# BEP32_12nutzen_stencil.net
KiCad netlist of a schematic drawn in EAGLE
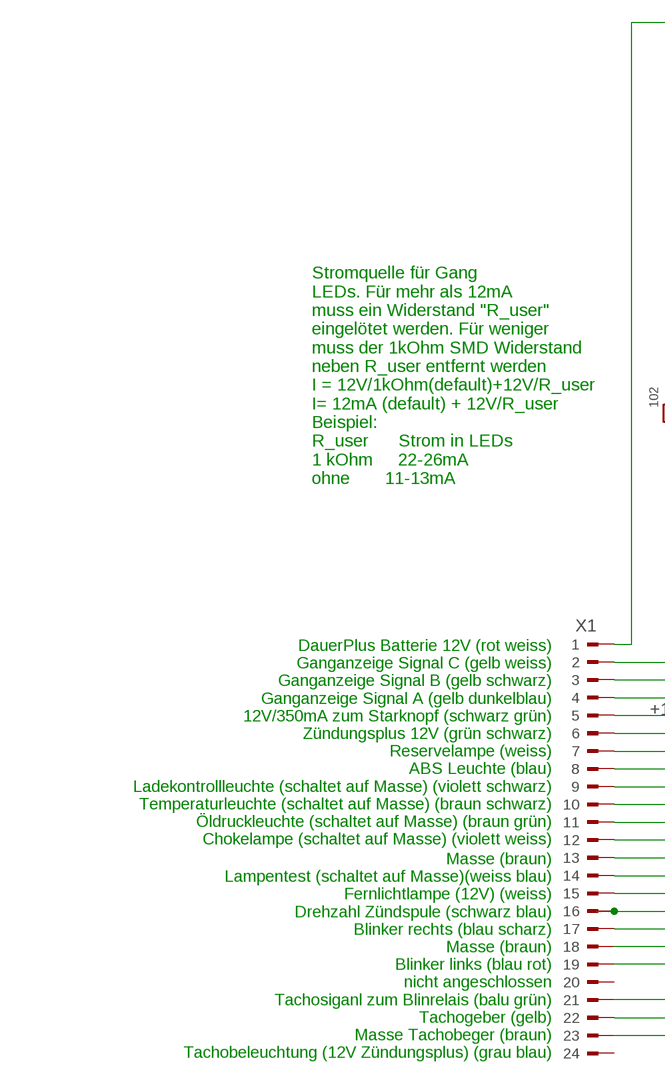
[diagram p0: schematic, sheet 1, part 1 of 2]
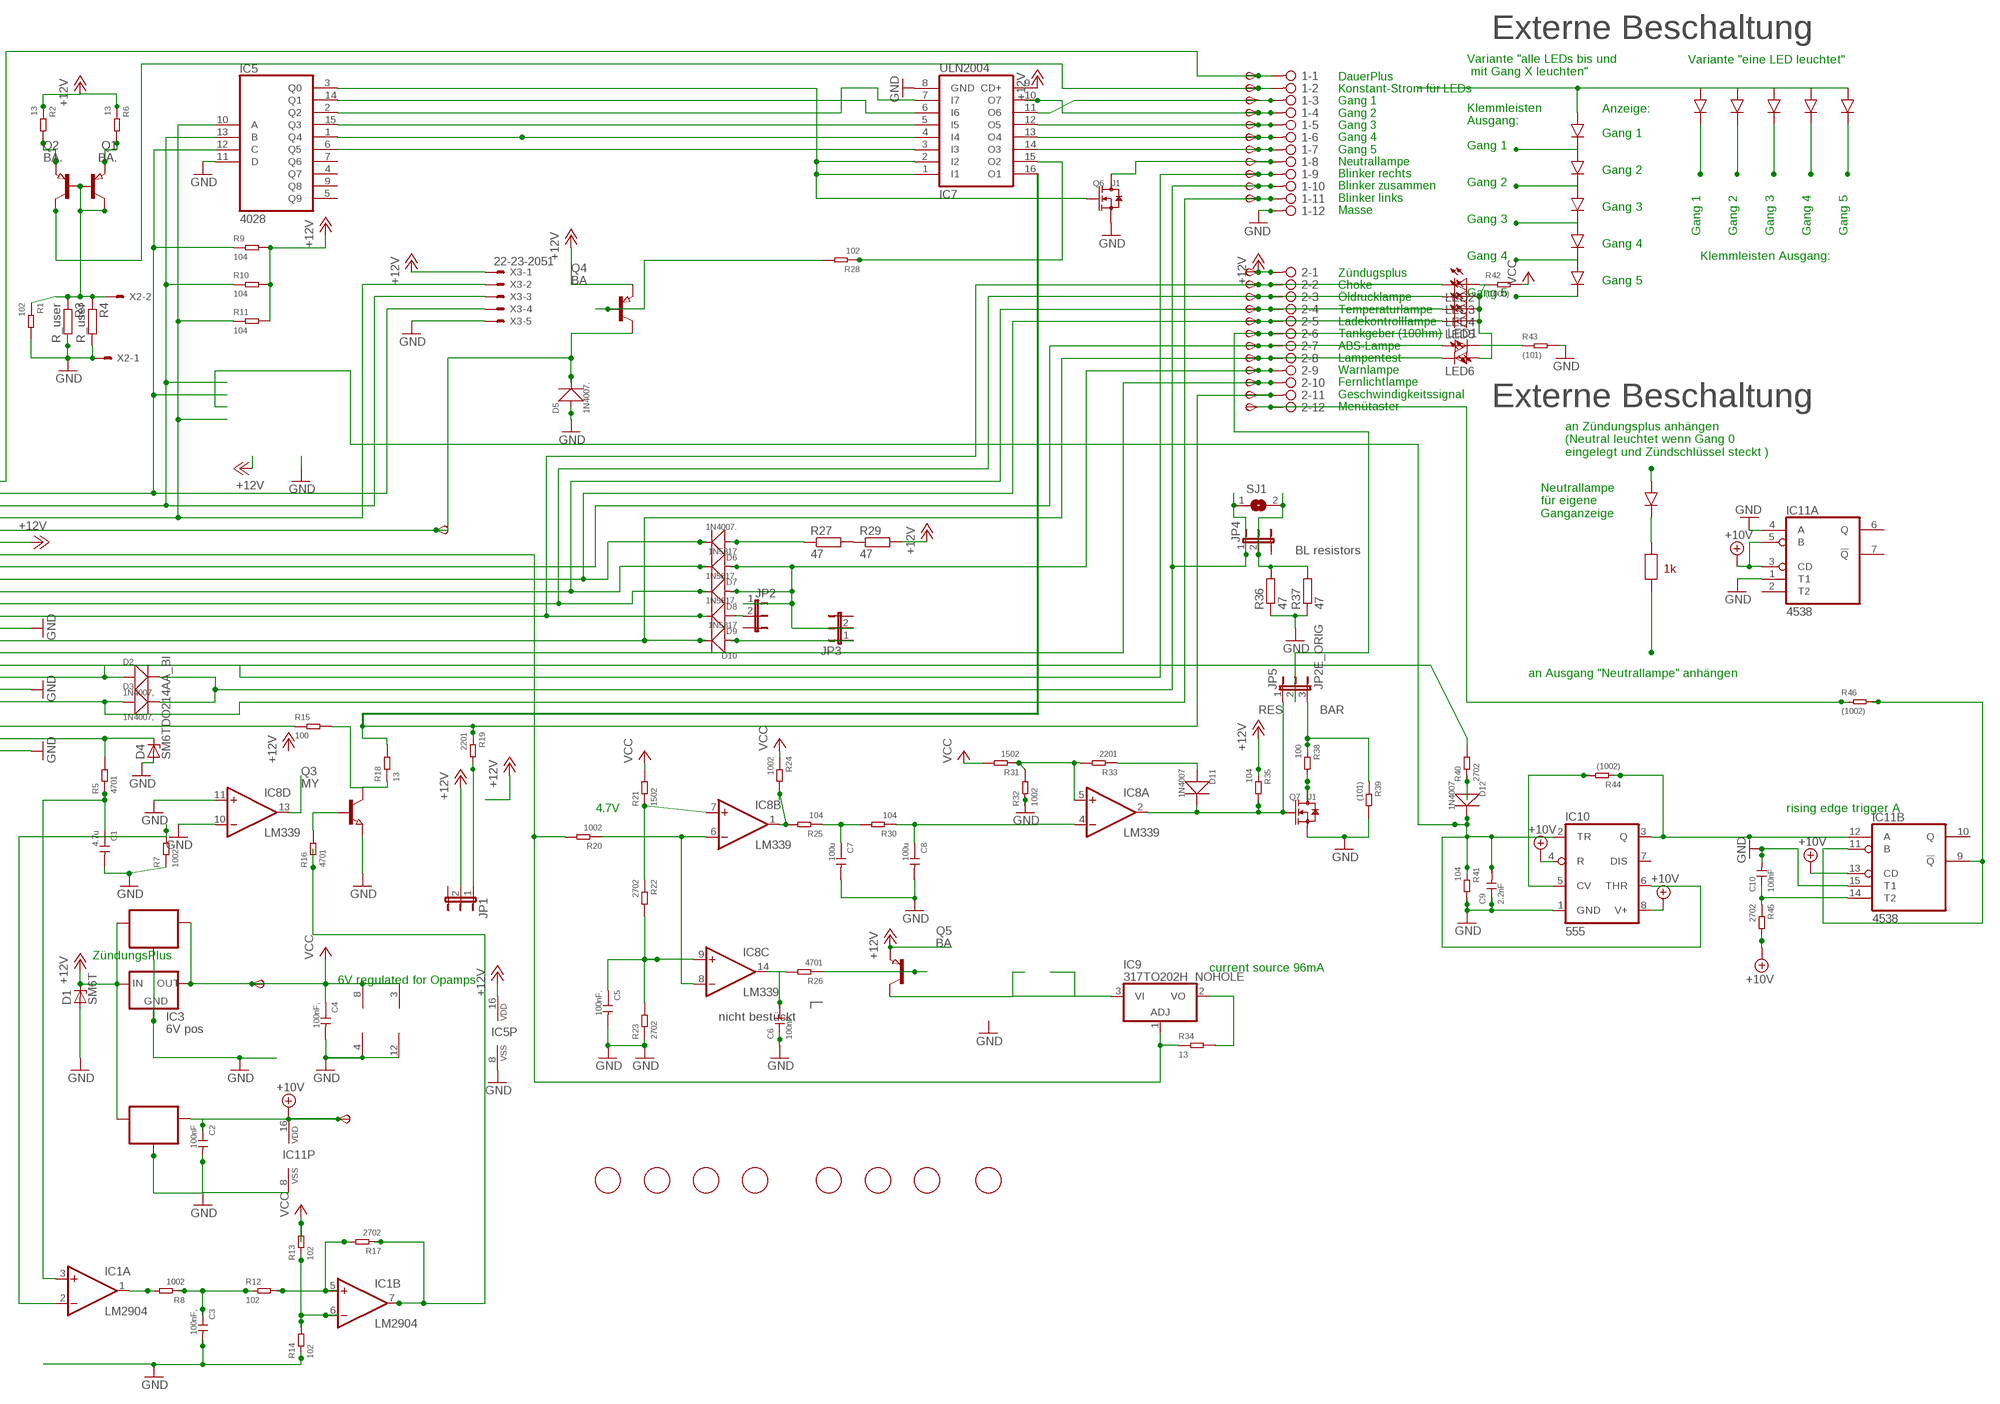
[diagram p1: schematic, sheet 1, part 2 of 2]
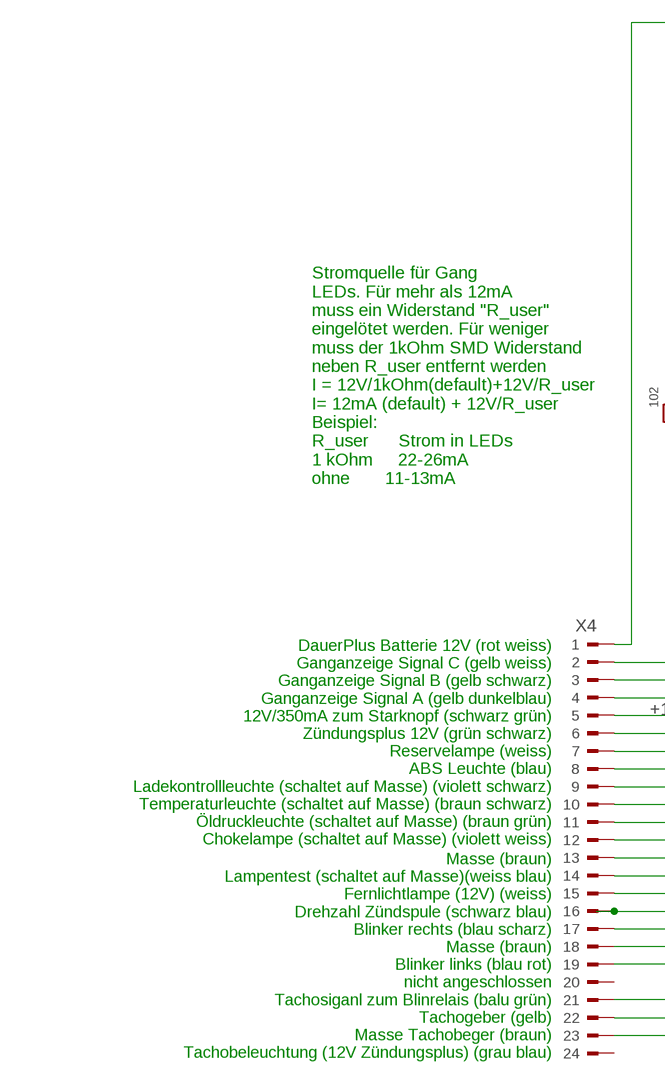
[diagram p2: schematic, sheet 2, part 1 of 2]
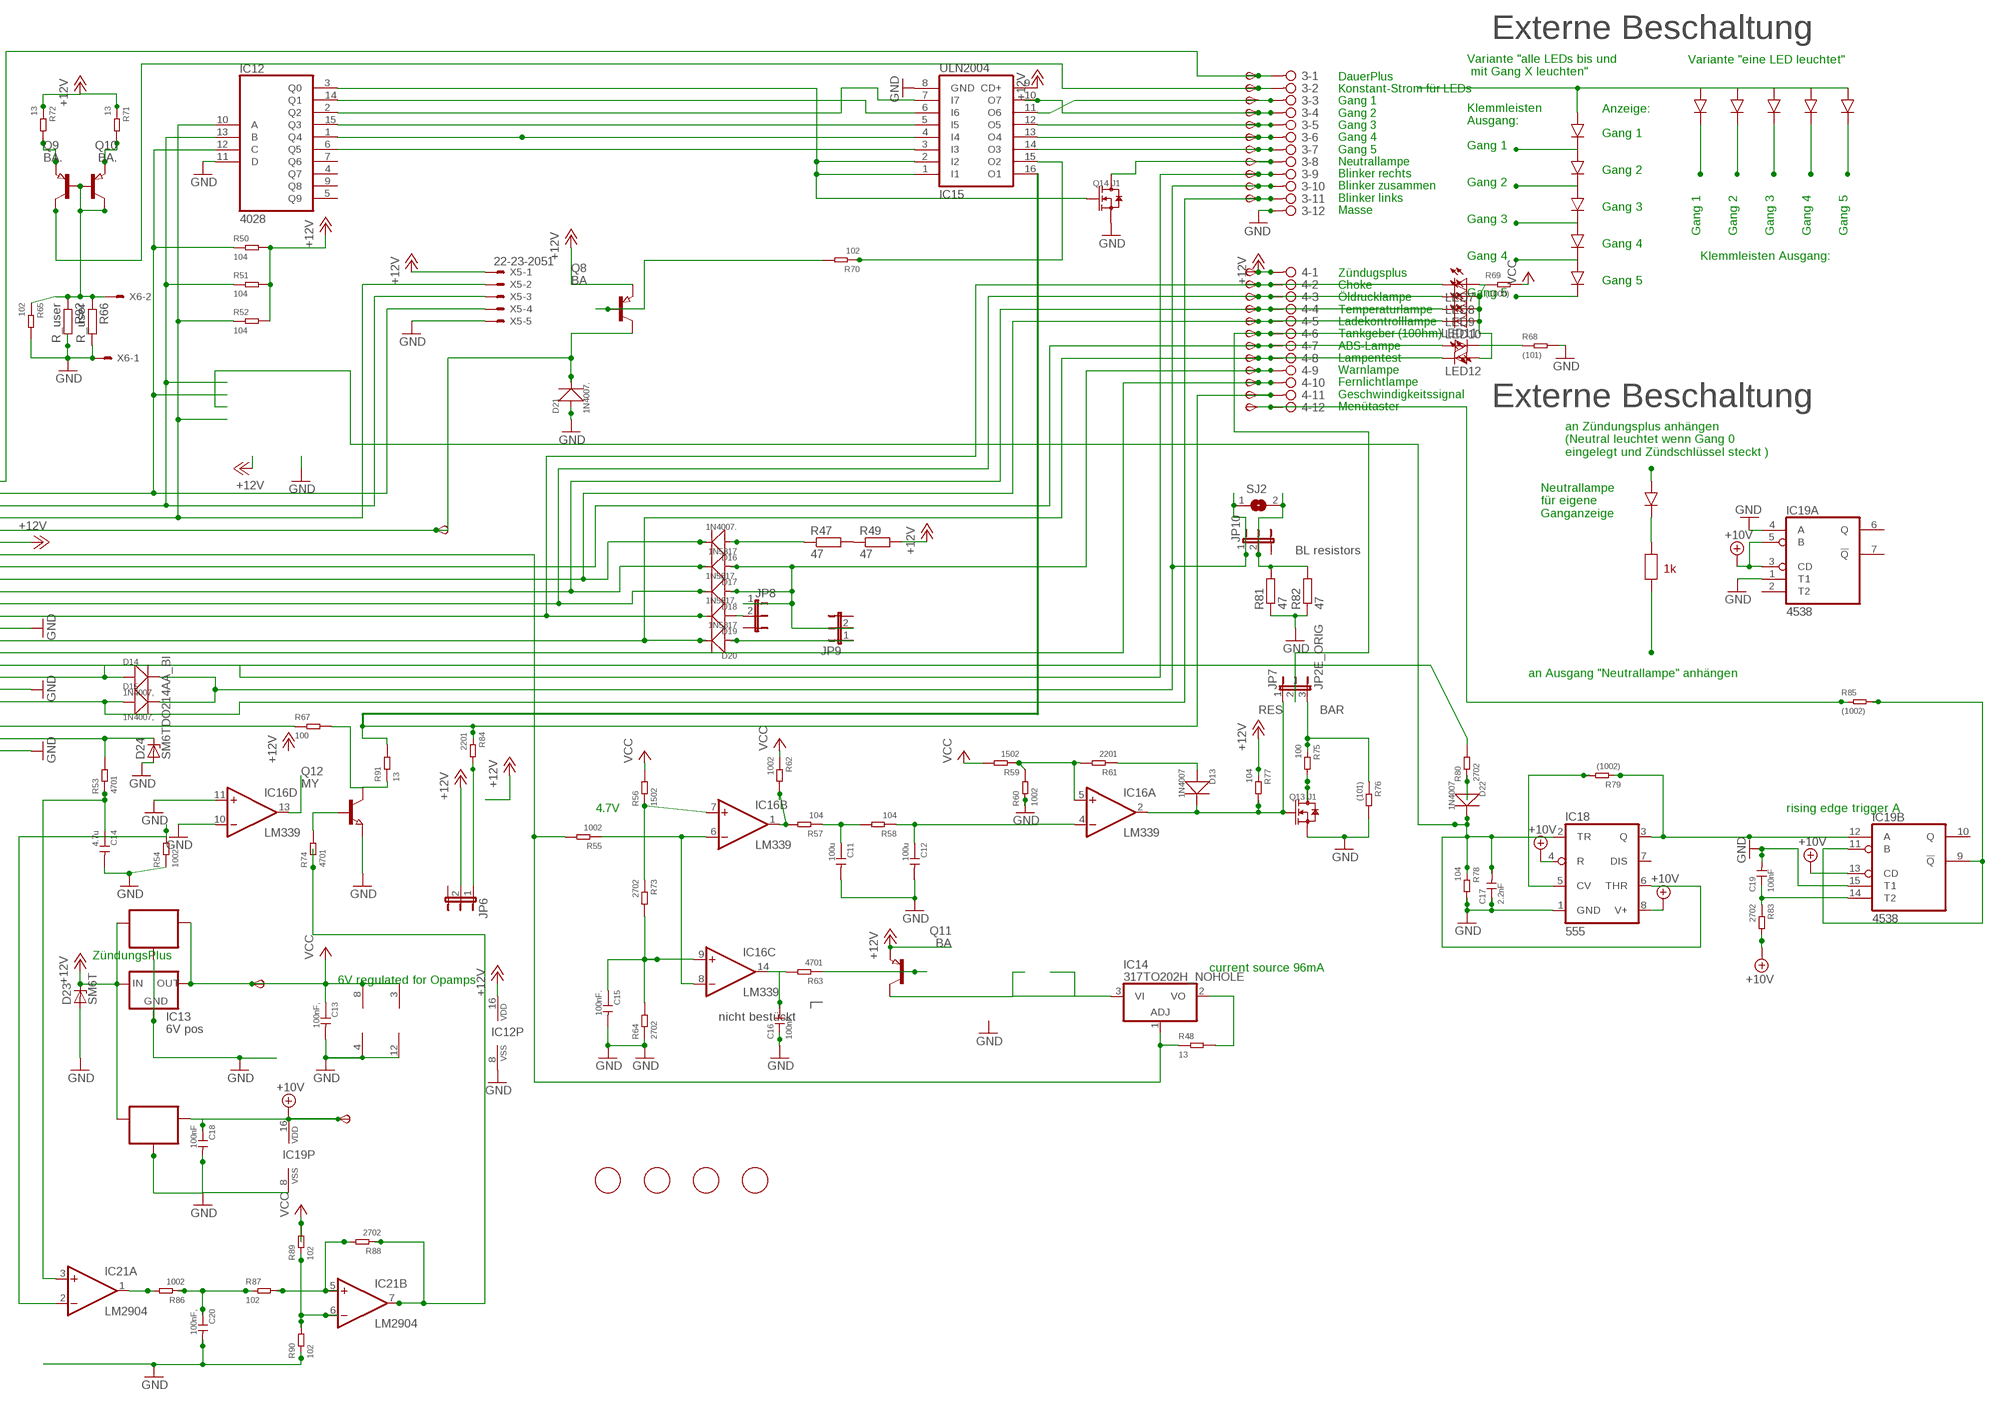
[diagram p3: schematic, sheet 2, part 2 of 2]
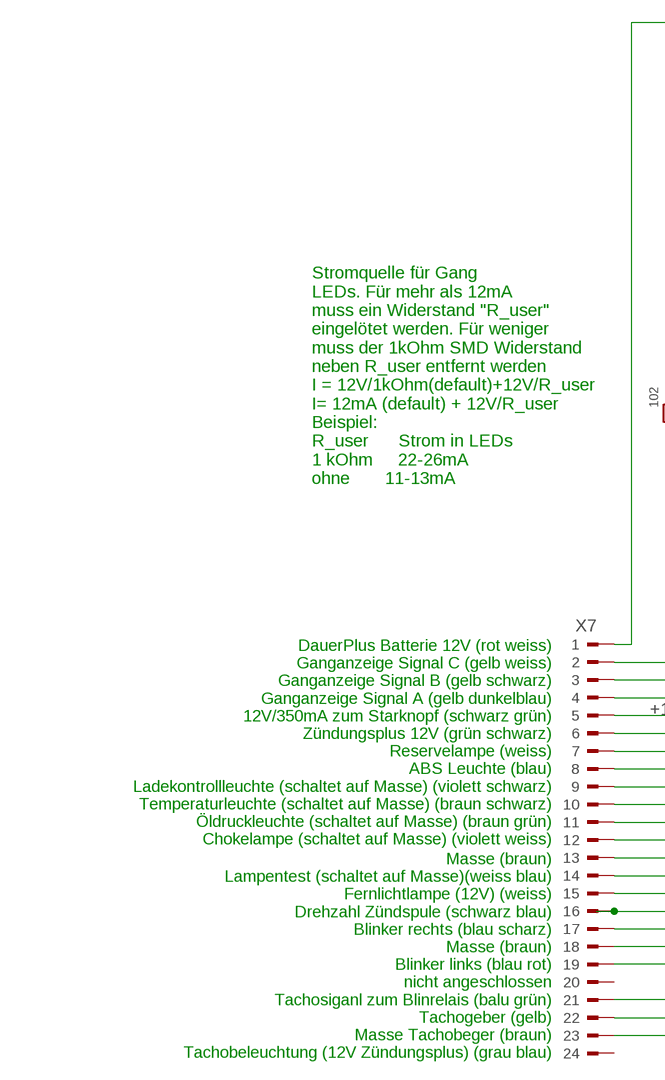
[diagram p4: schematic, sheet 3, part 1 of 2]
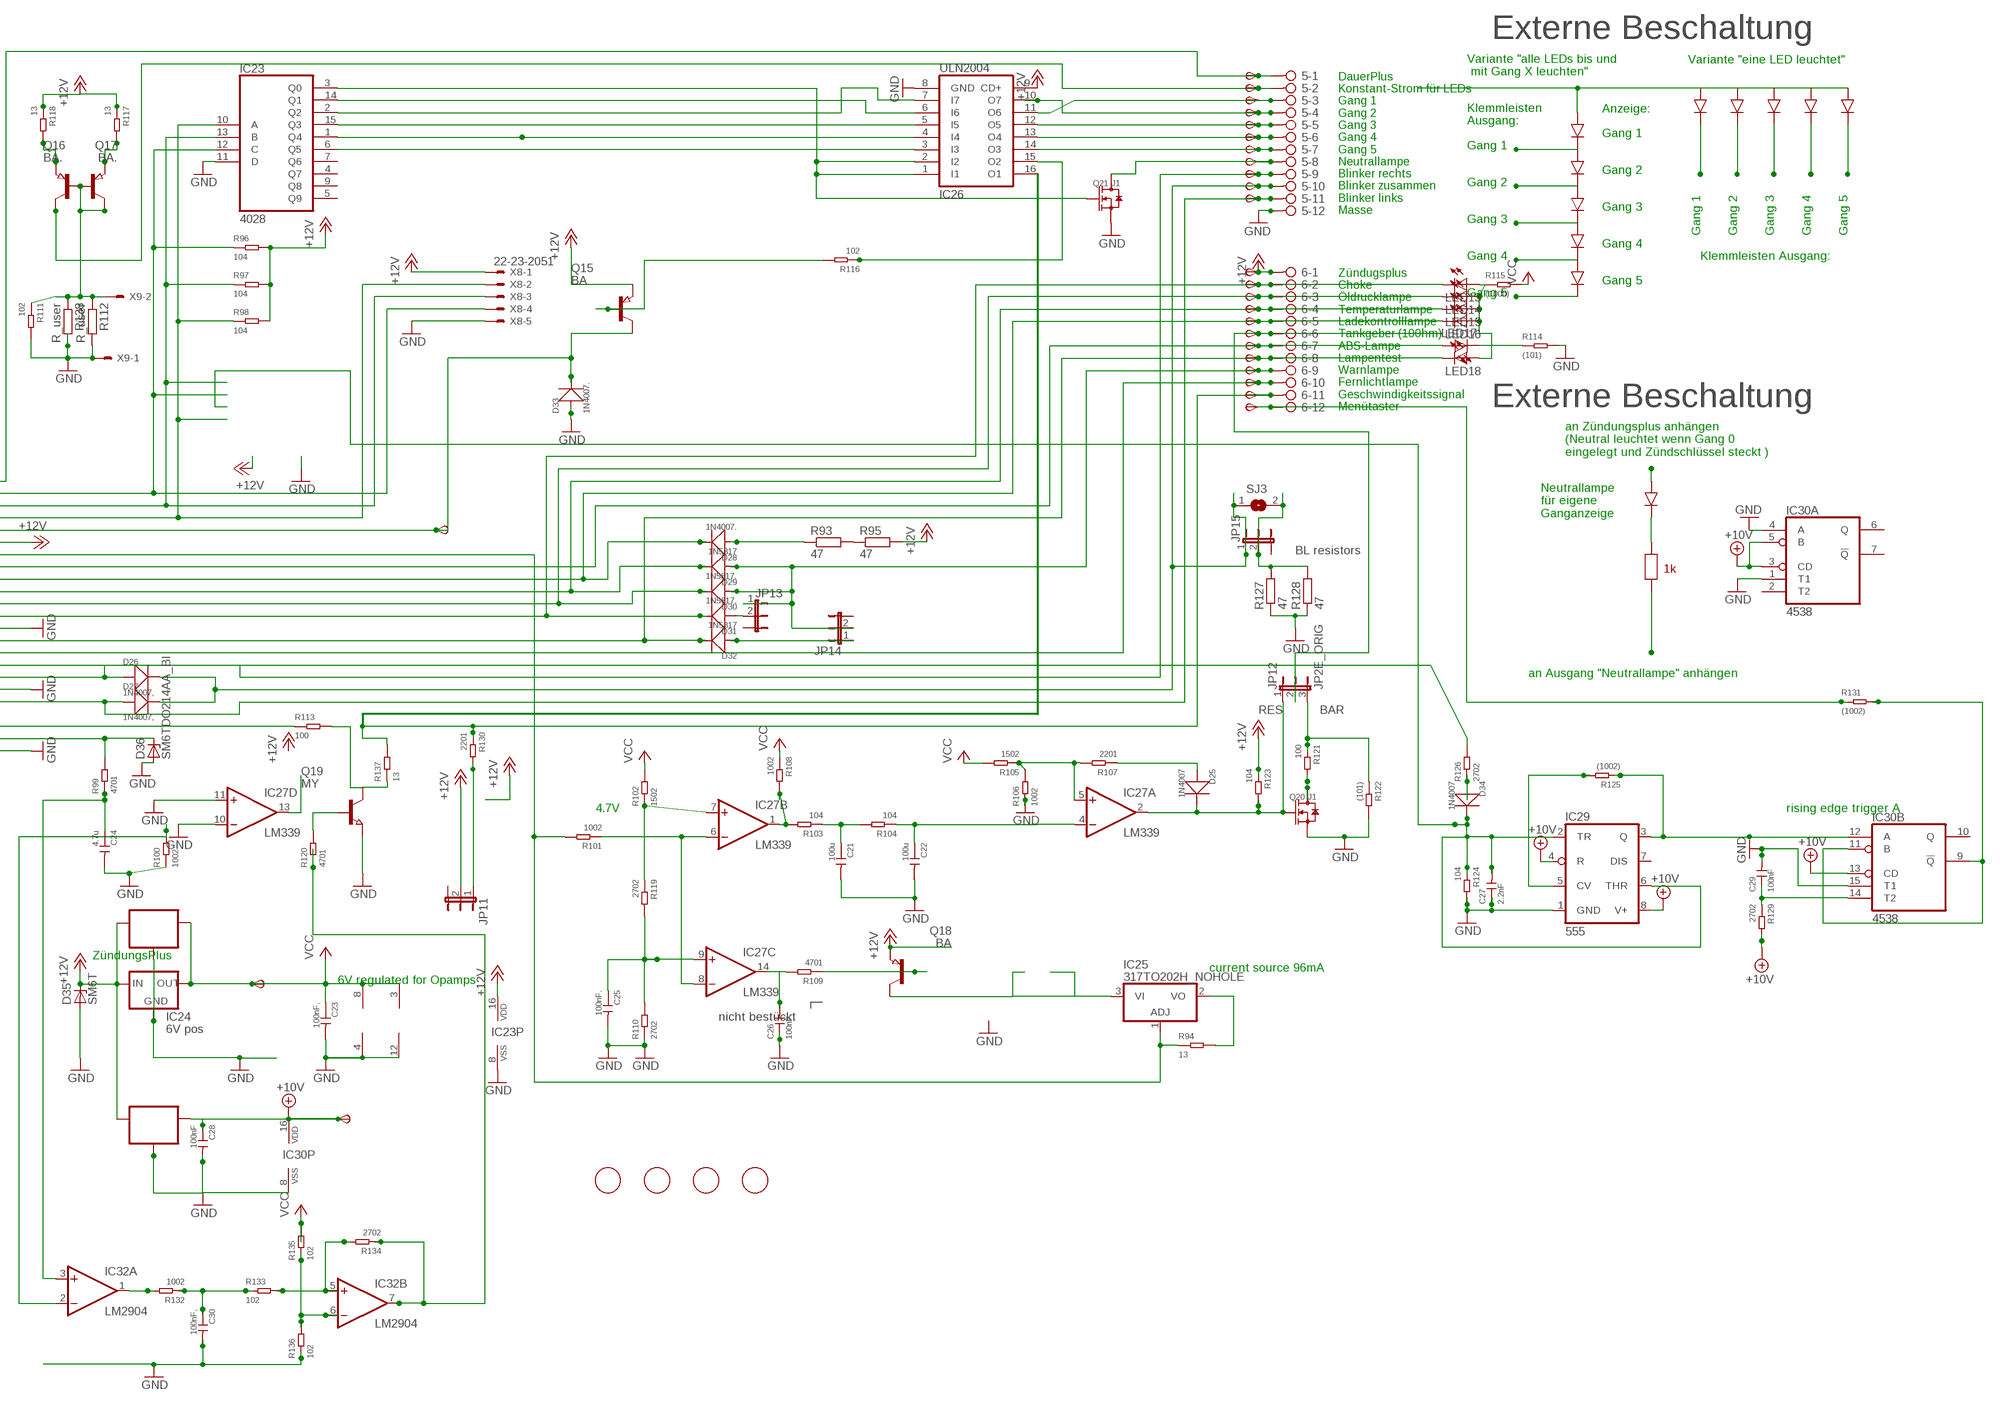
[diagram p5: schematic, sheet 3, part 2 of 2]
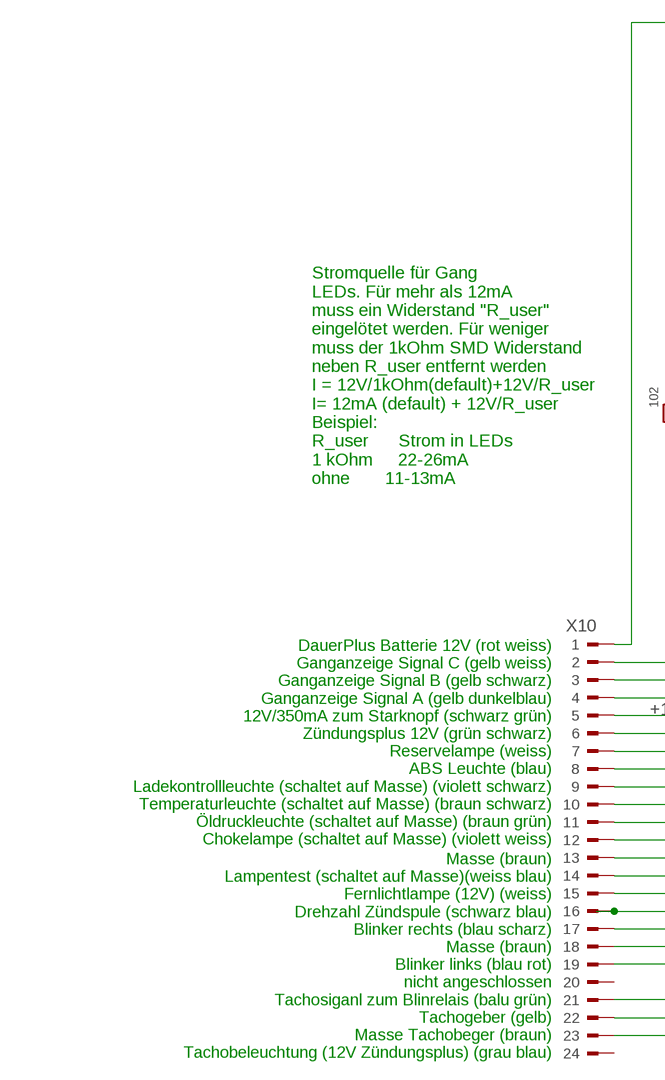
[diagram p6: schematic, sheet 4, part 1 of 2]
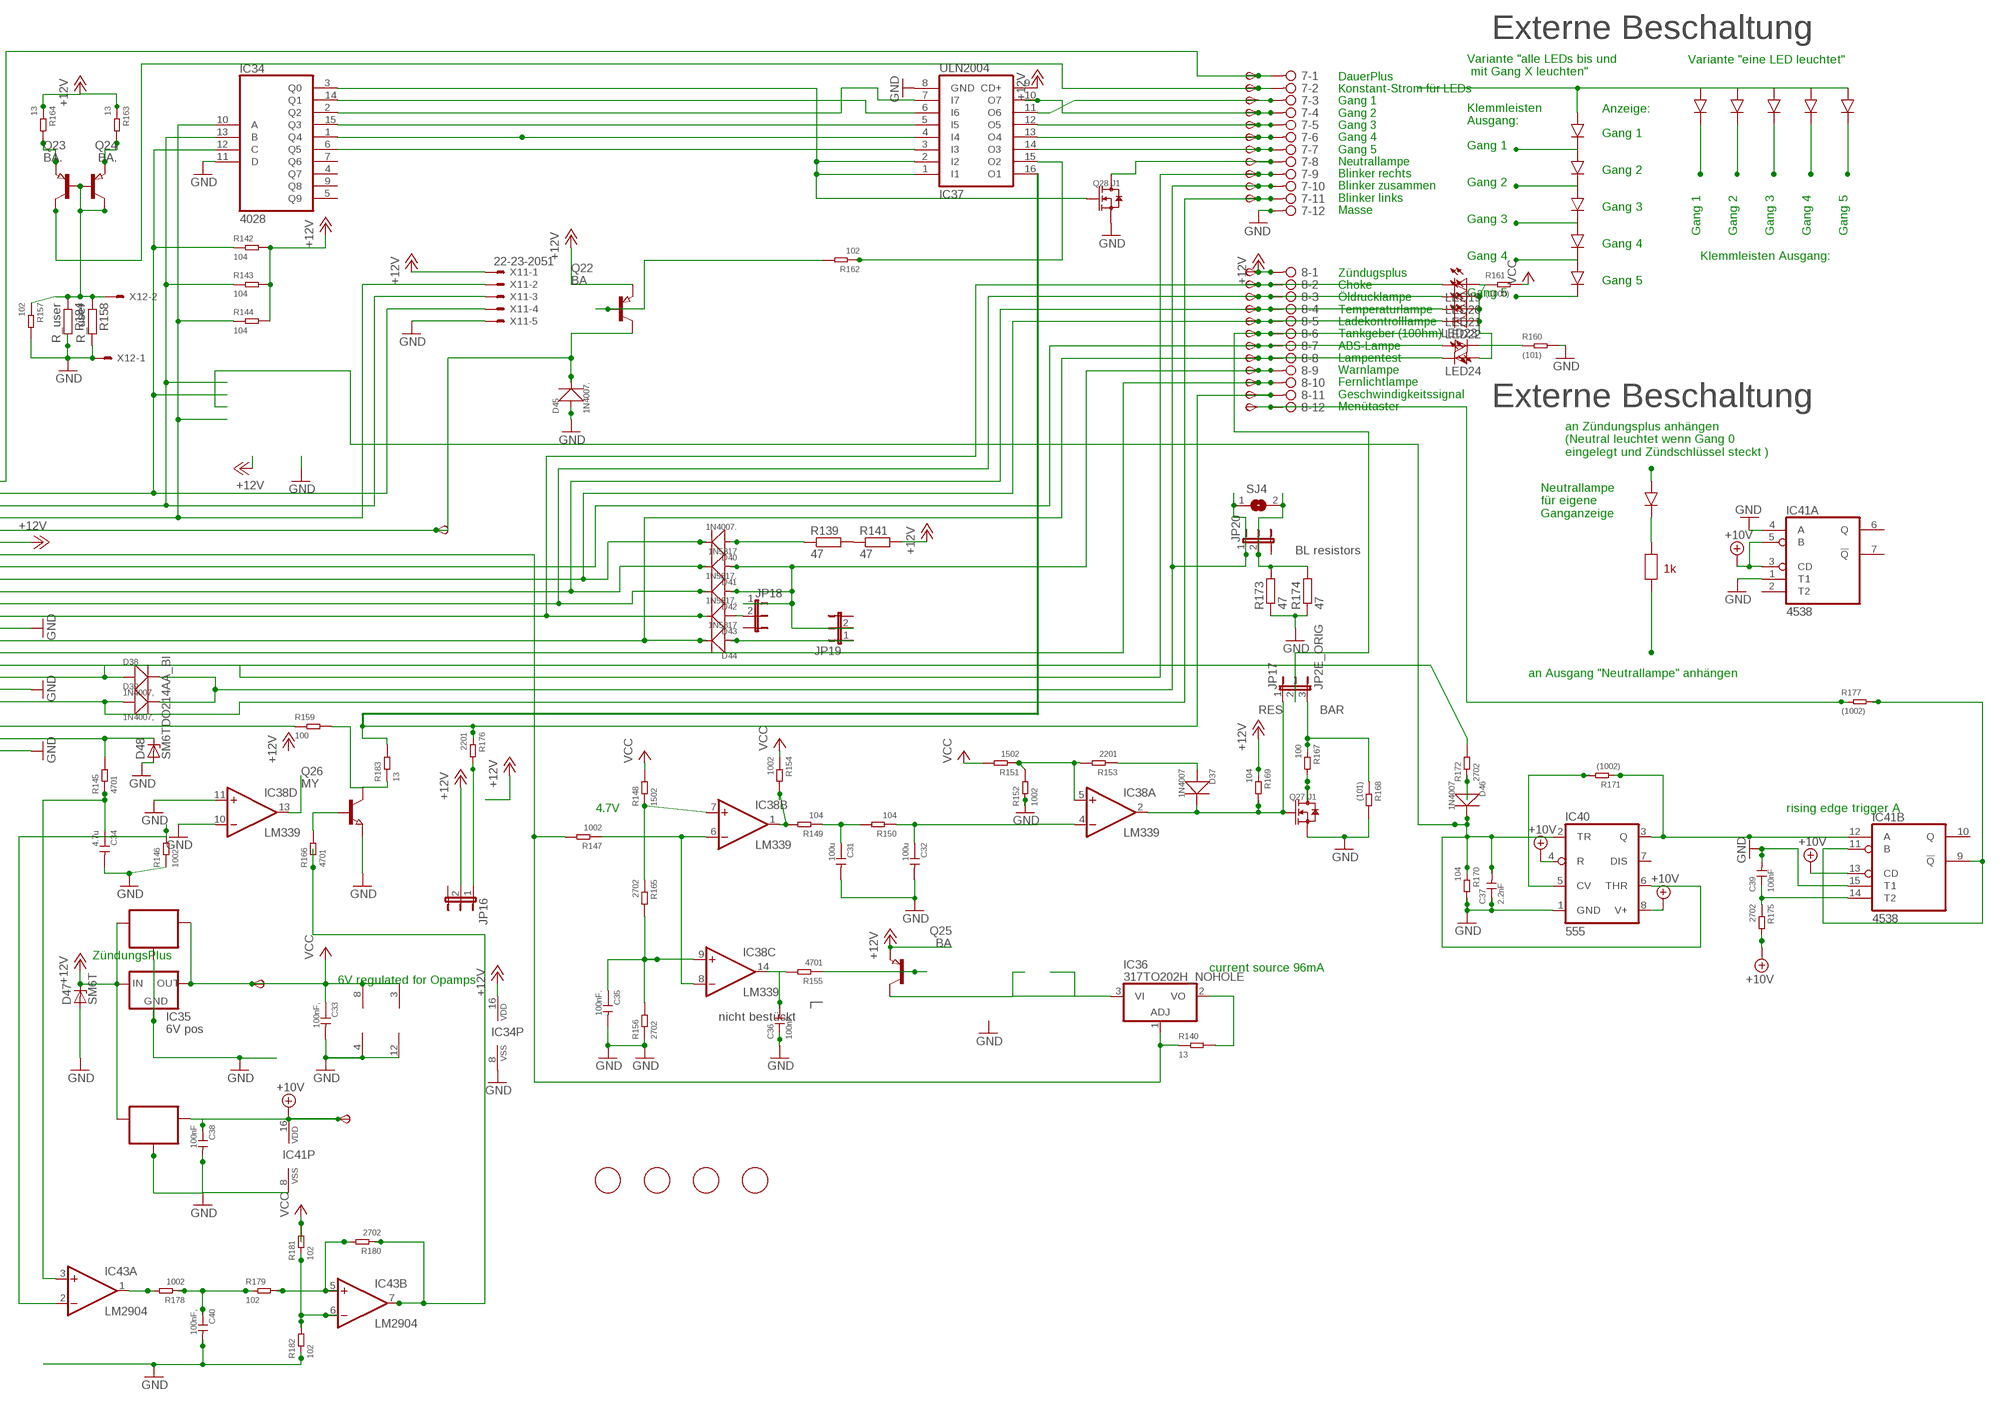
[diagram p7: schematic, sheet 4, part 2 of 2]
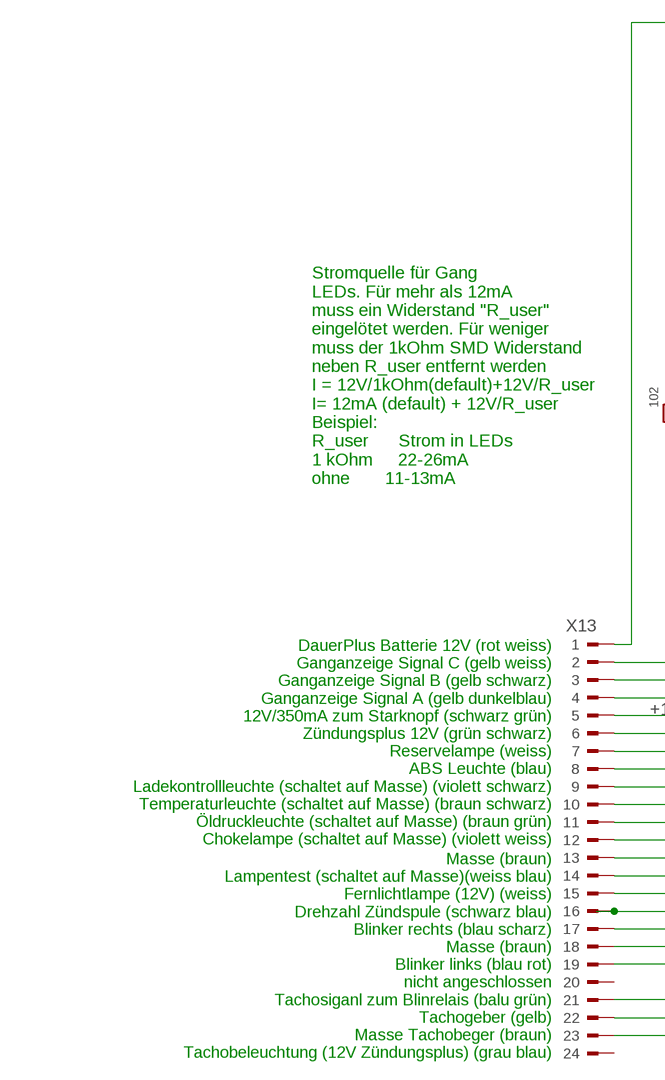
[diagram p8: schematic, sheet 5, part 1 of 2]
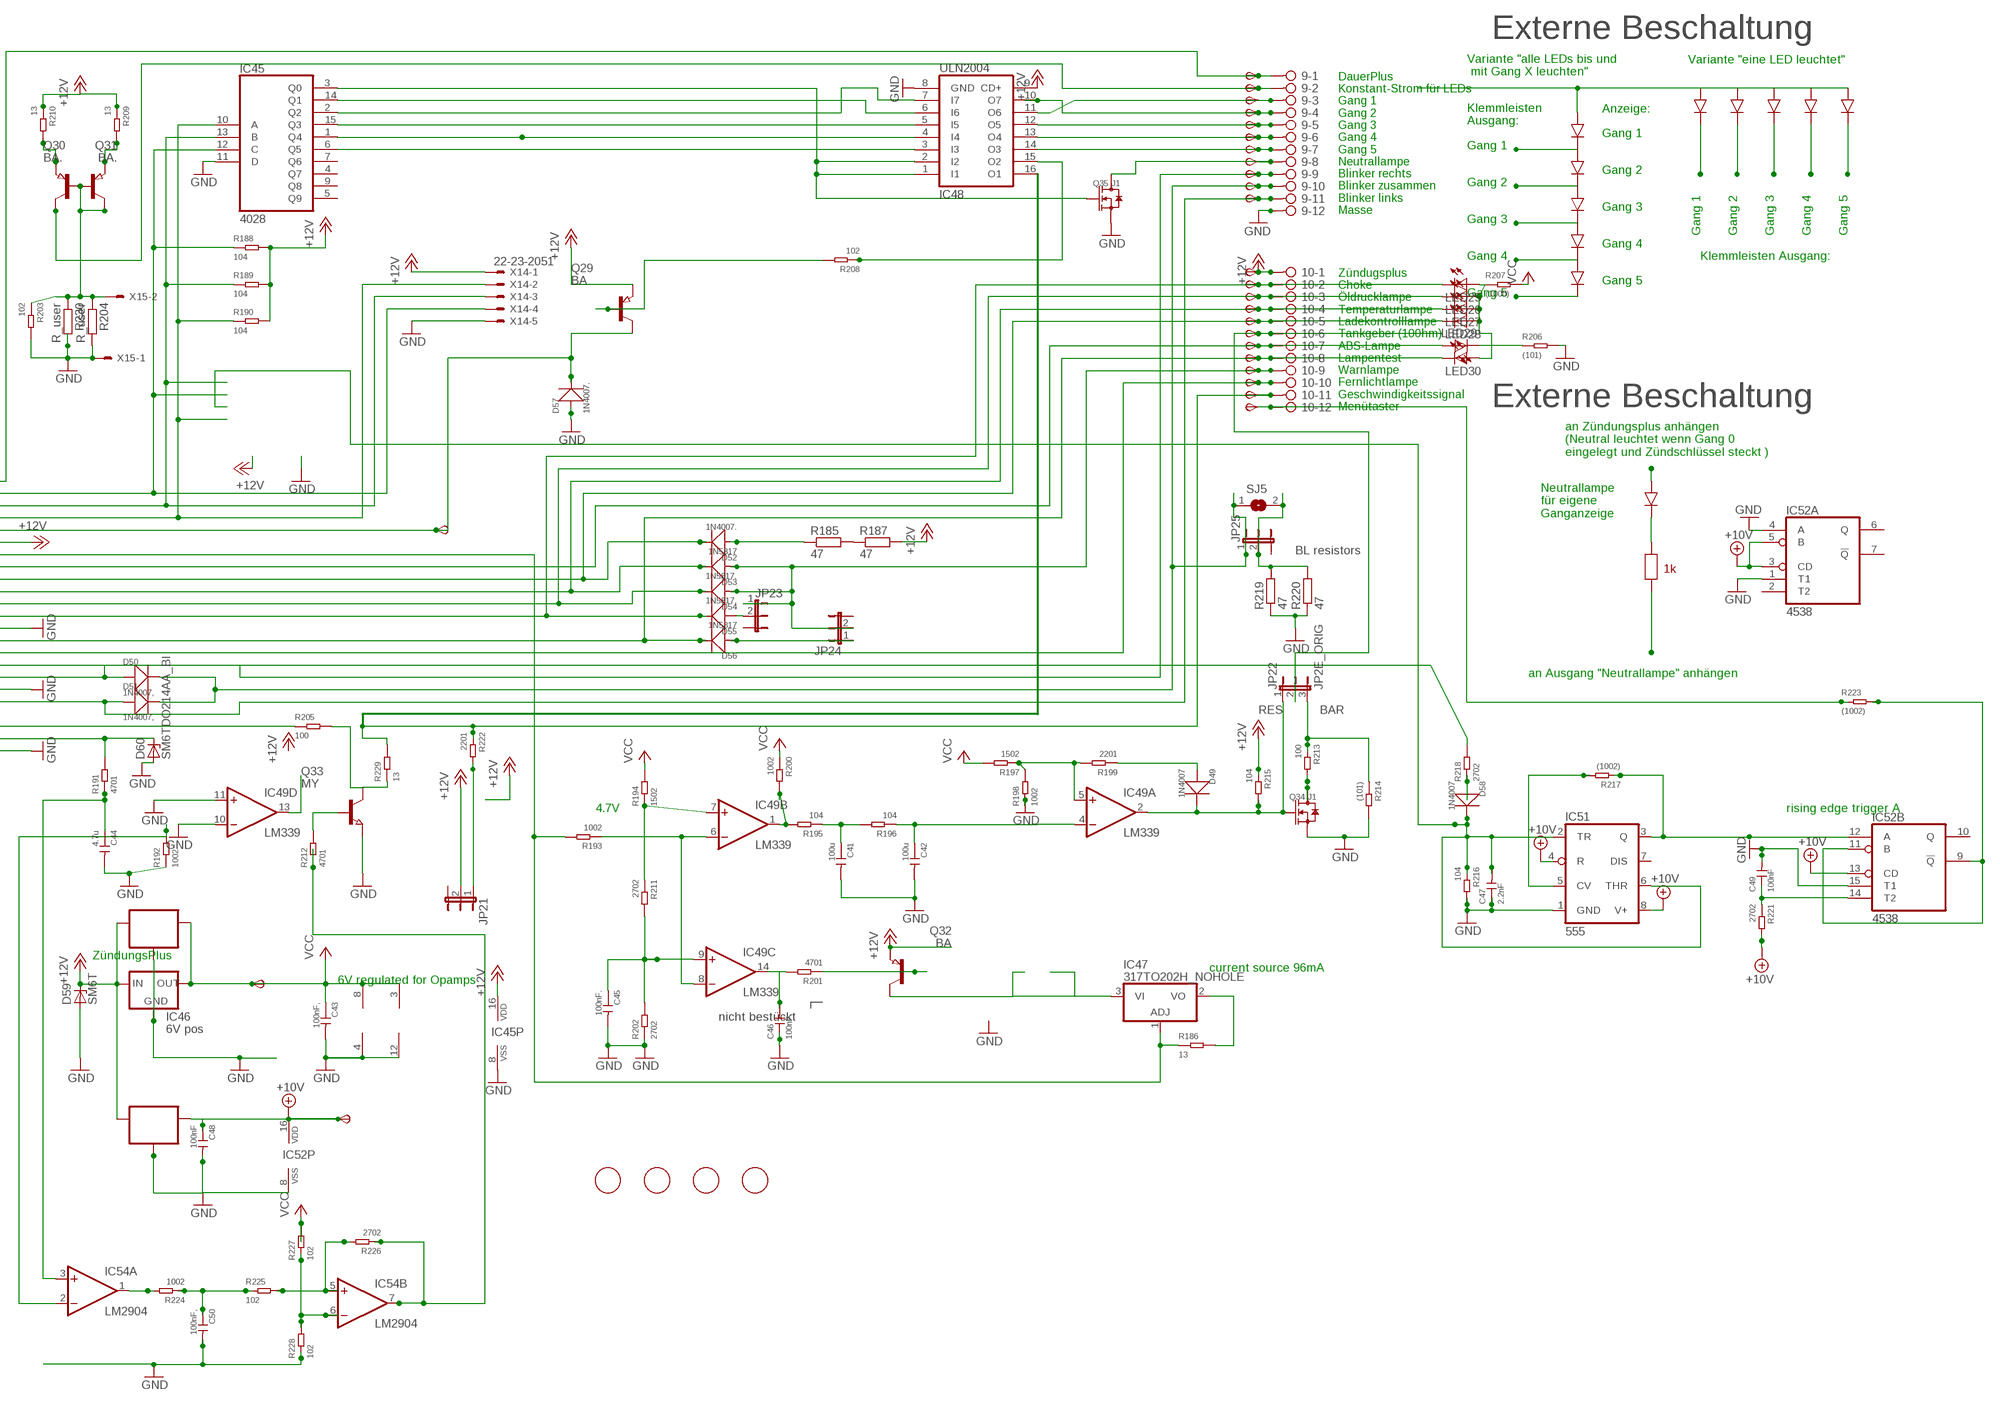
[diagram p9: schematic, sheet 5, part 2 of 2]
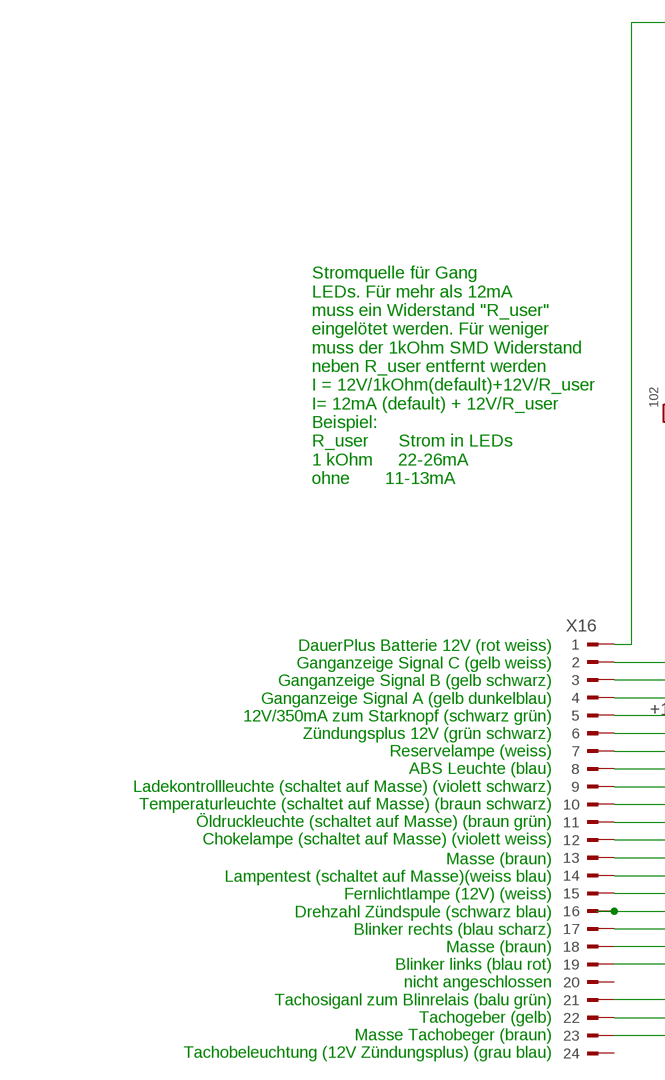
[diagram p10: schematic, sheet 6, part 1 of 2]
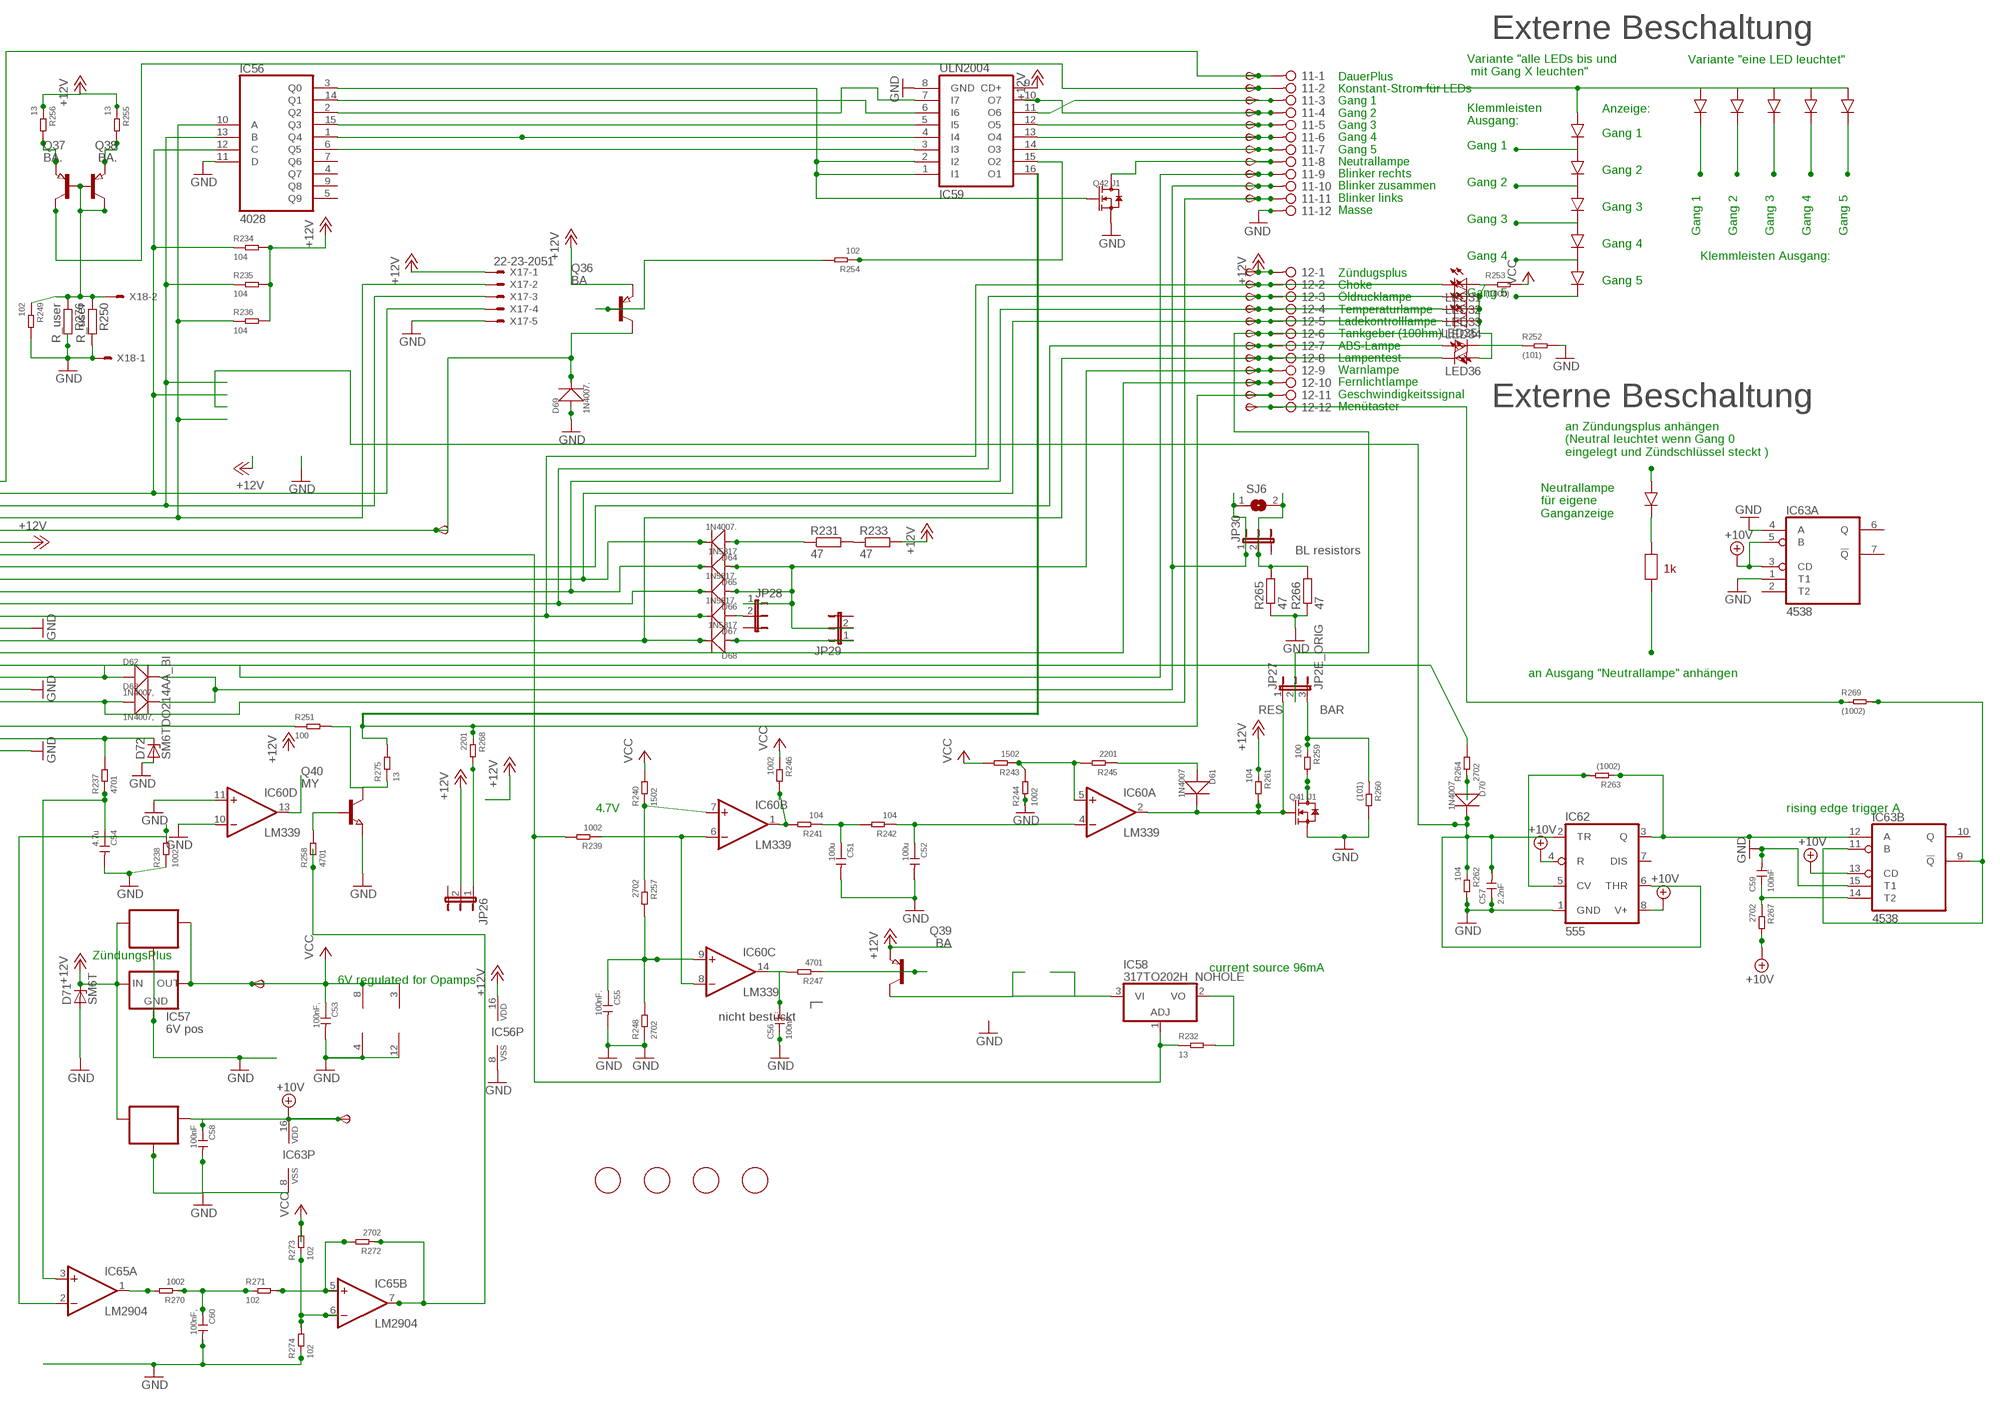
[diagram p11: schematic, sheet 6, part 2 of 2]
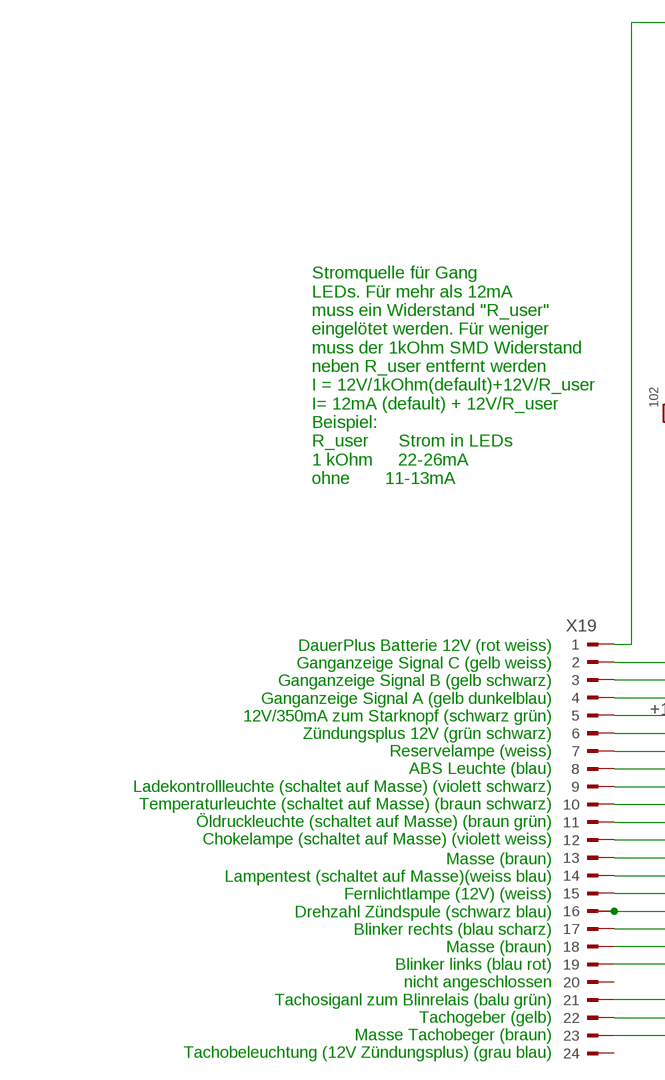
[diagram p12: schematic, sheet 7, part 1 of 2]
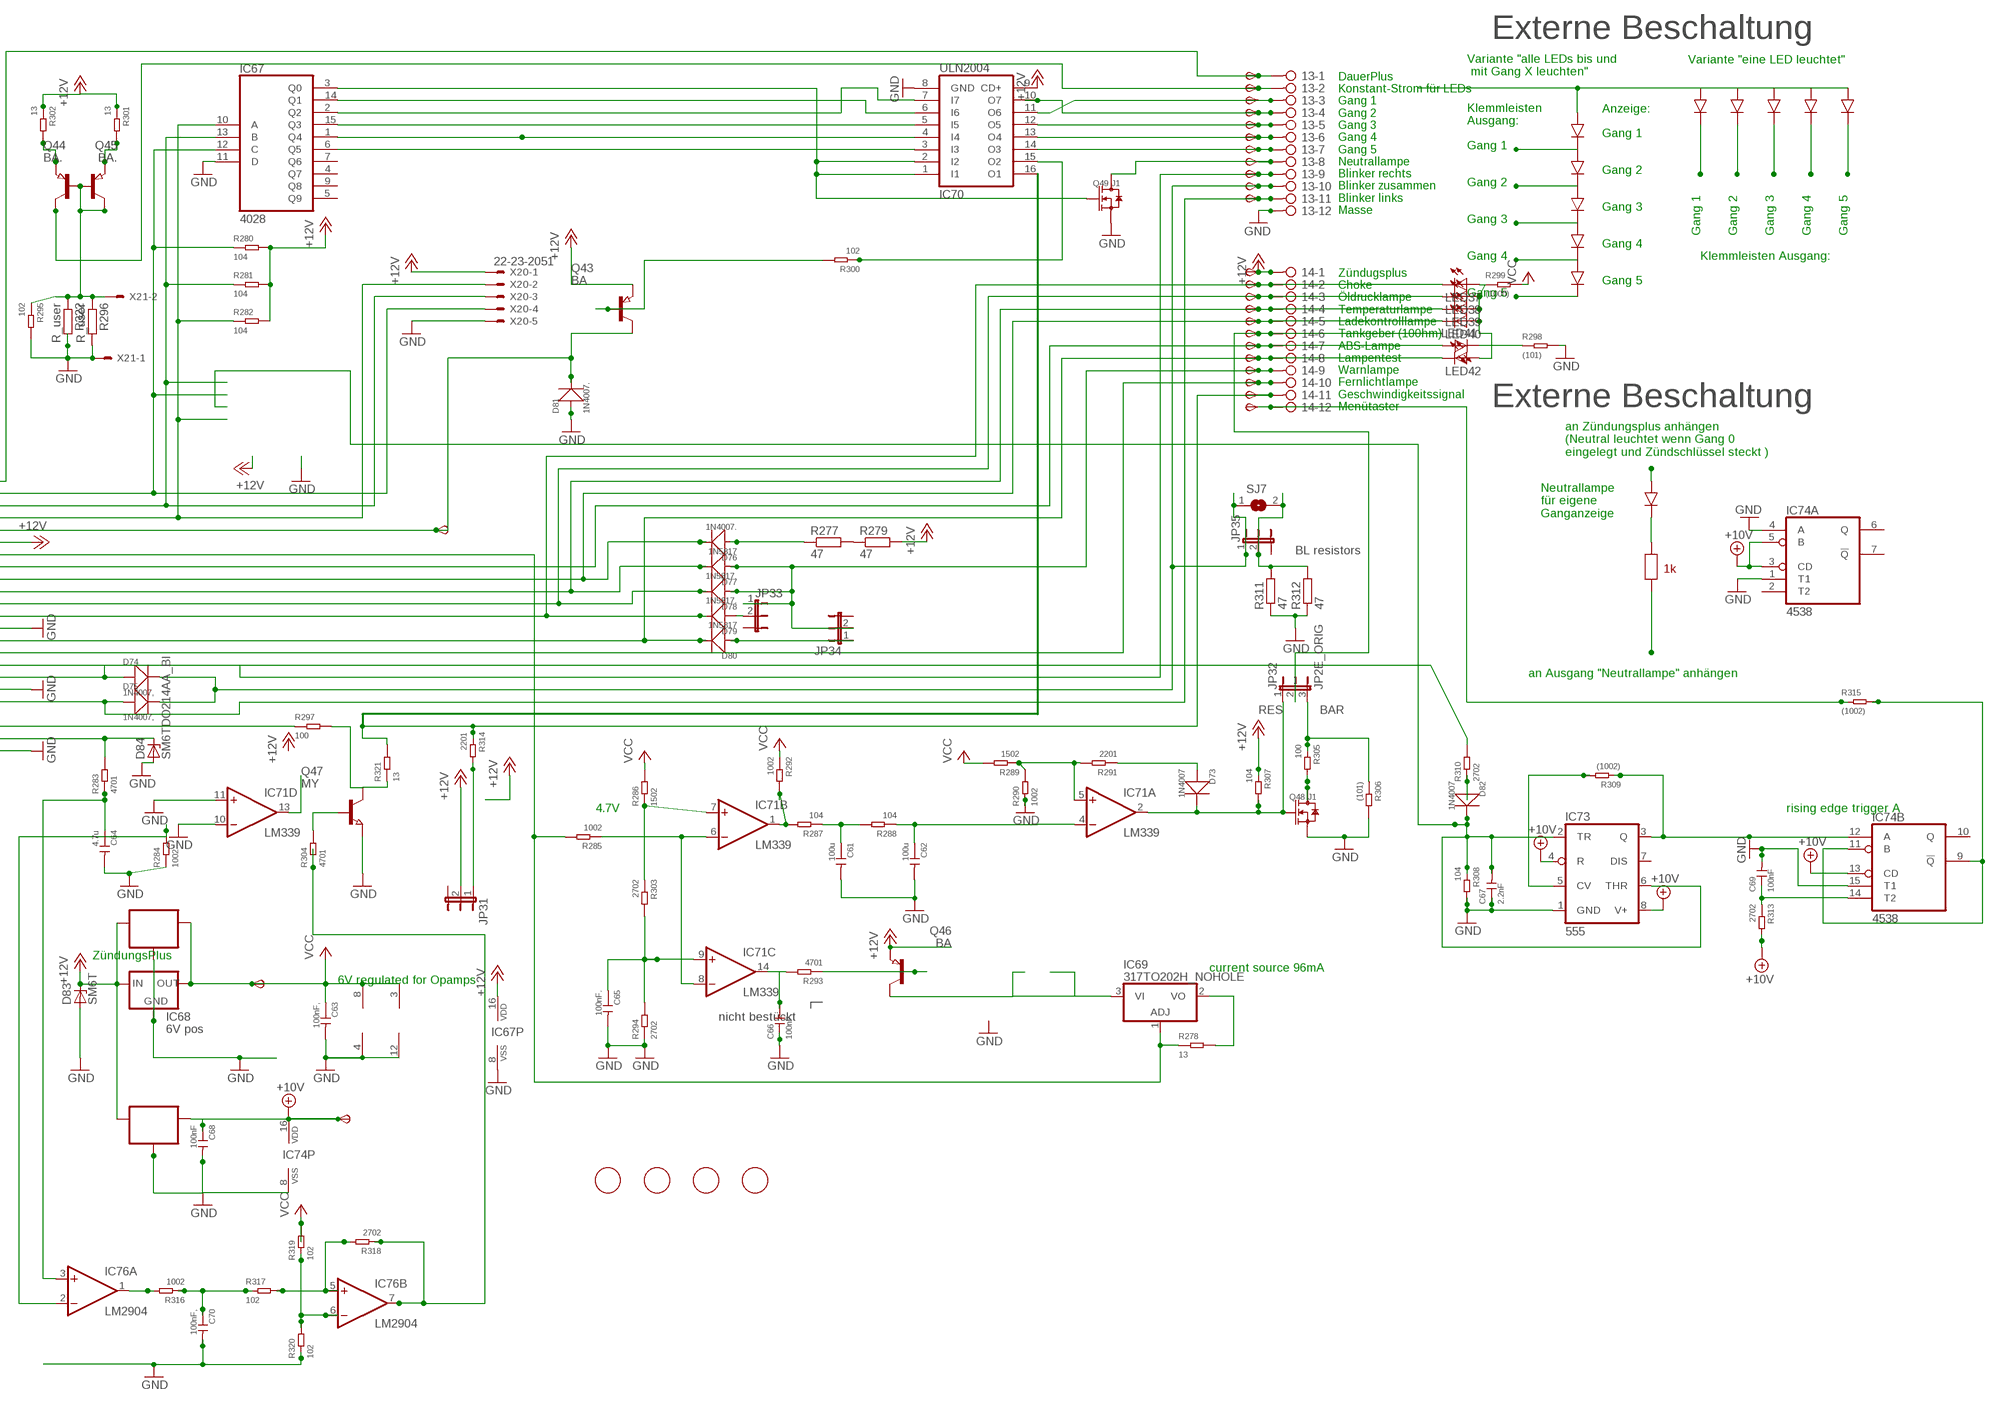
[diagram p13: schematic, sheet 7, part 2 of 2]
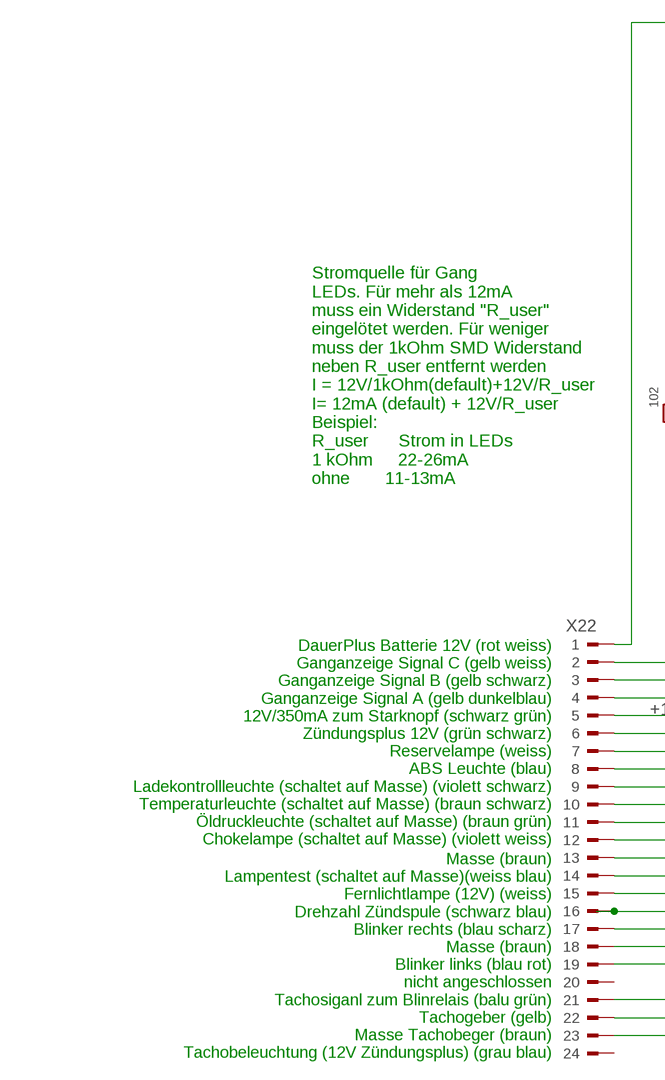
[diagram p14: schematic, sheet 8, part 1 of 2]
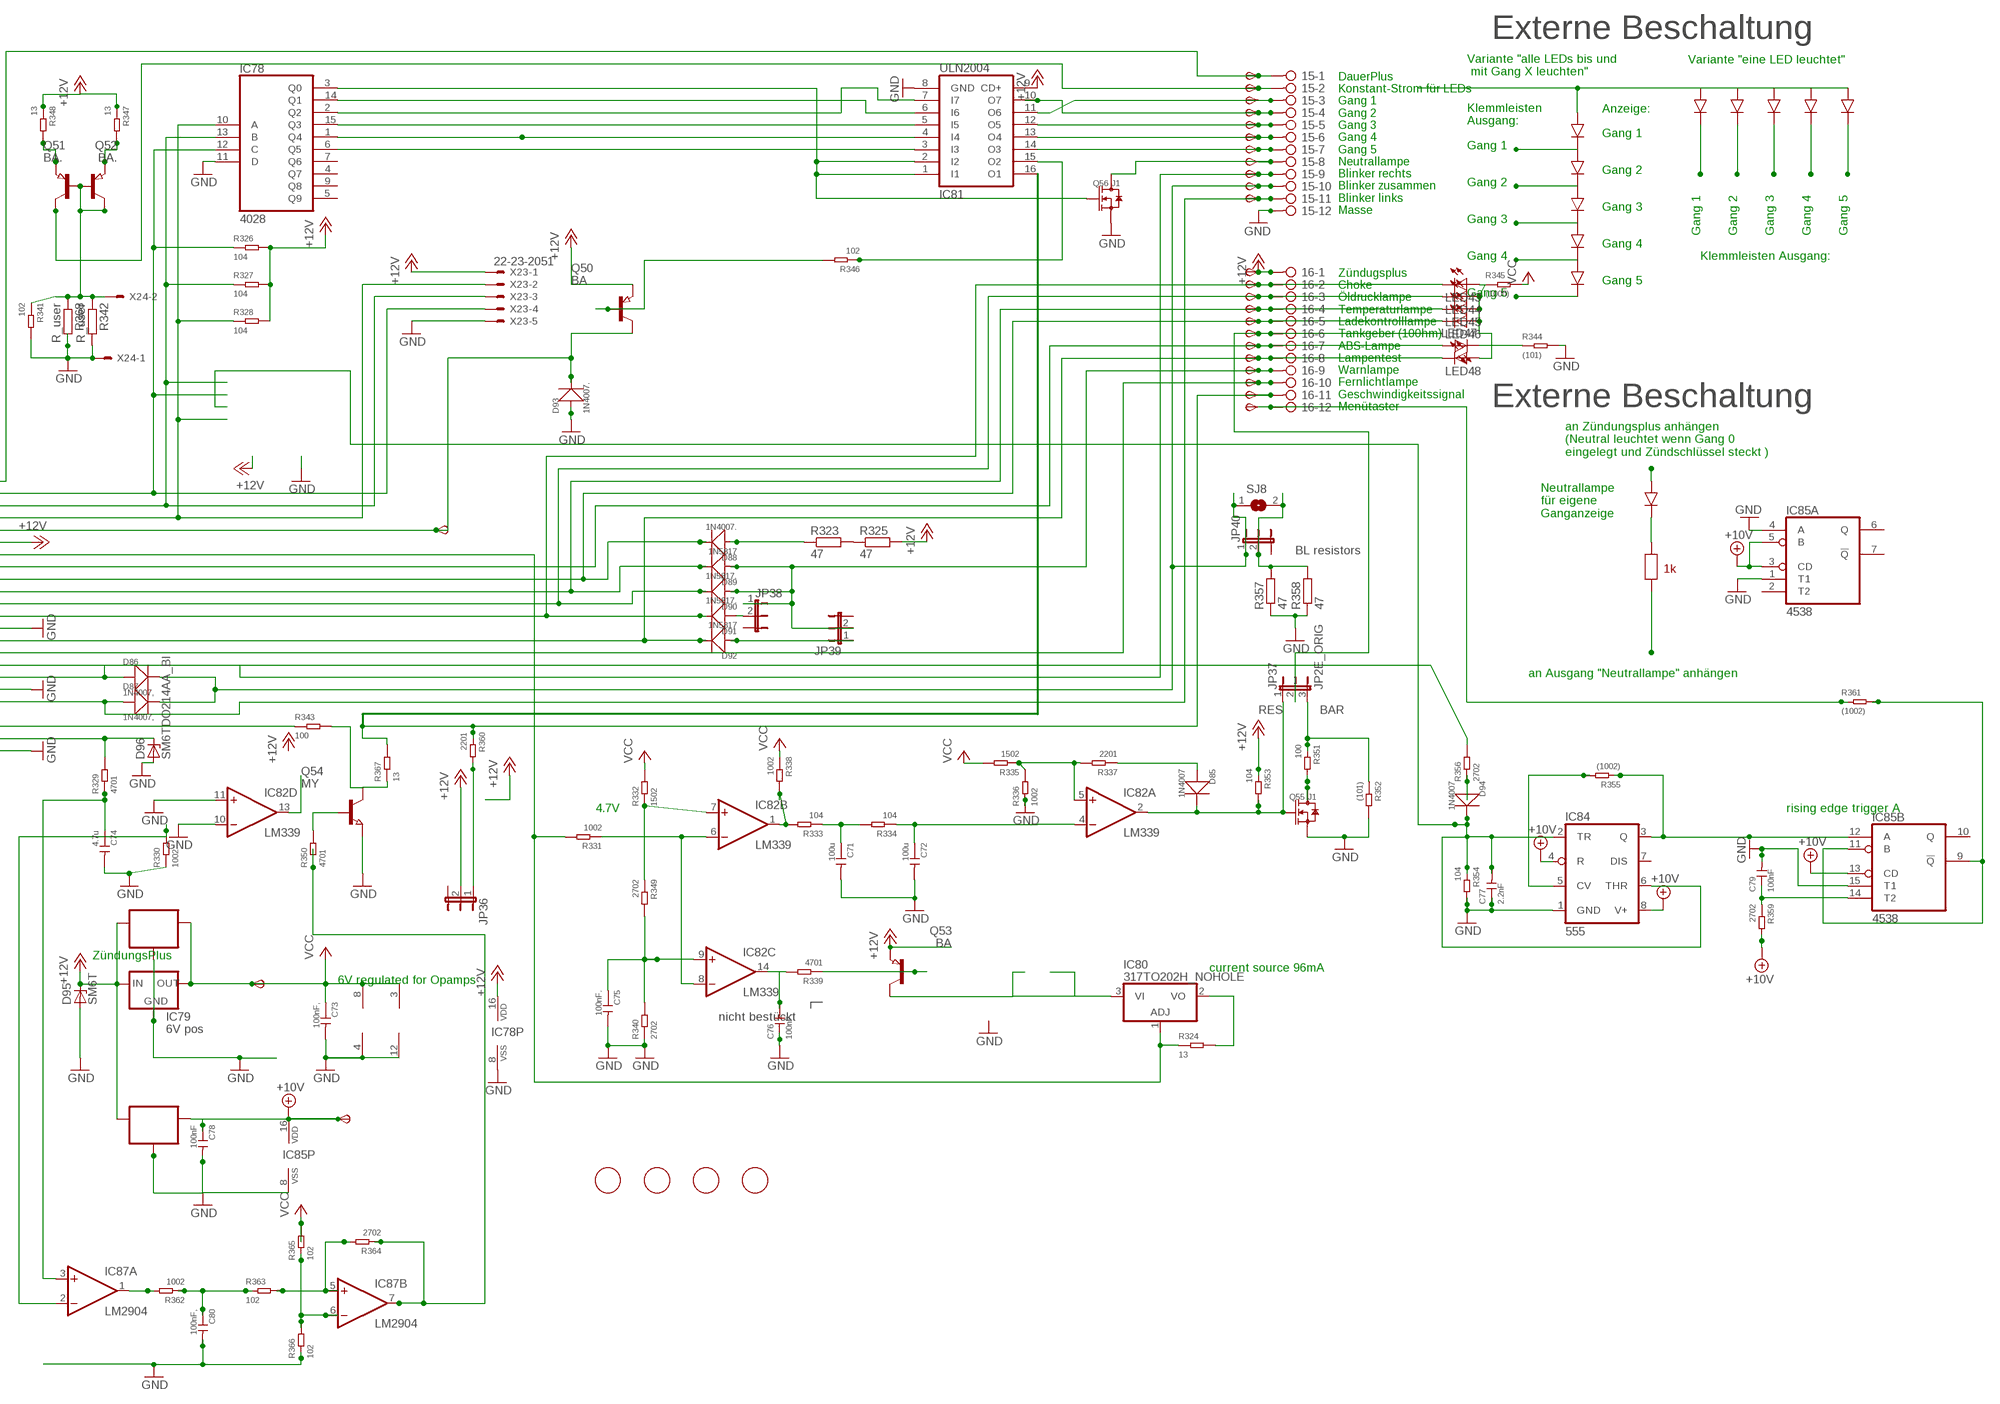
[diagram p15: schematic, sheet 8, part 2 of 2]
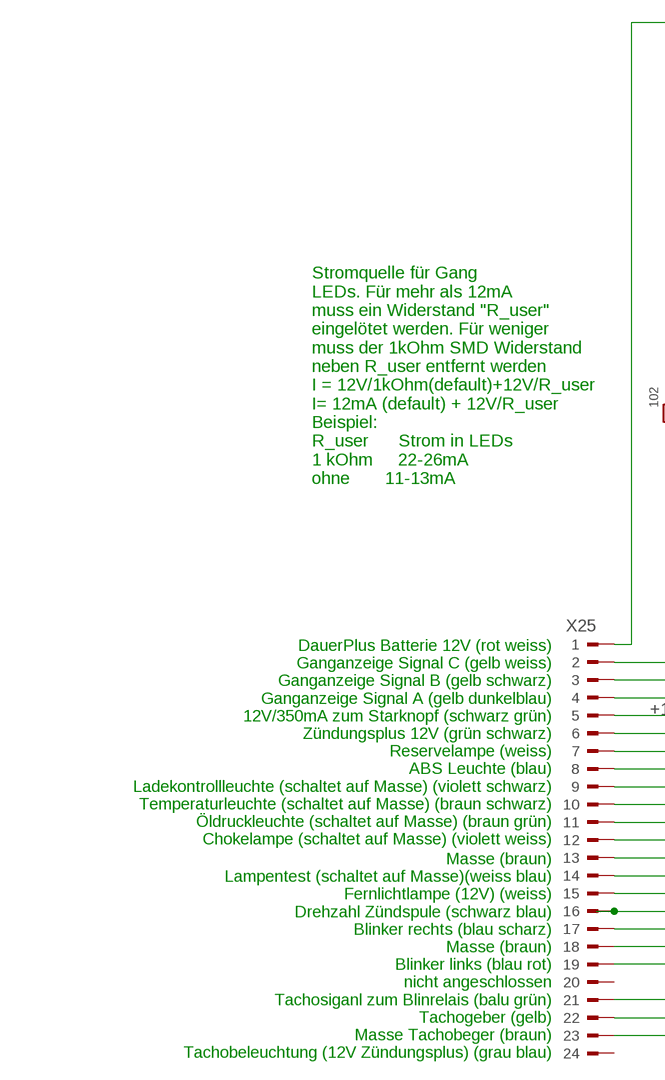
[diagram p16: schematic, sheet 9, part 1 of 2]
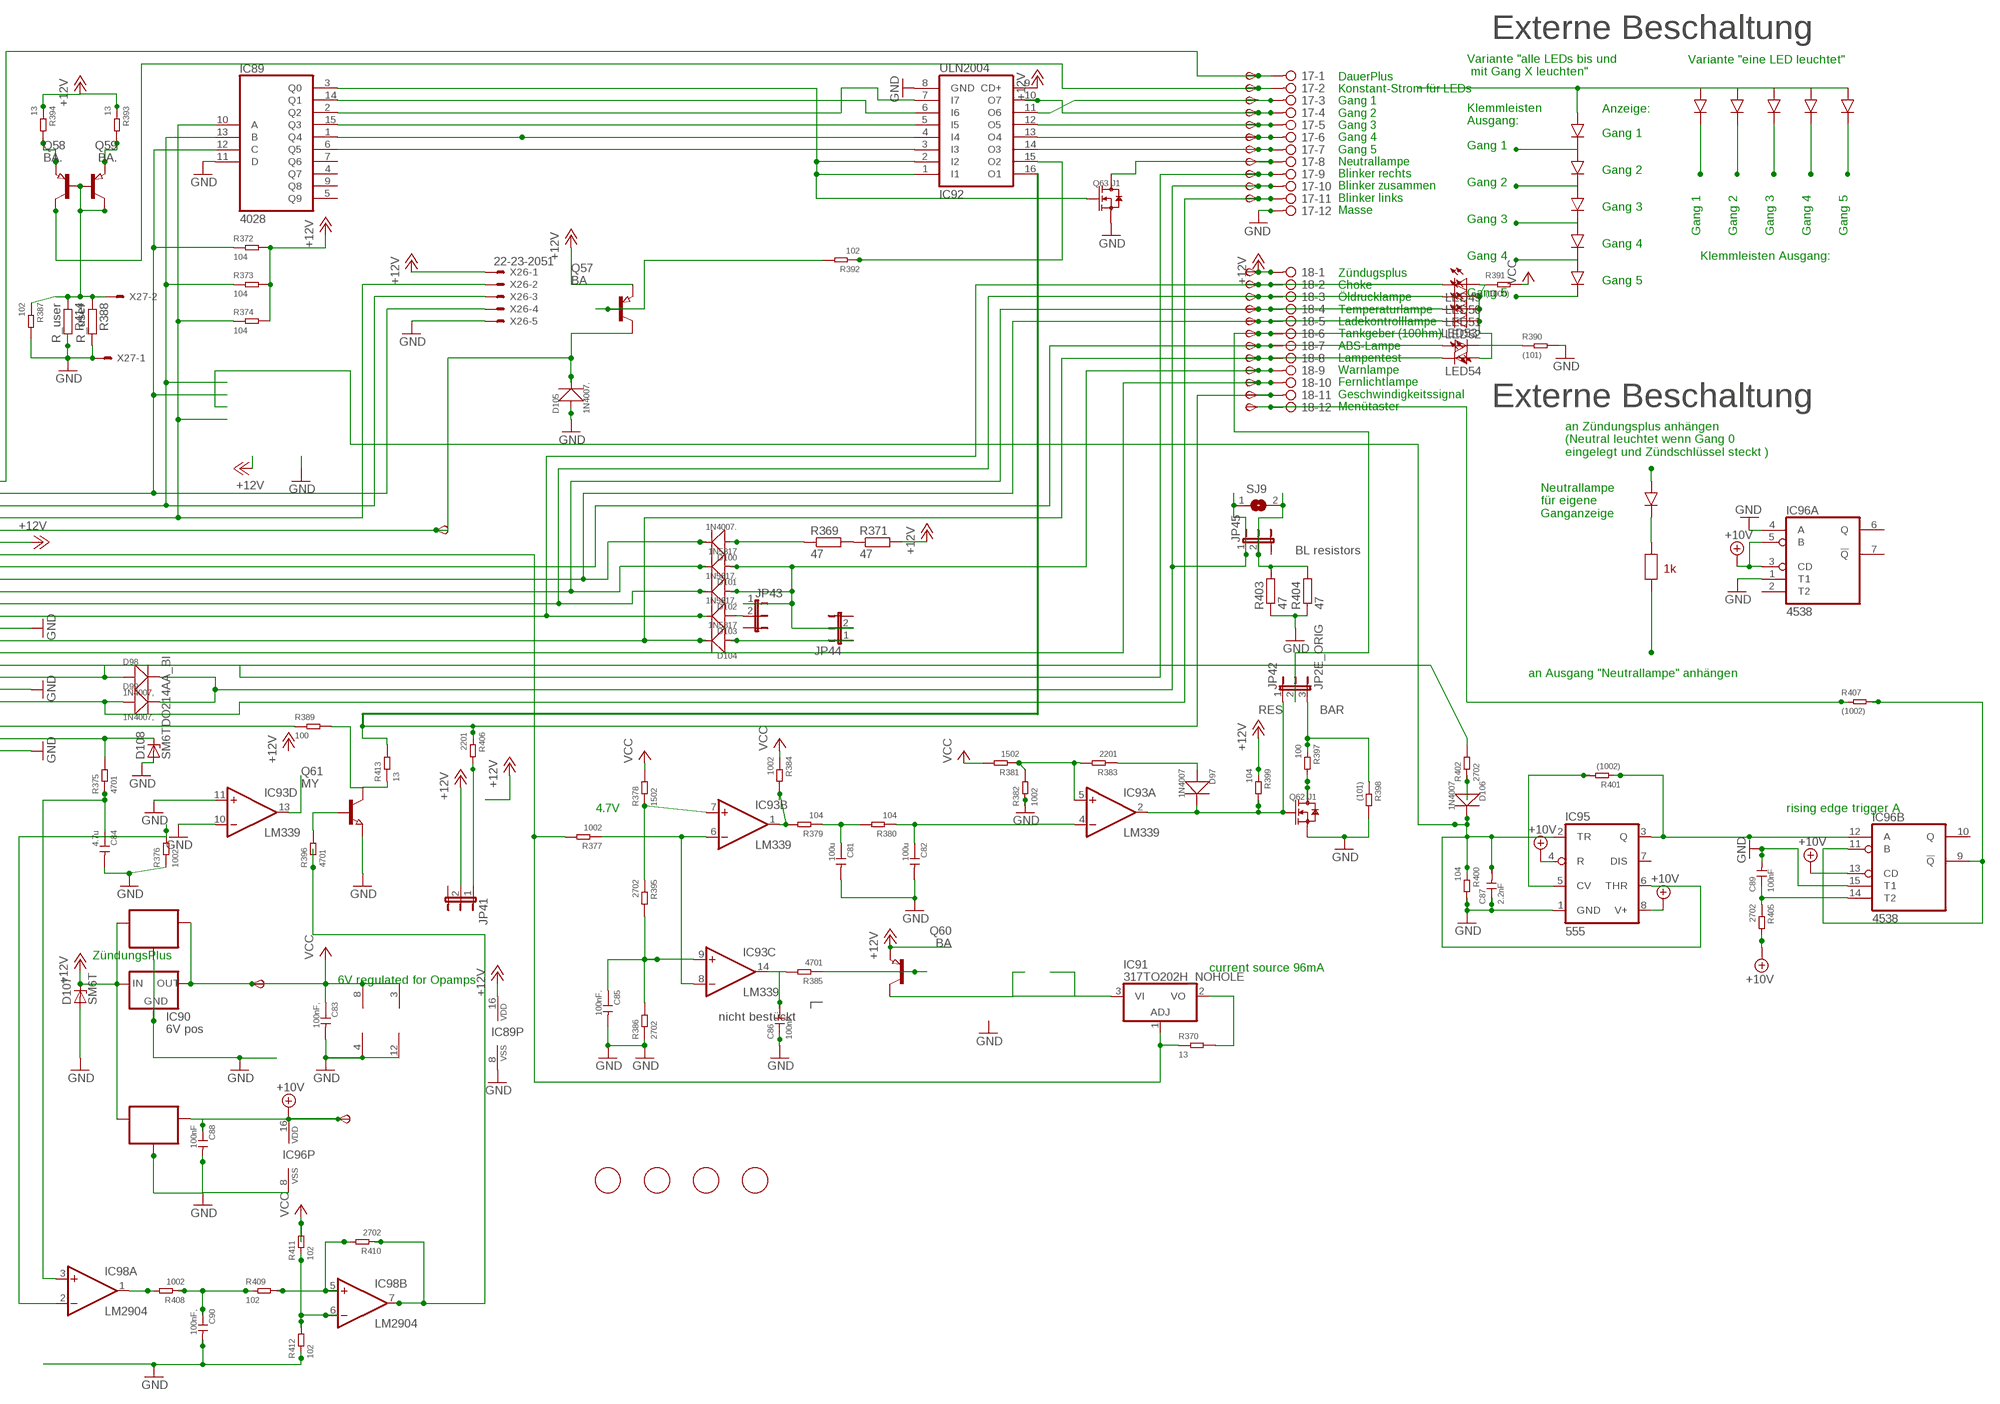
[diagram p17: schematic, sheet 9, part 2 of 2]
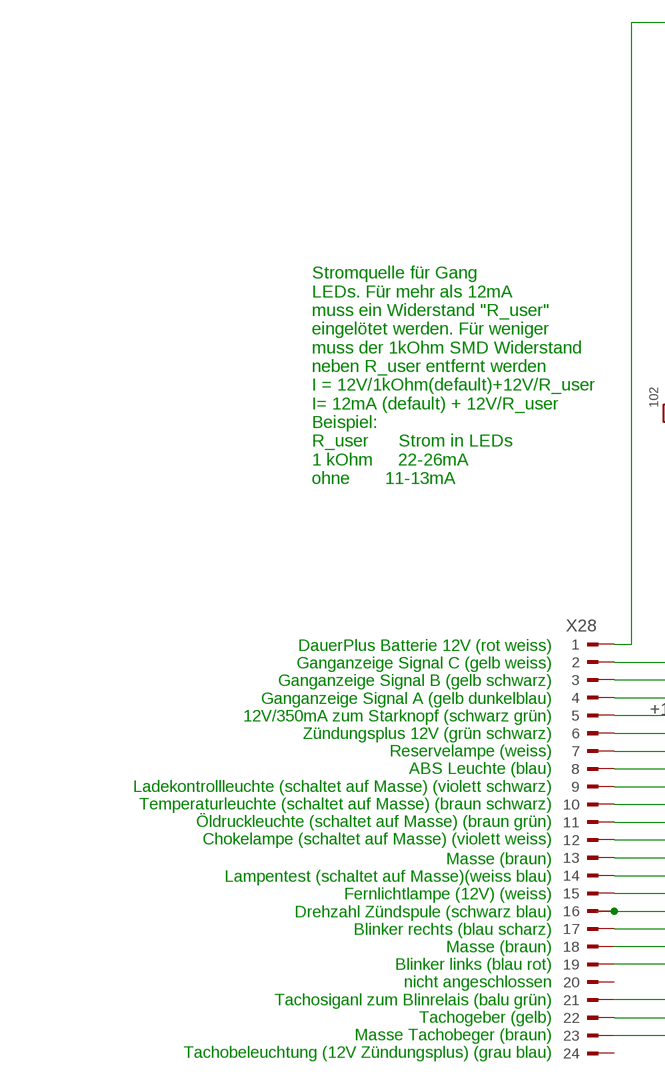
[diagram p18: schematic, sheet 10, part 1 of 2]
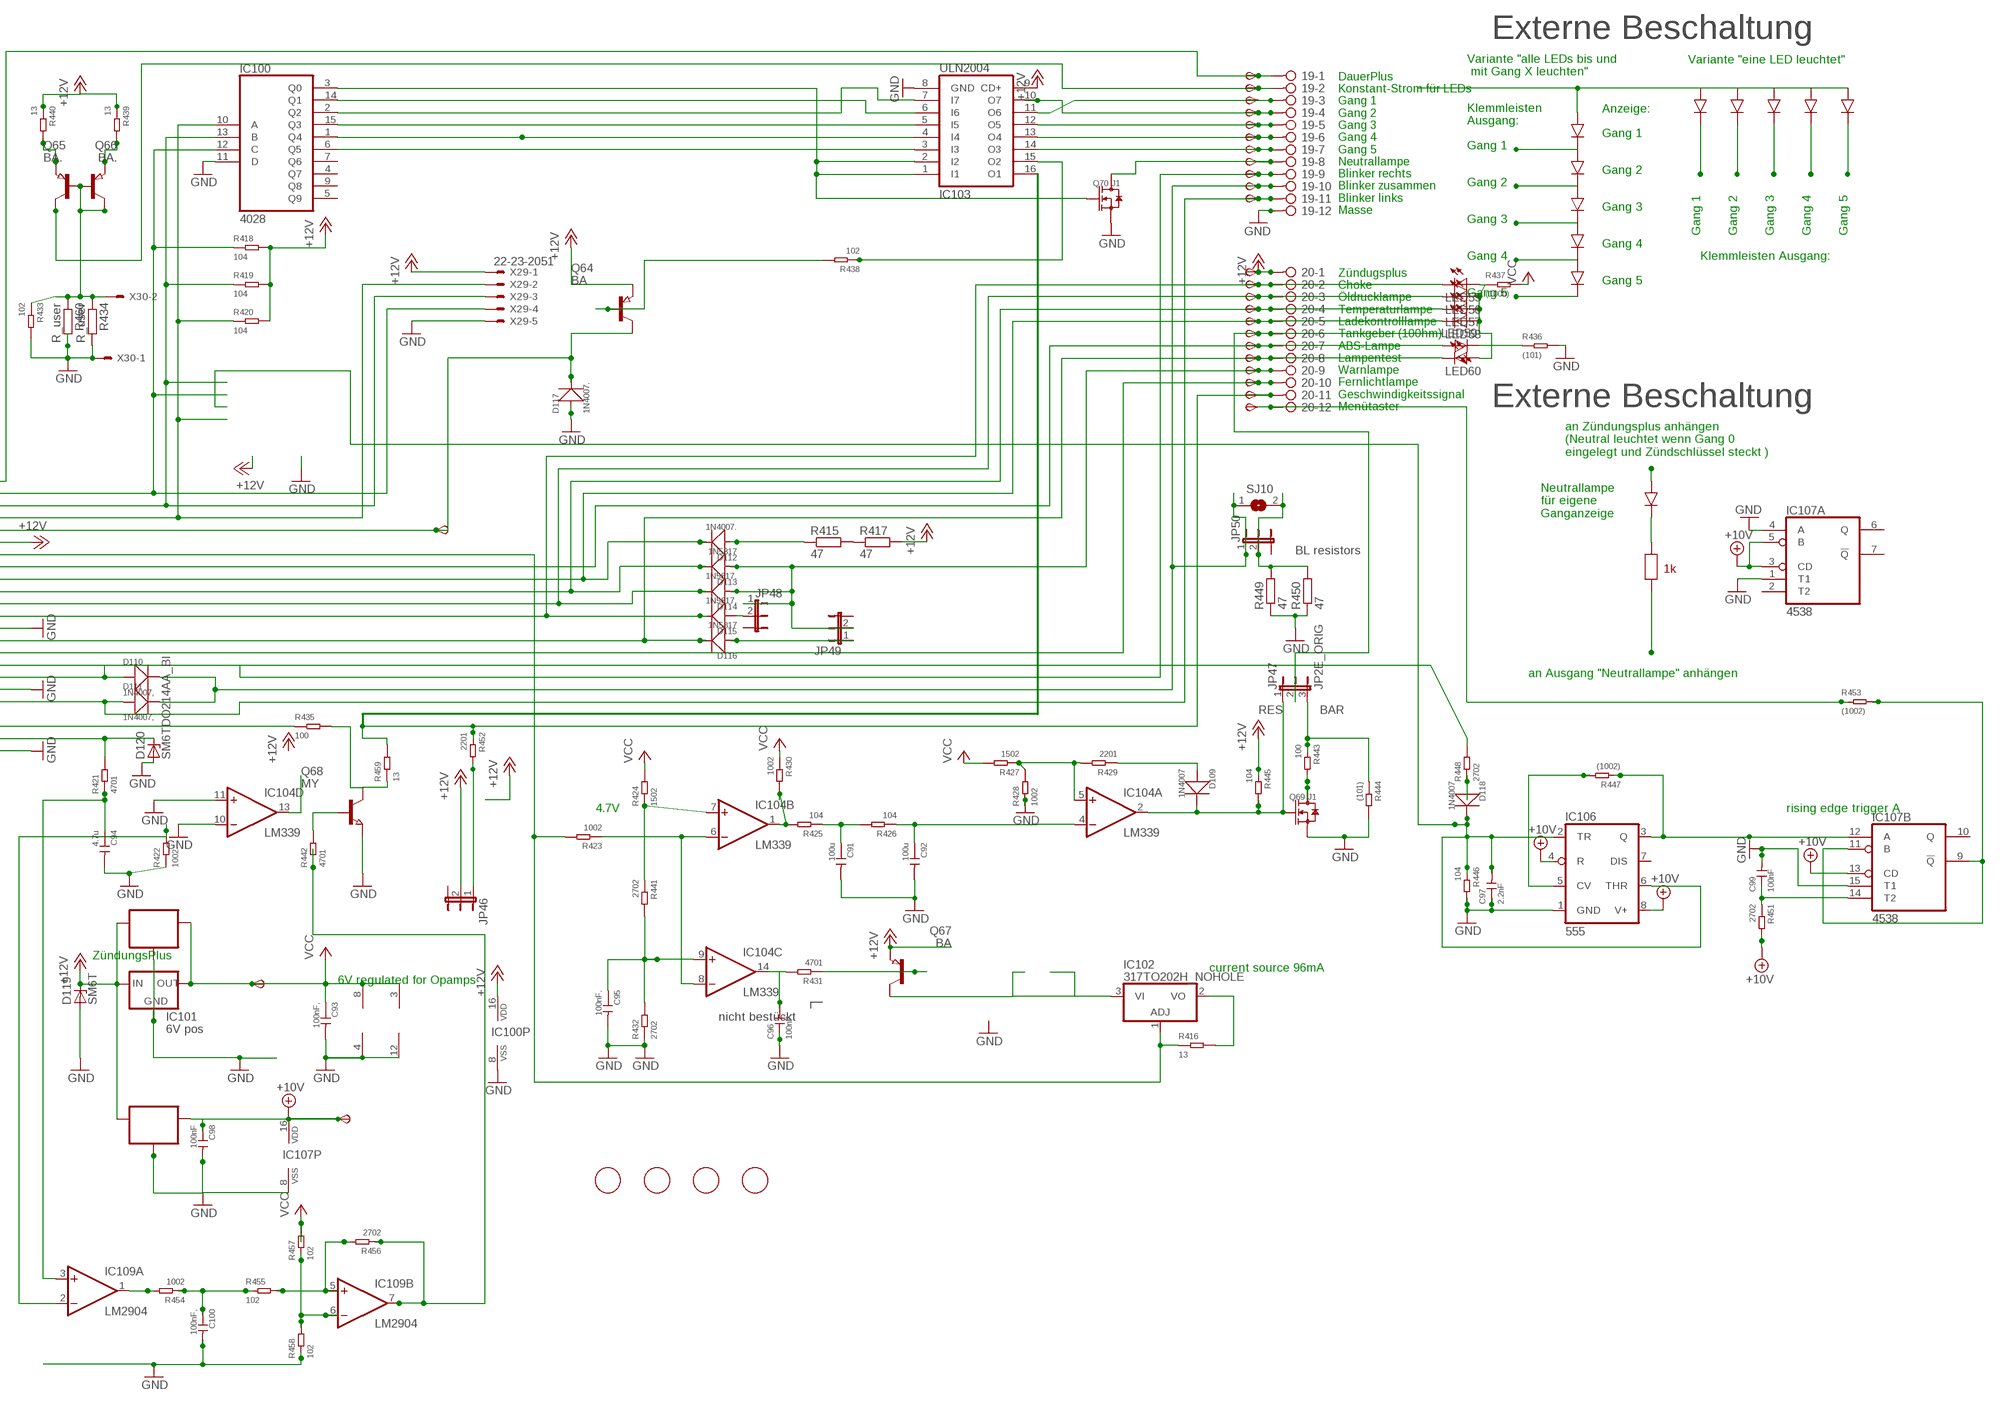
[diagram p19: schematic, sheet 10, part 2 of 2]
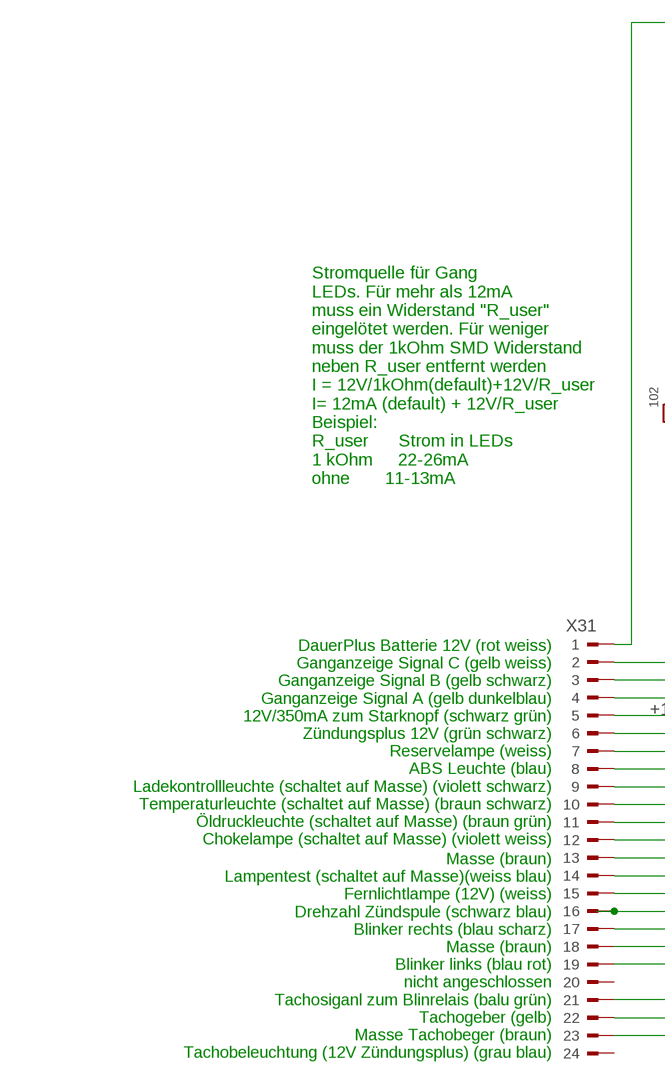
[diagram p20: schematic, sheet 11, part 1 of 2]
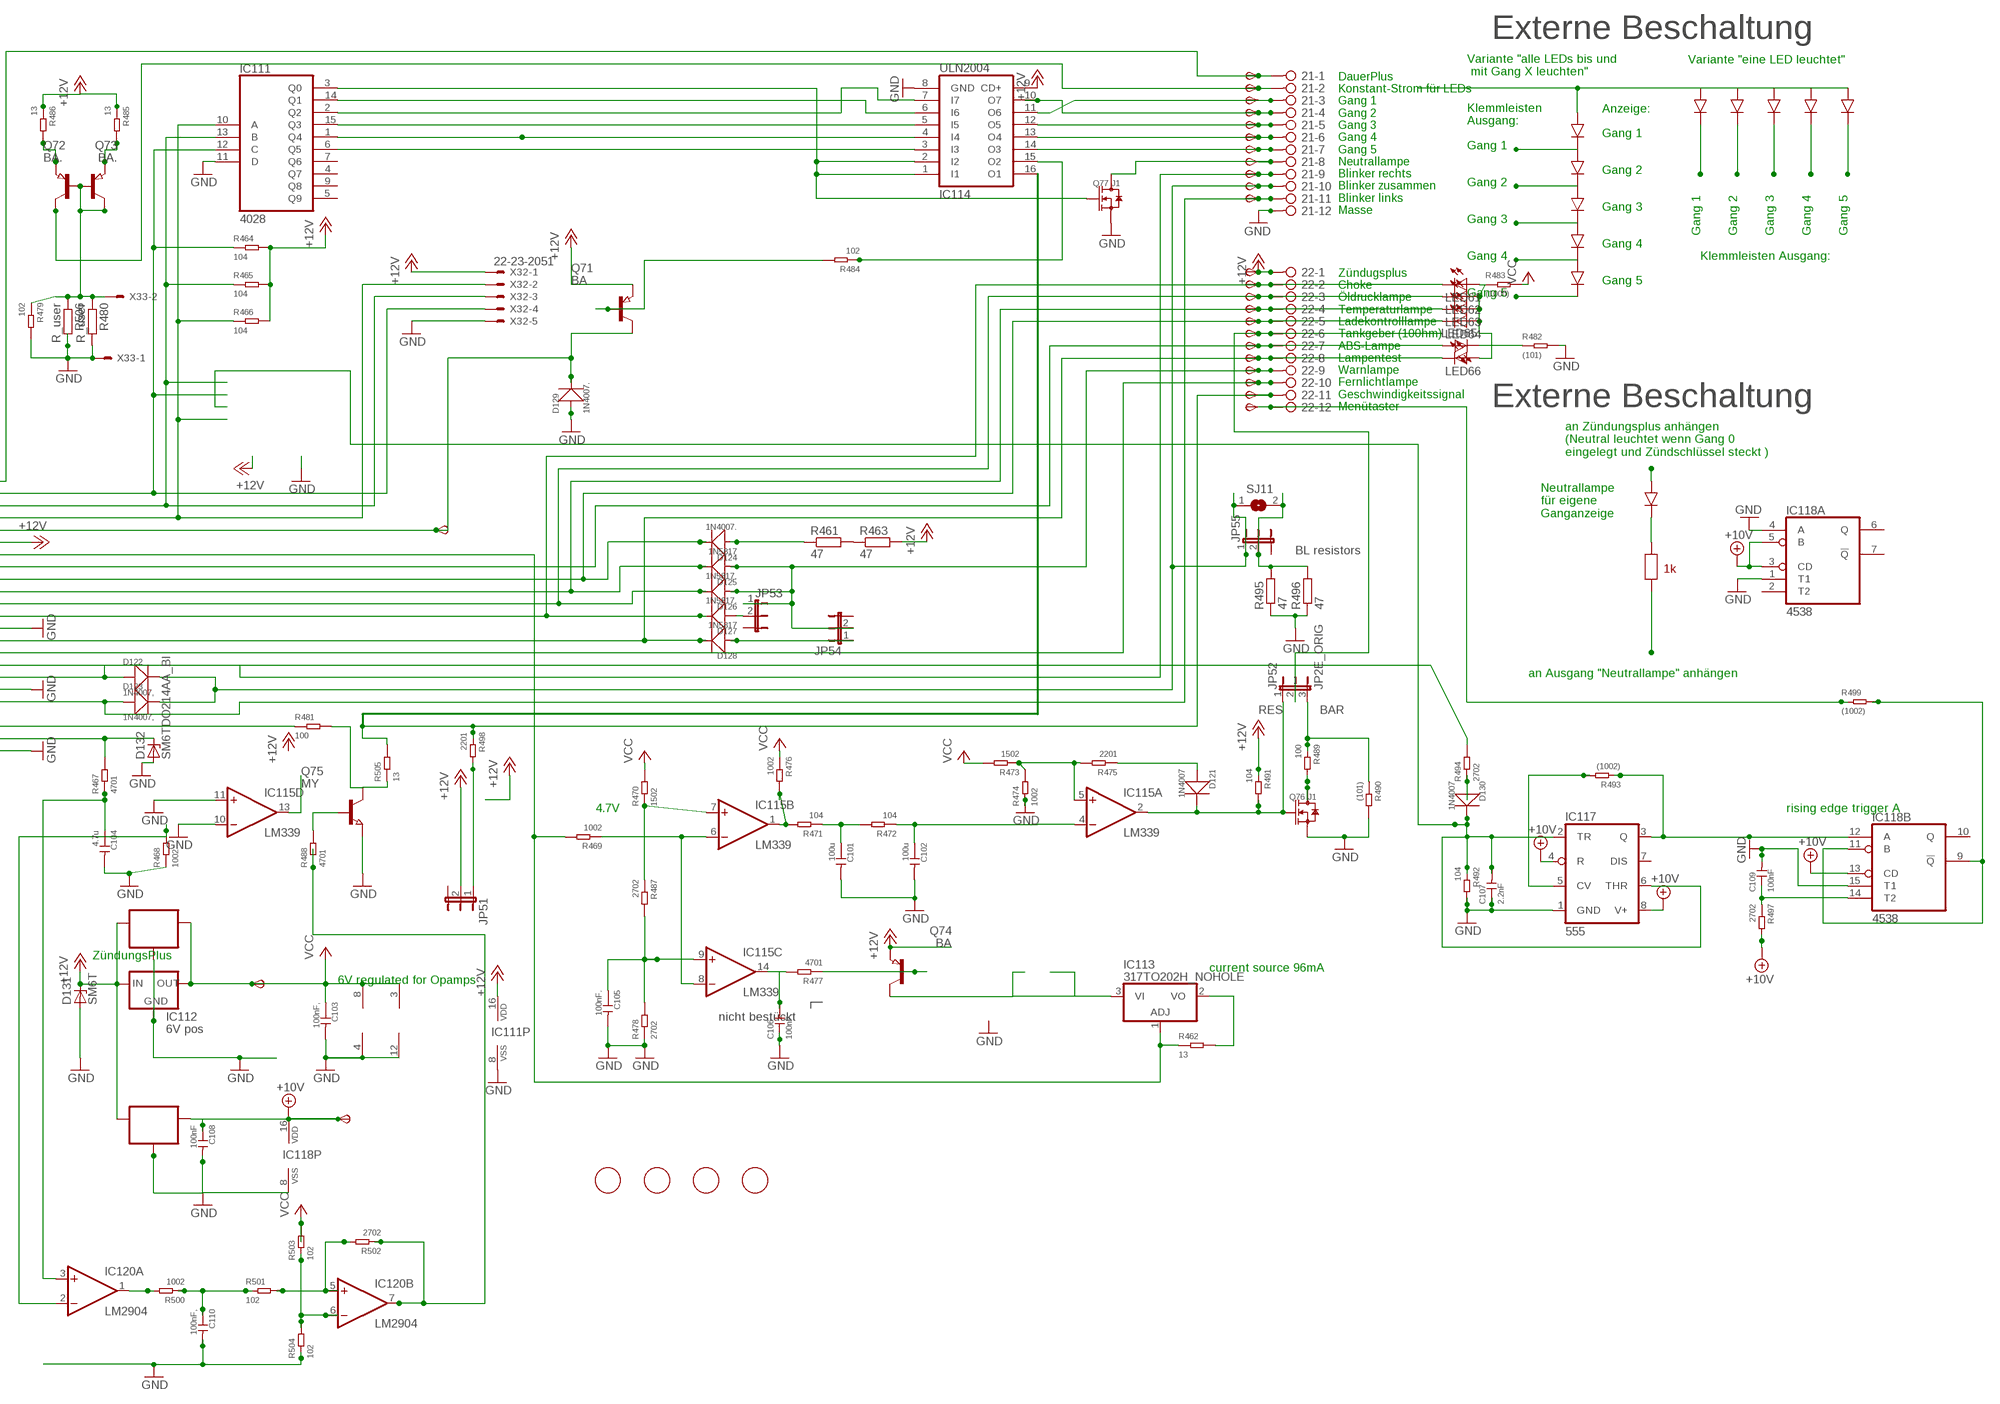
[diagram p21: schematic, sheet 11, part 2 of 2]
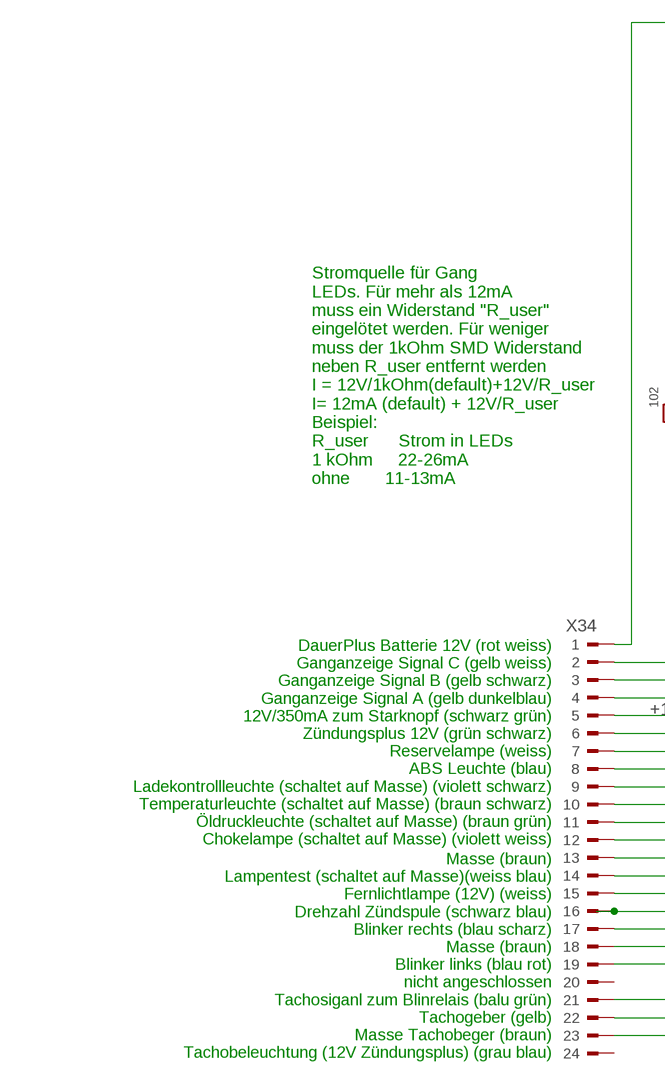
[diagram p22: schematic, sheet 12, part 1 of 2]
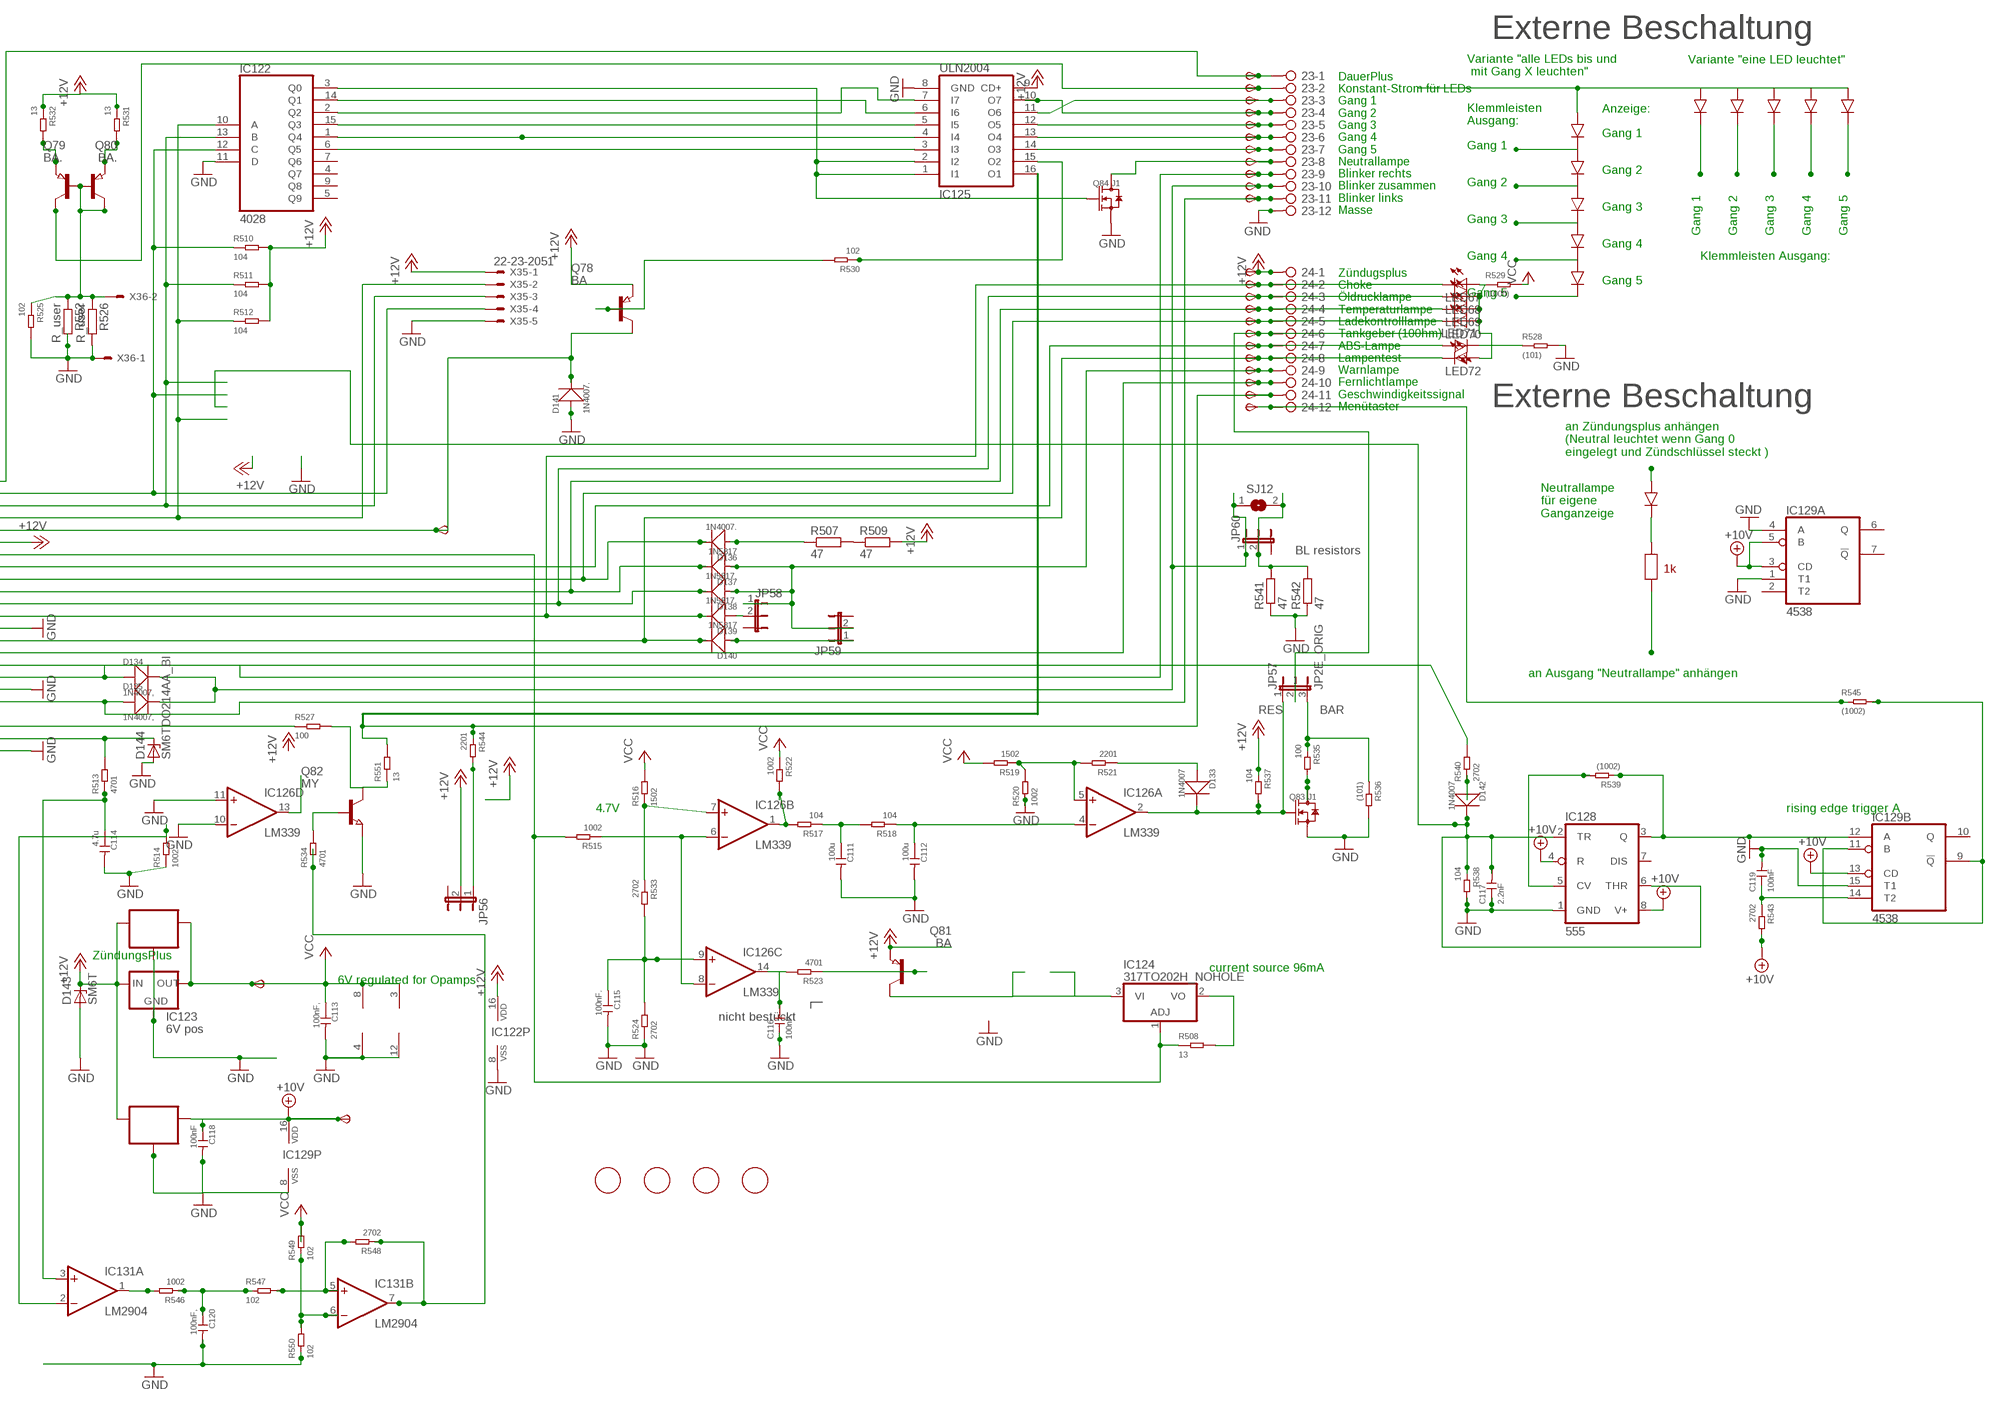
[diagram p23: schematic, sheet 12, part 2 of 2]

(export (version "E")
  (design (tool "Eeschema 10.0.6"))
  (components
    (comp (ref "3")
      (value "2081-1132")
      (footprint "eagle-import:12-PIN")
      (libsource (lib "eagle-import") (part "2081-1132"))
    )
    (comp (ref "4")
      (value "2081-1132")
      (footprint "eagle-import:12-PIN")
      (libsource (lib "eagle-import") (part "2081-1132"))
    )
    (comp (ref "6V1")
      (value "TPSB2.0")
      (footprint "eagle-import:B2.0")
      (libsource (lib "eagle-import") (part "TPSB2.0"))
    )
    (comp (ref "10V1")
      (value "TPSB2.0")
      (footprint "eagle-import:B2.0")
      (libsource (lib "eagle-import") (part "TPSB2.0"))
    )
    (comp (ref "C11")
      (value "100u")
      (footprint "eagle-import:C1206")
      (fields (field (name "MPN") "GRM31CR60J107ME39L"))
      (libsource (lib "eagle-import") (part "CERAMIC-100UF-6.3V-20%-X5R(1206)"))
    )
    (comp (ref "C12")
      (value "100u")
      (footprint "eagle-import:C1206")
      (fields (field (name "MPN") "GRM31CR60J107ME39L"))
      (libsource (lib "eagle-import") (part "CERAMIC-100UF-6.3V-20%-X5R(1206)"))
    )
    (comp (ref "C13")
      (value "100nF,")
      (footprint "eagle-import:C0805")
      (fields (field (name "MPN") "CC0805KRX7R9BB104"))
      (libsource (lib "eagle-import") (part "CERAMIC-100NF-50V-10%-X7R(0805)"))
    )
    (comp (ref "C14")
      (value "4.7u")
      (footprint "eagle-import:C0805")
      (fields (field (name "MPN") "CC0805KKX5R8BB475"))
      (libsource (lib "eagle-import") (part "CERAMIC-4.7UF-25V-10%-X5R(0805)"))
    )
    (comp (ref "C15")
      (value "100nF.")
      (footprint "eagle-import:C0805")
      (fields (field (name "MPN") "CC0805KRX7R9BB104"))
      (libsource (lib "eagle-import") (part "CERAMIC-100NF-50V-10%-X7R(0805)"))
    )
    (comp (ref "C16")
      (value "100nF.")
      (footprint "eagle-import:C0805")
      (fields (field (name "MPN") "CC0805KRX7R9BB104"))
      (libsource (lib "eagle-import") (part "CERAMIC-100NF-50V-10%-X7R(0805)"))
    )
    (comp (ref "C17")
      (value "2.2nF")
      (footprint "eagle-import:C0805")
      (fields (field (name "MPN") "CC0805KRX7R9BB104"))
      (libsource (lib "eagle-import") (part "CERAMIC-100NF-50V-10%-X7R(0805)"))
    )
    (comp (ref "C18")
      (value "100nF")
      (footprint "eagle-import:C0805")
      (fields (field (name "MPN") "CC0805KRX7R9BB104"))
      (libsource (lib "eagle-import") (part "CERAMIC-100NF-50V-10%-X7R(0805)"))
    )
    (comp (ref "C19")
      (value "100nF")
      (footprint "eagle-import:C0805")
      (fields (field (name "MPN") "CC0805KRX7R9BB104"))
      (libsource (lib "eagle-import") (part "CERAMIC-100NF-50V-10%-X7R(0805)"))
    )
    (comp (ref "C20")
      (value "100nF,")
      (footprint "eagle-import:C0805")
      (fields (field (name "MPN") "CC0805KRX7R9BB104"))
      (libsource (lib "eagle-import") (part "CERAMIC-100NF-50V-10%-X7R(0805)"))
    )
    (comp (ref "D13")
      (value "1N4007")
      (footprint "eagle-import:DO-214AC")
      (libsource (lib "eagle-import") (part "DIODE-GEN-PURPOSE-1KV-1A(DO-214AC)"))
    )
    (comp (ref "D14")
      (value "1N4007,")
      (footprint "eagle-import:DO-214AC")
      (fields (field (name "MPN") "1N4007"))
      (libsource (lib "eagle-import") (part "DIODE-GEN-PURPOSE-1KV-1A(DO-214AC)"))
    )
    (comp (ref "D15")
      (value "1N4007,")
      (footprint "eagle-import:DO-214AC")
      (fields (field (name "MPN") "1N4007"))
      (libsource (lib "eagle-import") (part "DIODE-GEN-PURPOSE-1KV-1A(DO-214AC)"))
    )
    (comp (ref "D16")
      (value "1N4007.")
      (footprint "eagle-import:DO-214AC")
      (fields (field (name "MPN") "1N4007"))
      (libsource (lib "eagle-import") (part "DIODE-GEN-PURPOSE-1KV-1A(DO-214AC)"))
    )
    (comp (ref "D17")
      (value "1N5817")
      (footprint "eagle-import:DO-214AC_SLIM")
      (libsource (lib "eagle-import") (part "DIODE-GEN-PURPOSE-1KV-1A(DO-214AC)DO-214AC/1206"))
    )
    (comp (ref "D18")
      (value "1N5817.")
      (footprint "eagle-import:DO-214AC_SLIM")
      (libsource (lib "eagle-import") (part "DIODE-GEN-PURPOSE-1KV-1A(DO-214AC)DO-214AC/1206"))
    )
    (comp (ref "D19")
      (value "1N5817.")
      (footprint "eagle-import:DO-214AC_SLIM")
      (libsource (lib "eagle-import") (part "DIODE-GEN-PURPOSE-1KV-1A(DO-214AC)DO-214AC/1206"))
    )
    (comp (ref "D20")
      (value "1N5817")
      (footprint "eagle-import:DO-214AC_SLIM")
      (libsource (lib "eagle-import") (part "DIODE-GEN-PURPOSE-1KV-1A(DO-214AC)DO-214AC/1206"))
    )
    (comp (ref "D21")
      (value "1N4007.")
      (footprint "eagle-import:DO-214AC")
      (fields (field (name "MPN") "1N4007"))
      (libsource (lib "eagle-import") (part "DIODE-GEN-PURPOSE-1KV-1A(DO-214AC)"))
    )
    (comp (ref "D22")
      (value "1N4007")
      (footprint "eagle-import:DO-214AC")
      (libsource (lib "eagle-import") (part "DIODE-GEN-PURPOSE-1KV-1A(DO-214AC)"))
    )
    (comp (ref "D23")
      (value "SM6T")
      (footprint "eagle-import:DO214AA")
      (libsource (lib "eagle-import") (part "SM6T"))
    )
    (comp (ref "D24")
      (value "SM6TDO214AA_BI")
      (footprint "eagle-import:DO214AA_BI")
      (libsource (lib "eagle-import") (part "SM6TDO214AA_BI"))
    )
    (comp (ref "FID5")
      (value "FIDUCIAL")
      (footprint "eagle-import:FIDUCIAL_1MM")
      (libsource (lib "eagle-import") (part "FIDUCIAL"))
    )
    (comp (ref "FID6")
      (value "FIDUCIAL")
      (footprint "eagle-import:FIDUCIAL_1MM")
      (libsource (lib "eagle-import") (part "FIDUCIAL"))
    )
    (comp (ref "FID7")
      (value "FIDUCIAL")
      (footprint "eagle-import:FIDUCIAL_1MM")
      (libsource (lib "eagle-import") (part "FIDUCIAL"))
    )
    (comp (ref "FID8")
      (value "FIDUCIAL")
      (footprint "eagle-import:FIDUCIAL_1MM")
      (libsource (lib "eagle-import") (part "FIDUCIAL"))
    )
    (comp (ref "IC12")
      (value "4028")
      (footprint "eagle-import:SO16")
      (libsource (lib "eagle-import") (part "4028D"))
    )
    (comp (ref "IC13")
      (value "6V pos")
      (footprint "eagle-import:78LXX")
      (libsource (lib "eagle-import") (part "v-reg_78LXX"))
    )
    (comp (ref "IC14")
      (value "317TO202H_NOHOLE")
      (footprint "eagle-import:TO220H_NOHOLE")
      (libsource (lib "eagle-import") (part "317TO202H_NOHOLE"))
    )
    (comp (ref "IC15")
      (value "ULN2004")
      (footprint "eagle-import:SO16")
      (libsource (lib "eagle-import") (part "ULN2004AD"))
    )
    (comp (ref "IC16")
      (value "LM339")
      (footprint "eagle-import:SO14")
      (libsource (lib "eagle-import") (part "LM339D"))
    )
    (comp (ref "IC17")
      (value "78L06")
      (footprint "eagle-import:SOT89_ROUND")
      (libsource (lib "eagle-import") (part "78LXXSOT89_ROUND"))
    )
    (comp (ref "IC18")
      (value "555")
      (footprint "eagle-import:SO08")
      (libsource (lib "eagle-import") (part "555DNE"))
    )
    (comp (ref "IC19")
      (value "4538")
      (footprint "eagle-import:SO16")
      (libsource (lib "eagle-import") (part "4538D"))
    )
    (comp (ref "IC20")
      (value "78L10")
      (footprint "eagle-import:SOT89_ROUND")
      (libsource (lib "eagle-import") (part "78LXXSOT89_ROUND"))
    )
    (comp (ref "IC21")
      (value "LM2904")
      (footprint "eagle-import:SO08")
      (libsource (lib "eagle-import") (part "LM358D"))
    )
    (comp (ref "JP6")
      (value "JP2EJP2_SMALLPADS")
      (footprint "eagle-import:JP2_SMALLPADS")
      (libsource (lib "eagle-import") (part "JP2EJP2_SMALLPADS"))
    )
    (comp (ref "JP7")
      (value "JP2E_ORIG")
      (footprint "eagle-import:JP2_ORIG_SMALLPADS")
      (libsource (lib "eagle-import") (part "JP2E_ORIG"))
    )
    (comp (ref "JP8")
      (value "JP2EJP2_SMALLPADS")
      (footprint "eagle-import:JP2_SMALLPADS")
      (libsource (lib "eagle-import") (part "JP2EJP2_SMALLPADS"))
    )
    (comp (ref "JP9")
      (value "JP2EJP2_SMALLPADS")
      (footprint "eagle-import:JP2_SMALLPADS")
      (libsource (lib "eagle-import") (part "JP2EJP2_SMALLPADS"))
    )
    (comp (ref "JP10")
      (value "JP2EJP2_SMALLPADS")
      (footprint "eagle-import:JP2_SMALLPADS")
      (libsource (lib "eagle-import") (part "JP2EJP2_SMALLPADS"))
    )
    (comp (ref "LED7")
      (value "LEDLD260")
      (footprint "eagle-import:LD260")
      (libsource (lib "eagle-import") (part "LEDLD260"))
    )
    (comp (ref "LED8")
      (value "LEDLD260")
      (footprint "eagle-import:LD260")
      (libsource (lib "eagle-import") (part "LEDLD260"))
    )
    (comp (ref "LED9")
      (value "LEDLD260")
      (footprint "eagle-import:LD260")
      (libsource (lib "eagle-import") (part "LEDLD260"))
    )
    (comp (ref "LED10")
      (value "LEDLD260")
      (footprint "eagle-import:LD260")
      (libsource (lib "eagle-import") (part "LEDLD260"))
    )
    (comp (ref "LED11")
      (value "LEDLD260")
      (footprint "eagle-import:LD260")
      (libsource (lib "eagle-import") (part "LEDLD260"))
    )
    (comp (ref "LED12")
      (value "LEDLD260")
      (footprint "eagle-import:LD260")
      (libsource (lib "eagle-import") (part "LEDLD260"))
    )
    (comp (ref "Q8")
      (value "BA")
      (footprint "eagle-import:SOT89")
      (libsource (lib "eagle-import") (part "PNP-TRANSISTOR_SOT89"))
    )
    (comp (ref "Q9")
      (value "BA.")
      (footprint "eagle-import:SOT89")
      (libsource (lib "eagle-import") (part "PNP-TRANSISTOR_SOT89"))
    )
    (comp (ref "Q10")
      (value "BA.")
      (footprint "eagle-import:SOT89")
      (libsource (lib "eagle-import") (part "PNP-TRANSISTOR_SOT89"))
    )
    (comp (ref "Q11")
      (value "BA")
      (footprint "eagle-import:SOT89")
      (libsource (lib "eagle-import") (part "PNP-TRANSISTOR_SOT89"))
    )
    (comp (ref "Q12")
      (value "MY")
      (footprint "eagle-import:SOT89")
      (libsource (lib "eagle-import") (part "NPN-TRANSISTOR_SOT89"))
    )
    (comp (ref "Q13")
      (value "J1")
      (footprint "eagle-import:SOT-23")
      (fields (field (name "MPN") "BSS138W-7-F"))
      (libsource (lib "eagle-import") (part "SMD-MOSFET-N-CH-50V-200MA-BSS138W-7-F(SOT-23)"))
    )
    (comp (ref "Q14")
      (value "J1")
      (footprint "eagle-import:SOT-23")
      (fields (field (name "MPN") "BSS138W-7-F"))
      (libsource (lib "eagle-import") (part "SMD-MOSFET-N-CH-50V-200MA-BSS138W-7-F(SOT-23)"))
    )
    (comp (ref "R47")
      (value "47")
      (footprint "eagle-import:V235_17_1MM")
      (libsource (lib "eagle-import") (part "R-EU_V235/17_1MM"))
    )
    (comp (ref "R48")
      (value "13")
      (footprint "eagle-import:R1206")
      (fields (field (name "MPN") "RC1206JR-0713RL"))
      (libsource (lib "eagle-import") (part "SMD-RES-13R-5%-1/4W(1206)"))
    )
    (comp (ref "R49")
      (value "47")
      (footprint "eagle-import:V235_17_1MM")
      (libsource (lib "eagle-import") (part "R-EU_V235/17_1MM"))
    )
    (comp (ref "R50")
      (value "104")
      (footprint "eagle-import:R0805")
      (fields (field (name "MPN") "RC0805FR-0710KL"))
      (libsource (lib "eagle-import") (part "SMD-RES-10K-1%-1/8W(0805)"))
    )
    (comp (ref "R51")
      (value "104")
      (footprint "eagle-import:R0805")
      (fields (field (name "MPN") "RC0805FR-0710KL"))
      (libsource (lib "eagle-import") (part "SMD-RES-10K-1%-1/8W(0805)"))
    )
    (comp (ref "R52")
      (value "104")
      (footprint "eagle-import:R0805")
      (fields (field (name "MPN") "RC0805FR-0710KL"))
      (libsource (lib "eagle-import") (part "SMD-RES-10K-1%-1/8W(0805)"))
    )
    (comp (ref "R53")
      (value "4701")
      (footprint "eagle-import:R0805")
      (fields (field (name "MPN") "RC0805JR-074K7L"))
      (libsource (lib "eagle-import") (part "SMD-RES-4.7K-5%-1/8W(0805)"))
    )
    (comp (ref "R54")
      (value "1002")
      (footprint "eagle-import:R0805")
      (fields (field (name "MPN") "RC0805FR-0710KL"))
      (libsource (lib "eagle-import") (part "SMD-RES-10K-1%-1/8W(0805)"))
    )
    (comp (ref "R55")
      (value "1002")
      (footprint "eagle-import:R0805")
      (fields (field (name "MPN") "RC0805FR-0710KL"))
      (libsource (lib "eagle-import") (part "SMD-RES-10K-1%-1/8W(0805)"))
    )
    (comp (ref "R56")
      (value "1502")
      (footprint "eagle-import:R0805")
      (fields (field (name "MPN") "RC0805FR-0710KL"))
      (libsource (lib "eagle-import") (part "SMD-RES-10K-1%-1/8W(0805)"))
    )
    (comp (ref "R57")
      (value "104")
      (footprint "eagle-import:R0805")
      (fields (field (name "MPN") "RC0805FR-0710KL"))
      (libsource (lib "eagle-import") (part "SMD-RES-10K-1%-1/8W(0805)"))
    )
    (comp (ref "R58")
      (value "104")
      (footprint "eagle-import:R0805")
      (fields (field (name "MPN") "RC0805FR-0710KL"))
      (libsource (lib "eagle-import") (part "SMD-RES-10K-1%-1/8W(0805)"))
    )
    (comp (ref "R59")
      (value "1502")
      (footprint "eagle-import:R0805")
      (fields (field (name "MPN") "RC0805FR-0710KL"))
      (libsource (lib "eagle-import") (part "SMD-RES-10K-1%-1/8W(0805)"))
    )
    (comp (ref "R60")
      (value "1002")
      (footprint "eagle-import:R0805")
      (fields (field (name "MPN") "RC0805FR-0710KL"))
      (libsource (lib "eagle-import") (part "SMD-RES-10K-1%-1/8W(0805)"))
    )
    (comp (ref "R61")
      (value "2201")
      (footprint "eagle-import:R0805")
      (fields (field (name "MPN") "RC0805JR-072K2L"))
      (libsource (lib "eagle-import") (part "SMD-RES-2.2K-5%-1/8W(0805)"))
    )
    (comp (ref "R62")
      (value "1002")
      (footprint "eagle-import:R0805")
      (fields (field (name "MPN") "RC0805FR-0710KL"))
      (libsource (lib "eagle-import") (part "SMD-RES-10K-1%-1/8W(0805)"))
    )
    (comp (ref "R63")
      (value "4701")
      (footprint "eagle-import:R0805")
      (fields (field (name "MPN") "RC0805JR-074K7L"))
      (libsource (lib "eagle-import") (part "SMD-RES-4.7K-5%-1/8W(0805)"))
    )
    (comp (ref "R64")
      (value "2702")
      (footprint "eagle-import:R0805")
      (fields (field (name "MPN") "RC0805JR-074K7L"))
      (libsource (lib "eagle-import") (part "SMD-RES-4.7K-5%-1/8W(0805)"))
    )
    (comp (ref "R65")
      (value "102")
      (footprint "eagle-import:R0805")
      (fields (field (name "MPN") "RC0805JR-071KL"))
      (libsource (lib "eagle-import") (part "SMD-RES-1K-5%-1/8W(0805)"))
    )
    (comp (ref "R66")
      (value "R_user")
      (footprint "eagle-import:R0805")
      (libsource (lib "eagle-import") (part "R-EU_R0805"))
    )
    (comp (ref "R67")
      (value "100")
      (footprint "eagle-import:R0805")
      (fields (field (name "MPN") "RC0805JR-07220RL"))
      (libsource (lib "eagle-import") (part "SMD-RES-220R-5%-1/8W(0805)"))
    )
    (comp (ref "R68")
      (value "(101)")
      (footprint "eagle-import:R0805")
      (fields (field (name "MPN") "RC0805JR-07100RL"))
      (libsource (lib "eagle-import") (part "SMD-RES-100R-5%-1/8W(0805)"))
    )
    (comp (ref "R69")
      (value "(1000)")
      (footprint "eagle-import:R0805")
      (fields (field (name "MPN") "RC0805JR-07100RL"))
      (libsource (lib "eagle-import") (part "SMD-RES-100R-5%-1/8W(0805)"))
    )
    (comp (ref "R70")
      (value "102")
      (footprint "eagle-import:R0805")
      (fields (field (name "MPN") "RC0805JR-071KL"))
      (libsource (lib "eagle-import") (part "SMD-RES-1K-5%-1/8W(0805)"))
    )
    (comp (ref "R71")
      (value "13")
      (footprint "eagle-import:R1206")
      (fields (field (name "MPN") "RC1206JR-0713RL"))
      (libsource (lib "eagle-import") (part "SMD-RES-13R-5%-1/4W(1206)"))
    )
    (comp (ref "R72")
      (value "13")
      (footprint "eagle-import:R1206")
      (fields (field (name "MPN") "RC1206JR-0713RL"))
      (libsource (lib "eagle-import") (part "SMD-RES-13R-5%-1/4W(1206)"))
    )
    (comp (ref "R73")
      (value "2702")
      (footprint "eagle-import:R0805")
      (fields (field (name "MPN") "RC0805JR-074K7L"))
      (libsource (lib "eagle-import") (part "SMD-RES-4.7K-5%-1/8W(0805)"))
    )
    (comp (ref "R74")
      (value "4701")
      (footprint "eagle-import:R0805")
      (fields (field (name "MPN") "RC0805JR-074K7L"))
      (libsource (lib "eagle-import") (part "SMD-RES-4.7K-5%-1/8W(0805)"))
    )
    (comp (ref "R75")
      (value "100")
      (footprint "eagle-import:R0805")
      (fields (field (name "MPN") "RC0805JR-072K2L"))
      (libsource (lib "eagle-import") (part "SMD-RES-2.2K-5%-1/8W(0805)"))
    )
    (comp (ref "R76")
      (value "(101)")
      (footprint "eagle-import:R0805")
      (fields (field (name "MPN") "RC0805JR-072K2L"))
      (libsource (lib "eagle-import") (part "SMD-RES-2.2K-5%-1/8W(0805)"))
    )
    (comp (ref "R77")
      (value "104")
      (footprint "eagle-import:R0805")
      (fields (field (name "MPN") "RC0805FR-0710KL"))
      (libsource (lib "eagle-import") (part "SMD-RES-10K-1%-1/8W(0805)"))
    )
    (comp (ref "R78")
      (value "104")
      (footprint "eagle-import:R0805")
      (fields (field (name "MPN") "RC0805FR-0710KL"))
      (libsource (lib "eagle-import") (part "SMD-RES-10K-1%-1/8W(0805)"))
    )
    (comp (ref "R79")
      (value "(1002)")
      (footprint "eagle-import:R0805")
      (fields (field (name "MPN") "RC0805FR-0710KL"))
      (libsource (lib "eagle-import") (part "SMD-RES-10K-1%-1/8W(0805)"))
    )
    (comp (ref "R80")
      (value "2702")
      (footprint "eagle-import:R0805")
      (fields (field (name "MPN") "RC0805FR-0710KL"))
      (libsource (lib "eagle-import") (part "SMD-RES-10K-1%-1/8W(0805)"))
    )
    (comp (ref "R81")
      (value "47")
      (footprint "eagle-import:V235_17_1MM")
      (libsource (lib "eagle-import") (part "R-EU_V235/17_1MM"))
    )
    (comp (ref "R82")
      (value "47")
      (footprint "eagle-import:V235_17_1MM")
      (libsource (lib "eagle-import") (part "R-EU_V235/17_1MM"))
    )
    (comp (ref "R83")
      (value "2702")
      (footprint "eagle-import:R0805")
      (fields (field (name "MPN") "RC0805JR-074K7L"))
      (libsource (lib "eagle-import") (part "SMD-RES-4.7K-5%-1/8W(0805)"))
    )
    (comp (ref "R84")
      (value "2201")
      (footprint "eagle-import:R0805")
      (fields (field (name "MPN") "RC0805JR-072K2L"))
      (libsource (lib "eagle-import") (part "SMD-RES-2.2K-5%-1/8W(0805)"))
    )
    (comp (ref "R85")
      (value "(1002)")
      (footprint "eagle-import:R0805")
      (fields (field (name "MPN") "RC0805JR-074K7L"))
      (libsource (lib "eagle-import") (part "SMD-RES-4.7K-5%-1/8W(0805)"))
    )
    (comp (ref "R86")
      (value "1002")
      (footprint "eagle-import:R0805")
      (fields (field (name "MPN") "RC0805FR-0710KL"))
      (libsource (lib "eagle-import") (part "SMD-RES-10K-1%-1/8W(0805)"))
    )
    (comp (ref "R87")
      (value "102")
      (footprint "eagle-import:R0805")
      (fields (field (name "MPN") "RC0805JR-071KL"))
      (libsource (lib "eagle-import") (part "SMD-RES-1K-5%-1/8W(0805)"))
    )
    (comp (ref "R88")
      (value "2702")
      (footprint "eagle-import:R0805")
      (fields (field (name "MPN") "RC0805JR-074K7L"))
      (libsource (lib "eagle-import") (part "SMD-RES-4.7K-5%-1/8W(0805)"))
    )
    (comp (ref "R89")
      (value "102")
      (footprint "eagle-import:R0805")
      (fields (field (name "MPN") "RC0805JR-071KL"))
      (libsource (lib "eagle-import") (part "SMD-RES-1K-5%-1/8W(0805)"))
    )
    (comp (ref "R90")
      (value "102")
      (footprint "eagle-import:R0805")
      (fields (field (name "MPN") "RC0805JR-071KL"))
      (libsource (lib "eagle-import") (part "SMD-RES-1K-5%-1/8W(0805)"))
    )
    (comp (ref "R91")
      (value "13")
      (footprint "eagle-import:R1206")
      (fields (field (name "MPN") "RC1206JR-0713RL"))
      (libsource (lib "eagle-import") (part "SMD-RES-13R-5%-1/4W(1206)"))
    )
    (comp (ref "R92")
      (value "R_user")
      (footprint "eagle-import:R0805")
      (libsource (lib "eagle-import") (part "R-EU_R0805"))
    )
    (comp (ref "SJ2") (value "SJ") (footprint "eagle-import:SJ") (libsource (lib "eagle-import") (part "SJ")))
    (comp (ref "START1")
      (value "TPSB2.0")
      (footprint "eagle-import:B2.0")
      (libsource (lib "eagle-import") (part "TPSB2.0"))
    )
    (comp (ref "TP14")
      (value "TPSB2.0")
      (footprint "eagle-import:B2.0")
      (libsource (lib "eagle-import") (part "TPSB2.0"))
    )
    (comp (ref "TP15")
      (value "TPSB2.0")
      (footprint "eagle-import:B2.0")
      (libsource (lib "eagle-import") (part "TPSB2.0"))
    )
    (comp (ref "TP20")
      (value "TPSB2.0")
      (footprint "eagle-import:B2.0")
      (libsource (lib "eagle-import") (part "TPSB2.0"))
    )
    (comp (ref "TP27")
      (value "TPSB2.0")
      (footprint "eagle-import:B2.0")
      (libsource (lib "eagle-import") (part "TPSB2.0"))
    )
    (comp (ref "TP28")
      (value "TPSB2.0")
      (footprint "eagle-import:B2.0")
      (libsource (lib "eagle-import") (part "TPSB2.0"))
    )
    (comp (ref "TP29")
      (value "TPSB2.0")
      (footprint "eagle-import:B2.0")
      (libsource (lib "eagle-import") (part "TPSB2.0"))
    )
    (comp (ref "TP30")
      (value "TPSB2.0")
      (footprint "eagle-import:B2.0")
      (libsource (lib "eagle-import") (part "TPSB2.0"))
    )
    (comp (ref "TP31")
      (value "TPSB2.0")
      (footprint "eagle-import:B2.0")
      (libsource (lib "eagle-import") (part "TPSB2.0"))
    )
    (comp (ref "TP32")
      (value "TPSB2.0")
      (footprint "eagle-import:B2.0")
      (libsource (lib "eagle-import") (part "TPSB2.0"))
    )
    (comp (ref "TP33")
      (value "TPSB2.0")
      (footprint "eagle-import:B2.0")
      (libsource (lib "eagle-import") (part "TPSB2.0"))
    )
    (comp (ref "TP34")
      (value "TPSB2.0")
      (footprint "eagle-import:B2.0")
      (libsource (lib "eagle-import") (part "TPSB2.0"))
    )
    (comp (ref "TP35")
      (value "TPSB2.0")
      (footprint "eagle-import:B2.0")
      (libsource (lib "eagle-import") (part "TPSB2.0"))
    )
    (comp (ref "TP36")
      (value "TPSB2.0")
      (footprint "eagle-import:B2.0")
      (libsource (lib "eagle-import") (part "TPSB2.0"))
    )
    (comp (ref "TP37")
      (value "TPSB2.0")
      (footprint "eagle-import:B2.0")
      (libsource (lib "eagle-import") (part "TPSB2.0"))
    )
    (comp (ref "TP38")
      (value "TPSB2.0")
      (footprint "eagle-import:B2.0")
      (libsource (lib "eagle-import") (part "TPSB2.0"))
    )
    (comp (ref "TP39")
      (value "TPSB2.0")
      (footprint "eagle-import:B2.0")
      (libsource (lib "eagle-import") (part "TPSB2.0"))
    )
    (comp (ref "TP40")
      (value "TPSB2.0")
      (footprint "eagle-import:B2.0")
      (libsource (lib "eagle-import") (part "TPSB2.0"))
    )
    (comp (ref "TP41")
      (value "TPSB2.0")
      (footprint "eagle-import:B2.0")
      (libsource (lib "eagle-import") (part "TPSB2.0"))
    )
    (comp (ref "TP42")
      (value "TPSB1,27")
      (footprint "eagle-import:B1,27")
      (libsource (lib "eagle-import") (part "TPSB1,27"))
    )
    (comp (ref "TP43")
      (value "TPSB2.0")
      (footprint "eagle-import:B2.0")
      (libsource (lib "eagle-import") (part "TPSB2.0"))
    )
    (comp (ref "TP44")
      (value "TPSB2.0")
      (footprint "eagle-import:B2.0")
      (libsource (lib "eagle-import") (part "TPSB2.0"))
    )
    (comp (ref "TP45")
      (value "TPSB2.0")
      (footprint "eagle-import:B2.0")
      (libsource (lib "eagle-import") (part "TPSB2.0"))
    )
    (comp (ref "TP46")
      (value "TPSB2.0")
      (footprint "eagle-import:B2.0")
      (libsource (lib "eagle-import") (part "TPSB2.0"))
    )
    (comp (ref "X4")
      (value "CON_BMWV2")
      (footprint "eagle-import:24-PIN_V2")
      (libsource (lib "eagle-import") (part "CON_BMWV2"))
    )
    (comp (ref "X5")
      (value "22-23-2051")
      (footprint "eagle-import:22-23-2051")
      (fields (field (name "MF") "MOLEX"))
      (libsource (lib "eagle-import") (part "22-23-2051"))
    )
    (comp (ref "X6")
      (value "22-23-2021")
      (footprint "eagle-import:22-23-2021")
      (fields (field (name "MF") "MOLEX"))
      (libsource (lib "eagle-import") (part "22-23-2021"))
    )
    (comp (ref "5")
      (value "2081-1132")
      (footprint "eagle-import:12-PIN")
      (libsource (lib "eagle-import") (part "2081-1132"))
    )
    (comp (ref "6")
      (value "2081-1132")
      (footprint "eagle-import:12-PIN")
      (libsource (lib "eagle-import") (part "2081-1132"))
    )
    (comp (ref "6V2")
      (value "TPSB2.0")
      (footprint "eagle-import:B2.0")
      (libsource (lib "eagle-import") (part "TPSB2.0"))
    )
    (comp (ref "10V2")
      (value "TPSB2.0")
      (footprint "eagle-import:B2.0")
      (libsource (lib "eagle-import") (part "TPSB2.0"))
    )
    (comp (ref "C21")
      (value "100u")
      (footprint "eagle-import:C1206")
      (fields (field (name "MPN") "GRM31CR60J107ME39L"))
      (libsource (lib "eagle-import") (part "CERAMIC-100UF-6.3V-20%-X5R(1206)"))
    )
    (comp (ref "C22")
      (value "100u")
      (footprint "eagle-import:C1206")
      (fields (field (name "MPN") "GRM31CR60J107ME39L"))
      (libsource (lib "eagle-import") (part "CERAMIC-100UF-6.3V-20%-X5R(1206)"))
    )
    (comp (ref "C23")
      (value "100nF,")
      (footprint "eagle-import:C0805")
      (fields (field (name "MPN") "CC0805KRX7R9BB104"))
      (libsource (lib "eagle-import") (part "CERAMIC-100NF-50V-10%-X7R(0805)"))
    )
    (comp (ref "C24")
      (value "4.7u")
      (footprint "eagle-import:C0805")
      (fields (field (name "MPN") "CC0805KKX5R8BB475"))
      (libsource (lib "eagle-import") (part "CERAMIC-4.7UF-25V-10%-X5R(0805)"))
    )
    (comp (ref "C25")
      (value "100nF.")
      (footprint "eagle-import:C0805")
      (fields (field (name "MPN") "CC0805KRX7R9BB104"))
      (libsource (lib "eagle-import") (part "CERAMIC-100NF-50V-10%-X7R(0805)"))
    )
    (comp (ref "C26")
      (value "100nF.")
      (footprint "eagle-import:C0805")
      (fields (field (name "MPN") "CC0805KRX7R9BB104"))
      (libsource (lib "eagle-import") (part "CERAMIC-100NF-50V-10%-X7R(0805)"))
    )
    (comp (ref "C27")
      (value "2.2nF")
      (footprint "eagle-import:C0805")
      (fields (field (name "MPN") "CC0805KRX7R9BB104"))
      (libsource (lib "eagle-import") (part "CERAMIC-100NF-50V-10%-X7R(0805)"))
    )
    (comp (ref "C28")
      (value "100nF")
      (footprint "eagle-import:C0805")
      (fields (field (name "MPN") "CC0805KRX7R9BB104"))
      (libsource (lib "eagle-import") (part "CERAMIC-100NF-50V-10%-X7R(0805)"))
    )
    (comp (ref "C29")
      (value "100nF")
      (footprint "eagle-import:C0805")
      (fields (field (name "MPN") "CC0805KRX7R9BB104"))
      (libsource (lib "eagle-import") (part "CERAMIC-100NF-50V-10%-X7R(0805)"))
    )
    (comp (ref "C30")
      (value "100nF,")
      (footprint "eagle-import:C0805")
      (fields (field (name "MPN") "CC0805KRX7R9BB104"))
      (libsource (lib "eagle-import") (part "CERAMIC-100NF-50V-10%-X7R(0805)"))
    )
    (comp (ref "D25")
      (value "1N4007")
      (footprint "eagle-import:DO-214AC")
      (libsource (lib "eagle-import") (part "DIODE-GEN-PURPOSE-1KV-1A(DO-214AC)"))
    )
    (comp (ref "D26")
      (value "1N4007,")
      (footprint "eagle-import:DO-214AC")
      (fields (field (name "MPN") "1N4007"))
      (libsource (lib "eagle-import") (part "DIODE-GEN-PURPOSE-1KV-1A(DO-214AC)"))
    )
    (comp (ref "D27")
      (value "1N4007,")
      (footprint "eagle-import:DO-214AC")
      (fields (field (name "MPN") "1N4007"))
      (libsource (lib "eagle-import") (part "DIODE-GEN-PURPOSE-1KV-1A(DO-214AC)"))
    )
    (comp (ref "D28")
      (value "1N4007.")
      (footprint "eagle-import:DO-214AC")
      (fields (field (name "MPN") "1N4007"))
      (libsource (lib "eagle-import") (part "DIODE-GEN-PURPOSE-1KV-1A(DO-214AC)"))
    )
    (comp (ref "D29")
      (value "1N5817")
      (footprint "eagle-import:DO-214AC_SLIM")
      (libsource (lib "eagle-import") (part "DIODE-GEN-PURPOSE-1KV-1A(DO-214AC)DO-214AC/1206"))
    )
    (comp (ref "D30")
      (value "1N5817.")
      (footprint "eagle-import:DO-214AC_SLIM")
      (libsource (lib "eagle-import") (part "DIODE-GEN-PURPOSE-1KV-1A(DO-214AC)DO-214AC/1206"))
    )
    (comp (ref "D31")
      (value "1N5817.")
      (footprint "eagle-import:DO-214AC_SLIM")
      (libsource (lib "eagle-import") (part "DIODE-GEN-PURPOSE-1KV-1A(DO-214AC)DO-214AC/1206"))
    )
    (comp (ref "D32")
      (value "1N5817")
      (footprint "eagle-import:DO-214AC_SLIM")
      (libsource (lib "eagle-import") (part "DIODE-GEN-PURPOSE-1KV-1A(DO-214AC)DO-214AC/1206"))
    )
    (comp (ref "D33")
      (value "1N4007.")
      (footprint "eagle-import:DO-214AC")
      (fields (field (name "MPN") "1N4007"))
      (libsource (lib "eagle-import") (part "DIODE-GEN-PURPOSE-1KV-1A(DO-214AC)"))
    )
    (comp (ref "D34")
      (value "1N4007")
      (footprint "eagle-import:DO-214AC")
      (libsource (lib "eagle-import") (part "DIODE-GEN-PURPOSE-1KV-1A(DO-214AC)"))
    )
    (comp (ref "D35")
      (value "SM6T")
      (footprint "eagle-import:DO214AA")
      (libsource (lib "eagle-import") (part "SM6T"))
    )
    (comp (ref "D36")
      (value "SM6TDO214AA_BI")
      (footprint "eagle-import:DO214AA_BI")
      (libsource (lib "eagle-import") (part "SM6TDO214AA_BI"))
    )
    (comp (ref "FID9")
      (value "FIDUCIAL")
      (footprint "eagle-import:FIDUCIAL_1MM")
      (libsource (lib "eagle-import") (part "FIDUCIAL"))
    )
    (comp (ref "FID10")
      (value "FIDUCIAL")
      (footprint "eagle-import:FIDUCIAL_1MM")
      (libsource (lib "eagle-import") (part "FIDUCIAL"))
    )
    (comp (ref "FID11")
      (value "FIDUCIAL")
      (footprint "eagle-import:FIDUCIAL_1MM")
      (libsource (lib "eagle-import") (part "FIDUCIAL"))
    )
    (comp (ref "FID12")
      (value "FIDUCIAL")
      (footprint "eagle-import:FIDUCIAL_1MM")
      (libsource (lib "eagle-import") (part "FIDUCIAL"))
    )
    (comp (ref "IC23")
      (value "4028")
      (footprint "eagle-import:SO16")
      (libsource (lib "eagle-import") (part "4028D"))
    )
    (comp (ref "IC24")
      (value "6V pos")
      (footprint "eagle-import:78LXX")
      (libsource (lib "eagle-import") (part "v-reg_78LXX"))
    )
    (comp (ref "IC25")
      (value "317TO202H_NOHOLE")
      (footprint "eagle-import:TO220H_NOHOLE")
      (libsource (lib "eagle-import") (part "317TO202H_NOHOLE"))
    )
    (comp (ref "IC26")
      (value "ULN2004")
      (footprint "eagle-import:SO16")
      (libsource (lib "eagle-import") (part "ULN2004AD"))
    )
    (comp (ref "IC27")
      (value "LM339")
      (footprint "eagle-import:SO14")
      (libsource (lib "eagle-import") (part "LM339D"))
    )
    (comp (ref "IC28")
      (value "78L06")
      (footprint "eagle-import:SOT89_ROUND")
      (libsource (lib "eagle-import") (part "78LXXSOT89_ROUND"))
    )
    (comp (ref "IC29")
      (value "555")
      (footprint "eagle-import:SO08")
      (libsource (lib "eagle-import") (part "555DNE"))
    )
    (comp (ref "IC30")
      (value "4538")
      (footprint "eagle-import:SO16")
      (libsource (lib "eagle-import") (part "4538D"))
    )
    (comp (ref "IC31")
      (value "78L10")
      (footprint "eagle-import:SOT89_ROUND")
      (libsource (lib "eagle-import") (part "78LXXSOT89_ROUND"))
    )
    (comp (ref "IC32")
      (value "LM2904")
      (footprint "eagle-import:SO08")
      (libsource (lib "eagle-import") (part "LM358D"))
    )
    (comp (ref "JP11")
      (value "JP2EJP2_SMALLPADS")
      (footprint "eagle-import:JP2_SMALLPADS")
      (libsource (lib "eagle-import") (part "JP2EJP2_SMALLPADS"))
    )
    (comp (ref "JP12")
      (value "JP2E_ORIG")
      (footprint "eagle-import:JP2_ORIG_SMALLPADS")
      (libsource (lib "eagle-import") (part "JP2E_ORIG"))
    )
    (comp (ref "JP13")
      (value "JP2EJP2_SMALLPADS")
      (footprint "eagle-import:JP2_SMALLPADS")
      (libsource (lib "eagle-import") (part "JP2EJP2_SMALLPADS"))
    )
    (comp (ref "JP14")
      (value "JP2EJP2_SMALLPADS")
      (footprint "eagle-import:JP2_SMALLPADS")
      (libsource (lib "eagle-import") (part "JP2EJP2_SMALLPADS"))
    )
    (comp (ref "JP15")
      (value "JP2EJP2_SMALLPADS")
      (footprint "eagle-import:JP2_SMALLPADS")
      (libsource (lib "eagle-import") (part "JP2EJP2_SMALLPADS"))
    )
    (comp (ref "LED13")
      (value "LEDLD260")
      (footprint "eagle-import:LD260")
      (libsource (lib "eagle-import") (part "LEDLD260"))
    )
    (comp (ref "LED14")
      (value "LEDLD260")
      (footprint "eagle-import:LD260")
      (libsource (lib "eagle-import") (part "LEDLD260"))
    )
    (comp (ref "LED15")
      (value "LEDLD260")
      (footprint "eagle-import:LD260")
      (libsource (lib "eagle-import") (part "LEDLD260"))
    )
    (comp (ref "LED16")
      (value "LEDLD260")
      (footprint "eagle-import:LD260")
      (libsource (lib "eagle-import") (part "LEDLD260"))
    )
    (comp (ref "LED17")
      (value "LEDLD260")
      (footprint "eagle-import:LD260")
      (libsource (lib "eagle-import") (part "LEDLD260"))
    )
    (comp (ref "LED18")
      (value "LEDLD260")
      (footprint "eagle-import:LD260")
      (libsource (lib "eagle-import") (part "LEDLD260"))
    )
    (comp (ref "Q15")
      (value "BA")
      (footprint "eagle-import:SOT89")
      (libsource (lib "eagle-import") (part "PNP-TRANSISTOR_SOT89"))
    )
    (comp (ref "Q16")
      (value "BA.")
      (footprint "eagle-import:SOT89")
      (libsource (lib "eagle-import") (part "PNP-TRANSISTOR_SOT89"))
    )
    (comp (ref "Q17")
      (value "BA.")
      (footprint "eagle-import:SOT89")
      (libsource (lib "eagle-import") (part "PNP-TRANSISTOR_SOT89"))
    )
    (comp (ref "Q18")
      (value "BA")
      (footprint "eagle-import:SOT89")
      (libsource (lib "eagle-import") (part "PNP-TRANSISTOR_SOT89"))
    )
    (comp (ref "Q19")
      (value "MY")
      (footprint "eagle-import:SOT89")
      (libsource (lib "eagle-import") (part "NPN-TRANSISTOR_SOT89"))
    )
    (comp (ref "Q20")
      (value "J1")
      (footprint "eagle-import:SOT-23")
      (fields (field (name "MPN") "BSS138W-7-F"))
      (libsource (lib "eagle-import") (part "SMD-MOSFET-N-CH-50V-200MA-BSS138W-7-F(SOT-23)"))
    )
    (comp (ref "Q21")
      (value "J1")
      (footprint "eagle-import:SOT-23")
      (fields (field (name "MPN") "BSS138W-7-F"))
      (libsource (lib "eagle-import") (part "SMD-MOSFET-N-CH-50V-200MA-BSS138W-7-F(SOT-23)"))
    )
    (comp (ref "R93")
      (value "47")
      (footprint "eagle-import:V235_17_1MM")
      (libsource (lib "eagle-import") (part "R-EU_V235/17_1MM"))
    )
    (comp (ref "R94")
      (value "13")
      (footprint "eagle-import:R1206")
      (fields (field (name "MPN") "RC1206JR-0713RL"))
      (libsource (lib "eagle-import") (part "SMD-RES-13R-5%-1/4W(1206)"))
    )
    (comp (ref "R95")
      (value "47")
      (footprint "eagle-import:V235_17_1MM")
      (libsource (lib "eagle-import") (part "R-EU_V235/17_1MM"))
    )
    (comp (ref "R96")
      (value "104")
      (footprint "eagle-import:R0805")
      (fields (field (name "MPN") "RC0805FR-0710KL"))
      (libsource (lib "eagle-import") (part "SMD-RES-10K-1%-1/8W(0805)"))
    )
    (comp (ref "R97")
      (value "104")
      (footprint "eagle-import:R0805")
      (fields (field (name "MPN") "RC0805FR-0710KL"))
      (libsource (lib "eagle-import") (part "SMD-RES-10K-1%-1/8W(0805)"))
    )
    (comp (ref "R98")
      (value "104")
      (footprint "eagle-import:R0805")
      (fields (field (name "MPN") "RC0805FR-0710KL"))
      (libsource (lib "eagle-import") (part "SMD-RES-10K-1%-1/8W(0805)"))
    )
    (comp (ref "R99")
      (value "4701")
      (footprint "eagle-import:R0805")
      (fields (field (name "MPN") "RC0805JR-074K7L"))
      (libsource (lib "eagle-import") (part "SMD-RES-4.7K-5%-1/8W(0805)"))
    )
    (comp (ref "R100")
      (value "1002")
      (footprint "eagle-import:R0805")
      (fields (field (name "MPN") "RC0805FR-0710KL"))
      (libsource (lib "eagle-import") (part "SMD-RES-10K-1%-1/8W(0805)"))
    )
    (comp (ref "R101")
      (value "1002")
      (footprint "eagle-import:R0805")
      (fields (field (name "MPN") "RC0805FR-0710KL"))
      (libsource (lib "eagle-import") (part "SMD-RES-10K-1%-1/8W(0805)"))
    )
    (comp (ref "R102")
      (value "1502")
      (footprint "eagle-import:R0805")
      (fields (field (name "MPN") "RC0805FR-0710KL"))
      (libsource (lib "eagle-import") (part "SMD-RES-10K-1%-1/8W(0805)"))
    )
    (comp (ref "R103")
      (value "104")
      (footprint "eagle-import:R0805")
      (fields (field (name "MPN") "RC0805FR-0710KL"))
      (libsource (lib "eagle-import") (part "SMD-RES-10K-1%-1/8W(0805)"))
    )
    (comp (ref "R104")
      (value "104")
      (footprint "eagle-import:R0805")
      (fields (field (name "MPN") "RC0805FR-0710KL"))
      (libsource (lib "eagle-import") (part "SMD-RES-10K-1%-1/8W(0805)"))
    )
    (comp (ref "R105")
      (value "1502")
      (footprint "eagle-import:R0805")
      (fields (field (name "MPN") "RC0805FR-0710KL"))
      (libsource (lib "eagle-import") (part "SMD-RES-10K-1%-1/8W(0805)"))
    )
    (comp (ref "R106")
      (value "1002")
      (footprint "eagle-import:R0805")
      (fields (field (name "MPN") "RC0805FR-0710KL"))
      (libsource (lib "eagle-import") (part "SMD-RES-10K-1%-1/8W(0805)"))
    )
    (comp (ref "R107")
      (value "2201")
      (footprint "eagle-import:R0805")
      (fields (field (name "MPN") "RC0805JR-072K2L"))
      (libsource (lib "eagle-import") (part "SMD-RES-2.2K-5%-1/8W(0805)"))
    )
    (comp (ref "R108")
      (value "1002")
      (footprint "eagle-import:R0805")
      (fields (field (name "MPN") "RC0805FR-0710KL"))
      (libsource (lib "eagle-import") (part "SMD-RES-10K-1%-1/8W(0805)"))
    )
    (comp (ref "R109")
      (value "4701")
      (footprint "eagle-import:R0805")
      (fields (field (name "MPN") "RC0805JR-074K7L"))
      (libsource (lib "eagle-import") (part "SMD-RES-4.7K-5%-1/8W(0805)"))
    )
    (comp (ref "R110")
      (value "2702")
      (footprint "eagle-import:R0805")
      (fields (field (name "MPN") "RC0805JR-074K7L"))
      (libsource (lib "eagle-import") (part "SMD-RES-4.7K-5%-1/8W(0805)"))
    )
    (comp (ref "R111")
      (value "102")
      (footprint "eagle-import:R0805")
      (fields (field (name "MPN") "RC0805JR-071KL"))
      (libsource (lib "eagle-import") (part "SMD-RES-1K-5%-1/8W(0805)"))
    )
    (comp (ref "R112")
      (value "R_user")
      (footprint "eagle-import:R0805")
      (libsource (lib "eagle-import") (part "R-EU_R0805"))
    )
    (comp (ref "R113")
      (value "100")
      (footprint "eagle-import:R0805")
      (fields (field (name "MPN") "RC0805JR-07220RL"))
      (libsource (lib "eagle-import") (part "SMD-RES-220R-5%-1/8W(0805)"))
    )
    (comp (ref "R114")
      (value "(101)")
      (footprint "eagle-import:R0805")
      (fields (field (name "MPN") "RC0805JR-07100RL"))
      (libsource (lib "eagle-import") (part "SMD-RES-100R-5%-1/8W(0805)"))
    )
    (comp (ref "R115")
      (value "(1000)")
      (footprint "eagle-import:R0805")
      (fields (field (name "MPN") "RC0805JR-07100RL"))
      (libsource (lib "eagle-import") (part "SMD-RES-100R-5%-1/8W(0805)"))
    )
    (comp (ref "R116")
      (value "102")
      (footprint "eagle-import:R0805")
      (fields (field (name "MPN") "RC0805JR-071KL"))
      (libsource (lib "eagle-import") (part "SMD-RES-1K-5%-1/8W(0805)"))
    )
    (comp (ref "R117")
      (value "13")
      (footprint "eagle-import:R1206")
      (fields (field (name "MPN") "RC1206JR-0713RL"))
      (libsource (lib "eagle-import") (part "SMD-RES-13R-5%-1/4W(1206)"))
    )
    (comp (ref "R118")
      (value "13")
      (footprint "eagle-import:R1206")
      (fields (field (name "MPN") "RC1206JR-0713RL"))
      (libsource (lib "eagle-import") (part "SMD-RES-13R-5%-1/4W(1206)"))
    )
    (comp (ref "R119")
      (value "2702")
      (footprint "eagle-import:R0805")
      (fields (field (name "MPN") "RC0805JR-074K7L"))
      (libsource (lib "eagle-import") (part "SMD-RES-4.7K-5%-1/8W(0805)"))
    )
    (comp (ref "R120")
      (value "4701")
      (footprint "eagle-import:R0805")
      (fields (field (name "MPN") "RC0805JR-074K7L"))
      (libsource (lib "eagle-import") (part "SMD-RES-4.7K-5%-1/8W(0805)"))
    )
    (comp (ref "R121")
      (value "100")
      (footprint "eagle-import:R0805")
      (fields (field (name "MPN") "RC0805JR-072K2L"))
      (libsource (lib "eagle-import") (part "SMD-RES-2.2K-5%-1/8W(0805)"))
    )
    (comp (ref "R122")
      (value "(101)")
      (footprint "eagle-import:R0805")
      (fields (field (name "MPN") "RC0805JR-072K2L"))
      (libsource (lib "eagle-import") (part "SMD-RES-2.2K-5%-1/8W(0805)"))
    )
    (comp (ref "R123")
      (value "104")
      (footprint "eagle-import:R0805")
      (fields (field (name "MPN") "RC0805FR-0710KL"))
      (libsource (lib "eagle-import") (part "SMD-RES-10K-1%-1/8W(0805)"))
    )
    (comp (ref "R124")
      (value "104")
      (footprint "eagle-import:R0805")
      (fields (field (name "MPN") "RC0805FR-0710KL"))
      (libsource (lib "eagle-import") (part "SMD-RES-10K-1%-1/8W(0805)"))
    )
    (comp (ref "R125")
      (value "(1002)")
      (footprint "eagle-import:R0805")
      (fields (field (name "MPN") "RC0805FR-0710KL"))
      (libsource (lib "eagle-import") (part "SMD-RES-10K-1%-1/8W(0805)"))
    )
    (comp (ref "R126")
      (value "2702")
      (footprint "eagle-import:R0805")
      (fields (field (name "MPN") "RC0805FR-0710KL"))
      (libsource (lib "eagle-import") (part "SMD-RES-10K-1%-1/8W(0805)"))
    )
    (comp (ref "R127")
      (value "47")
      (footprint "eagle-import:V235_17_1MM")
      (libsource (lib "eagle-import") (part "R-EU_V235/17_1MM"))
    )
    (comp (ref "R128")
      (value "47")
      (footprint "eagle-import:V235_17_1MM")
      (libsource (lib "eagle-import") (part "R-EU_V235/17_1MM"))
    )
    (comp (ref "R129")
      (value "2702")
      (footprint "eagle-import:R0805")
      (fields (field (name "MPN") "RC0805JR-074K7L"))
      (libsource (lib "eagle-import") (part "SMD-RES-4.7K-5%-1/8W(0805)"))
    )
    (comp (ref "R130")
      (value "2201")
      (footprint "eagle-import:R0805")
      (fields (field (name "MPN") "RC0805JR-072K2L"))
      (libsource (lib "eagle-import") (part "SMD-RES-2.2K-5%-1/8W(0805)"))
    )
    (comp (ref "R131")
      (value "(1002)")
      (footprint "eagle-import:R0805")
      (fields (field (name "MPN") "RC0805JR-074K7L"))
      (libsource (lib "eagle-import") (part "SMD-RES-4.7K-5%-1/8W(0805)"))
    )
    (comp (ref "R132")
      (value "1002")
      (footprint "eagle-import:R0805")
      (fields (field (name "MPN") "RC0805FR-0710KL"))
      (libsource (lib "eagle-import") (part "SMD-RES-10K-1%-1/8W(0805)"))
    )
    (comp (ref "R133")
      (value "102")
      (footprint "eagle-import:R0805")
      (fields (field (name "MPN") "RC0805JR-071KL"))
      (libsource (lib "eagle-import") (part "SMD-RES-1K-5%-1/8W(0805)"))
    )
    (comp (ref "R134")
      (value "2702")
      (footprint "eagle-import:R0805")
      (fields (field (name "MPN") "RC0805JR-074K7L"))
      (libsource (lib "eagle-import") (part "SMD-RES-4.7K-5%-1/8W(0805)"))
    )
    (comp (ref "R135")
      (value "102")
      (footprint "eagle-import:R0805")
      (fields (field (name "MPN") "RC0805JR-071KL"))
      (libsource (lib "eagle-import") (part "SMD-RES-1K-5%-1/8W(0805)"))
    )
    (comp (ref "R136")
      (value "102")
      (footprint "eagle-import:R0805")
      (fields (field (name "MPN") "RC0805JR-071KL"))
      (libsource (lib "eagle-import") (part "SMD-RES-1K-5%-1/8W(0805)"))
    )
    (comp (ref "R137")
      (value "13")
      (footprint "eagle-import:R1206")
      (fields (field (name "MPN") "RC1206JR-0713RL"))
      (libsource (lib "eagle-import") (part "SMD-RES-13R-5%-1/4W(1206)"))
    )
    (comp (ref "R138")
      (value "R_user")
      (footprint "eagle-import:R0805")
      (libsource (lib "eagle-import") (part "R-EU_R0805"))
    )
    (comp (ref "SJ3") (value "SJ") (footprint "eagle-import:SJ") (libsource (lib "eagle-import") (part "SJ")))
    (comp (ref "START2")
      (value "TPSB2.0")
      (footprint "eagle-import:B2.0")
      (libsource (lib "eagle-import") (part "TPSB2.0"))
    )
    (comp (ref "TP47")
      (value "TPSB2.0")
      (footprint "eagle-import:B2.0")
      (libsource (lib "eagle-import") (part "TPSB2.0"))
    )
    (comp (ref "TP48")
      (value "TPSB2.0")
      (footprint "eagle-import:B2.0")
      (libsource (lib "eagle-import") (part "TPSB2.0"))
    )
    (comp (ref "TP49")
      (value "TPSB2.0")
      (footprint "eagle-import:B2.0")
      (libsource (lib "eagle-import") (part "TPSB2.0"))
    )
    (comp (ref "TP50")
      (value "TPSB2.0")
      (footprint "eagle-import:B2.0")
      (libsource (lib "eagle-import") (part "TPSB2.0"))
    )
    (comp (ref "TP51")
      (value "TPSB2.0")
      (footprint "eagle-import:B2.0")
      (libsource (lib "eagle-import") (part "TPSB2.0"))
    )
    (comp (ref "TP52")
      (value "TPSB2.0")
      (footprint "eagle-import:B2.0")
      (libsource (lib "eagle-import") (part "TPSB2.0"))
    )
    (comp (ref "TP53")
      (value "TPSB2.0")
      (footprint "eagle-import:B2.0")
      (libsource (lib "eagle-import") (part "TPSB2.0"))
    )
    (comp (ref "TP54")
      (value "TPSB2.0")
      (footprint "eagle-import:B2.0")
      (libsource (lib "eagle-import") (part "TPSB2.0"))
    )
    (comp (ref "TP55")
      (value "TPSB2.0")
      (footprint "eagle-import:B2.0")
      (libsource (lib "eagle-import") (part "TPSB2.0"))
    )
    (comp (ref "TP56")
      (value "TPSB2.0")
      (footprint "eagle-import:B2.0")
      (libsource (lib "eagle-import") (part "TPSB2.0"))
    )
    (comp (ref "TP57")
      (value "TPSB2.0")
      (footprint "eagle-import:B2.0")
      (libsource (lib "eagle-import") (part "TPSB2.0"))
    )
    (comp (ref "TP58")
      (value "TPSB2.0")
      (footprint "eagle-import:B2.0")
      (libsource (lib "eagle-import") (part "TPSB2.0"))
    )
    (comp (ref "TP59")
      (value "TPSB2.0")
      (footprint "eagle-import:B2.0")
      (libsource (lib "eagle-import") (part "TPSB2.0"))
    )
    (comp (ref "TP60")
      (value "TPSB2.0")
      (footprint "eagle-import:B2.0")
      (libsource (lib "eagle-import") (part "TPSB2.0"))
    )
    (comp (ref "TP61")
      (value "TPSB2.0")
      (footprint "eagle-import:B2.0")
      (libsource (lib "eagle-import") (part "TPSB2.0"))
    )
    (comp (ref "TP62")
      (value "TPSB2.0")
      (footprint "eagle-import:B2.0")
      (libsource (lib "eagle-import") (part "TPSB2.0"))
    )
    (comp (ref "TP63")
      (value "TPSB2.0")
      (footprint "eagle-import:B2.0")
      (libsource (lib "eagle-import") (part "TPSB2.0"))
    )
    (comp (ref "TP64")
      (value "TPSB2.0")
      (footprint "eagle-import:B2.0")
      (libsource (lib "eagle-import") (part "TPSB2.0"))
    )
    (comp (ref "TP65")
      (value "TPSB1,27")
      (footprint "eagle-import:B1,27")
      (libsource (lib "eagle-import") (part "TPSB1,27"))
    )
    (comp (ref "TP66")
      (value "TPSB2.0")
      (footprint "eagle-import:B2.0")
      (libsource (lib "eagle-import") (part "TPSB2.0"))
    )
    (comp (ref "TP67")
      (value "TPSB2.0")
      (footprint "eagle-import:B2.0")
      (libsource (lib "eagle-import") (part "TPSB2.0"))
    )
    (comp (ref "TP68")
      (value "TPSB2.0")
      (footprint "eagle-import:B2.0")
      (libsource (lib "eagle-import") (part "TPSB2.0"))
    )
    (comp (ref "TP69")
      (value "TPSB2.0")
      (footprint "eagle-import:B2.0")
      (libsource (lib "eagle-import") (part "TPSB2.0"))
    )
    (comp (ref "X7")
      (value "CON_BMWV2")
      (footprint "eagle-import:24-PIN_V2")
      (libsource (lib "eagle-import") (part "CON_BMWV2"))
    )
    (comp (ref "X8")
      (value "22-23-2051")
      (footprint "eagle-import:22-23-2051")
      (fields (field (name "MF") "MOLEX"))
      (libsource (lib "eagle-import") (part "22-23-2051"))
    )
    (comp (ref "X9")
      (value "22-23-2021")
      (footprint "eagle-import:22-23-2021")
      (fields (field (name "MF") "MOLEX"))
      (libsource (lib "eagle-import") (part "22-23-2021"))
    )
    (comp (ref "6V11")
      (value "TPSB2.0")
      (footprint "eagle-import:B2.0")
      (libsource (lib "eagle-import") (part "TPSB2.0"))
    )
    (comp (ref "10V11")
      (value "TPSB2.0")
      (footprint "eagle-import:B2.0")
      (libsource (lib "eagle-import") (part "TPSB2.0"))
    )
    (comp (ref "23")
      (value "2081-1132")
      (footprint "eagle-import:12-PIN")
      (libsource (lib "eagle-import") (part "2081-1132"))
    )
    (comp (ref "24")
      (value "2081-1132")
      (footprint "eagle-import:12-PIN")
      (libsource (lib "eagle-import") (part "2081-1132"))
    )
    (comp (ref "C111")
      (value "100u")
      (footprint "eagle-import:C1206")
      (fields (field (name "MPN") "GRM31CR60J107ME39L"))
      (libsource (lib "eagle-import") (part "CERAMIC-100UF-6.3V-20%-X5R(1206)"))
    )
    (comp (ref "C112")
      (value "100u")
      (footprint "eagle-import:C1206")
      (fields (field (name "MPN") "GRM31CR60J107ME39L"))
      (libsource (lib "eagle-import") (part "CERAMIC-100UF-6.3V-20%-X5R(1206)"))
    )
    (comp (ref "C113")
      (value "100nF,")
      (footprint "eagle-import:C0805")
      (fields (field (name "MPN") "CC0805KRX7R9BB104"))
      (libsource (lib "eagle-import") (part "CERAMIC-100NF-50V-10%-X7R(0805)"))
    )
    (comp (ref "C114")
      (value "4.7u")
      (footprint "eagle-import:C0805")
      (fields (field (name "MPN") "CC0805KKX5R8BB475"))
      (libsource (lib "eagle-import") (part "CERAMIC-4.7UF-25V-10%-X5R(0805)"))
    )
    (comp (ref "C115")
      (value "100nF.")
      (footprint "eagle-import:C0805")
      (fields (field (name "MPN") "CC0805KRX7R9BB104"))
      (libsource (lib "eagle-import") (part "CERAMIC-100NF-50V-10%-X7R(0805)"))
    )
    (comp (ref "C116")
      (value "100nF.")
      (footprint "eagle-import:C0805")
      (fields (field (name "MPN") "CC0805KRX7R9BB104"))
      (libsource (lib "eagle-import") (part "CERAMIC-100NF-50V-10%-X7R(0805)"))
    )
    (comp (ref "C117")
      (value "2.2nF")
      (footprint "eagle-import:C0805")
      (fields (field (name "MPN") "CC0805KRX7R9BB104"))
      (libsource (lib "eagle-import") (part "CERAMIC-100NF-50V-10%-X7R(0805)"))
    )
    (comp (ref "C118")
      (value "100nF")
      (footprint "eagle-import:C0805")
      (fields (field (name "MPN") "CC0805KRX7R9BB104"))
      (libsource (lib "eagle-import") (part "CERAMIC-100NF-50V-10%-X7R(0805)"))
    )
    (comp (ref "C119")
      (value "100nF")
      (footprint "eagle-import:C0805")
      (fields (field (name "MPN") "CC0805KRX7R9BB104"))
      (libsource (lib "eagle-import") (part "CERAMIC-100NF-50V-10%-X7R(0805)"))
    )
    (comp (ref "C120")
      (value "100nF,")
      (footprint "eagle-import:C0805")
      (fields (field (name "MPN") "CC0805KRX7R9BB104"))
      (libsource (lib "eagle-import") (part "CERAMIC-100NF-50V-10%-X7R(0805)"))
    )
    (comp (ref "D133")
      (value "1N4007")
      (footprint "eagle-import:DO-214AC")
      (libsource (lib "eagle-import") (part "DIODE-GEN-PURPOSE-1KV-1A(DO-214AC)"))
    )
    (comp (ref "D134")
      (value "1N4007,")
      (footprint "eagle-import:DO-214AC")
      (fields (field (name "MPN") "1N4007"))
      (libsource (lib "eagle-import") (part "DIODE-GEN-PURPOSE-1KV-1A(DO-214AC)"))
    )
    (comp (ref "D135")
      (value "1N4007,")
      (footprint "eagle-import:DO-214AC")
      (fields (field (name "MPN") "1N4007"))
      (libsource (lib "eagle-import") (part "DIODE-GEN-PURPOSE-1KV-1A(DO-214AC)"))
    )
    (comp (ref "D136")
      (value "1N4007.")
      (footprint "eagle-import:DO-214AC")
      (fields (field (name "MPN") "1N4007"))
      (libsource (lib "eagle-import") (part "DIODE-GEN-PURPOSE-1KV-1A(DO-214AC)"))
    )
    (comp (ref "D137")
      (value "1N5817")
      (footprint "eagle-import:DO-214AC_SLIM")
      (libsource (lib "eagle-import") (part "DIODE-GEN-PURPOSE-1KV-1A(DO-214AC)DO-214AC/1206"))
    )
    (comp (ref "D138")
      (value "1N5817.")
      (footprint "eagle-import:DO-214AC_SLIM")
      (libsource (lib "eagle-import") (part "DIODE-GEN-PURPOSE-1KV-1A(DO-214AC)DO-214AC/1206"))
    )
    (comp (ref "D139")
      (value "1N5817.")
      (footprint "eagle-import:DO-214AC_SLIM")
      (libsource (lib "eagle-import") (part "DIODE-GEN-PURPOSE-1KV-1A(DO-214AC)DO-214AC/1206"))
    )
    (comp (ref "D140")
      (value "1N5817")
      (footprint "eagle-import:DO-214AC_SLIM")
      (libsource (lib "eagle-import") (part "DIODE-GEN-PURPOSE-1KV-1A(DO-214AC)DO-214AC/1206"))
    )
    (comp (ref "D141")
      (value "1N4007.")
      (footprint "eagle-import:DO-214AC")
      (fields (field (name "MPN") "1N4007"))
      (libsource (lib "eagle-import") (part "DIODE-GEN-PURPOSE-1KV-1A(DO-214AC)"))
    )
    (comp (ref "D142")
      (value "1N4007")
      (footprint "eagle-import:DO-214AC")
      (libsource (lib "eagle-import") (part "DIODE-GEN-PURPOSE-1KV-1A(DO-214AC)"))
    )
    (comp (ref "D143")
      (value "SM6T")
      (footprint "eagle-import:DO214AA")
      (libsource (lib "eagle-import") (part "SM6T"))
    )
    (comp (ref "D144")
      (value "SM6TDO214AA_BI")
      (footprint "eagle-import:DO214AA_BI")
      (libsource (lib "eagle-import") (part "SM6TDO214AA_BI"))
    )
    (comp (ref "FID45")
      (value "FIDUCIAL")
      (footprint "eagle-import:FIDUCIAL_1MM")
      (libsource (lib "eagle-import") (part "FIDUCIAL"))
    )
    (comp (ref "FID46")
      (value "FIDUCIAL")
      (footprint "eagle-import:FIDUCIAL_1MM")
      (libsource (lib "eagle-import") (part "FIDUCIAL"))
    )
    (comp (ref "FID47")
      (value "FIDUCIAL")
      (footprint "eagle-import:FIDUCIAL_1MM")
      (libsource (lib "eagle-import") (part "FIDUCIAL"))
    )
    (comp (ref "FID48")
      (value "FIDUCIAL")
      (footprint "eagle-import:FIDUCIAL_1MM")
      (libsource (lib "eagle-import") (part "FIDUCIAL"))
    )
    (comp (ref "IC122")
      (value "4028")
      (footprint "eagle-import:SO16")
      (libsource (lib "eagle-import") (part "4028D"))
    )
    (comp (ref "IC123")
      (value "6V pos")
      (footprint "eagle-import:78LXX")
      (libsource (lib "eagle-import") (part "v-reg_78LXX"))
    )
    (comp (ref "IC124")
      (value "317TO202H_NOHOLE")
      (footprint "eagle-import:TO220H_NOHOLE")
      (libsource (lib "eagle-import") (part "317TO202H_NOHOLE"))
    )
    (comp (ref "IC125")
      (value "ULN2004")
      (footprint "eagle-import:SO16")
      (libsource (lib "eagle-import") (part "ULN2004AD"))
    )
    (comp (ref "IC126")
      (value "LM339")
      (footprint "eagle-import:SO14")
      (libsource (lib "eagle-import") (part "LM339D"))
    )
    (comp (ref "IC127")
      (value "78L06")
      (footprint "eagle-import:SOT89_ROUND")
      (libsource (lib "eagle-import") (part "78LXXSOT89_ROUND"))
    )
    (comp (ref "IC128")
      (value "555")
      (footprint "eagle-import:SO08")
      (libsource (lib "eagle-import") (part "555DNE"))
    )
    (comp (ref "IC129")
      (value "4538")
      (footprint "eagle-import:SO16")
      (libsource (lib "eagle-import") (part "4538D"))
    )
    (comp (ref "IC130")
      (value "78L10")
      (footprint "eagle-import:SOT89_ROUND")
      (libsource (lib "eagle-import") (part "78LXXSOT89_ROUND"))
    )
    (comp (ref "IC131")
      (value "LM2904")
      (footprint "eagle-import:SO08")
      (libsource (lib "eagle-import") (part "LM358D"))
    )
    (comp (ref "JP56")
      (value "JP2EJP2_SMALLPADS")
      (footprint "eagle-import:JP2_SMALLPADS")
      (libsource (lib "eagle-import") (part "JP2EJP2_SMALLPADS"))
    )
    (comp (ref "JP57")
      (value "JP2E_ORIG")
      (footprint "eagle-import:JP2_ORIG_SMALLPADS")
      (libsource (lib "eagle-import") (part "JP2E_ORIG"))
    )
    (comp (ref "JP58")
      (value "JP2EJP2_SMALLPADS")
      (footprint "eagle-import:JP2_SMALLPADS")
      (libsource (lib "eagle-import") (part "JP2EJP2_SMALLPADS"))
    )
    (comp (ref "JP59")
      (value "JP2EJP2_SMALLPADS")
      (footprint "eagle-import:JP2_SMALLPADS")
      (libsource (lib "eagle-import") (part "JP2EJP2_SMALLPADS"))
    )
    (comp (ref "JP60")
      (value "JP2EJP2_SMALLPADS")
      (footprint "eagle-import:JP2_SMALLPADS")
      (libsource (lib "eagle-import") (part "JP2EJP2_SMALLPADS"))
    )
    (comp (ref "LED67")
      (value "LEDLD260")
      (footprint "eagle-import:LD260")
      (libsource (lib "eagle-import") (part "LEDLD260"))
    )
    (comp (ref "LED68")
      (value "LEDLD260")
      (footprint "eagle-import:LD260")
      (libsource (lib "eagle-import") (part "LEDLD260"))
    )
    (comp (ref "LED69")
      (value "LEDLD260")
      (footprint "eagle-import:LD260")
      (libsource (lib "eagle-import") (part "LEDLD260"))
    )
    (comp (ref "LED70")
      (value "LEDLD260")
      (footprint "eagle-import:LD260")
      (libsource (lib "eagle-import") (part "LEDLD260"))
    )
    (comp (ref "LED71")
      (value "LEDLD260")
      (footprint "eagle-import:LD260")
      (libsource (lib "eagle-import") (part "LEDLD260"))
    )
    (comp (ref "LED72")
      (value "LEDLD260")
      (footprint "eagle-import:LD260")
      (libsource (lib "eagle-import") (part "LEDLD260"))
    )
    (comp (ref "Q78")
      (value "BA")
      (footprint "eagle-import:SOT89")
      (libsource (lib "eagle-import") (part "PNP-TRANSISTOR_SOT89"))
    )
    (comp (ref "Q79")
      (value "BA.")
      (footprint "eagle-import:SOT89")
      (libsource (lib "eagle-import") (part "PNP-TRANSISTOR_SOT89"))
    )
    (comp (ref "Q80")
      (value "BA.")
      (footprint "eagle-import:SOT89")
      (libsource (lib "eagle-import") (part "PNP-TRANSISTOR_SOT89"))
    )
    (comp (ref "Q81")
      (value "BA")
      (footprint "eagle-import:SOT89")
      (libsource (lib "eagle-import") (part "PNP-TRANSISTOR_SOT89"))
    )
    (comp (ref "Q82")
      (value "MY")
      (footprint "eagle-import:SOT89")
      (libsource (lib "eagle-import") (part "NPN-TRANSISTOR_SOT89"))
    )
    (comp (ref "Q83")
      (value "J1")
      (footprint "eagle-import:SOT-23")
      (fields (field (name "MPN") "BSS138W-7-F"))
      (libsource (lib "eagle-import") (part "SMD-MOSFET-N-CH-50V-200MA-BSS138W-7-F(SOT-23)"))
    )
    (comp (ref "Q84")
      (value "J1")
      (footprint "eagle-import:SOT-23")
      (fields (field (name "MPN") "BSS138W-7-F"))
      (libsource (lib "eagle-import") (part "SMD-MOSFET-N-CH-50V-200MA-BSS138W-7-F(SOT-23)"))
    )
    (comp (ref "R507")
      (value "47")
      (footprint "eagle-import:V235_17_1MM")
      (libsource (lib "eagle-import") (part "R-EU_V235/17_1MM"))
    )
    (comp (ref "R508")
      (value "13")
      (footprint "eagle-import:R1206")
      (fields (field (name "MPN") "RC1206JR-0713RL"))
      (libsource (lib "eagle-import") (part "SMD-RES-13R-5%-1/4W(1206)"))
    )
    (comp (ref "R509")
      (value "47")
      (footprint "eagle-import:V235_17_1MM")
      (libsource (lib "eagle-import") (part "R-EU_V235/17_1MM"))
    )
    (comp (ref "R510")
      (value "104")
      (footprint "eagle-import:R0805")
      (fields (field (name "MPN") "RC0805FR-0710KL"))
      (libsource (lib "eagle-import") (part "SMD-RES-10K-1%-1/8W(0805)"))
    )
    (comp (ref "R511")
      (value "104")
      (footprint "eagle-import:R0805")
      (fields (field (name "MPN") "RC0805FR-0710KL"))
      (libsource (lib "eagle-import") (part "SMD-RES-10K-1%-1/8W(0805)"))
    )
    (comp (ref "R512")
      (value "104")
      (footprint "eagle-import:R0805")
      (fields (field (name "MPN") "RC0805FR-0710KL"))
      (libsource (lib "eagle-import") (part "SMD-RES-10K-1%-1/8W(0805)"))
    )
    (comp (ref "R513")
      (value "4701")
      (footprint "eagle-import:R0805")
      (fields (field (name "MPN") "RC0805JR-074K7L"))
      (libsource (lib "eagle-import") (part "SMD-RES-4.7K-5%-1/8W(0805)"))
    )
    (comp (ref "R514")
      (value "1002")
      (footprint "eagle-import:R0805")
      (fields (field (name "MPN") "RC0805FR-0710KL"))
      (libsource (lib "eagle-import") (part "SMD-RES-10K-1%-1/8W(0805)"))
    )
    (comp (ref "R515")
      (value "1002")
      (footprint "eagle-import:R0805")
      (fields (field (name "MPN") "RC0805FR-0710KL"))
      (libsource (lib "eagle-import") (part "SMD-RES-10K-1%-1/8W(0805)"))
    )
    (comp (ref "R516")
      (value "1502")
      (footprint "eagle-import:R0805")
      (fields (field (name "MPN") "RC0805FR-0710KL"))
      (libsource (lib "eagle-import") (part "SMD-RES-10K-1%-1/8W(0805)"))
    )
    (comp (ref "R517")
      (value "104")
      (footprint "eagle-import:R0805")
      (fields (field (name "MPN") "RC0805FR-0710KL"))
      (libsource (lib "eagle-import") (part "SMD-RES-10K-1%-1/8W(0805)"))
    )
    (comp (ref "R518")
      (value "104")
      (footprint "eagle-import:R0805")
      (fields (field (name "MPN") "RC0805FR-0710KL"))
      (libsource (lib "eagle-import") (part "SMD-RES-10K-1%-1/8W(0805)"))
    )
    (comp (ref "R519")
      (value "1502")
      (footprint "eagle-import:R0805")
      (fields (field (name "MPN") "RC0805FR-0710KL"))
      (libsource (lib "eagle-import") (part "SMD-RES-10K-1%-1/8W(0805)"))
    )
    (comp (ref "R520")
      (value "1002")
      (footprint "eagle-import:R0805")
      (fields (field (name "MPN") "RC0805FR-0710KL"))
      (libsource (lib "eagle-import") (part "SMD-RES-10K-1%-1/8W(0805)"))
    )
    (comp (ref "R521")
      (value "2201")
      (footprint "eagle-import:R0805")
      (fields (field (name "MPN") "RC0805JR-072K2L"))
      (libsource (lib "eagle-import") (part "SMD-RES-2.2K-5%-1/8W(0805)"))
    )
    (comp (ref "R522")
      (value "1002")
      (footprint "eagle-import:R0805")
      (fields (field (name "MPN") "RC0805FR-0710KL"))
      (libsource (lib "eagle-import") (part "SMD-RES-10K-1%-1/8W(0805)"))
    )
    (comp (ref "R523")
      (value "4701")
      (footprint "eagle-import:R0805")
      (fields (field (name "MPN") "RC0805JR-074K7L"))
      (libsource (lib "eagle-import") (part "SMD-RES-4.7K-5%-1/8W(0805)"))
    )
    (comp (ref "R524")
      (value "2702")
      (footprint "eagle-import:R0805")
      (fields (field (name "MPN") "RC0805JR-074K7L"))
      (libsource (lib "eagle-import") (part "SMD-RES-4.7K-5%-1/8W(0805)"))
    )
    (comp (ref "R525")
      (value "102")
      (footprint "eagle-import:R0805")
      (fields (field (name "MPN") "RC0805JR-071KL"))
      (libsource (lib "eagle-import") (part "SMD-RES-1K-5%-1/8W(0805)"))
    )
    (comp (ref "R526")
      (value "R_user")
      (footprint "eagle-import:R0805")
      (libsource (lib "eagle-import") (part "R-EU_R0805"))
    )
    (comp (ref "R527")
      (value "100")
      (footprint "eagle-import:R0805")
      (fields (field (name "MPN") "RC0805JR-07220RL"))
      (libsource (lib "eagle-import") (part "SMD-RES-220R-5%-1/8W(0805)"))
    )
    (comp (ref "R528")
      (value "(101)")
      (footprint "eagle-import:R0805")
      (fields (field (name "MPN") "RC0805JR-07100RL"))
      (libsource (lib "eagle-import") (part "SMD-RES-100R-5%-1/8W(0805)"))
    )
    (comp (ref "R529")
      (value "(1000)")
      (footprint "eagle-import:R0805")
      (fields (field (name "MPN") "RC0805JR-07100RL"))
      (libsource (lib "eagle-import") (part "SMD-RES-100R-5%-1/8W(0805)"))
    )
    (comp (ref "R530")
      (value "102")
      (footprint "eagle-import:R0805")
      (fields (field (name "MPN") "RC0805JR-071KL"))
      (libsource (lib "eagle-import") (part "SMD-RES-1K-5%-1/8W(0805)"))
    )
    (comp (ref "R531")
      (value "13")
      (footprint "eagle-import:R1206")
      (fields (field (name "MPN") "RC1206JR-0713RL"))
      (libsource (lib "eagle-import") (part "SMD-RES-13R-5%-1/4W(1206)"))
    )
    (comp (ref "R532")
      (value "13")
      (footprint "eagle-import:R1206")
      (fields (field (name "MPN") "RC1206JR-0713RL"))
      (libsource (lib "eagle-import") (part "SMD-RES-13R-5%-1/4W(1206)"))
    )
    (comp (ref "R533")
      (value "2702")
      (footprint "eagle-import:R0805")
      (fields (field (name "MPN") "RC0805JR-074K7L"))
      (libsource (lib "eagle-import") (part "SMD-RES-4.7K-5%-1/8W(0805)"))
    )
    (comp (ref "R534")
      (value "4701")
      (footprint "eagle-import:R0805")
      (fields (field (name "MPN") "RC0805JR-074K7L"))
      (libsource (lib "eagle-import") (part "SMD-RES-4.7K-5%-1/8W(0805)"))
    )
    (comp (ref "R535")
      (value "100")
      (footprint "eagle-import:R0805")
      (fields (field (name "MPN") "RC0805JR-072K2L"))
      (libsource (lib "eagle-import") (part "SMD-RES-2.2K-5%-1/8W(0805)"))
    )
    (comp (ref "R536")
      (value "(101)")
      (footprint "eagle-import:R0805")
      (fields (field (name "MPN") "RC0805JR-072K2L"))
      (libsource (lib "eagle-import") (part "SMD-RES-2.2K-5%-1/8W(0805)"))
    )
    (comp (ref "R537")
      (value "104")
      (footprint "eagle-import:R0805")
      (fields (field (name "MPN") "RC0805FR-0710KL"))
      (libsource (lib "eagle-import") (part "SMD-RES-10K-1%-1/8W(0805)"))
    )
    (comp (ref "R538")
      (value "104")
      (footprint "eagle-import:R0805")
      (fields (field (name "MPN") "RC0805FR-0710KL"))
      (libsource (lib "eagle-import") (part "SMD-RES-10K-1%-1/8W(0805)"))
    )
    (comp (ref "R539")
      (value "(1002)")
      (footprint "eagle-import:R0805")
      (fields (field (name "MPN") "RC0805FR-0710KL"))
      (libsource (lib "eagle-import") (part "SMD-RES-10K-1%-1/8W(0805)"))
    )
    (comp (ref "R540")
      (value "2702")
      (footprint "eagle-import:R0805")
      (fields (field (name "MPN") "RC0805FR-0710KL"))
      (libsource (lib "eagle-import") (part "SMD-RES-10K-1%-1/8W(0805)"))
    )
    (comp (ref "R541")
      (value "47")
      (footprint "eagle-import:V235_17_1MM")
      (libsource (lib "eagle-import") (part "R-EU_V235/17_1MM"))
    )
    (comp (ref "R542")
      (value "47")
      (footprint "eagle-import:V235_17_1MM")
      (libsource (lib "eagle-import") (part "R-EU_V235/17_1MM"))
    )
    (comp (ref "R543")
      (value "2702")
      (footprint "eagle-import:R0805")
      (fields (field (name "MPN") "RC0805JR-074K7L"))
      (libsource (lib "eagle-import") (part "SMD-RES-4.7K-5%-1/8W(0805)"))
    )
    (comp (ref "R544")
      (value "2201")
      (footprint "eagle-import:R0805")
      (fields (field (name "MPN") "RC0805JR-072K2L"))
      (libsource (lib "eagle-import") (part "SMD-RES-2.2K-5%-1/8W(0805)"))
    )
    (comp (ref "R545")
      (value "(1002)")
      (footprint "eagle-import:R0805")
      (fields (field (name "MPN") "RC0805JR-074K7L"))
      (libsource (lib "eagle-import") (part "SMD-RES-4.7K-5%-1/8W(0805)"))
    )
    (comp (ref "R546")
      (value "1002")
      (footprint "eagle-import:R0805")
      (fields (field (name "MPN") "RC0805FR-0710KL"))
      (libsource (lib "eagle-import") (part "SMD-RES-10K-1%-1/8W(0805)"))
    )
    (comp (ref "R547")
      (value "102")
      (footprint "eagle-import:R0805")
      (fields (field (name "MPN") "RC0805JR-071KL"))
      (libsource (lib "eagle-import") (part "SMD-RES-1K-5%-1/8W(0805)"))
    )
    (comp (ref "R548")
      (value "2702")
      (footprint "eagle-import:R0805")
      (fields (field (name "MPN") "RC0805JR-074K7L"))
      (libsource (lib "eagle-import") (part "SMD-RES-4.7K-5%-1/8W(0805)"))
    )
    (comp (ref "R549")
      (value "102")
      (footprint "eagle-import:R0805")
      (fields (field (name "MPN") "RC0805JR-071KL"))
      (libsource (lib "eagle-import") (part "SMD-RES-1K-5%-1/8W(0805)"))
    )
    (comp (ref "R550")
      (value "102")
      (footprint "eagle-import:R0805")
      (fields (field (name "MPN") "RC0805JR-071KL"))
      (libsource (lib "eagle-import") (part "SMD-RES-1K-5%-1/8W(0805)"))
    )
    (comp (ref "R551")
      (value "13")
      (footprint "eagle-import:R1206")
      (fields (field (name "MPN") "RC1206JR-0713RL"))
      (libsource (lib "eagle-import") (part "SMD-RES-13R-5%-1/4W(1206)"))
    )
    (comp (ref "R552")
      (value "R_user")
      (footprint "eagle-import:R0805")
      (libsource (lib "eagle-import") (part "R-EU_R0805"))
    )
    (comp (ref "SJ12")
      (value "SJ")
      (footprint "eagle-import:SJ")
      (libsource (lib "eagle-import") (part "SJ"))
    )
    (comp (ref "START11")
      (value "TPSB2.0")
      (footprint "eagle-import:B2.0")
      (libsource (lib "eagle-import") (part "TPSB2.0"))
    )
    (comp (ref "TP254")
      (value "TPSB2.0")
      (footprint "eagle-import:B2.0")
      (libsource (lib "eagle-import") (part "TPSB2.0"))
    )
    (comp (ref "TP255")
      (value "TPSB2.0")
      (footprint "eagle-import:B2.0")
      (libsource (lib "eagle-import") (part "TPSB2.0"))
    )
    (comp (ref "TP256")
      (value "TPSB2.0")
      (footprint "eagle-import:B2.0")
      (libsource (lib "eagle-import") (part "TPSB2.0"))
    )
    (comp (ref "TP257")
      (value "TPSB2.0")
      (footprint "eagle-import:B2.0")
      (libsource (lib "eagle-import") (part "TPSB2.0"))
    )
    (comp (ref "TP258")
      (value "TPSB2.0")
      (footprint "eagle-import:B2.0")
      (libsource (lib "eagle-import") (part "TPSB2.0"))
    )
    (comp (ref "TP259")
      (value "TPSB2.0")
      (footprint "eagle-import:B2.0")
      (libsource (lib "eagle-import") (part "TPSB2.0"))
    )
    (comp (ref "TP260")
      (value "TPSB2.0")
      (footprint "eagle-import:B2.0")
      (libsource (lib "eagle-import") (part "TPSB2.0"))
    )
    (comp (ref "TP261")
      (value "TPSB2.0")
      (footprint "eagle-import:B2.0")
      (libsource (lib "eagle-import") (part "TPSB2.0"))
    )
    (comp (ref "TP262")
      (value "TPSB2.0")
      (footprint "eagle-import:B2.0")
      (libsource (lib "eagle-import") (part "TPSB2.0"))
    )
    (comp (ref "TP263")
      (value "TPSB2.0")
      (footprint "eagle-import:B2.0")
      (libsource (lib "eagle-import") (part "TPSB2.0"))
    )
    (comp (ref "TP264")
      (value "TPSB2.0")
      (footprint "eagle-import:B2.0")
      (libsource (lib "eagle-import") (part "TPSB2.0"))
    )
    (comp (ref "TP265")
      (value "TPSB2.0")
      (footprint "eagle-import:B2.0")
      (libsource (lib "eagle-import") (part "TPSB2.0"))
    )
    (comp (ref "TP266")
      (value "TPSB2.0")
      (footprint "eagle-import:B2.0")
      (libsource (lib "eagle-import") (part "TPSB2.0"))
    )
    (comp (ref "TP267")
      (value "TPSB2.0")
      (footprint "eagle-import:B2.0")
      (libsource (lib "eagle-import") (part "TPSB2.0"))
    )
    (comp (ref "TP268")
      (value "TPSB2.0")
      (footprint "eagle-import:B2.0")
      (libsource (lib "eagle-import") (part "TPSB2.0"))
    )
    (comp (ref "TP269")
      (value "TPSB2.0")
      (footprint "eagle-import:B2.0")
      (libsource (lib "eagle-import") (part "TPSB2.0"))
    )
    (comp (ref "TP270")
      (value "TPSB2.0")
      (footprint "eagle-import:B2.0")
      (libsource (lib "eagle-import") (part "TPSB2.0"))
    )
    (comp (ref "TP271")
      (value "TPSB2.0")
      (footprint "eagle-import:B2.0")
      (libsource (lib "eagle-import") (part "TPSB2.0"))
    )
    (comp (ref "TP272")
      (value "TPSB1,27")
      (footprint "eagle-import:B1,27")
      (libsource (lib "eagle-import") (part "TPSB1,27"))
    )
    (comp (ref "TP273")
      (value "TPSB2.0")
      (footprint "eagle-import:B2.0")
      (libsource (lib "eagle-import") (part "TPSB2.0"))
    )
    (comp (ref "TP274")
      (value "TPSB2.0")
      (footprint "eagle-import:B2.0")
      (libsource (lib "eagle-import") (part "TPSB2.0"))
    )
    (comp (ref "TP275")
      (value "TPSB2.0")
      (footprint "eagle-import:B2.0")
      (libsource (lib "eagle-import") (part "TPSB2.0"))
    )
    (comp (ref "TP276")
      (value "TPSB2.0")
      (footprint "eagle-import:B2.0")
      (libsource (lib "eagle-import") (part "TPSB2.0"))
    )
    (comp (ref "X34")
      (value "CON_BMWV2")
      (footprint "eagle-import:24-PIN_V2")
      (libsource (lib "eagle-import") (part "CON_BMWV2"))
    )
    (comp (ref "X35")
      (value "22-23-2051")
      (footprint "eagle-import:22-23-2051")
      (fields (field (name "MF") "MOLEX"))
      (libsource (lib "eagle-import") (part "22-23-2051"))
    )
    (comp (ref "X36")
      (value "22-23-2021")
      (footprint "eagle-import:22-23-2021")
      (fields (field (name "MF") "MOLEX"))
      (libsource (lib "eagle-import") (part "22-23-2021"))
    )
    (comp (ref "6V7")
      (value "TPSB2.0")
      (footprint "eagle-import:B2.0")
      (libsource (lib "eagle-import") (part "TPSB2.0"))
    )
    (comp (ref "10V7")
      (value "TPSB2.0")
      (footprint "eagle-import:B2.0")
      (libsource (lib "eagle-import") (part "TPSB2.0"))
    )
    (comp (ref "15")
      (value "2081-1132")
      (footprint "eagle-import:12-PIN")
      (libsource (lib "eagle-import") (part "2081-1132"))
    )
    (comp (ref "16")
      (value "2081-1132")
      (footprint "eagle-import:12-PIN")
      (libsource (lib "eagle-import") (part "2081-1132"))
    )
    (comp (ref "C71")
      (value "100u")
      (footprint "eagle-import:C1206")
      (fields (field (name "MPN") "GRM31CR60J107ME39L"))
      (libsource (lib "eagle-import") (part "CERAMIC-100UF-6.3V-20%-X5R(1206)"))
    )
    (comp (ref "C72")
      (value "100u")
      (footprint "eagle-import:C1206")
      (fields (field (name "MPN") "GRM31CR60J107ME39L"))
      (libsource (lib "eagle-import") (part "CERAMIC-100UF-6.3V-20%-X5R(1206)"))
    )
    (comp (ref "C73")
      (value "100nF,")
      (footprint "eagle-import:C0805")
      (fields (field (name "MPN") "CC0805KRX7R9BB104"))
      (libsource (lib "eagle-import") (part "CERAMIC-100NF-50V-10%-X7R(0805)"))
    )
    (comp (ref "C74")
      (value "4.7u")
      (footprint "eagle-import:C0805")
      (fields (field (name "MPN") "CC0805KKX5R8BB475"))
      (libsource (lib "eagle-import") (part "CERAMIC-4.7UF-25V-10%-X5R(0805)"))
    )
    (comp (ref "C75")
      (value "100nF.")
      (footprint "eagle-import:C0805")
      (fields (field (name "MPN") "CC0805KRX7R9BB104"))
      (libsource (lib "eagle-import") (part "CERAMIC-100NF-50V-10%-X7R(0805)"))
    )
    (comp (ref "C76")
      (value "100nF.")
      (footprint "eagle-import:C0805")
      (fields (field (name "MPN") "CC0805KRX7R9BB104"))
      (libsource (lib "eagle-import") (part "CERAMIC-100NF-50V-10%-X7R(0805)"))
    )
    (comp (ref "C77")
      (value "2.2nF")
      (footprint "eagle-import:C0805")
      (fields (field (name "MPN") "CC0805KRX7R9BB104"))
      (libsource (lib "eagle-import") (part "CERAMIC-100NF-50V-10%-X7R(0805)"))
    )
    (comp (ref "C78")
      (value "100nF")
      (footprint "eagle-import:C0805")
      (fields (field (name "MPN") "CC0805KRX7R9BB104"))
      (libsource (lib "eagle-import") (part "CERAMIC-100NF-50V-10%-X7R(0805)"))
    )
    (comp (ref "C79")
      (value "100nF")
      (footprint "eagle-import:C0805")
      (fields (field (name "MPN") "CC0805KRX7R9BB104"))
      (libsource (lib "eagle-import") (part "CERAMIC-100NF-50V-10%-X7R(0805)"))
    )
    (comp (ref "C80")
      (value "100nF,")
      (footprint "eagle-import:C0805")
      (fields (field (name "MPN") "CC0805KRX7R9BB104"))
      (libsource (lib "eagle-import") (part "CERAMIC-100NF-50V-10%-X7R(0805)"))
    )
    (comp (ref "D85")
      (value "1N4007")
      (footprint "eagle-import:DO-214AC")
      (libsource (lib "eagle-import") (part "DIODE-GEN-PURPOSE-1KV-1A(DO-214AC)"))
    )
    (comp (ref "D86")
      (value "1N4007,")
      (footprint "eagle-import:DO-214AC")
      (fields (field (name "MPN") "1N4007"))
      (libsource (lib "eagle-import") (part "DIODE-GEN-PURPOSE-1KV-1A(DO-214AC)"))
    )
    (comp (ref "D87")
      (value "1N4007,")
      (footprint "eagle-import:DO-214AC")
      (fields (field (name "MPN") "1N4007"))
      (libsource (lib "eagle-import") (part "DIODE-GEN-PURPOSE-1KV-1A(DO-214AC)"))
    )
    (comp (ref "D88")
      (value "1N4007.")
      (footprint "eagle-import:DO-214AC")
      (fields (field (name "MPN") "1N4007"))
      (libsource (lib "eagle-import") (part "DIODE-GEN-PURPOSE-1KV-1A(DO-214AC)"))
    )
    (comp (ref "D89")
      (value "1N5817")
      (footprint "eagle-import:DO-214AC_SLIM")
      (libsource (lib "eagle-import") (part "DIODE-GEN-PURPOSE-1KV-1A(DO-214AC)DO-214AC/1206"))
    )
    (comp (ref "D90")
      (value "1N5817.")
      (footprint "eagle-import:DO-214AC_SLIM")
      (libsource (lib "eagle-import") (part "DIODE-GEN-PURPOSE-1KV-1A(DO-214AC)DO-214AC/1206"))
    )
    (comp (ref "D91")
      (value "1N5817.")
      (footprint "eagle-import:DO-214AC_SLIM")
      (libsource (lib "eagle-import") (part "DIODE-GEN-PURPOSE-1KV-1A(DO-214AC)DO-214AC/1206"))
    )
    (comp (ref "D92")
      (value "1N5817")
      (footprint "eagle-import:DO-214AC_SLIM")
      (libsource (lib "eagle-import") (part "DIODE-GEN-PURPOSE-1KV-1A(DO-214AC)DO-214AC/1206"))
    )
    (comp (ref "D93")
      (value "1N4007.")
      (footprint "eagle-import:DO-214AC")
      (fields (field (name "MPN") "1N4007"))
      (libsource (lib "eagle-import") (part "DIODE-GEN-PURPOSE-1KV-1A(DO-214AC)"))
    )
    (comp (ref "D94")
      (value "1N4007")
      (footprint "eagle-import:DO-214AC")
      (libsource (lib "eagle-import") (part "DIODE-GEN-PURPOSE-1KV-1A(DO-214AC)"))
    )
    (comp (ref "D95")
      (value "SM6T")
      (footprint "eagle-import:DO214AA")
      (libsource (lib "eagle-import") (part "SM6T"))
    )
    (comp (ref "D96")
      (value "SM6TDO214AA_BI")
      (footprint "eagle-import:DO214AA_BI")
      (libsource (lib "eagle-import") (part "SM6TDO214AA_BI"))
    )
    (comp (ref "FID29")
      (value "FIDUCIAL")
      (footprint "eagle-import:FIDUCIAL_1MM")
      (libsource (lib "eagle-import") (part "FIDUCIAL"))
    )
    (comp (ref "FID30")
      (value "FIDUCIAL")
      (footprint "eagle-import:FIDUCIAL_1MM")
      (libsource (lib "eagle-import") (part "FIDUCIAL"))
    )
    (comp (ref "FID31")
      (value "FIDUCIAL")
      (footprint "eagle-import:FIDUCIAL_1MM")
      (libsource (lib "eagle-import") (part "FIDUCIAL"))
    )
    (comp (ref "FID32")
      (value "FIDUCIAL")
      (footprint "eagle-import:FIDUCIAL_1MM")
      (libsource (lib "eagle-import") (part "FIDUCIAL"))
    )
    (comp (ref "IC78")
      (value "4028")
      (footprint "eagle-import:SO16")
      (libsource (lib "eagle-import") (part "4028D"))
    )
    (comp (ref "IC79")
      (value "6V pos")
      (footprint "eagle-import:78LXX")
      (libsource (lib "eagle-import") (part "v-reg_78LXX"))
    )
    (comp (ref "IC80")
      (value "317TO202H_NOHOLE")
      (footprint "eagle-import:TO220H_NOHOLE")
      (libsource (lib "eagle-import") (part "317TO202H_NOHOLE"))
    )
    (comp (ref "IC81")
      (value "ULN2004")
      (footprint "eagle-import:SO16")
      (libsource (lib "eagle-import") (part "ULN2004AD"))
    )
    (comp (ref "IC82")
      (value "LM339")
      (footprint "eagle-import:SO14")
      (libsource (lib "eagle-import") (part "LM339D"))
    )
    (comp (ref "IC83")
      (value "78L06")
      (footprint "eagle-import:SOT89_ROUND")
      (libsource (lib "eagle-import") (part "78LXXSOT89_ROUND"))
    )
    (comp (ref "IC84")
      (value "555")
      (footprint "eagle-import:SO08")
      (libsource (lib "eagle-import") (part "555DNE"))
    )
    (comp (ref "IC85")
      (value "4538")
      (footprint "eagle-import:SO16")
      (libsource (lib "eagle-import") (part "4538D"))
    )
    (comp (ref "IC86")
      (value "78L10")
      (footprint "eagle-import:SOT89_ROUND")
      (libsource (lib "eagle-import") (part "78LXXSOT89_ROUND"))
    )
    (comp (ref "IC87")
      (value "LM2904")
      (footprint "eagle-import:SO08")
      (libsource (lib "eagle-import") (part "LM358D"))
    )
    (comp (ref "JP36")
      (value "JP2EJP2_SMALLPADS")
      (footprint "eagle-import:JP2_SMALLPADS")
      (libsource (lib "eagle-import") (part "JP2EJP2_SMALLPADS"))
    )
    (comp (ref "JP37")
      (value "JP2E_ORIG")
      (footprint "eagle-import:JP2_ORIG_SMALLPADS")
      (libsource (lib "eagle-import") (part "JP2E_ORIG"))
    )
    (comp (ref "JP38")
      (value "JP2EJP2_SMALLPADS")
      (footprint "eagle-import:JP2_SMALLPADS")
      (libsource (lib "eagle-import") (part "JP2EJP2_SMALLPADS"))
    )
    (comp (ref "JP39")
      (value "JP2EJP2_SMALLPADS")
      (footprint "eagle-import:JP2_SMALLPADS")
      (libsource (lib "eagle-import") (part "JP2EJP2_SMALLPADS"))
    )
    (comp (ref "JP40")
      (value "JP2EJP2_SMALLPADS")
      (footprint "eagle-import:JP2_SMALLPADS")
      (libsource (lib "eagle-import") (part "JP2EJP2_SMALLPADS"))
    )
    (comp (ref "LED43")
      (value "LEDLD260")
      (footprint "eagle-import:LD260")
      (libsource (lib "eagle-import") (part "LEDLD260"))
    )
    (comp (ref "LED44")
      (value "LEDLD260")
      (footprint "eagle-import:LD260")
      (libsource (lib "eagle-import") (part "LEDLD260"))
    )
    (comp (ref "LED45")
      (value "LEDLD260")
      (footprint "eagle-import:LD260")
      (libsource (lib "eagle-import") (part "LEDLD260"))
    )
    (comp (ref "LED46")
      (value "LEDLD260")
      (footprint "eagle-import:LD260")
      (libsource (lib "eagle-import") (part "LEDLD260"))
    )
    (comp (ref "LED47")
      (value "LEDLD260")
      (footprint "eagle-import:LD260")
      (libsource (lib "eagle-import") (part "LEDLD260"))
    )
    (comp (ref "LED48")
      (value "LEDLD260")
      (footprint "eagle-import:LD260")
      (libsource (lib "eagle-import") (part "LEDLD260"))
    )
    (comp (ref "Q50")
      (value "BA")
      (footprint "eagle-import:SOT89")
      (libsource (lib "eagle-import") (part "PNP-TRANSISTOR_SOT89"))
    )
    (comp (ref "Q51")
      (value "BA.")
      (footprint "eagle-import:SOT89")
      (libsource (lib "eagle-import") (part "PNP-TRANSISTOR_SOT89"))
    )
    (comp (ref "Q52")
      (value "BA.")
      (footprint "eagle-import:SOT89")
      (libsource (lib "eagle-import") (part "PNP-TRANSISTOR_SOT89"))
    )
    (comp (ref "Q53")
      (value "BA")
      (footprint "eagle-import:SOT89")
      (libsource (lib "eagle-import") (part "PNP-TRANSISTOR_SOT89"))
    )
    (comp (ref "Q54")
      (value "MY")
      (footprint "eagle-import:SOT89")
      (libsource (lib "eagle-import") (part "NPN-TRANSISTOR_SOT89"))
    )
    (comp (ref "Q55")
      (value "J1")
      (footprint "eagle-import:SOT-23")
      (fields (field (name "MPN") "BSS138W-7-F"))
      (libsource (lib "eagle-import") (part "SMD-MOSFET-N-CH-50V-200MA-BSS138W-7-F(SOT-23)"))
    )
    (comp (ref "Q56")
      (value "J1")
      (footprint "eagle-import:SOT-23")
      (fields (field (name "MPN") "BSS138W-7-F"))
      (libsource (lib "eagle-import") (part "SMD-MOSFET-N-CH-50V-200MA-BSS138W-7-F(SOT-23)"))
    )
    (comp (ref "R323")
      (value "47")
      (footprint "eagle-import:V235_17_1MM")
      (libsource (lib "eagle-import") (part "R-EU_V235/17_1MM"))
    )
    (comp (ref "R324")
      (value "13")
      (footprint "eagle-import:R1206")
      (fields (field (name "MPN") "RC1206JR-0713RL"))
      (libsource (lib "eagle-import") (part "SMD-RES-13R-5%-1/4W(1206)"))
    )
    (comp (ref "R325")
      (value "47")
      (footprint "eagle-import:V235_17_1MM")
      (libsource (lib "eagle-import") (part "R-EU_V235/17_1MM"))
    )
    (comp (ref "R326")
      (value "104")
      (footprint "eagle-import:R0805")
      (fields (field (name "MPN") "RC0805FR-0710KL"))
      (libsource (lib "eagle-import") (part "SMD-RES-10K-1%-1/8W(0805)"))
    )
    (comp (ref "R327")
      (value "104")
      (footprint "eagle-import:R0805")
      (fields (field (name "MPN") "RC0805FR-0710KL"))
      (libsource (lib "eagle-import") (part "SMD-RES-10K-1%-1/8W(0805)"))
    )
    (comp (ref "R328")
      (value "104")
      (footprint "eagle-import:R0805")
      (fields (field (name "MPN") "RC0805FR-0710KL"))
      (libsource (lib "eagle-import") (part "SMD-RES-10K-1%-1/8W(0805)"))
    )
    (comp (ref "R329")
      (value "4701")
      (footprint "eagle-import:R0805")
      (fields (field (name "MPN") "RC0805JR-074K7L"))
      (libsource (lib "eagle-import") (part "SMD-RES-4.7K-5%-1/8W(0805)"))
    )
    (comp (ref "R330")
      (value "1002")
      (footprint "eagle-import:R0805")
      (fields (field (name "MPN") "RC0805FR-0710KL"))
      (libsource (lib "eagle-import") (part "SMD-RES-10K-1%-1/8W(0805)"))
    )
    (comp (ref "R331")
      (value "1002")
      (footprint "eagle-import:R0805")
      (fields (field (name "MPN") "RC0805FR-0710KL"))
      (libsource (lib "eagle-import") (part "SMD-RES-10K-1%-1/8W(0805)"))
    )
    (comp (ref "R332")
      (value "1502")
      (footprint "eagle-import:R0805")
      (fields (field (name "MPN") "RC0805FR-0710KL"))
      (libsource (lib "eagle-import") (part "SMD-RES-10K-1%-1/8W(0805)"))
    )
    (comp (ref "R333")
      (value "104")
      (footprint "eagle-import:R0805")
      (fields (field (name "MPN") "RC0805FR-0710KL"))
      (libsource (lib "eagle-import") (part "SMD-RES-10K-1%-1/8W(0805)"))
    )
    (comp (ref "R334")
      (value "104")
      (footprint "eagle-import:R0805")
      (fields (field (name "MPN") "RC0805FR-0710KL"))
      (libsource (lib "eagle-import") (part "SMD-RES-10K-1%-1/8W(0805)"))
    )
    (comp (ref "R335")
      (value "1502")
      (footprint "eagle-import:R0805")
      (fields (field (name "MPN") "RC0805FR-0710KL"))
      (libsource (lib "eagle-import") (part "SMD-RES-10K-1%-1/8W(0805)"))
    )
    (comp (ref "R336")
      (value "1002")
      (footprint "eagle-import:R0805")
      (fields (field (name "MPN") "RC0805FR-0710KL"))
      (libsource (lib "eagle-import") (part "SMD-RES-10K-1%-1/8W(0805)"))
    )
    (comp (ref "R337")
      (value "2201")
      (footprint "eagle-import:R0805")
      (fields (field (name "MPN") "RC0805JR-072K2L"))
      (libsource (lib "eagle-import") (part "SMD-RES-2.2K-5%-1/8W(0805)"))
    )
    (comp (ref "R338")
      (value "1002")
      (footprint "eagle-import:R0805")
      (fields (field (name "MPN") "RC0805FR-0710KL"))
      (libsource (lib "eagle-import") (part "SMD-RES-10K-1%-1/8W(0805)"))
    )
    (comp (ref "R339")
      (value "4701")
      (footprint "eagle-import:R0805")
      (fields (field (name "MPN") "RC0805JR-074K7L"))
      (libsource (lib "eagle-import") (part "SMD-RES-4.7K-5%-1/8W(0805)"))
    )
    (comp (ref "R340")
      (value "2702")
      (footprint "eagle-import:R0805")
      (fields (field (name "MPN") "RC0805JR-074K7L"))
      (libsource (lib "eagle-import") (part "SMD-RES-4.7K-5%-1/8W(0805)"))
    )
    (comp (ref "R341")
      (value "102")
      (footprint "eagle-import:R0805")
      (fields (field (name "MPN") "RC0805JR-071KL"))
      (libsource (lib "eagle-import") (part "SMD-RES-1K-5%-1/8W(0805)"))
    )
    (comp (ref "R342")
      (value "R_user")
      (footprint "eagle-import:R0805")
      (libsource (lib "eagle-import") (part "R-EU_R0805"))
    )
    (comp (ref "R343")
      (value "100")
      (footprint "eagle-import:R0805")
      (fields (field (name "MPN") "RC0805JR-07220RL"))
      (libsource (lib "eagle-import") (part "SMD-RES-220R-5%-1/8W(0805)"))
    )
    (comp (ref "R344")
      (value "(101)")
      (footprint "eagle-import:R0805")
      (fields (field (name "MPN") "RC0805JR-07100RL"))
      (libsource (lib "eagle-import") (part "SMD-RES-100R-5%-1/8W(0805)"))
    )
    (comp (ref "R345")
      (value "(1000)")
      (footprint "eagle-import:R0805")
      (fields (field (name "MPN") "RC0805JR-07100RL"))
      (libsource (lib "eagle-import") (part "SMD-RES-100R-5%-1/8W(0805)"))
    )
    (comp (ref "R346")
      (value "102")
      (footprint "eagle-import:R0805")
      (fields (field (name "MPN") "RC0805JR-071KL"))
      (libsource (lib "eagle-import") (part "SMD-RES-1K-5%-1/8W(0805)"))
    )
    (comp (ref "R347")
      (value "13")
      (footprint "eagle-import:R1206")
      (fields (field (name "MPN") "RC1206JR-0713RL"))
      (libsource (lib "eagle-import") (part "SMD-RES-13R-5%-1/4W(1206)"))
    )
    (comp (ref "R348")
      (value "13")
      (footprint "eagle-import:R1206")
      (fields (field (name "MPN") "RC1206JR-0713RL"))
      (libsource (lib "eagle-import") (part "SMD-RES-13R-5%-1/4W(1206)"))
    )
    (comp (ref "R349")
      (value "2702")
      (footprint "eagle-import:R0805")
      (fields (field (name "MPN") "RC0805JR-074K7L"))
      (libsource (lib "eagle-import") (part "SMD-RES-4.7K-5%-1/8W(0805)"))
    )
    (comp (ref "R350")
      (value "4701")
      (footprint "eagle-import:R0805")
      (fields (field (name "MPN") "RC0805JR-074K7L"))
      (libsource (lib "eagle-import") (part "SMD-RES-4.7K-5%-1/8W(0805)"))
    )
    (comp (ref "R351")
      (value "100")
      (footprint "eagle-import:R0805")
      (fields (field (name "MPN") "RC0805JR-072K2L"))
      (libsource (lib "eagle-import") (part "SMD-RES-2.2K-5%-1/8W(0805)"))
    )
    (comp (ref "R352")
      (value "(101)")
      (footprint "eagle-import:R0805")
      (fields (field (name "MPN") "RC0805JR-072K2L"))
      (libsource (lib "eagle-import") (part "SMD-RES-2.2K-5%-1/8W(0805)"))
    )
    (comp (ref "R353")
      (value "104")
      (footprint "eagle-import:R0805")
      (fields (field (name "MPN") "RC0805FR-0710KL"))
      (libsource (lib "eagle-import") (part "SMD-RES-10K-1%-1/8W(0805)"))
    )
    (comp (ref "R354")
      (value "104")
      (footprint "eagle-import:R0805")
      (fields (field (name "MPN") "RC0805FR-0710KL"))
      (libsource (lib "eagle-import") (part "SMD-RES-10K-1%-1/8W(0805)"))
    )
    (comp (ref "R355")
      (value "(1002)")
      (footprint "eagle-import:R0805")
      (fields (field (name "MPN") "RC0805FR-0710KL"))
      (libsource (lib "eagle-import") (part "SMD-RES-10K-1%-1/8W(0805)"))
    )
    (comp (ref "R356")
      (value "2702")
      (footprint "eagle-import:R0805")
      (fields (field (name "MPN") "RC0805FR-0710KL"))
      (libsource (lib "eagle-import") (part "SMD-RES-10K-1%-1/8W(0805)"))
    )
    (comp (ref "R357")
      (value "47")
      (footprint "eagle-import:V235_17_1MM")
      (libsource (lib "eagle-import") (part "R-EU_V235/17_1MM"))
    )
    (comp (ref "R358")
      (value "47")
      (footprint "eagle-import:V235_17_1MM")
      (libsource (lib "eagle-import") (part "R-EU_V235/17_1MM"))
    )
    (comp (ref "R359")
      (value "2702")
      (footprint "eagle-import:R0805")
      (fields (field (name "MPN") "RC0805JR-074K7L"))
      (libsource (lib "eagle-import") (part "SMD-RES-4.7K-5%-1/8W(0805)"))
    )
    (comp (ref "R360")
      (value "2201")
      (footprint "eagle-import:R0805")
      (fields (field (name "MPN") "RC0805JR-072K2L"))
      (libsource (lib "eagle-import") (part "SMD-RES-2.2K-5%-1/8W(0805)"))
    )
    (comp (ref "R361")
      (value "(1002)")
      (footprint "eagle-import:R0805")
      (fields (field (name "MPN") "RC0805JR-074K7L"))
      (libsource (lib "eagle-import") (part "SMD-RES-4.7K-5%-1/8W(0805)"))
    )
    (comp (ref "R362")
      (value "1002")
      (footprint "eagle-import:R0805")
      (fields (field (name "MPN") "RC0805FR-0710KL"))
      (libsource (lib "eagle-import") (part "SMD-RES-10K-1%-1/8W(0805)"))
    )
    (comp (ref "R363")
      (value "102")
      (footprint "eagle-import:R0805")
      (fields (field (name "MPN") "RC0805JR-071KL"))
      (libsource (lib "eagle-import") (part "SMD-RES-1K-5%-1/8W(0805)"))
    )
    (comp (ref "R364")
      (value "2702")
      (footprint "eagle-import:R0805")
      (fields (field (name "MPN") "RC0805JR-074K7L"))
      (libsource (lib "eagle-import") (part "SMD-RES-4.7K-5%-1/8W(0805)"))
    )
    (comp (ref "R365")
      (value "102")
      (footprint "eagle-import:R0805")
      (fields (field (name "MPN") "RC0805JR-071KL"))
      (libsource (lib "eagle-import") (part "SMD-RES-1K-5%-1/8W(0805)"))
    )
    (comp (ref "R366")
      (value "102")
      (footprint "eagle-import:R0805")
      (fields (field (name "MPN") "RC0805JR-071KL"))
      (libsource (lib "eagle-import") (part "SMD-RES-1K-5%-1/8W(0805)"))
    )
    (comp (ref "R367")
      (value "13")
      (footprint "eagle-import:R1206")
      (fields (field (name "MPN") "RC1206JR-0713RL"))
      (libsource (lib "eagle-import") (part "SMD-RES-13R-5%-1/4W(1206)"))
    )
    (comp (ref "R368")
      (value "R_user")
      (footprint "eagle-import:R0805")
      (libsource (lib "eagle-import") (part "R-EU_R0805"))
    )
    (comp (ref "SJ8") (value "SJ") (footprint "eagle-import:SJ") (libsource (lib "eagle-import") (part "SJ")))
    (comp (ref "START7")
      (value "TPSB2.0")
      (footprint "eagle-import:B2.0")
      (libsource (lib "eagle-import") (part "TPSB2.0"))
    )
    (comp (ref "TP162")
      (value "TPSB2.0")
      (footprint "eagle-import:B2.0")
      (libsource (lib "eagle-import") (part "TPSB2.0"))
    )
    (comp (ref "TP163")
      (value "TPSB2.0")
      (footprint "eagle-import:B2.0")
      (libsource (lib "eagle-import") (part "TPSB2.0"))
    )
    (comp (ref "TP164")
      (value "TPSB2.0")
      (footprint "eagle-import:B2.0")
      (libsource (lib "eagle-import") (part "TPSB2.0"))
    )
    (comp (ref "TP165")
      (value "TPSB2.0")
      (footprint "eagle-import:B2.0")
      (libsource (lib "eagle-import") (part "TPSB2.0"))
    )
    (comp (ref "TP166")
      (value "TPSB2.0")
      (footprint "eagle-import:B2.0")
      (libsource (lib "eagle-import") (part "TPSB2.0"))
    )
    (comp (ref "TP167")
      (value "TPSB2.0")
      (footprint "eagle-import:B2.0")
      (libsource (lib "eagle-import") (part "TPSB2.0"))
    )
    (comp (ref "TP168")
      (value "TPSB2.0")
      (footprint "eagle-import:B2.0")
      (libsource (lib "eagle-import") (part "TPSB2.0"))
    )
    (comp (ref "TP169")
      (value "TPSB2.0")
      (footprint "eagle-import:B2.0")
      (libsource (lib "eagle-import") (part "TPSB2.0"))
    )
    (comp (ref "TP170")
      (value "TPSB2.0")
      (footprint "eagle-import:B2.0")
      (libsource (lib "eagle-import") (part "TPSB2.0"))
    )
    (comp (ref "TP171")
      (value "TPSB2.0")
      (footprint "eagle-import:B2.0")
      (libsource (lib "eagle-import") (part "TPSB2.0"))
    )
    (comp (ref "TP172")
      (value "TPSB2.0")
      (footprint "eagle-import:B2.0")
      (libsource (lib "eagle-import") (part "TPSB2.0"))
    )
    (comp (ref "TP173")
      (value "TPSB2.0")
      (footprint "eagle-import:B2.0")
      (libsource (lib "eagle-import") (part "TPSB2.0"))
    )
    (comp (ref "TP174")
      (value "TPSB2.0")
      (footprint "eagle-import:B2.0")
      (libsource (lib "eagle-import") (part "TPSB2.0"))
    )
    (comp (ref "TP175")
      (value "TPSB2.0")
      (footprint "eagle-import:B2.0")
      (libsource (lib "eagle-import") (part "TPSB2.0"))
    )
    (comp (ref "TP176")
      (value "TPSB2.0")
      (footprint "eagle-import:B2.0")
      (libsource (lib "eagle-import") (part "TPSB2.0"))
    )
    (comp (ref "TP177")
      (value "TPSB2.0")
      (footprint "eagle-import:B2.0")
      (libsource (lib "eagle-import") (part "TPSB2.0"))
    )
    (comp (ref "TP178")
      (value "TPSB2.0")
      (footprint "eagle-import:B2.0")
      (libsource (lib "eagle-import") (part "TPSB2.0"))
    )
    (comp (ref "TP179")
      (value "TPSB2.0")
      (footprint "eagle-import:B2.0")
      (libsource (lib "eagle-import") (part "TPSB2.0"))
    )
    (comp (ref "TP180")
      (value "TPSB1,27")
      (footprint "eagle-import:B1,27")
      (libsource (lib "eagle-import") (part "TPSB1,27"))
    )
    (comp (ref "TP181")
      (value "TPSB2.0")
      (footprint "eagle-import:B2.0")
      (libsource (lib "eagle-import") (part "TPSB2.0"))
    )
    (comp (ref "TP182")
      (value "TPSB2.0")
      (footprint "eagle-import:B2.0")
      (libsource (lib "eagle-import") (part "TPSB2.0"))
    )
    (comp (ref "TP183")
      (value "TPSB2.0")
      (footprint "eagle-import:B2.0")
      (libsource (lib "eagle-import") (part "TPSB2.0"))
    )
    (comp (ref "TP184")
      (value "TPSB2.0")
      (footprint "eagle-import:B2.0")
      (libsource (lib "eagle-import") (part "TPSB2.0"))
    )
    (comp (ref "X22")
      (value "CON_BMWV2")
      (footprint "eagle-import:24-PIN_V2")
      (libsource (lib "eagle-import") (part "CON_BMWV2"))
    )
    (comp (ref "X23")
      (value "22-23-2051")
      (footprint "eagle-import:22-23-2051")
      (fields (field (name "MF") "MOLEX"))
      (libsource (lib "eagle-import") (part "22-23-2051"))
    )
    (comp (ref "X24")
      (value "22-23-2021")
      (footprint "eagle-import:22-23-2021")
      (fields (field (name "MF") "MOLEX"))
      (libsource (lib "eagle-import") (part "22-23-2021"))
    )
    (comp (ref "6V10")
      (value "TPSB2.0")
      (footprint "eagle-import:B2.0")
      (libsource (lib "eagle-import") (part "TPSB2.0"))
    )
    (comp (ref "10V10")
      (value "TPSB2.0")
      (footprint "eagle-import:B2.0")
      (libsource (lib "eagle-import") (part "TPSB2.0"))
    )
    (comp (ref "21")
      (value "2081-1132")
      (footprint "eagle-import:12-PIN")
      (libsource (lib "eagle-import") (part "2081-1132"))
    )
    (comp (ref "22")
      (value "2081-1132")
      (footprint "eagle-import:12-PIN")
      (libsource (lib "eagle-import") (part "2081-1132"))
    )
    (comp (ref "C101")
      (value "100u")
      (footprint "eagle-import:C1206")
      (fields (field (name "MPN") "GRM31CR60J107ME39L"))
      (libsource (lib "eagle-import") (part "CERAMIC-100UF-6.3V-20%-X5R(1206)"))
    )
    (comp (ref "C102")
      (value "100u")
      (footprint "eagle-import:C1206")
      (fields (field (name "MPN") "GRM31CR60J107ME39L"))
      (libsource (lib "eagle-import") (part "CERAMIC-100UF-6.3V-20%-X5R(1206)"))
    )
    (comp (ref "C103")
      (value "100nF,")
      (footprint "eagle-import:C0805")
      (fields (field (name "MPN") "CC0805KRX7R9BB104"))
      (libsource (lib "eagle-import") (part "CERAMIC-100NF-50V-10%-X7R(0805)"))
    )
    (comp (ref "C104")
      (value "4.7u")
      (footprint "eagle-import:C0805")
      (fields (field (name "MPN") "CC0805KKX5R8BB475"))
      (libsource (lib "eagle-import") (part "CERAMIC-4.7UF-25V-10%-X5R(0805)"))
    )
    (comp (ref "C105")
      (value "100nF.")
      (footprint "eagle-import:C0805")
      (fields (field (name "MPN") "CC0805KRX7R9BB104"))
      (libsource (lib "eagle-import") (part "CERAMIC-100NF-50V-10%-X7R(0805)"))
    )
    (comp (ref "C106")
      (value "100nF.")
      (footprint "eagle-import:C0805")
      (fields (field (name "MPN") "CC0805KRX7R9BB104"))
      (libsource (lib "eagle-import") (part "CERAMIC-100NF-50V-10%-X7R(0805)"))
    )
    (comp (ref "C107")
      (value "2.2nF")
      (footprint "eagle-import:C0805")
      (fields (field (name "MPN") "CC0805KRX7R9BB104"))
      (libsource (lib "eagle-import") (part "CERAMIC-100NF-50V-10%-X7R(0805)"))
    )
    (comp (ref "C108")
      (value "100nF")
      (footprint "eagle-import:C0805")
      (fields (field (name "MPN") "CC0805KRX7R9BB104"))
      (libsource (lib "eagle-import") (part "CERAMIC-100NF-50V-10%-X7R(0805)"))
    )
    (comp (ref "C109")
      (value "100nF")
      (footprint "eagle-import:C0805")
      (fields (field (name "MPN") "CC0805KRX7R9BB104"))
      (libsource (lib "eagle-import") (part "CERAMIC-100NF-50V-10%-X7R(0805)"))
    )
    (comp (ref "C110")
      (value "100nF,")
      (footprint "eagle-import:C0805")
      (fields (field (name "MPN") "CC0805KRX7R9BB104"))
      (libsource (lib "eagle-import") (part "CERAMIC-100NF-50V-10%-X7R(0805)"))
    )
    (comp (ref "D121")
      (value "1N4007")
      (footprint "eagle-import:DO-214AC")
      (libsource (lib "eagle-import") (part "DIODE-GEN-PURPOSE-1KV-1A(DO-214AC)"))
    )
    (comp (ref "D122")
      (value "1N4007,")
      (footprint "eagle-import:DO-214AC")
      (fields (field (name "MPN") "1N4007"))
      (libsource (lib "eagle-import") (part "DIODE-GEN-PURPOSE-1KV-1A(DO-214AC)"))
    )
    (comp (ref "D123")
      (value "1N4007,")
      (footprint "eagle-import:DO-214AC")
      (fields (field (name "MPN") "1N4007"))
      (libsource (lib "eagle-import") (part "DIODE-GEN-PURPOSE-1KV-1A(DO-214AC)"))
    )
    (comp (ref "D124")
      (value "1N4007.")
      (footprint "eagle-import:DO-214AC")
      (fields (field (name "MPN") "1N4007"))
      (libsource (lib "eagle-import") (part "DIODE-GEN-PURPOSE-1KV-1A(DO-214AC)"))
    )
    (comp (ref "D125")
      (value "1N5817")
      (footprint "eagle-import:DO-214AC_SLIM")
      (libsource (lib "eagle-import") (part "DIODE-GEN-PURPOSE-1KV-1A(DO-214AC)DO-214AC/1206"))
    )
    (comp (ref "D126")
      (value "1N5817.")
      (footprint "eagle-import:DO-214AC_SLIM")
      (libsource (lib "eagle-import") (part "DIODE-GEN-PURPOSE-1KV-1A(DO-214AC)DO-214AC/1206"))
    )
    (comp (ref "D127")
      (value "1N5817.")
      (footprint "eagle-import:DO-214AC_SLIM")
      (libsource (lib "eagle-import") (part "DIODE-GEN-PURPOSE-1KV-1A(DO-214AC)DO-214AC/1206"))
    )
    (comp (ref "D128")
      (value "1N5817")
      (footprint "eagle-import:DO-214AC_SLIM")
      (libsource (lib "eagle-import") (part "DIODE-GEN-PURPOSE-1KV-1A(DO-214AC)DO-214AC/1206"))
    )
    (comp (ref "D129")
      (value "1N4007.")
      (footprint "eagle-import:DO-214AC")
      (fields (field (name "MPN") "1N4007"))
      (libsource (lib "eagle-import") (part "DIODE-GEN-PURPOSE-1KV-1A(DO-214AC)"))
    )
    (comp (ref "D130")
      (value "1N4007")
      (footprint "eagle-import:DO-214AC")
      (libsource (lib "eagle-import") (part "DIODE-GEN-PURPOSE-1KV-1A(DO-214AC)"))
    )
    (comp (ref "D131")
      (value "SM6T")
      (footprint "eagle-import:DO214AA")
      (libsource (lib "eagle-import") (part "SM6T"))
    )
    (comp (ref "D132")
      (value "SM6TDO214AA_BI")
      (footprint "eagle-import:DO214AA_BI")
      (libsource (lib "eagle-import") (part "SM6TDO214AA_BI"))
    )
    (comp (ref "FID41")
      (value "FIDUCIAL")
      (footprint "eagle-import:FIDUCIAL_1MM")
      (libsource (lib "eagle-import") (part "FIDUCIAL"))
    )
    (comp (ref "FID42")
      (value "FIDUCIAL")
      (footprint "eagle-import:FIDUCIAL_1MM")
      (libsource (lib "eagle-import") (part "FIDUCIAL"))
    )
    (comp (ref "FID43")
      (value "FIDUCIAL")
      (footprint "eagle-import:FIDUCIAL_1MM")
      (libsource (lib "eagle-import") (part "FIDUCIAL"))
    )
    (comp (ref "FID44")
      (value "FIDUCIAL")
      (footprint "eagle-import:FIDUCIAL_1MM")
      (libsource (lib "eagle-import") (part "FIDUCIAL"))
    )
    (comp (ref "IC111")
      (value "4028")
      (footprint "eagle-import:SO16")
      (libsource (lib "eagle-import") (part "4028D"))
    )
    (comp (ref "IC112")
      (value "6V pos")
      (footprint "eagle-import:78LXX")
      (libsource (lib "eagle-import") (part "v-reg_78LXX"))
    )
    (comp (ref "IC113")
      (value "317TO202H_NOHOLE")
      (footprint "eagle-import:TO220H_NOHOLE")
      (libsource (lib "eagle-import") (part "317TO202H_NOHOLE"))
    )
    (comp (ref "IC114")
      (value "ULN2004")
      (footprint "eagle-import:SO16")
      (libsource (lib "eagle-import") (part "ULN2004AD"))
    )
    (comp (ref "IC115")
      (value "LM339")
      (footprint "eagle-import:SO14")
      (libsource (lib "eagle-import") (part "LM339D"))
    )
    (comp (ref "IC116")
      (value "78L06")
      (footprint "eagle-import:SOT89_ROUND")
      (libsource (lib "eagle-import") (part "78LXXSOT89_ROUND"))
    )
    (comp (ref "IC117")
      (value "555")
      (footprint "eagle-import:SO08")
      (libsource (lib "eagle-import") (part "555DNE"))
    )
    (comp (ref "IC118")
      (value "4538")
      (footprint "eagle-import:SO16")
      (libsource (lib "eagle-import") (part "4538D"))
    )
    (comp (ref "IC119")
      (value "78L10")
      (footprint "eagle-import:SOT89_ROUND")
      (libsource (lib "eagle-import") (part "78LXXSOT89_ROUND"))
    )
    (comp (ref "IC120")
      (value "LM2904")
      (footprint "eagle-import:SO08")
      (libsource (lib "eagle-import") (part "LM358D"))
    )
    (comp (ref "JP51")
      (value "JP2EJP2_SMALLPADS")
      (footprint "eagle-import:JP2_SMALLPADS")
      (libsource (lib "eagle-import") (part "JP2EJP2_SMALLPADS"))
    )
    (comp (ref "JP52")
      (value "JP2E_ORIG")
      (footprint "eagle-import:JP2_ORIG_SMALLPADS")
      (libsource (lib "eagle-import") (part "JP2E_ORIG"))
    )
    (comp (ref "JP53")
      (value "JP2EJP2_SMALLPADS")
      (footprint "eagle-import:JP2_SMALLPADS")
      (libsource (lib "eagle-import") (part "JP2EJP2_SMALLPADS"))
    )
    (comp (ref "JP54")
      (value "JP2EJP2_SMALLPADS")
      (footprint "eagle-import:JP2_SMALLPADS")
      (libsource (lib "eagle-import") (part "JP2EJP2_SMALLPADS"))
    )
    (comp (ref "JP55")
      (value "JP2EJP2_SMALLPADS")
      (footprint "eagle-import:JP2_SMALLPADS")
      (libsource (lib "eagle-import") (part "JP2EJP2_SMALLPADS"))
    )
    (comp (ref "LED61")
      (value "LEDLD260")
      (footprint "eagle-import:LD260")
      (libsource (lib "eagle-import") (part "LEDLD260"))
    )
    (comp (ref "LED62")
      (value "LEDLD260")
      (footprint "eagle-import:LD260")
      (libsource (lib "eagle-import") (part "LEDLD260"))
    )
    (comp (ref "LED63")
      (value "LEDLD260")
      (footprint "eagle-import:LD260")
      (libsource (lib "eagle-import") (part "LEDLD260"))
    )
    (comp (ref "LED64")
      (value "LEDLD260")
      (footprint "eagle-import:LD260")
      (libsource (lib "eagle-import") (part "LEDLD260"))
    )
    (comp (ref "LED65")
      (value "LEDLD260")
      (footprint "eagle-import:LD260")
      (libsource (lib "eagle-import") (part "LEDLD260"))
    )
    (comp (ref "LED66")
      (value "LEDLD260")
      (footprint "eagle-import:LD260")
      (libsource (lib "eagle-import") (part "LEDLD260"))
    )
    (comp (ref "Q71")
      (value "BA")
      (footprint "eagle-import:SOT89")
      (libsource (lib "eagle-import") (part "PNP-TRANSISTOR_SOT89"))
    )
    (comp (ref "Q72")
      (value "BA.")
      (footprint "eagle-import:SOT89")
      (libsource (lib "eagle-import") (part "PNP-TRANSISTOR_SOT89"))
    )
    (comp (ref "Q73")
      (value "BA.")
      (footprint "eagle-import:SOT89")
      (libsource (lib "eagle-import") (part "PNP-TRANSISTOR_SOT89"))
    )
    (comp (ref "Q74")
      (value "BA")
      (footprint "eagle-import:SOT89")
      (libsource (lib "eagle-import") (part "PNP-TRANSISTOR_SOT89"))
    )
    (comp (ref "Q75")
      (value "MY")
      (footprint "eagle-import:SOT89")
      (libsource (lib "eagle-import") (part "NPN-TRANSISTOR_SOT89"))
    )
    (comp (ref "Q76")
      (value "J1")
      (footprint "eagle-import:SOT-23")
      (fields (field (name "MPN") "BSS138W-7-F"))
      (libsource (lib "eagle-import") (part "SMD-MOSFET-N-CH-50V-200MA-BSS138W-7-F(SOT-23)"))
    )
    (comp (ref "Q77")
      (value "J1")
      (footprint "eagle-import:SOT-23")
      (fields (field (name "MPN") "BSS138W-7-F"))
      (libsource (lib "eagle-import") (part "SMD-MOSFET-N-CH-50V-200MA-BSS138W-7-F(SOT-23)"))
    )
    (comp (ref "R461")
      (value "47")
      (footprint "eagle-import:V235_17_1MM")
      (libsource (lib "eagle-import") (part "R-EU_V235/17_1MM"))
    )
    (comp (ref "R462")
      (value "13")
      (footprint "eagle-import:R1206")
      (fields (field (name "MPN") "RC1206JR-0713RL"))
      (libsource (lib "eagle-import") (part "SMD-RES-13R-5%-1/4W(1206)"))
    )
    (comp (ref "R463")
      (value "47")
      (footprint "eagle-import:V235_17_1MM")
      (libsource (lib "eagle-import") (part "R-EU_V235/17_1MM"))
    )
    (comp (ref "R464")
      (value "104")
      (footprint "eagle-import:R0805")
      (fields (field (name "MPN") "RC0805FR-0710KL"))
      (libsource (lib "eagle-import") (part "SMD-RES-10K-1%-1/8W(0805)"))
    )
    (comp (ref "R465")
      (value "104")
      (footprint "eagle-import:R0805")
      (fields (field (name "MPN") "RC0805FR-0710KL"))
      (libsource (lib "eagle-import") (part "SMD-RES-10K-1%-1/8W(0805)"))
    )
    (comp (ref "R466")
      (value "104")
      (footprint "eagle-import:R0805")
      (fields (field (name "MPN") "RC0805FR-0710KL"))
      (libsource (lib "eagle-import") (part "SMD-RES-10K-1%-1/8W(0805)"))
    )
    (comp (ref "R467")
      (value "4701")
      (footprint "eagle-import:R0805")
      (fields (field (name "MPN") "RC0805JR-074K7L"))
      (libsource (lib "eagle-import") (part "SMD-RES-4.7K-5%-1/8W(0805)"))
    )
    (comp (ref "R468")
      (value "1002")
      (footprint "eagle-import:R0805")
      (fields (field (name "MPN") "RC0805FR-0710KL"))
      (libsource (lib "eagle-import") (part "SMD-RES-10K-1%-1/8W(0805)"))
    )
    (comp (ref "R469")
      (value "1002")
      (footprint "eagle-import:R0805")
      (fields (field (name "MPN") "RC0805FR-0710KL"))
      (libsource (lib "eagle-import") (part "SMD-RES-10K-1%-1/8W(0805)"))
    )
    (comp (ref "R470")
      (value "1502")
      (footprint "eagle-import:R0805")
      (fields (field (name "MPN") "RC0805FR-0710KL"))
      (libsource (lib "eagle-import") (part "SMD-RES-10K-1%-1/8W(0805)"))
    )
    (comp (ref "R471")
      (value "104")
      (footprint "eagle-import:R0805")
      (fields (field (name "MPN") "RC0805FR-0710KL"))
      (libsource (lib "eagle-import") (part "SMD-RES-10K-1%-1/8W(0805)"))
    )
    (comp (ref "R472")
      (value "104")
      (footprint "eagle-import:R0805")
      (fields (field (name "MPN") "RC0805FR-0710KL"))
      (libsource (lib "eagle-import") (part "SMD-RES-10K-1%-1/8W(0805)"))
    )
    (comp (ref "R473")
      (value "1502")
      (footprint "eagle-import:R0805")
      (fields (field (name "MPN") "RC0805FR-0710KL"))
      (libsource (lib "eagle-import") (part "SMD-RES-10K-1%-1/8W(0805)"))
    )
    (comp (ref "R474")
      (value "1002")
      (footprint "eagle-import:R0805")
      (fields (field (name "MPN") "RC0805FR-0710KL"))
      (libsource (lib "eagle-import") (part "SMD-RES-10K-1%-1/8W(0805)"))
    )
    (comp (ref "R475")
      (value "2201")
      (footprint "eagle-import:R0805")
      (fields (field (name "MPN") "RC0805JR-072K2L"))
      (libsource (lib "eagle-import") (part "SMD-RES-2.2K-5%-1/8W(0805)"))
    )
    (comp (ref "R476")
      (value "1002")
      (footprint "eagle-import:R0805")
      (fields (field (name "MPN") "RC0805FR-0710KL"))
      (libsource (lib "eagle-import") (part "SMD-RES-10K-1%-1/8W(0805)"))
    )
    (comp (ref "R477")
      (value "4701")
      (footprint "eagle-import:R0805")
      (fields (field (name "MPN") "RC0805JR-074K7L"))
      (libsource (lib "eagle-import") (part "SMD-RES-4.7K-5%-1/8W(0805)"))
    )
    (comp (ref "R478")
      (value "2702")
      (footprint "eagle-import:R0805")
      (fields (field (name "MPN") "RC0805JR-074K7L"))
      (libsource (lib "eagle-import") (part "SMD-RES-4.7K-5%-1/8W(0805)"))
    )
    (comp (ref "R479")
      (value "102")
      (footprint "eagle-import:R0805")
      (fields (field (name "MPN") "RC0805JR-071KL"))
      (libsource (lib "eagle-import") (part "SMD-RES-1K-5%-1/8W(0805)"))
    )
    (comp (ref "R480")
      (value "R_user")
      (footprint "eagle-import:R0805")
      (libsource (lib "eagle-import") (part "R-EU_R0805"))
    )
    (comp (ref "R481")
      (value "100")
      (footprint "eagle-import:R0805")
      (fields (field (name "MPN") "RC0805JR-07220RL"))
      (libsource (lib "eagle-import") (part "SMD-RES-220R-5%-1/8W(0805)"))
    )
    (comp (ref "R482")
      (value "(101)")
      (footprint "eagle-import:R0805")
      (fields (field (name "MPN") "RC0805JR-07100RL"))
      (libsource (lib "eagle-import") (part "SMD-RES-100R-5%-1/8W(0805)"))
    )
    (comp (ref "R483")
      (value "(1000)")
      (footprint "eagle-import:R0805")
      (fields (field (name "MPN") "RC0805JR-07100RL"))
      (libsource (lib "eagle-import") (part "SMD-RES-100R-5%-1/8W(0805)"))
    )
    (comp (ref "R484")
      (value "102")
      (footprint "eagle-import:R0805")
      (fields (field (name "MPN") "RC0805JR-071KL"))
      (libsource (lib "eagle-import") (part "SMD-RES-1K-5%-1/8W(0805)"))
    )
    (comp (ref "R485")
      (value "13")
      (footprint "eagle-import:R1206")
      (fields (field (name "MPN") "RC1206JR-0713RL"))
      (libsource (lib "eagle-import") (part "SMD-RES-13R-5%-1/4W(1206)"))
    )
    (comp (ref "R486")
      (value "13")
      (footprint "eagle-import:R1206")
      (fields (field (name "MPN") "RC1206JR-0713RL"))
      (libsource (lib "eagle-import") (part "SMD-RES-13R-5%-1/4W(1206)"))
    )
    (comp (ref "R487")
      (value "2702")
      (footprint "eagle-import:R0805")
      (fields (field (name "MPN") "RC0805JR-074K7L"))
      (libsource (lib "eagle-import") (part "SMD-RES-4.7K-5%-1/8W(0805)"))
    )
    (comp (ref "R488")
      (value "4701")
      (footprint "eagle-import:R0805")
      (fields (field (name "MPN") "RC0805JR-074K7L"))
      (libsource (lib "eagle-import") (part "SMD-RES-4.7K-5%-1/8W(0805)"))
    )
    (comp (ref "R489")
      (value "100")
      (footprint "eagle-import:R0805")
      (fields (field (name "MPN") "RC0805JR-072K2L"))
      (libsource (lib "eagle-import") (part "SMD-RES-2.2K-5%-1/8W(0805)"))
    )
    (comp (ref "R490")
      (value "(101)")
      (footprint "eagle-import:R0805")
      (fields (field (name "MPN") "RC0805JR-072K2L"))
      (libsource (lib "eagle-import") (part "SMD-RES-2.2K-5%-1/8W(0805)"))
    )
    (comp (ref "R491")
      (value "104")
      (footprint "eagle-import:R0805")
      (fields (field (name "MPN") "RC0805FR-0710KL"))
      (libsource (lib "eagle-import") (part "SMD-RES-10K-1%-1/8W(0805)"))
    )
    (comp (ref "R492")
      (value "104")
      (footprint "eagle-import:R0805")
      (fields (field (name "MPN") "RC0805FR-0710KL"))
      (libsource (lib "eagle-import") (part "SMD-RES-10K-1%-1/8W(0805)"))
    )
    (comp (ref "R493")
      (value "(1002)")
      (footprint "eagle-import:R0805")
      (fields (field (name "MPN") "RC0805FR-0710KL"))
      (libsource (lib "eagle-import") (part "SMD-RES-10K-1%-1/8W(0805)"))
    )
    (comp (ref "R494")
      (value "2702")
      (footprint "eagle-import:R0805")
      (fields (field (name "MPN") "RC0805FR-0710KL"))
      (libsource (lib "eagle-import") (part "SMD-RES-10K-1%-1/8W(0805)"))
    )
    (comp (ref "R495")
      (value "47")
      (footprint "eagle-import:V235_17_1MM")
      (libsource (lib "eagle-import") (part "R-EU_V235/17_1MM"))
    )
    (comp (ref "R496")
      (value "47")
      (footprint "eagle-import:V235_17_1MM")
      (libsource (lib "eagle-import") (part "R-EU_V235/17_1MM"))
    )
    (comp (ref "R497")
      (value "2702")
      (footprint "eagle-import:R0805")
      (fields (field (name "MPN") "RC0805JR-074K7L"))
      (libsource (lib "eagle-import") (part "SMD-RES-4.7K-5%-1/8W(0805)"))
    )
    (comp (ref "R498")
      (value "2201")
      (footprint "eagle-import:R0805")
      (fields (field (name "MPN") "RC0805JR-072K2L"))
      (libsource (lib "eagle-import") (part "SMD-RES-2.2K-5%-1/8W(0805)"))
    )
    (comp (ref "R499")
      (value "(1002)")
      (footprint "eagle-import:R0805")
      (fields (field (name "MPN") "RC0805JR-074K7L"))
      (libsource (lib "eagle-import") (part "SMD-RES-4.7K-5%-1/8W(0805)"))
    )
    (comp (ref "R500")
      (value "1002")
      (footprint "eagle-import:R0805")
      (fields (field (name "MPN") "RC0805FR-0710KL"))
      (libsource (lib "eagle-import") (part "SMD-RES-10K-1%-1/8W(0805)"))
    )
    (comp (ref "R501")
      (value "102")
      (footprint "eagle-import:R0805")
      (fields (field (name "MPN") "RC0805JR-071KL"))
      (libsource (lib "eagle-import") (part "SMD-RES-1K-5%-1/8W(0805)"))
    )
    (comp (ref "R502")
      (value "2702")
      (footprint "eagle-import:R0805")
      (fields (field (name "MPN") "RC0805JR-074K7L"))
      (libsource (lib "eagle-import") (part "SMD-RES-4.7K-5%-1/8W(0805)"))
    )
    (comp (ref "R503")
      (value "102")
      (footprint "eagle-import:R0805")
      (fields (field (name "MPN") "RC0805JR-071KL"))
      (libsource (lib "eagle-import") (part "SMD-RES-1K-5%-1/8W(0805)"))
    )
    (comp (ref "R504")
      (value "102")
      (footprint "eagle-import:R0805")
      (fields (field (name "MPN") "RC0805JR-071KL"))
      (libsource (lib "eagle-import") (part "SMD-RES-1K-5%-1/8W(0805)"))
    )
    (comp (ref "R505")
      (value "13")
      (footprint "eagle-import:R1206")
      (fields (field (name "MPN") "RC1206JR-0713RL"))
      (libsource (lib "eagle-import") (part "SMD-RES-13R-5%-1/4W(1206)"))
    )
    (comp (ref "R506")
      (value "R_user")
      (footprint "eagle-import:R0805")
      (libsource (lib "eagle-import") (part "R-EU_R0805"))
    )
    (comp (ref "SJ11")
      (value "SJ")
      (footprint "eagle-import:SJ")
      (libsource (lib "eagle-import") (part "SJ"))
    )
    (comp (ref "START10")
      (value "TPSB2.0")
      (footprint "eagle-import:B2.0")
      (libsource (lib "eagle-import") (part "TPSB2.0"))
    )
    (comp (ref "TP231")
      (value "TPSB2.0")
      (footprint "eagle-import:B2.0")
      (libsource (lib "eagle-import") (part "TPSB2.0"))
    )
    (comp (ref "TP232")
      (value "TPSB2.0")
      (footprint "eagle-import:B2.0")
      (libsource (lib "eagle-import") (part "TPSB2.0"))
    )
    (comp (ref "TP233")
      (value "TPSB2.0")
      (footprint "eagle-import:B2.0")
      (libsource (lib "eagle-import") (part "TPSB2.0"))
    )
    (comp (ref "TP234")
      (value "TPSB2.0")
      (footprint "eagle-import:B2.0")
      (libsource (lib "eagle-import") (part "TPSB2.0"))
    )
    (comp (ref "TP235")
      (value "TPSB2.0")
      (footprint "eagle-import:B2.0")
      (libsource (lib "eagle-import") (part "TPSB2.0"))
    )
    (comp (ref "TP236")
      (value "TPSB2.0")
      (footprint "eagle-import:B2.0")
      (libsource (lib "eagle-import") (part "TPSB2.0"))
    )
    (comp (ref "TP237")
      (value "TPSB2.0")
      (footprint "eagle-import:B2.0")
      (libsource (lib "eagle-import") (part "TPSB2.0"))
    )
    (comp (ref "TP238")
      (value "TPSB2.0")
      (footprint "eagle-import:B2.0")
      (libsource (lib "eagle-import") (part "TPSB2.0"))
    )
    (comp (ref "TP239")
      (value "TPSB2.0")
      (footprint "eagle-import:B2.0")
      (libsource (lib "eagle-import") (part "TPSB2.0"))
    )
    (comp (ref "TP240")
      (value "TPSB2.0")
      (footprint "eagle-import:B2.0")
      (libsource (lib "eagle-import") (part "TPSB2.0"))
    )
    (comp (ref "TP241")
      (value "TPSB2.0")
      (footprint "eagle-import:B2.0")
      (libsource (lib "eagle-import") (part "TPSB2.0"))
    )
    (comp (ref "TP242")
      (value "TPSB2.0")
      (footprint "eagle-import:B2.0")
      (libsource (lib "eagle-import") (part "TPSB2.0"))
    )
    (comp (ref "TP243")
      (value "TPSB2.0")
      (footprint "eagle-import:B2.0")
      (libsource (lib "eagle-import") (part "TPSB2.0"))
    )
    (comp (ref "TP244")
      (value "TPSB2.0")
      (footprint "eagle-import:B2.0")
      (libsource (lib "eagle-import") (part "TPSB2.0"))
    )
    (comp (ref "TP245")
      (value "TPSB2.0")
      (footprint "eagle-import:B2.0")
      (libsource (lib "eagle-import") (part "TPSB2.0"))
    )
    (comp (ref "TP246")
      (value "TPSB2.0")
      (footprint "eagle-import:B2.0")
      (libsource (lib "eagle-import") (part "TPSB2.0"))
    )
    (comp (ref "TP247")
      (value "TPSB2.0")
      (footprint "eagle-import:B2.0")
      (libsource (lib "eagle-import") (part "TPSB2.0"))
    )
    (comp (ref "TP248")
      (value "TPSB2.0")
      (footprint "eagle-import:B2.0")
      (libsource (lib "eagle-import") (part "TPSB2.0"))
    )
    (comp (ref "TP249")
      (value "TPSB1,27")
      (footprint "eagle-import:B1,27")
      (libsource (lib "eagle-import") (part "TPSB1,27"))
    )
    (comp (ref "TP250")
      (value "TPSB2.0")
      (footprint "eagle-import:B2.0")
      (libsource (lib "eagle-import") (part "TPSB2.0"))
    )
    (comp (ref "TP251")
      (value "TPSB2.0")
      (footprint "eagle-import:B2.0")
      (libsource (lib "eagle-import") (part "TPSB2.0"))
    )
    (comp (ref "TP252")
      (value "TPSB2.0")
      (footprint "eagle-import:B2.0")
      (libsource (lib "eagle-import") (part "TPSB2.0"))
    )
    (comp (ref "TP253")
      (value "TPSB2.0")
      (footprint "eagle-import:B2.0")
      (libsource (lib "eagle-import") (part "TPSB2.0"))
    )
    (comp (ref "X31")
      (value "CON_BMWV2")
      (footprint "eagle-import:24-PIN_V2")
      (libsource (lib "eagle-import") (part "CON_BMWV2"))
    )
    (comp (ref "X32")
      (value "22-23-2051")
      (footprint "eagle-import:22-23-2051")
      (fields (field (name "MF") "MOLEX"))
      (libsource (lib "eagle-import") (part "22-23-2051"))
    )
    (comp (ref "X33")
      (value "22-23-2021")
      (footprint "eagle-import:22-23-2021")
      (fields (field (name "MF") "MOLEX"))
      (libsource (lib "eagle-import") (part "22-23-2021"))
    )
    (comp (ref "6V9")
      (value "TPSB2.0")
      (footprint "eagle-import:B2.0")
      (libsource (lib "eagle-import") (part "TPSB2.0"))
    )
    (comp (ref "10V9")
      (value "TPSB2.0")
      (footprint "eagle-import:B2.0")
      (libsource (lib "eagle-import") (part "TPSB2.0"))
    )
    (comp (ref "19")
      (value "2081-1132")
      (footprint "eagle-import:12-PIN")
      (libsource (lib "eagle-import") (part "2081-1132"))
    )
    (comp (ref "20")
      (value "2081-1132")
      (footprint "eagle-import:12-PIN")
      (libsource (lib "eagle-import") (part "2081-1132"))
    )
    (comp (ref "C91")
      (value "100u")
      (footprint "eagle-import:C1206")
      (fields (field (name "MPN") "GRM31CR60J107ME39L"))
      (libsource (lib "eagle-import") (part "CERAMIC-100UF-6.3V-20%-X5R(1206)"))
    )
    (comp (ref "C92")
      (value "100u")
      (footprint "eagle-import:C1206")
      (fields (field (name "MPN") "GRM31CR60J107ME39L"))
      (libsource (lib "eagle-import") (part "CERAMIC-100UF-6.3V-20%-X5R(1206)"))
    )
    (comp (ref "C93")
      (value "100nF,")
      (footprint "eagle-import:C0805")
      (fields (field (name "MPN") "CC0805KRX7R9BB104"))
      (libsource (lib "eagle-import") (part "CERAMIC-100NF-50V-10%-X7R(0805)"))
    )
    (comp (ref "C94")
      (value "4.7u")
      (footprint "eagle-import:C0805")
      (fields (field (name "MPN") "CC0805KKX5R8BB475"))
      (libsource (lib "eagle-import") (part "CERAMIC-4.7UF-25V-10%-X5R(0805)"))
    )
    (comp (ref "C95")
      (value "100nF.")
      (footprint "eagle-import:C0805")
      (fields (field (name "MPN") "CC0805KRX7R9BB104"))
      (libsource (lib "eagle-import") (part "CERAMIC-100NF-50V-10%-X7R(0805)"))
    )
    (comp (ref "C96")
      (value "100nF.")
      (footprint "eagle-import:C0805")
      (fields (field (name "MPN") "CC0805KRX7R9BB104"))
      (libsource (lib "eagle-import") (part "CERAMIC-100NF-50V-10%-X7R(0805)"))
    )
    (comp (ref "C97")
      (value "2.2nF")
      (footprint "eagle-import:C0805")
      (fields (field (name "MPN") "CC0805KRX7R9BB104"))
      (libsource (lib "eagle-import") (part "CERAMIC-100NF-50V-10%-X7R(0805)"))
    )
    (comp (ref "C98")
      (value "100nF")
      (footprint "eagle-import:C0805")
      (fields (field (name "MPN") "CC0805KRX7R9BB104"))
      (libsource (lib "eagle-import") (part "CERAMIC-100NF-50V-10%-X7R(0805)"))
    )
    (comp (ref "C99")
      (value "100nF")
      (footprint "eagle-import:C0805")
      (fields (field (name "MPN") "CC0805KRX7R9BB104"))
      (libsource (lib "eagle-import") (part "CERAMIC-100NF-50V-10%-X7R(0805)"))
    )
    (comp (ref "C100")
      (value "100nF,")
      (footprint "eagle-import:C0805")
      (fields (field (name "MPN") "CC0805KRX7R9BB104"))
      (libsource (lib "eagle-import") (part "CERAMIC-100NF-50V-10%-X7R(0805)"))
    )
    (comp (ref "D109")
      (value "1N4007")
      (footprint "eagle-import:DO-214AC")
      (libsource (lib "eagle-import") (part "DIODE-GEN-PURPOSE-1KV-1A(DO-214AC)"))
    )
    (comp (ref "D110")
      (value "1N4007,")
      (footprint "eagle-import:DO-214AC")
      (fields (field (name "MPN") "1N4007"))
      (libsource (lib "eagle-import") (part "DIODE-GEN-PURPOSE-1KV-1A(DO-214AC)"))
    )
    (comp (ref "D111")
      (value "1N4007,")
      (footprint "eagle-import:DO-214AC")
      (fields (field (name "MPN") "1N4007"))
      (libsource (lib "eagle-import") (part "DIODE-GEN-PURPOSE-1KV-1A(DO-214AC)"))
    )
    (comp (ref "D112")
      (value "1N4007.")
      (footprint "eagle-import:DO-214AC")
      (fields (field (name "MPN") "1N4007"))
      (libsource (lib "eagle-import") (part "DIODE-GEN-PURPOSE-1KV-1A(DO-214AC)"))
    )
    (comp (ref "D113")
      (value "1N5817")
      (footprint "eagle-import:DO-214AC_SLIM")
      (libsource (lib "eagle-import") (part "DIODE-GEN-PURPOSE-1KV-1A(DO-214AC)DO-214AC/1206"))
    )
    (comp (ref "D114")
      (value "1N5817.")
      (footprint "eagle-import:DO-214AC_SLIM")
      (libsource (lib "eagle-import") (part "DIODE-GEN-PURPOSE-1KV-1A(DO-214AC)DO-214AC/1206"))
    )
    (comp (ref "D115")
      (value "1N5817.")
      (footprint "eagle-import:DO-214AC_SLIM")
      (libsource (lib "eagle-import") (part "DIODE-GEN-PURPOSE-1KV-1A(DO-214AC)DO-214AC/1206"))
    )
    (comp (ref "D116")
      (value "1N5817")
      (footprint "eagle-import:DO-214AC_SLIM")
      (libsource (lib "eagle-import") (part "DIODE-GEN-PURPOSE-1KV-1A(DO-214AC)DO-214AC/1206"))
    )
    (comp (ref "D117")
      (value "1N4007.")
      (footprint "eagle-import:DO-214AC")
      (fields (field (name "MPN") "1N4007"))
      (libsource (lib "eagle-import") (part "DIODE-GEN-PURPOSE-1KV-1A(DO-214AC)"))
    )
    (comp (ref "D118")
      (value "1N4007")
      (footprint "eagle-import:DO-214AC")
      (libsource (lib "eagle-import") (part "DIODE-GEN-PURPOSE-1KV-1A(DO-214AC)"))
    )
    (comp (ref "D119")
      (value "SM6T")
      (footprint "eagle-import:DO214AA")
      (libsource (lib "eagle-import") (part "SM6T"))
    )
    (comp (ref "D120")
      (value "SM6TDO214AA_BI")
      (footprint "eagle-import:DO214AA_BI")
      (libsource (lib "eagle-import") (part "SM6TDO214AA_BI"))
    )
    (comp (ref "FID37")
      (value "FIDUCIAL")
      (footprint "eagle-import:FIDUCIAL_1MM")
      (libsource (lib "eagle-import") (part "FIDUCIAL"))
    )
    (comp (ref "FID38")
      (value "FIDUCIAL")
      (footprint "eagle-import:FIDUCIAL_1MM")
      (libsource (lib "eagle-import") (part "FIDUCIAL"))
    )
    (comp (ref "FID39")
      (value "FIDUCIAL")
      (footprint "eagle-import:FIDUCIAL_1MM")
      (libsource (lib "eagle-import") (part "FIDUCIAL"))
    )
    (comp (ref "FID40")
      (value "FIDUCIAL")
      (footprint "eagle-import:FIDUCIAL_1MM")
      (libsource (lib "eagle-import") (part "FIDUCIAL"))
    )
    (comp (ref "IC100")
      (value "4028")
      (footprint "eagle-import:SO16")
      (libsource (lib "eagle-import") (part "4028D"))
    )
    (comp (ref "IC101")
      (value "6V pos")
      (footprint "eagle-import:78LXX")
      (libsource (lib "eagle-import") (part "v-reg_78LXX"))
    )
    (comp (ref "IC102")
      (value "317TO202H_NOHOLE")
      (footprint "eagle-import:TO220H_NOHOLE")
      (libsource (lib "eagle-import") (part "317TO202H_NOHOLE"))
    )
    (comp (ref "IC103")
      (value "ULN2004")
      (footprint "eagle-import:SO16")
      (libsource (lib "eagle-import") (part "ULN2004AD"))
    )
    (comp (ref "IC104")
      (value "LM339")
      (footprint "eagle-import:SO14")
      (libsource (lib "eagle-import") (part "LM339D"))
    )
    (comp (ref "IC105")
      (value "78L06")
      (footprint "eagle-import:SOT89_ROUND")
      (libsource (lib "eagle-import") (part "78LXXSOT89_ROUND"))
    )
    (comp (ref "IC106")
      (value "555")
      (footprint "eagle-import:SO08")
      (libsource (lib "eagle-import") (part "555DNE"))
    )
    (comp (ref "IC107")
      (value "4538")
      (footprint "eagle-import:SO16")
      (libsource (lib "eagle-import") (part "4538D"))
    )
    (comp (ref "IC108")
      (value "78L10")
      (footprint "eagle-import:SOT89_ROUND")
      (libsource (lib "eagle-import") (part "78LXXSOT89_ROUND"))
    )
    (comp (ref "IC109")
      (value "LM2904")
      (footprint "eagle-import:SO08")
      (libsource (lib "eagle-import") (part "LM358D"))
    )
    (comp (ref "JP46")
      (value "JP2EJP2_SMALLPADS")
      (footprint "eagle-import:JP2_SMALLPADS")
      (libsource (lib "eagle-import") (part "JP2EJP2_SMALLPADS"))
    )
    (comp (ref "JP47")
      (value "JP2E_ORIG")
      (footprint "eagle-import:JP2_ORIG_SMALLPADS")
      (libsource (lib "eagle-import") (part "JP2E_ORIG"))
    )
    (comp (ref "JP48")
      (value "JP2EJP2_SMALLPADS")
      (footprint "eagle-import:JP2_SMALLPADS")
      (libsource (lib "eagle-import") (part "JP2EJP2_SMALLPADS"))
    )
    (comp (ref "JP49")
      (value "JP2EJP2_SMALLPADS")
      (footprint "eagle-import:JP2_SMALLPADS")
      (libsource (lib "eagle-import") (part "JP2EJP2_SMALLPADS"))
    )
    (comp (ref "JP50")
      (value "JP2EJP2_SMALLPADS")
      (footprint "eagle-import:JP2_SMALLPADS")
      (libsource (lib "eagle-import") (part "JP2EJP2_SMALLPADS"))
    )
    (comp (ref "LED55")
      (value "LEDLD260")
      (footprint "eagle-import:LD260")
      (libsource (lib "eagle-import") (part "LEDLD260"))
    )
    (comp (ref "LED56")
      (value "LEDLD260")
      (footprint "eagle-import:LD260")
      (libsource (lib "eagle-import") (part "LEDLD260"))
    )
    (comp (ref "LED57")
      (value "LEDLD260")
      (footprint "eagle-import:LD260")
      (libsource (lib "eagle-import") (part "LEDLD260"))
    )
    (comp (ref "LED58")
      (value "LEDLD260")
      (footprint "eagle-import:LD260")
      (libsource (lib "eagle-import") (part "LEDLD260"))
    )
    (comp (ref "LED59")
      (value "LEDLD260")
      (footprint "eagle-import:LD260")
      (libsource (lib "eagle-import") (part "LEDLD260"))
    )
    (comp (ref "LED60")
      (value "LEDLD260")
      (footprint "eagle-import:LD260")
      (libsource (lib "eagle-import") (part "LEDLD260"))
    )
    (comp (ref "Q64")
      (value "BA")
      (footprint "eagle-import:SOT89")
      (libsource (lib "eagle-import") (part "PNP-TRANSISTOR_SOT89"))
    )
    (comp (ref "Q65")
      (value "BA.")
      (footprint "eagle-import:SOT89")
      (libsource (lib "eagle-import") (part "PNP-TRANSISTOR_SOT89"))
    )
    (comp (ref "Q66")
      (value "BA.")
      (footprint "eagle-import:SOT89")
      (libsource (lib "eagle-import") (part "PNP-TRANSISTOR_SOT89"))
    )
    (comp (ref "Q67")
      (value "BA")
      (footprint "eagle-import:SOT89")
      (libsource (lib "eagle-import") (part "PNP-TRANSISTOR_SOT89"))
    )
    (comp (ref "Q68")
      (value "MY")
      (footprint "eagle-import:SOT89")
      (libsource (lib "eagle-import") (part "NPN-TRANSISTOR_SOT89"))
    )
    (comp (ref "Q69")
      (value "J1")
      (footprint "eagle-import:SOT-23")
      (fields (field (name "MPN") "BSS138W-7-F"))
      (libsource (lib "eagle-import") (part "SMD-MOSFET-N-CH-50V-200MA-BSS138W-7-F(SOT-23)"))
    )
    (comp (ref "Q70")
      (value "J1")
      (footprint "eagle-import:SOT-23")
      (fields (field (name "MPN") "BSS138W-7-F"))
      (libsource (lib "eagle-import") (part "SMD-MOSFET-N-CH-50V-200MA-BSS138W-7-F(SOT-23)"))
    )
    (comp (ref "R415")
      (value "47")
      (footprint "eagle-import:V235_17_1MM")
      (libsource (lib "eagle-import") (part "R-EU_V235/17_1MM"))
    )
    (comp (ref "R416")
      (value "13")
      (footprint "eagle-import:R1206")
      (fields (field (name "MPN") "RC1206JR-0713RL"))
      (libsource (lib "eagle-import") (part "SMD-RES-13R-5%-1/4W(1206)"))
    )
    (comp (ref "R417")
      (value "47")
      (footprint "eagle-import:V235_17_1MM")
      (libsource (lib "eagle-import") (part "R-EU_V235/17_1MM"))
    )
    (comp (ref "R418")
      (value "104")
      (footprint "eagle-import:R0805")
      (fields (field (name "MPN") "RC0805FR-0710KL"))
      (libsource (lib "eagle-import") (part "SMD-RES-10K-1%-1/8W(0805)"))
    )
    (comp (ref "R419")
      (value "104")
      (footprint "eagle-import:R0805")
      (fields (field (name "MPN") "RC0805FR-0710KL"))
      (libsource (lib "eagle-import") (part "SMD-RES-10K-1%-1/8W(0805)"))
    )
    (comp (ref "R420")
      (value "104")
      (footprint "eagle-import:R0805")
      (fields (field (name "MPN") "RC0805FR-0710KL"))
      (libsource (lib "eagle-import") (part "SMD-RES-10K-1%-1/8W(0805)"))
    )
    (comp (ref "R421")
      (value "4701")
      (footprint "eagle-import:R0805")
      (fields (field (name "MPN") "RC0805JR-074K7L"))
      (libsource (lib "eagle-import") (part "SMD-RES-4.7K-5%-1/8W(0805)"))
    )
    (comp (ref "R422")
      (value "1002")
      (footprint "eagle-import:R0805")
      (fields (field (name "MPN") "RC0805FR-0710KL"))
      (libsource (lib "eagle-import") (part "SMD-RES-10K-1%-1/8W(0805)"))
    )
    (comp (ref "R423")
      (value "1002")
      (footprint "eagle-import:R0805")
      (fields (field (name "MPN") "RC0805FR-0710KL"))
      (libsource (lib "eagle-import") (part "SMD-RES-10K-1%-1/8W(0805)"))
    )
    (comp (ref "R424")
      (value "1502")
      (footprint "eagle-import:R0805")
      (fields (field (name "MPN") "RC0805FR-0710KL"))
      (libsource (lib "eagle-import") (part "SMD-RES-10K-1%-1/8W(0805)"))
    )
    (comp (ref "R425")
      (value "104")
      (footprint "eagle-import:R0805")
      (fields (field (name "MPN") "RC0805FR-0710KL"))
      (libsource (lib "eagle-import") (part "SMD-RES-10K-1%-1/8W(0805)"))
    )
    (comp (ref "R426")
      (value "104")
      (footprint "eagle-import:R0805")
      (fields (field (name "MPN") "RC0805FR-0710KL"))
      (libsource (lib "eagle-import") (part "SMD-RES-10K-1%-1/8W(0805)"))
    )
    (comp (ref "R427")
      (value "1502")
      (footprint "eagle-import:R0805")
      (fields (field (name "MPN") "RC0805FR-0710KL"))
      (libsource (lib "eagle-import") (part "SMD-RES-10K-1%-1/8W(0805)"))
    )
    (comp (ref "R428")
      (value "1002")
      (footprint "eagle-import:R0805")
      (fields (field (name "MPN") "RC0805FR-0710KL"))
      (libsource (lib "eagle-import") (part "SMD-RES-10K-1%-1/8W(0805)"))
    )
    (comp (ref "R429")
      (value "2201")
      (footprint "eagle-import:R0805")
      (fields (field (name "MPN") "RC0805JR-072K2L"))
      (libsource (lib "eagle-import") (part "SMD-RES-2.2K-5%-1/8W(0805)"))
    )
    (comp (ref "R430")
      (value "1002")
      (footprint "eagle-import:R0805")
      (fields (field (name "MPN") "RC0805FR-0710KL"))
      (libsource (lib "eagle-import") (part "SMD-RES-10K-1%-1/8W(0805)"))
    )
    (comp (ref "R431")
      (value "4701")
      (footprint "eagle-import:R0805")
      (fields (field (name "MPN") "RC0805JR-074K7L"))
      (libsource (lib "eagle-import") (part "SMD-RES-4.7K-5%-1/8W(0805)"))
    )
    (comp (ref "R432")
      (value "2702")
      (footprint "eagle-import:R0805")
      (fields (field (name "MPN") "RC0805JR-074K7L"))
      (libsource (lib "eagle-import") (part "SMD-RES-4.7K-5%-1/8W(0805)"))
    )
    (comp (ref "R433")
      (value "102")
      (footprint "eagle-import:R0805")
      (fields (field (name "MPN") "RC0805JR-071KL"))
      (libsource (lib "eagle-import") (part "SMD-RES-1K-5%-1/8W(0805)"))
    )
    (comp (ref "R434")
      (value "R_user")
      (footprint "eagle-import:R0805")
      (libsource (lib "eagle-import") (part "R-EU_R0805"))
    )
    (comp (ref "R435")
      (value "100")
      (footprint "eagle-import:R0805")
      (fields (field (name "MPN") "RC0805JR-07220RL"))
      (libsource (lib "eagle-import") (part "SMD-RES-220R-5%-1/8W(0805)"))
    )
    (comp (ref "R436")
      (value "(101)")
      (footprint "eagle-import:R0805")
      (fields (field (name "MPN") "RC0805JR-07100RL"))
      (libsource (lib "eagle-import") (part "SMD-RES-100R-5%-1/8W(0805)"))
    )
    (comp (ref "R437")
      (value "(1000)")
      (footprint "eagle-import:R0805")
      (fields (field (name "MPN") "RC0805JR-07100RL"))
      (libsource (lib "eagle-import") (part "SMD-RES-100R-5%-1/8W(0805)"))
    )
    (comp (ref "R438")
      (value "102")
      (footprint "eagle-import:R0805")
      (fields (field (name "MPN") "RC0805JR-071KL"))
      (libsource (lib "eagle-import") (part "SMD-RES-1K-5%-1/8W(0805)"))
    )
    (comp (ref "R439")
      (value "13")
      (footprint "eagle-import:R1206")
      (fields (field (name "MPN") "RC1206JR-0713RL"))
      (libsource (lib "eagle-import") (part "SMD-RES-13R-5%-1/4W(1206)"))
    )
    (comp (ref "R440")
      (value "13")
      (footprint "eagle-import:R1206")
      (fields (field (name "MPN") "RC1206JR-0713RL"))
      (libsource (lib "eagle-import") (part "SMD-RES-13R-5%-1/4W(1206)"))
    )
    (comp (ref "R441")
      (value "2702")
      (footprint "eagle-import:R0805")
      (fields (field (name "MPN") "RC0805JR-074K7L"))
      (libsource (lib "eagle-import") (part "SMD-RES-4.7K-5%-1/8W(0805)"))
    )
    (comp (ref "R442")
      (value "4701")
      (footprint "eagle-import:R0805")
      (fields (field (name "MPN") "RC0805JR-074K7L"))
      (libsource (lib "eagle-import") (part "SMD-RES-4.7K-5%-1/8W(0805)"))
    )
    (comp (ref "R443")
      (value "100")
      (footprint "eagle-import:R0805")
      (fields (field (name "MPN") "RC0805JR-072K2L"))
      (libsource (lib "eagle-import") (part "SMD-RES-2.2K-5%-1/8W(0805)"))
    )
    (comp (ref "R444")
      (value "(101)")
      (footprint "eagle-import:R0805")
      (fields (field (name "MPN") "RC0805JR-072K2L"))
      (libsource (lib "eagle-import") (part "SMD-RES-2.2K-5%-1/8W(0805)"))
    )
    (comp (ref "R445")
      (value "104")
      (footprint "eagle-import:R0805")
      (fields (field (name "MPN") "RC0805FR-0710KL"))
      (libsource (lib "eagle-import") (part "SMD-RES-10K-1%-1/8W(0805)"))
    )
    (comp (ref "R446")
      (value "104")
      (footprint "eagle-import:R0805")
      (fields (field (name "MPN") "RC0805FR-0710KL"))
      (libsource (lib "eagle-import") (part "SMD-RES-10K-1%-1/8W(0805)"))
    )
    (comp (ref "R447")
      (value "(1002)")
      (footprint "eagle-import:R0805")
      (fields (field (name "MPN") "RC0805FR-0710KL"))
      (libsource (lib "eagle-import") (part "SMD-RES-10K-1%-1/8W(0805)"))
    )
    (comp (ref "R448")
      (value "2702")
      (footprint "eagle-import:R0805")
      (fields (field (name "MPN") "RC0805FR-0710KL"))
      (libsource (lib "eagle-import") (part "SMD-RES-10K-1%-1/8W(0805)"))
    )
    (comp (ref "R449")
      (value "47")
      (footprint "eagle-import:V235_17_1MM")
      (libsource (lib "eagle-import") (part "R-EU_V235/17_1MM"))
    )
    (comp (ref "R450")
      (value "47")
      (footprint "eagle-import:V235_17_1MM")
      (libsource (lib "eagle-import") (part "R-EU_V235/17_1MM"))
    )
    (comp (ref "R451")
      (value "2702")
      (footprint "eagle-import:R0805")
      (fields (field (name "MPN") "RC0805JR-074K7L"))
      (libsource (lib "eagle-import") (part "SMD-RES-4.7K-5%-1/8W(0805)"))
    )
    (comp (ref "R452")
      (value "2201")
      (footprint "eagle-import:R0805")
      (fields (field (name "MPN") "RC0805JR-072K2L"))
      (libsource (lib "eagle-import") (part "SMD-RES-2.2K-5%-1/8W(0805)"))
    )
    (comp (ref "R453")
      (value "(1002)")
      (footprint "eagle-import:R0805")
      (fields (field (name "MPN") "RC0805JR-074K7L"))
      (libsource (lib "eagle-import") (part "SMD-RES-4.7K-5%-1/8W(0805)"))
    )
    (comp (ref "R454")
      (value "1002")
      (footprint "eagle-import:R0805")
      (fields (field (name "MPN") "RC0805FR-0710KL"))
      (libsource (lib "eagle-import") (part "SMD-RES-10K-1%-1/8W(0805)"))
    )
    (comp (ref "R455")
      (value "102")
      (footprint "eagle-import:R0805")
      (fields (field (name "MPN") "RC0805JR-071KL"))
      (libsource (lib "eagle-import") (part "SMD-RES-1K-5%-1/8W(0805)"))
    )
    (comp (ref "R456")
      (value "2702")
      (footprint "eagle-import:R0805")
      (fields (field (name "MPN") "RC0805JR-074K7L"))
      (libsource (lib "eagle-import") (part "SMD-RES-4.7K-5%-1/8W(0805)"))
    )
    (comp (ref "R457")
      (value "102")
      (footprint "eagle-import:R0805")
      (fields (field (name "MPN") "RC0805JR-071KL"))
      (libsource (lib "eagle-import") (part "SMD-RES-1K-5%-1/8W(0805)"))
    )
    (comp (ref "R458")
      (value "102")
      (footprint "eagle-import:R0805")
      (fields (field (name "MPN") "RC0805JR-071KL"))
      (libsource (lib "eagle-import") (part "SMD-RES-1K-5%-1/8W(0805)"))
    )
    (comp (ref "R459")
      (value "13")
      (footprint "eagle-import:R1206")
      (fields (field (name "MPN") "RC1206JR-0713RL"))
      (libsource (lib "eagle-import") (part "SMD-RES-13R-5%-1/4W(1206)"))
    )
    (comp (ref "R460")
      (value "R_user")
      (footprint "eagle-import:R0805")
      (libsource (lib "eagle-import") (part "R-EU_R0805"))
    )
    (comp (ref "SJ10")
      (value "SJ")
      (footprint "eagle-import:SJ")
      (libsource (lib "eagle-import") (part "SJ"))
    )
    (comp (ref "START9")
      (value "TPSB2.0")
      (footprint "eagle-import:B2.0")
      (libsource (lib "eagle-import") (part "TPSB2.0"))
    )
    (comp (ref "TP208")
      (value "TPSB2.0")
      (footprint "eagle-import:B2.0")
      (libsource (lib "eagle-import") (part "TPSB2.0"))
    )
    (comp (ref "TP209")
      (value "TPSB2.0")
      (footprint "eagle-import:B2.0")
      (libsource (lib "eagle-import") (part "TPSB2.0"))
    )
    (comp (ref "TP210")
      (value "TPSB2.0")
      (footprint "eagle-import:B2.0")
      (libsource (lib "eagle-import") (part "TPSB2.0"))
    )
    (comp (ref "TP211")
      (value "TPSB2.0")
      (footprint "eagle-import:B2.0")
      (libsource (lib "eagle-import") (part "TPSB2.0"))
    )
    (comp (ref "TP212")
      (value "TPSB2.0")
      (footprint "eagle-import:B2.0")
      (libsource (lib "eagle-import") (part "TPSB2.0"))
    )
    (comp (ref "TP213")
      (value "TPSB2.0")
      (footprint "eagle-import:B2.0")
      (libsource (lib "eagle-import") (part "TPSB2.0"))
    )
    (comp (ref "TP214")
      (value "TPSB2.0")
      (footprint "eagle-import:B2.0")
      (libsource (lib "eagle-import") (part "TPSB2.0"))
    )
    (comp (ref "TP215")
      (value "TPSB2.0")
      (footprint "eagle-import:B2.0")
      (libsource (lib "eagle-import") (part "TPSB2.0"))
    )
    (comp (ref "TP216")
      (value "TPSB2.0")
      (footprint "eagle-import:B2.0")
      (libsource (lib "eagle-import") (part "TPSB2.0"))
    )
    (comp (ref "TP217")
      (value "TPSB2.0")
      (footprint "eagle-import:B2.0")
      (libsource (lib "eagle-import") (part "TPSB2.0"))
    )
    (comp (ref "TP218")
      (value "TPSB2.0")
      (footprint "eagle-import:B2.0")
      (libsource (lib "eagle-import") (part "TPSB2.0"))
    )
    (comp (ref "TP219")
      (value "TPSB2.0")
      (footprint "eagle-import:B2.0")
      (libsource (lib "eagle-import") (part "TPSB2.0"))
    )
    (comp (ref "TP220")
      (value "TPSB2.0")
      (footprint "eagle-import:B2.0")
      (libsource (lib "eagle-import") (part "TPSB2.0"))
    )
    (comp (ref "TP221")
      (value "TPSB2.0")
      (footprint "eagle-import:B2.0")
      (libsource (lib "eagle-import") (part "TPSB2.0"))
    )
    (comp (ref "TP222")
      (value "TPSB2.0")
      (footprint "eagle-import:B2.0")
      (libsource (lib "eagle-import") (part "TPSB2.0"))
    )
    (comp (ref "TP223")
      (value "TPSB2.0")
      (footprint "eagle-import:B2.0")
      (libsource (lib "eagle-import") (part "TPSB2.0"))
    )
    (comp (ref "TP224")
      (value "TPSB2.0")
      (footprint "eagle-import:B2.0")
      (libsource (lib "eagle-import") (part "TPSB2.0"))
    )
    (comp (ref "TP225")
      (value "TPSB2.0")
      (footprint "eagle-import:B2.0")
      (libsource (lib "eagle-import") (part "TPSB2.0"))
    )
    (comp (ref "TP226")
      (value "TPSB1,27")
      (footprint "eagle-import:B1,27")
      (libsource (lib "eagle-import") (part "TPSB1,27"))
    )
    (comp (ref "TP227")
      (value "TPSB2.0")
      (footprint "eagle-import:B2.0")
      (libsource (lib "eagle-import") (part "TPSB2.0"))
    )
    (comp (ref "TP228")
      (value "TPSB2.0")
      (footprint "eagle-import:B2.0")
      (libsource (lib "eagle-import") (part "TPSB2.0"))
    )
    (comp (ref "TP229")
      (value "TPSB2.0")
      (footprint "eagle-import:B2.0")
      (libsource (lib "eagle-import") (part "TPSB2.0"))
    )
    (comp (ref "TP230")
      (value "TPSB2.0")
      (footprint "eagle-import:B2.0")
      (libsource (lib "eagle-import") (part "TPSB2.0"))
    )
    (comp (ref "X28")
      (value "CON_BMWV2")
      (footprint "eagle-import:24-PIN_V2")
      (libsource (lib "eagle-import") (part "CON_BMWV2"))
    )
    (comp (ref "X29")
      (value "22-23-2051")
      (footprint "eagle-import:22-23-2051")
      (fields (field (name "MF") "MOLEX"))
      (libsource (lib "eagle-import") (part "22-23-2051"))
    )
    (comp (ref "X30")
      (value "22-23-2021")
      (footprint "eagle-import:22-23-2021")
      (fields (field (name "MF") "MOLEX"))
      (libsource (lib "eagle-import") (part "22-23-2021"))
    )
    (comp (ref "6V5")
      (value "TPSB2.0")
      (footprint "eagle-import:B2.0")
      (libsource (lib "eagle-import") (part "TPSB2.0"))
    )
    (comp (ref "10V5")
      (value "TPSB2.0")
      (footprint "eagle-import:B2.0")
      (libsource (lib "eagle-import") (part "TPSB2.0"))
    )
    (comp (ref "11")
      (value "2081-1132")
      (footprint "eagle-import:12-PIN")
      (libsource (lib "eagle-import") (part "2081-1132"))
    )
    (comp (ref "12")
      (value "2081-1132")
      (footprint "eagle-import:12-PIN")
      (libsource (lib "eagle-import") (part "2081-1132"))
    )
    (comp (ref "C51")
      (value "100u")
      (footprint "eagle-import:C1206")
      (fields (field (name "MPN") "GRM31CR60J107ME39L"))
      (libsource (lib "eagle-import") (part "CERAMIC-100UF-6.3V-20%-X5R(1206)"))
    )
    (comp (ref "C52")
      (value "100u")
      (footprint "eagle-import:C1206")
      (fields (field (name "MPN") "GRM31CR60J107ME39L"))
      (libsource (lib "eagle-import") (part "CERAMIC-100UF-6.3V-20%-X5R(1206)"))
    )
    (comp (ref "C53")
      (value "100nF,")
      (footprint "eagle-import:C0805")
      (fields (field (name "MPN") "CC0805KRX7R9BB104"))
      (libsource (lib "eagle-import") (part "CERAMIC-100NF-50V-10%-X7R(0805)"))
    )
    (comp (ref "C54")
      (value "4.7u")
      (footprint "eagle-import:C0805")
      (fields (field (name "MPN") "CC0805KKX5R8BB475"))
      (libsource (lib "eagle-import") (part "CERAMIC-4.7UF-25V-10%-X5R(0805)"))
    )
    (comp (ref "C55")
      (value "100nF.")
      (footprint "eagle-import:C0805")
      (fields (field (name "MPN") "CC0805KRX7R9BB104"))
      (libsource (lib "eagle-import") (part "CERAMIC-100NF-50V-10%-X7R(0805)"))
    )
    (comp (ref "C56")
      (value "100nF.")
      (footprint "eagle-import:C0805")
      (fields (field (name "MPN") "CC0805KRX7R9BB104"))
      (libsource (lib "eagle-import") (part "CERAMIC-100NF-50V-10%-X7R(0805)"))
    )
    (comp (ref "C57")
      (value "2.2nF")
      (footprint "eagle-import:C0805")
      (fields (field (name "MPN") "CC0805KRX7R9BB104"))
      (libsource (lib "eagle-import") (part "CERAMIC-100NF-50V-10%-X7R(0805)"))
    )
    (comp (ref "C58")
      (value "100nF")
      (footprint "eagle-import:C0805")
      (fields (field (name "MPN") "CC0805KRX7R9BB104"))
      (libsource (lib "eagle-import") (part "CERAMIC-100NF-50V-10%-X7R(0805)"))
    )
    (comp (ref "C59")
      (value "100nF")
      (footprint "eagle-import:C0805")
      (fields (field (name "MPN") "CC0805KRX7R9BB104"))
      (libsource (lib "eagle-import") (part "CERAMIC-100NF-50V-10%-X7R(0805)"))
    )
    (comp (ref "C60")
      (value "100nF,")
      (footprint "eagle-import:C0805")
      (fields (field (name "MPN") "CC0805KRX7R9BB104"))
      (libsource (lib "eagle-import") (part "CERAMIC-100NF-50V-10%-X7R(0805)"))
    )
    (comp (ref "D61")
      (value "1N4007")
      (footprint "eagle-import:DO-214AC")
      (libsource (lib "eagle-import") (part "DIODE-GEN-PURPOSE-1KV-1A(DO-214AC)"))
    )
    (comp (ref "D62")
      (value "1N4007,")
      (footprint "eagle-import:DO-214AC")
      (fields (field (name "MPN") "1N4007"))
      (libsource (lib "eagle-import") (part "DIODE-GEN-PURPOSE-1KV-1A(DO-214AC)"))
    )
    (comp (ref "D63")
      (value "1N4007,")
      (footprint "eagle-import:DO-214AC")
      (fields (field (name "MPN") "1N4007"))
      (libsource (lib "eagle-import") (part "DIODE-GEN-PURPOSE-1KV-1A(DO-214AC)"))
    )
    (comp (ref "D64")
      (value "1N4007.")
      (footprint "eagle-import:DO-214AC")
      (fields (field (name "MPN") "1N4007"))
      (libsource (lib "eagle-import") (part "DIODE-GEN-PURPOSE-1KV-1A(DO-214AC)"))
    )
    (comp (ref "D65")
      (value "1N5817")
      (footprint "eagle-import:DO-214AC_SLIM")
      (libsource (lib "eagle-import") (part "DIODE-GEN-PURPOSE-1KV-1A(DO-214AC)DO-214AC/1206"))
    )
    (comp (ref "D66")
      (value "1N5817.")
      (footprint "eagle-import:DO-214AC_SLIM")
      (libsource (lib "eagle-import") (part "DIODE-GEN-PURPOSE-1KV-1A(DO-214AC)DO-214AC/1206"))
    )
    (comp (ref "D67")
      (value "1N5817.")
      (footprint "eagle-import:DO-214AC_SLIM")
      (libsource (lib "eagle-import") (part "DIODE-GEN-PURPOSE-1KV-1A(DO-214AC)DO-214AC/1206"))
    )
    (comp (ref "D68")
      (value "1N5817")
      (footprint "eagle-import:DO-214AC_SLIM")
      (libsource (lib "eagle-import") (part "DIODE-GEN-PURPOSE-1KV-1A(DO-214AC)DO-214AC/1206"))
    )
    (comp (ref "D69")
      (value "1N4007.")
      (footprint "eagle-import:DO-214AC")
      (fields (field (name "MPN") "1N4007"))
      (libsource (lib "eagle-import") (part "DIODE-GEN-PURPOSE-1KV-1A(DO-214AC)"))
    )
    (comp (ref "D70")
      (value "1N4007")
      (footprint "eagle-import:DO-214AC")
      (libsource (lib "eagle-import") (part "DIODE-GEN-PURPOSE-1KV-1A(DO-214AC)"))
    )
    (comp (ref "D71")
      (value "SM6T")
      (footprint "eagle-import:DO214AA")
      (libsource (lib "eagle-import") (part "SM6T"))
    )
    (comp (ref "D72")
      (value "SM6TDO214AA_BI")
      (footprint "eagle-import:DO214AA_BI")
      (libsource (lib "eagle-import") (part "SM6TDO214AA_BI"))
    )
    (comp (ref "FID21")
      (value "FIDUCIAL")
      (footprint "eagle-import:FIDUCIAL_1MM")
      (libsource (lib "eagle-import") (part "FIDUCIAL"))
    )
    (comp (ref "FID22")
      (value "FIDUCIAL")
      (footprint "eagle-import:FIDUCIAL_1MM")
      (libsource (lib "eagle-import") (part "FIDUCIAL"))
    )
    (comp (ref "FID23")
      (value "FIDUCIAL")
      (footprint "eagle-import:FIDUCIAL_1MM")
      (libsource (lib "eagle-import") (part "FIDUCIAL"))
    )
    (comp (ref "FID24")
      (value "FIDUCIAL")
      (footprint "eagle-import:FIDUCIAL_1MM")
      (libsource (lib "eagle-import") (part "FIDUCIAL"))
    )
    (comp (ref "IC56")
      (value "4028")
      (footprint "eagle-import:SO16")
      (libsource (lib "eagle-import") (part "4028D"))
    )
    (comp (ref "IC57")
      (value "6V pos")
      (footprint "eagle-import:78LXX")
      (libsource (lib "eagle-import") (part "v-reg_78LXX"))
    )
    (comp (ref "IC58")
      (value "317TO202H_NOHOLE")
      (footprint "eagle-import:TO220H_NOHOLE")
      (libsource (lib "eagle-import") (part "317TO202H_NOHOLE"))
    )
    (comp (ref "IC59")
      (value "ULN2004")
      (footprint "eagle-import:SO16")
      (libsource (lib "eagle-import") (part "ULN2004AD"))
    )
    (comp (ref "IC60")
      (value "LM339")
      (footprint "eagle-import:SO14")
      (libsource (lib "eagle-import") (part "LM339D"))
    )
    (comp (ref "IC61")
      (value "78L06")
      (footprint "eagle-import:SOT89_ROUND")
      (libsource (lib "eagle-import") (part "78LXXSOT89_ROUND"))
    )
    (comp (ref "IC62")
      (value "555")
      (footprint "eagle-import:SO08")
      (libsource (lib "eagle-import") (part "555DNE"))
    )
    (comp (ref "IC63")
      (value "4538")
      (footprint "eagle-import:SO16")
      (libsource (lib "eagle-import") (part "4538D"))
    )
    (comp (ref "IC64")
      (value "78L10")
      (footprint "eagle-import:SOT89_ROUND")
      (libsource (lib "eagle-import") (part "78LXXSOT89_ROUND"))
    )
    (comp (ref "IC65")
      (value "LM2904")
      (footprint "eagle-import:SO08")
      (libsource (lib "eagle-import") (part "LM358D"))
    )
    (comp (ref "JP26")
      (value "JP2EJP2_SMALLPADS")
      (footprint "eagle-import:JP2_SMALLPADS")
      (libsource (lib "eagle-import") (part "JP2EJP2_SMALLPADS"))
    )
    (comp (ref "JP27")
      (value "JP2E_ORIG")
      (footprint "eagle-import:JP2_ORIG_SMALLPADS")
      (libsource (lib "eagle-import") (part "JP2E_ORIG"))
    )
    (comp (ref "JP28")
      (value "JP2EJP2_SMALLPADS")
      (footprint "eagle-import:JP2_SMALLPADS")
      (libsource (lib "eagle-import") (part "JP2EJP2_SMALLPADS"))
    )
    (comp (ref "JP29")
      (value "JP2EJP2_SMALLPADS")
      (footprint "eagle-import:JP2_SMALLPADS")
      (libsource (lib "eagle-import") (part "JP2EJP2_SMALLPADS"))
    )
    (comp (ref "JP30")
      (value "JP2EJP2_SMALLPADS")
      (footprint "eagle-import:JP2_SMALLPADS")
      (libsource (lib "eagle-import") (part "JP2EJP2_SMALLPADS"))
    )
    (comp (ref "LED31")
      (value "LEDLD260")
      (footprint "eagle-import:LD260")
      (libsource (lib "eagle-import") (part "LEDLD260"))
    )
    (comp (ref "LED32")
      (value "LEDLD260")
      (footprint "eagle-import:LD260")
      (libsource (lib "eagle-import") (part "LEDLD260"))
    )
    (comp (ref "LED33")
      (value "LEDLD260")
      (footprint "eagle-import:LD260")
      (libsource (lib "eagle-import") (part "LEDLD260"))
    )
    (comp (ref "LED34")
      (value "LEDLD260")
      (footprint "eagle-import:LD260")
      (libsource (lib "eagle-import") (part "LEDLD260"))
    )
    (comp (ref "LED35")
      (value "LEDLD260")
      (footprint "eagle-import:LD260")
      (libsource (lib "eagle-import") (part "LEDLD260"))
    )
    (comp (ref "LED36")
      (value "LEDLD260")
      (footprint "eagle-import:LD260")
      (libsource (lib "eagle-import") (part "LEDLD260"))
    )
    (comp (ref "Q36")
      (value "BA")
      (footprint "eagle-import:SOT89")
      (libsource (lib "eagle-import") (part "PNP-TRANSISTOR_SOT89"))
    )
    (comp (ref "Q37")
      (value "BA.")
      (footprint "eagle-import:SOT89")
      (libsource (lib "eagle-import") (part "PNP-TRANSISTOR_SOT89"))
    )
    (comp (ref "Q38")
      (value "BA.")
      (footprint "eagle-import:SOT89")
      (libsource (lib "eagle-import") (part "PNP-TRANSISTOR_SOT89"))
    )
    (comp (ref "Q39")
      (value "BA")
      (footprint "eagle-import:SOT89")
      (libsource (lib "eagle-import") (part "PNP-TRANSISTOR_SOT89"))
    )
    (comp (ref "Q40")
      (value "MY")
      (footprint "eagle-import:SOT89")
      (libsource (lib "eagle-import") (part "NPN-TRANSISTOR_SOT89"))
    )
    (comp (ref "Q41")
      (value "J1")
      (footprint "eagle-import:SOT-23")
      (fields (field (name "MPN") "BSS138W-7-F"))
      (libsource (lib "eagle-import") (part "SMD-MOSFET-N-CH-50V-200MA-BSS138W-7-F(SOT-23)"))
    )
    (comp (ref "Q42")
      (value "J1")
      (footprint "eagle-import:SOT-23")
      (fields (field (name "MPN") "BSS138W-7-F"))
      (libsource (lib "eagle-import") (part "SMD-MOSFET-N-CH-50V-200MA-BSS138W-7-F(SOT-23)"))
    )
    (comp (ref "R231")
      (value "47")
      (footprint "eagle-import:V235_17_1MM")
      (libsource (lib "eagle-import") (part "R-EU_V235/17_1MM"))
    )
    (comp (ref "R232")
      (value "13")
      (footprint "eagle-import:R1206")
      (fields (field (name "MPN") "RC1206JR-0713RL"))
      (libsource (lib "eagle-import") (part "SMD-RES-13R-5%-1/4W(1206)"))
    )
    (comp (ref "R233")
      (value "47")
      (footprint "eagle-import:V235_17_1MM")
      (libsource (lib "eagle-import") (part "R-EU_V235/17_1MM"))
    )
    (comp (ref "R234")
      (value "104")
      (footprint "eagle-import:R0805")
      (fields (field (name "MPN") "RC0805FR-0710KL"))
      (libsource (lib "eagle-import") (part "SMD-RES-10K-1%-1/8W(0805)"))
    )
    (comp (ref "R235")
      (value "104")
      (footprint "eagle-import:R0805")
      (fields (field (name "MPN") "RC0805FR-0710KL"))
      (libsource (lib "eagle-import") (part "SMD-RES-10K-1%-1/8W(0805)"))
    )
    (comp (ref "R236")
      (value "104")
      (footprint "eagle-import:R0805")
      (fields (field (name "MPN") "RC0805FR-0710KL"))
      (libsource (lib "eagle-import") (part "SMD-RES-10K-1%-1/8W(0805)"))
    )
    (comp (ref "R237")
      (value "4701")
      (footprint "eagle-import:R0805")
      (fields (field (name "MPN") "RC0805JR-074K7L"))
      (libsource (lib "eagle-import") (part "SMD-RES-4.7K-5%-1/8W(0805)"))
    )
    (comp (ref "R238")
      (value "1002")
      (footprint "eagle-import:R0805")
      (fields (field (name "MPN") "RC0805FR-0710KL"))
      (libsource (lib "eagle-import") (part "SMD-RES-10K-1%-1/8W(0805)"))
    )
    (comp (ref "R239")
      (value "1002")
      (footprint "eagle-import:R0805")
      (fields (field (name "MPN") "RC0805FR-0710KL"))
      (libsource (lib "eagle-import") (part "SMD-RES-10K-1%-1/8W(0805)"))
    )
    (comp (ref "R240")
      (value "1502")
      (footprint "eagle-import:R0805")
      (fields (field (name "MPN") "RC0805FR-0710KL"))
      (libsource (lib "eagle-import") (part "SMD-RES-10K-1%-1/8W(0805)"))
    )
    (comp (ref "R241")
      (value "104")
      (footprint "eagle-import:R0805")
      (fields (field (name "MPN") "RC0805FR-0710KL"))
      (libsource (lib "eagle-import") (part "SMD-RES-10K-1%-1/8W(0805)"))
    )
    (comp (ref "R242")
      (value "104")
      (footprint "eagle-import:R0805")
      (fields (field (name "MPN") "RC0805FR-0710KL"))
      (libsource (lib "eagle-import") (part "SMD-RES-10K-1%-1/8W(0805)"))
    )
    (comp (ref "R243")
      (value "1502")
      (footprint "eagle-import:R0805")
      (fields (field (name "MPN") "RC0805FR-0710KL"))
      (libsource (lib "eagle-import") (part "SMD-RES-10K-1%-1/8W(0805)"))
    )
    (comp (ref "R244")
      (value "1002")
      (footprint "eagle-import:R0805")
      (fields (field (name "MPN") "RC0805FR-0710KL"))
      (libsource (lib "eagle-import") (part "SMD-RES-10K-1%-1/8W(0805)"))
    )
    (comp (ref "R245")
      (value "2201")
      (footprint "eagle-import:R0805")
      (fields (field (name "MPN") "RC0805JR-072K2L"))
      (libsource (lib "eagle-import") (part "SMD-RES-2.2K-5%-1/8W(0805)"))
    )
    (comp (ref "R246")
      (value "1002")
      (footprint "eagle-import:R0805")
      (fields (field (name "MPN") "RC0805FR-0710KL"))
      (libsource (lib "eagle-import") (part "SMD-RES-10K-1%-1/8W(0805)"))
    )
    (comp (ref "R247")
      (value "4701")
      (footprint "eagle-import:R0805")
      (fields (field (name "MPN") "RC0805JR-074K7L"))
      (libsource (lib "eagle-import") (part "SMD-RES-4.7K-5%-1/8W(0805)"))
    )
    (comp (ref "R248")
      (value "2702")
      (footprint "eagle-import:R0805")
      (fields (field (name "MPN") "RC0805JR-074K7L"))
      (libsource (lib "eagle-import") (part "SMD-RES-4.7K-5%-1/8W(0805)"))
    )
    (comp (ref "R249")
      (value "102")
      (footprint "eagle-import:R0805")
      (fields (field (name "MPN") "RC0805JR-071KL"))
      (libsource (lib "eagle-import") (part "SMD-RES-1K-5%-1/8W(0805)"))
    )
    (comp (ref "R250")
      (value "R_user")
      (footprint "eagle-import:R0805")
      (libsource (lib "eagle-import") (part "R-EU_R0805"))
    )
    (comp (ref "R251")
      (value "100")
      (footprint "eagle-import:R0805")
      (fields (field (name "MPN") "RC0805JR-07220RL"))
      (libsource (lib "eagle-import") (part "SMD-RES-220R-5%-1/8W(0805)"))
    )
    (comp (ref "R252")
      (value "(101)")
      (footprint "eagle-import:R0805")
      (fields (field (name "MPN") "RC0805JR-07100RL"))
      (libsource (lib "eagle-import") (part "SMD-RES-100R-5%-1/8W(0805)"))
    )
    (comp (ref "R253")
      (value "(1000)")
      (footprint "eagle-import:R0805")
      (fields (field (name "MPN") "RC0805JR-07100RL"))
      (libsource (lib "eagle-import") (part "SMD-RES-100R-5%-1/8W(0805)"))
    )
    (comp (ref "R254")
      (value "102")
      (footprint "eagle-import:R0805")
      (fields (field (name "MPN") "RC0805JR-071KL"))
      (libsource (lib "eagle-import") (part "SMD-RES-1K-5%-1/8W(0805)"))
    )
    (comp (ref "R255")
      (value "13")
      (footprint "eagle-import:R1206")
      (fields (field (name "MPN") "RC1206JR-0713RL"))
      (libsource (lib "eagle-import") (part "SMD-RES-13R-5%-1/4W(1206)"))
    )
    (comp (ref "R256")
      (value "13")
      (footprint "eagle-import:R1206")
      (fields (field (name "MPN") "RC1206JR-0713RL"))
      (libsource (lib "eagle-import") (part "SMD-RES-13R-5%-1/4W(1206)"))
    )
    (comp (ref "R257")
      (value "2702")
      (footprint "eagle-import:R0805")
      (fields (field (name "MPN") "RC0805JR-074K7L"))
      (libsource (lib "eagle-import") (part "SMD-RES-4.7K-5%-1/8W(0805)"))
    )
    (comp (ref "R258")
      (value "4701")
      (footprint "eagle-import:R0805")
      (fields (field (name "MPN") "RC0805JR-074K7L"))
      (libsource (lib "eagle-import") (part "SMD-RES-4.7K-5%-1/8W(0805)"))
    )
    (comp (ref "R259")
      (value "100")
      (footprint "eagle-import:R0805")
      (fields (field (name "MPN") "RC0805JR-072K2L"))
      (libsource (lib "eagle-import") (part "SMD-RES-2.2K-5%-1/8W(0805)"))
    )
    (comp (ref "R260")
      (value "(101)")
      (footprint "eagle-import:R0805")
      (fields (field (name "MPN") "RC0805JR-072K2L"))
      (libsource (lib "eagle-import") (part "SMD-RES-2.2K-5%-1/8W(0805)"))
    )
    (comp (ref "R261")
      (value "104")
      (footprint "eagle-import:R0805")
      (fields (field (name "MPN") "RC0805FR-0710KL"))
      (libsource (lib "eagle-import") (part "SMD-RES-10K-1%-1/8W(0805)"))
    )
    (comp (ref "R262")
      (value "104")
      (footprint "eagle-import:R0805")
      (fields (field (name "MPN") "RC0805FR-0710KL"))
      (libsource (lib "eagle-import") (part "SMD-RES-10K-1%-1/8W(0805)"))
    )
    (comp (ref "R263")
      (value "(1002)")
      (footprint "eagle-import:R0805")
      (fields (field (name "MPN") "RC0805FR-0710KL"))
      (libsource (lib "eagle-import") (part "SMD-RES-10K-1%-1/8W(0805)"))
    )
    (comp (ref "R264")
      (value "2702")
      (footprint "eagle-import:R0805")
      (fields (field (name "MPN") "RC0805FR-0710KL"))
      (libsource (lib "eagle-import") (part "SMD-RES-10K-1%-1/8W(0805)"))
    )
    (comp (ref "R265")
      (value "47")
      (footprint "eagle-import:V235_17_1MM")
      (libsource (lib "eagle-import") (part "R-EU_V235/17_1MM"))
    )
    (comp (ref "R266")
      (value "47")
      (footprint "eagle-import:V235_17_1MM")
      (libsource (lib "eagle-import") (part "R-EU_V235/17_1MM"))
    )
    (comp (ref "R267")
      (value "2702")
      (footprint "eagle-import:R0805")
      (fields (field (name "MPN") "RC0805JR-074K7L"))
      (libsource (lib "eagle-import") (part "SMD-RES-4.7K-5%-1/8W(0805)"))
    )
    (comp (ref "R268")
      (value "2201")
      (footprint "eagle-import:R0805")
      (fields (field (name "MPN") "RC0805JR-072K2L"))
      (libsource (lib "eagle-import") (part "SMD-RES-2.2K-5%-1/8W(0805)"))
    )
    (comp (ref "R269")
      (value "(1002)")
      (footprint "eagle-import:R0805")
      (fields (field (name "MPN") "RC0805JR-074K7L"))
      (libsource (lib "eagle-import") (part "SMD-RES-4.7K-5%-1/8W(0805)"))
    )
    (comp (ref "R270")
      (value "1002")
      (footprint "eagle-import:R0805")
      (fields (field (name "MPN") "RC0805FR-0710KL"))
      (libsource (lib "eagle-import") (part "SMD-RES-10K-1%-1/8W(0805)"))
    )
    (comp (ref "R271")
      (value "102")
      (footprint "eagle-import:R0805")
      (fields (field (name "MPN") "RC0805JR-071KL"))
      (libsource (lib "eagle-import") (part "SMD-RES-1K-5%-1/8W(0805)"))
    )
    (comp (ref "R272")
      (value "2702")
      (footprint "eagle-import:R0805")
      (fields (field (name "MPN") "RC0805JR-074K7L"))
      (libsource (lib "eagle-import") (part "SMD-RES-4.7K-5%-1/8W(0805)"))
    )
    (comp (ref "R273")
      (value "102")
      (footprint "eagle-import:R0805")
      (fields (field (name "MPN") "RC0805JR-071KL"))
      (libsource (lib "eagle-import") (part "SMD-RES-1K-5%-1/8W(0805)"))
    )
    (comp (ref "R274")
      (value "102")
      (footprint "eagle-import:R0805")
      (fields (field (name "MPN") "RC0805JR-071KL"))
      (libsource (lib "eagle-import") (part "SMD-RES-1K-5%-1/8W(0805)"))
    )
    (comp (ref "R275")
      (value "13")
      (footprint "eagle-import:R1206")
      (fields (field (name "MPN") "RC1206JR-0713RL"))
      (libsource (lib "eagle-import") (part "SMD-RES-13R-5%-1/4W(1206)"))
    )
    (comp (ref "R276")
      (value "R_user")
      (footprint "eagle-import:R0805")
      (libsource (lib "eagle-import") (part "R-EU_R0805"))
    )
    (comp (ref "SJ6") (value "SJ") (footprint "eagle-import:SJ") (libsource (lib "eagle-import") (part "SJ")))
    (comp (ref "START5")
      (value "TPSB2.0")
      (footprint "eagle-import:B2.0")
      (libsource (lib "eagle-import") (part "TPSB2.0"))
    )
    (comp (ref "TP116")
      (value "TPSB2.0")
      (footprint "eagle-import:B2.0")
      (libsource (lib "eagle-import") (part "TPSB2.0"))
    )
    (comp (ref "TP117")
      (value "TPSB2.0")
      (footprint "eagle-import:B2.0")
      (libsource (lib "eagle-import") (part "TPSB2.0"))
    )
    (comp (ref "TP118")
      (value "TPSB2.0")
      (footprint "eagle-import:B2.0")
      (libsource (lib "eagle-import") (part "TPSB2.0"))
    )
    (comp (ref "TP119")
      (value "TPSB2.0")
      (footprint "eagle-import:B2.0")
      (libsource (lib "eagle-import") (part "TPSB2.0"))
    )
    (comp (ref "TP120")
      (value "TPSB2.0")
      (footprint "eagle-import:B2.0")
      (libsource (lib "eagle-import") (part "TPSB2.0"))
    )
    (comp (ref "TP121")
      (value "TPSB2.0")
      (footprint "eagle-import:B2.0")
      (libsource (lib "eagle-import") (part "TPSB2.0"))
    )
    (comp (ref "TP122")
      (value "TPSB2.0")
      (footprint "eagle-import:B2.0")
      (libsource (lib "eagle-import") (part "TPSB2.0"))
    )
    (comp (ref "TP123")
      (value "TPSB2.0")
      (footprint "eagle-import:B2.0")
      (libsource (lib "eagle-import") (part "TPSB2.0"))
    )
    (comp (ref "TP124")
      (value "TPSB2.0")
      (footprint "eagle-import:B2.0")
      (libsource (lib "eagle-import") (part "TPSB2.0"))
    )
    (comp (ref "TP125")
      (value "TPSB2.0")
      (footprint "eagle-import:B2.0")
      (libsource (lib "eagle-import") (part "TPSB2.0"))
    )
    (comp (ref "TP126")
      (value "TPSB2.0")
      (footprint "eagle-import:B2.0")
      (libsource (lib "eagle-import") (part "TPSB2.0"))
    )
    (comp (ref "TP127")
      (value "TPSB2.0")
      (footprint "eagle-import:B2.0")
      (libsource (lib "eagle-import") (part "TPSB2.0"))
    )
    (comp (ref "TP128")
      (value "TPSB2.0")
      (footprint "eagle-import:B2.0")
      (libsource (lib "eagle-import") (part "TPSB2.0"))
    )
    (comp (ref "TP129")
      (value "TPSB2.0")
      (footprint "eagle-import:B2.0")
      (libsource (lib "eagle-import") (part "TPSB2.0"))
    )
    (comp (ref "TP130")
      (value "TPSB2.0")
      (footprint "eagle-import:B2.0")
      (libsource (lib "eagle-import") (part "TPSB2.0"))
    )
    (comp (ref "TP131")
      (value "TPSB2.0")
      (footprint "eagle-import:B2.0")
      (libsource (lib "eagle-import") (part "TPSB2.0"))
    )
    (comp (ref "TP132")
      (value "TPSB2.0")
      (footprint "eagle-import:B2.0")
      (libsource (lib "eagle-import") (part "TPSB2.0"))
    )
    (comp (ref "TP133")
      (value "TPSB2.0")
      (footprint "eagle-import:B2.0")
      (libsource (lib "eagle-import") (part "TPSB2.0"))
    )
    (comp (ref "TP134")
      (value "TPSB1,27")
      (footprint "eagle-import:B1,27")
      (libsource (lib "eagle-import") (part "TPSB1,27"))
    )
    (comp (ref "TP135")
      (value "TPSB2.0")
      (footprint "eagle-import:B2.0")
      (libsource (lib "eagle-import") (part "TPSB2.0"))
    )
    (comp (ref "TP136")
      (value "TPSB2.0")
      (footprint "eagle-import:B2.0")
      (libsource (lib "eagle-import") (part "TPSB2.0"))
    )
    (comp (ref "TP137")
      (value "TPSB2.0")
      (footprint "eagle-import:B2.0")
      (libsource (lib "eagle-import") (part "TPSB2.0"))
    )
    (comp (ref "TP138")
      (value "TPSB2.0")
      (footprint "eagle-import:B2.0")
      (libsource (lib "eagle-import") (part "TPSB2.0"))
    )
    (comp (ref "X16")
      (value "CON_BMWV2")
      (footprint "eagle-import:24-PIN_V2")
      (libsource (lib "eagle-import") (part "CON_BMWV2"))
    )
    (comp (ref "X17")
      (value "22-23-2051")
      (footprint "eagle-import:22-23-2051")
      (fields (field (name "MF") "MOLEX"))
      (libsource (lib "eagle-import") (part "22-23-2051"))
    )
    (comp (ref "X18")
      (value "22-23-2021")
      (footprint "eagle-import:22-23-2021")
      (fields (field (name "MF") "MOLEX"))
      (libsource (lib "eagle-import") (part "22-23-2021"))
    )
    (comp (ref "6V8")
      (value "TPSB2.0")
      (footprint "eagle-import:B2.0")
      (libsource (lib "eagle-import") (part "TPSB2.0"))
    )
    (comp (ref "10V8")
      (value "TPSB2.0")
      (footprint "eagle-import:B2.0")
      (libsource (lib "eagle-import") (part "TPSB2.0"))
    )
    (comp (ref "17")
      (value "2081-1132")
      (footprint "eagle-import:12-PIN")
      (libsource (lib "eagle-import") (part "2081-1132"))
    )
    (comp (ref "18")
      (value "2081-1132")
      (footprint "eagle-import:12-PIN")
      (libsource (lib "eagle-import") (part "2081-1132"))
    )
    (comp (ref "C81")
      (value "100u")
      (footprint "eagle-import:C1206")
      (fields (field (name "MPN") "GRM31CR60J107ME39L"))
      (libsource (lib "eagle-import") (part "CERAMIC-100UF-6.3V-20%-X5R(1206)"))
    )
    (comp (ref "C82")
      (value "100u")
      (footprint "eagle-import:C1206")
      (fields (field (name "MPN") "GRM31CR60J107ME39L"))
      (libsource (lib "eagle-import") (part "CERAMIC-100UF-6.3V-20%-X5R(1206)"))
    )
    (comp (ref "C83")
      (value "100nF,")
      (footprint "eagle-import:C0805")
      (fields (field (name "MPN") "CC0805KRX7R9BB104"))
      (libsource (lib "eagle-import") (part "CERAMIC-100NF-50V-10%-X7R(0805)"))
    )
    (comp (ref "C84")
      (value "4.7u")
      (footprint "eagle-import:C0805")
      (fields (field (name "MPN") "CC0805KKX5R8BB475"))
      (libsource (lib "eagle-import") (part "CERAMIC-4.7UF-25V-10%-X5R(0805)"))
    )
    (comp (ref "C85")
      (value "100nF.")
      (footprint "eagle-import:C0805")
      (fields (field (name "MPN") "CC0805KRX7R9BB104"))
      (libsource (lib "eagle-import") (part "CERAMIC-100NF-50V-10%-X7R(0805)"))
    )
    (comp (ref "C86")
      (value "100nF.")
      (footprint "eagle-import:C0805")
      (fields (field (name "MPN") "CC0805KRX7R9BB104"))
      (libsource (lib "eagle-import") (part "CERAMIC-100NF-50V-10%-X7R(0805)"))
    )
    (comp (ref "C87")
      (value "2.2nF")
      (footprint "eagle-import:C0805")
      (fields (field (name "MPN") "CC0805KRX7R9BB104"))
      (libsource (lib "eagle-import") (part "CERAMIC-100NF-50V-10%-X7R(0805)"))
    )
    (comp (ref "C88")
      (value "100nF")
      (footprint "eagle-import:C0805")
      (fields (field (name "MPN") "CC0805KRX7R9BB104"))
      (libsource (lib "eagle-import") (part "CERAMIC-100NF-50V-10%-X7R(0805)"))
    )
    (comp (ref "C89")
      (value "100nF")
      (footprint "eagle-import:C0805")
      (fields (field (name "MPN") "CC0805KRX7R9BB104"))
      (libsource (lib "eagle-import") (part "CERAMIC-100NF-50V-10%-X7R(0805)"))
    )
    (comp (ref "C90")
      (value "100nF,")
      (footprint "eagle-import:C0805")
      (fields (field (name "MPN") "CC0805KRX7R9BB104"))
      (libsource (lib "eagle-import") (part "CERAMIC-100NF-50V-10%-X7R(0805)"))
    )
    (comp (ref "D97")
      (value "1N4007")
      (footprint "eagle-import:DO-214AC")
      (libsource (lib "eagle-import") (part "DIODE-GEN-PURPOSE-1KV-1A(DO-214AC)"))
    )
    (comp (ref "D98")
      (value "1N4007,")
      (footprint "eagle-import:DO-214AC")
      (fields (field (name "MPN") "1N4007"))
      (libsource (lib "eagle-import") (part "DIODE-GEN-PURPOSE-1KV-1A(DO-214AC)"))
    )
    (comp (ref "D99")
      (value "1N4007,")
      (footprint "eagle-import:DO-214AC")
      (fields (field (name "MPN") "1N4007"))
      (libsource (lib "eagle-import") (part "DIODE-GEN-PURPOSE-1KV-1A(DO-214AC)"))
    )
    (comp (ref "D100")
      (value "1N4007.")
      (footprint "eagle-import:DO-214AC")
      (fields (field (name "MPN") "1N4007"))
      (libsource (lib "eagle-import") (part "DIODE-GEN-PURPOSE-1KV-1A(DO-214AC)"))
    )
    (comp (ref "D101")
      (value "1N5817")
      (footprint "eagle-import:DO-214AC_SLIM")
      (libsource (lib "eagle-import") (part "DIODE-GEN-PURPOSE-1KV-1A(DO-214AC)DO-214AC/1206"))
    )
    (comp (ref "D102")
      (value "1N5817.")
      (footprint "eagle-import:DO-214AC_SLIM")
      (libsource (lib "eagle-import") (part "DIODE-GEN-PURPOSE-1KV-1A(DO-214AC)DO-214AC/1206"))
    )
    (comp (ref "D103")
      (value "1N5817.")
      (footprint "eagle-import:DO-214AC_SLIM")
      (libsource (lib "eagle-import") (part "DIODE-GEN-PURPOSE-1KV-1A(DO-214AC)DO-214AC/1206"))
    )
    (comp (ref "D104")
      (value "1N5817")
      (footprint "eagle-import:DO-214AC_SLIM")
      (libsource (lib "eagle-import") (part "DIODE-GEN-PURPOSE-1KV-1A(DO-214AC)DO-214AC/1206"))
    )
    (comp (ref "D105")
      (value "1N4007.")
      (footprint "eagle-import:DO-214AC")
      (fields (field (name "MPN") "1N4007"))
      (libsource (lib "eagle-import") (part "DIODE-GEN-PURPOSE-1KV-1A(DO-214AC)"))
    )
    (comp (ref "D106")
      (value "1N4007")
      (footprint "eagle-import:DO-214AC")
      (libsource (lib "eagle-import") (part "DIODE-GEN-PURPOSE-1KV-1A(DO-214AC)"))
    )
    (comp (ref "D107")
      (value "SM6T")
      (footprint "eagle-import:DO214AA")
      (libsource (lib "eagle-import") (part "SM6T"))
    )
    (comp (ref "D108")
      (value "SM6TDO214AA_BI")
      (footprint "eagle-import:DO214AA_BI")
      (libsource (lib "eagle-import") (part "SM6TDO214AA_BI"))
    )
    (comp (ref "FID33")
      (value "FIDUCIAL")
      (footprint "eagle-import:FIDUCIAL_1MM")
      (libsource (lib "eagle-import") (part "FIDUCIAL"))
    )
    (comp (ref "FID34")
      (value "FIDUCIAL")
      (footprint "eagle-import:FIDUCIAL_1MM")
      (libsource (lib "eagle-import") (part "FIDUCIAL"))
    )
    (comp (ref "FID35")
      (value "FIDUCIAL")
      (footprint "eagle-import:FIDUCIAL_1MM")
      (libsource (lib "eagle-import") (part "FIDUCIAL"))
    )
    (comp (ref "FID36")
      (value "FIDUCIAL")
      (footprint "eagle-import:FIDUCIAL_1MM")
      (libsource (lib "eagle-import") (part "FIDUCIAL"))
    )
    (comp (ref "IC89")
      (value "4028")
      (footprint "eagle-import:SO16")
      (libsource (lib "eagle-import") (part "4028D"))
    )
    (comp (ref "IC90")
      (value "6V pos")
      (footprint "eagle-import:78LXX")
      (libsource (lib "eagle-import") (part "v-reg_78LXX"))
    )
    (comp (ref "IC91")
      (value "317TO202H_NOHOLE")
      (footprint "eagle-import:TO220H_NOHOLE")
      (libsource (lib "eagle-import") (part "317TO202H_NOHOLE"))
    )
    (comp (ref "IC92")
      (value "ULN2004")
      (footprint "eagle-import:SO16")
      (libsource (lib "eagle-import") (part "ULN2004AD"))
    )
    (comp (ref "IC93")
      (value "LM339")
      (footprint "eagle-import:SO14")
      (libsource (lib "eagle-import") (part "LM339D"))
    )
    (comp (ref "IC94")
      (value "78L06")
      (footprint "eagle-import:SOT89_ROUND")
      (libsource (lib "eagle-import") (part "78LXXSOT89_ROUND"))
    )
    (comp (ref "IC95")
      (value "555")
      (footprint "eagle-import:SO08")
      (libsource (lib "eagle-import") (part "555DNE"))
    )
    (comp (ref "IC96")
      (value "4538")
      (footprint "eagle-import:SO16")
      (libsource (lib "eagle-import") (part "4538D"))
    )
    (comp (ref "IC97")
      (value "78L10")
      (footprint "eagle-import:SOT89_ROUND")
      (libsource (lib "eagle-import") (part "78LXXSOT89_ROUND"))
    )
    (comp (ref "IC98")
      (value "LM2904")
      (footprint "eagle-import:SO08")
      (libsource (lib "eagle-import") (part "LM358D"))
    )
    (comp (ref "JP41")
      (value "JP2EJP2_SMALLPADS")
      (footprint "eagle-import:JP2_SMALLPADS")
      (libsource (lib "eagle-import") (part "JP2EJP2_SMALLPADS"))
    )
    (comp (ref "JP42")
      (value "JP2E_ORIG")
      (footprint "eagle-import:JP2_ORIG_SMALLPADS")
      (libsource (lib "eagle-import") (part "JP2E_ORIG"))
    )
    (comp (ref "JP43")
      (value "JP2EJP2_SMALLPADS")
      (footprint "eagle-import:JP2_SMALLPADS")
      (libsource (lib "eagle-import") (part "JP2EJP2_SMALLPADS"))
    )
    (comp (ref "JP44")
      (value "JP2EJP2_SMALLPADS")
      (footprint "eagle-import:JP2_SMALLPADS")
      (libsource (lib "eagle-import") (part "JP2EJP2_SMALLPADS"))
    )
    (comp (ref "JP45")
      (value "JP2EJP2_SMALLPADS")
      (footprint "eagle-import:JP2_SMALLPADS")
      (libsource (lib "eagle-import") (part "JP2EJP2_SMALLPADS"))
    )
    (comp (ref "LED49")
      (value "LEDLD260")
      (footprint "eagle-import:LD260")
      (libsource (lib "eagle-import") (part "LEDLD260"))
    )
    (comp (ref "LED50")
      (value "LEDLD260")
      (footprint "eagle-import:LD260")
      (libsource (lib "eagle-import") (part "LEDLD260"))
    )
    (comp (ref "LED51")
      (value "LEDLD260")
      (footprint "eagle-import:LD260")
      (libsource (lib "eagle-import") (part "LEDLD260"))
    )
    (comp (ref "LED52")
      (value "LEDLD260")
      (footprint "eagle-import:LD260")
      (libsource (lib "eagle-import") (part "LEDLD260"))
    )
    (comp (ref "LED53")
      (value "LEDLD260")
      (footprint "eagle-import:LD260")
      (libsource (lib "eagle-import") (part "LEDLD260"))
    )
    (comp (ref "LED54")
      (value "LEDLD260")
      (footprint "eagle-import:LD260")
      (libsource (lib "eagle-import") (part "LEDLD260"))
    )
    (comp (ref "Q57")
      (value "BA")
      (footprint "eagle-import:SOT89")
      (libsource (lib "eagle-import") (part "PNP-TRANSISTOR_SOT89"))
    )
    (comp (ref "Q58")
      (value "BA.")
      (footprint "eagle-import:SOT89")
      (libsource (lib "eagle-import") (part "PNP-TRANSISTOR_SOT89"))
    )
    (comp (ref "Q59")
      (value "BA.")
      (footprint "eagle-import:SOT89")
      (libsource (lib "eagle-import") (part "PNP-TRANSISTOR_SOT89"))
    )
    (comp (ref "Q60")
      (value "BA")
      (footprint "eagle-import:SOT89")
      (libsource (lib "eagle-import") (part "PNP-TRANSISTOR_SOT89"))
    )
    (comp (ref "Q61")
      (value "MY")
      (footprint "eagle-import:SOT89")
      (libsource (lib "eagle-import") (part "NPN-TRANSISTOR_SOT89"))
    )
    (comp (ref "Q62")
      (value "J1")
      (footprint "eagle-import:SOT-23")
      (fields (field (name "MPN") "BSS138W-7-F"))
      (libsource (lib "eagle-import") (part "SMD-MOSFET-N-CH-50V-200MA-BSS138W-7-F(SOT-23)"))
    )
    (comp (ref "Q63")
      (value "J1")
      (footprint "eagle-import:SOT-23")
      (fields (field (name "MPN") "BSS138W-7-F"))
      (libsource (lib "eagle-import") (part "SMD-MOSFET-N-CH-50V-200MA-BSS138W-7-F(SOT-23)"))
    )
    (comp (ref "R369")
      (value "47")
      (footprint "eagle-import:V235_17_1MM")
      (libsource (lib "eagle-import") (part "R-EU_V235/17_1MM"))
    )
    (comp (ref "R370")
      (value "13")
      (footprint "eagle-import:R1206")
      (fields (field (name "MPN") "RC1206JR-0713RL"))
      (libsource (lib "eagle-import") (part "SMD-RES-13R-5%-1/4W(1206)"))
    )
    (comp (ref "R371")
      (value "47")
      (footprint "eagle-import:V235_17_1MM")
      (libsource (lib "eagle-import") (part "R-EU_V235/17_1MM"))
    )
    (comp (ref "R372")
      (value "104")
      (footprint "eagle-import:R0805")
      (fields (field (name "MPN") "RC0805FR-0710KL"))
      (libsource (lib "eagle-import") (part "SMD-RES-10K-1%-1/8W(0805)"))
    )
    (comp (ref "R373")
      (value "104")
      (footprint "eagle-import:R0805")
      (fields (field (name "MPN") "RC0805FR-0710KL"))
      (libsource (lib "eagle-import") (part "SMD-RES-10K-1%-1/8W(0805)"))
    )
    (comp (ref "R374")
      (value "104")
      (footprint "eagle-import:R0805")
      (fields (field (name "MPN") "RC0805FR-0710KL"))
      (libsource (lib "eagle-import") (part "SMD-RES-10K-1%-1/8W(0805)"))
    )
    (comp (ref "R375")
      (value "4701")
      (footprint "eagle-import:R0805")
      (fields (field (name "MPN") "RC0805JR-074K7L"))
      (libsource (lib "eagle-import") (part "SMD-RES-4.7K-5%-1/8W(0805)"))
    )
    (comp (ref "R376")
      (value "1002")
      (footprint "eagle-import:R0805")
      (fields (field (name "MPN") "RC0805FR-0710KL"))
      (libsource (lib "eagle-import") (part "SMD-RES-10K-1%-1/8W(0805)"))
    )
    (comp (ref "R377")
      (value "1002")
      (footprint "eagle-import:R0805")
      (fields (field (name "MPN") "RC0805FR-0710KL"))
      (libsource (lib "eagle-import") (part "SMD-RES-10K-1%-1/8W(0805)"))
    )
    (comp (ref "R378")
      (value "1502")
      (footprint "eagle-import:R0805")
      (fields (field (name "MPN") "RC0805FR-0710KL"))
      (libsource (lib "eagle-import") (part "SMD-RES-10K-1%-1/8W(0805)"))
    )
    (comp (ref "R379")
      (value "104")
      (footprint "eagle-import:R0805")
      (fields (field (name "MPN") "RC0805FR-0710KL"))
      (libsource (lib "eagle-import") (part "SMD-RES-10K-1%-1/8W(0805)"))
    )
    (comp (ref "R380")
      (value "104")
      (footprint "eagle-import:R0805")
      (fields (field (name "MPN") "RC0805FR-0710KL"))
      (libsource (lib "eagle-import") (part "SMD-RES-10K-1%-1/8W(0805)"))
    )
    (comp (ref "R381")
      (value "1502")
      (footprint "eagle-import:R0805")
      (fields (field (name "MPN") "RC0805FR-0710KL"))
      (libsource (lib "eagle-import") (part "SMD-RES-10K-1%-1/8W(0805)"))
    )
    (comp (ref "R382")
      (value "1002")
      (footprint "eagle-import:R0805")
      (fields (field (name "MPN") "RC0805FR-0710KL"))
      (libsource (lib "eagle-import") (part "SMD-RES-10K-1%-1/8W(0805)"))
    )
    (comp (ref "R383")
      (value "2201")
      (footprint "eagle-import:R0805")
      (fields (field (name "MPN") "RC0805JR-072K2L"))
      (libsource (lib "eagle-import") (part "SMD-RES-2.2K-5%-1/8W(0805)"))
    )
    (comp (ref "R384")
      (value "1002")
      (footprint "eagle-import:R0805")
      (fields (field (name "MPN") "RC0805FR-0710KL"))
      (libsource (lib "eagle-import") (part "SMD-RES-10K-1%-1/8W(0805)"))
    )
    (comp (ref "R385")
      (value "4701")
      (footprint "eagle-import:R0805")
      (fields (field (name "MPN") "RC0805JR-074K7L"))
      (libsource (lib "eagle-import") (part "SMD-RES-4.7K-5%-1/8W(0805)"))
    )
    (comp (ref "R386")
      (value "2702")
      (footprint "eagle-import:R0805")
      (fields (field (name "MPN") "RC0805JR-074K7L"))
      (libsource (lib "eagle-import") (part "SMD-RES-4.7K-5%-1/8W(0805)"))
    )
    (comp (ref "R387")
      (value "102")
      (footprint "eagle-import:R0805")
      (fields (field (name "MPN") "RC0805JR-071KL"))
      (libsource (lib "eagle-import") (part "SMD-RES-1K-5%-1/8W(0805)"))
    )
    (comp (ref "R388")
      (value "R_user")
      (footprint "eagle-import:R0805")
      (libsource (lib "eagle-import") (part "R-EU_R0805"))
    )
    (comp (ref "R389")
      (value "100")
      (footprint "eagle-import:R0805")
      (fields (field (name "MPN") "RC0805JR-07220RL"))
      (libsource (lib "eagle-import") (part "SMD-RES-220R-5%-1/8W(0805)"))
    )
    (comp (ref "R390")
      (value "(101)")
      (footprint "eagle-import:R0805")
      (fields (field (name "MPN") "RC0805JR-07100RL"))
      (libsource (lib "eagle-import") (part "SMD-RES-100R-5%-1/8W(0805)"))
    )
    (comp (ref "R391")
      (value "(1000)")
      (footprint "eagle-import:R0805")
      (fields (field (name "MPN") "RC0805JR-07100RL"))
      (libsource (lib "eagle-import") (part "SMD-RES-100R-5%-1/8W(0805)"))
    )
    (comp (ref "R392")
      (value "102")
      (footprint "eagle-import:R0805")
      (fields (field (name "MPN") "RC0805JR-071KL"))
      (libsource (lib "eagle-import") (part "SMD-RES-1K-5%-1/8W(0805)"))
    )
    (comp (ref "R393")
      (value "13")
      (footprint "eagle-import:R1206")
      (fields (field (name "MPN") "RC1206JR-0713RL"))
      (libsource (lib "eagle-import") (part "SMD-RES-13R-5%-1/4W(1206)"))
    )
    (comp (ref "R394")
      (value "13")
      (footprint "eagle-import:R1206")
      (fields (field (name "MPN") "RC1206JR-0713RL"))
      (libsource (lib "eagle-import") (part "SMD-RES-13R-5%-1/4W(1206)"))
    )
    (comp (ref "R395")
      (value "2702")
      (footprint "eagle-import:R0805")
      (fields (field (name "MPN") "RC0805JR-074K7L"))
      (libsource (lib "eagle-import") (part "SMD-RES-4.7K-5%-1/8W(0805)"))
    )
    (comp (ref "R396")
      (value "4701")
      (footprint "eagle-import:R0805")
      (fields (field (name "MPN") "RC0805JR-074K7L"))
      (libsource (lib "eagle-import") (part "SMD-RES-4.7K-5%-1/8W(0805)"))
    )
    (comp (ref "R397")
      (value "100")
      (footprint "eagle-import:R0805")
      (fields (field (name "MPN") "RC0805JR-072K2L"))
      (libsource (lib "eagle-import") (part "SMD-RES-2.2K-5%-1/8W(0805)"))
    )
    (comp (ref "R398")
      (value "(101)")
      (footprint "eagle-import:R0805")
      (fields (field (name "MPN") "RC0805JR-072K2L"))
      (libsource (lib "eagle-import") (part "SMD-RES-2.2K-5%-1/8W(0805)"))
    )
    (comp (ref "R399")
      (value "104")
      (footprint "eagle-import:R0805")
      (fields (field (name "MPN") "RC0805FR-0710KL"))
      (libsource (lib "eagle-import") (part "SMD-RES-10K-1%-1/8W(0805)"))
    )
    (comp (ref "R400")
      (value "104")
      (footprint "eagle-import:R0805")
      (fields (field (name "MPN") "RC0805FR-0710KL"))
      (libsource (lib "eagle-import") (part "SMD-RES-10K-1%-1/8W(0805)"))
    )
    (comp (ref "R401")
      (value "(1002)")
      (footprint "eagle-import:R0805")
      (fields (field (name "MPN") "RC0805FR-0710KL"))
      (libsource (lib "eagle-import") (part "SMD-RES-10K-1%-1/8W(0805)"))
    )
    (comp (ref "R402")
      (value "2702")
      (footprint "eagle-import:R0805")
      (fields (field (name "MPN") "RC0805FR-0710KL"))
      (libsource (lib "eagle-import") (part "SMD-RES-10K-1%-1/8W(0805)"))
    )
    (comp (ref "R403")
      (value "47")
      (footprint "eagle-import:V235_17_1MM")
      (libsource (lib "eagle-import") (part "R-EU_V235/17_1MM"))
    )
    (comp (ref "R404")
      (value "47")
      (footprint "eagle-import:V235_17_1MM")
      (libsource (lib "eagle-import") (part "R-EU_V235/17_1MM"))
    )
    (comp (ref "R405")
      (value "2702")
      (footprint "eagle-import:R0805")
      (fields (field (name "MPN") "RC0805JR-074K7L"))
      (libsource (lib "eagle-import") (part "SMD-RES-4.7K-5%-1/8W(0805)"))
    )
    (comp (ref "R406")
      (value "2201")
      (footprint "eagle-import:R0805")
      (fields (field (name "MPN") "RC0805JR-072K2L"))
      (libsource (lib "eagle-import") (part "SMD-RES-2.2K-5%-1/8W(0805)"))
    )
    (comp (ref "R407")
      (value "(1002)")
      (footprint "eagle-import:R0805")
      (fields (field (name "MPN") "RC0805JR-074K7L"))
      (libsource (lib "eagle-import") (part "SMD-RES-4.7K-5%-1/8W(0805)"))
    )
    (comp (ref "R408")
      (value "1002")
      (footprint "eagle-import:R0805")
      (fields (field (name "MPN") "RC0805FR-0710KL"))
      (libsource (lib "eagle-import") (part "SMD-RES-10K-1%-1/8W(0805)"))
    )
    (comp (ref "R409")
      (value "102")
      (footprint "eagle-import:R0805")
      (fields (field (name "MPN") "RC0805JR-071KL"))
      (libsource (lib "eagle-import") (part "SMD-RES-1K-5%-1/8W(0805)"))
    )
    (comp (ref "R410")
      (value "2702")
      (footprint "eagle-import:R0805")
      (fields (field (name "MPN") "RC0805JR-074K7L"))
      (libsource (lib "eagle-import") (part "SMD-RES-4.7K-5%-1/8W(0805)"))
    )
    (comp (ref "R411")
      (value "102")
      (footprint "eagle-import:R0805")
      (fields (field (name "MPN") "RC0805JR-071KL"))
      (libsource (lib "eagle-import") (part "SMD-RES-1K-5%-1/8W(0805)"))
    )
    (comp (ref "R412")
      (value "102")
      (footprint "eagle-import:R0805")
      (fields (field (name "MPN") "RC0805JR-071KL"))
      (libsource (lib "eagle-import") (part "SMD-RES-1K-5%-1/8W(0805)"))
    )
    (comp (ref "R413")
      (value "13")
      (footprint "eagle-import:R1206")
      (fields (field (name "MPN") "RC1206JR-0713RL"))
      (libsource (lib "eagle-import") (part "SMD-RES-13R-5%-1/4W(1206)"))
    )
    (comp (ref "R414")
      (value "R_user")
      (footprint "eagle-import:R0805")
      (libsource (lib "eagle-import") (part "R-EU_R0805"))
    )
    (comp (ref "SJ9") (value "SJ") (footprint "eagle-import:SJ") (libsource (lib "eagle-import") (part "SJ")))
    (comp (ref "START8")
      (value "TPSB2.0")
      (footprint "eagle-import:B2.0")
      (libsource (lib "eagle-import") (part "TPSB2.0"))
    )
    (comp (ref "TP185")
      (value "TPSB2.0")
      (footprint "eagle-import:B2.0")
      (libsource (lib "eagle-import") (part "TPSB2.0"))
    )
    (comp (ref "TP186")
      (value "TPSB2.0")
      (footprint "eagle-import:B2.0")
      (libsource (lib "eagle-import") (part "TPSB2.0"))
    )
    (comp (ref "TP187")
      (value "TPSB2.0")
      (footprint "eagle-import:B2.0")
      (libsource (lib "eagle-import") (part "TPSB2.0"))
    )
    (comp (ref "TP188")
      (value "TPSB2.0")
      (footprint "eagle-import:B2.0")
      (libsource (lib "eagle-import") (part "TPSB2.0"))
    )
    (comp (ref "TP189")
      (value "TPSB2.0")
      (footprint "eagle-import:B2.0")
      (libsource (lib "eagle-import") (part "TPSB2.0"))
    )
    (comp (ref "TP190")
      (value "TPSB2.0")
      (footprint "eagle-import:B2.0")
      (libsource (lib "eagle-import") (part "TPSB2.0"))
    )
    (comp (ref "TP191")
      (value "TPSB2.0")
      (footprint "eagle-import:B2.0")
      (libsource (lib "eagle-import") (part "TPSB2.0"))
    )
    (comp (ref "TP192")
      (value "TPSB2.0")
      (footprint "eagle-import:B2.0")
      (libsource (lib "eagle-import") (part "TPSB2.0"))
    )
    (comp (ref "TP193")
      (value "TPSB2.0")
      (footprint "eagle-import:B2.0")
      (libsource (lib "eagle-import") (part "TPSB2.0"))
    )
    (comp (ref "TP194")
      (value "TPSB2.0")
      (footprint "eagle-import:B2.0")
      (libsource (lib "eagle-import") (part "TPSB2.0"))
    )
    (comp (ref "TP195")
      (value "TPSB2.0")
      (footprint "eagle-import:B2.0")
      (libsource (lib "eagle-import") (part "TPSB2.0"))
    )
    (comp (ref "TP196")
      (value "TPSB2.0")
      (footprint "eagle-import:B2.0")
      (libsource (lib "eagle-import") (part "TPSB2.0"))
    )
    (comp (ref "TP197")
      (value "TPSB2.0")
      (footprint "eagle-import:B2.0")
      (libsource (lib "eagle-import") (part "TPSB2.0"))
    )
    (comp (ref "TP198")
      (value "TPSB2.0")
      (footprint "eagle-import:B2.0")
      (libsource (lib "eagle-import") (part "TPSB2.0"))
    )
    (comp (ref "TP199")
      (value "TPSB2.0")
      (footprint "eagle-import:B2.0")
      (libsource (lib "eagle-import") (part "TPSB2.0"))
    )
    (comp (ref "TP200")
      (value "TPSB2.0")
      (footprint "eagle-import:B2.0")
      (libsource (lib "eagle-import") (part "TPSB2.0"))
    )
    (comp (ref "TP201")
      (value "TPSB2.0")
      (footprint "eagle-import:B2.0")
      (libsource (lib "eagle-import") (part "TPSB2.0"))
    )
    (comp (ref "TP202")
      (value "TPSB2.0")
      (footprint "eagle-import:B2.0")
      (libsource (lib "eagle-import") (part "TPSB2.0"))
    )
    (comp (ref "TP203")
      (value "TPSB1,27")
      (footprint "eagle-import:B1,27")
      (libsource (lib "eagle-import") (part "TPSB1,27"))
    )
    (comp (ref "TP204")
      (value "TPSB2.0")
      (footprint "eagle-import:B2.0")
      (libsource (lib "eagle-import") (part "TPSB2.0"))
    )
    (comp (ref "TP205")
      (value "TPSB2.0")
      (footprint "eagle-import:B2.0")
      (libsource (lib "eagle-import") (part "TPSB2.0"))
    )
    (comp (ref "TP206")
      (value "TPSB2.0")
      (footprint "eagle-import:B2.0")
      (libsource (lib "eagle-import") (part "TPSB2.0"))
    )
    (comp (ref "TP207")
      (value "TPSB2.0")
      (footprint "eagle-import:B2.0")
      (libsource (lib "eagle-import") (part "TPSB2.0"))
    )
    (comp (ref "X25")
      (value "CON_BMWV2")
      (footprint "eagle-import:24-PIN_V2")
      (libsource (lib "eagle-import") (part "CON_BMWV2"))
    )
    (comp (ref "X26")
      (value "22-23-2051")
      (footprint "eagle-import:22-23-2051")
      (fields (field (name "MF") "MOLEX"))
      (libsource (lib "eagle-import") (part "22-23-2051"))
    )
    (comp (ref "X27")
      (value "22-23-2021")
      (footprint "eagle-import:22-23-2021")
      (fields (field (name "MF") "MOLEX"))
      (libsource (lib "eagle-import") (part "22-23-2021"))
    )
    (comp (ref "6V6")
      (value "TPSB2.0")
      (footprint "eagle-import:B2.0")
      (libsource (lib "eagle-import") (part "TPSB2.0"))
    )
    (comp (ref "10V6")
      (value "TPSB2.0")
      (footprint "eagle-import:B2.0")
      (libsource (lib "eagle-import") (part "TPSB2.0"))
    )
    (comp (ref "13")
      (value "2081-1132")
      (footprint "eagle-import:12-PIN")
      (libsource (lib "eagle-import") (part "2081-1132"))
    )
    (comp (ref "14")
      (value "2081-1132")
      (footprint "eagle-import:12-PIN")
      (libsource (lib "eagle-import") (part "2081-1132"))
    )
    (comp (ref "C61")
      (value "100u")
      (footprint "eagle-import:C1206")
      (fields (field (name "MPN") "GRM31CR60J107ME39L"))
      (libsource (lib "eagle-import") (part "CERAMIC-100UF-6.3V-20%-X5R(1206)"))
    )
    (comp (ref "C62")
      (value "100u")
      (footprint "eagle-import:C1206")
      (fields (field (name "MPN") "GRM31CR60J107ME39L"))
      (libsource (lib "eagle-import") (part "CERAMIC-100UF-6.3V-20%-X5R(1206)"))
    )
    (comp (ref "C63")
      (value "100nF,")
      (footprint "eagle-import:C0805")
      (fields (field (name "MPN") "CC0805KRX7R9BB104"))
      (libsource (lib "eagle-import") (part "CERAMIC-100NF-50V-10%-X7R(0805)"))
    )
    (comp (ref "C64")
      (value "4.7u")
      (footprint "eagle-import:C0805")
      (fields (field (name "MPN") "CC0805KKX5R8BB475"))
      (libsource (lib "eagle-import") (part "CERAMIC-4.7UF-25V-10%-X5R(0805)"))
    )
    (comp (ref "C65")
      (value "100nF.")
      (footprint "eagle-import:C0805")
      (fields (field (name "MPN") "CC0805KRX7R9BB104"))
      (libsource (lib "eagle-import") (part "CERAMIC-100NF-50V-10%-X7R(0805)"))
    )
    (comp (ref "C66")
      (value "100nF.")
      (footprint "eagle-import:C0805")
      (fields (field (name "MPN") "CC0805KRX7R9BB104"))
      (libsource (lib "eagle-import") (part "CERAMIC-100NF-50V-10%-X7R(0805)"))
    )
    (comp (ref "C67")
      (value "2.2nF")
      (footprint "eagle-import:C0805")
      (fields (field (name "MPN") "CC0805KRX7R9BB104"))
      (libsource (lib "eagle-import") (part "CERAMIC-100NF-50V-10%-X7R(0805)"))
    )
    (comp (ref "C68")
      (value "100nF")
      (footprint "eagle-import:C0805")
      (fields (field (name "MPN") "CC0805KRX7R9BB104"))
      (libsource (lib "eagle-import") (part "CERAMIC-100NF-50V-10%-X7R(0805)"))
    )
    (comp (ref "C69")
      (value "100nF")
      (footprint "eagle-import:C0805")
      (fields (field (name "MPN") "CC0805KRX7R9BB104"))
      (libsource (lib "eagle-import") (part "CERAMIC-100NF-50V-10%-X7R(0805)"))
    )
    (comp (ref "C70")
      (value "100nF,")
      (footprint "eagle-import:C0805")
      (fields (field (name "MPN") "CC0805KRX7R9BB104"))
      (libsource (lib "eagle-import") (part "CERAMIC-100NF-50V-10%-X7R(0805)"))
    )
    (comp (ref "D73")
      (value "1N4007")
      (footprint "eagle-import:DO-214AC")
      (libsource (lib "eagle-import") (part "DIODE-GEN-PURPOSE-1KV-1A(DO-214AC)"))
    )
    (comp (ref "D74")
      (value "1N4007,")
      (footprint "eagle-import:DO-214AC")
      (fields (field (name "MPN") "1N4007"))
      (libsource (lib "eagle-import") (part "DIODE-GEN-PURPOSE-1KV-1A(DO-214AC)"))
    )
    (comp (ref "D75")
      (value "1N4007,")
      (footprint "eagle-import:DO-214AC")
      (fields (field (name "MPN") "1N4007"))
      (libsource (lib "eagle-import") (part "DIODE-GEN-PURPOSE-1KV-1A(DO-214AC)"))
    )
    (comp (ref "D76")
      (value "1N4007.")
      (footprint "eagle-import:DO-214AC")
      (fields (field (name "MPN") "1N4007"))
      (libsource (lib "eagle-import") (part "DIODE-GEN-PURPOSE-1KV-1A(DO-214AC)"))
    )
    (comp (ref "D77")
      (value "1N5817")
      (footprint "eagle-import:DO-214AC_SLIM")
      (libsource (lib "eagle-import") (part "DIODE-GEN-PURPOSE-1KV-1A(DO-214AC)DO-214AC/1206"))
    )
    (comp (ref "D78")
      (value "1N5817.")
      (footprint "eagle-import:DO-214AC_SLIM")
      (libsource (lib "eagle-import") (part "DIODE-GEN-PURPOSE-1KV-1A(DO-214AC)DO-214AC/1206"))
    )
    (comp (ref "D79")
      (value "1N5817.")
      (footprint "eagle-import:DO-214AC_SLIM")
      (libsource (lib "eagle-import") (part "DIODE-GEN-PURPOSE-1KV-1A(DO-214AC)DO-214AC/1206"))
    )
    (comp (ref "D80")
      (value "1N5817")
      (footprint "eagle-import:DO-214AC_SLIM")
      (libsource (lib "eagle-import") (part "DIODE-GEN-PURPOSE-1KV-1A(DO-214AC)DO-214AC/1206"))
    )
    (comp (ref "D81")
      (value "1N4007.")
      (footprint "eagle-import:DO-214AC")
      (fields (field (name "MPN") "1N4007"))
      (libsource (lib "eagle-import") (part "DIODE-GEN-PURPOSE-1KV-1A(DO-214AC)"))
    )
    (comp (ref "D82")
      (value "1N4007")
      (footprint "eagle-import:DO-214AC")
      (libsource (lib "eagle-import") (part "DIODE-GEN-PURPOSE-1KV-1A(DO-214AC)"))
    )
    (comp (ref "D83")
      (value "SM6T")
      (footprint "eagle-import:DO214AA")
      (libsource (lib "eagle-import") (part "SM6T"))
    )
    (comp (ref "D84")
      (value "SM6TDO214AA_BI")
      (footprint "eagle-import:DO214AA_BI")
      (libsource (lib "eagle-import") (part "SM6TDO214AA_BI"))
    )
    (comp (ref "FID25")
      (value "FIDUCIAL")
      (footprint "eagle-import:FIDUCIAL_1MM")
      (libsource (lib "eagle-import") (part "FIDUCIAL"))
    )
    (comp (ref "FID26")
      (value "FIDUCIAL")
      (footprint "eagle-import:FIDUCIAL_1MM")
      (libsource (lib "eagle-import") (part "FIDUCIAL"))
    )
    (comp (ref "FID27")
      (value "FIDUCIAL")
      (footprint "eagle-import:FIDUCIAL_1MM")
      (libsource (lib "eagle-import") (part "FIDUCIAL"))
    )
    (comp (ref "FID28")
      (value "FIDUCIAL")
      (footprint "eagle-import:FIDUCIAL_1MM")
      (libsource (lib "eagle-import") (part "FIDUCIAL"))
    )
    (comp (ref "IC67")
      (value "4028")
      (footprint "eagle-import:SO16")
      (libsource (lib "eagle-import") (part "4028D"))
    )
    (comp (ref "IC68")
      (value "6V pos")
      (footprint "eagle-import:78LXX")
      (libsource (lib "eagle-import") (part "v-reg_78LXX"))
    )
    (comp (ref "IC69")
      (value "317TO202H_NOHOLE")
      (footprint "eagle-import:TO220H_NOHOLE")
      (libsource (lib "eagle-import") (part "317TO202H_NOHOLE"))
    )
    (comp (ref "IC70")
      (value "ULN2004")
      (footprint "eagle-import:SO16")
      (libsource (lib "eagle-import") (part "ULN2004AD"))
    )
    (comp (ref "IC71")
      (value "LM339")
      (footprint "eagle-import:SO14")
      (libsource (lib "eagle-import") (part "LM339D"))
    )
    (comp (ref "IC72")
      (value "78L06")
      (footprint "eagle-import:SOT89_ROUND")
      (libsource (lib "eagle-import") (part "78LXXSOT89_ROUND"))
    )
    (comp (ref "IC73")
      (value "555")
      (footprint "eagle-import:SO08")
      (libsource (lib "eagle-import") (part "555DNE"))
    )
    (comp (ref "IC74")
      (value "4538")
      (footprint "eagle-import:SO16")
      (libsource (lib "eagle-import") (part "4538D"))
    )
    (comp (ref "IC75")
      (value "78L10")
      (footprint "eagle-import:SOT89_ROUND")
      (libsource (lib "eagle-import") (part "78LXXSOT89_ROUND"))
    )
    (comp (ref "IC76")
      (value "LM2904")
      (footprint "eagle-import:SO08")
      (libsource (lib "eagle-import") (part "LM358D"))
    )
    (comp (ref "JP31")
      (value "JP2EJP2_SMALLPADS")
      (footprint "eagle-import:JP2_SMALLPADS")
      (libsource (lib "eagle-import") (part "JP2EJP2_SMALLPADS"))
    )
    (comp (ref "JP32")
      (value "JP2E_ORIG")
      (footprint "eagle-import:JP2_ORIG_SMALLPADS")
      (libsource (lib "eagle-import") (part "JP2E_ORIG"))
    )
    (comp (ref "JP33")
      (value "JP2EJP2_SMALLPADS")
      (footprint "eagle-import:JP2_SMALLPADS")
      (libsource (lib "eagle-import") (part "JP2EJP2_SMALLPADS"))
    )
    (comp (ref "JP34")
      (value "JP2EJP2_SMALLPADS")
      (footprint "eagle-import:JP2_SMALLPADS")
      (libsource (lib "eagle-import") (part "JP2EJP2_SMALLPADS"))
    )
    (comp (ref "JP35")
      (value "JP2EJP2_SMALLPADS")
      (footprint "eagle-import:JP2_SMALLPADS")
      (libsource (lib "eagle-import") (part "JP2EJP2_SMALLPADS"))
    )
    (comp (ref "LED37")
      (value "LEDLD260")
      (footprint "eagle-import:LD260")
      (libsource (lib "eagle-import") (part "LEDLD260"))
    )
    (comp (ref "LED38")
      (value "LEDLD260")
      (footprint "eagle-import:LD260")
      (libsource (lib "eagle-import") (part "LEDLD260"))
    )
    (comp (ref "LED39")
      (value "LEDLD260")
      (footprint "eagle-import:LD260")
      (libsource (lib "eagle-import") (part "LEDLD260"))
    )
    (comp (ref "LED40")
      (value "LEDLD260")
      (footprint "eagle-import:LD260")
      (libsource (lib "eagle-import") (part "LEDLD260"))
    )
    (comp (ref "LED41")
      (value "LEDLD260")
      (footprint "eagle-import:LD260")
      (libsource (lib "eagle-import") (part "LEDLD260"))
    )
    (comp (ref "LED42")
      (value "LEDLD260")
      (footprint "eagle-import:LD260")
      (libsource (lib "eagle-import") (part "LEDLD260"))
    )
    (comp (ref "Q43")
      (value "BA")
      (footprint "eagle-import:SOT89")
      (libsource (lib "eagle-import") (part "PNP-TRANSISTOR_SOT89"))
    )
    (comp (ref "Q44")
      (value "BA.")
      (footprint "eagle-import:SOT89")
      (libsource (lib "eagle-import") (part "PNP-TRANSISTOR_SOT89"))
    )
    (comp (ref "Q45")
      (value "BA.")
      (footprint "eagle-import:SOT89")
      (libsource (lib "eagle-import") (part "PNP-TRANSISTOR_SOT89"))
    )
    (comp (ref "Q46")
      (value "BA")
      (footprint "eagle-import:SOT89")
      (libsource (lib "eagle-import") (part "PNP-TRANSISTOR_SOT89"))
    )
    (comp (ref "Q47")
      (value "MY")
      (footprint "eagle-import:SOT89")
      (libsource (lib "eagle-import") (part "NPN-TRANSISTOR_SOT89"))
    )
    (comp (ref "Q48")
      (value "J1")
      (footprint "eagle-import:SOT-23")
      (fields (field (name "MPN") "BSS138W-7-F"))
      (libsource (lib "eagle-import") (part "SMD-MOSFET-N-CH-50V-200MA-BSS138W-7-F(SOT-23)"))
    )
    (comp (ref "Q49")
      (value "J1")
      (footprint "eagle-import:SOT-23")
      (fields (field (name "MPN") "BSS138W-7-F"))
      (libsource (lib "eagle-import") (part "SMD-MOSFET-N-CH-50V-200MA-BSS138W-7-F(SOT-23)"))
    )
    (comp (ref "R277")
      (value "47")
      (footprint "eagle-import:V235_17_1MM")
      (libsource (lib "eagle-import") (part "R-EU_V235/17_1MM"))
    )
    (comp (ref "R278")
      (value "13")
      (footprint "eagle-import:R1206")
      (fields (field (name "MPN") "RC1206JR-0713RL"))
      (libsource (lib "eagle-import") (part "SMD-RES-13R-5%-1/4W(1206)"))
    )
    (comp (ref "R279")
      (value "47")
      (footprint "eagle-import:V235_17_1MM")
      (libsource (lib "eagle-import") (part "R-EU_V235/17_1MM"))
    )
    (comp (ref "R280")
      (value "104")
      (footprint "eagle-import:R0805")
      (fields (field (name "MPN") "RC0805FR-0710KL"))
      (libsource (lib "eagle-import") (part "SMD-RES-10K-1%-1/8W(0805)"))
    )
    (comp (ref "R281")
      (value "104")
      (footprint "eagle-import:R0805")
      (fields (field (name "MPN") "RC0805FR-0710KL"))
      (libsource (lib "eagle-import") (part "SMD-RES-10K-1%-1/8W(0805)"))
    )
    (comp (ref "R282")
      (value "104")
      (footprint "eagle-import:R0805")
      (fields (field (name "MPN") "RC0805FR-0710KL"))
      (libsource (lib "eagle-import") (part "SMD-RES-10K-1%-1/8W(0805)"))
    )
    (comp (ref "R283")
      (value "4701")
      (footprint "eagle-import:R0805")
      (fields (field (name "MPN") "RC0805JR-074K7L"))
      (libsource (lib "eagle-import") (part "SMD-RES-4.7K-5%-1/8W(0805)"))
    )
    (comp (ref "R284")
      (value "1002")
      (footprint "eagle-import:R0805")
      (fields (field (name "MPN") "RC0805FR-0710KL"))
      (libsource (lib "eagle-import") (part "SMD-RES-10K-1%-1/8W(0805)"))
    )
    (comp (ref "R285")
      (value "1002")
      (footprint "eagle-import:R0805")
      (fields (field (name "MPN") "RC0805FR-0710KL"))
      (libsource (lib "eagle-import") (part "SMD-RES-10K-1%-1/8W(0805)"))
    )
    (comp (ref "R286")
      (value "1502")
      (footprint "eagle-import:R0805")
      (fields (field (name "MPN") "RC0805FR-0710KL"))
      (libsource (lib "eagle-import") (part "SMD-RES-10K-1%-1/8W(0805)"))
    )
    (comp (ref "R287")
      (value "104")
      (footprint "eagle-import:R0805")
      (fields (field (name "MPN") "RC0805FR-0710KL"))
      (libsource (lib "eagle-import") (part "SMD-RES-10K-1%-1/8W(0805)"))
    )
    (comp (ref "R288")
      (value "104")
      (footprint "eagle-import:R0805")
      (fields (field (name "MPN") "RC0805FR-0710KL"))
      (libsource (lib "eagle-import") (part "SMD-RES-10K-1%-1/8W(0805)"))
    )
    (comp (ref "R289")
      (value "1502")
      (footprint "eagle-import:R0805")
      (fields (field (name "MPN") "RC0805FR-0710KL"))
      (libsource (lib "eagle-import") (part "SMD-RES-10K-1%-1/8W(0805)"))
    )
    (comp (ref "R290")
      (value "1002")
      (footprint "eagle-import:R0805")
      (fields (field (name "MPN") "RC0805FR-0710KL"))
      (libsource (lib "eagle-import") (part "SMD-RES-10K-1%-1/8W(0805)"))
    )
    (comp (ref "R291")
      (value "2201")
      (footprint "eagle-import:R0805")
      (fields (field (name "MPN") "RC0805JR-072K2L"))
      (libsource (lib "eagle-import") (part "SMD-RES-2.2K-5%-1/8W(0805)"))
    )
    (comp (ref "R292")
      (value "1002")
      (footprint "eagle-import:R0805")
      (fields (field (name "MPN") "RC0805FR-0710KL"))
      (libsource (lib "eagle-import") (part "SMD-RES-10K-1%-1/8W(0805)"))
    )
    (comp (ref "R293")
      (value "4701")
      (footprint "eagle-import:R0805")
      (fields (field (name "MPN") "RC0805JR-074K7L"))
      (libsource (lib "eagle-import") (part "SMD-RES-4.7K-5%-1/8W(0805)"))
    )
    (comp (ref "R294")
      (value "2702")
      (footprint "eagle-import:R0805")
      (fields (field (name "MPN") "RC0805JR-074K7L"))
      (libsource (lib "eagle-import") (part "SMD-RES-4.7K-5%-1/8W(0805)"))
    )
    (comp (ref "R295")
      (value "102")
      (footprint "eagle-import:R0805")
      (fields (field (name "MPN") "RC0805JR-071KL"))
      (libsource (lib "eagle-import") (part "SMD-RES-1K-5%-1/8W(0805)"))
    )
    (comp (ref "R296")
      (value "R_user")
      (footprint "eagle-import:R0805")
      (libsource (lib "eagle-import") (part "R-EU_R0805"))
    )
    (comp (ref "R297")
      (value "100")
      (footprint "eagle-import:R0805")
      (fields (field (name "MPN") "RC0805JR-07220RL"))
      (libsource (lib "eagle-import") (part "SMD-RES-220R-5%-1/8W(0805)"))
    )
    (comp (ref "R298")
      (value "(101)")
      (footprint "eagle-import:R0805")
      (fields (field (name "MPN") "RC0805JR-07100RL"))
      (libsource (lib "eagle-import") (part "SMD-RES-100R-5%-1/8W(0805)"))
    )
    (comp (ref "R299")
      (value "(1000)")
      (footprint "eagle-import:R0805")
      (fields (field (name "MPN") "RC0805JR-07100RL"))
      (libsource (lib "eagle-import") (part "SMD-RES-100R-5%-1/8W(0805)"))
    )
    (comp (ref "R300")
      (value "102")
      (footprint "eagle-import:R0805")
      (fields (field (name "MPN") "RC0805JR-071KL"))
      (libsource (lib "eagle-import") (part "SMD-RES-1K-5%-1/8W(0805)"))
    )
    (comp (ref "R301")
      (value "13")
      (footprint "eagle-import:R1206")
      (fields (field (name "MPN") "RC1206JR-0713RL"))
      (libsource (lib "eagle-import") (part "SMD-RES-13R-5%-1/4W(1206)"))
    )
    (comp (ref "R302")
      (value "13")
      (footprint "eagle-import:R1206")
      (fields (field (name "MPN") "RC1206JR-0713RL"))
      (libsource (lib "eagle-import") (part "SMD-RES-13R-5%-1/4W(1206)"))
    )
    (comp (ref "R303")
      (value "2702")
      (footprint "eagle-import:R0805")
      (fields (field (name "MPN") "RC0805JR-074K7L"))
      (libsource (lib "eagle-import") (part "SMD-RES-4.7K-5%-1/8W(0805)"))
    )
    (comp (ref "R304")
      (value "4701")
      (footprint "eagle-import:R0805")
      (fields (field (name "MPN") "RC0805JR-074K7L"))
      (libsource (lib "eagle-import") (part "SMD-RES-4.7K-5%-1/8W(0805)"))
    )
    (comp (ref "R305")
      (value "100")
      (footprint "eagle-import:R0805")
      (fields (field (name "MPN") "RC0805JR-072K2L"))
      (libsource (lib "eagle-import") (part "SMD-RES-2.2K-5%-1/8W(0805)"))
    )
    (comp (ref "R306")
      (value "(101)")
      (footprint "eagle-import:R0805")
      (fields (field (name "MPN") "RC0805JR-072K2L"))
      (libsource (lib "eagle-import") (part "SMD-RES-2.2K-5%-1/8W(0805)"))
    )
    (comp (ref "R307")
      (value "104")
      (footprint "eagle-import:R0805")
      (fields (field (name "MPN") "RC0805FR-0710KL"))
      (libsource (lib "eagle-import") (part "SMD-RES-10K-1%-1/8W(0805)"))
    )
    (comp (ref "R308")
      (value "104")
      (footprint "eagle-import:R0805")
      (fields (field (name "MPN") "RC0805FR-0710KL"))
      (libsource (lib "eagle-import") (part "SMD-RES-10K-1%-1/8W(0805)"))
    )
    (comp (ref "R309")
      (value "(1002)")
      (footprint "eagle-import:R0805")
      (fields (field (name "MPN") "RC0805FR-0710KL"))
      (libsource (lib "eagle-import") (part "SMD-RES-10K-1%-1/8W(0805)"))
    )
    (comp (ref "R310")
      (value "2702")
      (footprint "eagle-import:R0805")
      (fields (field (name "MPN") "RC0805FR-0710KL"))
      (libsource (lib "eagle-import") (part "SMD-RES-10K-1%-1/8W(0805)"))
    )
    (comp (ref "R311")
      (value "47")
      (footprint "eagle-import:V235_17_1MM")
      (libsource (lib "eagle-import") (part "R-EU_V235/17_1MM"))
    )
    (comp (ref "R312")
      (value "47")
      (footprint "eagle-import:V235_17_1MM")
      (libsource (lib "eagle-import") (part "R-EU_V235/17_1MM"))
    )
    (comp (ref "R313")
      (value "2702")
      (footprint "eagle-import:R0805")
      (fields (field (name "MPN") "RC0805JR-074K7L"))
      (libsource (lib "eagle-import") (part "SMD-RES-4.7K-5%-1/8W(0805)"))
    )
    (comp (ref "R314")
      (value "2201")
      (footprint "eagle-import:R0805")
      (fields (field (name "MPN") "RC0805JR-072K2L"))
      (libsource (lib "eagle-import") (part "SMD-RES-2.2K-5%-1/8W(0805)"))
    )
    (comp (ref "R315")
      (value "(1002)")
      (footprint "eagle-import:R0805")
      (fields (field (name "MPN") "RC0805JR-074K7L"))
      (libsource (lib "eagle-import") (part "SMD-RES-4.7K-5%-1/8W(0805)"))
    )
    (comp (ref "R316")
      (value "1002")
      (footprint "eagle-import:R0805")
      (fields (field (name "MPN") "RC0805FR-0710KL"))
      (libsource (lib "eagle-import") (part "SMD-RES-10K-1%-1/8W(0805)"))
    )
    (comp (ref "R317")
      (value "102")
      (footprint "eagle-import:R0805")
      (fields (field (name "MPN") "RC0805JR-071KL"))
      (libsource (lib "eagle-import") (part "SMD-RES-1K-5%-1/8W(0805)"))
    )
    (comp (ref "R318")
      (value "2702")
      (footprint "eagle-import:R0805")
      (fields (field (name "MPN") "RC0805JR-074K7L"))
      (libsource (lib "eagle-import") (part "SMD-RES-4.7K-5%-1/8W(0805)"))
    )
    (comp (ref "R319")
      (value "102")
      (footprint "eagle-import:R0805")
      (fields (field (name "MPN") "RC0805JR-071KL"))
      (libsource (lib "eagle-import") (part "SMD-RES-1K-5%-1/8W(0805)"))
    )
    (comp (ref "R320")
      (value "102")
      (footprint "eagle-import:R0805")
      (fields (field (name "MPN") "RC0805JR-071KL"))
      (libsource (lib "eagle-import") (part "SMD-RES-1K-5%-1/8W(0805)"))
    )
    (comp (ref "R321")
      (value "13")
      (footprint "eagle-import:R1206")
      (fields (field (name "MPN") "RC1206JR-0713RL"))
      (libsource (lib "eagle-import") (part "SMD-RES-13R-5%-1/4W(1206)"))
    )
    (comp (ref "R322")
      (value "R_user")
      (footprint "eagle-import:R0805")
      (libsource (lib "eagle-import") (part "R-EU_R0805"))
    )
    (comp (ref "SJ7") (value "SJ") (footprint "eagle-import:SJ") (libsource (lib "eagle-import") (part "SJ")))
    (comp (ref "START6")
      (value "TPSB2.0")
      (footprint "eagle-import:B2.0")
      (libsource (lib "eagle-import") (part "TPSB2.0"))
    )
    (comp (ref "TP139")
      (value "TPSB2.0")
      (footprint "eagle-import:B2.0")
      (libsource (lib "eagle-import") (part "TPSB2.0"))
    )
    (comp (ref "TP140")
      (value "TPSB2.0")
      (footprint "eagle-import:B2.0")
      (libsource (lib "eagle-import") (part "TPSB2.0"))
    )
    (comp (ref "TP141")
      (value "TPSB2.0")
      (footprint "eagle-import:B2.0")
      (libsource (lib "eagle-import") (part "TPSB2.0"))
    )
    (comp (ref "TP142")
      (value "TPSB2.0")
      (footprint "eagle-import:B2.0")
      (libsource (lib "eagle-import") (part "TPSB2.0"))
    )
    (comp (ref "TP143")
      (value "TPSB2.0")
      (footprint "eagle-import:B2.0")
      (libsource (lib "eagle-import") (part "TPSB2.0"))
    )
    (comp (ref "TP144")
      (value "TPSB2.0")
      (footprint "eagle-import:B2.0")
      (libsource (lib "eagle-import") (part "TPSB2.0"))
    )
    (comp (ref "TP145")
      (value "TPSB2.0")
      (footprint "eagle-import:B2.0")
      (libsource (lib "eagle-import") (part "TPSB2.0"))
    )
    (comp (ref "TP146")
      (value "TPSB2.0")
      (footprint "eagle-import:B2.0")
      (libsource (lib "eagle-import") (part "TPSB2.0"))
    )
    (comp (ref "TP147")
      (value "TPSB2.0")
      (footprint "eagle-import:B2.0")
      (libsource (lib "eagle-import") (part "TPSB2.0"))
    )
    (comp (ref "TP148")
      (value "TPSB2.0")
      (footprint "eagle-import:B2.0")
      (libsource (lib "eagle-import") (part "TPSB2.0"))
    )
    (comp (ref "TP149")
      (value "TPSB2.0")
      (footprint "eagle-import:B2.0")
      (libsource (lib "eagle-import") (part "TPSB2.0"))
    )
    (comp (ref "TP150")
      (value "TPSB2.0")
      (footprint "eagle-import:B2.0")
      (libsource (lib "eagle-import") (part "TPSB2.0"))
    )
    (comp (ref "TP151")
      (value "TPSB2.0")
      (footprint "eagle-import:B2.0")
      (libsource (lib "eagle-import") (part "TPSB2.0"))
    )
    (comp (ref "TP152")
      (value "TPSB2.0")
      (footprint "eagle-import:B2.0")
      (libsource (lib "eagle-import") (part "TPSB2.0"))
    )
    (comp (ref "TP153")
      (value "TPSB2.0")
      (footprint "eagle-import:B2.0")
      (libsource (lib "eagle-import") (part "TPSB2.0"))
    )
    (comp (ref "TP154")
      (value "TPSB2.0")
      (footprint "eagle-import:B2.0")
      (libsource (lib "eagle-import") (part "TPSB2.0"))
    )
    (comp (ref "TP155")
      (value "TPSB2.0")
      (footprint "eagle-import:B2.0")
      (libsource (lib "eagle-import") (part "TPSB2.0"))
    )
    (comp (ref "TP156")
      (value "TPSB2.0")
      (footprint "eagle-import:B2.0")
      (libsource (lib "eagle-import") (part "TPSB2.0"))
    )
    (comp (ref "TP157")
      (value "TPSB1,27")
      (footprint "eagle-import:B1,27")
      (libsource (lib "eagle-import") (part "TPSB1,27"))
    )
    (comp (ref "TP158")
      (value "TPSB2.0")
      (footprint "eagle-import:B2.0")
      (libsource (lib "eagle-import") (part "TPSB2.0"))
    )
    (comp (ref "TP159")
      (value "TPSB2.0")
      (footprint "eagle-import:B2.0")
      (libsource (lib "eagle-import") (part "TPSB2.0"))
    )
    (comp (ref "TP160")
      (value "TPSB2.0")
      (footprint "eagle-import:B2.0")
      (libsource (lib "eagle-import") (part "TPSB2.0"))
    )
    (comp (ref "TP161")
      (value "TPSB2.0")
      (footprint "eagle-import:B2.0")
      (libsource (lib "eagle-import") (part "TPSB2.0"))
    )
    (comp (ref "X19")
      (value "CON_BMWV2")
      (footprint "eagle-import:24-PIN_V2")
      (libsource (lib "eagle-import") (part "CON_BMWV2"))
    )
    (comp (ref "X20")
      (value "22-23-2051")
      (footprint "eagle-import:22-23-2051")
      (fields (field (name "MF") "MOLEX"))
      (libsource (lib "eagle-import") (part "22-23-2051"))
    )
    (comp (ref "X21")
      (value "22-23-2021")
      (footprint "eagle-import:22-23-2021")
      (fields (field (name "MF") "MOLEX"))
      (libsource (lib "eagle-import") (part "22-23-2021"))
    )
    (comp (ref "1")
      (value "2081-1132")
      (footprint "eagle-import:12-PIN")
      (libsource (lib "eagle-import") (part "2081-1132"))
    )
    (comp (ref "2")
      (value "2081-1132")
      (footprint "eagle-import:12-PIN")
      (libsource (lib "eagle-import") (part "2081-1132"))
    )
    (comp (ref "6V")
      (value "TPSB2.0")
      (footprint "eagle-import:B2.0")
      (libsource (lib "eagle-import") (part "TPSB2.0"))
    )
    (comp (ref "10V")
      (value "TPSB2.0")
      (footprint "eagle-import:B2.0")
      (libsource (lib "eagle-import") (part "TPSB2.0"))
    )
    (comp (ref "C1")
      (value "4.7u")
      (footprint "eagle-import:C0805")
      (fields (field (name "MPN") "CC0805KKX5R8BB475"))
      (libsource (lib "eagle-import") (part "CERAMIC-4.7UF-25V-10%-X5R(0805)"))
    )
    (comp (ref "C2")
      (value "100nF")
      (footprint "eagle-import:C0805")
      (fields (field (name "MPN") "CC0805KRX7R9BB104"))
      (libsource (lib "eagle-import") (part "CERAMIC-100NF-50V-10%-X7R(0805)"))
    )
    (comp (ref "C3")
      (value "100nF,")
      (footprint "eagle-import:C0805")
      (fields (field (name "MPN") "CC0805KRX7R9BB104"))
      (libsource (lib "eagle-import") (part "CERAMIC-100NF-50V-10%-X7R(0805)"))
    )
    (comp (ref "C4")
      (value "100nF,")
      (footprint "eagle-import:C0805")
      (fields (field (name "MPN") "CC0805KRX7R9BB104"))
      (libsource (lib "eagle-import") (part "CERAMIC-100NF-50V-10%-X7R(0805)"))
    )
    (comp (ref "C5")
      (value "100nF.")
      (footprint "eagle-import:C0805")
      (fields (field (name "MPN") "CC0805KRX7R9BB104"))
      (libsource (lib "eagle-import") (part "CERAMIC-100NF-50V-10%-X7R(0805)"))
    )
    (comp (ref "C6")
      (value "100nF.")
      (footprint "eagle-import:C0805")
      (fields (field (name "MPN") "CC0805KRX7R9BB104"))
      (libsource (lib "eagle-import") (part "CERAMIC-100NF-50V-10%-X7R(0805)"))
    )
    (comp (ref "C7")
      (value "100u")
      (footprint "eagle-import:C1206")
      (fields (field (name "MPN") "GRM31CR60J107ME39L"))
      (libsource (lib "eagle-import") (part "CERAMIC-100UF-6.3V-20%-X5R(1206)"))
    )
    (comp (ref "C8")
      (value "100u")
      (footprint "eagle-import:C1206")
      (fields (field (name "MPN") "GRM31CR60J107ME39L"))
      (libsource (lib "eagle-import") (part "CERAMIC-100UF-6.3V-20%-X5R(1206)"))
    )
    (comp (ref "C9")
      (value "2.2nF")
      (footprint "eagle-import:C0805")
      (fields (field (name "MPN") "CC0805KRX7R9BB104"))
      (libsource (lib "eagle-import") (part "CERAMIC-100NF-50V-10%-X7R(0805)"))
    )
    (comp (ref "C10")
      (value "100nF")
      (footprint "eagle-import:C0805")
      (fields (field (name "MPN") "CC0805KRX7R9BB104"))
      (libsource (lib "eagle-import") (part "CERAMIC-100NF-50V-10%-X7R(0805)"))
    )
    (comp (ref "D1")
      (value "SM6T")
      (footprint "eagle-import:DO214AA")
      (libsource (lib "eagle-import") (part "SM6T"))
    )
    (comp (ref "D2")
      (value "1N4007,")
      (footprint "eagle-import:DO-214AC")
      (fields (field (name "MPN") "1N4007"))
      (libsource (lib "eagle-import") (part "DIODE-GEN-PURPOSE-1KV-1A(DO-214AC)"))
    )
    (comp (ref "D3")
      (value "1N4007,")
      (footprint "eagle-import:DO-214AC")
      (fields (field (name "MPN") "1N4007"))
      (libsource (lib "eagle-import") (part "DIODE-GEN-PURPOSE-1KV-1A(DO-214AC)"))
    )
    (comp (ref "D4")
      (value "SM6TDO214AA_BI")
      (footprint "eagle-import:DO214AA_BI")
      (libsource (lib "eagle-import") (part "SM6TDO214AA_BI"))
    )
    (comp (ref "D5")
      (value "1N4007.")
      (footprint "eagle-import:DO-214AC")
      (fields (field (name "MPN") "1N4007"))
      (libsource (lib "eagle-import") (part "DIODE-GEN-PURPOSE-1KV-1A(DO-214AC)"))
    )
    (comp (ref "D6")
      (value "1N4007.")
      (footprint "eagle-import:DO-214AC")
      (fields (field (name "MPN") "1N4007"))
      (libsource (lib "eagle-import") (part "DIODE-GEN-PURPOSE-1KV-1A(DO-214AC)"))
    )
    (comp (ref "D7")
      (value "1N5817")
      (footprint "eagle-import:DO-214AC_SLIM")
      (libsource (lib "eagle-import") (part "DIODE-GEN-PURPOSE-1KV-1A(DO-214AC)DO-214AC/1206"))
    )
    (comp (ref "D8")
      (value "1N5817.")
      (footprint "eagle-import:DO-214AC_SLIM")
      (libsource (lib "eagle-import") (part "DIODE-GEN-PURPOSE-1KV-1A(DO-214AC)DO-214AC/1206"))
    )
    (comp (ref "D9")
      (value "1N5817.")
      (footprint "eagle-import:DO-214AC_SLIM")
      (libsource (lib "eagle-import") (part "DIODE-GEN-PURPOSE-1KV-1A(DO-214AC)DO-214AC/1206"))
    )
    (comp (ref "D10")
      (value "1N5817")
      (footprint "eagle-import:DO-214AC_SLIM")
      (libsource (lib "eagle-import") (part "DIODE-GEN-PURPOSE-1KV-1A(DO-214AC)DO-214AC/1206"))
    )
    (comp (ref "D11")
      (value "1N4007")
      (footprint "eagle-import:DO-214AC")
      (libsource (lib "eagle-import") (part "DIODE-GEN-PURPOSE-1KV-1A(DO-214AC)"))
    )
    (comp (ref "D12")
      (value "1N4007")
      (footprint "eagle-import:DO-214AC")
      (libsource (lib "eagle-import") (part "DIODE-GEN-PURPOSE-1KV-1A(DO-214AC)"))
    )
    (comp (ref "FID1")
      (value "FIDUCIAL")
      (footprint "eagle-import:FIDUCIAL_1MM")
      (libsource (lib "eagle-import") (part "FIDUCIAL"))
    )
    (comp (ref "FID2")
      (value "FIDUCIAL")
      (footprint "eagle-import:FIDUCIAL_1MM")
      (libsource (lib "eagle-import") (part "FIDUCIAL"))
    )
    (comp (ref "FID3")
      (value "FIDUCIAL")
      (footprint "eagle-import:FIDUCIAL_1MM")
      (libsource (lib "eagle-import") (part "FIDUCIAL"))
    )
    (comp (ref "FID4")
      (value "FIDUCIAL")
      (footprint "eagle-import:FIDUCIAL_1MM")
      (libsource (lib "eagle-import") (part "FIDUCIAL"))
    )
    (comp (ref "FID49")
      (value "FIDUCIAL")
      (footprint "eagle-import:FIDUCIAL_1MM")
      (libsource (lib "eagle-import") (part "FIDUCIAL"))
    )
    (comp (ref "FID50")
      (value "FIDUCIAL")
      (footprint "eagle-import:FIDUCIAL_1MM")
      (libsource (lib "eagle-import") (part "FIDUCIAL"))
    )
    (comp (ref "FID51")
      (value "FIDUCIAL")
      (footprint "eagle-import:FIDUCIAL_1MM")
      (libsource (lib "eagle-import") (part "FIDUCIAL"))
    )
    (comp (ref "FID52")
      (value "FIDUCIAL")
      (footprint "eagle-import:FIDUCIAL_1MM")
      (libsource (lib "eagle-import") (part "FIDUCIAL"))
    )
    (comp (ref "IC1")
      (value "LM2904")
      (footprint "eagle-import:SO08")
      (libsource (lib "eagle-import") (part "LM358D"))
    )
    (comp (ref "IC2")
      (value "78L06")
      (footprint "eagle-import:SOT89_ROUND")
      (libsource (lib "eagle-import") (part "78LXXSOT89_ROUND"))
    )
    (comp (ref "IC3")
      (value "6V pos")
      (footprint "eagle-import:78LXX")
      (libsource (lib "eagle-import") (part "v-reg_78LXX"))
    )
    (comp (ref "IC4")
      (value "78L10")
      (footprint "eagle-import:SOT89_ROUND")
      (libsource (lib "eagle-import") (part "78LXXSOT89_ROUND"))
    )
    (comp (ref "IC5")
      (value "4028")
      (footprint "eagle-import:SO16")
      (libsource (lib "eagle-import") (part "4028D"))
    )
    (comp (ref "IC7")
      (value "ULN2004")
      (footprint "eagle-import:SO16")
      (libsource (lib "eagle-import") (part "ULN2004AD"))
    )
    (comp (ref "IC8")
      (value "LM339")
      (footprint "eagle-import:SO14")
      (libsource (lib "eagle-import") (part "LM339D"))
    )
    (comp (ref "IC9")
      (value "317TO202H_NOHOLE")
      (footprint "eagle-import:TO220H_NOHOLE")
      (libsource (lib "eagle-import") (part "317TO202H_NOHOLE"))
    )
    (comp (ref "IC10")
      (value "555")
      (footprint "eagle-import:SO08")
      (libsource (lib "eagle-import") (part "555DNE"))
    )
    (comp (ref "IC11")
      (value "4538")
      (footprint "eagle-import:SO16")
      (libsource (lib "eagle-import") (part "4538D"))
    )
    (comp (ref "JP1")
      (value "JP2EJP2_SMALLPADS")
      (footprint "eagle-import:JP2_SMALLPADS")
      (libsource (lib "eagle-import") (part "JP2EJP2_SMALLPADS"))
    )
    (comp (ref "JP2")
      (value "JP2EJP2_SMALLPADS")
      (footprint "eagle-import:JP2_SMALLPADS")
      (libsource (lib "eagle-import") (part "JP2EJP2_SMALLPADS"))
    )
    (comp (ref "JP3")
      (value "JP2EJP2_SMALLPADS")
      (footprint "eagle-import:JP2_SMALLPADS")
      (libsource (lib "eagle-import") (part "JP2EJP2_SMALLPADS"))
    )
    (comp (ref "JP4")
      (value "JP2EJP2_SMALLPADS")
      (footprint "eagle-import:JP2_SMALLPADS")
      (libsource (lib "eagle-import") (part "JP2EJP2_SMALLPADS"))
    )
    (comp (ref "JP5")
      (value "JP2E_ORIG")
      (footprint "eagle-import:JP2_ORIG_SMALLPADS")
      (libsource (lib "eagle-import") (part "JP2E_ORIG"))
    )
    (comp (ref "LED1")
      (value "LEDLD260")
      (footprint "eagle-import:LD260")
      (libsource (lib "eagle-import") (part "LEDLD260"))
    )
    (comp (ref "LED2")
      (value "LEDLD260")
      (footprint "eagle-import:LD260")
      (libsource (lib "eagle-import") (part "LEDLD260"))
    )
    (comp (ref "LED3")
      (value "LEDLD260")
      (footprint "eagle-import:LD260")
      (libsource (lib "eagle-import") (part "LEDLD260"))
    )
    (comp (ref "LED4")
      (value "LEDLD260")
      (footprint "eagle-import:LD260")
      (libsource (lib "eagle-import") (part "LEDLD260"))
    )
    (comp (ref "LED5")
      (value "LEDLD260")
      (footprint "eagle-import:LD260")
      (libsource (lib "eagle-import") (part "LEDLD260"))
    )
    (comp (ref "LED6")
      (value "LEDLD260")
      (footprint "eagle-import:LD260")
      (libsource (lib "eagle-import") (part "LEDLD260"))
    )
    (comp (ref "Q1")
      (value "BA.")
      (footprint "eagle-import:SOT89")
      (libsource (lib "eagle-import") (part "PNP-TRANSISTOR_SOT89"))
    )
    (comp (ref "Q2")
      (value "BA.")
      (footprint "eagle-import:SOT89")
      (libsource (lib "eagle-import") (part "PNP-TRANSISTOR_SOT89"))
    )
    (comp (ref "Q3")
      (value "MY")
      (footprint "eagle-import:SOT89")
      (libsource (lib "eagle-import") (part "NPN-TRANSISTOR_SOT89"))
    )
    (comp (ref "Q4")
      (value "BA")
      (footprint "eagle-import:SOT89")
      (libsource (lib "eagle-import") (part "PNP-TRANSISTOR_SOT89"))
    )
    (comp (ref "Q5")
      (value "BA")
      (footprint "eagle-import:SOT89")
      (libsource (lib "eagle-import") (part "PNP-TRANSISTOR_SOT89"))
    )
    (comp (ref "Q6")
      (value "J1")
      (footprint "eagle-import:SOT-23")
      (fields (field (name "MPN") "BSS138W-7-F"))
      (libsource (lib "eagle-import") (part "SMD-MOSFET-N-CH-50V-200MA-BSS138W-7-F(SOT-23)"))
    )
    (comp (ref "Q7")
      (value "J1")
      (footprint "eagle-import:SOT-23")
      (fields (field (name "MPN") "BSS138W-7-F"))
      (libsource (lib "eagle-import") (part "SMD-MOSFET-N-CH-50V-200MA-BSS138W-7-F(SOT-23)"))
    )
    (comp (ref "R1")
      (value "102")
      (footprint "eagle-import:R0805")
      (fields (field (name "MPN") "RC0805JR-071KL"))
      (libsource (lib "eagle-import") (part "SMD-RES-1K-5%-1/8W(0805)"))
    )
    (comp (ref "R2")
      (value "13")
      (footprint "eagle-import:R1206")
      (fields (field (name "MPN") "RC1206JR-0713RL"))
      (libsource (lib "eagle-import") (part "SMD-RES-13R-5%-1/4W(1206)"))
    )
    (comp (ref "R3")
      (value "R_user")
      (footprint "eagle-import:R0805")
      (libsource (lib "eagle-import") (part "R-EU_R0805"))
    )
    (comp (ref "R4")
      (value "R_user")
      (footprint "eagle-import:R0805")
      (libsource (lib "eagle-import") (part "R-EU_R0805"))
    )
    (comp (ref "R5")
      (value "4701")
      (footprint "eagle-import:R0805")
      (fields (field (name "MPN") "RC0805JR-074K7L"))
      (libsource (lib "eagle-import") (part "SMD-RES-4.7K-5%-1/8W(0805)"))
    )
    (comp (ref "R6")
      (value "13")
      (footprint "eagle-import:R1206")
      (fields (field (name "MPN") "RC1206JR-0713RL"))
      (libsource (lib "eagle-import") (part "SMD-RES-13R-5%-1/4W(1206)"))
    )
    (comp (ref "R7")
      (value "1002")
      (footprint "eagle-import:R0805")
      (fields (field (name "MPN") "RC0805FR-0710KL"))
      (libsource (lib "eagle-import") (part "SMD-RES-10K-1%-1/8W(0805)"))
    )
    (comp (ref "R8")
      (value "1002")
      (footprint "eagle-import:R0805")
      (fields (field (name "MPN") "RC0805FR-0710KL"))
      (libsource (lib "eagle-import") (part "SMD-RES-10K-1%-1/8W(0805)"))
    )
    (comp (ref "R9")
      (value "104")
      (footprint "eagle-import:R0805")
      (fields (field (name "MPN") "RC0805FR-0710KL"))
      (libsource (lib "eagle-import") (part "SMD-RES-10K-1%-1/8W(0805)"))
    )
    (comp (ref "R10")
      (value "104")
      (footprint "eagle-import:R0805")
      (fields (field (name "MPN") "RC0805FR-0710KL"))
      (libsource (lib "eagle-import") (part "SMD-RES-10K-1%-1/8W(0805)"))
    )
    (comp (ref "R11")
      (value "104")
      (footprint "eagle-import:R0805")
      (fields (field (name "MPN") "RC0805FR-0710KL"))
      (libsource (lib "eagle-import") (part "SMD-RES-10K-1%-1/8W(0805)"))
    )
    (comp (ref "R12")
      (value "102")
      (footprint "eagle-import:R0805")
      (fields (field (name "MPN") "RC0805JR-071KL"))
      (libsource (lib "eagle-import") (part "SMD-RES-1K-5%-1/8W(0805)"))
    )
    (comp (ref "R13")
      (value "102")
      (footprint "eagle-import:R0805")
      (fields (field (name "MPN") "RC0805JR-071KL"))
      (libsource (lib "eagle-import") (part "SMD-RES-1K-5%-1/8W(0805)"))
    )
    (comp (ref "R14")
      (value "102")
      (footprint "eagle-import:R0805")
      (fields (field (name "MPN") "RC0805JR-071KL"))
      (libsource (lib "eagle-import") (part "SMD-RES-1K-5%-1/8W(0805)"))
    )
    (comp (ref "R15")
      (value "100")
      (footprint "eagle-import:R0805")
      (fields (field (name "MPN") "RC0805JR-07220RL"))
      (libsource (lib "eagle-import") (part "SMD-RES-220R-5%-1/8W(0805)"))
    )
    (comp (ref "R16")
      (value "4701")
      (footprint "eagle-import:R0805")
      (fields (field (name "MPN") "RC0805JR-074K7L"))
      (libsource (lib "eagle-import") (part "SMD-RES-4.7K-5%-1/8W(0805)"))
    )
    (comp (ref "R17")
      (value "2702")
      (footprint "eagle-import:R0805")
      (fields (field (name "MPN") "RC0805JR-074K7L"))
      (libsource (lib "eagle-import") (part "SMD-RES-4.7K-5%-1/8W(0805)"))
    )
    (comp (ref "R18")
      (value "13")
      (footprint "eagle-import:R1206")
      (fields (field (name "MPN") "RC1206JR-0713RL"))
      (libsource (lib "eagle-import") (part "SMD-RES-13R-5%-1/4W(1206)"))
    )
    (comp (ref "R19")
      (value "2201")
      (footprint "eagle-import:R0805")
      (fields (field (name "MPN") "RC0805JR-072K2L"))
      (libsource (lib "eagle-import") (part "SMD-RES-2.2K-5%-1/8W(0805)"))
    )
    (comp (ref "R20")
      (value "1002")
      (footprint "eagle-import:R0805")
      (fields (field (name "MPN") "RC0805FR-0710KL"))
      (libsource (lib "eagle-import") (part "SMD-RES-10K-1%-1/8W(0805)"))
    )
    (comp (ref "R21")
      (value "1502")
      (footprint "eagle-import:R0805")
      (fields (field (name "MPN") "RC0805FR-0710KL"))
      (libsource (lib "eagle-import") (part "SMD-RES-10K-1%-1/8W(0805)"))
    )
    (comp (ref "R22")
      (value "2702")
      (footprint "eagle-import:R0805")
      (fields (field (name "MPN") "RC0805JR-074K7L"))
      (libsource (lib "eagle-import") (part "SMD-RES-4.7K-5%-1/8W(0805)"))
    )
    (comp (ref "R23")
      (value "2702")
      (footprint "eagle-import:R0805")
      (fields (field (name "MPN") "RC0805JR-074K7L"))
      (libsource (lib "eagle-import") (part "SMD-RES-4.7K-5%-1/8W(0805)"))
    )
    (comp (ref "R24")
      (value "1002")
      (footprint "eagle-import:R0805")
      (fields (field (name "MPN") "RC0805FR-0710KL"))
      (libsource (lib "eagle-import") (part "SMD-RES-10K-1%-1/8W(0805)"))
    )
    (comp (ref "R25")
      (value "104")
      (footprint "eagle-import:R0805")
      (fields (field (name "MPN") "RC0805FR-0710KL"))
      (libsource (lib "eagle-import") (part "SMD-RES-10K-1%-1/8W(0805)"))
    )
    (comp (ref "R26")
      (value "4701")
      (footprint "eagle-import:R0805")
      (fields (field (name "MPN") "RC0805JR-074K7L"))
      (libsource (lib "eagle-import") (part "SMD-RES-4.7K-5%-1/8W(0805)"))
    )
    (comp (ref "R27")
      (value "47")
      (footprint "eagle-import:V235_17_1MM")
      (libsource (lib "eagle-import") (part "R-EU_V235/17_1MM"))
    )
    (comp (ref "R28")
      (value "102")
      (footprint "eagle-import:R0805")
      (fields (field (name "MPN") "RC0805JR-071KL"))
      (libsource (lib "eagle-import") (part "SMD-RES-1K-5%-1/8W(0805)"))
    )
    (comp (ref "R29")
      (value "47")
      (footprint "eagle-import:V235_17_1MM")
      (libsource (lib "eagle-import") (part "R-EU_V235/17_1MM"))
    )
    (comp (ref "R30")
      (value "104")
      (footprint "eagle-import:R0805")
      (fields (field (name "MPN") "RC0805FR-0710KL"))
      (libsource (lib "eagle-import") (part "SMD-RES-10K-1%-1/8W(0805)"))
    )
    (comp (ref "R31")
      (value "1502")
      (footprint "eagle-import:R0805")
      (fields (field (name "MPN") "RC0805FR-0710KL"))
      (libsource (lib "eagle-import") (part "SMD-RES-10K-1%-1/8W(0805)"))
    )
    (comp (ref "R32")
      (value "1002")
      (footprint "eagle-import:R0805")
      (fields (field (name "MPN") "RC0805FR-0710KL"))
      (libsource (lib "eagle-import") (part "SMD-RES-10K-1%-1/8W(0805)"))
    )
    (comp (ref "R33")
      (value "2201")
      (footprint "eagle-import:R0805")
      (fields (field (name "MPN") "RC0805JR-072K2L"))
      (libsource (lib "eagle-import") (part "SMD-RES-2.2K-5%-1/8W(0805)"))
    )
    (comp (ref "R34")
      (value "13")
      (footprint "eagle-import:R1206")
      (fields (field (name "MPN") "RC1206JR-0713RL"))
      (libsource (lib "eagle-import") (part "SMD-RES-13R-5%-1/4W(1206)"))
    )
    (comp (ref "R35")
      (value "104")
      (footprint "eagle-import:R0805")
      (fields (field (name "MPN") "RC0805FR-0710KL"))
      (libsource (lib "eagle-import") (part "SMD-RES-10K-1%-1/8W(0805)"))
    )
    (comp (ref "R36")
      (value "47")
      (footprint "eagle-import:V235_17_1MM")
      (libsource (lib "eagle-import") (part "R-EU_V235/17_1MM"))
    )
    (comp (ref "R37")
      (value "47")
      (footprint "eagle-import:V235_17_1MM")
      (libsource (lib "eagle-import") (part "R-EU_V235/17_1MM"))
    )
    (comp (ref "R38")
      (value "100")
      (footprint "eagle-import:R0805")
      (fields (field (name "MPN") "RC0805JR-072K2L"))
      (libsource (lib "eagle-import") (part "SMD-RES-2.2K-5%-1/8W(0805)"))
    )
    (comp (ref "R39")
      (value "(101)")
      (footprint "eagle-import:R0805")
      (fields (field (name "MPN") "RC0805JR-072K2L"))
      (libsource (lib "eagle-import") (part "SMD-RES-2.2K-5%-1/8W(0805)"))
    )
    (comp (ref "R40")
      (value "2702")
      (footprint "eagle-import:R0805")
      (fields (field (name "MPN") "RC0805FR-0710KL"))
      (libsource (lib "eagle-import") (part "SMD-RES-10K-1%-1/8W(0805)"))
    )
    (comp (ref "R41")
      (value "104")
      (footprint "eagle-import:R0805")
      (fields (field (name "MPN") "RC0805FR-0710KL"))
      (libsource (lib "eagle-import") (part "SMD-RES-10K-1%-1/8W(0805)"))
    )
    (comp (ref "R42")
      (value "(1000)")
      (footprint "eagle-import:R0805")
      (fields (field (name "MPN") "RC0805JR-07100RL"))
      (libsource (lib "eagle-import") (part "SMD-RES-100R-5%-1/8W(0805)"))
    )
    (comp (ref "R43")
      (value "(101)")
      (footprint "eagle-import:R0805")
      (fields (field (name "MPN") "RC0805JR-07100RL"))
      (libsource (lib "eagle-import") (part "SMD-RES-100R-5%-1/8W(0805)"))
    )
    (comp (ref "R44")
      (value "(1002)")
      (footprint "eagle-import:R0805")
      (fields (field (name "MPN") "RC0805FR-0710KL"))
      (libsource (lib "eagle-import") (part "SMD-RES-10K-1%-1/8W(0805)"))
    )
    (comp (ref "R45")
      (value "2702")
      (footprint "eagle-import:R0805")
      (fields (field (name "MPN") "RC0805JR-074K7L"))
      (libsource (lib "eagle-import") (part "SMD-RES-4.7K-5%-1/8W(0805)"))
    )
    (comp (ref "R46")
      (value "(1002)")
      (footprint "eagle-import:R0805")
      (fields (field (name "MPN") "RC0805JR-074K7L"))
      (libsource (lib "eagle-import") (part "SMD-RES-4.7K-5%-1/8W(0805)"))
    )
    (comp (ref "SJ1") (value "SJ") (footprint "eagle-import:SJ") (libsource (lib "eagle-import") (part "SJ")))
    (comp (ref "START")
      (value "TPSB2.0")
      (footprint "eagle-import:B2.0")
      (libsource (lib "eagle-import") (part "TPSB2.0"))
    )
    (comp (ref "TP1")
      (value "TPSB2.0")
      (footprint "eagle-import:B2.0")
      (libsource (lib "eagle-import") (part "TPSB2.0"))
    )
    (comp (ref "TP2")
      (value "TPSB2.0")
      (footprint "eagle-import:B2.0")
      (libsource (lib "eagle-import") (part "TPSB2.0"))
    )
    (comp (ref "TP3")
      (value "TPSB2.0")
      (footprint "eagle-import:B2.0")
      (libsource (lib "eagle-import") (part "TPSB2.0"))
    )
    (comp (ref "TP4")
      (value "TPSB2.0")
      (footprint "eagle-import:B2.0")
      (libsource (lib "eagle-import") (part "TPSB2.0"))
    )
    (comp (ref "TP5")
      (value "TPSB2.0")
      (footprint "eagle-import:B2.0")
      (libsource (lib "eagle-import") (part "TPSB2.0"))
    )
    (comp (ref "TP6")
      (value "TPSB2.0")
      (footprint "eagle-import:B2.0")
      (libsource (lib "eagle-import") (part "TPSB2.0"))
    )
    (comp (ref "TP7")
      (value "TPSB2.0")
      (footprint "eagle-import:B2.0")
      (libsource (lib "eagle-import") (part "TPSB2.0"))
    )
    (comp (ref "TP8")
      (value "TPSB2.0")
      (footprint "eagle-import:B2.0")
      (libsource (lib "eagle-import") (part "TPSB2.0"))
    )
    (comp (ref "TP9")
      (value "TPSB2.0")
      (footprint "eagle-import:B2.0")
      (libsource (lib "eagle-import") (part "TPSB2.0"))
    )
    (comp (ref "TP10")
      (value "TPSB2.0")
      (footprint "eagle-import:B2.0")
      (libsource (lib "eagle-import") (part "TPSB2.0"))
    )
    (comp (ref "TP11")
      (value "TPSB2.0")
      (footprint "eagle-import:B2.0")
      (libsource (lib "eagle-import") (part "TPSB2.0"))
    )
    (comp (ref "TP12")
      (value "TPSB2.0")
      (footprint "eagle-import:B2.0")
      (libsource (lib "eagle-import") (part "TPSB2.0"))
    )
    (comp (ref "TP13")
      (value "TPSB2.0")
      (footprint "eagle-import:B2.0")
      (libsource (lib "eagle-import") (part "TPSB2.0"))
    )
    (comp (ref "TP16")
      (value "TPSB2.0")
      (footprint "eagle-import:B2.0")
      (libsource (lib "eagle-import") (part "TPSB2.0"))
    )
    (comp (ref "TP17")
      (value "TPSB2.0")
      (footprint "eagle-import:B2.0")
      (libsource (lib "eagle-import") (part "TPSB2.0"))
    )
    (comp (ref "TP18")
      (value "TPSB2.0")
      (footprint "eagle-import:B2.0")
      (libsource (lib "eagle-import") (part "TPSB2.0"))
    )
    (comp (ref "TP19")
      (value "TPSB2.0")
      (footprint "eagle-import:B2.0")
      (libsource (lib "eagle-import") (part "TPSB2.0"))
    )
    (comp (ref "TP21")
      (value "TPSB2.0")
      (footprint "eagle-import:B2.0")
      (libsource (lib "eagle-import") (part "TPSB2.0"))
    )
    (comp (ref "TP22")
      (value "TPSB2.0")
      (footprint "eagle-import:B2.0")
      (libsource (lib "eagle-import") (part "TPSB2.0"))
    )
    (comp (ref "TP23")
      (value "TPSB2.0")
      (footprint "eagle-import:B2.0")
      (libsource (lib "eagle-import") (part "TPSB2.0"))
    )
    (comp (ref "TP24")
      (value "TPSB1,27")
      (footprint "eagle-import:B1,27")
      (libsource (lib "eagle-import") (part "TPSB1,27"))
    )
    (comp (ref "TP25")
      (value "TPSB2.0")
      (footprint "eagle-import:B2.0")
      (libsource (lib "eagle-import") (part "TPSB2.0"))
    )
    (comp (ref "TP26")
      (value "TPSB2.0")
      (footprint "eagle-import:B2.0")
      (libsource (lib "eagle-import") (part "TPSB2.0"))
    )
    (comp (ref "X1")
      (value "CON_BMWV2")
      (footprint "eagle-import:24-PIN_V2")
      (libsource (lib "eagle-import") (part "CON_BMWV2"))
    )
    (comp (ref "X2")
      (value "22-23-2021")
      (footprint "eagle-import:22-23-2021")
      (fields (field (name "MF") "MOLEX"))
      (libsource (lib "eagle-import") (part "22-23-2021"))
    )
    (comp (ref "X3")
      (value "22-23-2051")
      (footprint "eagle-import:22-23-2051")
      (fields (field (name "MF") "MOLEX"))
      (libsource (lib "eagle-import") (part "22-23-2051"))
    )
    (comp (ref "6V3")
      (value "TPSB2.0")
      (footprint "eagle-import:B2.0")
      (libsource (lib "eagle-import") (part "TPSB2.0"))
    )
    (comp (ref "7")
      (value "2081-1132")
      (footprint "eagle-import:12-PIN")
      (libsource (lib "eagle-import") (part "2081-1132"))
    )
    (comp (ref "8")
      (value "2081-1132")
      (footprint "eagle-import:12-PIN")
      (libsource (lib "eagle-import") (part "2081-1132"))
    )
    (comp (ref "10V3")
      (value "TPSB2.0")
      (footprint "eagle-import:B2.0")
      (libsource (lib "eagle-import") (part "TPSB2.0"))
    )
    (comp (ref "C31")
      (value "100u")
      (footprint "eagle-import:C1206")
      (fields (field (name "MPN") "GRM31CR60J107ME39L"))
      (libsource (lib "eagle-import") (part "CERAMIC-100UF-6.3V-20%-X5R(1206)"))
    )
    (comp (ref "C32")
      (value "100u")
      (footprint "eagle-import:C1206")
      (fields (field (name "MPN") "GRM31CR60J107ME39L"))
      (libsource (lib "eagle-import") (part "CERAMIC-100UF-6.3V-20%-X5R(1206)"))
    )
    (comp (ref "C33")
      (value "100nF,")
      (footprint "eagle-import:C0805")
      (fields (field (name "MPN") "CC0805KRX7R9BB104"))
      (libsource (lib "eagle-import") (part "CERAMIC-100NF-50V-10%-X7R(0805)"))
    )
    (comp (ref "C34")
      (value "4.7u")
      (footprint "eagle-import:C0805")
      (fields (field (name "MPN") "CC0805KKX5R8BB475"))
      (libsource (lib "eagle-import") (part "CERAMIC-4.7UF-25V-10%-X5R(0805)"))
    )
    (comp (ref "C35")
      (value "100nF.")
      (footprint "eagle-import:C0805")
      (fields (field (name "MPN") "CC0805KRX7R9BB104"))
      (libsource (lib "eagle-import") (part "CERAMIC-100NF-50V-10%-X7R(0805)"))
    )
    (comp (ref "C36")
      (value "100nF.")
      (footprint "eagle-import:C0805")
      (fields (field (name "MPN") "CC0805KRX7R9BB104"))
      (libsource (lib "eagle-import") (part "CERAMIC-100NF-50V-10%-X7R(0805)"))
    )
    (comp (ref "C37")
      (value "2.2nF")
      (footprint "eagle-import:C0805")
      (fields (field (name "MPN") "CC0805KRX7R9BB104"))
      (libsource (lib "eagle-import") (part "CERAMIC-100NF-50V-10%-X7R(0805)"))
    )
    (comp (ref "C38")
      (value "100nF")
      (footprint "eagle-import:C0805")
      (fields (field (name "MPN") "CC0805KRX7R9BB104"))
      (libsource (lib "eagle-import") (part "CERAMIC-100NF-50V-10%-X7R(0805)"))
    )
    (comp (ref "C39")
      (value "100nF")
      (footprint "eagle-import:C0805")
      (fields (field (name "MPN") "CC0805KRX7R9BB104"))
      (libsource (lib "eagle-import") (part "CERAMIC-100NF-50V-10%-X7R(0805)"))
    )
    (comp (ref "C40")
      (value "100nF,")
      (footprint "eagle-import:C0805")
      (fields (field (name "MPN") "CC0805KRX7R9BB104"))
      (libsource (lib "eagle-import") (part "CERAMIC-100NF-50V-10%-X7R(0805)"))
    )
    (comp (ref "D37")
      (value "1N4007")
      (footprint "eagle-import:DO-214AC")
      (libsource (lib "eagle-import") (part "DIODE-GEN-PURPOSE-1KV-1A(DO-214AC)"))
    )
    (comp (ref "D38")
      (value "1N4007,")
      (footprint "eagle-import:DO-214AC")
      (fields (field (name "MPN") "1N4007"))
      (libsource (lib "eagle-import") (part "DIODE-GEN-PURPOSE-1KV-1A(DO-214AC)"))
    )
    (comp (ref "D39")
      (value "1N4007,")
      (footprint "eagle-import:DO-214AC")
      (fields (field (name "MPN") "1N4007"))
      (libsource (lib "eagle-import") (part "DIODE-GEN-PURPOSE-1KV-1A(DO-214AC)"))
    )
    (comp (ref "D40")
      (value "1N4007.")
      (footprint "eagle-import:DO-214AC")
      (fields (field (name "MPN") "1N4007"))
      (libsource (lib "eagle-import") (part "DIODE-GEN-PURPOSE-1KV-1A(DO-214AC)"))
    )
    (comp (ref "D41")
      (value "1N5817")
      (footprint "eagle-import:DO-214AC_SLIM")
      (libsource (lib "eagle-import") (part "DIODE-GEN-PURPOSE-1KV-1A(DO-214AC)DO-214AC/1206"))
    )
    (comp (ref "D42")
      (value "1N5817.")
      (footprint "eagle-import:DO-214AC_SLIM")
      (libsource (lib "eagle-import") (part "DIODE-GEN-PURPOSE-1KV-1A(DO-214AC)DO-214AC/1206"))
    )
    (comp (ref "D43")
      (value "1N5817.")
      (footprint "eagle-import:DO-214AC_SLIM")
      (libsource (lib "eagle-import") (part "DIODE-GEN-PURPOSE-1KV-1A(DO-214AC)DO-214AC/1206"))
    )
    (comp (ref "D44")
      (value "1N5817")
      (footprint "eagle-import:DO-214AC_SLIM")
      (libsource (lib "eagle-import") (part "DIODE-GEN-PURPOSE-1KV-1A(DO-214AC)DO-214AC/1206"))
    )
    (comp (ref "D45")
      (value "1N4007.")
      (footprint "eagle-import:DO-214AC")
      (fields (field (name "MPN") "1N4007"))
      (libsource (lib "eagle-import") (part "DIODE-GEN-PURPOSE-1KV-1A(DO-214AC)"))
    )
    (comp (ref "D46")
      (value "1N4007")
      (footprint "eagle-import:DO-214AC")
      (libsource (lib "eagle-import") (part "DIODE-GEN-PURPOSE-1KV-1A(DO-214AC)"))
    )
    (comp (ref "D47")
      (value "SM6T")
      (footprint "eagle-import:DO214AA")
      (libsource (lib "eagle-import") (part "SM6T"))
    )
    (comp (ref "D48")
      (value "SM6TDO214AA_BI")
      (footprint "eagle-import:DO214AA_BI")
      (libsource (lib "eagle-import") (part "SM6TDO214AA_BI"))
    )
    (comp (ref "FID13")
      (value "FIDUCIAL")
      (footprint "eagle-import:FIDUCIAL_1MM")
      (libsource (lib "eagle-import") (part "FIDUCIAL"))
    )
    (comp (ref "FID14")
      (value "FIDUCIAL")
      (footprint "eagle-import:FIDUCIAL_1MM")
      (libsource (lib "eagle-import") (part "FIDUCIAL"))
    )
    (comp (ref "FID15")
      (value "FIDUCIAL")
      (footprint "eagle-import:FIDUCIAL_1MM")
      (libsource (lib "eagle-import") (part "FIDUCIAL"))
    )
    (comp (ref "FID16")
      (value "FIDUCIAL")
      (footprint "eagle-import:FIDUCIAL_1MM")
      (libsource (lib "eagle-import") (part "FIDUCIAL"))
    )
    (comp (ref "IC34")
      (value "4028")
      (footprint "eagle-import:SO16")
      (libsource (lib "eagle-import") (part "4028D"))
    )
    (comp (ref "IC35")
      (value "6V pos")
      (footprint "eagle-import:78LXX")
      (libsource (lib "eagle-import") (part "v-reg_78LXX"))
    )
    (comp (ref "IC36")
      (value "317TO202H_NOHOLE")
      (footprint "eagle-import:TO220H_NOHOLE")
      (libsource (lib "eagle-import") (part "317TO202H_NOHOLE"))
    )
    (comp (ref "IC37")
      (value "ULN2004")
      (footprint "eagle-import:SO16")
      (libsource (lib "eagle-import") (part "ULN2004AD"))
    )
    (comp (ref "IC38")
      (value "LM339")
      (footprint "eagle-import:SO14")
      (libsource (lib "eagle-import") (part "LM339D"))
    )
    (comp (ref "IC39")
      (value "78L06")
      (footprint "eagle-import:SOT89_ROUND")
      (libsource (lib "eagle-import") (part "78LXXSOT89_ROUND"))
    )
    (comp (ref "IC40")
      (value "555")
      (footprint "eagle-import:SO08")
      (libsource (lib "eagle-import") (part "555DNE"))
    )
    (comp (ref "IC41")
      (value "4538")
      (footprint "eagle-import:SO16")
      (libsource (lib "eagle-import") (part "4538D"))
    )
    (comp (ref "IC42")
      (value "78L10")
      (footprint "eagle-import:SOT89_ROUND")
      (libsource (lib "eagle-import") (part "78LXXSOT89_ROUND"))
    )
    (comp (ref "IC43")
      (value "LM2904")
      (footprint "eagle-import:SO08")
      (libsource (lib "eagle-import") (part "LM358D"))
    )
    (comp (ref "JP16")
      (value "JP2EJP2_SMALLPADS")
      (footprint "eagle-import:JP2_SMALLPADS")
      (libsource (lib "eagle-import") (part "JP2EJP2_SMALLPADS"))
    )
    (comp (ref "JP17")
      (value "JP2E_ORIG")
      (footprint "eagle-import:JP2_ORIG_SMALLPADS")
      (libsource (lib "eagle-import") (part "JP2E_ORIG"))
    )
    (comp (ref "JP18")
      (value "JP2EJP2_SMALLPADS")
      (footprint "eagle-import:JP2_SMALLPADS")
      (libsource (lib "eagle-import") (part "JP2EJP2_SMALLPADS"))
    )
    (comp (ref "JP19")
      (value "JP2EJP2_SMALLPADS")
      (footprint "eagle-import:JP2_SMALLPADS")
      (libsource (lib "eagle-import") (part "JP2EJP2_SMALLPADS"))
    )
    (comp (ref "JP20")
      (value "JP2EJP2_SMALLPADS")
      (footprint "eagle-import:JP2_SMALLPADS")
      (libsource (lib "eagle-import") (part "JP2EJP2_SMALLPADS"))
    )
    (comp (ref "LED19")
      (value "LEDLD260")
      (footprint "eagle-import:LD260")
      (libsource (lib "eagle-import") (part "LEDLD260"))
    )
    (comp (ref "LED20")
      (value "LEDLD260")
      (footprint "eagle-import:LD260")
      (libsource (lib "eagle-import") (part "LEDLD260"))
    )
    (comp (ref "LED21")
      (value "LEDLD260")
      (footprint "eagle-import:LD260")
      (libsource (lib "eagle-import") (part "LEDLD260"))
    )
    (comp (ref "LED22")
      (value "LEDLD260")
      (footprint "eagle-import:LD260")
      (libsource (lib "eagle-import") (part "LEDLD260"))
    )
    (comp (ref "LED23")
      (value "LEDLD260")
      (footprint "eagle-import:LD260")
      (libsource (lib "eagle-import") (part "LEDLD260"))
    )
    (comp (ref "LED24")
      (value "LEDLD260")
      (footprint "eagle-import:LD260")
      (libsource (lib "eagle-import") (part "LEDLD260"))
    )
    (comp (ref "Q22")
      (value "BA")
      (footprint "eagle-import:SOT89")
      (libsource (lib "eagle-import") (part "PNP-TRANSISTOR_SOT89"))
    )
    (comp (ref "Q23")
      (value "BA.")
      (footprint "eagle-import:SOT89")
      (libsource (lib "eagle-import") (part "PNP-TRANSISTOR_SOT89"))
    )
    (comp (ref "Q24")
      (value "BA.")
      (footprint "eagle-import:SOT89")
      (libsource (lib "eagle-import") (part "PNP-TRANSISTOR_SOT89"))
    )
    (comp (ref "Q25")
      (value "BA")
      (footprint "eagle-import:SOT89")
      (libsource (lib "eagle-import") (part "PNP-TRANSISTOR_SOT89"))
    )
    (comp (ref "Q26")
      (value "MY")
      (footprint "eagle-import:SOT89")
      (libsource (lib "eagle-import") (part "NPN-TRANSISTOR_SOT89"))
    )
    (comp (ref "Q27")
      (value "J1")
      (footprint "eagle-import:SOT-23")
      (fields (field (name "MPN") "BSS138W-7-F"))
      (libsource (lib "eagle-import") (part "SMD-MOSFET-N-CH-50V-200MA-BSS138W-7-F(SOT-23)"))
    )
    (comp (ref "Q28")
      (value "J1")
      (footprint "eagle-import:SOT-23")
      (fields (field (name "MPN") "BSS138W-7-F"))
      (libsource (lib "eagle-import") (part "SMD-MOSFET-N-CH-50V-200MA-BSS138W-7-F(SOT-23)"))
    )
    (comp (ref "R139")
      (value "47")
      (footprint "eagle-import:V235_17_1MM")
      (libsource (lib "eagle-import") (part "R-EU_V235/17_1MM"))
    )
    (comp (ref "R140")
      (value "13")
      (footprint "eagle-import:R1206")
      (fields (field (name "MPN") "RC1206JR-0713RL"))
      (libsource (lib "eagle-import") (part "SMD-RES-13R-5%-1/4W(1206)"))
    )
    (comp (ref "R141")
      (value "47")
      (footprint "eagle-import:V235_17_1MM")
      (libsource (lib "eagle-import") (part "R-EU_V235/17_1MM"))
    )
    (comp (ref "R142")
      (value "104")
      (footprint "eagle-import:R0805")
      (fields (field (name "MPN") "RC0805FR-0710KL"))
      (libsource (lib "eagle-import") (part "SMD-RES-10K-1%-1/8W(0805)"))
    )
    (comp (ref "R143")
      (value "104")
      (footprint "eagle-import:R0805")
      (fields (field (name "MPN") "RC0805FR-0710KL"))
      (libsource (lib "eagle-import") (part "SMD-RES-10K-1%-1/8W(0805)"))
    )
    (comp (ref "R144")
      (value "104")
      (footprint "eagle-import:R0805")
      (fields (field (name "MPN") "RC0805FR-0710KL"))
      (libsource (lib "eagle-import") (part "SMD-RES-10K-1%-1/8W(0805)"))
    )
    (comp (ref "R145")
      (value "4701")
      (footprint "eagle-import:R0805")
      (fields (field (name "MPN") "RC0805JR-074K7L"))
      (libsource (lib "eagle-import") (part "SMD-RES-4.7K-5%-1/8W(0805)"))
    )
    (comp (ref "R146")
      (value "1002")
      (footprint "eagle-import:R0805")
      (fields (field (name "MPN") "RC0805FR-0710KL"))
      (libsource (lib "eagle-import") (part "SMD-RES-10K-1%-1/8W(0805)"))
    )
    (comp (ref "R147")
      (value "1002")
      (footprint "eagle-import:R0805")
      (fields (field (name "MPN") "RC0805FR-0710KL"))
      (libsource (lib "eagle-import") (part "SMD-RES-10K-1%-1/8W(0805)"))
    )
    (comp (ref "R148")
      (value "1502")
      (footprint "eagle-import:R0805")
      (fields (field (name "MPN") "RC0805FR-0710KL"))
      (libsource (lib "eagle-import") (part "SMD-RES-10K-1%-1/8W(0805)"))
    )
    (comp (ref "R149")
      (value "104")
      (footprint "eagle-import:R0805")
      (fields (field (name "MPN") "RC0805FR-0710KL"))
      (libsource (lib "eagle-import") (part "SMD-RES-10K-1%-1/8W(0805)"))
    )
    (comp (ref "R150")
      (value "104")
      (footprint "eagle-import:R0805")
      (fields (field (name "MPN") "RC0805FR-0710KL"))
      (libsource (lib "eagle-import") (part "SMD-RES-10K-1%-1/8W(0805)"))
    )
    (comp (ref "R151")
      (value "1502")
      (footprint "eagle-import:R0805")
      (fields (field (name "MPN") "RC0805FR-0710KL"))
      (libsource (lib "eagle-import") (part "SMD-RES-10K-1%-1/8W(0805)"))
    )
    (comp (ref "R152")
      (value "1002")
      (footprint "eagle-import:R0805")
      (fields (field (name "MPN") "RC0805FR-0710KL"))
      (libsource (lib "eagle-import") (part "SMD-RES-10K-1%-1/8W(0805)"))
    )
    (comp (ref "R153")
      (value "2201")
      (footprint "eagle-import:R0805")
      (fields (field (name "MPN") "RC0805JR-072K2L"))
      (libsource (lib "eagle-import") (part "SMD-RES-2.2K-5%-1/8W(0805)"))
    )
    (comp (ref "R154")
      (value "1002")
      (footprint "eagle-import:R0805")
      (fields (field (name "MPN") "RC0805FR-0710KL"))
      (libsource (lib "eagle-import") (part "SMD-RES-10K-1%-1/8W(0805)"))
    )
    (comp (ref "R155")
      (value "4701")
      (footprint "eagle-import:R0805")
      (fields (field (name "MPN") "RC0805JR-074K7L"))
      (libsource (lib "eagle-import") (part "SMD-RES-4.7K-5%-1/8W(0805)"))
    )
    (comp (ref "R156")
      (value "2702")
      (footprint "eagle-import:R0805")
      (fields (field (name "MPN") "RC0805JR-074K7L"))
      (libsource (lib "eagle-import") (part "SMD-RES-4.7K-5%-1/8W(0805)"))
    )
    (comp (ref "R157")
      (value "102")
      (footprint "eagle-import:R0805")
      (fields (field (name "MPN") "RC0805JR-071KL"))
      (libsource (lib "eagle-import") (part "SMD-RES-1K-5%-1/8W(0805)"))
    )
    (comp (ref "R158")
      (value "R_user")
      (footprint "eagle-import:R0805")
      (libsource (lib "eagle-import") (part "R-EU_R0805"))
    )
    (comp (ref "R159")
      (value "100")
      (footprint "eagle-import:R0805")
      (fields (field (name "MPN") "RC0805JR-07220RL"))
      (libsource (lib "eagle-import") (part "SMD-RES-220R-5%-1/8W(0805)"))
    )
    (comp (ref "R160")
      (value "(101)")
      (footprint "eagle-import:R0805")
      (fields (field (name "MPN") "RC0805JR-07100RL"))
      (libsource (lib "eagle-import") (part "SMD-RES-100R-5%-1/8W(0805)"))
    )
    (comp (ref "R161")
      (value "(1000)")
      (footprint "eagle-import:R0805")
      (fields (field (name "MPN") "RC0805JR-07100RL"))
      (libsource (lib "eagle-import") (part "SMD-RES-100R-5%-1/8W(0805)"))
    )
    (comp (ref "R162")
      (value "102")
      (footprint "eagle-import:R0805")
      (fields (field (name "MPN") "RC0805JR-071KL"))
      (libsource (lib "eagle-import") (part "SMD-RES-1K-5%-1/8W(0805)"))
    )
    (comp (ref "R163")
      (value "13")
      (footprint "eagle-import:R1206")
      (fields (field (name "MPN") "RC1206JR-0713RL"))
      (libsource (lib "eagle-import") (part "SMD-RES-13R-5%-1/4W(1206)"))
    )
    (comp (ref "R164")
      (value "13")
      (footprint "eagle-import:R1206")
      (fields (field (name "MPN") "RC1206JR-0713RL"))
      (libsource (lib "eagle-import") (part "SMD-RES-13R-5%-1/4W(1206)"))
    )
    (comp (ref "R165")
      (value "2702")
      (footprint "eagle-import:R0805")
      (fields (field (name "MPN") "RC0805JR-074K7L"))
      (libsource (lib "eagle-import") (part "SMD-RES-4.7K-5%-1/8W(0805)"))
    )
    (comp (ref "R166")
      (value "4701")
      (footprint "eagle-import:R0805")
      (fields (field (name "MPN") "RC0805JR-074K7L"))
      (libsource (lib "eagle-import") (part "SMD-RES-4.7K-5%-1/8W(0805)"))
    )
    (comp (ref "R167")
      (value "100")
      (footprint "eagle-import:R0805")
      (fields (field (name "MPN") "RC0805JR-072K2L"))
      (libsource (lib "eagle-import") (part "SMD-RES-2.2K-5%-1/8W(0805)"))
    )
    (comp (ref "R168")
      (value "(101)")
      (footprint "eagle-import:R0805")
      (fields (field (name "MPN") "RC0805JR-072K2L"))
      (libsource (lib "eagle-import") (part "SMD-RES-2.2K-5%-1/8W(0805)"))
    )
    (comp (ref "R169")
      (value "104")
      (footprint "eagle-import:R0805")
      (fields (field (name "MPN") "RC0805FR-0710KL"))
      (libsource (lib "eagle-import") (part "SMD-RES-10K-1%-1/8W(0805)"))
    )
    (comp (ref "R170")
      (value "104")
      (footprint "eagle-import:R0805")
      (fields (field (name "MPN") "RC0805FR-0710KL"))
      (libsource (lib "eagle-import") (part "SMD-RES-10K-1%-1/8W(0805)"))
    )
    (comp (ref "R171")
      (value "(1002)")
      (footprint "eagle-import:R0805")
      (fields (field (name "MPN") "RC0805FR-0710KL"))
      (libsource (lib "eagle-import") (part "SMD-RES-10K-1%-1/8W(0805)"))
    )
    (comp (ref "R172")
      (value "2702")
      (footprint "eagle-import:R0805")
      (fields (field (name "MPN") "RC0805FR-0710KL"))
      (libsource (lib "eagle-import") (part "SMD-RES-10K-1%-1/8W(0805)"))
    )
    (comp (ref "R173")
      (value "47")
      (footprint "eagle-import:V235_17_1MM")
      (libsource (lib "eagle-import") (part "R-EU_V235/17_1MM"))
    )
    (comp (ref "R174")
      (value "47")
      (footprint "eagle-import:V235_17_1MM")
      (libsource (lib "eagle-import") (part "R-EU_V235/17_1MM"))
    )
    (comp (ref "R175")
      (value "2702")
      (footprint "eagle-import:R0805")
      (fields (field (name "MPN") "RC0805JR-074K7L"))
      (libsource (lib "eagle-import") (part "SMD-RES-4.7K-5%-1/8W(0805)"))
    )
    (comp (ref "R176")
      (value "2201")
      (footprint "eagle-import:R0805")
      (fields (field (name "MPN") "RC0805JR-072K2L"))
      (libsource (lib "eagle-import") (part "SMD-RES-2.2K-5%-1/8W(0805)"))
    )
    (comp (ref "R177")
      (value "(1002)")
      (footprint "eagle-import:R0805")
      (fields (field (name "MPN") "RC0805JR-074K7L"))
      (libsource (lib "eagle-import") (part "SMD-RES-4.7K-5%-1/8W(0805)"))
    )
    (comp (ref "R178")
      (value "1002")
      (footprint "eagle-import:R0805")
      (fields (field (name "MPN") "RC0805FR-0710KL"))
      (libsource (lib "eagle-import") (part "SMD-RES-10K-1%-1/8W(0805)"))
    )
    (comp (ref "R179")
      (value "102")
      (footprint "eagle-import:R0805")
      (fields (field (name "MPN") "RC0805JR-071KL"))
      (libsource (lib "eagle-import") (part "SMD-RES-1K-5%-1/8W(0805)"))
    )
    (comp (ref "R180")
      (value "2702")
      (footprint "eagle-import:R0805")
      (fields (field (name "MPN") "RC0805JR-074K7L"))
      (libsource (lib "eagle-import") (part "SMD-RES-4.7K-5%-1/8W(0805)"))
    )
    (comp (ref "R181")
      (value "102")
      (footprint "eagle-import:R0805")
      (fields (field (name "MPN") "RC0805JR-071KL"))
      (libsource (lib "eagle-import") (part "SMD-RES-1K-5%-1/8W(0805)"))
    )
    (comp (ref "R182")
      (value "102")
      (footprint "eagle-import:R0805")
      (fields (field (name "MPN") "RC0805JR-071KL"))
      (libsource (lib "eagle-import") (part "SMD-RES-1K-5%-1/8W(0805)"))
    )
    (comp (ref "R183")
      (value "13")
      (footprint "eagle-import:R1206")
      (fields (field (name "MPN") "RC1206JR-0713RL"))
      (libsource (lib "eagle-import") (part "SMD-RES-13R-5%-1/4W(1206)"))
    )
    (comp (ref "R184")
      (value "R_user")
      (footprint "eagle-import:R0805")
      (libsource (lib "eagle-import") (part "R-EU_R0805"))
    )
    (comp (ref "SJ4") (value "SJ") (footprint "eagle-import:SJ") (libsource (lib "eagle-import") (part "SJ")))
    (comp (ref "START3")
      (value "TPSB2.0")
      (footprint "eagle-import:B2.0")
      (libsource (lib "eagle-import") (part "TPSB2.0"))
    )
    (comp (ref "TP70")
      (value "TPSB2.0")
      (footprint "eagle-import:B2.0")
      (libsource (lib "eagle-import") (part "TPSB2.0"))
    )
    (comp (ref "TP71")
      (value "TPSB2.0")
      (footprint "eagle-import:B2.0")
      (libsource (lib "eagle-import") (part "TPSB2.0"))
    )
    (comp (ref "TP72")
      (value "TPSB2.0")
      (footprint "eagle-import:B2.0")
      (libsource (lib "eagle-import") (part "TPSB2.0"))
    )
    (comp (ref "TP73")
      (value "TPSB2.0")
      (footprint "eagle-import:B2.0")
      (libsource (lib "eagle-import") (part "TPSB2.0"))
    )
    (comp (ref "TP74")
      (value "TPSB2.0")
      (footprint "eagle-import:B2.0")
      (libsource (lib "eagle-import") (part "TPSB2.0"))
    )
    (comp (ref "TP75")
      (value "TPSB2.0")
      (footprint "eagle-import:B2.0")
      (libsource (lib "eagle-import") (part "TPSB2.0"))
    )
    (comp (ref "TP76")
      (value "TPSB2.0")
      (footprint "eagle-import:B2.0")
      (libsource (lib "eagle-import") (part "TPSB2.0"))
    )
    (comp (ref "TP77")
      (value "TPSB2.0")
      (footprint "eagle-import:B2.0")
      (libsource (lib "eagle-import") (part "TPSB2.0"))
    )
    (comp (ref "TP78")
      (value "TPSB2.0")
      (footprint "eagle-import:B2.0")
      (libsource (lib "eagle-import") (part "TPSB2.0"))
    )
    (comp (ref "TP79")
      (value "TPSB2.0")
      (footprint "eagle-import:B2.0")
      (libsource (lib "eagle-import") (part "TPSB2.0"))
    )
    (comp (ref "TP80")
      (value "TPSB2.0")
      (footprint "eagle-import:B2.0")
      (libsource (lib "eagle-import") (part "TPSB2.0"))
    )
    (comp (ref "TP81")
      (value "TPSB2.0")
      (footprint "eagle-import:B2.0")
      (libsource (lib "eagle-import") (part "TPSB2.0"))
    )
    (comp (ref "TP82")
      (value "TPSB2.0")
      (footprint "eagle-import:B2.0")
      (libsource (lib "eagle-import") (part "TPSB2.0"))
    )
    (comp (ref "TP83")
      (value "TPSB2.0")
      (footprint "eagle-import:B2.0")
      (libsource (lib "eagle-import") (part "TPSB2.0"))
    )
    (comp (ref "TP84")
      (value "TPSB2.0")
      (footprint "eagle-import:B2.0")
      (libsource (lib "eagle-import") (part "TPSB2.0"))
    )
    (comp (ref "TP85")
      (value "TPSB2.0")
      (footprint "eagle-import:B2.0")
      (libsource (lib "eagle-import") (part "TPSB2.0"))
    )
    (comp (ref "TP86")
      (value "TPSB2.0")
      (footprint "eagle-import:B2.0")
      (libsource (lib "eagle-import") (part "TPSB2.0"))
    )
    (comp (ref "TP87")
      (value "TPSB2.0")
      (footprint "eagle-import:B2.0")
      (libsource (lib "eagle-import") (part "TPSB2.0"))
    )
    (comp (ref "TP88")
      (value "TPSB1,27")
      (footprint "eagle-import:B1,27")
      (libsource (lib "eagle-import") (part "TPSB1,27"))
    )
    (comp (ref "TP89")
      (value "TPSB2.0")
      (footprint "eagle-import:B2.0")
      (libsource (lib "eagle-import") (part "TPSB2.0"))
    )
    (comp (ref "TP90")
      (value "TPSB2.0")
      (footprint "eagle-import:B2.0")
      (libsource (lib "eagle-import") (part "TPSB2.0"))
    )
    (comp (ref "TP91")
      (value "TPSB2.0")
      (footprint "eagle-import:B2.0")
      (libsource (lib "eagle-import") (part "TPSB2.0"))
    )
    (comp (ref "TP92")
      (value "TPSB2.0")
      (footprint "eagle-import:B2.0")
      (libsource (lib "eagle-import") (part "TPSB2.0"))
    )
    (comp (ref "X10")
      (value "CON_BMWV2")
      (footprint "eagle-import:24-PIN_V2")
      (libsource (lib "eagle-import") (part "CON_BMWV2"))
    )
    (comp (ref "X11")
      (value "22-23-2051")
      (footprint "eagle-import:22-23-2051")
      (fields (field (name "MF") "MOLEX"))
      (libsource (lib "eagle-import") (part "22-23-2051"))
    )
    (comp (ref "X12")
      (value "22-23-2021")
      (footprint "eagle-import:22-23-2021")
      (fields (field (name "MF") "MOLEX"))
      (libsource (lib "eagle-import") (part "22-23-2021"))
    )
    (comp (ref "6V4")
      (value "TPSB2.0")
      (footprint "eagle-import:B2.0")
      (libsource (lib "eagle-import") (part "TPSB2.0"))
    )
    (comp (ref "9")
      (value "2081-1132")
      (footprint "eagle-import:12-PIN")
      (libsource (lib "eagle-import") (part "2081-1132"))
    )
    (comp (ref "10")
      (value "2081-1132")
      (footprint "eagle-import:12-PIN")
      (libsource (lib "eagle-import") (part "2081-1132"))
    )
    (comp (ref "10V4")
      (value "TPSB2.0")
      (footprint "eagle-import:B2.0")
      (libsource (lib "eagle-import") (part "TPSB2.0"))
    )
    (comp (ref "C41")
      (value "100u")
      (footprint "eagle-import:C1206")
      (fields (field (name "MPN") "GRM31CR60J107ME39L"))
      (libsource (lib "eagle-import") (part "CERAMIC-100UF-6.3V-20%-X5R(1206)"))
    )
    (comp (ref "C42")
      (value "100u")
      (footprint "eagle-import:C1206")
      (fields (field (name "MPN") "GRM31CR60J107ME39L"))
      (libsource (lib "eagle-import") (part "CERAMIC-100UF-6.3V-20%-X5R(1206)"))
    )
    (comp (ref "C43")
      (value "100nF,")
      (footprint "eagle-import:C0805")
      (fields (field (name "MPN") "CC0805KRX7R9BB104"))
      (libsource (lib "eagle-import") (part "CERAMIC-100NF-50V-10%-X7R(0805)"))
    )
    (comp (ref "C44")
      (value "4.7u")
      (footprint "eagle-import:C0805")
      (fields (field (name "MPN") "CC0805KKX5R8BB475"))
      (libsource (lib "eagle-import") (part "CERAMIC-4.7UF-25V-10%-X5R(0805)"))
    )
    (comp (ref "C45")
      (value "100nF.")
      (footprint "eagle-import:C0805")
      (fields (field (name "MPN") "CC0805KRX7R9BB104"))
      (libsource (lib "eagle-import") (part "CERAMIC-100NF-50V-10%-X7R(0805)"))
    )
    (comp (ref "C46")
      (value "100nF.")
      (footprint "eagle-import:C0805")
      (fields (field (name "MPN") "CC0805KRX7R9BB104"))
      (libsource (lib "eagle-import") (part "CERAMIC-100NF-50V-10%-X7R(0805)"))
    )
    (comp (ref "C47")
      (value "2.2nF")
      (footprint "eagle-import:C0805")
      (fields (field (name "MPN") "CC0805KRX7R9BB104"))
      (libsource (lib "eagle-import") (part "CERAMIC-100NF-50V-10%-X7R(0805)"))
    )
    (comp (ref "C48")
      (value "100nF")
      (footprint "eagle-import:C0805")
      (fields (field (name "MPN") "CC0805KRX7R9BB104"))
      (libsource (lib "eagle-import") (part "CERAMIC-100NF-50V-10%-X7R(0805)"))
    )
    (comp (ref "C49")
      (value "100nF")
      (footprint "eagle-import:C0805")
      (fields (field (name "MPN") "CC0805KRX7R9BB104"))
      (libsource (lib "eagle-import") (part "CERAMIC-100NF-50V-10%-X7R(0805)"))
    )
    (comp (ref "C50")
      (value "100nF,")
      (footprint "eagle-import:C0805")
      (fields (field (name "MPN") "CC0805KRX7R9BB104"))
      (libsource (lib "eagle-import") (part "CERAMIC-100NF-50V-10%-X7R(0805)"))
    )
    (comp (ref "D49")
      (value "1N4007")
      (footprint "eagle-import:DO-214AC")
      (libsource (lib "eagle-import") (part "DIODE-GEN-PURPOSE-1KV-1A(DO-214AC)"))
    )
    (comp (ref "D50")
      (value "1N4007,")
      (footprint "eagle-import:DO-214AC")
      (fields (field (name "MPN") "1N4007"))
      (libsource (lib "eagle-import") (part "DIODE-GEN-PURPOSE-1KV-1A(DO-214AC)"))
    )
    (comp (ref "D51")
      (value "1N4007,")
      (footprint "eagle-import:DO-214AC")
      (fields (field (name "MPN") "1N4007"))
      (libsource (lib "eagle-import") (part "DIODE-GEN-PURPOSE-1KV-1A(DO-214AC)"))
    )
    (comp (ref "D52")
      (value "1N4007.")
      (footprint "eagle-import:DO-214AC")
      (fields (field (name "MPN") "1N4007"))
      (libsource (lib "eagle-import") (part "DIODE-GEN-PURPOSE-1KV-1A(DO-214AC)"))
    )
    (comp (ref "D53")
      (value "1N5817")
      (footprint "eagle-import:DO-214AC_SLIM")
      (libsource (lib "eagle-import") (part "DIODE-GEN-PURPOSE-1KV-1A(DO-214AC)DO-214AC/1206"))
    )
    (comp (ref "D54")
      (value "1N5817.")
      (footprint "eagle-import:DO-214AC_SLIM")
      (libsource (lib "eagle-import") (part "DIODE-GEN-PURPOSE-1KV-1A(DO-214AC)DO-214AC/1206"))
    )
    (comp (ref "D55")
      (value "1N5817.")
      (footprint "eagle-import:DO-214AC_SLIM")
      (libsource (lib "eagle-import") (part "DIODE-GEN-PURPOSE-1KV-1A(DO-214AC)DO-214AC/1206"))
    )
    (comp (ref "D56")
      (value "1N5817")
      (footprint "eagle-import:DO-214AC_SLIM")
      (libsource (lib "eagle-import") (part "DIODE-GEN-PURPOSE-1KV-1A(DO-214AC)DO-214AC/1206"))
    )
    (comp (ref "D57")
      (value "1N4007.")
      (footprint "eagle-import:DO-214AC")
      (fields (field (name "MPN") "1N4007"))
      (libsource (lib "eagle-import") (part "DIODE-GEN-PURPOSE-1KV-1A(DO-214AC)"))
    )
    (comp (ref "D58")
      (value "1N4007")
      (footprint "eagle-import:DO-214AC")
      (libsource (lib "eagle-import") (part "DIODE-GEN-PURPOSE-1KV-1A(DO-214AC)"))
    )
    (comp (ref "D59")
      (value "SM6T")
      (footprint "eagle-import:DO214AA")
      (libsource (lib "eagle-import") (part "SM6T"))
    )
    (comp (ref "D60")
      (value "SM6TDO214AA_BI")
      (footprint "eagle-import:DO214AA_BI")
      (libsource (lib "eagle-import") (part "SM6TDO214AA_BI"))
    )
    (comp (ref "FID17")
      (value "FIDUCIAL")
      (footprint "eagle-import:FIDUCIAL_1MM")
      (libsource (lib "eagle-import") (part "FIDUCIAL"))
    )
    (comp (ref "FID18")
      (value "FIDUCIAL")
      (footprint "eagle-import:FIDUCIAL_1MM")
      (libsource (lib "eagle-import") (part "FIDUCIAL"))
    )
    (comp (ref "FID19")
      (value "FIDUCIAL")
      (footprint "eagle-import:FIDUCIAL_1MM")
      (libsource (lib "eagle-import") (part "FIDUCIAL"))
    )
    (comp (ref "FID20")
      (value "FIDUCIAL")
      (footprint "eagle-import:FIDUCIAL_1MM")
      (libsource (lib "eagle-import") (part "FIDUCIAL"))
    )
    (comp (ref "IC45")
      (value "4028")
      (footprint "eagle-import:SO16")
      (libsource (lib "eagle-import") (part "4028D"))
    )
    (comp (ref "IC46")
      (value "6V pos")
      (footprint "eagle-import:78LXX")
      (libsource (lib "eagle-import") (part "v-reg_78LXX"))
    )
    (comp (ref "IC47")
      (value "317TO202H_NOHOLE")
      (footprint "eagle-import:TO220H_NOHOLE")
      (libsource (lib "eagle-import") (part "317TO202H_NOHOLE"))
    )
    (comp (ref "IC48")
      (value "ULN2004")
      (footprint "eagle-import:SO16")
      (libsource (lib "eagle-import") (part "ULN2004AD"))
    )
    (comp (ref "IC49")
      (value "LM339")
      (footprint "eagle-import:SO14")
      (libsource (lib "eagle-import") (part "LM339D"))
    )
    (comp (ref "IC50")
      (value "78L06")
      (footprint "eagle-import:SOT89_ROUND")
      (libsource (lib "eagle-import") (part "78LXXSOT89_ROUND"))
    )
    (comp (ref "IC51")
      (value "555")
      (footprint "eagle-import:SO08")
      (libsource (lib "eagle-import") (part "555DNE"))
    )
    (comp (ref "IC52")
      (value "4538")
      (footprint "eagle-import:SO16")
      (libsource (lib "eagle-import") (part "4538D"))
    )
    (comp (ref "IC53")
      (value "78L10")
      (footprint "eagle-import:SOT89_ROUND")
      (libsource (lib "eagle-import") (part "78LXXSOT89_ROUND"))
    )
    (comp (ref "IC54")
      (value "LM2904")
      (footprint "eagle-import:SO08")
      (libsource (lib "eagle-import") (part "LM358D"))
    )
    (comp (ref "JP21")
      (value "JP2EJP2_SMALLPADS")
      (footprint "eagle-import:JP2_SMALLPADS")
      (libsource (lib "eagle-import") (part "JP2EJP2_SMALLPADS"))
    )
    (comp (ref "JP22")
      (value "JP2E_ORIG")
      (footprint "eagle-import:JP2_ORIG_SMALLPADS")
      (libsource (lib "eagle-import") (part "JP2E_ORIG"))
    )
    (comp (ref "JP23")
      (value "JP2EJP2_SMALLPADS")
      (footprint "eagle-import:JP2_SMALLPADS")
      (libsource (lib "eagle-import") (part "JP2EJP2_SMALLPADS"))
    )
    (comp (ref "JP24")
      (value "JP2EJP2_SMALLPADS")
      (footprint "eagle-import:JP2_SMALLPADS")
      (libsource (lib "eagle-import") (part "JP2EJP2_SMALLPADS"))
    )
    (comp (ref "JP25")
      (value "JP2EJP2_SMALLPADS")
      (footprint "eagle-import:JP2_SMALLPADS")
      (libsource (lib "eagle-import") (part "JP2EJP2_SMALLPADS"))
    )
    (comp (ref "LED25")
      (value "LEDLD260")
      (footprint "eagle-import:LD260")
      (libsource (lib "eagle-import") (part "LEDLD260"))
    )
    (comp (ref "LED26")
      (value "LEDLD260")
      (footprint "eagle-import:LD260")
      (libsource (lib "eagle-import") (part "LEDLD260"))
    )
    (comp (ref "LED27")
      (value "LEDLD260")
      (footprint "eagle-import:LD260")
      (libsource (lib "eagle-import") (part "LEDLD260"))
    )
    (comp (ref "LED28")
      (value "LEDLD260")
      (footprint "eagle-import:LD260")
      (libsource (lib "eagle-import") (part "LEDLD260"))
    )
    (comp (ref "LED29")
      (value "LEDLD260")
      (footprint "eagle-import:LD260")
      (libsource (lib "eagle-import") (part "LEDLD260"))
    )
    (comp (ref "LED30")
      (value "LEDLD260")
      (footprint "eagle-import:LD260")
      (libsource (lib "eagle-import") (part "LEDLD260"))
    )
    (comp (ref "Q29")
      (value "BA")
      (footprint "eagle-import:SOT89")
      (libsource (lib "eagle-import") (part "PNP-TRANSISTOR_SOT89"))
    )
    (comp (ref "Q30")
      (value "BA.")
      (footprint "eagle-import:SOT89")
      (libsource (lib "eagle-import") (part "PNP-TRANSISTOR_SOT89"))
    )
    (comp (ref "Q31")
      (value "BA.")
      (footprint "eagle-import:SOT89")
      (libsource (lib "eagle-import") (part "PNP-TRANSISTOR_SOT89"))
    )
    (comp (ref "Q32")
      (value "BA")
      (footprint "eagle-import:SOT89")
      (libsource (lib "eagle-import") (part "PNP-TRANSISTOR_SOT89"))
    )
    (comp (ref "Q33")
      (value "MY")
      (footprint "eagle-import:SOT89")
      (libsource (lib "eagle-import") (part "NPN-TRANSISTOR_SOT89"))
    )
    (comp (ref "Q34")
      (value "J1")
      (footprint "eagle-import:SOT-23")
      (fields (field (name "MPN") "BSS138W-7-F"))
      (libsource (lib "eagle-import") (part "SMD-MOSFET-N-CH-50V-200MA-BSS138W-7-F(SOT-23)"))
    )
    (comp (ref "Q35")
      (value "J1")
      (footprint "eagle-import:SOT-23")
      (fields (field (name "MPN") "BSS138W-7-F"))
      (libsource (lib "eagle-import") (part "SMD-MOSFET-N-CH-50V-200MA-BSS138W-7-F(SOT-23)"))
    )
    (comp (ref "R185")
      (value "47")
      (footprint "eagle-import:V235_17_1MM")
      (libsource (lib "eagle-import") (part "R-EU_V235/17_1MM"))
    )
    (comp (ref "R186")
      (value "13")
      (footprint "eagle-import:R1206")
      (fields (field (name "MPN") "RC1206JR-0713RL"))
      (libsource (lib "eagle-import") (part "SMD-RES-13R-5%-1/4W(1206)"))
    )
    (comp (ref "R187")
      (value "47")
      (footprint "eagle-import:V235_17_1MM")
      (libsource (lib "eagle-import") (part "R-EU_V235/17_1MM"))
    )
    (comp (ref "R188")
      (value "104")
      (footprint "eagle-import:R0805")
      (fields (field (name "MPN") "RC0805FR-0710KL"))
      (libsource (lib "eagle-import") (part "SMD-RES-10K-1%-1/8W(0805)"))
    )
    (comp (ref "R189")
      (value "104")
      (footprint "eagle-import:R0805")
      (fields (field (name "MPN") "RC0805FR-0710KL"))
      (libsource (lib "eagle-import") (part "SMD-RES-10K-1%-1/8W(0805)"))
    )
    (comp (ref "R190")
      (value "104")
      (footprint "eagle-import:R0805")
      (fields (field (name "MPN") "RC0805FR-0710KL"))
      (libsource (lib "eagle-import") (part "SMD-RES-10K-1%-1/8W(0805)"))
    )
    (comp (ref "R191")
      (value "4701")
      (footprint "eagle-import:R0805")
      (fields (field (name "MPN") "RC0805JR-074K7L"))
      (libsource (lib "eagle-import") (part "SMD-RES-4.7K-5%-1/8W(0805)"))
    )
    (comp (ref "R192")
      (value "1002")
      (footprint "eagle-import:R0805")
      (fields (field (name "MPN") "RC0805FR-0710KL"))
      (libsource (lib "eagle-import") (part "SMD-RES-10K-1%-1/8W(0805)"))
    )
    (comp (ref "R193")
      (value "1002")
      (footprint "eagle-import:R0805")
      (fields (field (name "MPN") "RC0805FR-0710KL"))
      (libsource (lib "eagle-import") (part "SMD-RES-10K-1%-1/8W(0805)"))
    )
    (comp (ref "R194")
      (value "1502")
      (footprint "eagle-import:R0805")
      (fields (field (name "MPN") "RC0805FR-0710KL"))
      (libsource (lib "eagle-import") (part "SMD-RES-10K-1%-1/8W(0805)"))
    )
    (comp (ref "R195")
      (value "104")
      (footprint "eagle-import:R0805")
      (fields (field (name "MPN") "RC0805FR-0710KL"))
      (libsource (lib "eagle-import") (part "SMD-RES-10K-1%-1/8W(0805)"))
    )
    (comp (ref "R196")
      (value "104")
      (footprint "eagle-import:R0805")
      (fields (field (name "MPN") "RC0805FR-0710KL"))
      (libsource (lib "eagle-import") (part "SMD-RES-10K-1%-1/8W(0805)"))
    )
    (comp (ref "R197")
      (value "1502")
      (footprint "eagle-import:R0805")
      (fields (field (name "MPN") "RC0805FR-0710KL"))
      (libsource (lib "eagle-import") (part "SMD-RES-10K-1%-1/8W(0805)"))
    )
    (comp (ref "R198")
      (value "1002")
      (footprint "eagle-import:R0805")
      (fields (field (name "MPN") "RC0805FR-0710KL"))
      (libsource (lib "eagle-import") (part "SMD-RES-10K-1%-1/8W(0805)"))
    )
    (comp (ref "R199")
      (value "2201")
      (footprint "eagle-import:R0805")
      (fields (field (name "MPN") "RC0805JR-072K2L"))
      (libsource (lib "eagle-import") (part "SMD-RES-2.2K-5%-1/8W(0805)"))
    )
    (comp (ref "R200")
      (value "1002")
      (footprint "eagle-import:R0805")
      (fields (field (name "MPN") "RC0805FR-0710KL"))
      (libsource (lib "eagle-import") (part "SMD-RES-10K-1%-1/8W(0805)"))
    )
    (comp (ref "R201")
      (value "4701")
      (footprint "eagle-import:R0805")
      (fields (field (name "MPN") "RC0805JR-074K7L"))
      (libsource (lib "eagle-import") (part "SMD-RES-4.7K-5%-1/8W(0805)"))
    )
    (comp (ref "R202")
      (value "2702")
      (footprint "eagle-import:R0805")
      (fields (field (name "MPN") "RC0805JR-074K7L"))
      (libsource (lib "eagle-import") (part "SMD-RES-4.7K-5%-1/8W(0805)"))
    )
    (comp (ref "R203")
      (value "102")
      (footprint "eagle-import:R0805")
      (fields (field (name "MPN") "RC0805JR-071KL"))
      (libsource (lib "eagle-import") (part "SMD-RES-1K-5%-1/8W(0805)"))
    )
    (comp (ref "R204")
      (value "R_user")
      (footprint "eagle-import:R0805")
      (libsource (lib "eagle-import") (part "R-EU_R0805"))
    )
    (comp (ref "R205")
      (value "100")
      (footprint "eagle-import:R0805")
      (fields (field (name "MPN") "RC0805JR-07220RL"))
      (libsource (lib "eagle-import") (part "SMD-RES-220R-5%-1/8W(0805)"))
    )
    (comp (ref "R206")
      (value "(101)")
      (footprint "eagle-import:R0805")
      (fields (field (name "MPN") "RC0805JR-07100RL"))
      (libsource (lib "eagle-import") (part "SMD-RES-100R-5%-1/8W(0805)"))
    )
    (comp (ref "R207")
      (value "(1000)")
      (footprint "eagle-import:R0805")
      (fields (field (name "MPN") "RC0805JR-07100RL"))
      (libsource (lib "eagle-import") (part "SMD-RES-100R-5%-1/8W(0805)"))
    )
    (comp (ref "R208")
      (value "102")
      (footprint "eagle-import:R0805")
      (fields (field (name "MPN") "RC0805JR-071KL"))
      (libsource (lib "eagle-import") (part "SMD-RES-1K-5%-1/8W(0805)"))
    )
    (comp (ref "R209")
      (value "13")
      (footprint "eagle-import:R1206")
      (fields (field (name "MPN") "RC1206JR-0713RL"))
      (libsource (lib "eagle-import") (part "SMD-RES-13R-5%-1/4W(1206)"))
    )
    (comp (ref "R210")
      (value "13")
      (footprint "eagle-import:R1206")
      (fields (field (name "MPN") "RC1206JR-0713RL"))
      (libsource (lib "eagle-import") (part "SMD-RES-13R-5%-1/4W(1206)"))
    )
    (comp (ref "R211")
      (value "2702")
      (footprint "eagle-import:R0805")
      (fields (field (name "MPN") "RC0805JR-074K7L"))
      (libsource (lib "eagle-import") (part "SMD-RES-4.7K-5%-1/8W(0805)"))
    )
    (comp (ref "R212")
      (value "4701")
      (footprint "eagle-import:R0805")
      (fields (field (name "MPN") "RC0805JR-074K7L"))
      (libsource (lib "eagle-import") (part "SMD-RES-4.7K-5%-1/8W(0805)"))
    )
    (comp (ref "R213")
      (value "100")
      (footprint "eagle-import:R0805")
      (fields (field (name "MPN") "RC0805JR-072K2L"))
      (libsource (lib "eagle-import") (part "SMD-RES-2.2K-5%-1/8W(0805)"))
    )
    (comp (ref "R214")
      (value "(101)")
      (footprint "eagle-import:R0805")
      (fields (field (name "MPN") "RC0805JR-072K2L"))
      (libsource (lib "eagle-import") (part "SMD-RES-2.2K-5%-1/8W(0805)"))
    )
    (comp (ref "R215")
      (value "104")
      (footprint "eagle-import:R0805")
      (fields (field (name "MPN") "RC0805FR-0710KL"))
      (libsource (lib "eagle-import") (part "SMD-RES-10K-1%-1/8W(0805)"))
    )
    (comp (ref "R216")
      (value "104")
      (footprint "eagle-import:R0805")
      (fields (field (name "MPN") "RC0805FR-0710KL"))
      (libsource (lib "eagle-import") (part "SMD-RES-10K-1%-1/8W(0805)"))
    )
    (comp (ref "R217")
      (value "(1002)")
      (footprint "eagle-import:R0805")
      (fields (field (name "MPN") "RC0805FR-0710KL"))
      (libsource (lib "eagle-import") (part "SMD-RES-10K-1%-1/8W(0805)"))
    )
    (comp (ref "R218")
      (value "2702")
      (footprint "eagle-import:R0805")
      (fields (field (name "MPN") "RC0805FR-0710KL"))
      (libsource (lib "eagle-import") (part "SMD-RES-10K-1%-1/8W(0805)"))
    )
    (comp (ref "R219")
      (value "47")
      (footprint "eagle-import:V235_17_1MM")
      (libsource (lib "eagle-import") (part "R-EU_V235/17_1MM"))
    )
    (comp (ref "R220")
      (value "47")
      (footprint "eagle-import:V235_17_1MM")
      (libsource (lib "eagle-import") (part "R-EU_V235/17_1MM"))
    )
    (comp (ref "R221")
      (value "2702")
      (footprint "eagle-import:R0805")
      (fields (field (name "MPN") "RC0805JR-074K7L"))
      (libsource (lib "eagle-import") (part "SMD-RES-4.7K-5%-1/8W(0805)"))
    )
    (comp (ref "R222")
      (value "2201")
      (footprint "eagle-import:R0805")
      (fields (field (name "MPN") "RC0805JR-072K2L"))
      (libsource (lib "eagle-import") (part "SMD-RES-2.2K-5%-1/8W(0805)"))
    )
    (comp (ref "R223")
      (value "(1002)")
      (footprint "eagle-import:R0805")
      (fields (field (name "MPN") "RC0805JR-074K7L"))
      (libsource (lib "eagle-import") (part "SMD-RES-4.7K-5%-1/8W(0805)"))
    )
    (comp (ref "R224")
      (value "1002")
      (footprint "eagle-import:R0805")
      (fields (field (name "MPN") "RC0805FR-0710KL"))
      (libsource (lib "eagle-import") (part "SMD-RES-10K-1%-1/8W(0805)"))
    )
    (comp (ref "R225")
      (value "102")
      (footprint "eagle-import:R0805")
      (fields (field (name "MPN") "RC0805JR-071KL"))
      (libsource (lib "eagle-import") (part "SMD-RES-1K-5%-1/8W(0805)"))
    )
    (comp (ref "R226")
      (value "2702")
      (footprint "eagle-import:R0805")
      (fields (field (name "MPN") "RC0805JR-074K7L"))
      (libsource (lib "eagle-import") (part "SMD-RES-4.7K-5%-1/8W(0805)"))
    )
    (comp (ref "R227")
      (value "102")
      (footprint "eagle-import:R0805")
      (fields (field (name "MPN") "RC0805JR-071KL"))
      (libsource (lib "eagle-import") (part "SMD-RES-1K-5%-1/8W(0805)"))
    )
    (comp (ref "R228")
      (value "102")
      (footprint "eagle-import:R0805")
      (fields (field (name "MPN") "RC0805JR-071KL"))
      (libsource (lib "eagle-import") (part "SMD-RES-1K-5%-1/8W(0805)"))
    )
    (comp (ref "R229")
      (value "13")
      (footprint "eagle-import:R1206")
      (fields (field (name "MPN") "RC1206JR-0713RL"))
      (libsource (lib "eagle-import") (part "SMD-RES-13R-5%-1/4W(1206)"))
    )
    (comp (ref "R230")
      (value "R_user")
      (footprint "eagle-import:R0805")
      (libsource (lib "eagle-import") (part "R-EU_R0805"))
    )
    (comp (ref "SJ5") (value "SJ") (footprint "eagle-import:SJ") (libsource (lib "eagle-import") (part "SJ")))
    (comp (ref "START4")
      (value "TPSB2.0")
      (footprint "eagle-import:B2.0")
      (libsource (lib "eagle-import") (part "TPSB2.0"))
    )
    (comp (ref "TP93")
      (value "TPSB2.0")
      (footprint "eagle-import:B2.0")
      (libsource (lib "eagle-import") (part "TPSB2.0"))
    )
    (comp (ref "TP94")
      (value "TPSB2.0")
      (footprint "eagle-import:B2.0")
      (libsource (lib "eagle-import") (part "TPSB2.0"))
    )
    (comp (ref "TP95")
      (value "TPSB2.0")
      (footprint "eagle-import:B2.0")
      (libsource (lib "eagle-import") (part "TPSB2.0"))
    )
    (comp (ref "TP96")
      (value "TPSB2.0")
      (footprint "eagle-import:B2.0")
      (libsource (lib "eagle-import") (part "TPSB2.0"))
    )
    (comp (ref "TP97")
      (value "TPSB2.0")
      (footprint "eagle-import:B2.0")
      (libsource (lib "eagle-import") (part "TPSB2.0"))
    )
    (comp (ref "TP98")
      (value "TPSB2.0")
      (footprint "eagle-import:B2.0")
      (libsource (lib "eagle-import") (part "TPSB2.0"))
    )
    (comp (ref "TP99")
      (value "TPSB2.0")
      (footprint "eagle-import:B2.0")
      (libsource (lib "eagle-import") (part "TPSB2.0"))
    )
    (comp (ref "TP100")
      (value "TPSB2.0")
      (footprint "eagle-import:B2.0")
      (libsource (lib "eagle-import") (part "TPSB2.0"))
    )
    (comp (ref "TP101")
      (value "TPSB2.0")
      (footprint "eagle-import:B2.0")
      (libsource (lib "eagle-import") (part "TPSB2.0"))
    )
    (comp (ref "TP102")
      (value "TPSB2.0")
      (footprint "eagle-import:B2.0")
      (libsource (lib "eagle-import") (part "TPSB2.0"))
    )
    (comp (ref "TP103")
      (value "TPSB2.0")
      (footprint "eagle-import:B2.0")
      (libsource (lib "eagle-import") (part "TPSB2.0"))
    )
    (comp (ref "TP104")
      (value "TPSB2.0")
      (footprint "eagle-import:B2.0")
      (libsource (lib "eagle-import") (part "TPSB2.0"))
    )
    (comp (ref "TP105")
      (value "TPSB2.0")
      (footprint "eagle-import:B2.0")
      (libsource (lib "eagle-import") (part "TPSB2.0"))
    )
    (comp (ref "TP106")
      (value "TPSB2.0")
      (footprint "eagle-import:B2.0")
      (libsource (lib "eagle-import") (part "TPSB2.0"))
    )
    (comp (ref "TP107")
      (value "TPSB2.0")
      (footprint "eagle-import:B2.0")
      (libsource (lib "eagle-import") (part "TPSB2.0"))
    )
    (comp (ref "TP108")
      (value "TPSB2.0")
      (footprint "eagle-import:B2.0")
      (libsource (lib "eagle-import") (part "TPSB2.0"))
    )
    (comp (ref "TP109")
      (value "TPSB2.0")
      (footprint "eagle-import:B2.0")
      (libsource (lib "eagle-import") (part "TPSB2.0"))
    )
    (comp (ref "TP110")
      (value "TPSB2.0")
      (footprint "eagle-import:B2.0")
      (libsource (lib "eagle-import") (part "TPSB2.0"))
    )
    (comp (ref "TP111")
      (value "TPSB1,27")
      (footprint "eagle-import:B1,27")
      (libsource (lib "eagle-import") (part "TPSB1,27"))
    )
    (comp (ref "TP112")
      (value "TPSB2.0")
      (footprint "eagle-import:B2.0")
      (libsource (lib "eagle-import") (part "TPSB2.0"))
    )
    (comp (ref "TP113")
      (value "TPSB2.0")
      (footprint "eagle-import:B2.0")
      (libsource (lib "eagle-import") (part "TPSB2.0"))
    )
    (comp (ref "TP114")
      (value "TPSB2.0")
      (footprint "eagle-import:B2.0")
      (libsource (lib "eagle-import") (part "TPSB2.0"))
    )
    (comp (ref "TP115")
      (value "TPSB2.0")
      (footprint "eagle-import:B2.0")
      (libsource (lib "eagle-import") (part "TPSB2.0"))
    )
    (comp (ref "X13")
      (value "CON_BMWV2")
      (footprint "eagle-import:24-PIN_V2")
      (libsource (lib "eagle-import") (part "CON_BMWV2"))
    )
    (comp (ref "X14")
      (value "22-23-2051")
      (footprint "eagle-import:22-23-2051")
      (fields (field (name "MF") "MOLEX"))
      (libsource (lib "eagle-import") (part "22-23-2051"))
    )
    (comp (ref "X15")
      (value "22-23-2021")
      (footprint "eagle-import:22-23-2021")
      (fields (field (name "MF") "MOLEX"))
      (libsource (lib "eagle-import") (part "22-23-2021"))
    )
  )
  (nets
    (net (code "1") (name "+10V") (class "Default")
      (node (ref "10V") (pin "TP") (pinfunction "PP_TP") (pintype "input"))
      (node (ref "10V1") (pin "TP") (pinfunction "PP_TP") (pintype "input"))
      (node (ref "10V10") (pin "TP") (pinfunction "PP_TP") (pintype "input"))
      (node (ref "10V11") (pin "TP") (pinfunction "PP_TP") (pintype "input"))
      (node (ref "10V2") (pin "TP") (pinfunction "PP_TP") (pintype "input"))
      (node (ref "10V3") (pin "TP") (pinfunction "PP_TP") (pintype "input"))
      (node (ref "10V4") (pin "TP") (pinfunction "PP_TP") (pintype "input"))
      (node (ref "10V5") (pin "TP") (pinfunction "PP_TP") (pintype "input"))
      (node (ref "10V6") (pin "TP") (pinfunction "PP_TP") (pintype "input"))
      (node (ref "10V7") (pin "TP") (pinfunction "PP_TP") (pintype "input"))
      (node (ref "10V8") (pin "TP") (pinfunction "PP_TP") (pintype "input"))
      (node (ref "10V9") (pin "TP") (pinfunction "PP_TP") (pintype "input"))
      (node (ref "C108") (pin "1") (pinfunction "1_1") (pintype "passive"))
      (node (ref "C118") (pin "1") (pinfunction "1_1") (pintype "passive"))
      (node (ref "C18") (pin "1") (pinfunction "1_1") (pintype "passive"))
      (node (ref "C2") (pin "1") (pinfunction "1_1") (pintype "passive"))
      (node (ref "C28") (pin "1") (pinfunction "1_1") (pintype "passive"))
      (node (ref "C38") (pin "1") (pinfunction "1_1") (pintype "passive"))
      (node (ref "C48") (pin "1") (pinfunction "1_1") (pintype "passive"))
      (node (ref "C58") (pin "1") (pinfunction "1_1") (pintype "passive"))
      (node (ref "C68") (pin "1") (pinfunction "1_1") (pintype "passive"))
      (node (ref "C78") (pin "1") (pinfunction "1_1") (pintype "passive"))
      (node (ref "C88") (pin "1") (pinfunction "1_1") (pintype "passive"))
      (node (ref "C98") (pin "1") (pinfunction "1_1") (pintype "passive"))
      (node (ref "IC10") (pin "4") (pinfunction "R_4") (pintype "input"))
      (node (ref "IC10") (pin "8") (pinfunction "V+_8") (pintype "power_in"))
      (node (ref "IC106") (pin "4") (pinfunction "R_4") (pintype "input"))
      (node (ref "IC106") (pin "8") (pinfunction "V+_8") (pintype "power_in"))
      (node (ref "IC107") (pin "13") (pinfunction "CD_13") (pintype "input"))
      (node (ref "IC107") (pin "16") (pinfunction "VDD_16") (pintype "power_in"))
      (node (ref "IC107") (pin "3") (pinfunction "CD_3") (pintype "input"))
      (node (ref "IC107") (pin "5") (pinfunction "B_5") (pintype "input"))
      (node (ref "IC108") (pin "1") (pinfunction "OUT_1") (pintype "passive"))
      (node (ref "IC11") (pin "13") (pinfunction "CD_13") (pintype "input"))
      (node (ref "IC11") (pin "16") (pinfunction "VDD_16") (pintype "power_in"))
      (node (ref "IC11") (pin "3") (pinfunction "CD_3") (pintype "input"))
      (node (ref "IC11") (pin "5") (pinfunction "B_5") (pintype "input"))
      (node (ref "IC117") (pin "4") (pinfunction "R_4") (pintype "input"))
      (node (ref "IC117") (pin "8") (pinfunction "V+_8") (pintype "power_in"))
      (node (ref "IC118") (pin "13") (pinfunction "CD_13") (pintype "input"))
      (node (ref "IC118") (pin "16") (pinfunction "VDD_16") (pintype "power_in"))
      (node (ref "IC118") (pin "3") (pinfunction "CD_3") (pintype "input"))
      (node (ref "IC118") (pin "5") (pinfunction "B_5") (pintype "input"))
      (node (ref "IC119") (pin "1") (pinfunction "OUT_1") (pintype "passive"))
      (node (ref "IC128") (pin "4") (pinfunction "R_4") (pintype "input"))
      (node (ref "IC128") (pin "8") (pinfunction "V+_8") (pintype "power_in"))
      (node (ref "IC129") (pin "13") (pinfunction "CD_13") (pintype "input"))
      (node (ref "IC129") (pin "16") (pinfunction "VDD_16") (pintype "power_in"))
      (node (ref "IC129") (pin "3") (pinfunction "CD_3") (pintype "input"))
      (node (ref "IC129") (pin "5") (pinfunction "B_5") (pintype "input"))
      (node (ref "IC130") (pin "1") (pinfunction "OUT_1") (pintype "passive"))
      (node (ref "IC18") (pin "4") (pinfunction "R_4") (pintype "input"))
      (node (ref "IC18") (pin "8") (pinfunction "V+_8") (pintype "power_in"))
      (node (ref "IC19") (pin "13") (pinfunction "CD_13") (pintype "input"))
      (node (ref "IC19") (pin "16") (pinfunction "VDD_16") (pintype "power_in"))
      (node (ref "IC19") (pin "3") (pinfunction "CD_3") (pintype "input"))
      (node (ref "IC19") (pin "5") (pinfunction "B_5") (pintype "input"))
      (node (ref "IC20") (pin "1") (pinfunction "OUT_1") (pintype "passive"))
      (node (ref "IC29") (pin "4") (pinfunction "R_4") (pintype "input"))
      (node (ref "IC29") (pin "8") (pinfunction "V+_8") (pintype "power_in"))
      (node (ref "IC30") (pin "13") (pinfunction "CD_13") (pintype "input"))
      (node (ref "IC30") (pin "16") (pinfunction "VDD_16") (pintype "power_in"))
      (node (ref "IC30") (pin "3") (pinfunction "CD_3") (pintype "input"))
      (node (ref "IC30") (pin "5") (pinfunction "B_5") (pintype "input"))
      (node (ref "IC31") (pin "1") (pinfunction "OUT_1") (pintype "passive"))
      (node (ref "IC4") (pin "1") (pinfunction "OUT_1") (pintype "passive"))
      (node (ref "IC40") (pin "4") (pinfunction "R_4") (pintype "input"))
      (node (ref "IC40") (pin "8") (pinfunction "V+_8") (pintype "power_in"))
      (node (ref "IC41") (pin "13") (pinfunction "CD_13") (pintype "input"))
      (node (ref "IC41") (pin "16") (pinfunction "VDD_16") (pintype "power_in"))
      (node (ref "IC41") (pin "3") (pinfunction "CD_3") (pintype "input"))
      (node (ref "IC41") (pin "5") (pinfunction "B_5") (pintype "input"))
      (node (ref "IC42") (pin "1") (pinfunction "OUT_1") (pintype "passive"))
      (node (ref "IC51") (pin "4") (pinfunction "R_4") (pintype "input"))
      (node (ref "IC51") (pin "8") (pinfunction "V+_8") (pintype "power_in"))
      (node (ref "IC52") (pin "13") (pinfunction "CD_13") (pintype "input"))
      (node (ref "IC52") (pin "16") (pinfunction "VDD_16") (pintype "power_in"))
      (node (ref "IC52") (pin "3") (pinfunction "CD_3") (pintype "input"))
      (node (ref "IC52") (pin "5") (pinfunction "B_5") (pintype "input"))
      (node (ref "IC53") (pin "1") (pinfunction "OUT_1") (pintype "passive"))
      (node (ref "IC62") (pin "4") (pinfunction "R_4") (pintype "input"))
      (node (ref "IC62") (pin "8") (pinfunction "V+_8") (pintype "power_in"))
      (node (ref "IC63") (pin "13") (pinfunction "CD_13") (pintype "input"))
      (node (ref "IC63") (pin "16") (pinfunction "VDD_16") (pintype "power_in"))
      (node (ref "IC63") (pin "3") (pinfunction "CD_3") (pintype "input"))
      (node (ref "IC63") (pin "5") (pinfunction "B_5") (pintype "input"))
      (node (ref "IC64") (pin "1") (pinfunction "OUT_1") (pintype "passive"))
      (node (ref "IC73") (pin "4") (pinfunction "R_4") (pintype "input"))
      (node (ref "IC73") (pin "8") (pinfunction "V+_8") (pintype "power_in"))
      (node (ref "IC74") (pin "13") (pinfunction "CD_13") (pintype "input"))
      (node (ref "IC74") (pin "16") (pinfunction "VDD_16") (pintype "power_in"))
      (node (ref "IC74") (pin "3") (pinfunction "CD_3") (pintype "input"))
      (node (ref "IC74") (pin "5") (pinfunction "B_5") (pintype "input"))
      (node (ref "IC75") (pin "1") (pinfunction "OUT_1") (pintype "passive"))
      (node (ref "IC84") (pin "4") (pinfunction "R_4") (pintype "input"))
      (node (ref "IC84") (pin "8") (pinfunction "V+_8") (pintype "power_in"))
      (node (ref "IC85") (pin "13") (pinfunction "CD_13") (pintype "input"))
      (node (ref "IC85") (pin "16") (pinfunction "VDD_16") (pintype "power_in"))
      (node (ref "IC85") (pin "3") (pinfunction "CD_3") (pintype "input"))
      (node (ref "IC85") (pin "5") (pinfunction "B_5") (pintype "input"))
      (node (ref "IC86") (pin "1") (pinfunction "OUT_1") (pintype "passive"))
      (node (ref "IC95") (pin "4") (pinfunction "R_4") (pintype "input"))
      (node (ref "IC95") (pin "8") (pinfunction "V+_8") (pintype "power_in"))
      (node (ref "IC96") (pin "13") (pinfunction "CD_13") (pintype "input"))
      (node (ref "IC96") (pin "16") (pinfunction "VDD_16") (pintype "power_in"))
      (node (ref "IC96") (pin "3") (pinfunction "CD_3") (pintype "input"))
      (node (ref "IC96") (pin "5") (pinfunction "B_5") (pintype "input"))
      (node (ref "IC97") (pin "1") (pinfunction "OUT_1") (pintype "passive"))
      (node (ref "R129") (pin "2") (pinfunction "2_2") (pintype "passive"))
      (node (ref "R175") (pin "2") (pinfunction "2_2") (pintype "passive"))
      (node (ref "R221") (pin "2") (pinfunction "2_2") (pintype "passive"))
      (node (ref "R267") (pin "2") (pinfunction "2_2") (pintype "passive"))
      (node (ref "R313") (pin "2") (pinfunction "2_2") (pintype "passive"))
      (node (ref "R359") (pin "2") (pinfunction "2_2") (pintype "passive"))
      (node (ref "R405") (pin "2") (pinfunction "2_2") (pintype "passive"))
      (node (ref "R45") (pin "2") (pinfunction "2_2") (pintype "passive"))
      (node (ref "R451") (pin "2") (pinfunction "2_2") (pintype "passive"))
      (node (ref "R497") (pin "2") (pinfunction "2_2") (pintype "passive"))
      (node (ref "R543") (pin "2") (pinfunction "2_2") (pintype "passive"))
      (node (ref "R83") (pin "2") (pinfunction "2_2") (pintype "passive"))
    )
    (net (code "2") (name "+12V") (class "Default")
      (node (ref "10") (pin "1") (pinfunction "KL_1") (pintype "passive"))
      (node (ref "12") (pin "1") (pinfunction "KL_1") (pintype "passive"))
      (node (ref "14") (pin "1") (pinfunction "KL_1") (pintype "passive"))
      (node (ref "16") (pin "1") (pinfunction "KL_1") (pintype "passive"))
      (node (ref "18") (pin "1") (pinfunction "KL_1") (pintype "passive"))
      (node (ref "2") (pin "1") (pinfunction "KL_1") (pintype "passive"))
      (node (ref "20") (pin "1") (pinfunction "KL_1") (pintype "passive"))
      (node (ref "22") (pin "1") (pinfunction "KL_1") (pintype "passive"))
      (node (ref "24") (pin "1") (pinfunction "KL_1") (pintype "passive"))
      (node (ref "4") (pin "1") (pinfunction "KL_1") (pintype "passive"))
      (node (ref "6") (pin "1") (pinfunction "KL_1") (pintype "passive"))
      (node (ref "8") (pin "1") (pinfunction "KL_1") (pintype "passive"))
      (node (ref "D1") (pin "C") (pinfunction "C_C") (pintype "passive"))
      (node (ref "D107") (pin "C") (pinfunction "C_C") (pintype "passive"))
      (node (ref "D119") (pin "C") (pinfunction "C_C") (pintype "passive"))
      (node (ref "D131") (pin "C") (pinfunction "C_C") (pintype "passive"))
      (node (ref "D143") (pin "C") (pinfunction "C_C") (pintype "passive"))
      (node (ref "D23") (pin "C") (pinfunction "C_C") (pintype "passive"))
      (node (ref "D35") (pin "C") (pinfunction "C_C") (pintype "passive"))
      (node (ref "D47") (pin "C") (pinfunction "C_C") (pintype "passive"))
      (node (ref "D59") (pin "C") (pinfunction "C_C") (pintype "passive"))
      (node (ref "D71") (pin "C") (pinfunction "C_C") (pintype "passive"))
      (node (ref "D83") (pin "C") (pinfunction "C_C") (pintype "passive"))
      (node (ref "D95") (pin "C") (pinfunction "C_C") (pintype "passive"))
      (node (ref "IC100") (pin "16") (pinfunction "VDD_16") (pintype "power_in"))
      (node (ref "IC101") (pin "IN") (pinfunction "IN_IN") (pintype "input"))
      (node (ref "IC103") (pin "9") (pinfunction "CD+_9") (pintype "passive"))
      (node (ref "IC105") (pin "3") (pinfunction "IN_3") (pintype "input"))
      (node (ref "IC108") (pin "3") (pinfunction "IN_3") (pintype "input"))
      (node (ref "IC111") (pin "16") (pinfunction "VDD_16") (pintype "power_in"))
      (node (ref "IC112") (pin "IN") (pinfunction "IN_IN") (pintype "input"))
      (node (ref "IC114") (pin "9") (pinfunction "CD+_9") (pintype "passive"))
      (node (ref "IC116") (pin "3") (pinfunction "IN_3") (pintype "input"))
      (node (ref "IC119") (pin "3") (pinfunction "IN_3") (pintype "input"))
      (node (ref "IC12") (pin "16") (pinfunction "VDD_16") (pintype "power_in"))
      (node (ref "IC122") (pin "16") (pinfunction "VDD_16") (pintype "power_in"))
      (node (ref "IC123") (pin "IN") (pinfunction "IN_IN") (pintype "input"))
      (node (ref "IC125") (pin "9") (pinfunction "CD+_9") (pintype "passive"))
      (node (ref "IC127") (pin "3") (pinfunction "IN_3") (pintype "input"))
      (node (ref "IC13") (pin "IN") (pinfunction "IN_IN") (pintype "input"))
      (node (ref "IC130") (pin "3") (pinfunction "IN_3") (pintype "input"))
      (node (ref "IC15") (pin "9") (pinfunction "CD+_9") (pintype "passive"))
      (node (ref "IC17") (pin "3") (pinfunction "IN_3") (pintype "input"))
      (node (ref "IC2") (pin "3") (pinfunction "IN_3") (pintype "input"))
      (node (ref "IC20") (pin "3") (pinfunction "IN_3") (pintype "input"))
      (node (ref "IC23") (pin "16") (pinfunction "VDD_16") (pintype "power_in"))
      (node (ref "IC24") (pin "IN") (pinfunction "IN_IN") (pintype "input"))
      (node (ref "IC26") (pin "9") (pinfunction "CD+_9") (pintype "passive"))
      (node (ref "IC28") (pin "3") (pinfunction "IN_3") (pintype "input"))
      (node (ref "IC3") (pin "IN") (pinfunction "IN_IN") (pintype "input"))
      (node (ref "IC31") (pin "3") (pinfunction "IN_3") (pintype "input"))
      (node (ref "IC34") (pin "16") (pinfunction "VDD_16") (pintype "power_in"))
      (node (ref "IC35") (pin "IN") (pinfunction "IN_IN") (pintype "input"))
      (node (ref "IC37") (pin "9") (pinfunction "CD+_9") (pintype "passive"))
      (node (ref "IC39") (pin "3") (pinfunction "IN_3") (pintype "input"))
      (node (ref "IC4") (pin "3") (pinfunction "IN_3") (pintype "input"))
      (node (ref "IC42") (pin "3") (pinfunction "IN_3") (pintype "input"))
      (node (ref "IC45") (pin "16") (pinfunction "VDD_16") (pintype "power_in"))
      (node (ref "IC46") (pin "IN") (pinfunction "IN_IN") (pintype "input"))
      (node (ref "IC48") (pin "9") (pinfunction "CD+_9") (pintype "passive"))
      (node (ref "IC5") (pin "16") (pinfunction "VDD_16") (pintype "power_in"))
      (node (ref "IC50") (pin "3") (pinfunction "IN_3") (pintype "input"))
      (node (ref "IC53") (pin "3") (pinfunction "IN_3") (pintype "input"))
      (node (ref "IC56") (pin "16") (pinfunction "VDD_16") (pintype "power_in"))
      (node (ref "IC57") (pin "IN") (pinfunction "IN_IN") (pintype "input"))
      (node (ref "IC59") (pin "9") (pinfunction "CD+_9") (pintype "passive"))
      (node (ref "IC61") (pin "3") (pinfunction "IN_3") (pintype "input"))
      (node (ref "IC64") (pin "3") (pinfunction "IN_3") (pintype "input"))
      (node (ref "IC67") (pin "16") (pinfunction "VDD_16") (pintype "power_in"))
      (node (ref "IC68") (pin "IN") (pinfunction "IN_IN") (pintype "input"))
      (node (ref "IC7") (pin "9") (pinfunction "CD+_9") (pintype "passive"))
      (node (ref "IC70") (pin "9") (pinfunction "CD+_9") (pintype "passive"))
      (node (ref "IC72") (pin "3") (pinfunction "IN_3") (pintype "input"))
      (node (ref "IC75") (pin "3") (pinfunction "IN_3") (pintype "input"))
      (node (ref "IC78") (pin "16") (pinfunction "VDD_16") (pintype "power_in"))
      (node (ref "IC79") (pin "IN") (pinfunction "IN_IN") (pintype "input"))
      (node (ref "IC81") (pin "9") (pinfunction "CD+_9") (pintype "passive"))
      (node (ref "IC83") (pin "3") (pinfunction "IN_3") (pintype "input"))
      (node (ref "IC86") (pin "3") (pinfunction "IN_3") (pintype "input"))
      (node (ref "IC89") (pin "16") (pinfunction "VDD_16") (pintype "power_in"))
      (node (ref "IC90") (pin "IN") (pinfunction "IN_IN") (pintype "input"))
      (node (ref "IC92") (pin "9") (pinfunction "CD+_9") (pintype "passive"))
      (node (ref "IC94") (pin "3") (pinfunction "IN_3") (pintype "input"))
      (node (ref "IC97") (pin "3") (pinfunction "IN_3") (pintype "input"))
      (node (ref "JP1") (pin "2") (pinfunction "2_2") (pintype "passive"))
      (node (ref "JP11") (pin "2") (pinfunction "2_2") (pintype "passive"))
      (node (ref "JP16") (pin "2") (pinfunction "2_2") (pintype "passive"))
      (node (ref "JP21") (pin "2") (pinfunction "2_2") (pintype "passive"))
      (node (ref "JP26") (pin "2") (pinfunction "2_2") (pintype "passive"))
      (node (ref "JP31") (pin "2") (pinfunction "2_2") (pintype "passive"))
      (node (ref "JP36") (pin "2") (pinfunction "2_2") (pintype "passive"))
      (node (ref "JP41") (pin "2") (pinfunction "2_2") (pintype "passive"))
      (node (ref "JP46") (pin "2") (pinfunction "2_2") (pintype "passive"))
      (node (ref "JP51") (pin "2") (pinfunction "2_2") (pintype "passive"))
      (node (ref "JP56") (pin "2") (pinfunction "2_2") (pintype "passive"))
      (node (ref "JP6") (pin "2") (pinfunction "2_2") (pintype "passive"))
      (node (ref "Q11") (pin "3") (pinfunction "E_3") (pintype "passive"))
      (node (ref "Q15") (pin "3") (pinfunction "E_3") (pintype "passive"))
      (node (ref "Q18") (pin "3") (pinfunction "E_3") (pintype "passive"))
      (node (ref "Q22") (pin "3") (pinfunction "E_3") (pintype "passive"))
      (node (ref "Q25") (pin "3") (pinfunction "E_3") (pintype "passive"))
      (node (ref "Q29") (pin "3") (pinfunction "E_3") (pintype "passive"))
      (node (ref "Q32") (pin "3") (pinfunction "E_3") (pintype "passive"))
      (node (ref "Q36") (pin "3") (pinfunction "E_3") (pintype "passive"))
      (node (ref "Q39") (pin "3") (pinfunction "E_3") (pintype "passive"))
      (node (ref "Q4") (pin "3") (pinfunction "E_3") (pintype "passive"))
      (node (ref "Q43") (pin "3") (pinfunction "E_3") (pintype "passive"))
      (node (ref "Q46") (pin "3") (pinfunction "E_3") (pintype "passive"))
      (node (ref "Q5") (pin "3") (pinfunction "E_3") (pintype "passive"))
      (node (ref "Q50") (pin "3") (pinfunction "E_3") (pintype "passive"))
      (node (ref "Q53") (pin "3") (pinfunction "E_3") (pintype "passive"))
      (node (ref "Q57") (pin "3") (pinfunction "E_3") (pintype "passive"))
      (node (ref "Q60") (pin "3") (pinfunction "E_3") (pintype "passive"))
      (node (ref "Q64") (pin "3") (pinfunction "E_3") (pintype "passive"))
      (node (ref "Q67") (pin "3") (pinfunction "E_3") (pintype "passive"))
      (node (ref "Q71") (pin "3") (pinfunction "E_3") (pintype "passive"))
      (node (ref "Q74") (pin "3") (pinfunction "E_3") (pintype "passive"))
      (node (ref "Q78") (pin "3") (pinfunction "E_3") (pintype "passive"))
      (node (ref "Q8") (pin "3") (pinfunction "E_3") (pintype "passive"))
      (node (ref "Q81") (pin "3") (pinfunction "E_3") (pintype "passive"))
      (node (ref "R10") (pin "2") (pinfunction "2_2") (pintype "passive"))
      (node (ref "R11") (pin "2") (pinfunction "2_2") (pintype "passive"))
      (node (ref "R117") (pin "1") (pinfunction "1_1") (pintype "passive"))
      (node (ref "R118") (pin "1") (pinfunction "1_1") (pintype "passive"))
      (node (ref "R123") (pin "1") (pinfunction "1_1") (pintype "passive"))
      (node (ref "R141") (pin "2") (pinfunction "2_2") (pintype "passive"))
      (node (ref "R142") (pin "2") (pinfunction "2_2") (pintype "passive"))
      (node (ref "R143") (pin "2") (pinfunction "2_2") (pintype "passive"))
      (node (ref "R144") (pin "2") (pinfunction "2_2") (pintype "passive"))
      (node (ref "R163") (pin "1") (pinfunction "1_1") (pintype "passive"))
      (node (ref "R164") (pin "1") (pinfunction "1_1") (pintype "passive"))
      (node (ref "R169") (pin "1") (pinfunction "1_1") (pintype "passive"))
      (node (ref "R187") (pin "2") (pinfunction "2_2") (pintype "passive"))
      (node (ref "R188") (pin "2") (pinfunction "2_2") (pintype "passive"))
      (node (ref "R189") (pin "2") (pinfunction "2_2") (pintype "passive"))
      (node (ref "R190") (pin "2") (pinfunction "2_2") (pintype "passive"))
      (node (ref "R2") (pin "1") (pinfunction "1_1") (pintype "passive"))
      (node (ref "R209") (pin "1") (pinfunction "1_1") (pintype "passive"))
      (node (ref "R210") (pin "1") (pinfunction "1_1") (pintype "passive"))
      (node (ref "R215") (pin "1") (pinfunction "1_1") (pintype "passive"))
      (node (ref "R233") (pin "2") (pinfunction "2_2") (pintype "passive"))
      (node (ref "R234") (pin "2") (pinfunction "2_2") (pintype "passive"))
      (node (ref "R235") (pin "2") (pinfunction "2_2") (pintype "passive"))
      (node (ref "R236") (pin "2") (pinfunction "2_2") (pintype "passive"))
      (node (ref "R255") (pin "1") (pinfunction "1_1") (pintype "passive"))
      (node (ref "R256") (pin "1") (pinfunction "1_1") (pintype "passive"))
      (node (ref "R261") (pin "1") (pinfunction "1_1") (pintype "passive"))
      (node (ref "R279") (pin "2") (pinfunction "2_2") (pintype "passive"))
      (node (ref "R280") (pin "2") (pinfunction "2_2") (pintype "passive"))
      (node (ref "R281") (pin "2") (pinfunction "2_2") (pintype "passive"))
      (node (ref "R282") (pin "2") (pinfunction "2_2") (pintype "passive"))
      (node (ref "R29") (pin "2") (pinfunction "2_2") (pintype "passive"))
      (node (ref "R301") (pin "1") (pinfunction "1_1") (pintype "passive"))
      (node (ref "R302") (pin "1") (pinfunction "1_1") (pintype "passive"))
      (node (ref "R307") (pin "1") (pinfunction "1_1") (pintype "passive"))
      (node (ref "R325") (pin "2") (pinfunction "2_2") (pintype "passive"))
      (node (ref "R326") (pin "2") (pinfunction "2_2") (pintype "passive"))
      (node (ref "R327") (pin "2") (pinfunction "2_2") (pintype "passive"))
      (node (ref "R328") (pin "2") (pinfunction "2_2") (pintype "passive"))
      (node (ref "R347") (pin "1") (pinfunction "1_1") (pintype "passive"))
      (node (ref "R348") (pin "1") (pinfunction "1_1") (pintype "passive"))
      (node (ref "R35") (pin "1") (pinfunction "1_1") (pintype "passive"))
      (node (ref "R353") (pin "1") (pinfunction "1_1") (pintype "passive"))
      (node (ref "R371") (pin "2") (pinfunction "2_2") (pintype "passive"))
      (node (ref "R372") (pin "2") (pinfunction "2_2") (pintype "passive"))
      (node (ref "R373") (pin "2") (pinfunction "2_2") (pintype "passive"))
      (node (ref "R374") (pin "2") (pinfunction "2_2") (pintype "passive"))
      (node (ref "R393") (pin "1") (pinfunction "1_1") (pintype "passive"))
      (node (ref "R394") (pin "1") (pinfunction "1_1") (pintype "passive"))
      (node (ref "R399") (pin "1") (pinfunction "1_1") (pintype "passive"))
      (node (ref "R417") (pin "2") (pinfunction "2_2") (pintype "passive"))
      (node (ref "R418") (pin "2") (pinfunction "2_2") (pintype "passive"))
      (node (ref "R419") (pin "2") (pinfunction "2_2") (pintype "passive"))
      (node (ref "R420") (pin "2") (pinfunction "2_2") (pintype "passive"))
      (node (ref "R439") (pin "1") (pinfunction "1_1") (pintype "passive"))
      (node (ref "R440") (pin "1") (pinfunction "1_1") (pintype "passive"))
      (node (ref "R445") (pin "1") (pinfunction "1_1") (pintype "passive"))
      (node (ref "R463") (pin "2") (pinfunction "2_2") (pintype "passive"))
      (node (ref "R464") (pin "2") (pinfunction "2_2") (pintype "passive"))
      (node (ref "R465") (pin "2") (pinfunction "2_2") (pintype "passive"))
      (node (ref "R466") (pin "2") (pinfunction "2_2") (pintype "passive"))
      (node (ref "R485") (pin "1") (pinfunction "1_1") (pintype "passive"))
      (node (ref "R486") (pin "1") (pinfunction "1_1") (pintype "passive"))
      (node (ref "R49") (pin "2") (pinfunction "2_2") (pintype "passive"))
      (node (ref "R491") (pin "1") (pinfunction "1_1") (pintype "passive"))
      (node (ref "R50") (pin "2") (pinfunction "2_2") (pintype "passive"))
      (node (ref "R509") (pin "2") (pinfunction "2_2") (pintype "passive"))
      (node (ref "R51") (pin "2") (pinfunction "2_2") (pintype "passive"))
      (node (ref "R510") (pin "2") (pinfunction "2_2") (pintype "passive"))
      (node (ref "R511") (pin "2") (pinfunction "2_2") (pintype "passive"))
      (node (ref "R512") (pin "2") (pinfunction "2_2") (pintype "passive"))
      (node (ref "R52") (pin "2") (pinfunction "2_2") (pintype "passive"))
      (node (ref "R531") (pin "1") (pinfunction "1_1") (pintype "passive"))
      (node (ref "R532") (pin "1") (pinfunction "1_1") (pintype "passive"))
      (node (ref "R537") (pin "1") (pinfunction "1_1") (pintype "passive"))
      (node (ref "R6") (pin "1") (pinfunction "1_1") (pintype "passive"))
      (node (ref "R71") (pin "1") (pinfunction "1_1") (pintype "passive"))
      (node (ref "R72") (pin "1") (pinfunction "1_1") (pintype "passive"))
      (node (ref "R77") (pin "1") (pinfunction "1_1") (pintype "passive"))
      (node (ref "R9") (pin "2") (pinfunction "2_2") (pintype "passive"))
      (node (ref "R95") (pin "2") (pinfunction "2_2") (pintype "passive"))
      (node (ref "R96") (pin "2") (pinfunction "2_2") (pintype "passive"))
      (node (ref "R97") (pin "2") (pinfunction "2_2") (pintype "passive"))
      (node (ref "R98") (pin "2") (pinfunction "2_2") (pintype "passive"))
      (node (ref "TP114") (pin "TP") (pinfunction "PP_TP") (pintype "input"))
      (node (ref "TP12") (pin "TP") (pinfunction "PP_TP") (pintype "input"))
      (node (ref "TP137") (pin "TP") (pinfunction "PP_TP") (pintype "input"))
      (node (ref "TP160") (pin "TP") (pinfunction "PP_TP") (pintype "input"))
      (node (ref "TP183") (pin "TP") (pinfunction "PP_TP") (pintype "input"))
      (node (ref "TP206") (pin "TP") (pinfunction "PP_TP") (pintype "input"))
      (node (ref "TP229") (pin "TP") (pinfunction "PP_TP") (pintype "input"))
      (node (ref "TP252") (pin "TP") (pinfunction "PP_TP") (pintype "input"))
      (node (ref "TP275") (pin "TP") (pinfunction "PP_TP") (pintype "input"))
      (node (ref "TP45") (pin "TP") (pinfunction "PP_TP") (pintype "input"))
      (node (ref "TP68") (pin "TP") (pinfunction "PP_TP") (pintype "input"))
      (node (ref "TP91") (pin "TP") (pinfunction "PP_TP") (pintype "input"))
      (node (ref "X1") (pin "6") (pinfunction "6_6") (pintype "passive"))
      (node (ref "X10") (pin "6") (pinfunction "6_6") (pintype "passive"))
      (node (ref "X11") (pin "1") (pinfunction "S_1") (pintype "passive"))
      (node (ref "X13") (pin "6") (pinfunction "6_6") (pintype "passive"))
      (node (ref "X14") (pin "1") (pinfunction "S_1") (pintype "passive"))
      (node (ref "X16") (pin "6") (pinfunction "6_6") (pintype "passive"))
      (node (ref "X17") (pin "1") (pinfunction "S_1") (pintype "passive"))
      (node (ref "X19") (pin "6") (pinfunction "6_6") (pintype "passive"))
      (node (ref "X20") (pin "1") (pinfunction "S_1") (pintype "passive"))
      (node (ref "X22") (pin "6") (pinfunction "6_6") (pintype "passive"))
      (node (ref "X23") (pin "1") (pinfunction "S_1") (pintype "passive"))
      (node (ref "X25") (pin "6") (pinfunction "6_6") (pintype "passive"))
      (node (ref "X26") (pin "1") (pinfunction "S_1") (pintype "passive"))
      (node (ref "X28") (pin "6") (pinfunction "6_6") (pintype "passive"))
      (node (ref "X29") (pin "1") (pinfunction "S_1") (pintype "passive"))
      (node (ref "X3") (pin "1") (pinfunction "S_1") (pintype "passive"))
      (node (ref "X31") (pin "6") (pinfunction "6_6") (pintype "passive"))
      (node (ref "X32") (pin "1") (pinfunction "S_1") (pintype "passive"))
      (node (ref "X34") (pin "6") (pinfunction "6_6") (pintype "passive"))
      (node (ref "X35") (pin "1") (pinfunction "S_1") (pintype "passive"))
      (node (ref "X4") (pin "6") (pinfunction "6_6") (pintype "passive"))
      (node (ref "X5") (pin "1") (pinfunction "S_1") (pintype "passive"))
      (node (ref "X7") (pin "6") (pinfunction "6_6") (pintype "passive"))
      (node (ref "X8") (pin "1") (pinfunction "S_1") (pintype "passive"))
    )
    (net (code "3") (name "GND") (class "Default")
      (node (ref "1") (pin "12") (pinfunction "KL_12") (pintype "passive"))
      (node (ref "11") (pin "12") (pinfunction "KL_12") (pintype "passive"))
      (node (ref "13") (pin "12") (pinfunction "KL_12") (pintype "passive"))
      (node (ref "15") (pin "12") (pinfunction "KL_12") (pintype "passive"))
      (node (ref "17") (pin "12") (pinfunction "KL_12") (pintype "passive"))
      (node (ref "19") (pin "12") (pinfunction "KL_12") (pintype "passive"))
      (node (ref "21") (pin "12") (pinfunction "KL_12") (pintype "passive"))
      (node (ref "23") (pin "12") (pinfunction "KL_12") (pintype "passive"))
      (node (ref "3") (pin "12") (pinfunction "KL_12") (pintype "passive"))
      (node (ref "5") (pin "12") (pinfunction "KL_12") (pintype "passive"))
      (node (ref "7") (pin "12") (pinfunction "KL_12") (pintype "passive"))
      (node (ref "9") (pin "12") (pinfunction "KL_12") (pintype "passive"))
      (node (ref "C1") (pin "2") (pinfunction "2_2") (pintype "passive"))
      (node (ref "C10") (pin "2") (pinfunction "2_2") (pintype "passive"))
      (node (ref "C100") (pin "2") (pinfunction "2_2") (pintype "passive"))
      (node (ref "C101") (pin "2") (pinfunction "2_2") (pintype "passive"))
      (node (ref "C102") (pin "2") (pinfunction "2_2") (pintype "passive"))
      (node (ref "C103") (pin "2") (pinfunction "2_2") (pintype "passive"))
      (node (ref "C104") (pin "2") (pinfunction "2_2") (pintype "passive"))
      (node (ref "C105") (pin "2") (pinfunction "2_2") (pintype "passive"))
      (node (ref "C106") (pin "1") (pinfunction "1_1") (pintype "passive"))
      (node (ref "C107") (pin "1") (pinfunction "1_1") (pintype "passive"))
      (node (ref "C108") (pin "2") (pinfunction "2_2") (pintype "passive"))
      (node (ref "C109") (pin "2") (pinfunction "2_2") (pintype "passive"))
      (node (ref "C11") (pin "2") (pinfunction "2_2") (pintype "passive"))
      (node (ref "C110") (pin "2") (pinfunction "2_2") (pintype "passive"))
      (node (ref "C111") (pin "2") (pinfunction "2_2") (pintype "passive"))
      (node (ref "C112") (pin "2") (pinfunction "2_2") (pintype "passive"))
      (node (ref "C113") (pin "2") (pinfunction "2_2") (pintype "passive"))
      (node (ref "C114") (pin "2") (pinfunction "2_2") (pintype "passive"))
      (node (ref "C115") (pin "2") (pinfunction "2_2") (pintype "passive"))
      (node (ref "C116") (pin "1") (pinfunction "1_1") (pintype "passive"))
      (node (ref "C117") (pin "1") (pinfunction "1_1") (pintype "passive"))
      (node (ref "C118") (pin "2") (pinfunction "2_2") (pintype "passive"))
      (node (ref "C119") (pin "2") (pinfunction "2_2") (pintype "passive"))
      (node (ref "C12") (pin "2") (pinfunction "2_2") (pintype "passive"))
      (node (ref "C120") (pin "2") (pinfunction "2_2") (pintype "passive"))
      (node (ref "C13") (pin "2") (pinfunction "2_2") (pintype "passive"))
      (node (ref "C14") (pin "2") (pinfunction "2_2") (pintype "passive"))
      (node (ref "C15") (pin "2") (pinfunction "2_2") (pintype "passive"))
      (node (ref "C16") (pin "1") (pinfunction "1_1") (pintype "passive"))
      (node (ref "C17") (pin "1") (pinfunction "1_1") (pintype "passive"))
      (node (ref "C18") (pin "2") (pinfunction "2_2") (pintype "passive"))
      (node (ref "C19") (pin "2") (pinfunction "2_2") (pintype "passive"))
      (node (ref "C2") (pin "2") (pinfunction "2_2") (pintype "passive"))
      (node (ref "C20") (pin "2") (pinfunction "2_2") (pintype "passive"))
      (node (ref "C21") (pin "2") (pinfunction "2_2") (pintype "passive"))
      (node (ref "C22") (pin "2") (pinfunction "2_2") (pintype "passive"))
      (node (ref "C23") (pin "2") (pinfunction "2_2") (pintype "passive"))
      (node (ref "C24") (pin "2") (pinfunction "2_2") (pintype "passive"))
      (node (ref "C25") (pin "2") (pinfunction "2_2") (pintype "passive"))
      (node (ref "C26") (pin "1") (pinfunction "1_1") (pintype "passive"))
      (node (ref "C27") (pin "1") (pinfunction "1_1") (pintype "passive"))
      (node (ref "C28") (pin "2") (pinfunction "2_2") (pintype "passive"))
      (node (ref "C29") (pin "2") (pinfunction "2_2") (pintype "passive"))
      (node (ref "C3") (pin "2") (pinfunction "2_2") (pintype "passive"))
      (node (ref "C30") (pin "2") (pinfunction "2_2") (pintype "passive"))
      (node (ref "C31") (pin "2") (pinfunction "2_2") (pintype "passive"))
      (node (ref "C32") (pin "2") (pinfunction "2_2") (pintype "passive"))
      (node (ref "C33") (pin "2") (pinfunction "2_2") (pintype "passive"))
      (node (ref "C34") (pin "2") (pinfunction "2_2") (pintype "passive"))
      (node (ref "C35") (pin "2") (pinfunction "2_2") (pintype "passive"))
      (node (ref "C36") (pin "1") (pinfunction "1_1") (pintype "passive"))
      (node (ref "C37") (pin "1") (pinfunction "1_1") (pintype "passive"))
      (node (ref "C38") (pin "2") (pinfunction "2_2") (pintype "passive"))
      (node (ref "C39") (pin "2") (pinfunction "2_2") (pintype "passive"))
      (node (ref "C4") (pin "2") (pinfunction "2_2") (pintype "passive"))
      (node (ref "C40") (pin "2") (pinfunction "2_2") (pintype "passive"))
      (node (ref "C41") (pin "2") (pinfunction "2_2") (pintype "passive"))
      (node (ref "C42") (pin "2") (pinfunction "2_2") (pintype "passive"))
      (node (ref "C43") (pin "2") (pinfunction "2_2") (pintype "passive"))
      (node (ref "C44") (pin "2") (pinfunction "2_2") (pintype "passive"))
      (node (ref "C45") (pin "2") (pinfunction "2_2") (pintype "passive"))
      (node (ref "C46") (pin "1") (pinfunction "1_1") (pintype "passive"))
      (node (ref "C47") (pin "1") (pinfunction "1_1") (pintype "passive"))
      (node (ref "C48") (pin "2") (pinfunction "2_2") (pintype "passive"))
      (node (ref "C49") (pin "2") (pinfunction "2_2") (pintype "passive"))
      (node (ref "C5") (pin "2") (pinfunction "2_2") (pintype "passive"))
      (node (ref "C50") (pin "2") (pinfunction "2_2") (pintype "passive"))
      (node (ref "C51") (pin "2") (pinfunction "2_2") (pintype "passive"))
      (node (ref "C52") (pin "2") (pinfunction "2_2") (pintype "passive"))
      (node (ref "C53") (pin "2") (pinfunction "2_2") (pintype "passive"))
      (node (ref "C54") (pin "2") (pinfunction "2_2") (pintype "passive"))
      (node (ref "C55") (pin "2") (pinfunction "2_2") (pintype "passive"))
      (node (ref "C56") (pin "1") (pinfunction "1_1") (pintype "passive"))
      (node (ref "C57") (pin "1") (pinfunction "1_1") (pintype "passive"))
      (node (ref "C58") (pin "2") (pinfunction "2_2") (pintype "passive"))
      (node (ref "C59") (pin "2") (pinfunction "2_2") (pintype "passive"))
      (node (ref "C6") (pin "1") (pinfunction "1_1") (pintype "passive"))
      (node (ref "C60") (pin "2") (pinfunction "2_2") (pintype "passive"))
      (node (ref "C61") (pin "2") (pinfunction "2_2") (pintype "passive"))
      (node (ref "C62") (pin "2") (pinfunction "2_2") (pintype "passive"))
      (node (ref "C63") (pin "2") (pinfunction "2_2") (pintype "passive"))
      (node (ref "C64") (pin "2") (pinfunction "2_2") (pintype "passive"))
      (node (ref "C65") (pin "2") (pinfunction "2_2") (pintype "passive"))
      (node (ref "C66") (pin "1") (pinfunction "1_1") (pintype "passive"))
      (node (ref "C67") (pin "1") (pinfunction "1_1") (pintype "passive"))
      (node (ref "C68") (pin "2") (pinfunction "2_2") (pintype "passive"))
      (node (ref "C69") (pin "2") (pinfunction "2_2") (pintype "passive"))
      (node (ref "C7") (pin "2") (pinfunction "2_2") (pintype "passive"))
      (node (ref "C70") (pin "2") (pinfunction "2_2") (pintype "passive"))
      (node (ref "C71") (pin "2") (pinfunction "2_2") (pintype "passive"))
      (node (ref "C72") (pin "2") (pinfunction "2_2") (pintype "passive"))
      (node (ref "C73") (pin "2") (pinfunction "2_2") (pintype "passive"))
      (node (ref "C74") (pin "2") (pinfunction "2_2") (pintype "passive"))
      (node (ref "C75") (pin "2") (pinfunction "2_2") (pintype "passive"))
      (node (ref "C76") (pin "1") (pinfunction "1_1") (pintype "passive"))
      (node (ref "C77") (pin "1") (pinfunction "1_1") (pintype "passive"))
      (node (ref "C78") (pin "2") (pinfunction "2_2") (pintype "passive"))
      (node (ref "C79") (pin "2") (pinfunction "2_2") (pintype "passive"))
      (node (ref "C8") (pin "2") (pinfunction "2_2") (pintype "passive"))
      (node (ref "C80") (pin "2") (pinfunction "2_2") (pintype "passive"))
      (node (ref "C81") (pin "2") (pinfunction "2_2") (pintype "passive"))
      (node (ref "C82") (pin "2") (pinfunction "2_2") (pintype "passive"))
      (node (ref "C83") (pin "2") (pinfunction "2_2") (pintype "passive"))
      (node (ref "C84") (pin "2") (pinfunction "2_2") (pintype "passive"))
      (node (ref "C85") (pin "2") (pinfunction "2_2") (pintype "passive"))
      (node (ref "C86") (pin "1") (pinfunction "1_1") (pintype "passive"))
      (node (ref "C87") (pin "1") (pinfunction "1_1") (pintype "passive"))
      (node (ref "C88") (pin "2") (pinfunction "2_2") (pintype "passive"))
      (node (ref "C89") (pin "2") (pinfunction "2_2") (pintype "passive"))
      (node (ref "C9") (pin "1") (pinfunction "1_1") (pintype "passive"))
      (node (ref "C90") (pin "2") (pinfunction "2_2") (pintype "passive"))
      (node (ref "C91") (pin "2") (pinfunction "2_2") (pintype "passive"))
      (node (ref "C92") (pin "2") (pinfunction "2_2") (pintype "passive"))
      (node (ref "C93") (pin "2") (pinfunction "2_2") (pintype "passive"))
      (node (ref "C94") (pin "2") (pinfunction "2_2") (pintype "passive"))
      (node (ref "C95") (pin "2") (pinfunction "2_2") (pintype "passive"))
      (node (ref "C96") (pin "1") (pinfunction "1_1") (pintype "passive"))
      (node (ref "C97") (pin "1") (pinfunction "1_1") (pintype "passive"))
      (node (ref "C98") (pin "2") (pinfunction "2_2") (pintype "passive"))
      (node (ref "C99") (pin "2") (pinfunction "2_2") (pintype "passive"))
      (node (ref "D1") (pin "A") (pinfunction "A_A") (pintype "passive"))
      (node (ref "D105") (pin "1") (pinfunction "+_1") (pintype "passive"))
      (node (ref "D107") (pin "A") (pinfunction "A_A") (pintype "passive"))
      (node (ref "D108") (pin "A") (pinfunction "A_A") (pintype "passive"))
      (node (ref "D117") (pin "1") (pinfunction "+_1") (pintype "passive"))
      (node (ref "D119") (pin "A") (pinfunction "A_A") (pintype "passive"))
      (node (ref "D120") (pin "A") (pinfunction "A_A") (pintype "passive"))
      (node (ref "D129") (pin "1") (pinfunction "+_1") (pintype "passive"))
      (node (ref "D131") (pin "A") (pinfunction "A_A") (pintype "passive"))
      (node (ref "D132") (pin "A") (pinfunction "A_A") (pintype "passive"))
      (node (ref "D141") (pin "1") (pinfunction "+_1") (pintype "passive"))
      (node (ref "D143") (pin "A") (pinfunction "A_A") (pintype "passive"))
      (node (ref "D144") (pin "A") (pinfunction "A_A") (pintype "passive"))
      (node (ref "D21") (pin "1") (pinfunction "+_1") (pintype "passive"))
      (node (ref "D23") (pin "A") (pinfunction "A_A") (pintype "passive"))
      (node (ref "D24") (pin "A") (pinfunction "A_A") (pintype "passive"))
      (node (ref "D33") (pin "1") (pinfunction "+_1") (pintype "passive"))
      (node (ref "D35") (pin "A") (pinfunction "A_A") (pintype "passive"))
      (node (ref "D36") (pin "A") (pinfunction "A_A") (pintype "passive"))
      (node (ref "D4") (pin "A") (pinfunction "A_A") (pintype "passive"))
      (node (ref "D45") (pin "1") (pinfunction "+_1") (pintype "passive"))
      (node (ref "D47") (pin "A") (pinfunction "A_A") (pintype "passive"))
      (node (ref "D48") (pin "A") (pinfunction "A_A") (pintype "passive"))
      (node (ref "D5") (pin "1") (pinfunction "+_1") (pintype "passive"))
      (node (ref "D57") (pin "1") (pinfunction "+_1") (pintype "passive"))
      (node (ref "D59") (pin "A") (pinfunction "A_A") (pintype "passive"))
      (node (ref "D60") (pin "A") (pinfunction "A_A") (pintype "passive"))
      (node (ref "D69") (pin "1") (pinfunction "+_1") (pintype "passive"))
      (node (ref "D71") (pin "A") (pinfunction "A_A") (pintype "passive"))
      (node (ref "D72") (pin "A") (pinfunction "A_A") (pintype "passive"))
      (node (ref "D81") (pin "1") (pinfunction "+_1") (pintype "passive"))
      (node (ref "D83") (pin "A") (pinfunction "A_A") (pintype "passive"))
      (node (ref "D84") (pin "A") (pinfunction "A_A") (pintype "passive"))
      (node (ref "D93") (pin "1") (pinfunction "+_1") (pintype "passive"))
      (node (ref "D95") (pin "A") (pinfunction "A_A") (pintype "passive"))
      (node (ref "D96") (pin "A") (pinfunction "A_A") (pintype "passive"))
      (node (ref "IC1") (pin "4") (pinfunction "V-_4") (pintype "power_in"))
      (node (ref "IC10") (pin "1") (pinfunction "GND_1") (pintype "power_in"))
      (node (ref "IC100") (pin "11") (pinfunction "D_11") (pintype "input"))
      (node (ref "IC100") (pin "8") (pinfunction "VSS_8") (pintype "power_in"))
      (node (ref "IC101") (pin "GND") (pinfunction "GND_GND") (pintype "input"))
      (node (ref "IC103") (pin "8") (pinfunction "GND_8") (pintype "power_in"))
      (node (ref "IC104") (pin "10") (pinfunction "-IN_10") (pintype "input"))
      (node (ref "IC104") (pin "11") (pinfunction "+IN_11") (pintype "input"))
      (node (ref "IC104") (pin "12") (pinfunction "GND_12") (pintype "power_in"))
      (node (ref "IC105") (pin "2") (pinfunction "GND_2") (pintype "input"))
      (node (ref "IC105") (pin "2@1") (pinfunction "GND_2@1") (pintype "input"))
      (node (ref "IC106") (pin "1") (pinfunction "GND_1") (pintype "power_in"))
      (node (ref "IC107") (pin "1") (pinfunction "T1_1") (pintype "input"))
      (node (ref "IC107") (pin "15") (pinfunction "T1_15") (pintype "input"))
      (node (ref "IC107") (pin "4") (pinfunction "A_4") (pintype "input"))
      (node (ref "IC107") (pin "8") (pinfunction "VSS_8") (pintype "power_in"))
      (node (ref "IC108") (pin "2") (pinfunction "GND_2") (pintype "input"))
      (node (ref "IC108") (pin "2@1") (pinfunction "GND_2@1") (pintype "input"))
      (node (ref "IC109") (pin "4") (pinfunction "V-_4") (pintype "power_in"))
      (node (ref "IC11") (pin "1") (pinfunction "T1_1") (pintype "input"))
      (node (ref "IC11") (pin "15") (pinfunction "T1_15") (pintype "input"))
      (node (ref "IC11") (pin "4") (pinfunction "A_4") (pintype "input"))
      (node (ref "IC11") (pin "8") (pinfunction "VSS_8") (pintype "power_in"))
      (node (ref "IC111") (pin "11") (pinfunction "D_11") (pintype "input"))
      (node (ref "IC111") (pin "8") (pinfunction "VSS_8") (pintype "power_in"))
      (node (ref "IC112") (pin "GND") (pinfunction "GND_GND") (pintype "input"))
      (node (ref "IC114") (pin "8") (pinfunction "GND_8") (pintype "power_in"))
      (node (ref "IC115") (pin "10") (pinfunction "-IN_10") (pintype "input"))
      (node (ref "IC115") (pin "11") (pinfunction "+IN_11") (pintype "input"))
      (node (ref "IC115") (pin "12") (pinfunction "GND_12") (pintype "power_in"))
      (node (ref "IC116") (pin "2") (pinfunction "GND_2") (pintype "input"))
      (node (ref "IC116") (pin "2@1") (pinfunction "GND_2@1") (pintype "input"))
      (node (ref "IC117") (pin "1") (pinfunction "GND_1") (pintype "power_in"))
      (node (ref "IC118") (pin "1") (pinfunction "T1_1") (pintype "input"))
      (node (ref "IC118") (pin "15") (pinfunction "T1_15") (pintype "input"))
      (node (ref "IC118") (pin "4") (pinfunction "A_4") (pintype "input"))
      (node (ref "IC118") (pin "8") (pinfunction "VSS_8") (pintype "power_in"))
      (node (ref "IC119") (pin "2") (pinfunction "GND_2") (pintype "input"))
      (node (ref "IC119") (pin "2@1") (pinfunction "GND_2@1") (pintype "input"))
      (node (ref "IC12") (pin "11") (pinfunction "D_11") (pintype "input"))
      (node (ref "IC12") (pin "8") (pinfunction "VSS_8") (pintype "power_in"))
      (node (ref "IC120") (pin "4") (pinfunction "V-_4") (pintype "power_in"))
      (node (ref "IC122") (pin "11") (pinfunction "D_11") (pintype "input"))
      (node (ref "IC122") (pin "8") (pinfunction "VSS_8") (pintype "power_in"))
      (node (ref "IC123") (pin "GND") (pinfunction "GND_GND") (pintype "input"))
      (node (ref "IC125") (pin "8") (pinfunction "GND_8") (pintype "power_in"))
      (node (ref "IC126") (pin "10") (pinfunction "-IN_10") (pintype "input"))
      (node (ref "IC126") (pin "11") (pinfunction "+IN_11") (pintype "input"))
      (node (ref "IC126") (pin "12") (pinfunction "GND_12") (pintype "power_in"))
      (node (ref "IC127") (pin "2") (pinfunction "GND_2") (pintype "input"))
      (node (ref "IC127") (pin "2@1") (pinfunction "GND_2@1") (pintype "input"))
      (node (ref "IC128") (pin "1") (pinfunction "GND_1") (pintype "power_in"))
      (node (ref "IC129") (pin "1") (pinfunction "T1_1") (pintype "input"))
      (node (ref "IC129") (pin "15") (pinfunction "T1_15") (pintype "input"))
      (node (ref "IC129") (pin "4") (pinfunction "A_4") (pintype "input"))
      (node (ref "IC129") (pin "8") (pinfunction "VSS_8") (pintype "power_in"))
      (node (ref "IC13") (pin "GND") (pinfunction "GND_GND") (pintype "input"))
      (node (ref "IC130") (pin "2") (pinfunction "GND_2") (pintype "input"))
      (node (ref "IC130") (pin "2@1") (pinfunction "GND_2@1") (pintype "input"))
      (node (ref "IC131") (pin "4") (pinfunction "V-_4") (pintype "power_in"))
      (node (ref "IC15") (pin "8") (pinfunction "GND_8") (pintype "power_in"))
      (node (ref "IC16") (pin "10") (pinfunction "-IN_10") (pintype "input"))
      (node (ref "IC16") (pin "11") (pinfunction "+IN_11") (pintype "input"))
      (node (ref "IC16") (pin "12") (pinfunction "GND_12") (pintype "power_in"))
      (node (ref "IC17") (pin "2") (pinfunction "GND_2") (pintype "input"))
      (node (ref "IC17") (pin "2@1") (pinfunction "GND_2@1") (pintype "input"))
      (node (ref "IC18") (pin "1") (pinfunction "GND_1") (pintype "power_in"))
      (node (ref "IC19") (pin "1") (pinfunction "T1_1") (pintype "input"))
      (node (ref "IC19") (pin "15") (pinfunction "T1_15") (pintype "input"))
      (node (ref "IC19") (pin "4") (pinfunction "A_4") (pintype "input"))
      (node (ref "IC19") (pin "8") (pinfunction "VSS_8") (pintype "power_in"))
      (node (ref "IC2") (pin "2") (pinfunction "GND_2") (pintype "input"))
      (node (ref "IC2") (pin "2@1") (pinfunction "GND_2@1") (pintype "input"))
      (node (ref "IC20") (pin "2") (pinfunction "GND_2") (pintype "input"))
      (node (ref "IC20") (pin "2@1") (pinfunction "GND_2@1") (pintype "input"))
      (node (ref "IC21") (pin "4") (pinfunction "V-_4") (pintype "power_in"))
      (node (ref "IC23") (pin "11") (pinfunction "D_11") (pintype "input"))
      (node (ref "IC23") (pin "8") (pinfunction "VSS_8") (pintype "power_in"))
      (node (ref "IC24") (pin "GND") (pinfunction "GND_GND") (pintype "input"))
      (node (ref "IC26") (pin "8") (pinfunction "GND_8") (pintype "power_in"))
      (node (ref "IC27") (pin "10") (pinfunction "-IN_10") (pintype "input"))
      (node (ref "IC27") (pin "11") (pinfunction "+IN_11") (pintype "input"))
      (node (ref "IC27") (pin "12") (pinfunction "GND_12") (pintype "power_in"))
      (node (ref "IC28") (pin "2") (pinfunction "GND_2") (pintype "input"))
      (node (ref "IC28") (pin "2@1") (pinfunction "GND_2@1") (pintype "input"))
      (node (ref "IC29") (pin "1") (pinfunction "GND_1") (pintype "power_in"))
      (node (ref "IC3") (pin "GND") (pinfunction "GND_GND") (pintype "input"))
      (node (ref "IC30") (pin "1") (pinfunction "T1_1") (pintype "input"))
      (node (ref "IC30") (pin "15") (pinfunction "T1_15") (pintype "input"))
      (node (ref "IC30") (pin "4") (pinfunction "A_4") (pintype "input"))
      (node (ref "IC30") (pin "8") (pinfunction "VSS_8") (pintype "power_in"))
      (node (ref "IC31") (pin "2") (pinfunction "GND_2") (pintype "input"))
      (node (ref "IC31") (pin "2@1") (pinfunction "GND_2@1") (pintype "input"))
      (node (ref "IC32") (pin "4") (pinfunction "V-_4") (pintype "power_in"))
      (node (ref "IC34") (pin "11") (pinfunction "D_11") (pintype "input"))
      (node (ref "IC34") (pin "8") (pinfunction "VSS_8") (pintype "power_in"))
      (node (ref "IC35") (pin "GND") (pinfunction "GND_GND") (pintype "input"))
      (node (ref "IC37") (pin "8") (pinfunction "GND_8") (pintype "power_in"))
      (node (ref "IC38") (pin "10") (pinfunction "-IN_10") (pintype "input"))
      (node (ref "IC38") (pin "11") (pinfunction "+IN_11") (pintype "input"))
      (node (ref "IC38") (pin "12") (pinfunction "GND_12") (pintype "power_in"))
      (node (ref "IC39") (pin "2") (pinfunction "GND_2") (pintype "input"))
      (node (ref "IC39") (pin "2@1") (pinfunction "GND_2@1") (pintype "input"))
      (node (ref "IC4") (pin "2") (pinfunction "GND_2") (pintype "input"))
      (node (ref "IC4") (pin "2@1") (pinfunction "GND_2@1") (pintype "input"))
      (node (ref "IC40") (pin "1") (pinfunction "GND_1") (pintype "power_in"))
      (node (ref "IC41") (pin "1") (pinfunction "T1_1") (pintype "input"))
      (node (ref "IC41") (pin "15") (pinfunction "T1_15") (pintype "input"))
      (node (ref "IC41") (pin "4") (pinfunction "A_4") (pintype "input"))
      (node (ref "IC41") (pin "8") (pinfunction "VSS_8") (pintype "power_in"))
      (node (ref "IC42") (pin "2") (pinfunction "GND_2") (pintype "input"))
      (node (ref "IC42") (pin "2@1") (pinfunction "GND_2@1") (pintype "input"))
      (node (ref "IC43") (pin "4") (pinfunction "V-_4") (pintype "power_in"))
      (node (ref "IC45") (pin "11") (pinfunction "D_11") (pintype "input"))
      (node (ref "IC45") (pin "8") (pinfunction "VSS_8") (pintype "power_in"))
      (node (ref "IC46") (pin "GND") (pinfunction "GND_GND") (pintype "input"))
      (node (ref "IC48") (pin "8") (pinfunction "GND_8") (pintype "power_in"))
      (node (ref "IC49") (pin "10") (pinfunction "-IN_10") (pintype "input"))
      (node (ref "IC49") (pin "11") (pinfunction "+IN_11") (pintype "input"))
      (node (ref "IC49") (pin "12") (pinfunction "GND_12") (pintype "power_in"))
      (node (ref "IC5") (pin "11") (pinfunction "D_11") (pintype "input"))
      (node (ref "IC5") (pin "8") (pinfunction "VSS_8") (pintype "power_in"))
      (node (ref "IC50") (pin "2") (pinfunction "GND_2") (pintype "input"))
      (node (ref "IC50") (pin "2@1") (pinfunction "GND_2@1") (pintype "input"))
      (node (ref "IC51") (pin "1") (pinfunction "GND_1") (pintype "power_in"))
      (node (ref "IC52") (pin "1") (pinfunction "T1_1") (pintype "input"))
      (node (ref "IC52") (pin "15") (pinfunction "T1_15") (pintype "input"))
      (node (ref "IC52") (pin "4") (pinfunction "A_4") (pintype "input"))
      (node (ref "IC52") (pin "8") (pinfunction "VSS_8") (pintype "power_in"))
      (node (ref "IC53") (pin "2") (pinfunction "GND_2") (pintype "input"))
      (node (ref "IC53") (pin "2@1") (pinfunction "GND_2@1") (pintype "input"))
      (node (ref "IC54") (pin "4") (pinfunction "V-_4") (pintype "power_in"))
      (node (ref "IC56") (pin "11") (pinfunction "D_11") (pintype "input"))
      (node (ref "IC56") (pin "8") (pinfunction "VSS_8") (pintype "power_in"))
      (node (ref "IC57") (pin "GND") (pinfunction "GND_GND") (pintype "input"))
      (node (ref "IC59") (pin "8") (pinfunction "GND_8") (pintype "power_in"))
      (node (ref "IC60") (pin "10") (pinfunction "-IN_10") (pintype "input"))
      (node (ref "IC60") (pin "11") (pinfunction "+IN_11") (pintype "input"))
      (node (ref "IC60") (pin "12") (pinfunction "GND_12") (pintype "power_in"))
      (node (ref "IC61") (pin "2") (pinfunction "GND_2") (pintype "input"))
      (node (ref "IC61") (pin "2@1") (pinfunction "GND_2@1") (pintype "input"))
      (node (ref "IC62") (pin "1") (pinfunction "GND_1") (pintype "power_in"))
      (node (ref "IC63") (pin "1") (pinfunction "T1_1") (pintype "input"))
      (node (ref "IC63") (pin "15") (pinfunction "T1_15") (pintype "input"))
      (node (ref "IC63") (pin "4") (pinfunction "A_4") (pintype "input"))
      (node (ref "IC63") (pin "8") (pinfunction "VSS_8") (pintype "power_in"))
      (node (ref "IC64") (pin "2") (pinfunction "GND_2") (pintype "input"))
      (node (ref "IC64") (pin "2@1") (pinfunction "GND_2@1") (pintype "input"))
      (node (ref "IC65") (pin "4") (pinfunction "V-_4") (pintype "power_in"))
      (node (ref "IC67") (pin "11") (pinfunction "D_11") (pintype "input"))
      (node (ref "IC67") (pin "8") (pinfunction "VSS_8") (pintype "power_in"))
      (node (ref "IC68") (pin "GND") (pinfunction "GND_GND") (pintype "input"))
      (node (ref "IC7") (pin "8") (pinfunction "GND_8") (pintype "power_in"))
      (node (ref "IC70") (pin "8") (pinfunction "GND_8") (pintype "power_in"))
      (node (ref "IC71") (pin "10") (pinfunction "-IN_10") (pintype "input"))
      (node (ref "IC71") (pin "11") (pinfunction "+IN_11") (pintype "input"))
      (node (ref "IC71") (pin "12") (pinfunction "GND_12") (pintype "power_in"))
      (node (ref "IC72") (pin "2") (pinfunction "GND_2") (pintype "input"))
      (node (ref "IC72") (pin "2@1") (pinfunction "GND_2@1") (pintype "input"))
      (node (ref "IC73") (pin "1") (pinfunction "GND_1") (pintype "power_in"))
      (node (ref "IC74") (pin "1") (pinfunction "T1_1") (pintype "input"))
      (node (ref "IC74") (pin "15") (pinfunction "T1_15") (pintype "input"))
      (node (ref "IC74") (pin "4") (pinfunction "A_4") (pintype "input"))
      (node (ref "IC74") (pin "8") (pinfunction "VSS_8") (pintype "power_in"))
      (node (ref "IC75") (pin "2") (pinfunction "GND_2") (pintype "input"))
      (node (ref "IC75") (pin "2@1") (pinfunction "GND_2@1") (pintype "input"))
      (node (ref "IC76") (pin "4") (pinfunction "V-_4") (pintype "power_in"))
      (node (ref "IC78") (pin "11") (pinfunction "D_11") (pintype "input"))
      (node (ref "IC78") (pin "8") (pinfunction "VSS_8") (pintype "power_in"))
      (node (ref "IC79") (pin "GND") (pinfunction "GND_GND") (pintype "input"))
      (node (ref "IC8") (pin "10") (pinfunction "-IN_10") (pintype "input"))
      (node (ref "IC8") (pin "11") (pinfunction "+IN_11") (pintype "input"))
      (node (ref "IC8") (pin "12") (pinfunction "GND_12") (pintype "power_in"))
      (node (ref "IC81") (pin "8") (pinfunction "GND_8") (pintype "power_in"))
      (node (ref "IC82") (pin "10") (pinfunction "-IN_10") (pintype "input"))
      (node (ref "IC82") (pin "11") (pinfunction "+IN_11") (pintype "input"))
      (node (ref "IC82") (pin "12") (pinfunction "GND_12") (pintype "power_in"))
      (node (ref "IC83") (pin "2") (pinfunction "GND_2") (pintype "input"))
      (node (ref "IC83") (pin "2@1") (pinfunction "GND_2@1") (pintype "input"))
      (node (ref "IC84") (pin "1") (pinfunction "GND_1") (pintype "power_in"))
      (node (ref "IC85") (pin "1") (pinfunction "T1_1") (pintype "input"))
      (node (ref "IC85") (pin "15") (pinfunction "T1_15") (pintype "input"))
      (node (ref "IC85") (pin "4") (pinfunction "A_4") (pintype "input"))
      (node (ref "IC85") (pin "8") (pinfunction "VSS_8") (pintype "power_in"))
      (node (ref "IC86") (pin "2") (pinfunction "GND_2") (pintype "input"))
      (node (ref "IC86") (pin "2@1") (pinfunction "GND_2@1") (pintype "input"))
      (node (ref "IC87") (pin "4") (pinfunction "V-_4") (pintype "power_in"))
      (node (ref "IC89") (pin "11") (pinfunction "D_11") (pintype "input"))
      (node (ref "IC89") (pin "8") (pinfunction "VSS_8") (pintype "power_in"))
      (node (ref "IC90") (pin "GND") (pinfunction "GND_GND") (pintype "input"))
      (node (ref "IC92") (pin "8") (pinfunction "GND_8") (pintype "power_in"))
      (node (ref "IC93") (pin "10") (pinfunction "-IN_10") (pintype "input"))
      (node (ref "IC93") (pin "11") (pinfunction "+IN_11") (pintype "input"))
      (node (ref "IC93") (pin "12") (pinfunction "GND_12") (pintype "power_in"))
      (node (ref "IC94") (pin "2") (pinfunction "GND_2") (pintype "input"))
      (node (ref "IC94") (pin "2@1") (pinfunction "GND_2@1") (pintype "input"))
      (node (ref "IC95") (pin "1") (pinfunction "GND_1") (pintype "power_in"))
      (node (ref "IC96") (pin "1") (pinfunction "T1_1") (pintype "input"))
      (node (ref "IC96") (pin "15") (pinfunction "T1_15") (pintype "input"))
      (node (ref "IC96") (pin "4") (pinfunction "A_4") (pintype "input"))
      (node (ref "IC96") (pin "8") (pinfunction "VSS_8") (pintype "power_in"))
      (node (ref "IC97") (pin "2") (pinfunction "GND_2") (pintype "input"))
      (node (ref "IC97") (pin "2@1") (pinfunction "GND_2@1") (pintype "input"))
      (node (ref "IC98") (pin "4") (pinfunction "V-_4") (pintype "power_in"))
      (node (ref "Q12") (pin "3") (pinfunction "E_3") (pintype "passive"))
      (node (ref "Q13") (pin "2") (pinfunction "S_2") (pintype "passive"))
      (node (ref "Q14") (pin "2") (pinfunction "S_2") (pintype "passive"))
      (node (ref "Q19") (pin "3") (pinfunction "E_3") (pintype "passive"))
      (node (ref "Q20") (pin "2") (pinfunction "S_2") (pintype "passive"))
      (node (ref "Q21") (pin "2") (pinfunction "S_2") (pintype "passive"))
      (node (ref "Q26") (pin "3") (pinfunction "E_3") (pintype "passive"))
      (node (ref "Q27") (pin "2") (pinfunction "S_2") (pintype "passive"))
      (node (ref "Q28") (pin "2") (pinfunction "S_2") (pintype "passive"))
      (node (ref "Q3") (pin "3") (pinfunction "E_3") (pintype "passive"))
      (node (ref "Q33") (pin "3") (pinfunction "E_3") (pintype "passive"))
      (node (ref "Q34") (pin "2") (pinfunction "S_2") (pintype "passive"))
      (node (ref "Q35") (pin "2") (pinfunction "S_2") (pintype "passive"))
      (node (ref "Q40") (pin "3") (pinfunction "E_3") (pintype "passive"))
      (node (ref "Q41") (pin "2") (pinfunction "S_2") (pintype "passive"))
      (node (ref "Q42") (pin "2") (pinfunction "S_2") (pintype "passive"))
      (node (ref "Q47") (pin "3") (pinfunction "E_3") (pintype "passive"))
      (node (ref "Q48") (pin "2") (pinfunction "S_2") (pintype "passive"))
      (node (ref "Q49") (pin "2") (pinfunction "S_2") (pintype "passive"))
      (node (ref "Q54") (pin "3") (pinfunction "E_3") (pintype "passive"))
      (node (ref "Q55") (pin "2") (pinfunction "S_2") (pintype "passive"))
      (node (ref "Q56") (pin "2") (pinfunction "S_2") (pintype "passive"))
      (node (ref "Q6") (pin "2") (pinfunction "S_2") (pintype "passive"))
      (node (ref "Q61") (pin "3") (pinfunction "E_3") (pintype "passive"))
      (node (ref "Q62") (pin "2") (pinfunction "S_2") (pintype "passive"))
      (node (ref "Q63") (pin "2") (pinfunction "S_2") (pintype "passive"))
      (node (ref "Q68") (pin "3") (pinfunction "E_3") (pintype "passive"))
      (node (ref "Q69") (pin "2") (pinfunction "S_2") (pintype "passive"))
      (node (ref "Q7") (pin "2") (pinfunction "S_2") (pintype "passive"))
      (node (ref "Q70") (pin "2") (pinfunction "S_2") (pintype "passive"))
      (node (ref "Q75") (pin "3") (pinfunction "E_3") (pintype "passive"))
      (node (ref "Q76") (pin "2") (pinfunction "S_2") (pintype "passive"))
      (node (ref "Q77") (pin "2") (pinfunction "S_2") (pintype "passive"))
      (node (ref "Q82") (pin "3") (pinfunction "E_3") (pintype "passive"))
      (node (ref "Q83") (pin "2") (pinfunction "S_2") (pintype "passive"))
      (node (ref "Q84") (pin "2") (pinfunction "S_2") (pintype "passive"))
      (node (ref "R1") (pin "2") (pinfunction "2_2") (pintype "passive"))
      (node (ref "R100") (pin "1") (pinfunction "1_1") (pintype "passive"))
      (node (ref "R106") (pin "1") (pinfunction "1_1") (pintype "passive"))
      (node (ref "R110") (pin "1") (pinfunction "1_1") (pintype "passive"))
      (node (ref "R111") (pin "2") (pinfunction "2_2") (pintype "passive"))
      (node (ref "R112") (pin "2") (pinfunction "2_2") (pintype "passive"))
      (node (ref "R114") (pin "2") (pinfunction "2_2") (pintype "passive"))
      (node (ref "R122") (pin "2") (pinfunction "2_2") (pintype "passive"))
      (node (ref "R124") (pin "2") (pinfunction "2_2") (pintype "passive"))
      (node (ref "R127") (pin "1") (pinfunction "1_1") (pintype "passive"))
      (node (ref "R128") (pin "1") (pinfunction "1_1") (pintype "passive"))
      (node (ref "R136") (pin "1") (pinfunction "1_1") (pintype "passive"))
      (node (ref "R138") (pin "2") (pinfunction "2_2") (pintype "passive"))
      (node (ref "R14") (pin "1") (pinfunction "1_1") (pintype "passive"))
      (node (ref "R146") (pin "1") (pinfunction "1_1") (pintype "passive"))
      (node (ref "R152") (pin "1") (pinfunction "1_1") (pintype "passive"))
      (node (ref "R156") (pin "1") (pinfunction "1_1") (pintype "passive"))
      (node (ref "R157") (pin "2") (pinfunction "2_2") (pintype "passive"))
      (node (ref "R158") (pin "2") (pinfunction "2_2") (pintype "passive"))
      (node (ref "R160") (pin "2") (pinfunction "2_2") (pintype "passive"))
      (node (ref "R168") (pin "2") (pinfunction "2_2") (pintype "passive"))
      (node (ref "R170") (pin "2") (pinfunction "2_2") (pintype "passive"))
      (node (ref "R173") (pin "1") (pinfunction "1_1") (pintype "passive"))
      (node (ref "R174") (pin "1") (pinfunction "1_1") (pintype "passive"))
      (node (ref "R182") (pin "1") (pinfunction "1_1") (pintype "passive"))
      (node (ref "R184") (pin "2") (pinfunction "2_2") (pintype "passive"))
      (node (ref "R192") (pin "1") (pinfunction "1_1") (pintype "passive"))
      (node (ref "R198") (pin "1") (pinfunction "1_1") (pintype "passive"))
      (node (ref "R202") (pin "1") (pinfunction "1_1") (pintype "passive"))
      (node (ref "R203") (pin "2") (pinfunction "2_2") (pintype "passive"))
      (node (ref "R204") (pin "2") (pinfunction "2_2") (pintype "passive"))
      (node (ref "R206") (pin "2") (pinfunction "2_2") (pintype "passive"))
      (node (ref "R214") (pin "2") (pinfunction "2_2") (pintype "passive"))
      (node (ref "R216") (pin "2") (pinfunction "2_2") (pintype "passive"))
      (node (ref "R219") (pin "1") (pinfunction "1_1") (pintype "passive"))
      (node (ref "R220") (pin "1") (pinfunction "1_1") (pintype "passive"))
      (node (ref "R228") (pin "1") (pinfunction "1_1") (pintype "passive"))
      (node (ref "R23") (pin "1") (pinfunction "1_1") (pintype "passive"))
      (node (ref "R230") (pin "2") (pinfunction "2_2") (pintype "passive"))
      (node (ref "R238") (pin "1") (pinfunction "1_1") (pintype "passive"))
      (node (ref "R244") (pin "1") (pinfunction "1_1") (pintype "passive"))
      (node (ref "R248") (pin "1") (pinfunction "1_1") (pintype "passive"))
      (node (ref "R249") (pin "2") (pinfunction "2_2") (pintype "passive"))
      (node (ref "R250") (pin "2") (pinfunction "2_2") (pintype "passive"))
      (node (ref "R252") (pin "2") (pinfunction "2_2") (pintype "passive"))
      (node (ref "R260") (pin "2") (pinfunction "2_2") (pintype "passive"))
      (node (ref "R262") (pin "2") (pinfunction "2_2") (pintype "passive"))
      (node (ref "R265") (pin "1") (pinfunction "1_1") (pintype "passive"))
      (node (ref "R266") (pin "1") (pinfunction "1_1") (pintype "passive"))
      (node (ref "R274") (pin "1") (pinfunction "1_1") (pintype "passive"))
      (node (ref "R276") (pin "2") (pinfunction "2_2") (pintype "passive"))
      (node (ref "R284") (pin "1") (pinfunction "1_1") (pintype "passive"))
      (node (ref "R290") (pin "1") (pinfunction "1_1") (pintype "passive"))
      (node (ref "R294") (pin "1") (pinfunction "1_1") (pintype "passive"))
      (node (ref "R295") (pin "2") (pinfunction "2_2") (pintype "passive"))
      (node (ref "R296") (pin "2") (pinfunction "2_2") (pintype "passive"))
      (node (ref "R298") (pin "2") (pinfunction "2_2") (pintype "passive"))
      (node (ref "R3") (pin "2") (pinfunction "2_2") (pintype "passive"))
      (node (ref "R306") (pin "2") (pinfunction "2_2") (pintype "passive"))
      (node (ref "R308") (pin "2") (pinfunction "2_2") (pintype "passive"))
      (node (ref "R311") (pin "1") (pinfunction "1_1") (pintype "passive"))
      (node (ref "R312") (pin "1") (pinfunction "1_1") (pintype "passive"))
      (node (ref "R32") (pin "1") (pinfunction "1_1") (pintype "passive"))
      (node (ref "R320") (pin "1") (pinfunction "1_1") (pintype "passive"))
      (node (ref "R322") (pin "2") (pinfunction "2_2") (pintype "passive"))
      (node (ref "R330") (pin "1") (pinfunction "1_1") (pintype "passive"))
      (node (ref "R336") (pin "1") (pinfunction "1_1") (pintype "passive"))
      (node (ref "R340") (pin "1") (pinfunction "1_1") (pintype "passive"))
      (node (ref "R341") (pin "2") (pinfunction "2_2") (pintype "passive"))
      (node (ref "R342") (pin "2") (pinfunction "2_2") (pintype "passive"))
      (node (ref "R344") (pin "2") (pinfunction "2_2") (pintype "passive"))
      (node (ref "R352") (pin "2") (pinfunction "2_2") (pintype "passive"))
      (node (ref "R354") (pin "2") (pinfunction "2_2") (pintype "passive"))
      (node (ref "R357") (pin "1") (pinfunction "1_1") (pintype "passive"))
      (node (ref "R358") (pin "1") (pinfunction "1_1") (pintype "passive"))
      (node (ref "R36") (pin "1") (pinfunction "1_1") (pintype "passive"))
      (node (ref "R366") (pin "1") (pinfunction "1_1") (pintype "passive"))
      (node (ref "R368") (pin "2") (pinfunction "2_2") (pintype "passive"))
      (node (ref "R37") (pin "1") (pinfunction "1_1") (pintype "passive"))
      (node (ref "R376") (pin "1") (pinfunction "1_1") (pintype "passive"))
      (node (ref "R382") (pin "1") (pinfunction "1_1") (pintype "passive"))
      (node (ref "R386") (pin "1") (pinfunction "1_1") (pintype "passive"))
      (node (ref "R387") (pin "2") (pinfunction "2_2") (pintype "passive"))
      (node (ref "R388") (pin "2") (pinfunction "2_2") (pintype "passive"))
      (node (ref "R39") (pin "2") (pinfunction "2_2") (pintype "passive"))
      (node (ref "R390") (pin "2") (pinfunction "2_2") (pintype "passive"))
      (node (ref "R398") (pin "2") (pinfunction "2_2") (pintype "passive"))
      (node (ref "R4") (pin "2") (pinfunction "2_2") (pintype "passive"))
      (node (ref "R400") (pin "2") (pinfunction "2_2") (pintype "passive"))
      (node (ref "R403") (pin "1") (pinfunction "1_1") (pintype "passive"))
      (node (ref "R404") (pin "1") (pinfunction "1_1") (pintype "passive"))
      (node (ref "R41") (pin "2") (pinfunction "2_2") (pintype "passive"))
      (node (ref "R412") (pin "1") (pinfunction "1_1") (pintype "passive"))
      (node (ref "R414") (pin "2") (pinfunction "2_2") (pintype "passive"))
      (node (ref "R422") (pin "1") (pinfunction "1_1") (pintype "passive"))
      (node (ref "R428") (pin "1") (pinfunction "1_1") (pintype "passive"))
      (node (ref "R43") (pin "2") (pinfunction "2_2") (pintype "passive"))
      (node (ref "R432") (pin "1") (pinfunction "1_1") (pintype "passive"))
      (node (ref "R433") (pin "2") (pinfunction "2_2") (pintype "passive"))
      (node (ref "R434") (pin "2") (pinfunction "2_2") (pintype "passive"))
      (node (ref "R436") (pin "2") (pinfunction "2_2") (pintype "passive"))
      (node (ref "R444") (pin "2") (pinfunction "2_2") (pintype "passive"))
      (node (ref "R446") (pin "2") (pinfunction "2_2") (pintype "passive"))
      (node (ref "R449") (pin "1") (pinfunction "1_1") (pintype "passive"))
      (node (ref "R450") (pin "1") (pinfunction "1_1") (pintype "passive"))
      (node (ref "R458") (pin "1") (pinfunction "1_1") (pintype "passive"))
      (node (ref "R460") (pin "2") (pinfunction "2_2") (pintype "passive"))
      (node (ref "R468") (pin "1") (pinfunction "1_1") (pintype "passive"))
      (node (ref "R474") (pin "1") (pinfunction "1_1") (pintype "passive"))
      (node (ref "R478") (pin "1") (pinfunction "1_1") (pintype "passive"))
      (node (ref "R479") (pin "2") (pinfunction "2_2") (pintype "passive"))
      (node (ref "R480") (pin "2") (pinfunction "2_2") (pintype "passive"))
      (node (ref "R482") (pin "2") (pinfunction "2_2") (pintype "passive"))
      (node (ref "R490") (pin "2") (pinfunction "2_2") (pintype "passive"))
      (node (ref "R492") (pin "2") (pinfunction "2_2") (pintype "passive"))
      (node (ref "R495") (pin "1") (pinfunction "1_1") (pintype "passive"))
      (node (ref "R496") (pin "1") (pinfunction "1_1") (pintype "passive"))
      (node (ref "R504") (pin "1") (pinfunction "1_1") (pintype "passive"))
      (node (ref "R506") (pin "2") (pinfunction "2_2") (pintype "passive"))
      (node (ref "R514") (pin "1") (pinfunction "1_1") (pintype "passive"))
      (node (ref "R520") (pin "1") (pinfunction "1_1") (pintype "passive"))
      (node (ref "R524") (pin "1") (pinfunction "1_1") (pintype "passive"))
      (node (ref "R525") (pin "2") (pinfunction "2_2") (pintype "passive"))
      (node (ref "R526") (pin "2") (pinfunction "2_2") (pintype "passive"))
      (node (ref "R528") (pin "2") (pinfunction "2_2") (pintype "passive"))
      (node (ref "R536") (pin "2") (pinfunction "2_2") (pintype "passive"))
      (node (ref "R538") (pin "2") (pinfunction "2_2") (pintype "passive"))
      (node (ref "R54") (pin "1") (pinfunction "1_1") (pintype "passive"))
      (node (ref "R541") (pin "1") (pinfunction "1_1") (pintype "passive"))
      (node (ref "R542") (pin "1") (pinfunction "1_1") (pintype "passive"))
      (node (ref "R550") (pin "1") (pinfunction "1_1") (pintype "passive"))
      (node (ref "R552") (pin "2") (pinfunction "2_2") (pintype "passive"))
      (node (ref "R60") (pin "1") (pinfunction "1_1") (pintype "passive"))
      (node (ref "R64") (pin "1") (pinfunction "1_1") (pintype "passive"))
      (node (ref "R65") (pin "2") (pinfunction "2_2") (pintype "passive"))
      (node (ref "R66") (pin "2") (pinfunction "2_2") (pintype "passive"))
      (node (ref "R68") (pin "2") (pinfunction "2_2") (pintype "passive"))
      (node (ref "R7") (pin "1") (pinfunction "1_1") (pintype "passive"))
      (node (ref "R76") (pin "2") (pinfunction "2_2") (pintype "passive"))
      (node (ref "R78") (pin "2") (pinfunction "2_2") (pintype "passive"))
      (node (ref "R81") (pin "1") (pinfunction "1_1") (pintype "passive"))
      (node (ref "R82") (pin "1") (pinfunction "1_1") (pintype "passive"))
      (node (ref "R90") (pin "1") (pinfunction "1_1") (pintype "passive"))
      (node (ref "R92") (pin "2") (pinfunction "2_2") (pintype "passive"))
      (node (ref "X1") (pin "13") (pinfunction "13_13") (pintype "passive"))
      (node (ref "X1") (pin "18") (pinfunction "18_18") (pintype "passive"))
      (node (ref "X1") (pin "23") (pinfunction "23_23") (pintype "passive"))
      (node (ref "X10") (pin "13") (pinfunction "13_13") (pintype "passive"))
      (node (ref "X10") (pin "18") (pinfunction "18_18") (pintype "passive"))
      (node (ref "X10") (pin "23") (pinfunction "23_23") (pintype "passive"))
      (node (ref "X11") (pin "5") (pinfunction "S_5") (pintype "passive"))
      (node (ref "X12") (pin "1") (pinfunction "S_1") (pintype "passive"))
      (node (ref "X13") (pin "13") (pinfunction "13_13") (pintype "passive"))
      (node (ref "X13") (pin "18") (pinfunction "18_18") (pintype "passive"))
      (node (ref "X13") (pin "23") (pinfunction "23_23") (pintype "passive"))
      (node (ref "X14") (pin "5") (pinfunction "S_5") (pintype "passive"))
      (node (ref "X15") (pin "1") (pinfunction "S_1") (pintype "passive"))
      (node (ref "X16") (pin "13") (pinfunction "13_13") (pintype "passive"))
      (node (ref "X16") (pin "18") (pinfunction "18_18") (pintype "passive"))
      (node (ref "X16") (pin "23") (pinfunction "23_23") (pintype "passive"))
      (node (ref "X17") (pin "5") (pinfunction "S_5") (pintype "passive"))
      (node (ref "X18") (pin "1") (pinfunction "S_1") (pintype "passive"))
      (node (ref "X19") (pin "13") (pinfunction "13_13") (pintype "passive"))
      (node (ref "X19") (pin "18") (pinfunction "18_18") (pintype "passive"))
      (node (ref "X19") (pin "23") (pinfunction "23_23") (pintype "passive"))
      (node (ref "X2") (pin "1") (pinfunction "S_1") (pintype "passive"))
      (node (ref "X20") (pin "5") (pinfunction "S_5") (pintype "passive"))
      (node (ref "X21") (pin "1") (pinfunction "S_1") (pintype "passive"))
      (node (ref "X22") (pin "13") (pinfunction "13_13") (pintype "passive"))
      (node (ref "X22") (pin "18") (pinfunction "18_18") (pintype "passive"))
      (node (ref "X22") (pin "23") (pinfunction "23_23") (pintype "passive"))
      (node (ref "X23") (pin "5") (pinfunction "S_5") (pintype "passive"))
      (node (ref "X24") (pin "1") (pinfunction "S_1") (pintype "passive"))
      (node (ref "X25") (pin "13") (pinfunction "13_13") (pintype "passive"))
      (node (ref "X25") (pin "18") (pinfunction "18_18") (pintype "passive"))
      (node (ref "X25") (pin "23") (pinfunction "23_23") (pintype "passive"))
      (node (ref "X26") (pin "5") (pinfunction "S_5") (pintype "passive"))
      (node (ref "X27") (pin "1") (pinfunction "S_1") (pintype "passive"))
      (node (ref "X28") (pin "13") (pinfunction "13_13") (pintype "passive"))
      (node (ref "X28") (pin "18") (pinfunction "18_18") (pintype "passive"))
      (node (ref "X28") (pin "23") (pinfunction "23_23") (pintype "passive"))
      (node (ref "X29") (pin "5") (pinfunction "S_5") (pintype "passive"))
      (node (ref "X3") (pin "5") (pinfunction "S_5") (pintype "passive"))
      (node (ref "X30") (pin "1") (pinfunction "S_1") (pintype "passive"))
      (node (ref "X31") (pin "13") (pinfunction "13_13") (pintype "passive"))
      (node (ref "X31") (pin "18") (pinfunction "18_18") (pintype "passive"))
      (node (ref "X31") (pin "23") (pinfunction "23_23") (pintype "passive"))
      (node (ref "X32") (pin "5") (pinfunction "S_5") (pintype "passive"))
      (node (ref "X33") (pin "1") (pinfunction "S_1") (pintype "passive"))
      (node (ref "X34") (pin "13") (pinfunction "13_13") (pintype "passive"))
      (node (ref "X34") (pin "18") (pinfunction "18_18") (pintype "passive"))
      (node (ref "X34") (pin "23") (pinfunction "23_23") (pintype "passive"))
      (node (ref "X35") (pin "5") (pinfunction "S_5") (pintype "passive"))
      (node (ref "X36") (pin "1") (pinfunction "S_1") (pintype "passive"))
      (node (ref "X4") (pin "13") (pinfunction "13_13") (pintype "passive"))
      (node (ref "X4") (pin "18") (pinfunction "18_18") (pintype "passive"))
      (node (ref "X4") (pin "23") (pinfunction "23_23") (pintype "passive"))
      (node (ref "X5") (pin "5") (pinfunction "S_5") (pintype "passive"))
      (node (ref "X6") (pin "1") (pinfunction "S_1") (pintype "passive"))
      (node (ref "X7") (pin "13") (pinfunction "13_13") (pintype "passive"))
      (node (ref "X7") (pin "18") (pinfunction "18_18") (pintype "passive"))
      (node (ref "X7") (pin "23") (pinfunction "23_23") (pintype "passive"))
      (node (ref "X8") (pin "5") (pinfunction "S_5") (pintype "passive"))
      (node (ref "X9") (pin "1") (pinfunction "S_1") (pintype "passive"))
    )
    (net (code "4") (name "Net-(1A-KL)") (class "Default")
      (node (ref "1") (pin "1") (pinfunction "KL_1") (pintype "passive"))
      (node (ref "TP1") (pin "TP") (pinfunction "PP_TP") (pintype "input"))
      (node (ref "X1") (pin "1") (pinfunction "1_1") (pintype "passive"))
    )
    (net (code "5") (name "Net-(1B-KL)") (class "Default")
      (node (ref "1") (pin "10") (pinfunction "KL_10") (pintype "passive"))
      (node (ref "D2") (pin "2") (pinfunction "-_2") (pintype "passive"))
      (node (ref "D3") (pin "2") (pinfunction "-_2") (pintype "passive"))
      (node (ref "JP4") (pin "1") (pinfunction "1_1") (pintype "passive"))
      (node (ref "SJ1") (pin "1") (pinfunction "1_1") (pintype "passive"))
      (node (ref "TP10") (pin "TP") (pinfunction "PP_TP") (pintype "input"))
    )
    (net (code "6") (name "Net-(1C-KL)") (class "Default")
      (node (ref "1") (pin "11") (pinfunction "KL_11") (pintype "passive"))
      (node (ref "D3") (pin "1") (pinfunction "+_1") (pintype "passive"))
      (node (ref "TP11") (pin "TP") (pinfunction "PP_TP") (pintype "input"))
      (node (ref "X1") (pin "19") (pinfunction "19_19") (pintype "passive"))
    )
    (net (code "7") (name "Net-(1E-KL)") (class "Default")
      (node (ref "1") (pin "2") (pinfunction "KL_2") (pintype "passive"))
      (node (ref "Q1") (pin "2") (pinfunction "C_2") (pintype "passive"))
      (node (ref "TP2") (pin "TP") (pinfunction "PP_TP") (pintype "input"))
    )
    (net (code "8") (name "Net-(1F-KL)") (class "Default")
      (node (ref "1") (pin "3") (pinfunction "KL_3") (pintype "passive"))
      (node (ref "IC7") (pin "11") (pinfunction "O6_11") (pintype "open_collector"))
      (node (ref "TP3") (pin "TP") (pinfunction "PP_TP") (pintype "input"))
    )
    (net (code "9") (name "Net-(1G-KL)") (class "Default")
      (node (ref "1") (pin "4") (pinfunction "KL_4") (pintype "passive"))
      (node (ref "IC7") (pin "10") (pinfunction "O7_10") (pintype "open_collector"))
      (node (ref "TP4") (pin "TP") (pinfunction "PP_TP") (pintype "input"))
    )
    (net (code "10") (name "Net-(1H-KL)") (class "Default")
      (node (ref "1") (pin "5") (pinfunction "KL_5") (pintype "passive"))
      (node (ref "IC7") (pin "12") (pinfunction "O5_12") (pintype "open_collector"))
      (node (ref "TP5") (pin "TP") (pinfunction "PP_TP") (pintype "input"))
    )
    (net (code "11") (name "Net-(1I-KL)") (class "Default")
      (node (ref "1") (pin "6") (pinfunction "KL_6") (pintype "passive"))
      (node (ref "IC7") (pin "13") (pinfunction "O4_13") (pintype "open_collector"))
      (node (ref "TP6") (pin "TP") (pinfunction "PP_TP") (pintype "input"))
    )
    (net (code "12") (name "Net-(1J-KL)") (class "Default")
      (node (ref "1") (pin "7") (pinfunction "KL_7") (pintype "passive"))
      (node (ref "IC7") (pin "14") (pinfunction "O3_14") (pintype "open_collector"))
      (node (ref "TP7") (pin "TP") (pinfunction "PP_TP") (pintype "input"))
    )
    (net (code "13") (name "Net-(1K-KL)") (class "Default")
      (node (ref "1") (pin "8") (pinfunction "KL_8") (pintype "passive"))
      (node (ref "Q6") (pin "3") (pinfunction "D_3") (pintype "passive"))
      (node (ref "TP8") (pin "TP") (pinfunction "PP_TP") (pintype "input"))
    )
    (net (code "14") (name "Net-(1L-KL)") (class "Default")
      (node (ref "1") (pin "9") (pinfunction "KL_9") (pintype "passive"))
      (node (ref "D2") (pin "1") (pinfunction "+_1") (pintype "passive"))
      (node (ref "TP9") (pin "TP") (pinfunction "PP_TP") (pintype "input"))
      (node (ref "X1") (pin "17") (pinfunction "17_17") (pintype "passive"))
    )
    (net (code "15") (name "Net-(2B-KL)") (class "Default")
      (node (ref "2") (pin "10") (pinfunction "KL_10") (pintype "passive"))
      (node (ref "TP25") (pin "TP") (pinfunction "PP_TP") (pintype "input"))
      (node (ref "X1") (pin "15") (pinfunction "15_15") (pintype "passive"))
    )
    (net (code "16") (name "Net-(2C-KL)") (class "Default")
      (node (ref "2") (pin "11") (pinfunction "KL_11") (pintype "passive"))
      (node (ref "IC7") (pin "16") (pinfunction "O1_16") (pintype "open_collector"))
      (node (ref "R18") (pin "2") (pinfunction "2_2") (pintype "passive"))
      (node (ref "R19") (pin "1") (pinfunction "1_1") (pintype "passive"))
      (node (ref "TP26") (pin "TP") (pinfunction "PP_TP") (pintype "input"))
    )
    (net (code "17") (name "Net-(2D-KL)") (class "Default")
      (node (ref "2") (pin "12") (pinfunction "KL_12") (pintype "passive"))
      (node (ref "R46") (pin "1") (pinfunction "1_1") (pintype "passive"))
      (node (ref "TP13") (pin "TP") (pinfunction "PP_TP") (pintype "input"))
    )
    (net (code "18") (name "Net-(2E-KL)") (class "Default")
      (node (ref "2") (pin "2") (pinfunction "KL_2") (pintype "passive"))
      (node (ref "D9") (pin "2") (pinfunction "-_2") (pintype "passive"))
      (node (ref "LED2") (pin "K") (pinfunction "C_K") (pintype "passive"))
      (node (ref "TP16") (pin "TP") (pinfunction "PP_TP") (pintype "input"))
      (node (ref "X1") (pin "12") (pinfunction "12_12") (pintype "passive"))
    )
    (net (code "19") (name "Net-(2F-KL)") (class "Default")
      (node (ref "2") (pin "3") (pinfunction "KL_3") (pintype "passive"))
      (node (ref "D8") (pin "2") (pinfunction "-_2") (pintype "passive"))
      (node (ref "LED3") (pin "K") (pinfunction "C_K") (pintype "passive"))
      (node (ref "TP17") (pin "TP") (pinfunction "PP_TP") (pintype "input"))
      (node (ref "X1") (pin "11") (pinfunction "11_11") (pintype "passive"))
    )
    (net (code "20") (name "Net-(2G-KL)") (class "Default")
      (node (ref "2") (pin "4") (pinfunction "KL_4") (pintype "passive"))
      (node (ref "D7") (pin "2") (pinfunction "-_2") (pintype "passive"))
      (node (ref "LED4") (pin "K") (pinfunction "C_K") (pintype "passive"))
      (node (ref "TP18") (pin "TP") (pinfunction "PP_TP") (pintype "input"))
      (node (ref "X1") (pin "10") (pinfunction "10_10") (pintype "passive"))
    )
    (net (code "21") (name "Net-(2H-KL)") (class "Default")
      (node (ref "2") (pin "5") (pinfunction "KL_5") (pintype "passive"))
      (node (ref "D6") (pin "2") (pinfunction "-_2") (pintype "passive"))
      (node (ref "LED5") (pin "K") (pinfunction "C_K") (pintype "passive"))
      (node (ref "TP19") (pin "TP") (pinfunction "PP_TP") (pintype "input"))
      (node (ref "X1") (pin "9") (pinfunction "9_9") (pintype "passive"))
    )
    (net (code "22") (name "Net-(2I-KL)") (class "Default")
      (node (ref "2") (pin "6") (pinfunction "KL_6") (pintype "passive"))
      (node (ref "JP5") (pin "2") (pinfunction "2_2") (pintype "passive"))
      (node (ref "TP21") (pin "TP") (pinfunction "PP_TP") (pintype "input"))
    )
    (net (code "23") (name "Net-(2J-KL)") (class "Default")
      (node (ref "2") (pin "7") (pinfunction "KL_7") (pintype "passive"))
      (node (ref "LED1") (pin "A") (pinfunction "A_A") (pintype "passive"))
      (node (ref "TP22") (pin "TP") (pinfunction "PP_TP") (pintype "input"))
      (node (ref "X1") (pin "8") (pinfunction "8_8") (pintype "passive"))
    )
    (net (code "24") (name "Net-(2K-KL)") (class "Default")
      (node (ref "2") (pin "8") (pinfunction "KL_8") (pintype "passive"))
      (node (ref "D10") (pin "2") (pinfunction "-_2") (pintype "passive"))
      (node (ref "LED6") (pin "K") (pinfunction "C_K") (pintype "passive"))
      (node (ref "TP23") (pin "TP") (pinfunction "PP_TP") (pintype "input"))
      (node (ref "X1") (pin "14") (pinfunction "14_14") (pintype "passive"))
    )
    (net (code "25") (name "Net-(2L-KL)") (class "Default")
      (node (ref "2") (pin "9") (pinfunction "KL_9") (pintype "passive"))
      (node (ref "D7") (pin "1") (pinfunction "+_1") (pintype "passive"))
      (node (ref "D8") (pin "1") (pinfunction "+_1") (pintype "passive"))
      (node (ref "JP2") (pin "1") (pinfunction "1_1") (pintype "passive"))
      (node (ref "JP3") (pin "2") (pinfunction "2_2") (pintype "passive"))
      (node (ref "TP24") (pin "TP") (pinfunction "PP_TP") (pintype "input"))
    )
    (net (code "26") (name "Net-(3A-KL)") (class "Default")
      (node (ref "3") (pin "1") (pinfunction "KL_1") (pintype "passive"))
      (node (ref "TP14") (pin "TP") (pinfunction "PP_TP") (pintype "input"))
      (node (ref "X4") (pin "1") (pinfunction "1_1") (pintype "passive"))
    )
    (net (code "27") (name "Net-(3B-KL)") (class "Default")
      (node (ref "3") (pin "10") (pinfunction "KL_10") (pintype "passive"))
      (node (ref "D14") (pin "2") (pinfunction "-_2") (pintype "passive"))
      (node (ref "D15") (pin "2") (pinfunction "-_2") (pintype "passive"))
      (node (ref "JP10") (pin "1") (pinfunction "1_1") (pintype "passive"))
      (node (ref "SJ2") (pin "1") (pinfunction "1_1") (pintype "passive"))
      (node (ref "TP33") (pin "TP") (pinfunction "PP_TP") (pintype "input"))
    )
    (net (code "28") (name "Net-(3C-KL)") (class "Default")
      (node (ref "3") (pin "11") (pinfunction "KL_11") (pintype "passive"))
      (node (ref "D15") (pin "1") (pinfunction "+_1") (pintype "passive"))
      (node (ref "TP34") (pin "TP") (pinfunction "PP_TP") (pintype "input"))
      (node (ref "X4") (pin "19") (pinfunction "19_19") (pintype "passive"))
    )
    (net (code "29") (name "Net-(3E-KL)") (class "Default")
      (node (ref "3") (pin "2") (pinfunction "KL_2") (pintype "passive"))
      (node (ref "Q10") (pin "2") (pinfunction "C_2") (pintype "passive"))
      (node (ref "TP15") (pin "TP") (pinfunction "PP_TP") (pintype "input"))
    )
    (net (code "30") (name "Net-(3F-KL)") (class "Default")
      (node (ref "3") (pin "3") (pinfunction "KL_3") (pintype "passive"))
      (node (ref "IC15") (pin "11") (pinfunction "O6_11") (pintype "open_collector"))
      (node (ref "TP20") (pin "TP") (pinfunction "PP_TP") (pintype "input"))
    )
    (net (code "31") (name "Net-(3G-KL)") (class "Default")
      (node (ref "3") (pin "4") (pinfunction "KL_4") (pintype "passive"))
      (node (ref "IC15") (pin "10") (pinfunction "O7_10") (pintype "open_collector"))
      (node (ref "TP27") (pin "TP") (pinfunction "PP_TP") (pintype "input"))
    )
    (net (code "32") (name "Net-(3H-KL)") (class "Default")
      (node (ref "3") (pin "5") (pinfunction "KL_5") (pintype "passive"))
      (node (ref "IC15") (pin "12") (pinfunction "O5_12") (pintype "open_collector"))
      (node (ref "TP28") (pin "TP") (pinfunction "PP_TP") (pintype "input"))
    )
    (net (code "33") (name "Net-(3I-KL)") (class "Default")
      (node (ref "3") (pin "6") (pinfunction "KL_6") (pintype "passive"))
      (node (ref "IC15") (pin "13") (pinfunction "O4_13") (pintype "open_collector"))
      (node (ref "TP29") (pin "TP") (pinfunction "PP_TP") (pintype "input"))
    )
    (net (code "34") (name "Net-(3J-KL)") (class "Default")
      (node (ref "3") (pin "7") (pinfunction "KL_7") (pintype "passive"))
      (node (ref "IC15") (pin "14") (pinfunction "O3_14") (pintype "open_collector"))
      (node (ref "TP30") (pin "TP") (pinfunction "PP_TP") (pintype "input"))
    )
    (net (code "35") (name "Net-(3K-KL)") (class "Default")
      (node (ref "3") (pin "8") (pinfunction "KL_8") (pintype "passive"))
      (node (ref "Q14") (pin "3") (pinfunction "D_3") (pintype "passive"))
      (node (ref "TP31") (pin "TP") (pinfunction "PP_TP") (pintype "input"))
    )
    (net (code "36") (name "Net-(3L-KL)") (class "Default")
      (node (ref "3") (pin "9") (pinfunction "KL_9") (pintype "passive"))
      (node (ref "D14") (pin "1") (pinfunction "+_1") (pintype "passive"))
      (node (ref "TP32") (pin "TP") (pinfunction "PP_TP") (pintype "input"))
      (node (ref "X4") (pin "17") (pinfunction "17_17") (pintype "passive"))
    )
    (net (code "37") (name "Net-(4B-KL)") (class "Default")
      (node (ref "4") (pin "10") (pinfunction "KL_10") (pintype "passive"))
      (node (ref "TP43") (pin "TP") (pinfunction "PP_TP") (pintype "input"))
      (node (ref "X4") (pin "15") (pinfunction "15_15") (pintype "passive"))
    )
    (net (code "38") (name "Net-(4C-KL)") (class "Default")
      (node (ref "4") (pin "11") (pinfunction "KL_11") (pintype "passive"))
      (node (ref "IC15") (pin "16") (pinfunction "O1_16") (pintype "open_collector"))
      (node (ref "R84") (pin "1") (pinfunction "1_1") (pintype "passive"))
      (node (ref "R91") (pin "2") (pinfunction "2_2") (pintype "passive"))
      (node (ref "TP44") (pin "TP") (pinfunction "PP_TP") (pintype "input"))
    )
    (net (code "39") (name "Net-(4D-KL)") (class "Default")
      (node (ref "4") (pin "12") (pinfunction "KL_12") (pintype "passive"))
      (node (ref "R85") (pin "1") (pinfunction "1_1") (pintype "passive"))
      (node (ref "TP46") (pin "TP") (pinfunction "PP_TP") (pintype "input"))
    )
    (net (code "40") (name "Net-(4E-KL)") (class "Default")
      (node (ref "4") (pin "2") (pinfunction "KL_2") (pintype "passive"))
      (node (ref "D19") (pin "2") (pinfunction "-_2") (pintype "passive"))
      (node (ref "LED7") (pin "K") (pinfunction "C_K") (pintype "passive"))
      (node (ref "TP35") (pin "TP") (pinfunction "PP_TP") (pintype "input"))
      (node (ref "X4") (pin "12") (pinfunction "12_12") (pintype "passive"))
    )
    (net (code "41") (name "Net-(4F-KL)") (class "Default")
      (node (ref "4") (pin "3") (pinfunction "KL_3") (pintype "passive"))
      (node (ref "D18") (pin "2") (pinfunction "-_2") (pintype "passive"))
      (node (ref "LED8") (pin "K") (pinfunction "C_K") (pintype "passive"))
      (node (ref "TP36") (pin "TP") (pinfunction "PP_TP") (pintype "input"))
      (node (ref "X4") (pin "11") (pinfunction "11_11") (pintype "passive"))
    )
    (net (code "42") (name "Net-(4G-KL)") (class "Default")
      (node (ref "4") (pin "4") (pinfunction "KL_4") (pintype "passive"))
      (node (ref "D17") (pin "2") (pinfunction "-_2") (pintype "passive"))
      (node (ref "LED9") (pin "K") (pinfunction "C_K") (pintype "passive"))
      (node (ref "TP37") (pin "TP") (pinfunction "PP_TP") (pintype "input"))
      (node (ref "X4") (pin "10") (pinfunction "10_10") (pintype "passive"))
    )
    (net (code "43") (name "Net-(4H-KL)") (class "Default")
      (node (ref "4") (pin "5") (pinfunction "KL_5") (pintype "passive"))
      (node (ref "D16") (pin "2") (pinfunction "-_2") (pintype "passive"))
      (node (ref "LED10") (pin "K") (pinfunction "C_K") (pintype "passive"))
      (node (ref "TP38") (pin "TP") (pinfunction "PP_TP") (pintype "input"))
      (node (ref "X4") (pin "9") (pinfunction "9_9") (pintype "passive"))
    )
    (net (code "44") (name "Net-(4I-KL)") (class "Default")
      (node (ref "4") (pin "6") (pinfunction "KL_6") (pintype "passive"))
      (node (ref "JP7") (pin "2") (pinfunction "2_2") (pintype "passive"))
      (node (ref "TP39") (pin "TP") (pinfunction "PP_TP") (pintype "input"))
    )
    (net (code "45") (name "Net-(4J-KL)") (class "Default")
      (node (ref "4") (pin "7") (pinfunction "KL_7") (pintype "passive"))
      (node (ref "LED11") (pin "A") (pinfunction "A_A") (pintype "passive"))
      (node (ref "TP40") (pin "TP") (pinfunction "PP_TP") (pintype "input"))
      (node (ref "X4") (pin "8") (pinfunction "8_8") (pintype "passive"))
    )
    (net (code "46") (name "Net-(4K-KL)") (class "Default")
      (node (ref "4") (pin "8") (pinfunction "KL_8") (pintype "passive"))
      (node (ref "D20") (pin "2") (pinfunction "-_2") (pintype "passive"))
      (node (ref "LED12") (pin "K") (pinfunction "C_K") (pintype "passive"))
      (node (ref "TP41") (pin "TP") (pinfunction "PP_TP") (pintype "input"))
      (node (ref "X4") (pin "14") (pinfunction "14_14") (pintype "passive"))
    )
    (net (code "47") (name "Net-(4L-KL)") (class "Default")
      (node (ref "4") (pin "9") (pinfunction "KL_9") (pintype "passive"))
      (node (ref "D17") (pin "1") (pinfunction "+_1") (pintype "passive"))
      (node (ref "D18") (pin "1") (pinfunction "+_1") (pintype "passive"))
      (node (ref "JP8") (pin "1") (pinfunction "1_1") (pintype "passive"))
      (node (ref "JP9") (pin "2") (pinfunction "2_2") (pintype "passive"))
      (node (ref "TP42") (pin "TP") (pinfunction "PP_TP") (pintype "input"))
    )
    (net (code "48") (name "Net-(5A-KL)") (class "Default")
      (node (ref "5") (pin "1") (pinfunction "KL_1") (pintype "passive"))
      (node (ref "TP47") (pin "TP") (pinfunction "PP_TP") (pintype "input"))
      (node (ref "X7") (pin "1") (pinfunction "1_1") (pintype "passive"))
    )
    (net (code "49") (name "Net-(5B-KL)") (class "Default")
      (node (ref "5") (pin "10") (pinfunction "KL_10") (pintype "passive"))
      (node (ref "D26") (pin "2") (pinfunction "-_2") (pintype "passive"))
      (node (ref "D27") (pin "2") (pinfunction "-_2") (pintype "passive"))
      (node (ref "JP15") (pin "1") (pinfunction "1_1") (pintype "passive"))
      (node (ref "SJ3") (pin "1") (pinfunction "1_1") (pintype "passive"))
      (node (ref "TP56") (pin "TP") (pinfunction "PP_TP") (pintype "input"))
    )
    (net (code "50") (name "Net-(5C-KL)") (class "Default")
      (node (ref "5") (pin "11") (pinfunction "KL_11") (pintype "passive"))
      (node (ref "D27") (pin "1") (pinfunction "+_1") (pintype "passive"))
      (node (ref "TP57") (pin "TP") (pinfunction "PP_TP") (pintype "input"))
      (node (ref "X7") (pin "19") (pinfunction "19_19") (pintype "passive"))
    )
    (net (code "51") (name "Net-(5E-KL)") (class "Default")
      (node (ref "5") (pin "2") (pinfunction "KL_2") (pintype "passive"))
      (node (ref "Q17") (pin "2") (pinfunction "C_2") (pintype "passive"))
      (node (ref "TP48") (pin "TP") (pinfunction "PP_TP") (pintype "input"))
    )
    (net (code "52") (name "Net-(5F-KL)") (class "Default")
      (node (ref "5") (pin "3") (pinfunction "KL_3") (pintype "passive"))
      (node (ref "IC26") (pin "11") (pinfunction "O6_11") (pintype "open_collector"))
      (node (ref "TP49") (pin "TP") (pinfunction "PP_TP") (pintype "input"))
    )
    (net (code "53") (name "Net-(5G-KL)") (class "Default")
      (node (ref "5") (pin "4") (pinfunction "KL_4") (pintype "passive"))
      (node (ref "IC26") (pin "10") (pinfunction "O7_10") (pintype "open_collector"))
      (node (ref "TP50") (pin "TP") (pinfunction "PP_TP") (pintype "input"))
    )
    (net (code "54") (name "Net-(5H-KL)") (class "Default")
      (node (ref "5") (pin "5") (pinfunction "KL_5") (pintype "passive"))
      (node (ref "IC26") (pin "12") (pinfunction "O5_12") (pintype "open_collector"))
      (node (ref "TP51") (pin "TP") (pinfunction "PP_TP") (pintype "input"))
    )
    (net (code "55") (name "Net-(5I-KL)") (class "Default")
      (node (ref "5") (pin "6") (pinfunction "KL_6") (pintype "passive"))
      (node (ref "IC26") (pin "13") (pinfunction "O4_13") (pintype "open_collector"))
      (node (ref "TP52") (pin "TP") (pinfunction "PP_TP") (pintype "input"))
    )
    (net (code "56") (name "Net-(5J-KL)") (class "Default")
      (node (ref "5") (pin "7") (pinfunction "KL_7") (pintype "passive"))
      (node (ref "IC26") (pin "14") (pinfunction "O3_14") (pintype "open_collector"))
      (node (ref "TP53") (pin "TP") (pinfunction "PP_TP") (pintype "input"))
    )
    (net (code "57") (name "Net-(5K-KL)") (class "Default")
      (node (ref "5") (pin "8") (pinfunction "KL_8") (pintype "passive"))
      (node (ref "Q21") (pin "3") (pinfunction "D_3") (pintype "passive"))
      (node (ref "TP54") (pin "TP") (pinfunction "PP_TP") (pintype "input"))
    )
    (net (code "58") (name "Net-(5L-KL)") (class "Default")
      (node (ref "5") (pin "9") (pinfunction "KL_9") (pintype "passive"))
      (node (ref "D26") (pin "1") (pinfunction "+_1") (pintype "passive"))
      (node (ref "TP55") (pin "TP") (pinfunction "PP_TP") (pintype "input"))
      (node (ref "X7") (pin "17") (pinfunction "17_17") (pintype "passive"))
    )
    (net (code "59") (name "Net-(6B-KL)") (class "Default")
      (node (ref "6") (pin "10") (pinfunction "KL_10") (pintype "passive"))
      (node (ref "TP66") (pin "TP") (pinfunction "PP_TP") (pintype "input"))
      (node (ref "X7") (pin "15") (pinfunction "15_15") (pintype "passive"))
    )
    (net (code "60") (name "Net-(6C-KL)") (class "Default")
      (node (ref "6") (pin "11") (pinfunction "KL_11") (pintype "passive"))
      (node (ref "IC26") (pin "16") (pinfunction "O1_16") (pintype "open_collector"))
      (node (ref "R130") (pin "1") (pinfunction "1_1") (pintype "passive"))
      (node (ref "R137") (pin "2") (pinfunction "2_2") (pintype "passive"))
      (node (ref "TP67") (pin "TP") (pinfunction "PP_TP") (pintype "input"))
    )
    (net (code "61") (name "Net-(6D-KL)") (class "Default")
      (node (ref "6") (pin "12") (pinfunction "KL_12") (pintype "passive"))
      (node (ref "R131") (pin "1") (pinfunction "1_1") (pintype "passive"))
      (node (ref "TP69") (pin "TP") (pinfunction "PP_TP") (pintype "input"))
    )
    (net (code "62") (name "Net-(6E-KL)") (class "Default")
      (node (ref "6") (pin "2") (pinfunction "KL_2") (pintype "passive"))
      (node (ref "D31") (pin "2") (pinfunction "-_2") (pintype "passive"))
      (node (ref "LED13") (pin "K") (pinfunction "C_K") (pintype "passive"))
      (node (ref "TP58") (pin "TP") (pinfunction "PP_TP") (pintype "input"))
      (node (ref "X7") (pin "12") (pinfunction "12_12") (pintype "passive"))
    )
    (net (code "63") (name "Net-(6F-KL)") (class "Default")
      (node (ref "6") (pin "3") (pinfunction "KL_3") (pintype "passive"))
      (node (ref "D30") (pin "2") (pinfunction "-_2") (pintype "passive"))
      (node (ref "LED14") (pin "K") (pinfunction "C_K") (pintype "passive"))
      (node (ref "TP59") (pin "TP") (pinfunction "PP_TP") (pintype "input"))
      (node (ref "X7") (pin "11") (pinfunction "11_11") (pintype "passive"))
    )
    (net (code "64") (name "Net-(6G-KL)") (class "Default")
      (node (ref "6") (pin "4") (pinfunction "KL_4") (pintype "passive"))
      (node (ref "D29") (pin "2") (pinfunction "-_2") (pintype "passive"))
      (node (ref "LED15") (pin "K") (pinfunction "C_K") (pintype "passive"))
      (node (ref "TP60") (pin "TP") (pinfunction "PP_TP") (pintype "input"))
      (node (ref "X7") (pin "10") (pinfunction "10_10") (pintype "passive"))
    )
    (net (code "65") (name "Net-(6H-KL)") (class "Default")
      (node (ref "6") (pin "5") (pinfunction "KL_5") (pintype "passive"))
      (node (ref "D28") (pin "2") (pinfunction "-_2") (pintype "passive"))
      (node (ref "LED16") (pin "K") (pinfunction "C_K") (pintype "passive"))
      (node (ref "TP61") (pin "TP") (pinfunction "PP_TP") (pintype "input"))
      (node (ref "X7") (pin "9") (pinfunction "9_9") (pintype "passive"))
    )
    (net (code "66") (name "Net-(6I-KL)") (class "Default")
      (node (ref "6") (pin "6") (pinfunction "KL_6") (pintype "passive"))
      (node (ref "JP12") (pin "2") (pinfunction "2_2") (pintype "passive"))
      (node (ref "TP62") (pin "TP") (pinfunction "PP_TP") (pintype "input"))
    )
    (net (code "67") (name "Net-(6J-KL)") (class "Default")
      (node (ref "6") (pin "7") (pinfunction "KL_7") (pintype "passive"))
      (node (ref "LED17") (pin "A") (pinfunction "A_A") (pintype "passive"))
      (node (ref "TP63") (pin "TP") (pinfunction "PP_TP") (pintype "input"))
      (node (ref "X7") (pin "8") (pinfunction "8_8") (pintype "passive"))
    )
    (net (code "68") (name "Net-(6K-KL)") (class "Default")
      (node (ref "6") (pin "8") (pinfunction "KL_8") (pintype "passive"))
      (node (ref "D32") (pin "2") (pinfunction "-_2") (pintype "passive"))
      (node (ref "LED18") (pin "K") (pinfunction "C_K") (pintype "passive"))
      (node (ref "TP64") (pin "TP") (pinfunction "PP_TP") (pintype "input"))
      (node (ref "X7") (pin "14") (pinfunction "14_14") (pintype "passive"))
    )
    (net (code "69") (name "Net-(6L-KL)") (class "Default")
      (node (ref "6") (pin "9") (pinfunction "KL_9") (pintype "passive"))
      (node (ref "D29") (pin "1") (pinfunction "+_1") (pintype "passive"))
      (node (ref "D30") (pin "1") (pinfunction "+_1") (pintype "passive"))
      (node (ref "JP13") (pin "1") (pinfunction "1_1") (pintype "passive"))
      (node (ref "JP14") (pin "2") (pinfunction "2_2") (pintype "passive"))
      (node (ref "TP65") (pin "TP") (pinfunction "PP_TP") (pintype "input"))
    )
    (net (code "70") (name "Net-(7A-KL)") (class "Default")
      (node (ref "7") (pin "1") (pinfunction "KL_1") (pintype "passive"))
      (node (ref "TP70") (pin "TP") (pinfunction "PP_TP") (pintype "input"))
      (node (ref "X10") (pin "1") (pinfunction "1_1") (pintype "passive"))
    )
    (net (code "71") (name "Net-(7B-KL)") (class "Default")
      (node (ref "7") (pin "10") (pinfunction "KL_10") (pintype "passive"))
      (node (ref "D38") (pin "2") (pinfunction "-_2") (pintype "passive"))
      (node (ref "D39") (pin "2") (pinfunction "-_2") (pintype "passive"))
      (node (ref "JP20") (pin "1") (pinfunction "1_1") (pintype "passive"))
      (node (ref "SJ4") (pin "1") (pinfunction "1_1") (pintype "passive"))
      (node (ref "TP79") (pin "TP") (pinfunction "PP_TP") (pintype "input"))
    )
    (net (code "72") (name "Net-(7C-KL)") (class "Default")
      (node (ref "7") (pin "11") (pinfunction "KL_11") (pintype "passive"))
      (node (ref "D39") (pin "1") (pinfunction "+_1") (pintype "passive"))
      (node (ref "TP80") (pin "TP") (pinfunction "PP_TP") (pintype "input"))
      (node (ref "X10") (pin "19") (pinfunction "19_19") (pintype "passive"))
    )
    (net (code "73") (name "Net-(7E-KL)") (class "Default")
      (node (ref "7") (pin "2") (pinfunction "KL_2") (pintype "passive"))
      (node (ref "Q24") (pin "2") (pinfunction "C_2") (pintype "passive"))
      (node (ref "TP71") (pin "TP") (pinfunction "PP_TP") (pintype "input"))
    )
    (net (code "74") (name "Net-(7F-KL)") (class "Default")
      (node (ref "7") (pin "3") (pinfunction "KL_3") (pintype "passive"))
      (node (ref "IC37") (pin "11") (pinfunction "O6_11") (pintype "open_collector"))
      (node (ref "TP72") (pin "TP") (pinfunction "PP_TP") (pintype "input"))
    )
    (net (code "75") (name "Net-(7G-KL)") (class "Default")
      (node (ref "7") (pin "4") (pinfunction "KL_4") (pintype "passive"))
      (node (ref "IC37") (pin "10") (pinfunction "O7_10") (pintype "open_collector"))
      (node (ref "TP73") (pin "TP") (pinfunction "PP_TP") (pintype "input"))
    )
    (net (code "76") (name "Net-(7H-KL)") (class "Default")
      (node (ref "7") (pin "5") (pinfunction "KL_5") (pintype "passive"))
      (node (ref "IC37") (pin "12") (pinfunction "O5_12") (pintype "open_collector"))
      (node (ref "TP74") (pin "TP") (pinfunction "PP_TP") (pintype "input"))
    )
    (net (code "77") (name "Net-(7I-KL)") (class "Default")
      (node (ref "7") (pin "6") (pinfunction "KL_6") (pintype "passive"))
      (node (ref "IC37") (pin "13") (pinfunction "O4_13") (pintype "open_collector"))
      (node (ref "TP75") (pin "TP") (pinfunction "PP_TP") (pintype "input"))
    )
    (net (code "78") (name "Net-(7J-KL)") (class "Default")
      (node (ref "7") (pin "7") (pinfunction "KL_7") (pintype "passive"))
      (node (ref "IC37") (pin "14") (pinfunction "O3_14") (pintype "open_collector"))
      (node (ref "TP76") (pin "TP") (pinfunction "PP_TP") (pintype "input"))
    )
    (net (code "79") (name "Net-(7K-KL)") (class "Default")
      (node (ref "7") (pin "8") (pinfunction "KL_8") (pintype "passive"))
      (node (ref "Q28") (pin "3") (pinfunction "D_3") (pintype "passive"))
      (node (ref "TP77") (pin "TP") (pinfunction "PP_TP") (pintype "input"))
    )
    (net (code "80") (name "Net-(7L-KL)") (class "Default")
      (node (ref "7") (pin "9") (pinfunction "KL_9") (pintype "passive"))
      (node (ref "D38") (pin "1") (pinfunction "+_1") (pintype "passive"))
      (node (ref "TP78") (pin "TP") (pinfunction "PP_TP") (pintype "input"))
      (node (ref "X10") (pin "17") (pinfunction "17_17") (pintype "passive"))
    )
    (net (code "81") (name "Net-(8B-KL)") (class "Default")
      (node (ref "8") (pin "10") (pinfunction "KL_10") (pintype "passive"))
      (node (ref "TP89") (pin "TP") (pinfunction "PP_TP") (pintype "input"))
      (node (ref "X10") (pin "15") (pinfunction "15_15") (pintype "passive"))
    )
    (net (code "82") (name "Net-(8C-KL)") (class "Default")
      (node (ref "8") (pin "11") (pinfunction "KL_11") (pintype "passive"))
      (node (ref "IC37") (pin "16") (pinfunction "O1_16") (pintype "open_collector"))
      (node (ref "R176") (pin "1") (pinfunction "1_1") (pintype "passive"))
      (node (ref "R183") (pin "2") (pinfunction "2_2") (pintype "passive"))
      (node (ref "TP90") (pin "TP") (pinfunction "PP_TP") (pintype "input"))
    )
    (net (code "83") (name "Net-(8D-KL)") (class "Default")
      (node (ref "8") (pin "12") (pinfunction "KL_12") (pintype "passive"))
      (node (ref "R177") (pin "1") (pinfunction "1_1") (pintype "passive"))
      (node (ref "TP92") (pin "TP") (pinfunction "PP_TP") (pintype "input"))
    )
    (net (code "84") (name "Net-(8E-KL)") (class "Default")
      (node (ref "8") (pin "2") (pinfunction "KL_2") (pintype "passive"))
      (node (ref "D43") (pin "2") (pinfunction "-_2") (pintype "passive"))
      (node (ref "LED19") (pin "K") (pinfunction "C_K") (pintype "passive"))
      (node (ref "TP81") (pin "TP") (pinfunction "PP_TP") (pintype "input"))
      (node (ref "X10") (pin "12") (pinfunction "12_12") (pintype "passive"))
    )
    (net (code "85") (name "Net-(8F-KL)") (class "Default")
      (node (ref "8") (pin "3") (pinfunction "KL_3") (pintype "passive"))
      (node (ref "D42") (pin "2") (pinfunction "-_2") (pintype "passive"))
      (node (ref "LED20") (pin "K") (pinfunction "C_K") (pintype "passive"))
      (node (ref "TP82") (pin "TP") (pinfunction "PP_TP") (pintype "input"))
      (node (ref "X10") (pin "11") (pinfunction "11_11") (pintype "passive"))
    )
    (net (code "86") (name "Net-(8G-KL)") (class "Default")
      (node (ref "8") (pin "4") (pinfunction "KL_4") (pintype "passive"))
      (node (ref "D41") (pin "2") (pinfunction "-_2") (pintype "passive"))
      (node (ref "LED21") (pin "K") (pinfunction "C_K") (pintype "passive"))
      (node (ref "TP83") (pin "TP") (pinfunction "PP_TP") (pintype "input"))
      (node (ref "X10") (pin "10") (pinfunction "10_10") (pintype "passive"))
    )
    (net (code "87") (name "Net-(8H-KL)") (class "Default")
      (node (ref "8") (pin "5") (pinfunction "KL_5") (pintype "passive"))
      (node (ref "D40") (pin "2") (pinfunction "-_2") (pintype "passive"))
      (node (ref "LED22") (pin "K") (pinfunction "C_K") (pintype "passive"))
      (node (ref "TP84") (pin "TP") (pinfunction "PP_TP") (pintype "input"))
      (node (ref "X10") (pin "9") (pinfunction "9_9") (pintype "passive"))
    )
    (net (code "88") (name "Net-(8I-KL)") (class "Default")
      (node (ref "8") (pin "6") (pinfunction "KL_6") (pintype "passive"))
      (node (ref "JP17") (pin "2") (pinfunction "2_2") (pintype "passive"))
      (node (ref "TP85") (pin "TP") (pinfunction "PP_TP") (pintype "input"))
    )
    (net (code "89") (name "Net-(8J-KL)") (class "Default")
      (node (ref "8") (pin "7") (pinfunction "KL_7") (pintype "passive"))
      (node (ref "LED23") (pin "A") (pinfunction "A_A") (pintype "passive"))
      (node (ref "TP86") (pin "TP") (pinfunction "PP_TP") (pintype "input"))
      (node (ref "X10") (pin "8") (pinfunction "8_8") (pintype "passive"))
    )
    (net (code "90") (name "Net-(8K-KL)") (class "Default")
      (node (ref "8") (pin "8") (pinfunction "KL_8") (pintype "passive"))
      (node (ref "D44") (pin "2") (pinfunction "-_2") (pintype "passive"))
      (node (ref "LED24") (pin "K") (pinfunction "C_K") (pintype "passive"))
      (node (ref "TP87") (pin "TP") (pinfunction "PP_TP") (pintype "input"))
      (node (ref "X10") (pin "14") (pinfunction "14_14") (pintype "passive"))
    )
    (net (code "91") (name "Net-(8L-KL)") (class "Default")
      (node (ref "8") (pin "9") (pinfunction "KL_9") (pintype "passive"))
      (node (ref "D41") (pin "1") (pinfunction "+_1") (pintype "passive"))
      (node (ref "D42") (pin "1") (pinfunction "+_1") (pintype "passive"))
      (node (ref "JP18") (pin "1") (pinfunction "1_1") (pintype "passive"))
      (node (ref "JP19") (pin "2") (pinfunction "2_2") (pintype "passive"))
      (node (ref "TP88") (pin "TP") (pinfunction "PP_TP") (pintype "input"))
    )
    (net (code "92") (name "Net-(9A-KL)") (class "Default")
      (node (ref "9") (pin "1") (pinfunction "KL_1") (pintype "passive"))
      (node (ref "TP93") (pin "TP") (pinfunction "PP_TP") (pintype "input"))
      (node (ref "X13") (pin "1") (pinfunction "1_1") (pintype "passive"))
    )
    (net (code "93") (name "Net-(9B-KL)") (class "Default")
      (node (ref "9") (pin "10") (pinfunction "KL_10") (pintype "passive"))
      (node (ref "D50") (pin "2") (pinfunction "-_2") (pintype "passive"))
      (node (ref "D51") (pin "2") (pinfunction "-_2") (pintype "passive"))
      (node (ref "JP25") (pin "1") (pinfunction "1_1") (pintype "passive"))
      (node (ref "SJ5") (pin "1") (pinfunction "1_1") (pintype "passive"))
      (node (ref "TP102") (pin "TP") (pinfunction "PP_TP") (pintype "input"))
    )
    (net (code "94") (name "Net-(9C-KL)") (class "Default")
      (node (ref "9") (pin "11") (pinfunction "KL_11") (pintype "passive"))
      (node (ref "D51") (pin "1") (pinfunction "+_1") (pintype "passive"))
      (node (ref "TP103") (pin "TP") (pinfunction "PP_TP") (pintype "input"))
      (node (ref "X13") (pin "19") (pinfunction "19_19") (pintype "passive"))
    )
    (net (code "95") (name "Net-(9E-KL)") (class "Default")
      (node (ref "9") (pin "2") (pinfunction "KL_2") (pintype "passive"))
      (node (ref "Q31") (pin "2") (pinfunction "C_2") (pintype "passive"))
      (node (ref "TP94") (pin "TP") (pinfunction "PP_TP") (pintype "input"))
    )
    (net (code "96") (name "Net-(9F-KL)") (class "Default")
      (node (ref "9") (pin "3") (pinfunction "KL_3") (pintype "passive"))
      (node (ref "IC48") (pin "11") (pinfunction "O6_11") (pintype "open_collector"))
      (node (ref "TP95") (pin "TP") (pinfunction "PP_TP") (pintype "input"))
    )
    (net (code "97") (name "Net-(9G-KL)") (class "Default")
      (node (ref "9") (pin "4") (pinfunction "KL_4") (pintype "passive"))
      (node (ref "IC48") (pin "10") (pinfunction "O7_10") (pintype "open_collector"))
      (node (ref "TP96") (pin "TP") (pinfunction "PP_TP") (pintype "input"))
    )
    (net (code "98") (name "Net-(9H-KL)") (class "Default")
      (node (ref "9") (pin "5") (pinfunction "KL_5") (pintype "passive"))
      (node (ref "IC48") (pin "12") (pinfunction "O5_12") (pintype "open_collector"))
      (node (ref "TP97") (pin "TP") (pinfunction "PP_TP") (pintype "input"))
    )
    (net (code "99") (name "Net-(9I-KL)") (class "Default")
      (node (ref "9") (pin "6") (pinfunction "KL_6") (pintype "passive"))
      (node (ref "IC48") (pin "13") (pinfunction "O4_13") (pintype "open_collector"))
      (node (ref "TP98") (pin "TP") (pinfunction "PP_TP") (pintype "input"))
    )
    (net (code "100") (name "Net-(9J-KL)") (class "Default")
      (node (ref "9") (pin "7") (pinfunction "KL_7") (pintype "passive"))
      (node (ref "IC48") (pin "14") (pinfunction "O3_14") (pintype "open_collector"))
      (node (ref "TP99") (pin "TP") (pinfunction "PP_TP") (pintype "input"))
    )
    (net (code "101") (name "Net-(9K-KL)") (class "Default")
      (node (ref "9") (pin "8") (pinfunction "KL_8") (pintype "passive"))
      (node (ref "Q35") (pin "3") (pinfunction "D_3") (pintype "passive"))
      (node (ref "TP100") (pin "TP") (pinfunction "PP_TP") (pintype "input"))
    )
    (net (code "102") (name "Net-(9L-KL)") (class "Default")
      (node (ref "9") (pin "9") (pinfunction "KL_9") (pintype "passive"))
      (node (ref "D50") (pin "1") (pinfunction "+_1") (pintype "passive"))
      (node (ref "TP101") (pin "TP") (pinfunction "PP_TP") (pintype "input"))
      (node (ref "X13") (pin "17") (pinfunction "17_17") (pintype "passive"))
    )
    (net (code "103") (name "Net-(10B-KL)") (class "Default")
      (node (ref "10") (pin "10") (pinfunction "KL_10") (pintype "passive"))
      (node (ref "TP112") (pin "TP") (pinfunction "PP_TP") (pintype "input"))
      (node (ref "X13") (pin "15") (pinfunction "15_15") (pintype "passive"))
    )
    (net (code "104") (name "Net-(10C-KL)") (class "Default")
      (node (ref "10") (pin "11") (pinfunction "KL_11") (pintype "passive"))
      (node (ref "IC48") (pin "16") (pinfunction "O1_16") (pintype "open_collector"))
      (node (ref "R222") (pin "1") (pinfunction "1_1") (pintype "passive"))
      (node (ref "R229") (pin "2") (pinfunction "2_2") (pintype "passive"))
      (node (ref "TP113") (pin "TP") (pinfunction "PP_TP") (pintype "input"))
    )
    (net (code "105") (name "Net-(10D-KL)") (class "Default")
      (node (ref "10") (pin "12") (pinfunction "KL_12") (pintype "passive"))
      (node (ref "R223") (pin "1") (pinfunction "1_1") (pintype "passive"))
      (node (ref "TP115") (pin "TP") (pinfunction "PP_TP") (pintype "input"))
    )
    (net (code "106") (name "Net-(10E-KL)") (class "Default")
      (node (ref "10") (pin "2") (pinfunction "KL_2") (pintype "passive"))
      (node (ref "D55") (pin "2") (pinfunction "-_2") (pintype "passive"))
      (node (ref "LED25") (pin "K") (pinfunction "C_K") (pintype "passive"))
      (node (ref "TP104") (pin "TP") (pinfunction "PP_TP") (pintype "input"))
      (node (ref "X13") (pin "12") (pinfunction "12_12") (pintype "passive"))
    )
    (net (code "107") (name "Net-(10F-KL)") (class "Default")
      (node (ref "10") (pin "3") (pinfunction "KL_3") (pintype "passive"))
      (node (ref "D54") (pin "2") (pinfunction "-_2") (pintype "passive"))
      (node (ref "LED26") (pin "K") (pinfunction "C_K") (pintype "passive"))
      (node (ref "TP105") (pin "TP") (pinfunction "PP_TP") (pintype "input"))
      (node (ref "X13") (pin "11") (pinfunction "11_11") (pintype "passive"))
    )
    (net (code "108") (name "Net-(10G-KL)") (class "Default")
      (node (ref "10") (pin "4") (pinfunction "KL_4") (pintype "passive"))
      (node (ref "D53") (pin "2") (pinfunction "-_2") (pintype "passive"))
      (node (ref "LED27") (pin "K") (pinfunction "C_K") (pintype "passive"))
      (node (ref "TP106") (pin "TP") (pinfunction "PP_TP") (pintype "input"))
      (node (ref "X13") (pin "10") (pinfunction "10_10") (pintype "passive"))
    )
    (net (code "109") (name "Net-(10H-KL)") (class "Default")
      (node (ref "10") (pin "5") (pinfunction "KL_5") (pintype "passive"))
      (node (ref "D52") (pin "2") (pinfunction "-_2") (pintype "passive"))
      (node (ref "LED28") (pin "K") (pinfunction "C_K") (pintype "passive"))
      (node (ref "TP107") (pin "TP") (pinfunction "PP_TP") (pintype "input"))
      (node (ref "X13") (pin "9") (pinfunction "9_9") (pintype "passive"))
    )
    (net (code "110") (name "Net-(10I-KL)") (class "Default")
      (node (ref "10") (pin "6") (pinfunction "KL_6") (pintype "passive"))
      (node (ref "JP22") (pin "2") (pinfunction "2_2") (pintype "passive"))
      (node (ref "TP108") (pin "TP") (pinfunction "PP_TP") (pintype "input"))
    )
    (net (code "111") (name "Net-(10J-KL)") (class "Default")
      (node (ref "10") (pin "7") (pinfunction "KL_7") (pintype "passive"))
      (node (ref "LED29") (pin "A") (pinfunction "A_A") (pintype "passive"))
      (node (ref "TP109") (pin "TP") (pinfunction "PP_TP") (pintype "input"))
      (node (ref "X13") (pin "8") (pinfunction "8_8") (pintype "passive"))
    )
    (net (code "112") (name "Net-(10K-KL)") (class "Default")
      (node (ref "10") (pin "8") (pinfunction "KL_8") (pintype "passive"))
      (node (ref "D56") (pin "2") (pinfunction "-_2") (pintype "passive"))
      (node (ref "LED30") (pin "K") (pinfunction "C_K") (pintype "passive"))
      (node (ref "TP110") (pin "TP") (pinfunction "PP_TP") (pintype "input"))
      (node (ref "X13") (pin "14") (pinfunction "14_14") (pintype "passive"))
    )
    (net (code "113") (name "Net-(10L-KL)") (class "Default")
      (node (ref "10") (pin "9") (pinfunction "KL_9") (pintype "passive"))
      (node (ref "D53") (pin "1") (pinfunction "+_1") (pintype "passive"))
      (node (ref "D54") (pin "1") (pinfunction "+_1") (pintype "passive"))
      (node (ref "JP23") (pin "1") (pinfunction "1_1") (pintype "passive"))
      (node (ref "JP24") (pin "2") (pinfunction "2_2") (pintype "passive"))
      (node (ref "TP111") (pin "TP") (pinfunction "PP_TP") (pintype "input"))
    )
    (net (code "114") (name "Net-(11A-KL)") (class "Default")
      (node (ref "11") (pin "1") (pinfunction "KL_1") (pintype "passive"))
      (node (ref "TP116") (pin "TP") (pinfunction "PP_TP") (pintype "input"))
      (node (ref "X16") (pin "1") (pinfunction "1_1") (pintype "passive"))
    )
    (net (code "115") (name "Net-(11B-KL)") (class "Default")
      (node (ref "11") (pin "10") (pinfunction "KL_10") (pintype "passive"))
      (node (ref "D62") (pin "2") (pinfunction "-_2") (pintype "passive"))
      (node (ref "D63") (pin "2") (pinfunction "-_2") (pintype "passive"))
      (node (ref "JP30") (pin "1") (pinfunction "1_1") (pintype "passive"))
      (node (ref "SJ6") (pin "1") (pinfunction "1_1") (pintype "passive"))
      (node (ref "TP125") (pin "TP") (pinfunction "PP_TP") (pintype "input"))
    )
    (net (code "116") (name "Net-(11C-KL)") (class "Default")
      (node (ref "11") (pin "11") (pinfunction "KL_11") (pintype "passive"))
      (node (ref "D63") (pin "1") (pinfunction "+_1") (pintype "passive"))
      (node (ref "TP126") (pin "TP") (pinfunction "PP_TP") (pintype "input"))
      (node (ref "X16") (pin "19") (pinfunction "19_19") (pintype "passive"))
    )
    (net (code "117") (name "Net-(11E-KL)") (class "Default")
      (node (ref "11") (pin "2") (pinfunction "KL_2") (pintype "passive"))
      (node (ref "Q38") (pin "2") (pinfunction "C_2") (pintype "passive"))
      (node (ref "TP117") (pin "TP") (pinfunction "PP_TP") (pintype "input"))
    )
    (net (code "118") (name "Net-(11F-KL)") (class "Default")
      (node (ref "11") (pin "3") (pinfunction "KL_3") (pintype "passive"))
      (node (ref "IC59") (pin "11") (pinfunction "O6_11") (pintype "open_collector"))
      (node (ref "TP118") (pin "TP") (pinfunction "PP_TP") (pintype "input"))
    )
    (net (code "119") (name "Net-(11G-KL)") (class "Default")
      (node (ref "11") (pin "4") (pinfunction "KL_4") (pintype "passive"))
      (node (ref "IC59") (pin "10") (pinfunction "O7_10") (pintype "open_collector"))
      (node (ref "TP119") (pin "TP") (pinfunction "PP_TP") (pintype "input"))
    )
    (net (code "120") (name "Net-(11H-KL)") (class "Default")
      (node (ref "11") (pin "5") (pinfunction "KL_5") (pintype "passive"))
      (node (ref "IC59") (pin "12") (pinfunction "O5_12") (pintype "open_collector"))
      (node (ref "TP120") (pin "TP") (pinfunction "PP_TP") (pintype "input"))
    )
    (net (code "121") (name "Net-(11I-KL)") (class "Default")
      (node (ref "11") (pin "6") (pinfunction "KL_6") (pintype "passive"))
      (node (ref "IC59") (pin "13") (pinfunction "O4_13") (pintype "open_collector"))
      (node (ref "TP121") (pin "TP") (pinfunction "PP_TP") (pintype "input"))
    )
    (net (code "122") (name "Net-(11J-KL)") (class "Default")
      (node (ref "11") (pin "7") (pinfunction "KL_7") (pintype "passive"))
      (node (ref "IC59") (pin "14") (pinfunction "O3_14") (pintype "open_collector"))
      (node (ref "TP122") (pin "TP") (pinfunction "PP_TP") (pintype "input"))
    )
    (net (code "123") (name "Net-(11K-KL)") (class "Default")
      (node (ref "11") (pin "8") (pinfunction "KL_8") (pintype "passive"))
      (node (ref "Q42") (pin "3") (pinfunction "D_3") (pintype "passive"))
      (node (ref "TP123") (pin "TP") (pinfunction "PP_TP") (pintype "input"))
    )
    (net (code "124") (name "Net-(11L-KL)") (class "Default")
      (node (ref "11") (pin "9") (pinfunction "KL_9") (pintype "passive"))
      (node (ref "D62") (pin "1") (pinfunction "+_1") (pintype "passive"))
      (node (ref "TP124") (pin "TP") (pinfunction "PP_TP") (pintype "input"))
      (node (ref "X16") (pin "17") (pinfunction "17_17") (pintype "passive"))
    )
    (net (code "125") (name "Net-(12B-KL)") (class "Default")
      (node (ref "12") (pin "10") (pinfunction "KL_10") (pintype "passive"))
      (node (ref "TP135") (pin "TP") (pinfunction "PP_TP") (pintype "input"))
      (node (ref "X16") (pin "15") (pinfunction "15_15") (pintype "passive"))
    )
    (net (code "126") (name "Net-(12C-KL)") (class "Default")
      (node (ref "12") (pin "11") (pinfunction "KL_11") (pintype "passive"))
      (node (ref "IC59") (pin "16") (pinfunction "O1_16") (pintype "open_collector"))
      (node (ref "R268") (pin "1") (pinfunction "1_1") (pintype "passive"))
      (node (ref "R275") (pin "2") (pinfunction "2_2") (pintype "passive"))
      (node (ref "TP136") (pin "TP") (pinfunction "PP_TP") (pintype "input"))
    )
    (net (code "127") (name "Net-(12D-KL)") (class "Default")
      (node (ref "12") (pin "12") (pinfunction "KL_12") (pintype "passive"))
      (node (ref "R269") (pin "1") (pinfunction "1_1") (pintype "passive"))
      (node (ref "TP138") (pin "TP") (pinfunction "PP_TP") (pintype "input"))
    )
    (net (code "128") (name "Net-(12E-KL)") (class "Default")
      (node (ref "12") (pin "2") (pinfunction "KL_2") (pintype "passive"))
      (node (ref "D67") (pin "2") (pinfunction "-_2") (pintype "passive"))
      (node (ref "LED31") (pin "K") (pinfunction "C_K") (pintype "passive"))
      (node (ref "TP127") (pin "TP") (pinfunction "PP_TP") (pintype "input"))
      (node (ref "X16") (pin "12") (pinfunction "12_12") (pintype "passive"))
    )
    (net (code "129") (name "Net-(12F-KL)") (class "Default")
      (node (ref "12") (pin "3") (pinfunction "KL_3") (pintype "passive"))
      (node (ref "D66") (pin "2") (pinfunction "-_2") (pintype "passive"))
      (node (ref "LED32") (pin "K") (pinfunction "C_K") (pintype "passive"))
      (node (ref "TP128") (pin "TP") (pinfunction "PP_TP") (pintype "input"))
      (node (ref "X16") (pin "11") (pinfunction "11_11") (pintype "passive"))
    )
    (net (code "130") (name "Net-(12G-KL)") (class "Default")
      (node (ref "12") (pin "4") (pinfunction "KL_4") (pintype "passive"))
      (node (ref "D65") (pin "2") (pinfunction "-_2") (pintype "passive"))
      (node (ref "LED33") (pin "K") (pinfunction "C_K") (pintype "passive"))
      (node (ref "TP129") (pin "TP") (pinfunction "PP_TP") (pintype "input"))
      (node (ref "X16") (pin "10") (pinfunction "10_10") (pintype "passive"))
    )
    (net (code "131") (name "Net-(12H-KL)") (class "Default")
      (node (ref "12") (pin "5") (pinfunction "KL_5") (pintype "passive"))
      (node (ref "D64") (pin "2") (pinfunction "-_2") (pintype "passive"))
      (node (ref "LED34") (pin "K") (pinfunction "C_K") (pintype "passive"))
      (node (ref "TP130") (pin "TP") (pinfunction "PP_TP") (pintype "input"))
      (node (ref "X16") (pin "9") (pinfunction "9_9") (pintype "passive"))
    )
    (net (code "132") (name "Net-(12I-KL)") (class "Default")
      (node (ref "12") (pin "6") (pinfunction "KL_6") (pintype "passive"))
      (node (ref "JP27") (pin "2") (pinfunction "2_2") (pintype "passive"))
      (node (ref "TP131") (pin "TP") (pinfunction "PP_TP") (pintype "input"))
    )
    (net (code "133") (name "Net-(12J-KL)") (class "Default")
      (node (ref "12") (pin "7") (pinfunction "KL_7") (pintype "passive"))
      (node (ref "LED35") (pin "A") (pinfunction "A_A") (pintype "passive"))
      (node (ref "TP132") (pin "TP") (pinfunction "PP_TP") (pintype "input"))
      (node (ref "X16") (pin "8") (pinfunction "8_8") (pintype "passive"))
    )
    (net (code "134") (name "Net-(12K-KL)") (class "Default")
      (node (ref "12") (pin "8") (pinfunction "KL_8") (pintype "passive"))
      (node (ref "D68") (pin "2") (pinfunction "-_2") (pintype "passive"))
      (node (ref "LED36") (pin "K") (pinfunction "C_K") (pintype "passive"))
      (node (ref "TP133") (pin "TP") (pinfunction "PP_TP") (pintype "input"))
      (node (ref "X16") (pin "14") (pinfunction "14_14") (pintype "passive"))
    )
    (net (code "135") (name "Net-(12L-KL)") (class "Default")
      (node (ref "12") (pin "9") (pinfunction "KL_9") (pintype "passive"))
      (node (ref "D65") (pin "1") (pinfunction "+_1") (pintype "passive"))
      (node (ref "D66") (pin "1") (pinfunction "+_1") (pintype "passive"))
      (node (ref "JP28") (pin "1") (pinfunction "1_1") (pintype "passive"))
      (node (ref "JP29") (pin "2") (pinfunction "2_2") (pintype "passive"))
      (node (ref "TP134") (pin "TP") (pinfunction "PP_TP") (pintype "input"))
    )
    (net (code "136") (name "Net-(13A-KL)") (class "Default")
      (node (ref "13") (pin "1") (pinfunction "KL_1") (pintype "passive"))
      (node (ref "TP139") (pin "TP") (pinfunction "PP_TP") (pintype "input"))
      (node (ref "X19") (pin "1") (pinfunction "1_1") (pintype "passive"))
    )
    (net (code "137") (name "Net-(13B-KL)") (class "Default")
      (node (ref "13") (pin "10") (pinfunction "KL_10") (pintype "passive"))
      (node (ref "D74") (pin "2") (pinfunction "-_2") (pintype "passive"))
      (node (ref "D75") (pin "2") (pinfunction "-_2") (pintype "passive"))
      (node (ref "JP35") (pin "1") (pinfunction "1_1") (pintype "passive"))
      (node (ref "SJ7") (pin "1") (pinfunction "1_1") (pintype "passive"))
      (node (ref "TP148") (pin "TP") (pinfunction "PP_TP") (pintype "input"))
    )
    (net (code "138") (name "Net-(13C-KL)") (class "Default")
      (node (ref "13") (pin "11") (pinfunction "KL_11") (pintype "passive"))
      (node (ref "D75") (pin "1") (pinfunction "+_1") (pintype "passive"))
      (node (ref "TP149") (pin "TP") (pinfunction "PP_TP") (pintype "input"))
      (node (ref "X19") (pin "19") (pinfunction "19_19") (pintype "passive"))
    )
    (net (code "139") (name "Net-(13E-KL)") (class "Default")
      (node (ref "13") (pin "2") (pinfunction "KL_2") (pintype "passive"))
      (node (ref "Q45") (pin "2") (pinfunction "C_2") (pintype "passive"))
      (node (ref "TP140") (pin "TP") (pinfunction "PP_TP") (pintype "input"))
    )
    (net (code "140") (name "Net-(13F-KL)") (class "Default")
      (node (ref "13") (pin "3") (pinfunction "KL_3") (pintype "passive"))
      (node (ref "IC70") (pin "11") (pinfunction "O6_11") (pintype "open_collector"))
      (node (ref "TP141") (pin "TP") (pinfunction "PP_TP") (pintype "input"))
    )
    (net (code "141") (name "Net-(13G-KL)") (class "Default")
      (node (ref "13") (pin "4") (pinfunction "KL_4") (pintype "passive"))
      (node (ref "IC70") (pin "10") (pinfunction "O7_10") (pintype "open_collector"))
      (node (ref "TP142") (pin "TP") (pinfunction "PP_TP") (pintype "input"))
    )
    (net (code "142") (name "Net-(13H-KL)") (class "Default")
      (node (ref "13") (pin "5") (pinfunction "KL_5") (pintype "passive"))
      (node (ref "IC70") (pin "12") (pinfunction "O5_12") (pintype "open_collector"))
      (node (ref "TP143") (pin "TP") (pinfunction "PP_TP") (pintype "input"))
    )
    (net (code "143") (name "Net-(13I-KL)") (class "Default")
      (node (ref "13") (pin "6") (pinfunction "KL_6") (pintype "passive"))
      (node (ref "IC70") (pin "13") (pinfunction "O4_13") (pintype "open_collector"))
      (node (ref "TP144") (pin "TP") (pinfunction "PP_TP") (pintype "input"))
    )
    (net (code "144") (name "Net-(13J-KL)") (class "Default")
      (node (ref "13") (pin "7") (pinfunction "KL_7") (pintype "passive"))
      (node (ref "IC70") (pin "14") (pinfunction "O3_14") (pintype "open_collector"))
      (node (ref "TP145") (pin "TP") (pinfunction "PP_TP") (pintype "input"))
    )
    (net (code "145") (name "Net-(13K-KL)") (class "Default")
      (node (ref "13") (pin "8") (pinfunction "KL_8") (pintype "passive"))
      (node (ref "Q49") (pin "3") (pinfunction "D_3") (pintype "passive"))
      (node (ref "TP146") (pin "TP") (pinfunction "PP_TP") (pintype "input"))
    )
    (net (code "146") (name "Net-(13L-KL)") (class "Default")
      (node (ref "13") (pin "9") (pinfunction "KL_9") (pintype "passive"))
      (node (ref "D74") (pin "1") (pinfunction "+_1") (pintype "passive"))
      (node (ref "TP147") (pin "TP") (pinfunction "PP_TP") (pintype "input"))
      (node (ref "X19") (pin "17") (pinfunction "17_17") (pintype "passive"))
    )
    (net (code "147") (name "Net-(14B-KL)") (class "Default")
      (node (ref "14") (pin "10") (pinfunction "KL_10") (pintype "passive"))
      (node (ref "TP158") (pin "TP") (pinfunction "PP_TP") (pintype "input"))
      (node (ref "X19") (pin "15") (pinfunction "15_15") (pintype "passive"))
    )
    (net (code "148") (name "Net-(14C-KL)") (class "Default")
      (node (ref "14") (pin "11") (pinfunction "KL_11") (pintype "passive"))
      (node (ref "IC70") (pin "16") (pinfunction "O1_16") (pintype "open_collector"))
      (node (ref "R314") (pin "1") (pinfunction "1_1") (pintype "passive"))
      (node (ref "R321") (pin "2") (pinfunction "2_2") (pintype "passive"))
      (node (ref "TP159") (pin "TP") (pinfunction "PP_TP") (pintype "input"))
    )
    (net (code "149") (name "Net-(14D-KL)") (class "Default")
      (node (ref "14") (pin "12") (pinfunction "KL_12") (pintype "passive"))
      (node (ref "R315") (pin "1") (pinfunction "1_1") (pintype "passive"))
      (node (ref "TP161") (pin "TP") (pinfunction "PP_TP") (pintype "input"))
    )
    (net (code "150") (name "Net-(14E-KL)") (class "Default")
      (node (ref "14") (pin "2") (pinfunction "KL_2") (pintype "passive"))
      (node (ref "D79") (pin "2") (pinfunction "-_2") (pintype "passive"))
      (node (ref "LED37") (pin "K") (pinfunction "C_K") (pintype "passive"))
      (node (ref "TP150") (pin "TP") (pinfunction "PP_TP") (pintype "input"))
      (node (ref "X19") (pin "12") (pinfunction "12_12") (pintype "passive"))
    )
    (net (code "151") (name "Net-(14F-KL)") (class "Default")
      (node (ref "14") (pin "3") (pinfunction "KL_3") (pintype "passive"))
      (node (ref "D78") (pin "2") (pinfunction "-_2") (pintype "passive"))
      (node (ref "LED38") (pin "K") (pinfunction "C_K") (pintype "passive"))
      (node (ref "TP151") (pin "TP") (pinfunction "PP_TP") (pintype "input"))
      (node (ref "X19") (pin "11") (pinfunction "11_11") (pintype "passive"))
    )
    (net (code "152") (name "Net-(14G-KL)") (class "Default")
      (node (ref "14") (pin "4") (pinfunction "KL_4") (pintype "passive"))
      (node (ref "D77") (pin "2") (pinfunction "-_2") (pintype "passive"))
      (node (ref "LED39") (pin "K") (pinfunction "C_K") (pintype "passive"))
      (node (ref "TP152") (pin "TP") (pinfunction "PP_TP") (pintype "input"))
      (node (ref "X19") (pin "10") (pinfunction "10_10") (pintype "passive"))
    )
    (net (code "153") (name "Net-(14H-KL)") (class "Default")
      (node (ref "14") (pin "5") (pinfunction "KL_5") (pintype "passive"))
      (node (ref "D76") (pin "2") (pinfunction "-_2") (pintype "passive"))
      (node (ref "LED40") (pin "K") (pinfunction "C_K") (pintype "passive"))
      (node (ref "TP153") (pin "TP") (pinfunction "PP_TP") (pintype "input"))
      (node (ref "X19") (pin "9") (pinfunction "9_9") (pintype "passive"))
    )
    (net (code "154") (name "Net-(14I-KL)") (class "Default")
      (node (ref "14") (pin "6") (pinfunction "KL_6") (pintype "passive"))
      (node (ref "JP32") (pin "2") (pinfunction "2_2") (pintype "passive"))
      (node (ref "TP154") (pin "TP") (pinfunction "PP_TP") (pintype "input"))
    )
    (net (code "155") (name "Net-(14J-KL)") (class "Default")
      (node (ref "14") (pin "7") (pinfunction "KL_7") (pintype "passive"))
      (node (ref "LED41") (pin "A") (pinfunction "A_A") (pintype "passive"))
      (node (ref "TP155") (pin "TP") (pinfunction "PP_TP") (pintype "input"))
      (node (ref "X19") (pin "8") (pinfunction "8_8") (pintype "passive"))
    )
    (net (code "156") (name "Net-(14K-KL)") (class "Default")
      (node (ref "14") (pin "8") (pinfunction "KL_8") (pintype "passive"))
      (node (ref "D80") (pin "2") (pinfunction "-_2") (pintype "passive"))
      (node (ref "LED42") (pin "K") (pinfunction "C_K") (pintype "passive"))
      (node (ref "TP156") (pin "TP") (pinfunction "PP_TP") (pintype "input"))
      (node (ref "X19") (pin "14") (pinfunction "14_14") (pintype "passive"))
    )
    (net (code "157") (name "Net-(14L-KL)") (class "Default")
      (node (ref "14") (pin "9") (pinfunction "KL_9") (pintype "passive"))
      (node (ref "D77") (pin "1") (pinfunction "+_1") (pintype "passive"))
      (node (ref "D78") (pin "1") (pinfunction "+_1") (pintype "passive"))
      (node (ref "JP33") (pin "1") (pinfunction "1_1") (pintype "passive"))
      (node (ref "JP34") (pin "2") (pinfunction "2_2") (pintype "passive"))
      (node (ref "TP157") (pin "TP") (pinfunction "PP_TP") (pintype "input"))
    )
    (net (code "158") (name "Net-(15A-KL)") (class "Default")
      (node (ref "15") (pin "1") (pinfunction "KL_1") (pintype "passive"))
      (node (ref "TP162") (pin "TP") (pinfunction "PP_TP") (pintype "input"))
      (node (ref "X22") (pin "1") (pinfunction "1_1") (pintype "passive"))
    )
    (net (code "159") (name "Net-(15B-KL)") (class "Default")
      (node (ref "15") (pin "10") (pinfunction "KL_10") (pintype "passive"))
      (node (ref "D86") (pin "2") (pinfunction "-_2") (pintype "passive"))
      (node (ref "D87") (pin "2") (pinfunction "-_2") (pintype "passive"))
      (node (ref "JP40") (pin "1") (pinfunction "1_1") (pintype "passive"))
      (node (ref "SJ8") (pin "1") (pinfunction "1_1") (pintype "passive"))
      (node (ref "TP171") (pin "TP") (pinfunction "PP_TP") (pintype "input"))
    )
    (net (code "160") (name "Net-(15C-KL)") (class "Default")
      (node (ref "15") (pin "11") (pinfunction "KL_11") (pintype "passive"))
      (node (ref "D87") (pin "1") (pinfunction "+_1") (pintype "passive"))
      (node (ref "TP172") (pin "TP") (pinfunction "PP_TP") (pintype "input"))
      (node (ref "X22") (pin "19") (pinfunction "19_19") (pintype "passive"))
    )
    (net (code "161") (name "Net-(15E-KL)") (class "Default")
      (node (ref "15") (pin "2") (pinfunction "KL_2") (pintype "passive"))
      (node (ref "Q52") (pin "2") (pinfunction "C_2") (pintype "passive"))
      (node (ref "TP163") (pin "TP") (pinfunction "PP_TP") (pintype "input"))
    )
    (net (code "162") (name "Net-(15F-KL)") (class "Default")
      (node (ref "15") (pin "3") (pinfunction "KL_3") (pintype "passive"))
      (node (ref "IC81") (pin "11") (pinfunction "O6_11") (pintype "open_collector"))
      (node (ref "TP164") (pin "TP") (pinfunction "PP_TP") (pintype "input"))
    )
    (net (code "163") (name "Net-(15G-KL)") (class "Default")
      (node (ref "15") (pin "4") (pinfunction "KL_4") (pintype "passive"))
      (node (ref "IC81") (pin "10") (pinfunction "O7_10") (pintype "open_collector"))
      (node (ref "TP165") (pin "TP") (pinfunction "PP_TP") (pintype "input"))
    )
    (net (code "164") (name "Net-(15H-KL)") (class "Default")
      (node (ref "15") (pin "5") (pinfunction "KL_5") (pintype "passive"))
      (node (ref "IC81") (pin "12") (pinfunction "O5_12") (pintype "open_collector"))
      (node (ref "TP166") (pin "TP") (pinfunction "PP_TP") (pintype "input"))
    )
    (net (code "165") (name "Net-(15I-KL)") (class "Default")
      (node (ref "15") (pin "6") (pinfunction "KL_6") (pintype "passive"))
      (node (ref "IC81") (pin "13") (pinfunction "O4_13") (pintype "open_collector"))
      (node (ref "TP167") (pin "TP") (pinfunction "PP_TP") (pintype "input"))
    )
    (net (code "166") (name "Net-(15J-KL)") (class "Default")
      (node (ref "15") (pin "7") (pinfunction "KL_7") (pintype "passive"))
      (node (ref "IC81") (pin "14") (pinfunction "O3_14") (pintype "open_collector"))
      (node (ref "TP168") (pin "TP") (pinfunction "PP_TP") (pintype "input"))
    )
    (net (code "167") (name "Net-(15K-KL)") (class "Default")
      (node (ref "15") (pin "8") (pinfunction "KL_8") (pintype "passive"))
      (node (ref "Q56") (pin "3") (pinfunction "D_3") (pintype "passive"))
      (node (ref "TP169") (pin "TP") (pinfunction "PP_TP") (pintype "input"))
    )
    (net (code "168") (name "Net-(15L-KL)") (class "Default")
      (node (ref "15") (pin "9") (pinfunction "KL_9") (pintype "passive"))
      (node (ref "D86") (pin "1") (pinfunction "+_1") (pintype "passive"))
      (node (ref "TP170") (pin "TP") (pinfunction "PP_TP") (pintype "input"))
      (node (ref "X22") (pin "17") (pinfunction "17_17") (pintype "passive"))
    )
    (net (code "169") (name "Net-(16B-KL)") (class "Default")
      (node (ref "16") (pin "10") (pinfunction "KL_10") (pintype "passive"))
      (node (ref "TP181") (pin "TP") (pinfunction "PP_TP") (pintype "input"))
      (node (ref "X22") (pin "15") (pinfunction "15_15") (pintype "passive"))
    )
    (net (code "170") (name "Net-(16C-KL)") (class "Default")
      (node (ref "16") (pin "11") (pinfunction "KL_11") (pintype "passive"))
      (node (ref "IC81") (pin "16") (pinfunction "O1_16") (pintype "open_collector"))
      (node (ref "R360") (pin "1") (pinfunction "1_1") (pintype "passive"))
      (node (ref "R367") (pin "2") (pinfunction "2_2") (pintype "passive"))
      (node (ref "TP182") (pin "TP") (pinfunction "PP_TP") (pintype "input"))
    )
    (net (code "171") (name "Net-(16D-KL)") (class "Default")
      (node (ref "16") (pin "12") (pinfunction "KL_12") (pintype "passive"))
      (node (ref "R361") (pin "1") (pinfunction "1_1") (pintype "passive"))
      (node (ref "TP184") (pin "TP") (pinfunction "PP_TP") (pintype "input"))
    )
    (net (code "172") (name "Net-(16E-KL)") (class "Default")
      (node (ref "16") (pin "2") (pinfunction "KL_2") (pintype "passive"))
      (node (ref "D91") (pin "2") (pinfunction "-_2") (pintype "passive"))
      (node (ref "LED43") (pin "K") (pinfunction "C_K") (pintype "passive"))
      (node (ref "TP173") (pin "TP") (pinfunction "PP_TP") (pintype "input"))
      (node (ref "X22") (pin "12") (pinfunction "12_12") (pintype "passive"))
    )
    (net (code "173") (name "Net-(16F-KL)") (class "Default")
      (node (ref "16") (pin "3") (pinfunction "KL_3") (pintype "passive"))
      (node (ref "D90") (pin "2") (pinfunction "-_2") (pintype "passive"))
      (node (ref "LED44") (pin "K") (pinfunction "C_K") (pintype "passive"))
      (node (ref "TP174") (pin "TP") (pinfunction "PP_TP") (pintype "input"))
      (node (ref "X22") (pin "11") (pinfunction "11_11") (pintype "passive"))
    )
    (net (code "174") (name "Net-(16G-KL)") (class "Default")
      (node (ref "16") (pin "4") (pinfunction "KL_4") (pintype "passive"))
      (node (ref "D89") (pin "2") (pinfunction "-_2") (pintype "passive"))
      (node (ref "LED45") (pin "K") (pinfunction "C_K") (pintype "passive"))
      (node (ref "TP175") (pin "TP") (pinfunction "PP_TP") (pintype "input"))
      (node (ref "X22") (pin "10") (pinfunction "10_10") (pintype "passive"))
    )
    (net (code "175") (name "Net-(16H-KL)") (class "Default")
      (node (ref "16") (pin "5") (pinfunction "KL_5") (pintype "passive"))
      (node (ref "D88") (pin "2") (pinfunction "-_2") (pintype "passive"))
      (node (ref "LED46") (pin "K") (pinfunction "C_K") (pintype "passive"))
      (node (ref "TP176") (pin "TP") (pinfunction "PP_TP") (pintype "input"))
      (node (ref "X22") (pin "9") (pinfunction "9_9") (pintype "passive"))
    )
    (net (code "176") (name "Net-(16I-KL)") (class "Default")
      (node (ref "16") (pin "6") (pinfunction "KL_6") (pintype "passive"))
      (node (ref "JP37") (pin "2") (pinfunction "2_2") (pintype "passive"))
      (node (ref "TP177") (pin "TP") (pinfunction "PP_TP") (pintype "input"))
    )
    (net (code "177") (name "Net-(16J-KL)") (class "Default")
      (node (ref "16") (pin "7") (pinfunction "KL_7") (pintype "passive"))
      (node (ref "LED47") (pin "A") (pinfunction "A_A") (pintype "passive"))
      (node (ref "TP178") (pin "TP") (pinfunction "PP_TP") (pintype "input"))
      (node (ref "X22") (pin "8") (pinfunction "8_8") (pintype "passive"))
    )
    (net (code "178") (name "Net-(16K-KL)") (class "Default")
      (node (ref "16") (pin "8") (pinfunction "KL_8") (pintype "passive"))
      (node (ref "D92") (pin "2") (pinfunction "-_2") (pintype "passive"))
      (node (ref "LED48") (pin "K") (pinfunction "C_K") (pintype "passive"))
      (node (ref "TP179") (pin "TP") (pinfunction "PP_TP") (pintype "input"))
      (node (ref "X22") (pin "14") (pinfunction "14_14") (pintype "passive"))
    )
    (net (code "179") (name "Net-(16L-KL)") (class "Default")
      (node (ref "16") (pin "9") (pinfunction "KL_9") (pintype "passive"))
      (node (ref "D89") (pin "1") (pinfunction "+_1") (pintype "passive"))
      (node (ref "D90") (pin "1") (pinfunction "+_1") (pintype "passive"))
      (node (ref "JP38") (pin "1") (pinfunction "1_1") (pintype "passive"))
      (node (ref "JP39") (pin "2") (pinfunction "2_2") (pintype "passive"))
      (node (ref "TP180") (pin "TP") (pinfunction "PP_TP") (pintype "input"))
    )
    (net (code "180") (name "Net-(17A-KL)") (class "Default")
      (node (ref "17") (pin "1") (pinfunction "KL_1") (pintype "passive"))
      (node (ref "TP185") (pin "TP") (pinfunction "PP_TP") (pintype "input"))
      (node (ref "X25") (pin "1") (pinfunction "1_1") (pintype "passive"))
    )
    (net (code "181") (name "Net-(17B-KL)") (class "Default")
      (node (ref "17") (pin "10") (pinfunction "KL_10") (pintype "passive"))
      (node (ref "D98") (pin "2") (pinfunction "-_2") (pintype "passive"))
      (node (ref "D99") (pin "2") (pinfunction "-_2") (pintype "passive"))
      (node (ref "JP45") (pin "1") (pinfunction "1_1") (pintype "passive"))
      (node (ref "SJ9") (pin "1") (pinfunction "1_1") (pintype "passive"))
      (node (ref "TP194") (pin "TP") (pinfunction "PP_TP") (pintype "input"))
    )
    (net (code "182") (name "Net-(17C-KL)") (class "Default")
      (node (ref "17") (pin "11") (pinfunction "KL_11") (pintype "passive"))
      (node (ref "D99") (pin "1") (pinfunction "+_1") (pintype "passive"))
      (node (ref "TP195") (pin "TP") (pinfunction "PP_TP") (pintype "input"))
      (node (ref "X25") (pin "19") (pinfunction "19_19") (pintype "passive"))
    )
    (net (code "183") (name "Net-(17E-KL)") (class "Default")
      (node (ref "17") (pin "2") (pinfunction "KL_2") (pintype "passive"))
      (node (ref "Q59") (pin "2") (pinfunction "C_2") (pintype "passive"))
      (node (ref "TP186") (pin "TP") (pinfunction "PP_TP") (pintype "input"))
    )
    (net (code "184") (name "Net-(17F-KL)") (class "Default")
      (node (ref "17") (pin "3") (pinfunction "KL_3") (pintype "passive"))
      (node (ref "IC92") (pin "11") (pinfunction "O6_11") (pintype "open_collector"))
      (node (ref "TP187") (pin "TP") (pinfunction "PP_TP") (pintype "input"))
    )
    (net (code "185") (name "Net-(17G-KL)") (class "Default")
      (node (ref "17") (pin "4") (pinfunction "KL_4") (pintype "passive"))
      (node (ref "IC92") (pin "10") (pinfunction "O7_10") (pintype "open_collector"))
      (node (ref "TP188") (pin "TP") (pinfunction "PP_TP") (pintype "input"))
    )
    (net (code "186") (name "Net-(17H-KL)") (class "Default")
      (node (ref "17") (pin "5") (pinfunction "KL_5") (pintype "passive"))
      (node (ref "IC92") (pin "12") (pinfunction "O5_12") (pintype "open_collector"))
      (node (ref "TP189") (pin "TP") (pinfunction "PP_TP") (pintype "input"))
    )
    (net (code "187") (name "Net-(17I-KL)") (class "Default")
      (node (ref "17") (pin "6") (pinfunction "KL_6") (pintype "passive"))
      (node (ref "IC92") (pin "13") (pinfunction "O4_13") (pintype "open_collector"))
      (node (ref "TP190") (pin "TP") (pinfunction "PP_TP") (pintype "input"))
    )
    (net (code "188") (name "Net-(17J-KL)") (class "Default")
      (node (ref "17") (pin "7") (pinfunction "KL_7") (pintype "passive"))
      (node (ref "IC92") (pin "14") (pinfunction "O3_14") (pintype "open_collector"))
      (node (ref "TP191") (pin "TP") (pinfunction "PP_TP") (pintype "input"))
    )
    (net (code "189") (name "Net-(17K-KL)") (class "Default")
      (node (ref "17") (pin "8") (pinfunction "KL_8") (pintype "passive"))
      (node (ref "Q63") (pin "3") (pinfunction "D_3") (pintype "passive"))
      (node (ref "TP192") (pin "TP") (pinfunction "PP_TP") (pintype "input"))
    )
    (net (code "190") (name "Net-(17L-KL)") (class "Default")
      (node (ref "17") (pin "9") (pinfunction "KL_9") (pintype "passive"))
      (node (ref "D98") (pin "1") (pinfunction "+_1") (pintype "passive"))
      (node (ref "TP193") (pin "TP") (pinfunction "PP_TP") (pintype "input"))
      (node (ref "X25") (pin "17") (pinfunction "17_17") (pintype "passive"))
    )
    (net (code "191") (name "Net-(18B-KL)") (class "Default")
      (node (ref "18") (pin "10") (pinfunction "KL_10") (pintype "passive"))
      (node (ref "TP204") (pin "TP") (pinfunction "PP_TP") (pintype "input"))
      (node (ref "X25") (pin "15") (pinfunction "15_15") (pintype "passive"))
    )
    (net (code "192") (name "Net-(18C-KL)") (class "Default")
      (node (ref "18") (pin "11") (pinfunction "KL_11") (pintype "passive"))
      (node (ref "IC92") (pin "16") (pinfunction "O1_16") (pintype "open_collector"))
      (node (ref "R406") (pin "1") (pinfunction "1_1") (pintype "passive"))
      (node (ref "R413") (pin "2") (pinfunction "2_2") (pintype "passive"))
      (node (ref "TP205") (pin "TP") (pinfunction "PP_TP") (pintype "input"))
    )
    (net (code "193") (name "Net-(18D-KL)") (class "Default")
      (node (ref "18") (pin "12") (pinfunction "KL_12") (pintype "passive"))
      (node (ref "R407") (pin "1") (pinfunction "1_1") (pintype "passive"))
      (node (ref "TP207") (pin "TP") (pinfunction "PP_TP") (pintype "input"))
    )
    (net (code "194") (name "Net-(18E-KL)") (class "Default")
      (node (ref "18") (pin "2") (pinfunction "KL_2") (pintype "passive"))
      (node (ref "D103") (pin "2") (pinfunction "-_2") (pintype "passive"))
      (node (ref "LED49") (pin "K") (pinfunction "C_K") (pintype "passive"))
      (node (ref "TP196") (pin "TP") (pinfunction "PP_TP") (pintype "input"))
      (node (ref "X25") (pin "12") (pinfunction "12_12") (pintype "passive"))
    )
    (net (code "195") (name "Net-(18F-KL)") (class "Default")
      (node (ref "18") (pin "3") (pinfunction "KL_3") (pintype "passive"))
      (node (ref "D102") (pin "2") (pinfunction "-_2") (pintype "passive"))
      (node (ref "LED50") (pin "K") (pinfunction "C_K") (pintype "passive"))
      (node (ref "TP197") (pin "TP") (pinfunction "PP_TP") (pintype "input"))
      (node (ref "X25") (pin "11") (pinfunction "11_11") (pintype "passive"))
    )
    (net (code "196") (name "Net-(18G-KL)") (class "Default")
      (node (ref "18") (pin "4") (pinfunction "KL_4") (pintype "passive"))
      (node (ref "D101") (pin "2") (pinfunction "-_2") (pintype "passive"))
      (node (ref "LED51") (pin "K") (pinfunction "C_K") (pintype "passive"))
      (node (ref "TP198") (pin "TP") (pinfunction "PP_TP") (pintype "input"))
      (node (ref "X25") (pin "10") (pinfunction "10_10") (pintype "passive"))
    )
    (net (code "197") (name "Net-(18H-KL)") (class "Default")
      (node (ref "18") (pin "5") (pinfunction "KL_5") (pintype "passive"))
      (node (ref "D100") (pin "2") (pinfunction "-_2") (pintype "passive"))
      (node (ref "LED52") (pin "K") (pinfunction "C_K") (pintype "passive"))
      (node (ref "TP199") (pin "TP") (pinfunction "PP_TP") (pintype "input"))
      (node (ref "X25") (pin "9") (pinfunction "9_9") (pintype "passive"))
    )
    (net (code "198") (name "Net-(18I-KL)") (class "Default")
      (node (ref "18") (pin "6") (pinfunction "KL_6") (pintype "passive"))
      (node (ref "JP42") (pin "2") (pinfunction "2_2") (pintype "passive"))
      (node (ref "TP200") (pin "TP") (pinfunction "PP_TP") (pintype "input"))
    )
    (net (code "199") (name "Net-(18J-KL)") (class "Default")
      (node (ref "18") (pin "7") (pinfunction "KL_7") (pintype "passive"))
      (node (ref "LED53") (pin "A") (pinfunction "A_A") (pintype "passive"))
      (node (ref "TP201") (pin "TP") (pinfunction "PP_TP") (pintype "input"))
      (node (ref "X25") (pin "8") (pinfunction "8_8") (pintype "passive"))
    )
    (net (code "200") (name "Net-(18K-KL)") (class "Default")
      (node (ref "18") (pin "8") (pinfunction "KL_8") (pintype "passive"))
      (node (ref "D104") (pin "2") (pinfunction "-_2") (pintype "passive"))
      (node (ref "LED54") (pin "K") (pinfunction "C_K") (pintype "passive"))
      (node (ref "TP202") (pin "TP") (pinfunction "PP_TP") (pintype "input"))
      (node (ref "X25") (pin "14") (pinfunction "14_14") (pintype "passive"))
    )
    (net (code "201") (name "Net-(18L-KL)") (class "Default")
      (node (ref "18") (pin "9") (pinfunction "KL_9") (pintype "passive"))
      (node (ref "D101") (pin "1") (pinfunction "+_1") (pintype "passive"))
      (node (ref "D102") (pin "1") (pinfunction "+_1") (pintype "passive"))
      (node (ref "JP43") (pin "1") (pinfunction "1_1") (pintype "passive"))
      (node (ref "JP44") (pin "2") (pinfunction "2_2") (pintype "passive"))
      (node (ref "TP203") (pin "TP") (pinfunction "PP_TP") (pintype "input"))
    )
    (net (code "202") (name "Net-(19A-KL)") (class "Default")
      (node (ref "19") (pin "1") (pinfunction "KL_1") (pintype "passive"))
      (node (ref "TP208") (pin "TP") (pinfunction "PP_TP") (pintype "input"))
      (node (ref "X28") (pin "1") (pinfunction "1_1") (pintype "passive"))
    )
    (net (code "203") (name "Net-(19B-KL)") (class "Default")
      (node (ref "19") (pin "10") (pinfunction "KL_10") (pintype "passive"))
      (node (ref "D110") (pin "2") (pinfunction "-_2") (pintype "passive"))
      (node (ref "D111") (pin "2") (pinfunction "-_2") (pintype "passive"))
      (node (ref "JP50") (pin "1") (pinfunction "1_1") (pintype "passive"))
      (node (ref "SJ10") (pin "1") (pinfunction "1_1") (pintype "passive"))
      (node (ref "TP217") (pin "TP") (pinfunction "PP_TP") (pintype "input"))
    )
    (net (code "204") (name "Net-(19C-KL)") (class "Default")
      (node (ref "19") (pin "11") (pinfunction "KL_11") (pintype "passive"))
      (node (ref "D111") (pin "1") (pinfunction "+_1") (pintype "passive"))
      (node (ref "TP218") (pin "TP") (pinfunction "PP_TP") (pintype "input"))
      (node (ref "X28") (pin "19") (pinfunction "19_19") (pintype "passive"))
    )
    (net (code "205") (name "Net-(19E-KL)") (class "Default")
      (node (ref "19") (pin "2") (pinfunction "KL_2") (pintype "passive"))
      (node (ref "Q66") (pin "2") (pinfunction "C_2") (pintype "passive"))
      (node (ref "TP209") (pin "TP") (pinfunction "PP_TP") (pintype "input"))
    )
    (net (code "206") (name "Net-(19F-KL)") (class "Default")
      (node (ref "19") (pin "3") (pinfunction "KL_3") (pintype "passive"))
      (node (ref "IC103") (pin "11") (pinfunction "O6_11") (pintype "open_collector"))
      (node (ref "TP210") (pin "TP") (pinfunction "PP_TP") (pintype "input"))
    )
    (net (code "207") (name "Net-(19G-KL)") (class "Default")
      (node (ref "19") (pin "4") (pinfunction "KL_4") (pintype "passive"))
      (node (ref "IC103") (pin "10") (pinfunction "O7_10") (pintype "open_collector"))
      (node (ref "TP211") (pin "TP") (pinfunction "PP_TP") (pintype "input"))
    )
    (net (code "208") (name "Net-(19H-KL)") (class "Default")
      (node (ref "19") (pin "5") (pinfunction "KL_5") (pintype "passive"))
      (node (ref "IC103") (pin "12") (pinfunction "O5_12") (pintype "open_collector"))
      (node (ref "TP212") (pin "TP") (pinfunction "PP_TP") (pintype "input"))
    )
    (net (code "209") (name "Net-(19I-KL)") (class "Default")
      (node (ref "19") (pin "6") (pinfunction "KL_6") (pintype "passive"))
      (node (ref "IC103") (pin "13") (pinfunction "O4_13") (pintype "open_collector"))
      (node (ref "TP213") (pin "TP") (pinfunction "PP_TP") (pintype "input"))
    )
    (net (code "210") (name "Net-(19J-KL)") (class "Default")
      (node (ref "19") (pin "7") (pinfunction "KL_7") (pintype "passive"))
      (node (ref "IC103") (pin "14") (pinfunction "O3_14") (pintype "open_collector"))
      (node (ref "TP214") (pin "TP") (pinfunction "PP_TP") (pintype "input"))
    )
    (net (code "211") (name "Net-(19K-KL)") (class "Default")
      (node (ref "19") (pin "8") (pinfunction "KL_8") (pintype "passive"))
      (node (ref "Q70") (pin "3") (pinfunction "D_3") (pintype "passive"))
      (node (ref "TP215") (pin "TP") (pinfunction "PP_TP") (pintype "input"))
    )
    (net (code "212") (name "Net-(19L-KL)") (class "Default")
      (node (ref "19") (pin "9") (pinfunction "KL_9") (pintype "passive"))
      (node (ref "D110") (pin "1") (pinfunction "+_1") (pintype "passive"))
      (node (ref "TP216") (pin "TP") (pinfunction "PP_TP") (pintype "input"))
      (node (ref "X28") (pin "17") (pinfunction "17_17") (pintype "passive"))
    )
    (net (code "213") (name "Net-(20B-KL)") (class "Default")
      (node (ref "20") (pin "10") (pinfunction "KL_10") (pintype "passive"))
      (node (ref "TP227") (pin "TP") (pinfunction "PP_TP") (pintype "input"))
      (node (ref "X28") (pin "15") (pinfunction "15_15") (pintype "passive"))
    )
    (net (code "214") (name "Net-(20C-KL)") (class "Default")
      (node (ref "20") (pin "11") (pinfunction "KL_11") (pintype "passive"))
      (node (ref "IC103") (pin "16") (pinfunction "O1_16") (pintype "open_collector"))
      (node (ref "R452") (pin "1") (pinfunction "1_1") (pintype "passive"))
      (node (ref "R459") (pin "2") (pinfunction "2_2") (pintype "passive"))
      (node (ref "TP228") (pin "TP") (pinfunction "PP_TP") (pintype "input"))
    )
    (net (code "215") (name "Net-(20D-KL)") (class "Default")
      (node (ref "20") (pin "12") (pinfunction "KL_12") (pintype "passive"))
      (node (ref "R453") (pin "1") (pinfunction "1_1") (pintype "passive"))
      (node (ref "TP230") (pin "TP") (pinfunction "PP_TP") (pintype "input"))
    )
    (net (code "216") (name "Net-(20E-KL)") (class "Default")
      (node (ref "20") (pin "2") (pinfunction "KL_2") (pintype "passive"))
      (node (ref "D115") (pin "2") (pinfunction "-_2") (pintype "passive"))
      (node (ref "LED55") (pin "K") (pinfunction "C_K") (pintype "passive"))
      (node (ref "TP219") (pin "TP") (pinfunction "PP_TP") (pintype "input"))
      (node (ref "X28") (pin "12") (pinfunction "12_12") (pintype "passive"))
    )
    (net (code "217") (name "Net-(20F-KL)") (class "Default")
      (node (ref "20") (pin "3") (pinfunction "KL_3") (pintype "passive"))
      (node (ref "D114") (pin "2") (pinfunction "-_2") (pintype "passive"))
      (node (ref "LED56") (pin "K") (pinfunction "C_K") (pintype "passive"))
      (node (ref "TP220") (pin "TP") (pinfunction "PP_TP") (pintype "input"))
      (node (ref "X28") (pin "11") (pinfunction "11_11") (pintype "passive"))
    )
    (net (code "218") (name "Net-(20G-KL)") (class "Default")
      (node (ref "20") (pin "4") (pinfunction "KL_4") (pintype "passive"))
      (node (ref "D113") (pin "2") (pinfunction "-_2") (pintype "passive"))
      (node (ref "LED57") (pin "K") (pinfunction "C_K") (pintype "passive"))
      (node (ref "TP221") (pin "TP") (pinfunction "PP_TP") (pintype "input"))
      (node (ref "X28") (pin "10") (pinfunction "10_10") (pintype "passive"))
    )
    (net (code "219") (name "Net-(20H-KL)") (class "Default")
      (node (ref "20") (pin "5") (pinfunction "KL_5") (pintype "passive"))
      (node (ref "D112") (pin "2") (pinfunction "-_2") (pintype "passive"))
      (node (ref "LED58") (pin "K") (pinfunction "C_K") (pintype "passive"))
      (node (ref "TP222") (pin "TP") (pinfunction "PP_TP") (pintype "input"))
      (node (ref "X28") (pin "9") (pinfunction "9_9") (pintype "passive"))
    )
    (net (code "220") (name "Net-(20I-KL)") (class "Default")
      (node (ref "20") (pin "6") (pinfunction "KL_6") (pintype "passive"))
      (node (ref "JP47") (pin "2") (pinfunction "2_2") (pintype "passive"))
      (node (ref "TP223") (pin "TP") (pinfunction "PP_TP") (pintype "input"))
    )
    (net (code "221") (name "Net-(20J-KL)") (class "Default")
      (node (ref "20") (pin "7") (pinfunction "KL_7") (pintype "passive"))
      (node (ref "LED59") (pin "A") (pinfunction "A_A") (pintype "passive"))
      (node (ref "TP224") (pin "TP") (pinfunction "PP_TP") (pintype "input"))
      (node (ref "X28") (pin "8") (pinfunction "8_8") (pintype "passive"))
    )
    (net (code "222") (name "Net-(20K-KL)") (class "Default")
      (node (ref "20") (pin "8") (pinfunction "KL_8") (pintype "passive"))
      (node (ref "D116") (pin "2") (pinfunction "-_2") (pintype "passive"))
      (node (ref "LED60") (pin "K") (pinfunction "C_K") (pintype "passive"))
      (node (ref "TP225") (pin "TP") (pinfunction "PP_TP") (pintype "input"))
      (node (ref "X28") (pin "14") (pinfunction "14_14") (pintype "passive"))
    )
    (net (code "223") (name "Net-(20L-KL)") (class "Default")
      (node (ref "20") (pin "9") (pinfunction "KL_9") (pintype "passive"))
      (node (ref "D113") (pin "1") (pinfunction "+_1") (pintype "passive"))
      (node (ref "D114") (pin "1") (pinfunction "+_1") (pintype "passive"))
      (node (ref "JP48") (pin "1") (pinfunction "1_1") (pintype "passive"))
      (node (ref "JP49") (pin "2") (pinfunction "2_2") (pintype "passive"))
      (node (ref "TP226") (pin "TP") (pinfunction "PP_TP") (pintype "input"))
    )
    (net (code "224") (name "Net-(21A-KL)") (class "Default")
      (node (ref "21") (pin "1") (pinfunction "KL_1") (pintype "passive"))
      (node (ref "TP231") (pin "TP") (pinfunction "PP_TP") (pintype "input"))
      (node (ref "X31") (pin "1") (pinfunction "1_1") (pintype "passive"))
    )
    (net (code "225") (name "Net-(21B-KL)") (class "Default")
      (node (ref "21") (pin "10") (pinfunction "KL_10") (pintype "passive"))
      (node (ref "D122") (pin "2") (pinfunction "-_2") (pintype "passive"))
      (node (ref "D123") (pin "2") (pinfunction "-_2") (pintype "passive"))
      (node (ref "JP55") (pin "1") (pinfunction "1_1") (pintype "passive"))
      (node (ref "SJ11") (pin "1") (pinfunction "1_1") (pintype "passive"))
      (node (ref "TP240") (pin "TP") (pinfunction "PP_TP") (pintype "input"))
    )
    (net (code "226") (name "Net-(21C-KL)") (class "Default")
      (node (ref "21") (pin "11") (pinfunction "KL_11") (pintype "passive"))
      (node (ref "D123") (pin "1") (pinfunction "+_1") (pintype "passive"))
      (node (ref "TP241") (pin "TP") (pinfunction "PP_TP") (pintype "input"))
      (node (ref "X31") (pin "19") (pinfunction "19_19") (pintype "passive"))
    )
    (net (code "227") (name "Net-(21E-KL)") (class "Default")
      (node (ref "21") (pin "2") (pinfunction "KL_2") (pintype "passive"))
      (node (ref "Q73") (pin "2") (pinfunction "C_2") (pintype "passive"))
      (node (ref "TP232") (pin "TP") (pinfunction "PP_TP") (pintype "input"))
    )
    (net (code "228") (name "Net-(21F-KL)") (class "Default")
      (node (ref "21") (pin "3") (pinfunction "KL_3") (pintype "passive"))
      (node (ref "IC114") (pin "11") (pinfunction "O6_11") (pintype "open_collector"))
      (node (ref "TP233") (pin "TP") (pinfunction "PP_TP") (pintype "input"))
    )
    (net (code "229") (name "Net-(21G-KL)") (class "Default")
      (node (ref "21") (pin "4") (pinfunction "KL_4") (pintype "passive"))
      (node (ref "IC114") (pin "10") (pinfunction "O7_10") (pintype "open_collector"))
      (node (ref "TP234") (pin "TP") (pinfunction "PP_TP") (pintype "input"))
    )
    (net (code "230") (name "Net-(21H-KL)") (class "Default")
      (node (ref "21") (pin "5") (pinfunction "KL_5") (pintype "passive"))
      (node (ref "IC114") (pin "12") (pinfunction "O5_12") (pintype "open_collector"))
      (node (ref "TP235") (pin "TP") (pinfunction "PP_TP") (pintype "input"))
    )
    (net (code "231") (name "Net-(21I-KL)") (class "Default")
      (node (ref "21") (pin "6") (pinfunction "KL_6") (pintype "passive"))
      (node (ref "IC114") (pin "13") (pinfunction "O4_13") (pintype "open_collector"))
      (node (ref "TP236") (pin "TP") (pinfunction "PP_TP") (pintype "input"))
    )
    (net (code "232") (name "Net-(21J-KL)") (class "Default")
      (node (ref "21") (pin "7") (pinfunction "KL_7") (pintype "passive"))
      (node (ref "IC114") (pin "14") (pinfunction "O3_14") (pintype "open_collector"))
      (node (ref "TP237") (pin "TP") (pinfunction "PP_TP") (pintype "input"))
    )
    (net (code "233") (name "Net-(21K-KL)") (class "Default")
      (node (ref "21") (pin "8") (pinfunction "KL_8") (pintype "passive"))
      (node (ref "Q77") (pin "3") (pinfunction "D_3") (pintype "passive"))
      (node (ref "TP238") (pin "TP") (pinfunction "PP_TP") (pintype "input"))
    )
    (net (code "234") (name "Net-(21L-KL)") (class "Default")
      (node (ref "21") (pin "9") (pinfunction "KL_9") (pintype "passive"))
      (node (ref "D122") (pin "1") (pinfunction "+_1") (pintype "passive"))
      (node (ref "TP239") (pin "TP") (pinfunction "PP_TP") (pintype "input"))
      (node (ref "X31") (pin "17") (pinfunction "17_17") (pintype "passive"))
    )
    (net (code "235") (name "Net-(22B-KL)") (class "Default")
      (node (ref "22") (pin "10") (pinfunction "KL_10") (pintype "passive"))
      (node (ref "TP250") (pin "TP") (pinfunction "PP_TP") (pintype "input"))
      (node (ref "X31") (pin "15") (pinfunction "15_15") (pintype "passive"))
    )
    (net (code "236") (name "Net-(22C-KL)") (class "Default")
      (node (ref "22") (pin "11") (pinfunction "KL_11") (pintype "passive"))
      (node (ref "IC114") (pin "16") (pinfunction "O1_16") (pintype "open_collector"))
      (node (ref "R498") (pin "1") (pinfunction "1_1") (pintype "passive"))
      (node (ref "R505") (pin "2") (pinfunction "2_2") (pintype "passive"))
      (node (ref "TP251") (pin "TP") (pinfunction "PP_TP") (pintype "input"))
    )
    (net (code "237") (name "Net-(22D-KL)") (class "Default")
      (node (ref "22") (pin "12") (pinfunction "KL_12") (pintype "passive"))
      (node (ref "R499") (pin "1") (pinfunction "1_1") (pintype "passive"))
      (node (ref "TP253") (pin "TP") (pinfunction "PP_TP") (pintype "input"))
    )
    (net (code "238") (name "Net-(22E-KL)") (class "Default")
      (node (ref "22") (pin "2") (pinfunction "KL_2") (pintype "passive"))
      (node (ref "D127") (pin "2") (pinfunction "-_2") (pintype "passive"))
      (node (ref "LED61") (pin "K") (pinfunction "C_K") (pintype "passive"))
      (node (ref "TP242") (pin "TP") (pinfunction "PP_TP") (pintype "input"))
      (node (ref "X31") (pin "12") (pinfunction "12_12") (pintype "passive"))
    )
    (net (code "239") (name "Net-(22F-KL)") (class "Default")
      (node (ref "22") (pin "3") (pinfunction "KL_3") (pintype "passive"))
      (node (ref "D126") (pin "2") (pinfunction "-_2") (pintype "passive"))
      (node (ref "LED62") (pin "K") (pinfunction "C_K") (pintype "passive"))
      (node (ref "TP243") (pin "TP") (pinfunction "PP_TP") (pintype "input"))
      (node (ref "X31") (pin "11") (pinfunction "11_11") (pintype "passive"))
    )
    (net (code "240") (name "Net-(22G-KL)") (class "Default")
      (node (ref "22") (pin "4") (pinfunction "KL_4") (pintype "passive"))
      (node (ref "D125") (pin "2") (pinfunction "-_2") (pintype "passive"))
      (node (ref "LED63") (pin "K") (pinfunction "C_K") (pintype "passive"))
      (node (ref "TP244") (pin "TP") (pinfunction "PP_TP") (pintype "input"))
      (node (ref "X31") (pin "10") (pinfunction "10_10") (pintype "passive"))
    )
    (net (code "241") (name "Net-(22H-KL)") (class "Default")
      (node (ref "22") (pin "5") (pinfunction "KL_5") (pintype "passive"))
      (node (ref "D124") (pin "2") (pinfunction "-_2") (pintype "passive"))
      (node (ref "LED64") (pin "K") (pinfunction "C_K") (pintype "passive"))
      (node (ref "TP245") (pin "TP") (pinfunction "PP_TP") (pintype "input"))
      (node (ref "X31") (pin "9") (pinfunction "9_9") (pintype "passive"))
    )
    (net (code "242") (name "Net-(22I-KL)") (class "Default")
      (node (ref "22") (pin "6") (pinfunction "KL_6") (pintype "passive"))
      (node (ref "JP52") (pin "2") (pinfunction "2_2") (pintype "passive"))
      (node (ref "TP246") (pin "TP") (pinfunction "PP_TP") (pintype "input"))
    )
    (net (code "243") (name "Net-(22J-KL)") (class "Default")
      (node (ref "22") (pin "7") (pinfunction "KL_7") (pintype "passive"))
      (node (ref "LED65") (pin "A") (pinfunction "A_A") (pintype "passive"))
      (node (ref "TP247") (pin "TP") (pinfunction "PP_TP") (pintype "input"))
      (node (ref "X31") (pin "8") (pinfunction "8_8") (pintype "passive"))
    )
    (net (code "244") (name "Net-(22K-KL)") (class "Default")
      (node (ref "22") (pin "8") (pinfunction "KL_8") (pintype "passive"))
      (node (ref "D128") (pin "2") (pinfunction "-_2") (pintype "passive"))
      (node (ref "LED66") (pin "K") (pinfunction "C_K") (pintype "passive"))
      (node (ref "TP248") (pin "TP") (pinfunction "PP_TP") (pintype "input"))
      (node (ref "X31") (pin "14") (pinfunction "14_14") (pintype "passive"))
    )
    (net (code "245") (name "Net-(22L-KL)") (class "Default")
      (node (ref "22") (pin "9") (pinfunction "KL_9") (pintype "passive"))
      (node (ref "D125") (pin "1") (pinfunction "+_1") (pintype "passive"))
      (node (ref "D126") (pin "1") (pinfunction "+_1") (pintype "passive"))
      (node (ref "JP53") (pin "1") (pinfunction "1_1") (pintype "passive"))
      (node (ref "JP54") (pin "2") (pinfunction "2_2") (pintype "passive"))
      (node (ref "TP249") (pin "TP") (pinfunction "PP_TP") (pintype "input"))
    )
    (net (code "246") (name "Net-(23A-KL)") (class "Default")
      (node (ref "23") (pin "1") (pinfunction "KL_1") (pintype "passive"))
      (node (ref "TP254") (pin "TP") (pinfunction "PP_TP") (pintype "input"))
      (node (ref "X34") (pin "1") (pinfunction "1_1") (pintype "passive"))
    )
    (net (code "247") (name "Net-(23B-KL)") (class "Default")
      (node (ref "23") (pin "10") (pinfunction "KL_10") (pintype "passive"))
      (node (ref "D134") (pin "2") (pinfunction "-_2") (pintype "passive"))
      (node (ref "D135") (pin "2") (pinfunction "-_2") (pintype "passive"))
      (node (ref "JP60") (pin "1") (pinfunction "1_1") (pintype "passive"))
      (node (ref "SJ12") (pin "1") (pinfunction "1_1") (pintype "passive"))
      (node (ref "TP263") (pin "TP") (pinfunction "PP_TP") (pintype "input"))
    )
    (net (code "248") (name "Net-(23C-KL)") (class "Default")
      (node (ref "23") (pin "11") (pinfunction "KL_11") (pintype "passive"))
      (node (ref "D135") (pin "1") (pinfunction "+_1") (pintype "passive"))
      (node (ref "TP264") (pin "TP") (pinfunction "PP_TP") (pintype "input"))
      (node (ref "X34") (pin "19") (pinfunction "19_19") (pintype "passive"))
    )
    (net (code "249") (name "Net-(23E-KL)") (class "Default")
      (node (ref "23") (pin "2") (pinfunction "KL_2") (pintype "passive"))
      (node (ref "Q80") (pin "2") (pinfunction "C_2") (pintype "passive"))
      (node (ref "TP255") (pin "TP") (pinfunction "PP_TP") (pintype "input"))
    )
    (net (code "250") (name "Net-(23F-KL)") (class "Default")
      (node (ref "23") (pin "3") (pinfunction "KL_3") (pintype "passive"))
      (node (ref "IC125") (pin "11") (pinfunction "O6_11") (pintype "open_collector"))
      (node (ref "TP256") (pin "TP") (pinfunction "PP_TP") (pintype "input"))
    )
    (net (code "251") (name "Net-(23G-KL)") (class "Default")
      (node (ref "23") (pin "4") (pinfunction "KL_4") (pintype "passive"))
      (node (ref "IC125") (pin "10") (pinfunction "O7_10") (pintype "open_collector"))
      (node (ref "TP257") (pin "TP") (pinfunction "PP_TP") (pintype "input"))
    )
    (net (code "252") (name "Net-(23H-KL)") (class "Default")
      (node (ref "23") (pin "5") (pinfunction "KL_5") (pintype "passive"))
      (node (ref "IC125") (pin "12") (pinfunction "O5_12") (pintype "open_collector"))
      (node (ref "TP258") (pin "TP") (pinfunction "PP_TP") (pintype "input"))
    )
    (net (code "253") (name "Net-(23I-KL)") (class "Default")
      (node (ref "23") (pin "6") (pinfunction "KL_6") (pintype "passive"))
      (node (ref "IC125") (pin "13") (pinfunction "O4_13") (pintype "open_collector"))
      (node (ref "TP259") (pin "TP") (pinfunction "PP_TP") (pintype "input"))
    )
    (net (code "254") (name "Net-(23J-KL)") (class "Default")
      (node (ref "23") (pin "7") (pinfunction "KL_7") (pintype "passive"))
      (node (ref "IC125") (pin "14") (pinfunction "O3_14") (pintype "open_collector"))
      (node (ref "TP260") (pin "TP") (pinfunction "PP_TP") (pintype "input"))
    )
    (net (code "255") (name "Net-(23K-KL)") (class "Default")
      (node (ref "23") (pin "8") (pinfunction "KL_8") (pintype "passive"))
      (node (ref "Q84") (pin "3") (pinfunction "D_3") (pintype "passive"))
      (node (ref "TP261") (pin "TP") (pinfunction "PP_TP") (pintype "input"))
    )
    (net (code "256") (name "Net-(23L-KL)") (class "Default")
      (node (ref "23") (pin "9") (pinfunction "KL_9") (pintype "passive"))
      (node (ref "D134") (pin "1") (pinfunction "+_1") (pintype "passive"))
      (node (ref "TP262") (pin "TP") (pinfunction "PP_TP") (pintype "input"))
      (node (ref "X34") (pin "17") (pinfunction "17_17") (pintype "passive"))
    )
    (net (code "257") (name "Net-(24B-KL)") (class "Default")
      (node (ref "24") (pin "10") (pinfunction "KL_10") (pintype "passive"))
      (node (ref "TP273") (pin "TP") (pinfunction "PP_TP") (pintype "input"))
      (node (ref "X34") (pin "15") (pinfunction "15_15") (pintype "passive"))
    )
    (net (code "258") (name "Net-(24C-KL)") (class "Default")
      (node (ref "24") (pin "11") (pinfunction "KL_11") (pintype "passive"))
      (node (ref "IC125") (pin "16") (pinfunction "O1_16") (pintype "open_collector"))
      (node (ref "R544") (pin "1") (pinfunction "1_1") (pintype "passive"))
      (node (ref "R551") (pin "2") (pinfunction "2_2") (pintype "passive"))
      (node (ref "TP274") (pin "TP") (pinfunction "PP_TP") (pintype "input"))
    )
    (net (code "259") (name "Net-(24D-KL)") (class "Default")
      (node (ref "24") (pin "12") (pinfunction "KL_12") (pintype "passive"))
      (node (ref "R545") (pin "1") (pinfunction "1_1") (pintype "passive"))
      (node (ref "TP276") (pin "TP") (pinfunction "PP_TP") (pintype "input"))
    )
    (net (code "260") (name "Net-(24E-KL)") (class "Default")
      (node (ref "24") (pin "2") (pinfunction "KL_2") (pintype "passive"))
      (node (ref "D139") (pin "2") (pinfunction "-_2") (pintype "passive"))
      (node (ref "LED67") (pin "K") (pinfunction "C_K") (pintype "passive"))
      (node (ref "TP265") (pin "TP") (pinfunction "PP_TP") (pintype "input"))
      (node (ref "X34") (pin "12") (pinfunction "12_12") (pintype "passive"))
    )
    (net (code "261") (name "Net-(24F-KL)") (class "Default")
      (node (ref "24") (pin "3") (pinfunction "KL_3") (pintype "passive"))
      (node (ref "D138") (pin "2") (pinfunction "-_2") (pintype "passive"))
      (node (ref "LED68") (pin "K") (pinfunction "C_K") (pintype "passive"))
      (node (ref "TP266") (pin "TP") (pinfunction "PP_TP") (pintype "input"))
      (node (ref "X34") (pin "11") (pinfunction "11_11") (pintype "passive"))
    )
    (net (code "262") (name "Net-(24G-KL)") (class "Default")
      (node (ref "24") (pin "4") (pinfunction "KL_4") (pintype "passive"))
      (node (ref "D137") (pin "2") (pinfunction "-_2") (pintype "passive"))
      (node (ref "LED69") (pin "K") (pinfunction "C_K") (pintype "passive"))
      (node (ref "TP267") (pin "TP") (pinfunction "PP_TP") (pintype "input"))
      (node (ref "X34") (pin "10") (pinfunction "10_10") (pintype "passive"))
    )
    (net (code "263") (name "Net-(24H-KL)") (class "Default")
      (node (ref "24") (pin "5") (pinfunction "KL_5") (pintype "passive"))
      (node (ref "D136") (pin "2") (pinfunction "-_2") (pintype "passive"))
      (node (ref "LED70") (pin "K") (pinfunction "C_K") (pintype "passive"))
      (node (ref "TP268") (pin "TP") (pinfunction "PP_TP") (pintype "input"))
      (node (ref "X34") (pin "9") (pinfunction "9_9") (pintype "passive"))
    )
    (net (code "264") (name "Net-(24I-KL)") (class "Default")
      (node (ref "24") (pin "6") (pinfunction "KL_6") (pintype "passive"))
      (node (ref "JP57") (pin "2") (pinfunction "2_2") (pintype "passive"))
      (node (ref "TP269") (pin "TP") (pinfunction "PP_TP") (pintype "input"))
    )
    (net (code "265") (name "Net-(24J-KL)") (class "Default")
      (node (ref "24") (pin "7") (pinfunction "KL_7") (pintype "passive"))
      (node (ref "LED71") (pin "A") (pinfunction "A_A") (pintype "passive"))
      (node (ref "TP270") (pin "TP") (pinfunction "PP_TP") (pintype "input"))
      (node (ref "X34") (pin "8") (pinfunction "8_8") (pintype "passive"))
    )
    (net (code "266") (name "Net-(24K-KL)") (class "Default")
      (node (ref "24") (pin "8") (pinfunction "KL_8") (pintype "passive"))
      (node (ref "D140") (pin "2") (pinfunction "-_2") (pintype "passive"))
      (node (ref "LED72") (pin "K") (pinfunction "C_K") (pintype "passive"))
      (node (ref "TP271") (pin "TP") (pinfunction "PP_TP") (pintype "input"))
      (node (ref "X34") (pin "14") (pinfunction "14_14") (pintype "passive"))
    )
    (net (code "267") (name "Net-(24L-KL)") (class "Default")
      (node (ref "24") (pin "9") (pinfunction "KL_9") (pintype "passive"))
      (node (ref "D137") (pin "1") (pinfunction "+_1") (pintype "passive"))
      (node (ref "D138") (pin "1") (pinfunction "+_1") (pintype "passive"))
      (node (ref "JP58") (pin "1") (pinfunction "1_1") (pintype "passive"))
      (node (ref "JP59") (pin "2") (pinfunction "2_2") (pintype "passive"))
      (node (ref "TP272") (pin "TP") (pinfunction "PP_TP") (pintype "input"))
    )
    (net (code "268") (name "Net-(C3-Pad1)") (class "Default")
      (node (ref "C3") (pin "1") (pinfunction "1_1") (pintype "passive"))
      (node (ref "R12") (pin "1") (pinfunction "1_1") (pintype "passive"))
      (node (ref "R8") (pin "1") (pinfunction "1_1") (pintype "passive"))
    )
    (net (code "269") (name "Net-(C7-Pad1)") (class "Default")
      (node (ref "C7") (pin "1") (pinfunction "1_1") (pintype "passive"))
      (node (ref "R25") (pin "1") (pinfunction "1_1") (pintype "passive"))
      (node (ref "R30") (pin "2") (pinfunction "2_2") (pintype "passive"))
    )
    (net (code "270") (name "Net-(C11-Pad1)") (class "Default")
      (node (ref "C11") (pin "1") (pinfunction "1_1") (pintype "passive"))
      (node (ref "R57") (pin "1") (pinfunction "1_1") (pintype "passive"))
      (node (ref "R58") (pin "2") (pinfunction "2_2") (pintype "passive"))
    )
    (net (code "271") (name "Net-(C20-Pad1)") (class "Default")
      (node (ref "C20") (pin "1") (pinfunction "1_1") (pintype "passive"))
      (node (ref "R86") (pin "1") (pinfunction "1_1") (pintype "passive"))
      (node (ref "R87") (pin "1") (pinfunction "1_1") (pintype "passive"))
    )
    (net (code "272") (name "Net-(C21-Pad1)") (class "Default")
      (node (ref "C21") (pin "1") (pinfunction "1_1") (pintype "passive"))
      (node (ref "R103") (pin "1") (pinfunction "1_1") (pintype "passive"))
      (node (ref "R104") (pin "2") (pinfunction "2_2") (pintype "passive"))
    )
    (net (code "273") (name "Net-(C30-Pad1)") (class "Default")
      (node (ref "C30") (pin "1") (pinfunction "1_1") (pintype "passive"))
      (node (ref "R132") (pin "1") (pinfunction "1_1") (pintype "passive"))
      (node (ref "R133") (pin "1") (pinfunction "1_1") (pintype "passive"))
    )
    (net (code "274") (name "Net-(C31-Pad1)") (class "Default")
      (node (ref "C31") (pin "1") (pinfunction "1_1") (pintype "passive"))
      (node (ref "R149") (pin "1") (pinfunction "1_1") (pintype "passive"))
      (node (ref "R150") (pin "2") (pinfunction "2_2") (pintype "passive"))
    )
    (net (code "275") (name "Net-(C40-Pad1)") (class "Default")
      (node (ref "C40") (pin "1") (pinfunction "1_1") (pintype "passive"))
      (node (ref "R178") (pin "1") (pinfunction "1_1") (pintype "passive"))
      (node (ref "R179") (pin "1") (pinfunction "1_1") (pintype "passive"))
    )
    (net (code "276") (name "Net-(C41-Pad1)") (class "Default")
      (node (ref "C41") (pin "1") (pinfunction "1_1") (pintype "passive"))
      (node (ref "R195") (pin "1") (pinfunction "1_1") (pintype "passive"))
      (node (ref "R196") (pin "2") (pinfunction "2_2") (pintype "passive"))
    )
    (net (code "277") (name "Net-(C50-Pad1)") (class "Default")
      (node (ref "C50") (pin "1") (pinfunction "1_1") (pintype "passive"))
      (node (ref "R224") (pin "1") (pinfunction "1_1") (pintype "passive"))
      (node (ref "R225") (pin "1") (pinfunction "1_1") (pintype "passive"))
    )
    (net (code "278") (name "Net-(C51-Pad1)") (class "Default")
      (node (ref "C51") (pin "1") (pinfunction "1_1") (pintype "passive"))
      (node (ref "R241") (pin "1") (pinfunction "1_1") (pintype "passive"))
      (node (ref "R242") (pin "2") (pinfunction "2_2") (pintype "passive"))
    )
    (net (code "279") (name "Net-(C60-Pad1)") (class "Default")
      (node (ref "C60") (pin "1") (pinfunction "1_1") (pintype "passive"))
      (node (ref "R270") (pin "1") (pinfunction "1_1") (pintype "passive"))
      (node (ref "R271") (pin "1") (pinfunction "1_1") (pintype "passive"))
    )
    (net (code "280") (name "Net-(C61-Pad1)") (class "Default")
      (node (ref "C61") (pin "1") (pinfunction "1_1") (pintype "passive"))
      (node (ref "R287") (pin "1") (pinfunction "1_1") (pintype "passive"))
      (node (ref "R288") (pin "2") (pinfunction "2_2") (pintype "passive"))
    )
    (net (code "281") (name "Net-(C70-Pad1)") (class "Default")
      (node (ref "C70") (pin "1") (pinfunction "1_1") (pintype "passive"))
      (node (ref "R316") (pin "1") (pinfunction "1_1") (pintype "passive"))
      (node (ref "R317") (pin "1") (pinfunction "1_1") (pintype "passive"))
    )
    (net (code "282") (name "Net-(C71-Pad1)") (class "Default")
      (node (ref "C71") (pin "1") (pinfunction "1_1") (pintype "passive"))
      (node (ref "R333") (pin "1") (pinfunction "1_1") (pintype "passive"))
      (node (ref "R334") (pin "2") (pinfunction "2_2") (pintype "passive"))
    )
    (net (code "283") (name "Net-(C80-Pad1)") (class "Default")
      (node (ref "C80") (pin "1") (pinfunction "1_1") (pintype "passive"))
      (node (ref "R362") (pin "1") (pinfunction "1_1") (pintype "passive"))
      (node (ref "R363") (pin "1") (pinfunction "1_1") (pintype "passive"))
    )
    (net (code "284") (name "Net-(C81-Pad1)") (class "Default")
      (node (ref "C81") (pin "1") (pinfunction "1_1") (pintype "passive"))
      (node (ref "R379") (pin "1") (pinfunction "1_1") (pintype "passive"))
      (node (ref "R380") (pin "2") (pinfunction "2_2") (pintype "passive"))
    )
    (net (code "285") (name "Net-(C90-Pad1)") (class "Default")
      (node (ref "C90") (pin "1") (pinfunction "1_1") (pintype "passive"))
      (node (ref "R408") (pin "1") (pinfunction "1_1") (pintype "passive"))
      (node (ref "R409") (pin "1") (pinfunction "1_1") (pintype "passive"))
    )
    (net (code "286") (name "Net-(C91-Pad1)") (class "Default")
      (node (ref "C91") (pin "1") (pinfunction "1_1") (pintype "passive"))
      (node (ref "R425") (pin "1") (pinfunction "1_1") (pintype "passive"))
      (node (ref "R426") (pin "2") (pinfunction "2_2") (pintype "passive"))
    )
    (net (code "287") (name "Net-(C100-Pad1)") (class "Default")
      (node (ref "C100") (pin "1") (pinfunction "1_1") (pintype "passive"))
      (node (ref "R454") (pin "1") (pinfunction "1_1") (pintype "passive"))
      (node (ref "R455") (pin "1") (pinfunction "1_1") (pintype "passive"))
    )
    (net (code "288") (name "Net-(C101-Pad1)") (class "Default")
      (node (ref "C101") (pin "1") (pinfunction "1_1") (pintype "passive"))
      (node (ref "R471") (pin "1") (pinfunction "1_1") (pintype "passive"))
      (node (ref "R472") (pin "2") (pinfunction "2_2") (pintype "passive"))
    )
    (net (code "289") (name "Net-(C110-Pad1)") (class "Default")
      (node (ref "C110") (pin "1") (pinfunction "1_1") (pintype "passive"))
      (node (ref "R500") (pin "1") (pinfunction "1_1") (pintype "passive"))
      (node (ref "R501") (pin "1") (pinfunction "1_1") (pintype "passive"))
    )
    (net (code "290") (name "Net-(C111-Pad1)") (class "Default")
      (node (ref "C111") (pin "1") (pinfunction "1_1") (pintype "passive"))
      (node (ref "R517") (pin "1") (pinfunction "1_1") (pintype "passive"))
      (node (ref "R518") (pin "2") (pinfunction "2_2") (pintype "passive"))
    )
    (net (code "291") (name "Net-(C120-Pad1)") (class "Default")
      (node (ref "C120") (pin "1") (pinfunction "1_1") (pintype "passive"))
      (node (ref "R546") (pin "1") (pinfunction "1_1") (pintype "passive"))
      (node (ref "R547") (pin "1") (pinfunction "1_1") (pintype "passive"))
    )
    (net (code "292") (name "Net-(D4-PadC)") (class "Default")
      (node (ref "D4") (pin "C") (pinfunction "C_C") (pintype "passive"))
      (node (ref "R5") (pin "2") (pinfunction "2_2") (pintype "passive"))
      (node (ref "X1") (pin "22") (pinfunction "22_22") (pintype "passive"))
    )
    (net (code "293") (name "Net-(D5--)") (class "Default")
      (node (ref "D5") (pin "2") (pinfunction "-_2") (pintype "passive"))
      (node (ref "Q4") (pin "2") (pinfunction "C_2") (pintype "passive"))
      (node (ref "START") (pin "TP") (pinfunction "PP_TP") (pintype "input"))
      (node (ref "X1") (pin "5") (pinfunction "5_5") (pintype "passive"))
    )
    (net (code "294") (name "Net-(D6-+)") (class "Default")
      (node (ref "D6") (pin "1") (pinfunction "+_1") (pintype "passive"))
      (node (ref "R27") (pin "1") (pinfunction "1_1") (pintype "passive"))
    )
    (net (code "295") (name "Net-(D9-+)") (class "Default")
      (node (ref "D9") (pin "1") (pinfunction "+_1") (pintype "passive"))
      (node (ref "JP2") (pin "2") (pinfunction "2_2") (pintype "passive"))
    )
    (net (code "296") (name "Net-(D10-+)") (class "Default")
      (node (ref "D10") (pin "1") (pinfunction "+_1") (pintype "passive"))
      (node (ref "JP3") (pin "1") (pinfunction "1_1") (pintype "passive"))
    )
    (net (code "297") (name "Net-(D11-+)") (class "Default")
      (node (ref "D11") (pin "1") (pinfunction "+_1") (pintype "passive"))
      (node (ref "R33") (pin "1") (pinfunction "1_1") (pintype "passive"))
    )
    (net (code "298") (name "Net-(D11--)") (class "Default")
      (node (ref "D11") (pin "2") (pinfunction "-_2") (pintype "passive"))
      (node (ref "IC8") (pin "2") (pinfunction "OUT_2") (pintype "open_collector"))
      (node (ref "JP5") (pin "1") (pinfunction "1_1") (pintype "passive"))
      (node (ref "Q7") (pin "1") (pinfunction "G_1") (pintype "passive"))
      (node (ref "R35") (pin "2") (pinfunction "2_2") (pintype "passive"))
    )
    (net (code "299") (name "Net-(D12-+)") (class "Default")
      (node (ref "D12") (pin "1") (pinfunction "+_1") (pintype "passive"))
      (node (ref "R40") (pin "1") (pinfunction "1_1") (pintype "passive"))
    )
    (net (code "300") (name "Net-(D12--)") (class "Default")
      (node (ref "C9") (pin "2") (pinfunction "2_2") (pintype "passive"))
      (node (ref "D12") (pin "2") (pinfunction "-_2") (pintype "passive"))
      (node (ref "IC10") (pin "2") (pinfunction "TR_2") (pintype "input"))
      (node (ref "IC10") (pin "6") (pinfunction "THR_6") (pintype "input"))
      (node (ref "R41") (pin "1") (pinfunction "1_1") (pintype "passive"))
    )
    (net (code "301") (name "Net-(D13-+)") (class "Default")
      (node (ref "D13") (pin "1") (pinfunction "+_1") (pintype "passive"))
      (node (ref "R61") (pin "1") (pinfunction "1_1") (pintype "passive"))
    )
    (net (code "302") (name "Net-(D13--)") (class "Default")
      (node (ref "D13") (pin "2") (pinfunction "-_2") (pintype "passive"))
      (node (ref "IC16") (pin "2") (pinfunction "OUT_2") (pintype "open_collector"))
      (node (ref "JP7") (pin "1") (pinfunction "1_1") (pintype "passive"))
      (node (ref "Q13") (pin "1") (pinfunction "G_1") (pintype "passive"))
      (node (ref "R77") (pin "2") (pinfunction "2_2") (pintype "passive"))
    )
    (net (code "303") (name "Net-(D16-+)") (class "Default")
      (node (ref "D16") (pin "1") (pinfunction "+_1") (pintype "passive"))
      (node (ref "R47") (pin "1") (pinfunction "1_1") (pintype "passive"))
    )
    (net (code "304") (name "Net-(D19-+)") (class "Default")
      (node (ref "D19") (pin "1") (pinfunction "+_1") (pintype "passive"))
      (node (ref "JP8") (pin "2") (pinfunction "2_2") (pintype "passive"))
    )
    (net (code "305") (name "Net-(D20-+)") (class "Default")
      (node (ref "D20") (pin "1") (pinfunction "+_1") (pintype "passive"))
      (node (ref "JP9") (pin "1") (pinfunction "1_1") (pintype "passive"))
    )
    (net (code "306") (name "Net-(D21--)") (class "Default")
      (node (ref "D21") (pin "2") (pinfunction "-_2") (pintype "passive"))
      (node (ref "Q8") (pin "2") (pinfunction "C_2") (pintype "passive"))
      (node (ref "START1") (pin "TP") (pinfunction "PP_TP") (pintype "input"))
      (node (ref "X4") (pin "5") (pinfunction "5_5") (pintype "passive"))
    )
    (net (code "307") (name "Net-(D22-+)") (class "Default")
      (node (ref "D22") (pin "1") (pinfunction "+_1") (pintype "passive"))
      (node (ref "R80") (pin "1") (pinfunction "1_1") (pintype "passive"))
    )
    (net (code "308") (name "Net-(D22--)") (class "Default")
      (node (ref "C17") (pin "2") (pinfunction "2_2") (pintype "passive"))
      (node (ref "D22") (pin "2") (pinfunction "-_2") (pintype "passive"))
      (node (ref "IC18") (pin "2") (pinfunction "TR_2") (pintype "input"))
      (node (ref "IC18") (pin "6") (pinfunction "THR_6") (pintype "input"))
      (node (ref "R78") (pin "1") (pinfunction "1_1") (pintype "passive"))
    )
    (net (code "309") (name "Net-(D24-PadC)") (class "Default")
      (node (ref "D24") (pin "C") (pinfunction "C_C") (pintype "passive"))
      (node (ref "R53") (pin "2") (pinfunction "2_2") (pintype "passive"))
      (node (ref "X4") (pin "22") (pinfunction "22_22") (pintype "passive"))
    )
    (net (code "310") (name "Net-(D25-+)") (class "Default")
      (node (ref "D25") (pin "1") (pinfunction "+_1") (pintype "passive"))
      (node (ref "R107") (pin "1") (pinfunction "1_1") (pintype "passive"))
    )
    (net (code "311") (name "Net-(D25--)") (class "Default")
      (node (ref "D25") (pin "2") (pinfunction "-_2") (pintype "passive"))
      (node (ref "IC27") (pin "2") (pinfunction "OUT_2") (pintype "open_collector"))
      (node (ref "JP12") (pin "1") (pinfunction "1_1") (pintype "passive"))
      (node (ref "Q20") (pin "1") (pinfunction "G_1") (pintype "passive"))
      (node (ref "R123") (pin "2") (pinfunction "2_2") (pintype "passive"))
    )
    (net (code "312") (name "Net-(D28-+)") (class "Default")
      (node (ref "D28") (pin "1") (pinfunction "+_1") (pintype "passive"))
      (node (ref "R93") (pin "1") (pinfunction "1_1") (pintype "passive"))
    )
    (net (code "313") (name "Net-(D31-+)") (class "Default")
      (node (ref "D31") (pin "1") (pinfunction "+_1") (pintype "passive"))
      (node (ref "JP13") (pin "2") (pinfunction "2_2") (pintype "passive"))
    )
    (net (code "314") (name "Net-(D32-+)") (class "Default")
      (node (ref "D32") (pin "1") (pinfunction "+_1") (pintype "passive"))
      (node (ref "JP14") (pin "1") (pinfunction "1_1") (pintype "passive"))
    )
    (net (code "315") (name "Net-(D33--)") (class "Default")
      (node (ref "D33") (pin "2") (pinfunction "-_2") (pintype "passive"))
      (node (ref "Q15") (pin "2") (pinfunction "C_2") (pintype "passive"))
      (node (ref "START2") (pin "TP") (pinfunction "PP_TP") (pintype "input"))
      (node (ref "X7") (pin "5") (pinfunction "5_5") (pintype "passive"))
    )
    (net (code "316") (name "Net-(D34-+)") (class "Default")
      (node (ref "D34") (pin "1") (pinfunction "+_1") (pintype "passive"))
      (node (ref "R126") (pin "1") (pinfunction "1_1") (pintype "passive"))
    )
    (net (code "317") (name "Net-(D34--)") (class "Default")
      (node (ref "C27") (pin "2") (pinfunction "2_2") (pintype "passive"))
      (node (ref "D34") (pin "2") (pinfunction "-_2") (pintype "passive"))
      (node (ref "IC29") (pin "2") (pinfunction "TR_2") (pintype "input"))
      (node (ref "IC29") (pin "6") (pinfunction "THR_6") (pintype "input"))
      (node (ref "R124") (pin "1") (pinfunction "1_1") (pintype "passive"))
    )
    (net (code "318") (name "Net-(D36-PadC)") (class "Default")
      (node (ref "D36") (pin "C") (pinfunction "C_C") (pintype "passive"))
      (node (ref "R99") (pin "2") (pinfunction "2_2") (pintype "passive"))
      (node (ref "X7") (pin "22") (pinfunction "22_22") (pintype "passive"))
    )
    (net (code "319") (name "Net-(D37-+)") (class "Default")
      (node (ref "D37") (pin "1") (pinfunction "+_1") (pintype "passive"))
      (node (ref "R153") (pin "1") (pinfunction "1_1") (pintype "passive"))
    )
    (net (code "320") (name "Net-(D37--)") (class "Default")
      (node (ref "D37") (pin "2") (pinfunction "-_2") (pintype "passive"))
      (node (ref "IC38") (pin "2") (pinfunction "OUT_2") (pintype "open_collector"))
      (node (ref "JP17") (pin "1") (pinfunction "1_1") (pintype "passive"))
      (node (ref "Q27") (pin "1") (pinfunction "G_1") (pintype "passive"))
      (node (ref "R169") (pin "2") (pinfunction "2_2") (pintype "passive"))
    )
    (net (code "321") (name "Net-(D40-+)") (class "Default")
      (node (ref "D40") (pin "1") (pinfunction "+_1") (pintype "passive"))
      (node (ref "R139") (pin "1") (pinfunction "1_1") (pintype "passive"))
    )
    (net (code "322") (name "Net-(D43-+)") (class "Default")
      (node (ref "D43") (pin "1") (pinfunction "+_1") (pintype "passive"))
      (node (ref "JP18") (pin "2") (pinfunction "2_2") (pintype "passive"))
    )
    (net (code "323") (name "Net-(D44-+)") (class "Default")
      (node (ref "D44") (pin "1") (pinfunction "+_1") (pintype "passive"))
      (node (ref "JP19") (pin "1") (pinfunction "1_1") (pintype "passive"))
    )
    (net (code "324") (name "Net-(D45--)") (class "Default")
      (node (ref "D45") (pin "2") (pinfunction "-_2") (pintype "passive"))
      (node (ref "Q22") (pin "2") (pinfunction "C_2") (pintype "passive"))
      (node (ref "START3") (pin "TP") (pinfunction "PP_TP") (pintype "input"))
      (node (ref "X10") (pin "5") (pinfunction "5_5") (pintype "passive"))
    )
    (net (code "325") (name "Net-(D46-+)") (class "Default")
      (node (ref "D46") (pin "1") (pinfunction "+_1") (pintype "passive"))
      (node (ref "R172") (pin "1") (pinfunction "1_1") (pintype "passive"))
    )
    (net (code "326") (name "Net-(D46--)") (class "Default")
      (node (ref "C37") (pin "2") (pinfunction "2_2") (pintype "passive"))
      (node (ref "D46") (pin "2") (pinfunction "-_2") (pintype "passive"))
      (node (ref "IC40") (pin "2") (pinfunction "TR_2") (pintype "input"))
      (node (ref "IC40") (pin "6") (pinfunction "THR_6") (pintype "input"))
      (node (ref "R170") (pin "1") (pinfunction "1_1") (pintype "passive"))
    )
    (net (code "327") (name "Net-(D48-PadC)") (class "Default")
      (node (ref "D48") (pin "C") (pinfunction "C_C") (pintype "passive"))
      (node (ref "R145") (pin "2") (pinfunction "2_2") (pintype "passive"))
      (node (ref "X10") (pin "22") (pinfunction "22_22") (pintype "passive"))
    )
    (net (code "328") (name "Net-(D49-+)") (class "Default")
      (node (ref "D49") (pin "1") (pinfunction "+_1") (pintype "passive"))
      (node (ref "R199") (pin "1") (pinfunction "1_1") (pintype "passive"))
    )
    (net (code "329") (name "Net-(D49--)") (class "Default")
      (node (ref "D49") (pin "2") (pinfunction "-_2") (pintype "passive"))
      (node (ref "IC49") (pin "2") (pinfunction "OUT_2") (pintype "open_collector"))
      (node (ref "JP22") (pin "1") (pinfunction "1_1") (pintype "passive"))
      (node (ref "Q34") (pin "1") (pinfunction "G_1") (pintype "passive"))
      (node (ref "R215") (pin "2") (pinfunction "2_2") (pintype "passive"))
    )
    (net (code "330") (name "Net-(D52-+)") (class "Default")
      (node (ref "D52") (pin "1") (pinfunction "+_1") (pintype "passive"))
      (node (ref "R185") (pin "1") (pinfunction "1_1") (pintype "passive"))
    )
    (net (code "331") (name "Net-(D55-+)") (class "Default")
      (node (ref "D55") (pin "1") (pinfunction "+_1") (pintype "passive"))
      (node (ref "JP23") (pin "2") (pinfunction "2_2") (pintype "passive"))
    )
    (net (code "332") (name "Net-(D56-+)") (class "Default")
      (node (ref "D56") (pin "1") (pinfunction "+_1") (pintype "passive"))
      (node (ref "JP24") (pin "1") (pinfunction "1_1") (pintype "passive"))
    )
    (net (code "333") (name "Net-(D57--)") (class "Default")
      (node (ref "D57") (pin "2") (pinfunction "-_2") (pintype "passive"))
      (node (ref "Q29") (pin "2") (pinfunction "C_2") (pintype "passive"))
      (node (ref "START4") (pin "TP") (pinfunction "PP_TP") (pintype "input"))
      (node (ref "X13") (pin "5") (pinfunction "5_5") (pintype "passive"))
    )
    (net (code "334") (name "Net-(D58-+)") (class "Default")
      (node (ref "D58") (pin "1") (pinfunction "+_1") (pintype "passive"))
      (node (ref "R218") (pin "1") (pinfunction "1_1") (pintype "passive"))
    )
    (net (code "335") (name "Net-(D58--)") (class "Default")
      (node (ref "C47") (pin "2") (pinfunction "2_2") (pintype "passive"))
      (node (ref "D58") (pin "2") (pinfunction "-_2") (pintype "passive"))
      (node (ref "IC51") (pin "2") (pinfunction "TR_2") (pintype "input"))
      (node (ref "IC51") (pin "6") (pinfunction "THR_6") (pintype "input"))
      (node (ref "R216") (pin "1") (pinfunction "1_1") (pintype "passive"))
    )
    (net (code "336") (name "Net-(D60-PadC)") (class "Default")
      (node (ref "D60") (pin "C") (pinfunction "C_C") (pintype "passive"))
      (node (ref "R191") (pin "2") (pinfunction "2_2") (pintype "passive"))
      (node (ref "X13") (pin "22") (pinfunction "22_22") (pintype "passive"))
    )
    (net (code "337") (name "Net-(D61-+)") (class "Default")
      (node (ref "D61") (pin "1") (pinfunction "+_1") (pintype "passive"))
      (node (ref "R245") (pin "1") (pinfunction "1_1") (pintype "passive"))
    )
    (net (code "338") (name "Net-(D61--)") (class "Default")
      (node (ref "D61") (pin "2") (pinfunction "-_2") (pintype "passive"))
      (node (ref "IC60") (pin "2") (pinfunction "OUT_2") (pintype "open_collector"))
      (node (ref "JP27") (pin "1") (pinfunction "1_1") (pintype "passive"))
      (node (ref "Q41") (pin "1") (pinfunction "G_1") (pintype "passive"))
      (node (ref "R261") (pin "2") (pinfunction "2_2") (pintype "passive"))
    )
    (net (code "339") (name "Net-(D64-+)") (class "Default")
      (node (ref "D64") (pin "1") (pinfunction "+_1") (pintype "passive"))
      (node (ref "R231") (pin "1") (pinfunction "1_1") (pintype "passive"))
    )
    (net (code "340") (name "Net-(D67-+)") (class "Default")
      (node (ref "D67") (pin "1") (pinfunction "+_1") (pintype "passive"))
      (node (ref "JP28") (pin "2") (pinfunction "2_2") (pintype "passive"))
    )
    (net (code "341") (name "Net-(D68-+)") (class "Default")
      (node (ref "D68") (pin "1") (pinfunction "+_1") (pintype "passive"))
      (node (ref "JP29") (pin "1") (pinfunction "1_1") (pintype "passive"))
    )
    (net (code "342") (name "Net-(D69--)") (class "Default")
      (node (ref "D69") (pin "2") (pinfunction "-_2") (pintype "passive"))
      (node (ref "Q36") (pin "2") (pinfunction "C_2") (pintype "passive"))
      (node (ref "START5") (pin "TP") (pinfunction "PP_TP") (pintype "input"))
      (node (ref "X16") (pin "5") (pinfunction "5_5") (pintype "passive"))
    )
    (net (code "343") (name "Net-(D70-+)") (class "Default")
      (node (ref "D70") (pin "1") (pinfunction "+_1") (pintype "passive"))
      (node (ref "R264") (pin "1") (pinfunction "1_1") (pintype "passive"))
    )
    (net (code "344") (name "Net-(D70--)") (class "Default")
      (node (ref "C57") (pin "2") (pinfunction "2_2") (pintype "passive"))
      (node (ref "D70") (pin "2") (pinfunction "-_2") (pintype "passive"))
      (node (ref "IC62") (pin "2") (pinfunction "TR_2") (pintype "input"))
      (node (ref "IC62") (pin "6") (pinfunction "THR_6") (pintype "input"))
      (node (ref "R262") (pin "1") (pinfunction "1_1") (pintype "passive"))
    )
    (net (code "345") (name "Net-(D72-PadC)") (class "Default")
      (node (ref "D72") (pin "C") (pinfunction "C_C") (pintype "passive"))
      (node (ref "R237") (pin "2") (pinfunction "2_2") (pintype "passive"))
      (node (ref "X16") (pin "22") (pinfunction "22_22") (pintype "passive"))
    )
    (net (code "346") (name "Net-(D73-+)") (class "Default")
      (node (ref "D73") (pin "1") (pinfunction "+_1") (pintype "passive"))
      (node (ref "R291") (pin "1") (pinfunction "1_1") (pintype "passive"))
    )
    (net (code "347") (name "Net-(D73--)") (class "Default")
      (node (ref "D73") (pin "2") (pinfunction "-_2") (pintype "passive"))
      (node (ref "IC71") (pin "2") (pinfunction "OUT_2") (pintype "open_collector"))
      (node (ref "JP32") (pin "1") (pinfunction "1_1") (pintype "passive"))
      (node (ref "Q48") (pin "1") (pinfunction "G_1") (pintype "passive"))
      (node (ref "R307") (pin "2") (pinfunction "2_2") (pintype "passive"))
    )
    (net (code "348") (name "Net-(D76-+)") (class "Default")
      (node (ref "D76") (pin "1") (pinfunction "+_1") (pintype "passive"))
      (node (ref "R277") (pin "1") (pinfunction "1_1") (pintype "passive"))
    )
    (net (code "349") (name "Net-(D79-+)") (class "Default")
      (node (ref "D79") (pin "1") (pinfunction "+_1") (pintype "passive"))
      (node (ref "JP33") (pin "2") (pinfunction "2_2") (pintype "passive"))
    )
    (net (code "350") (name "Net-(D80-+)") (class "Default")
      (node (ref "D80") (pin "1") (pinfunction "+_1") (pintype "passive"))
      (node (ref "JP34") (pin "1") (pinfunction "1_1") (pintype "passive"))
    )
    (net (code "351") (name "Net-(D81--)") (class "Default")
      (node (ref "D81") (pin "2") (pinfunction "-_2") (pintype "passive"))
      (node (ref "Q43") (pin "2") (pinfunction "C_2") (pintype "passive"))
      (node (ref "START6") (pin "TP") (pinfunction "PP_TP") (pintype "input"))
      (node (ref "X19") (pin "5") (pinfunction "5_5") (pintype "passive"))
    )
    (net (code "352") (name "Net-(D82-+)") (class "Default")
      (node (ref "D82") (pin "1") (pinfunction "+_1") (pintype "passive"))
      (node (ref "R310") (pin "1") (pinfunction "1_1") (pintype "passive"))
    )
    (net (code "353") (name "Net-(D82--)") (class "Default")
      (node (ref "C67") (pin "2") (pinfunction "2_2") (pintype "passive"))
      (node (ref "D82") (pin "2") (pinfunction "-_2") (pintype "passive"))
      (node (ref "IC73") (pin "2") (pinfunction "TR_2") (pintype "input"))
      (node (ref "IC73") (pin "6") (pinfunction "THR_6") (pintype "input"))
      (node (ref "R308") (pin "1") (pinfunction "1_1") (pintype "passive"))
    )
    (net (code "354") (name "Net-(D84-PadC)") (class "Default")
      (node (ref "D84") (pin "C") (pinfunction "C_C") (pintype "passive"))
      (node (ref "R283") (pin "2") (pinfunction "2_2") (pintype "passive"))
      (node (ref "X19") (pin "22") (pinfunction "22_22") (pintype "passive"))
    )
    (net (code "355") (name "Net-(D85-+)") (class "Default")
      (node (ref "D85") (pin "1") (pinfunction "+_1") (pintype "passive"))
      (node (ref "R337") (pin "1") (pinfunction "1_1") (pintype "passive"))
    )
    (net (code "356") (name "Net-(D85--)") (class "Default")
      (node (ref "D85") (pin "2") (pinfunction "-_2") (pintype "passive"))
      (node (ref "IC82") (pin "2") (pinfunction "OUT_2") (pintype "open_collector"))
      (node (ref "JP37") (pin "1") (pinfunction "1_1") (pintype "passive"))
      (node (ref "Q55") (pin "1") (pinfunction "G_1") (pintype "passive"))
      (node (ref "R353") (pin "2") (pinfunction "2_2") (pintype "passive"))
    )
    (net (code "357") (name "Net-(D88-+)") (class "Default")
      (node (ref "D88") (pin "1") (pinfunction "+_1") (pintype "passive"))
      (node (ref "R323") (pin "1") (pinfunction "1_1") (pintype "passive"))
    )
    (net (code "358") (name "Net-(D91-+)") (class "Default")
      (node (ref "D91") (pin "1") (pinfunction "+_1") (pintype "passive"))
      (node (ref "JP38") (pin "2") (pinfunction "2_2") (pintype "passive"))
    )
    (net (code "359") (name "Net-(D92-+)") (class "Default")
      (node (ref "D92") (pin "1") (pinfunction "+_1") (pintype "passive"))
      (node (ref "JP39") (pin "1") (pinfunction "1_1") (pintype "passive"))
    )
    (net (code "360") (name "Net-(D93--)") (class "Default")
      (node (ref "D93") (pin "2") (pinfunction "-_2") (pintype "passive"))
      (node (ref "Q50") (pin "2") (pinfunction "C_2") (pintype "passive"))
      (node (ref "START7") (pin "TP") (pinfunction "PP_TP") (pintype "input"))
      (node (ref "X22") (pin "5") (pinfunction "5_5") (pintype "passive"))
    )
    (net (code "361") (name "Net-(D94-+)") (class "Default")
      (node (ref "D94") (pin "1") (pinfunction "+_1") (pintype "passive"))
      (node (ref "R356") (pin "1") (pinfunction "1_1") (pintype "passive"))
    )
    (net (code "362") (name "Net-(D94--)") (class "Default")
      (node (ref "C77") (pin "2") (pinfunction "2_2") (pintype "passive"))
      (node (ref "D94") (pin "2") (pinfunction "-_2") (pintype "passive"))
      (node (ref "IC84") (pin "2") (pinfunction "TR_2") (pintype "input"))
      (node (ref "IC84") (pin "6") (pinfunction "THR_6") (pintype "input"))
      (node (ref "R354") (pin "1") (pinfunction "1_1") (pintype "passive"))
    )
    (net (code "363") (name "Net-(D96-PadC)") (class "Default")
      (node (ref "D96") (pin "C") (pinfunction "C_C") (pintype "passive"))
      (node (ref "R329") (pin "2") (pinfunction "2_2") (pintype "passive"))
      (node (ref "X22") (pin "22") (pinfunction "22_22") (pintype "passive"))
    )
    (net (code "364") (name "Net-(D97-+)") (class "Default")
      (node (ref "D97") (pin "1") (pinfunction "+_1") (pintype "passive"))
      (node (ref "R383") (pin "1") (pinfunction "1_1") (pintype "passive"))
    )
    (net (code "365") (name "Net-(D97--)") (class "Default")
      (node (ref "D97") (pin "2") (pinfunction "-_2") (pintype "passive"))
      (node (ref "IC93") (pin "2") (pinfunction "OUT_2") (pintype "open_collector"))
      (node (ref "JP42") (pin "1") (pinfunction "1_1") (pintype "passive"))
      (node (ref "Q62") (pin "1") (pinfunction "G_1") (pintype "passive"))
      (node (ref "R399") (pin "2") (pinfunction "2_2") (pintype "passive"))
    )
    (net (code "366") (name "Net-(D100-+)") (class "Default")
      (node (ref "D100") (pin "1") (pinfunction "+_1") (pintype "passive"))
      (node (ref "R369") (pin "1") (pinfunction "1_1") (pintype "passive"))
    )
    (net (code "367") (name "Net-(D103-+)") (class "Default")
      (node (ref "D103") (pin "1") (pinfunction "+_1") (pintype "passive"))
      (node (ref "JP43") (pin "2") (pinfunction "2_2") (pintype "passive"))
    )
    (net (code "368") (name "Net-(D104-+)") (class "Default")
      (node (ref "D104") (pin "1") (pinfunction "+_1") (pintype "passive"))
      (node (ref "JP44") (pin "1") (pinfunction "1_1") (pintype "passive"))
    )
    (net (code "369") (name "Net-(D105--)") (class "Default")
      (node (ref "D105") (pin "2") (pinfunction "-_2") (pintype "passive"))
      (node (ref "Q57") (pin "2") (pinfunction "C_2") (pintype "passive"))
      (node (ref "START8") (pin "TP") (pinfunction "PP_TP") (pintype "input"))
      (node (ref "X25") (pin "5") (pinfunction "5_5") (pintype "passive"))
    )
    (net (code "370") (name "Net-(D106-+)") (class "Default")
      (node (ref "D106") (pin "1") (pinfunction "+_1") (pintype "passive"))
      (node (ref "R402") (pin "1") (pinfunction "1_1") (pintype "passive"))
    )
    (net (code "371") (name "Net-(D106--)") (class "Default")
      (node (ref "C87") (pin "2") (pinfunction "2_2") (pintype "passive"))
      (node (ref "D106") (pin "2") (pinfunction "-_2") (pintype "passive"))
      (node (ref "IC95") (pin "2") (pinfunction "TR_2") (pintype "input"))
      (node (ref "IC95") (pin "6") (pinfunction "THR_6") (pintype "input"))
      (node (ref "R400") (pin "1") (pinfunction "1_1") (pintype "passive"))
    )
    (net (code "372") (name "Net-(D108-PadC)") (class "Default")
      (node (ref "D108") (pin "C") (pinfunction "C_C") (pintype "passive"))
      (node (ref "R375") (pin "2") (pinfunction "2_2") (pintype "passive"))
      (node (ref "X25") (pin "22") (pinfunction "22_22") (pintype "passive"))
    )
    (net (code "373") (name "Net-(D109-+)") (class "Default")
      (node (ref "D109") (pin "1") (pinfunction "+_1") (pintype "passive"))
      (node (ref "R429") (pin "1") (pinfunction "1_1") (pintype "passive"))
    )
    (net (code "374") (name "Net-(D109--)") (class "Default")
      (node (ref "D109") (pin "2") (pinfunction "-_2") (pintype "passive"))
      (node (ref "IC104") (pin "2") (pinfunction "OUT_2") (pintype "open_collector"))
      (node (ref "JP47") (pin "1") (pinfunction "1_1") (pintype "passive"))
      (node (ref "Q69") (pin "1") (pinfunction "G_1") (pintype "passive"))
      (node (ref "R445") (pin "2") (pinfunction "2_2") (pintype "passive"))
    )
    (net (code "375") (name "Net-(D112-+)") (class "Default")
      (node (ref "D112") (pin "1") (pinfunction "+_1") (pintype "passive"))
      (node (ref "R415") (pin "1") (pinfunction "1_1") (pintype "passive"))
    )
    (net (code "376") (name "Net-(D115-+)") (class "Default")
      (node (ref "D115") (pin "1") (pinfunction "+_1") (pintype "passive"))
      (node (ref "JP48") (pin "2") (pinfunction "2_2") (pintype "passive"))
    )
    (net (code "377") (name "Net-(D116-+)") (class "Default")
      (node (ref "D116") (pin "1") (pinfunction "+_1") (pintype "passive"))
      (node (ref "JP49") (pin "1") (pinfunction "1_1") (pintype "passive"))
    )
    (net (code "378") (name "Net-(D117--)") (class "Default")
      (node (ref "D117") (pin "2") (pinfunction "-_2") (pintype "passive"))
      (node (ref "Q64") (pin "2") (pinfunction "C_2") (pintype "passive"))
      (node (ref "START9") (pin "TP") (pinfunction "PP_TP") (pintype "input"))
      (node (ref "X28") (pin "5") (pinfunction "5_5") (pintype "passive"))
    )
    (net (code "379") (name "Net-(D118-+)") (class "Default")
      (node (ref "D118") (pin "1") (pinfunction "+_1") (pintype "passive"))
      (node (ref "R448") (pin "1") (pinfunction "1_1") (pintype "passive"))
    )
    (net (code "380") (name "Net-(D118--)") (class "Default")
      (node (ref "C97") (pin "2") (pinfunction "2_2") (pintype "passive"))
      (node (ref "D118") (pin "2") (pinfunction "-_2") (pintype "passive"))
      (node (ref "IC106") (pin "2") (pinfunction "TR_2") (pintype "input"))
      (node (ref "IC106") (pin "6") (pinfunction "THR_6") (pintype "input"))
      (node (ref "R446") (pin "1") (pinfunction "1_1") (pintype "passive"))
    )
    (net (code "381") (name "Net-(D120-PadC)") (class "Default")
      (node (ref "D120") (pin "C") (pinfunction "C_C") (pintype "passive"))
      (node (ref "R421") (pin "2") (pinfunction "2_2") (pintype "passive"))
      (node (ref "X28") (pin "22") (pinfunction "22_22") (pintype "passive"))
    )
    (net (code "382") (name "Net-(D121-+)") (class "Default")
      (node (ref "D121") (pin "1") (pinfunction "+_1") (pintype "passive"))
      (node (ref "R475") (pin "1") (pinfunction "1_1") (pintype "passive"))
    )
    (net (code "383") (name "Net-(D121--)") (class "Default")
      (node (ref "D121") (pin "2") (pinfunction "-_2") (pintype "passive"))
      (node (ref "IC115") (pin "2") (pinfunction "OUT_2") (pintype "open_collector"))
      (node (ref "JP52") (pin "1") (pinfunction "1_1") (pintype "passive"))
      (node (ref "Q76") (pin "1") (pinfunction "G_1") (pintype "passive"))
      (node (ref "R491") (pin "2") (pinfunction "2_2") (pintype "passive"))
    )
    (net (code "384") (name "Net-(D124-+)") (class "Default")
      (node (ref "D124") (pin "1") (pinfunction "+_1") (pintype "passive"))
      (node (ref "R461") (pin "1") (pinfunction "1_1") (pintype "passive"))
    )
    (net (code "385") (name "Net-(D127-+)") (class "Default")
      (node (ref "D127") (pin "1") (pinfunction "+_1") (pintype "passive"))
      (node (ref "JP53") (pin "2") (pinfunction "2_2") (pintype "passive"))
    )
    (net (code "386") (name "Net-(D128-+)") (class "Default")
      (node (ref "D128") (pin "1") (pinfunction "+_1") (pintype "passive"))
      (node (ref "JP54") (pin "1") (pinfunction "1_1") (pintype "passive"))
    )
    (net (code "387") (name "Net-(D129--)") (class "Default")
      (node (ref "D129") (pin "2") (pinfunction "-_2") (pintype "passive"))
      (node (ref "Q71") (pin "2") (pinfunction "C_2") (pintype "passive"))
      (node (ref "START10") (pin "TP") (pinfunction "PP_TP") (pintype "input"))
      (node (ref "X31") (pin "5") (pinfunction "5_5") (pintype "passive"))
    )
    (net (code "388") (name "Net-(D130-+)") (class "Default")
      (node (ref "D130") (pin "1") (pinfunction "+_1") (pintype "passive"))
      (node (ref "R494") (pin "1") (pinfunction "1_1") (pintype "passive"))
    )
    (net (code "389") (name "Net-(D130--)") (class "Default")
      (node (ref "C107") (pin "2") (pinfunction "2_2") (pintype "passive"))
      (node (ref "D130") (pin "2") (pinfunction "-_2") (pintype "passive"))
      (node (ref "IC117") (pin "2") (pinfunction "TR_2") (pintype "input"))
      (node (ref "IC117") (pin "6") (pinfunction "THR_6") (pintype "input"))
      (node (ref "R492") (pin "1") (pinfunction "1_1") (pintype "passive"))
    )
    (net (code "390") (name "Net-(D132-PadC)") (class "Default")
      (node (ref "D132") (pin "C") (pinfunction "C_C") (pintype "passive"))
      (node (ref "R467") (pin "2") (pinfunction "2_2") (pintype "passive"))
      (node (ref "X31") (pin "22") (pinfunction "22_22") (pintype "passive"))
    )
    (net (code "391") (name "Net-(D133-+)") (class "Default")
      (node (ref "D133") (pin "1") (pinfunction "+_1") (pintype "passive"))
      (node (ref "R521") (pin "1") (pinfunction "1_1") (pintype "passive"))
    )
    (net (code "392") (name "Net-(D133--)") (class "Default")
      (node (ref "D133") (pin "2") (pinfunction "-_2") (pintype "passive"))
      (node (ref "IC126") (pin "2") (pinfunction "OUT_2") (pintype "open_collector"))
      (node (ref "JP57") (pin "1") (pinfunction "1_1") (pintype "passive"))
      (node (ref "Q83") (pin "1") (pinfunction "G_1") (pintype "passive"))
      (node (ref "R537") (pin "2") (pinfunction "2_2") (pintype "passive"))
    )
    (net (code "393") (name "Net-(D136-+)") (class "Default")
      (node (ref "D136") (pin "1") (pinfunction "+_1") (pintype "passive"))
      (node (ref "R507") (pin "1") (pinfunction "1_1") (pintype "passive"))
    )
    (net (code "394") (name "Net-(D139-+)") (class "Default")
      (node (ref "D139") (pin "1") (pinfunction "+_1") (pintype "passive"))
      (node (ref "JP58") (pin "2") (pinfunction "2_2") (pintype "passive"))
    )
    (net (code "395") (name "Net-(D140-+)") (class "Default")
      (node (ref "D140") (pin "1") (pinfunction "+_1") (pintype "passive"))
      (node (ref "JP59") (pin "1") (pinfunction "1_1") (pintype "passive"))
    )
    (net (code "396") (name "Net-(D141--)") (class "Default")
      (node (ref "D141") (pin "2") (pinfunction "-_2") (pintype "passive"))
      (node (ref "Q78") (pin "2") (pinfunction "C_2") (pintype "passive"))
      (node (ref "START11") (pin "TP") (pinfunction "PP_TP") (pintype "input"))
      (node (ref "X34") (pin "5") (pinfunction "5_5") (pintype "passive"))
    )
    (net (code "397") (name "Net-(D142-+)") (class "Default")
      (node (ref "D142") (pin "1") (pinfunction "+_1") (pintype "passive"))
      (node (ref "R540") (pin "1") (pinfunction "1_1") (pintype "passive"))
    )
    (net (code "398") (name "Net-(D142--)") (class "Default")
      (node (ref "C117") (pin "2") (pinfunction "2_2") (pintype "passive"))
      (node (ref "D142") (pin "2") (pinfunction "-_2") (pintype "passive"))
      (node (ref "IC128") (pin "2") (pinfunction "TR_2") (pintype "input"))
      (node (ref "IC128") (pin "6") (pinfunction "THR_6") (pintype "input"))
      (node (ref "R538") (pin "1") (pinfunction "1_1") (pintype "passive"))
    )
    (net (code "399") (name "Net-(D144-PadC)") (class "Default")
      (node (ref "D144") (pin "C") (pinfunction "C_C") (pintype "passive"))
      (node (ref "R513") (pin "2") (pinfunction "2_2") (pintype "passive"))
      (node (ref "X34") (pin "22") (pinfunction "22_22") (pintype "passive"))
    )
    (net (code "400") (name "Net-(IC1A-+IN)") (class "Default")
      (node (ref "C1") (pin "1") (pinfunction "1_1") (pintype "passive"))
      (node (ref "IC1") (pin "3") (pinfunction "+IN_3") (pintype "input"))
      (node (ref "R5") (pin "1") (pinfunction "1_1") (pintype "passive"))
    )
    (net (code "401") (name "Net-(IC1A--IN)") (class "Default")
      (node (ref "IC1") (pin "2") (pinfunction "-IN_2") (pintype "input"))
      (node (ref "R7") (pin "2") (pinfunction "2_2") (pintype "passive"))
    )
    (net (code "402") (name "Net-(IC1A-OUT)") (class "Default")
      (node (ref "IC1") (pin "1") (pinfunction "OUT_1") (pintype "output"))
      (node (ref "R8") (pin "2") (pinfunction "2_2") (pintype "passive"))
    )
    (net (code "403") (name "Net-(IC1B-+IN)") (class "Default")
      (node (ref "IC1") (pin "5") (pinfunction "+IN_5") (pintype "input"))
      (node (ref "R12") (pin "2") (pinfunction "2_2") (pintype "passive"))
      (node (ref "R17") (pin "2") (pinfunction "2_2") (pintype "passive"))
    )
    (net (code "404") (name "Net-(IC1B--IN)") (class "Default")
      (node (ref "IC1") (pin "6") (pinfunction "-IN_6") (pintype "input"))
      (node (ref "R13") (pin "1") (pinfunction "1_1") (pintype "passive"))
      (node (ref "R14") (pin "2") (pinfunction "2_2") (pintype "passive"))
    )
    (net (code "405") (name "Net-(IC1B-OUT)") (class "Default")
      (node (ref "IC1") (pin "7") (pinfunction "OUT_7") (pintype "output"))
      (node (ref "R16") (pin "1") (pinfunction "1_1") (pintype "passive"))
      (node (ref "R17") (pin "1") (pinfunction "1_1") (pintype "passive"))
    )
    (net (code "406") (name "Net-(IC5A-A)") (class "Default")
      (node (ref "IC5") (pin "10") (pinfunction "A_10") (pintype "input"))
      (node (ref "R11") (pin "1") (pinfunction "1_1") (pintype "passive"))
      (node (ref "X1") (pin "4") (pinfunction "4_4") (pintype "passive"))
      (node (ref "X3") (pin "2") (pinfunction "S_2") (pintype "passive"))
    )
    (net (code "407") (name "Net-(IC5A-B)") (class "Default")
      (node (ref "IC5") (pin "13") (pinfunction "B_13") (pintype "input"))
      (node (ref "R10") (pin "1") (pinfunction "1_1") (pintype "passive"))
      (node (ref "X1") (pin "3") (pinfunction "3_3") (pintype "passive"))
      (node (ref "X3") (pin "3") (pinfunction "S_3") (pintype "passive"))
    )
    (net (code "408") (name "Net-(IC5A-C)") (class "Default")
      (node (ref "IC5") (pin "12") (pinfunction "C_12") (pintype "input"))
      (node (ref "R9") (pin "1") (pinfunction "1_1") (pintype "passive"))
      (node (ref "X1") (pin "2") (pinfunction "2_2") (pintype "passive"))
      (node (ref "X3") (pin "4") (pinfunction "S_4") (pintype "passive"))
    )
    (net (code "409") (name "Net-(IC5A-Q0)") (class "Default")
      (node (ref "IC5") (pin "3") (pinfunction "Q0_3") (pintype "output"))
      (node (ref "IC7") (pin "1") (pinfunction "I1_1") (pintype "input"))
      (node (ref "IC7") (pin "2") (pinfunction "I2_2") (pintype "input"))
      (node (ref "Q6") (pin "1") (pinfunction "G_1") (pintype "passive"))
    )
    (net (code "410") (name "Net-(IC5A-Q1)") (class "Default")
      (node (ref "IC5") (pin "14") (pinfunction "Q1_14") (pintype "output"))
      (node (ref "IC7") (pin "6") (pinfunction "I6_6") (pintype "input"))
    )
    (net (code "411") (name "Net-(IC5A-Q2)") (class "Default")
      (node (ref "IC5") (pin "2") (pinfunction "Q2_2") (pintype "output"))
      (node (ref "IC7") (pin "7") (pinfunction "I7_7") (pintype "input"))
    )
    (net (code "412") (name "Net-(IC5A-Q3)") (class "Default")
      (node (ref "IC5") (pin "15") (pinfunction "Q3_15") (pintype "output"))
      (node (ref "IC7") (pin "5") (pinfunction "I5_5") (pintype "input"))
    )
    (net (code "413") (name "Net-(IC5A-Q4)") (class "Default")
      (node (ref "IC5") (pin "1") (pinfunction "Q4_1") (pintype "output"))
      (node (ref "IC7") (pin "4") (pinfunction "I4_4") (pintype "input"))
    )
    (net (code "414") (name "Net-(IC5A-Q5)") (class "Default")
      (node (ref "IC5") (pin "6") (pinfunction "Q5_6") (pintype "output"))
      (node (ref "IC7") (pin "3") (pinfunction "I3_3") (pintype "input"))
    )
    (net (code "415") (name "Net-(IC7-O2)") (class "Default")
      (node (ref "IC7") (pin "15") (pinfunction "O2_15") (pintype "open_collector"))
      (node (ref "R28") (pin "1") (pinfunction "1_1") (pintype "passive"))
    )
    (net (code "416") (name "Net-(IC8A-+IN)") (class "Default")
      (node (ref "IC8") (pin "5") (pinfunction "+IN_5") (pintype "input"))
      (node (ref "R31") (pin "1") (pinfunction "1_1") (pintype "passive"))
      (node (ref "R32") (pin "2") (pinfunction "2_2") (pintype "passive"))
      (node (ref "R33") (pin "2") (pinfunction "2_2") (pintype "passive"))
    )
    (net (code "417") (name "Net-(IC8A--IN)") (class "Default")
      (node (ref "C8") (pin "1") (pinfunction "1_1") (pintype "passive"))
      (node (ref "IC8") (pin "4") (pinfunction "-IN_4") (pintype "input"))
      (node (ref "R30") (pin "1") (pinfunction "1_1") (pintype "passive"))
    )
    (net (code "418") (name "Net-(IC8B-+IN)") (class "Default")
      (node (ref "IC8") (pin "7") (pinfunction "+IN_7") (pintype "input"))
      (node (ref "R21") (pin "1") (pinfunction "1_1") (pintype "passive"))
      (node (ref "R22") (pin "1") (pinfunction "1_1") (pintype "passive"))
    )
    (net (code "419") (name "Net-(IC8B--IN)") (class "Default")
      (node (ref "IC8") (pin "6") (pinfunction "-IN_6") (pintype "input"))
      (node (ref "IC8") (pin "8") (pinfunction "-IN_8") (pintype "input"))
      (node (ref "R20") (pin "1") (pinfunction "1_1") (pintype "passive"))
    )
    (net (code "420") (name "Net-(IC8B-OUT)") (class "Default")
      (node (ref "IC8") (pin "1") (pinfunction "OUT_1") (pintype "open_collector"))
      (node (ref "R24") (pin "2") (pinfunction "2_2") (pintype "passive"))
      (node (ref "R25") (pin "2") (pinfunction "2_2") (pintype "passive"))
    )
    (net (code "421") (name "Net-(IC8C-+IN)") (class "Default")
      (node (ref "C5") (pin "1") (pinfunction "1_1") (pintype "passive"))
      (node (ref "IC8") (pin "9") (pinfunction "+IN_9") (pintype "input"))
      (node (ref "R22") (pin "2") (pinfunction "2_2") (pintype "passive"))
      (node (ref "R23") (pin "2") (pinfunction "2_2") (pintype "passive"))
    )
    (net (code "422") (name "Net-(IC8C-OUT)") (class "Default")
      (node (ref "C6") (pin "2") (pinfunction "2_2") (pintype "passive"))
      (node (ref "IC8") (pin "14") (pinfunction "OUT_14") (pintype "open_collector"))
      (node (ref "R26") (pin "2") (pinfunction "2_2") (pintype "passive"))
    )
    (net (code "423") (name "Net-(IC9-ADJ)") (class "Default")
      (node (ref "IC9") (pin "1") (pinfunction "ADJ_1") (pintype "input"))
      (node (ref "R20") (pin "2") (pinfunction "2_2") (pintype "passive"))
      (node (ref "R34") (pin "1") (pinfunction "1_1") (pintype "passive"))
      (node (ref "X1") (pin "7") (pinfunction "7_7") (pintype "passive"))
    )
    (net (code "424") (name "Net-(IC9-VI)") (class "Default")
      (node (ref "IC9") (pin "3") (pinfunction "VI_3") (pintype "input"))
      (node (ref "Q5") (pin "2") (pinfunction "C_2") (pintype "passive"))
    )
    (net (code "425") (name "Net-(IC9-VO)") (class "Default")
      (node (ref "IC9") (pin "2") (pinfunction "VO_2") (pintype "passive"))
      (node (ref "R34") (pin "2") (pinfunction "2_2") (pintype "passive"))
    )
    (net (code "426") (name "Net-(IC10-CV)") (class "Default")
      (node (ref "IC10") (pin "5") (pinfunction "CV_5") (pintype "input"))
      (node (ref "R44") (pin "2") (pinfunction "2_2") (pintype "passive"))
    )
    (net (code "427") (name "Net-(IC10-Q)") (class "Default")
      (node (ref "IC10") (pin "3") (pinfunction "Q_3") (pintype "output"))
      (node (ref "IC11") (pin "12") (pinfunction "A_12") (pintype "input"))
      (node (ref "R44") (pin "1") (pinfunction "1_1") (pintype "passive"))
    )
    (net (code "428") (name "Net-(IC11B-B)") (class "Default")
      (node (ref "IC11") (pin "11") (pinfunction "B_11") (pintype "input"))
      (node (ref "IC11") (pin "9") (pinfunction "~{Q}_9") (pintype "output"))
      (node (ref "R46") (pin "2") (pinfunction "2_2") (pintype "passive"))
    )
    (net (code "429") (name "Net-(IC11B-T2)") (class "Default")
      (node (ref "C10") (pin "1") (pinfunction "1_1") (pintype "passive"))
      (node (ref "IC11") (pin "14") (pinfunction "T2_14") (pintype "input"))
      (node (ref "R45") (pin "1") (pinfunction "1_1") (pintype "passive"))
    )
    (net (code "430") (name "Net-(IC12A-A)") (class "Default")
      (node (ref "IC12") (pin "10") (pinfunction "A_10") (pintype "input"))
      (node (ref "R52") (pin "1") (pinfunction "1_1") (pintype "passive"))
      (node (ref "X4") (pin "4") (pinfunction "4_4") (pintype "passive"))
      (node (ref "X5") (pin "2") (pinfunction "S_2") (pintype "passive"))
    )
    (net (code "431") (name "Net-(IC12A-B)") (class "Default")
      (node (ref "IC12") (pin "13") (pinfunction "B_13") (pintype "input"))
      (node (ref "R51") (pin "1") (pinfunction "1_1") (pintype "passive"))
      (node (ref "X4") (pin "3") (pinfunction "3_3") (pintype "passive"))
      (node (ref "X5") (pin "3") (pinfunction "S_3") (pintype "passive"))
    )
    (net (code "432") (name "Net-(IC12A-C)") (class "Default")
      (node (ref "IC12") (pin "12") (pinfunction "C_12") (pintype "input"))
      (node (ref "R50") (pin "1") (pinfunction "1_1") (pintype "passive"))
      (node (ref "X4") (pin "2") (pinfunction "2_2") (pintype "passive"))
      (node (ref "X5") (pin "4") (pinfunction "S_4") (pintype "passive"))
    )
    (net (code "433") (name "Net-(IC12A-Q0)") (class "Default")
      (node (ref "IC12") (pin "3") (pinfunction "Q0_3") (pintype "output"))
      (node (ref "IC15") (pin "1") (pinfunction "I1_1") (pintype "input"))
      (node (ref "IC15") (pin "2") (pinfunction "I2_2") (pintype "input"))
      (node (ref "Q14") (pin "1") (pinfunction "G_1") (pintype "passive"))
    )
    (net (code "434") (name "Net-(IC12A-Q1)") (class "Default")
      (node (ref "IC12") (pin "14") (pinfunction "Q1_14") (pintype "output"))
      (node (ref "IC15") (pin "6") (pinfunction "I6_6") (pintype "input"))
    )
    (net (code "435") (name "Net-(IC12A-Q2)") (class "Default")
      (node (ref "IC12") (pin "2") (pinfunction "Q2_2") (pintype "output"))
      (node (ref "IC15") (pin "7") (pinfunction "I7_7") (pintype "input"))
    )
    (net (code "436") (name "Net-(IC12A-Q3)") (class "Default")
      (node (ref "IC12") (pin "15") (pinfunction "Q3_15") (pintype "output"))
      (node (ref "IC15") (pin "5") (pinfunction "I5_5") (pintype "input"))
    )
    (net (code "437") (name "Net-(IC12A-Q4)") (class "Default")
      (node (ref "IC12") (pin "1") (pinfunction "Q4_1") (pintype "output"))
      (node (ref "IC15") (pin "4") (pinfunction "I4_4") (pintype "input"))
    )
    (net (code "438") (name "Net-(IC12A-Q5)") (class "Default")
      (node (ref "IC12") (pin "6") (pinfunction "Q5_6") (pintype "output"))
      (node (ref "IC15") (pin "3") (pinfunction "I3_3") (pintype "input"))
    )
    (net (code "439") (name "Net-(IC14-ADJ)") (class "Default")
      (node (ref "IC14") (pin "1") (pinfunction "ADJ_1") (pintype "input"))
      (node (ref "R48") (pin "1") (pinfunction "1_1") (pintype "passive"))
      (node (ref "R55") (pin "2") (pinfunction "2_2") (pintype "passive"))
      (node (ref "X4") (pin "7") (pinfunction "7_7") (pintype "passive"))
    )
    (net (code "440") (name "Net-(IC14-VI)") (class "Default")
      (node (ref "IC14") (pin "3") (pinfunction "VI_3") (pintype "input"))
      (node (ref "Q11") (pin "2") (pinfunction "C_2") (pintype "passive"))
    )
    (net (code "441") (name "Net-(IC14-VO)") (class "Default")
      (node (ref "IC14") (pin "2") (pinfunction "VO_2") (pintype "passive"))
      (node (ref "R48") (pin "2") (pinfunction "2_2") (pintype "passive"))
    )
    (net (code "442") (name "Net-(IC15-O2)") (class "Default")
      (node (ref "IC15") (pin "15") (pinfunction "O2_15") (pintype "open_collector"))
      (node (ref "R70") (pin "1") (pinfunction "1_1") (pintype "passive"))
    )
    (net (code "443") (name "Net-(IC16A-+IN)") (class "Default")
      (node (ref "IC16") (pin "5") (pinfunction "+IN_5") (pintype "input"))
      (node (ref "R59") (pin "1") (pinfunction "1_1") (pintype "passive"))
      (node (ref "R60") (pin "2") (pinfunction "2_2") (pintype "passive"))
      (node (ref "R61") (pin "2") (pinfunction "2_2") (pintype "passive"))
    )
    (net (code "444") (name "Net-(IC16A--IN)") (class "Default")
      (node (ref "C12") (pin "1") (pinfunction "1_1") (pintype "passive"))
      (node (ref "IC16") (pin "4") (pinfunction "-IN_4") (pintype "input"))
      (node (ref "R58") (pin "1") (pinfunction "1_1") (pintype "passive"))
    )
    (net (code "445") (name "Net-(IC16B-+IN)") (class "Default")
      (node (ref "IC16") (pin "7") (pinfunction "+IN_7") (pintype "input"))
      (node (ref "R56") (pin "1") (pinfunction "1_1") (pintype "passive"))
      (node (ref "R73") (pin "1") (pinfunction "1_1") (pintype "passive"))
    )
    (net (code "446") (name "Net-(IC16B--IN)") (class "Default")
      (node (ref "IC16") (pin "6") (pinfunction "-IN_6") (pintype "input"))
      (node (ref "IC16") (pin "8") (pinfunction "-IN_8") (pintype "input"))
      (node (ref "R55") (pin "1") (pinfunction "1_1") (pintype "passive"))
    )
    (net (code "447") (name "Net-(IC16B-OUT)") (class "Default")
      (node (ref "IC16") (pin "1") (pinfunction "OUT_1") (pintype "open_collector"))
      (node (ref "R57") (pin "2") (pinfunction "2_2") (pintype "passive"))
      (node (ref "R62") (pin "2") (pinfunction "2_2") (pintype "passive"))
    )
    (net (code "448") (name "Net-(IC16C-+IN)") (class "Default")
      (node (ref "C15") (pin "1") (pinfunction "1_1") (pintype "passive"))
      (node (ref "IC16") (pin "9") (pinfunction "+IN_9") (pintype "input"))
      (node (ref "R64") (pin "2") (pinfunction "2_2") (pintype "passive"))
      (node (ref "R73") (pin "2") (pinfunction "2_2") (pintype "passive"))
    )
    (net (code "449") (name "Net-(IC16C-OUT)") (class "Default")
      (node (ref "C16") (pin "2") (pinfunction "2_2") (pintype "passive"))
      (node (ref "IC16") (pin "14") (pinfunction "OUT_14") (pintype "open_collector"))
      (node (ref "R63") (pin "2") (pinfunction "2_2") (pintype "passive"))
    )
    (net (code "450") (name "Net-(IC18-CV)") (class "Default")
      (node (ref "IC18") (pin "5") (pinfunction "CV_5") (pintype "input"))
      (node (ref "R79") (pin "2") (pinfunction "2_2") (pintype "passive"))
    )
    (net (code "451") (name "Net-(IC18-Q)") (class "Default")
      (node (ref "IC18") (pin "3") (pinfunction "Q_3") (pintype "output"))
      (node (ref "IC19") (pin "12") (pinfunction "A_12") (pintype "input"))
      (node (ref "R79") (pin "1") (pinfunction "1_1") (pintype "passive"))
    )
    (net (code "452") (name "Net-(IC19B-B)") (class "Default")
      (node (ref "IC19") (pin "11") (pinfunction "B_11") (pintype "input"))
      (node (ref "IC19") (pin "9") (pinfunction "~{Q}_9") (pintype "output"))
      (node (ref "R85") (pin "2") (pinfunction "2_2") (pintype "passive"))
    )
    (net (code "453") (name "Net-(IC19B-T2)") (class "Default")
      (node (ref "C19") (pin "1") (pinfunction "1_1") (pintype "passive"))
      (node (ref "IC19") (pin "14") (pinfunction "T2_14") (pintype "input"))
      (node (ref "R83") (pin "1") (pinfunction "1_1") (pintype "passive"))
    )
    (net (code "454") (name "Net-(IC21A-+IN)") (class "Default")
      (node (ref "C14") (pin "1") (pinfunction "1_1") (pintype "passive"))
      (node (ref "IC21") (pin "3") (pinfunction "+IN_3") (pintype "input"))
      (node (ref "R53") (pin "1") (pinfunction "1_1") (pintype "passive"))
    )
    (net (code "455") (name "Net-(IC21A--IN)") (class "Default")
      (node (ref "IC21") (pin "2") (pinfunction "-IN_2") (pintype "input"))
      (node (ref "R54") (pin "2") (pinfunction "2_2") (pintype "passive"))
    )
    (net (code "456") (name "Net-(IC21A-OUT)") (class "Default")
      (node (ref "IC21") (pin "1") (pinfunction "OUT_1") (pintype "output"))
      (node (ref "R86") (pin "2") (pinfunction "2_2") (pintype "passive"))
    )
    (net (code "457") (name "Net-(IC21B-+IN)") (class "Default")
      (node (ref "IC21") (pin "5") (pinfunction "+IN_5") (pintype "input"))
      (node (ref "R87") (pin "2") (pinfunction "2_2") (pintype "passive"))
      (node (ref "R88") (pin "2") (pinfunction "2_2") (pintype "passive"))
    )
    (net (code "458") (name "Net-(IC21B--IN)") (class "Default")
      (node (ref "IC21") (pin "6") (pinfunction "-IN_6") (pintype "input"))
      (node (ref "R89") (pin "1") (pinfunction "1_1") (pintype "passive"))
      (node (ref "R90") (pin "2") (pinfunction "2_2") (pintype "passive"))
    )
    (net (code "459") (name "Net-(IC21B-OUT)") (class "Default")
      (node (ref "IC21") (pin "7") (pinfunction "OUT_7") (pintype "output"))
      (node (ref "R74") (pin "1") (pinfunction "1_1") (pintype "passive"))
      (node (ref "R88") (pin "1") (pinfunction "1_1") (pintype "passive"))
    )
    (net (code "460") (name "Net-(IC23A-A)") (class "Default")
      (node (ref "IC23") (pin "10") (pinfunction "A_10") (pintype "input"))
      (node (ref "R98") (pin "1") (pinfunction "1_1") (pintype "passive"))
      (node (ref "X7") (pin "4") (pinfunction "4_4") (pintype "passive"))
      (node (ref "X8") (pin "2") (pinfunction "S_2") (pintype "passive"))
    )
    (net (code "461") (name "Net-(IC23A-B)") (class "Default")
      (node (ref "IC23") (pin "13") (pinfunction "B_13") (pintype "input"))
      (node (ref "R97") (pin "1") (pinfunction "1_1") (pintype "passive"))
      (node (ref "X7") (pin "3") (pinfunction "3_3") (pintype "passive"))
      (node (ref "X8") (pin "3") (pinfunction "S_3") (pintype "passive"))
    )
    (net (code "462") (name "Net-(IC23A-C)") (class "Default")
      (node (ref "IC23") (pin "12") (pinfunction "C_12") (pintype "input"))
      (node (ref "R96") (pin "1") (pinfunction "1_1") (pintype "passive"))
      (node (ref "X7") (pin "2") (pinfunction "2_2") (pintype "passive"))
      (node (ref "X8") (pin "4") (pinfunction "S_4") (pintype "passive"))
    )
    (net (code "463") (name "Net-(IC23A-Q0)") (class "Default")
      (node (ref "IC23") (pin "3") (pinfunction "Q0_3") (pintype "output"))
      (node (ref "IC26") (pin "1") (pinfunction "I1_1") (pintype "input"))
      (node (ref "IC26") (pin "2") (pinfunction "I2_2") (pintype "input"))
      (node (ref "Q21") (pin "1") (pinfunction "G_1") (pintype "passive"))
    )
    (net (code "464") (name "Net-(IC23A-Q1)") (class "Default")
      (node (ref "IC23") (pin "14") (pinfunction "Q1_14") (pintype "output"))
      (node (ref "IC26") (pin "6") (pinfunction "I6_6") (pintype "input"))
    )
    (net (code "465") (name "Net-(IC23A-Q2)") (class "Default")
      (node (ref "IC23") (pin "2") (pinfunction "Q2_2") (pintype "output"))
      (node (ref "IC26") (pin "7") (pinfunction "I7_7") (pintype "input"))
    )
    (net (code "466") (name "Net-(IC23A-Q3)") (class "Default")
      (node (ref "IC23") (pin "15") (pinfunction "Q3_15") (pintype "output"))
      (node (ref "IC26") (pin "5") (pinfunction "I5_5") (pintype "input"))
    )
    (net (code "467") (name "Net-(IC23A-Q4)") (class "Default")
      (node (ref "IC23") (pin "1") (pinfunction "Q4_1") (pintype "output"))
      (node (ref "IC26") (pin "4") (pinfunction "I4_4") (pintype "input"))
    )
    (net (code "468") (name "Net-(IC23A-Q5)") (class "Default")
      (node (ref "IC23") (pin "6") (pinfunction "Q5_6") (pintype "output"))
      (node (ref "IC26") (pin "3") (pinfunction "I3_3") (pintype "input"))
    )
    (net (code "469") (name "Net-(IC25-ADJ)") (class "Default")
      (node (ref "IC25") (pin "1") (pinfunction "ADJ_1") (pintype "input"))
      (node (ref "R101") (pin "2") (pinfunction "2_2") (pintype "passive"))
      (node (ref "R94") (pin "1") (pinfunction "1_1") (pintype "passive"))
      (node (ref "X7") (pin "7") (pinfunction "7_7") (pintype "passive"))
    )
    (net (code "470") (name "Net-(IC25-VI)") (class "Default")
      (node (ref "IC25") (pin "3") (pinfunction "VI_3") (pintype "input"))
      (node (ref "Q18") (pin "2") (pinfunction "C_2") (pintype "passive"))
    )
    (net (code "471") (name "Net-(IC25-VO)") (class "Default")
      (node (ref "IC25") (pin "2") (pinfunction "VO_2") (pintype "passive"))
      (node (ref "R94") (pin "2") (pinfunction "2_2") (pintype "passive"))
    )
    (net (code "472") (name "Net-(IC26-O2)") (class "Default")
      (node (ref "IC26") (pin "15") (pinfunction "O2_15") (pintype "open_collector"))
      (node (ref "R116") (pin "1") (pinfunction "1_1") (pintype "passive"))
    )
    (net (code "473") (name "Net-(IC27A-+IN)") (class "Default")
      (node (ref "IC27") (pin "5") (pinfunction "+IN_5") (pintype "input"))
      (node (ref "R105") (pin "1") (pinfunction "1_1") (pintype "passive"))
      (node (ref "R106") (pin "2") (pinfunction "2_2") (pintype "passive"))
      (node (ref "R107") (pin "2") (pinfunction "2_2") (pintype "passive"))
    )
    (net (code "474") (name "Net-(IC27A--IN)") (class "Default")
      (node (ref "C22") (pin "1") (pinfunction "1_1") (pintype "passive"))
      (node (ref "IC27") (pin "4") (pinfunction "-IN_4") (pintype "input"))
      (node (ref "R104") (pin "1") (pinfunction "1_1") (pintype "passive"))
    )
    (net (code "475") (name "Net-(IC27B-+IN)") (class "Default")
      (node (ref "IC27") (pin "7") (pinfunction "+IN_7") (pintype "input"))
      (node (ref "R102") (pin "1") (pinfunction "1_1") (pintype "passive"))
      (node (ref "R119") (pin "1") (pinfunction "1_1") (pintype "passive"))
    )
    (net (code "476") (name "Net-(IC27B--IN)") (class "Default")
      (node (ref "IC27") (pin "6") (pinfunction "-IN_6") (pintype "input"))
      (node (ref "IC27") (pin "8") (pinfunction "-IN_8") (pintype "input"))
      (node (ref "R101") (pin "1") (pinfunction "1_1") (pintype "passive"))
    )
    (net (code "477") (name "Net-(IC27B-OUT)") (class "Default")
      (node (ref "IC27") (pin "1") (pinfunction "OUT_1") (pintype "open_collector"))
      (node (ref "R103") (pin "2") (pinfunction "2_2") (pintype "passive"))
      (node (ref "R108") (pin "2") (pinfunction "2_2") (pintype "passive"))
    )
    (net (code "478") (name "Net-(IC27C-+IN)") (class "Default")
      (node (ref "C25") (pin "1") (pinfunction "1_1") (pintype "passive"))
      (node (ref "IC27") (pin "9") (pinfunction "+IN_9") (pintype "input"))
      (node (ref "R110") (pin "2") (pinfunction "2_2") (pintype "passive"))
      (node (ref "R119") (pin "2") (pinfunction "2_2") (pintype "passive"))
    )
    (net (code "479") (name "Net-(IC27C-OUT)") (class "Default")
      (node (ref "C26") (pin "2") (pinfunction "2_2") (pintype "passive"))
      (node (ref "IC27") (pin "14") (pinfunction "OUT_14") (pintype "open_collector"))
      (node (ref "R109") (pin "2") (pinfunction "2_2") (pintype "passive"))
    )
    (net (code "480") (name "Net-(IC29-CV)") (class "Default")
      (node (ref "IC29") (pin "5") (pinfunction "CV_5") (pintype "input"))
      (node (ref "R125") (pin "2") (pinfunction "2_2") (pintype "passive"))
    )
    (net (code "481") (name "Net-(IC29-Q)") (class "Default")
      (node (ref "IC29") (pin "3") (pinfunction "Q_3") (pintype "output"))
      (node (ref "IC30") (pin "12") (pinfunction "A_12") (pintype "input"))
      (node (ref "R125") (pin "1") (pinfunction "1_1") (pintype "passive"))
    )
    (net (code "482") (name "Net-(IC30B-B)") (class "Default")
      (node (ref "IC30") (pin "11") (pinfunction "B_11") (pintype "input"))
      (node (ref "IC30") (pin "9") (pinfunction "~{Q}_9") (pintype "output"))
      (node (ref "R131") (pin "2") (pinfunction "2_2") (pintype "passive"))
    )
    (net (code "483") (name "Net-(IC30B-T2)") (class "Default")
      (node (ref "C29") (pin "1") (pinfunction "1_1") (pintype "passive"))
      (node (ref "IC30") (pin "14") (pinfunction "T2_14") (pintype "input"))
      (node (ref "R129") (pin "1") (pinfunction "1_1") (pintype "passive"))
    )
    (net (code "484") (name "Net-(IC32A-+IN)") (class "Default")
      (node (ref "C24") (pin "1") (pinfunction "1_1") (pintype "passive"))
      (node (ref "IC32") (pin "3") (pinfunction "+IN_3") (pintype "input"))
      (node (ref "R99") (pin "1") (pinfunction "1_1") (pintype "passive"))
    )
    (net (code "485") (name "Net-(IC32A--IN)") (class "Default")
      (node (ref "IC32") (pin "2") (pinfunction "-IN_2") (pintype "input"))
      (node (ref "R100") (pin "2") (pinfunction "2_2") (pintype "passive"))
    )
    (net (code "486") (name "Net-(IC32A-OUT)") (class "Default")
      (node (ref "IC32") (pin "1") (pinfunction "OUT_1") (pintype "output"))
      (node (ref "R132") (pin "2") (pinfunction "2_2") (pintype "passive"))
    )
    (net (code "487") (name "Net-(IC32B-+IN)") (class "Default")
      (node (ref "IC32") (pin "5") (pinfunction "+IN_5") (pintype "input"))
      (node (ref "R133") (pin "2") (pinfunction "2_2") (pintype "passive"))
      (node (ref "R134") (pin "2") (pinfunction "2_2") (pintype "passive"))
    )
    (net (code "488") (name "Net-(IC32B--IN)") (class "Default")
      (node (ref "IC32") (pin "6") (pinfunction "-IN_6") (pintype "input"))
      (node (ref "R135") (pin "1") (pinfunction "1_1") (pintype "passive"))
      (node (ref "R136") (pin "2") (pinfunction "2_2") (pintype "passive"))
    )
    (net (code "489") (name "Net-(IC32B-OUT)") (class "Default")
      (node (ref "IC32") (pin "7") (pinfunction "OUT_7") (pintype "output"))
      (node (ref "R120") (pin "1") (pinfunction "1_1") (pintype "passive"))
      (node (ref "R134") (pin "1") (pinfunction "1_1") (pintype "passive"))
    )
    (net (code "490") (name "Net-(IC34A-A)") (class "Default")
      (node (ref "IC34") (pin "10") (pinfunction "A_10") (pintype "input"))
      (node (ref "R144") (pin "1") (pinfunction "1_1") (pintype "passive"))
      (node (ref "X10") (pin "4") (pinfunction "4_4") (pintype "passive"))
      (node (ref "X11") (pin "2") (pinfunction "S_2") (pintype "passive"))
    )
    (net (code "491") (name "Net-(IC34A-B)") (class "Default")
      (node (ref "IC34") (pin "13") (pinfunction "B_13") (pintype "input"))
      (node (ref "R143") (pin "1") (pinfunction "1_1") (pintype "passive"))
      (node (ref "X10") (pin "3") (pinfunction "3_3") (pintype "passive"))
      (node (ref "X11") (pin "3") (pinfunction "S_3") (pintype "passive"))
    )
    (net (code "492") (name "Net-(IC34A-C)") (class "Default")
      (node (ref "IC34") (pin "12") (pinfunction "C_12") (pintype "input"))
      (node (ref "R142") (pin "1") (pinfunction "1_1") (pintype "passive"))
      (node (ref "X10") (pin "2") (pinfunction "2_2") (pintype "passive"))
      (node (ref "X11") (pin "4") (pinfunction "S_4") (pintype "passive"))
    )
    (net (code "493") (name "Net-(IC34A-Q0)") (class "Default")
      (node (ref "IC34") (pin "3") (pinfunction "Q0_3") (pintype "output"))
      (node (ref "IC37") (pin "1") (pinfunction "I1_1") (pintype "input"))
      (node (ref "IC37") (pin "2") (pinfunction "I2_2") (pintype "input"))
      (node (ref "Q28") (pin "1") (pinfunction "G_1") (pintype "passive"))
    )
    (net (code "494") (name "Net-(IC34A-Q1)") (class "Default")
      (node (ref "IC34") (pin "14") (pinfunction "Q1_14") (pintype "output"))
      (node (ref "IC37") (pin "6") (pinfunction "I6_6") (pintype "input"))
    )
    (net (code "495") (name "Net-(IC34A-Q2)") (class "Default")
      (node (ref "IC34") (pin "2") (pinfunction "Q2_2") (pintype "output"))
      (node (ref "IC37") (pin "7") (pinfunction "I7_7") (pintype "input"))
    )
    (net (code "496") (name "Net-(IC34A-Q3)") (class "Default")
      (node (ref "IC34") (pin "15") (pinfunction "Q3_15") (pintype "output"))
      (node (ref "IC37") (pin "5") (pinfunction "I5_5") (pintype "input"))
    )
    (net (code "497") (name "Net-(IC34A-Q4)") (class "Default")
      (node (ref "IC34") (pin "1") (pinfunction "Q4_1") (pintype "output"))
      (node (ref "IC37") (pin "4") (pinfunction "I4_4") (pintype "input"))
    )
    (net (code "498") (name "Net-(IC34A-Q5)") (class "Default")
      (node (ref "IC34") (pin "6") (pinfunction "Q5_6") (pintype "output"))
      (node (ref "IC37") (pin "3") (pinfunction "I3_3") (pintype "input"))
    )
    (net (code "499") (name "Net-(IC36-ADJ)") (class "Default")
      (node (ref "IC36") (pin "1") (pinfunction "ADJ_1") (pintype "input"))
      (node (ref "R140") (pin "1") (pinfunction "1_1") (pintype "passive"))
      (node (ref "R147") (pin "2") (pinfunction "2_2") (pintype "passive"))
      (node (ref "X10") (pin "7") (pinfunction "7_7") (pintype "passive"))
    )
    (net (code "500") (name "Net-(IC36-VI)") (class "Default")
      (node (ref "IC36") (pin "3") (pinfunction "VI_3") (pintype "input"))
      (node (ref "Q25") (pin "2") (pinfunction "C_2") (pintype "passive"))
    )
    (net (code "501") (name "Net-(IC36-VO)") (class "Default")
      (node (ref "IC36") (pin "2") (pinfunction "VO_2") (pintype "passive"))
      (node (ref "R140") (pin "2") (pinfunction "2_2") (pintype "passive"))
    )
    (net (code "502") (name "Net-(IC37-O2)") (class "Default")
      (node (ref "IC37") (pin "15") (pinfunction "O2_15") (pintype "open_collector"))
      (node (ref "R162") (pin "1") (pinfunction "1_1") (pintype "passive"))
    )
    (net (code "503") (name "Net-(IC38A-+IN)") (class "Default")
      (node (ref "IC38") (pin "5") (pinfunction "+IN_5") (pintype "input"))
      (node (ref "R151") (pin "1") (pinfunction "1_1") (pintype "passive"))
      (node (ref "R152") (pin "2") (pinfunction "2_2") (pintype "passive"))
      (node (ref "R153") (pin "2") (pinfunction "2_2") (pintype "passive"))
    )
    (net (code "504") (name "Net-(IC38A--IN)") (class "Default")
      (node (ref "C32") (pin "1") (pinfunction "1_1") (pintype "passive"))
      (node (ref "IC38") (pin "4") (pinfunction "-IN_4") (pintype "input"))
      (node (ref "R150") (pin "1") (pinfunction "1_1") (pintype "passive"))
    )
    (net (code "505") (name "Net-(IC38B-+IN)") (class "Default")
      (node (ref "IC38") (pin "7") (pinfunction "+IN_7") (pintype "input"))
      (node (ref "R148") (pin "1") (pinfunction "1_1") (pintype "passive"))
      (node (ref "R165") (pin "1") (pinfunction "1_1") (pintype "passive"))
    )
    (net (code "506") (name "Net-(IC38B--IN)") (class "Default")
      (node (ref "IC38") (pin "6") (pinfunction "-IN_6") (pintype "input"))
      (node (ref "IC38") (pin "8") (pinfunction "-IN_8") (pintype "input"))
      (node (ref "R147") (pin "1") (pinfunction "1_1") (pintype "passive"))
    )
    (net (code "507") (name "Net-(IC38B-OUT)") (class "Default")
      (node (ref "IC38") (pin "1") (pinfunction "OUT_1") (pintype "open_collector"))
      (node (ref "R149") (pin "2") (pinfunction "2_2") (pintype "passive"))
      (node (ref "R154") (pin "2") (pinfunction "2_2") (pintype "passive"))
    )
    (net (code "508") (name "Net-(IC38C-+IN)") (class "Default")
      (node (ref "C35") (pin "1") (pinfunction "1_1") (pintype "passive"))
      (node (ref "IC38") (pin "9") (pinfunction "+IN_9") (pintype "input"))
      (node (ref "R156") (pin "2") (pinfunction "2_2") (pintype "passive"))
      (node (ref "R165") (pin "2") (pinfunction "2_2") (pintype "passive"))
    )
    (net (code "509") (name "Net-(IC38C-OUT)") (class "Default")
      (node (ref "C36") (pin "2") (pinfunction "2_2") (pintype "passive"))
      (node (ref "IC38") (pin "14") (pinfunction "OUT_14") (pintype "open_collector"))
      (node (ref "R155") (pin "2") (pinfunction "2_2") (pintype "passive"))
    )
    (net (code "510") (name "Net-(IC40-CV)") (class "Default")
      (node (ref "IC40") (pin "5") (pinfunction "CV_5") (pintype "input"))
      (node (ref "R171") (pin "2") (pinfunction "2_2") (pintype "passive"))
    )
    (net (code "511") (name "Net-(IC40-Q)") (class "Default")
      (node (ref "IC40") (pin "3") (pinfunction "Q_3") (pintype "output"))
      (node (ref "IC41") (pin "12") (pinfunction "A_12") (pintype "input"))
      (node (ref "R171") (pin "1") (pinfunction "1_1") (pintype "passive"))
    )
    (net (code "512") (name "Net-(IC41B-B)") (class "Default")
      (node (ref "IC41") (pin "11") (pinfunction "B_11") (pintype "input"))
      (node (ref "IC41") (pin "9") (pinfunction "~{Q}_9") (pintype "output"))
      (node (ref "R177") (pin "2") (pinfunction "2_2") (pintype "passive"))
    )
    (net (code "513") (name "Net-(IC41B-T2)") (class "Default")
      (node (ref "C39") (pin "1") (pinfunction "1_1") (pintype "passive"))
      (node (ref "IC41") (pin "14") (pinfunction "T2_14") (pintype "input"))
      (node (ref "R175") (pin "1") (pinfunction "1_1") (pintype "passive"))
    )
    (net (code "514") (name "Net-(IC43A-+IN)") (class "Default")
      (node (ref "C34") (pin "1") (pinfunction "1_1") (pintype "passive"))
      (node (ref "IC43") (pin "3") (pinfunction "+IN_3") (pintype "input"))
      (node (ref "R145") (pin "1") (pinfunction "1_1") (pintype "passive"))
    )
    (net (code "515") (name "Net-(IC43A--IN)") (class "Default")
      (node (ref "IC43") (pin "2") (pinfunction "-IN_2") (pintype "input"))
      (node (ref "R146") (pin "2") (pinfunction "2_2") (pintype "passive"))
    )
    (net (code "516") (name "Net-(IC43A-OUT)") (class "Default")
      (node (ref "IC43") (pin "1") (pinfunction "OUT_1") (pintype "output"))
      (node (ref "R178") (pin "2") (pinfunction "2_2") (pintype "passive"))
    )
    (net (code "517") (name "Net-(IC43B-+IN)") (class "Default")
      (node (ref "IC43") (pin "5") (pinfunction "+IN_5") (pintype "input"))
      (node (ref "R179") (pin "2") (pinfunction "2_2") (pintype "passive"))
      (node (ref "R180") (pin "2") (pinfunction "2_2") (pintype "passive"))
    )
    (net (code "518") (name "Net-(IC43B--IN)") (class "Default")
      (node (ref "IC43") (pin "6") (pinfunction "-IN_6") (pintype "input"))
      (node (ref "R181") (pin "1") (pinfunction "1_1") (pintype "passive"))
      (node (ref "R182") (pin "2") (pinfunction "2_2") (pintype "passive"))
    )
    (net (code "519") (name "Net-(IC43B-OUT)") (class "Default")
      (node (ref "IC43") (pin "7") (pinfunction "OUT_7") (pintype "output"))
      (node (ref "R166") (pin "1") (pinfunction "1_1") (pintype "passive"))
      (node (ref "R180") (pin "1") (pinfunction "1_1") (pintype "passive"))
    )
    (net (code "520") (name "Net-(IC45A-A)") (class "Default")
      (node (ref "IC45") (pin "10") (pinfunction "A_10") (pintype "input"))
      (node (ref "R190") (pin "1") (pinfunction "1_1") (pintype "passive"))
      (node (ref "X13") (pin "4") (pinfunction "4_4") (pintype "passive"))
      (node (ref "X14") (pin "2") (pinfunction "S_2") (pintype "passive"))
    )
    (net (code "521") (name "Net-(IC45A-B)") (class "Default")
      (node (ref "IC45") (pin "13") (pinfunction "B_13") (pintype "input"))
      (node (ref "R189") (pin "1") (pinfunction "1_1") (pintype "passive"))
      (node (ref "X13") (pin "3") (pinfunction "3_3") (pintype "passive"))
      (node (ref "X14") (pin "3") (pinfunction "S_3") (pintype "passive"))
    )
    (net (code "522") (name "Net-(IC45A-C)") (class "Default")
      (node (ref "IC45") (pin "12") (pinfunction "C_12") (pintype "input"))
      (node (ref "R188") (pin "1") (pinfunction "1_1") (pintype "passive"))
      (node (ref "X13") (pin "2") (pinfunction "2_2") (pintype "passive"))
      (node (ref "X14") (pin "4") (pinfunction "S_4") (pintype "passive"))
    )
    (net (code "523") (name "Net-(IC45A-Q0)") (class "Default")
      (node (ref "IC45") (pin "3") (pinfunction "Q0_3") (pintype "output"))
      (node (ref "IC48") (pin "1") (pinfunction "I1_1") (pintype "input"))
      (node (ref "IC48") (pin "2") (pinfunction "I2_2") (pintype "input"))
      (node (ref "Q35") (pin "1") (pinfunction "G_1") (pintype "passive"))
    )
    (net (code "524") (name "Net-(IC45A-Q1)") (class "Default")
      (node (ref "IC45") (pin "14") (pinfunction "Q1_14") (pintype "output"))
      (node (ref "IC48") (pin "6") (pinfunction "I6_6") (pintype "input"))
    )
    (net (code "525") (name "Net-(IC45A-Q2)") (class "Default")
      (node (ref "IC45") (pin "2") (pinfunction "Q2_2") (pintype "output"))
      (node (ref "IC48") (pin "7") (pinfunction "I7_7") (pintype "input"))
    )
    (net (code "526") (name "Net-(IC45A-Q3)") (class "Default")
      (node (ref "IC45") (pin "15") (pinfunction "Q3_15") (pintype "output"))
      (node (ref "IC48") (pin "5") (pinfunction "I5_5") (pintype "input"))
    )
    (net (code "527") (name "Net-(IC45A-Q4)") (class "Default")
      (node (ref "IC45") (pin "1") (pinfunction "Q4_1") (pintype "output"))
      (node (ref "IC48") (pin "4") (pinfunction "I4_4") (pintype "input"))
    )
    (net (code "528") (name "Net-(IC45A-Q5)") (class "Default")
      (node (ref "IC45") (pin "6") (pinfunction "Q5_6") (pintype "output"))
      (node (ref "IC48") (pin "3") (pinfunction "I3_3") (pintype "input"))
    )
    (net (code "529") (name "Net-(IC47-ADJ)") (class "Default")
      (node (ref "IC47") (pin "1") (pinfunction "ADJ_1") (pintype "input"))
      (node (ref "R186") (pin "1") (pinfunction "1_1") (pintype "passive"))
      (node (ref "R193") (pin "2") (pinfunction "2_2") (pintype "passive"))
      (node (ref "X13") (pin "7") (pinfunction "7_7") (pintype "passive"))
    )
    (net (code "530") (name "Net-(IC47-VI)") (class "Default")
      (node (ref "IC47") (pin "3") (pinfunction "VI_3") (pintype "input"))
      (node (ref "Q32") (pin "2") (pinfunction "C_2") (pintype "passive"))
    )
    (net (code "531") (name "Net-(IC47-VO)") (class "Default")
      (node (ref "IC47") (pin "2") (pinfunction "VO_2") (pintype "passive"))
      (node (ref "R186") (pin "2") (pinfunction "2_2") (pintype "passive"))
    )
    (net (code "532") (name "Net-(IC48-O2)") (class "Default")
      (node (ref "IC48") (pin "15") (pinfunction "O2_15") (pintype "open_collector"))
      (node (ref "R208") (pin "1") (pinfunction "1_1") (pintype "passive"))
    )
    (net (code "533") (name "Net-(IC49A-+IN)") (class "Default")
      (node (ref "IC49") (pin "5") (pinfunction "+IN_5") (pintype "input"))
      (node (ref "R197") (pin "1") (pinfunction "1_1") (pintype "passive"))
      (node (ref "R198") (pin "2") (pinfunction "2_2") (pintype "passive"))
      (node (ref "R199") (pin "2") (pinfunction "2_2") (pintype "passive"))
    )
    (net (code "534") (name "Net-(IC49A--IN)") (class "Default")
      (node (ref "C42") (pin "1") (pinfunction "1_1") (pintype "passive"))
      (node (ref "IC49") (pin "4") (pinfunction "-IN_4") (pintype "input"))
      (node (ref "R196") (pin "1") (pinfunction "1_1") (pintype "passive"))
    )
    (net (code "535") (name "Net-(IC49B-+IN)") (class "Default")
      (node (ref "IC49") (pin "7") (pinfunction "+IN_7") (pintype "input"))
      (node (ref "R194") (pin "1") (pinfunction "1_1") (pintype "passive"))
      (node (ref "R211") (pin "1") (pinfunction "1_1") (pintype "passive"))
    )
    (net (code "536") (name "Net-(IC49B--IN)") (class "Default")
      (node (ref "IC49") (pin "6") (pinfunction "-IN_6") (pintype "input"))
      (node (ref "IC49") (pin "8") (pinfunction "-IN_8") (pintype "input"))
      (node (ref "R193") (pin "1") (pinfunction "1_1") (pintype "passive"))
    )
    (net (code "537") (name "Net-(IC49B-OUT)") (class "Default")
      (node (ref "IC49") (pin "1") (pinfunction "OUT_1") (pintype "open_collector"))
      (node (ref "R195") (pin "2") (pinfunction "2_2") (pintype "passive"))
      (node (ref "R200") (pin "2") (pinfunction "2_2") (pintype "passive"))
    )
    (net (code "538") (name "Net-(IC49C-+IN)") (class "Default")
      (node (ref "C45") (pin "1") (pinfunction "1_1") (pintype "passive"))
      (node (ref "IC49") (pin "9") (pinfunction "+IN_9") (pintype "input"))
      (node (ref "R202") (pin "2") (pinfunction "2_2") (pintype "passive"))
      (node (ref "R211") (pin "2") (pinfunction "2_2") (pintype "passive"))
    )
    (net (code "539") (name "Net-(IC49C-OUT)") (class "Default")
      (node (ref "C46") (pin "2") (pinfunction "2_2") (pintype "passive"))
      (node (ref "IC49") (pin "14") (pinfunction "OUT_14") (pintype "open_collector"))
      (node (ref "R201") (pin "2") (pinfunction "2_2") (pintype "passive"))
    )
    (net (code "540") (name "Net-(IC51-CV)") (class "Default")
      (node (ref "IC51") (pin "5") (pinfunction "CV_5") (pintype "input"))
      (node (ref "R217") (pin "2") (pinfunction "2_2") (pintype "passive"))
    )
    (net (code "541") (name "Net-(IC51-Q)") (class "Default")
      (node (ref "IC51") (pin "3") (pinfunction "Q_3") (pintype "output"))
      (node (ref "IC52") (pin "12") (pinfunction "A_12") (pintype "input"))
      (node (ref "R217") (pin "1") (pinfunction "1_1") (pintype "passive"))
    )
    (net (code "542") (name "Net-(IC52B-B)") (class "Default")
      (node (ref "IC52") (pin "11") (pinfunction "B_11") (pintype "input"))
      (node (ref "IC52") (pin "9") (pinfunction "~{Q}_9") (pintype "output"))
      (node (ref "R223") (pin "2") (pinfunction "2_2") (pintype "passive"))
    )
    (net (code "543") (name "Net-(IC52B-T2)") (class "Default")
      (node (ref "C49") (pin "1") (pinfunction "1_1") (pintype "passive"))
      (node (ref "IC52") (pin "14") (pinfunction "T2_14") (pintype "input"))
      (node (ref "R221") (pin "1") (pinfunction "1_1") (pintype "passive"))
    )
    (net (code "544") (name "Net-(IC54A-+IN)") (class "Default")
      (node (ref "C44") (pin "1") (pinfunction "1_1") (pintype "passive"))
      (node (ref "IC54") (pin "3") (pinfunction "+IN_3") (pintype "input"))
      (node (ref "R191") (pin "1") (pinfunction "1_1") (pintype "passive"))
    )
    (net (code "545") (name "Net-(IC54A--IN)") (class "Default")
      (node (ref "IC54") (pin "2") (pinfunction "-IN_2") (pintype "input"))
      (node (ref "R192") (pin "2") (pinfunction "2_2") (pintype "passive"))
    )
    (net (code "546") (name "Net-(IC54A-OUT)") (class "Default")
      (node (ref "IC54") (pin "1") (pinfunction "OUT_1") (pintype "output"))
      (node (ref "R224") (pin "2") (pinfunction "2_2") (pintype "passive"))
    )
    (net (code "547") (name "Net-(IC54B-+IN)") (class "Default")
      (node (ref "IC54") (pin "5") (pinfunction "+IN_5") (pintype "input"))
      (node (ref "R225") (pin "2") (pinfunction "2_2") (pintype "passive"))
      (node (ref "R226") (pin "2") (pinfunction "2_2") (pintype "passive"))
    )
    (net (code "548") (name "Net-(IC54B--IN)") (class "Default")
      (node (ref "IC54") (pin "6") (pinfunction "-IN_6") (pintype "input"))
      (node (ref "R227") (pin "1") (pinfunction "1_1") (pintype "passive"))
      (node (ref "R228") (pin "2") (pinfunction "2_2") (pintype "passive"))
    )
    (net (code "549") (name "Net-(IC54B-OUT)") (class "Default")
      (node (ref "IC54") (pin "7") (pinfunction "OUT_7") (pintype "output"))
      (node (ref "R212") (pin "1") (pinfunction "1_1") (pintype "passive"))
      (node (ref "R226") (pin "1") (pinfunction "1_1") (pintype "passive"))
    )
    (net (code "550") (name "Net-(IC56A-A)") (class "Default")
      (node (ref "IC56") (pin "10") (pinfunction "A_10") (pintype "input"))
      (node (ref "R236") (pin "1") (pinfunction "1_1") (pintype "passive"))
      (node (ref "X16") (pin "4") (pinfunction "4_4") (pintype "passive"))
      (node (ref "X17") (pin "2") (pinfunction "S_2") (pintype "passive"))
    )
    (net (code "551") (name "Net-(IC56A-B)") (class "Default")
      (node (ref "IC56") (pin "13") (pinfunction "B_13") (pintype "input"))
      (node (ref "R235") (pin "1") (pinfunction "1_1") (pintype "passive"))
      (node (ref "X16") (pin "3") (pinfunction "3_3") (pintype "passive"))
      (node (ref "X17") (pin "3") (pinfunction "S_3") (pintype "passive"))
    )
    (net (code "552") (name "Net-(IC56A-C)") (class "Default")
      (node (ref "IC56") (pin "12") (pinfunction "C_12") (pintype "input"))
      (node (ref "R234") (pin "1") (pinfunction "1_1") (pintype "passive"))
      (node (ref "X16") (pin "2") (pinfunction "2_2") (pintype "passive"))
      (node (ref "X17") (pin "4") (pinfunction "S_4") (pintype "passive"))
    )
    (net (code "553") (name "Net-(IC56A-Q0)") (class "Default")
      (node (ref "IC56") (pin "3") (pinfunction "Q0_3") (pintype "output"))
      (node (ref "IC59") (pin "1") (pinfunction "I1_1") (pintype "input"))
      (node (ref "IC59") (pin "2") (pinfunction "I2_2") (pintype "input"))
      (node (ref "Q42") (pin "1") (pinfunction "G_1") (pintype "passive"))
    )
    (net (code "554") (name "Net-(IC56A-Q1)") (class "Default")
      (node (ref "IC56") (pin "14") (pinfunction "Q1_14") (pintype "output"))
      (node (ref "IC59") (pin "6") (pinfunction "I6_6") (pintype "input"))
    )
    (net (code "555") (name "Net-(IC56A-Q2)") (class "Default")
      (node (ref "IC56") (pin "2") (pinfunction "Q2_2") (pintype "output"))
      (node (ref "IC59") (pin "7") (pinfunction "I7_7") (pintype "input"))
    )
    (net (code "556") (name "Net-(IC56A-Q3)") (class "Default")
      (node (ref "IC56") (pin "15") (pinfunction "Q3_15") (pintype "output"))
      (node (ref "IC59") (pin "5") (pinfunction "I5_5") (pintype "input"))
    )
    (net (code "557") (name "Net-(IC56A-Q4)") (class "Default")
      (node (ref "IC56") (pin "1") (pinfunction "Q4_1") (pintype "output"))
      (node (ref "IC59") (pin "4") (pinfunction "I4_4") (pintype "input"))
    )
    (net (code "558") (name "Net-(IC56A-Q5)") (class "Default")
      (node (ref "IC56") (pin "6") (pinfunction "Q5_6") (pintype "output"))
      (node (ref "IC59") (pin "3") (pinfunction "I3_3") (pintype "input"))
    )
    (net (code "559") (name "Net-(IC58-ADJ)") (class "Default")
      (node (ref "IC58") (pin "1") (pinfunction "ADJ_1") (pintype "input"))
      (node (ref "R232") (pin "1") (pinfunction "1_1") (pintype "passive"))
      (node (ref "R239") (pin "2") (pinfunction "2_2") (pintype "passive"))
      (node (ref "X16") (pin "7") (pinfunction "7_7") (pintype "passive"))
    )
    (net (code "560") (name "Net-(IC58-VI)") (class "Default")
      (node (ref "IC58") (pin "3") (pinfunction "VI_3") (pintype "input"))
      (node (ref "Q39") (pin "2") (pinfunction "C_2") (pintype "passive"))
    )
    (net (code "561") (name "Net-(IC58-VO)") (class "Default")
      (node (ref "IC58") (pin "2") (pinfunction "VO_2") (pintype "passive"))
      (node (ref "R232") (pin "2") (pinfunction "2_2") (pintype "passive"))
    )
    (net (code "562") (name "Net-(IC59-O2)") (class "Default")
      (node (ref "IC59") (pin "15") (pinfunction "O2_15") (pintype "open_collector"))
      (node (ref "R254") (pin "1") (pinfunction "1_1") (pintype "passive"))
    )
    (net (code "563") (name "Net-(IC60A-+IN)") (class "Default")
      (node (ref "IC60") (pin "5") (pinfunction "+IN_5") (pintype "input"))
      (node (ref "R243") (pin "1") (pinfunction "1_1") (pintype "passive"))
      (node (ref "R244") (pin "2") (pinfunction "2_2") (pintype "passive"))
      (node (ref "R245") (pin "2") (pinfunction "2_2") (pintype "passive"))
    )
    (net (code "564") (name "Net-(IC60A--IN)") (class "Default")
      (node (ref "C52") (pin "1") (pinfunction "1_1") (pintype "passive"))
      (node (ref "IC60") (pin "4") (pinfunction "-IN_4") (pintype "input"))
      (node (ref "R242") (pin "1") (pinfunction "1_1") (pintype "passive"))
    )
    (net (code "565") (name "Net-(IC60B-+IN)") (class "Default")
      (node (ref "IC60") (pin "7") (pinfunction "+IN_7") (pintype "input"))
      (node (ref "R240") (pin "1") (pinfunction "1_1") (pintype "passive"))
      (node (ref "R257") (pin "1") (pinfunction "1_1") (pintype "passive"))
    )
    (net (code "566") (name "Net-(IC60B--IN)") (class "Default")
      (node (ref "IC60") (pin "6") (pinfunction "-IN_6") (pintype "input"))
      (node (ref "IC60") (pin "8") (pinfunction "-IN_8") (pintype "input"))
      (node (ref "R239") (pin "1") (pinfunction "1_1") (pintype "passive"))
    )
    (net (code "567") (name "Net-(IC60B-OUT)") (class "Default")
      (node (ref "IC60") (pin "1") (pinfunction "OUT_1") (pintype "open_collector"))
      (node (ref "R241") (pin "2") (pinfunction "2_2") (pintype "passive"))
      (node (ref "R246") (pin "2") (pinfunction "2_2") (pintype "passive"))
    )
    (net (code "568") (name "Net-(IC60C-+IN)") (class "Default")
      (node (ref "C55") (pin "1") (pinfunction "1_1") (pintype "passive"))
      (node (ref "IC60") (pin "9") (pinfunction "+IN_9") (pintype "input"))
      (node (ref "R248") (pin "2") (pinfunction "2_2") (pintype "passive"))
      (node (ref "R257") (pin "2") (pinfunction "2_2") (pintype "passive"))
    )
    (net (code "569") (name "Net-(IC60C-OUT)") (class "Default")
      (node (ref "C56") (pin "2") (pinfunction "2_2") (pintype "passive"))
      (node (ref "IC60") (pin "14") (pinfunction "OUT_14") (pintype "open_collector"))
      (node (ref "R247") (pin "2") (pinfunction "2_2") (pintype "passive"))
    )
    (net (code "570") (name "Net-(IC62-CV)") (class "Default")
      (node (ref "IC62") (pin "5") (pinfunction "CV_5") (pintype "input"))
      (node (ref "R263") (pin "2") (pinfunction "2_2") (pintype "passive"))
    )
    (net (code "571") (name "Net-(IC62-Q)") (class "Default")
      (node (ref "IC62") (pin "3") (pinfunction "Q_3") (pintype "output"))
      (node (ref "IC63") (pin "12") (pinfunction "A_12") (pintype "input"))
      (node (ref "R263") (pin "1") (pinfunction "1_1") (pintype "passive"))
    )
    (net (code "572") (name "Net-(IC63B-B)") (class "Default")
      (node (ref "IC63") (pin "11") (pinfunction "B_11") (pintype "input"))
      (node (ref "IC63") (pin "9") (pinfunction "~{Q}_9") (pintype "output"))
      (node (ref "R269") (pin "2") (pinfunction "2_2") (pintype "passive"))
    )
    (net (code "573") (name "Net-(IC63B-T2)") (class "Default")
      (node (ref "C59") (pin "1") (pinfunction "1_1") (pintype "passive"))
      (node (ref "IC63") (pin "14") (pinfunction "T2_14") (pintype "input"))
      (node (ref "R267") (pin "1") (pinfunction "1_1") (pintype "passive"))
    )
    (net (code "574") (name "Net-(IC65A-+IN)") (class "Default")
      (node (ref "C54") (pin "1") (pinfunction "1_1") (pintype "passive"))
      (node (ref "IC65") (pin "3") (pinfunction "+IN_3") (pintype "input"))
      (node (ref "R237") (pin "1") (pinfunction "1_1") (pintype "passive"))
    )
    (net (code "575") (name "Net-(IC65A--IN)") (class "Default")
      (node (ref "IC65") (pin "2") (pinfunction "-IN_2") (pintype "input"))
      (node (ref "R238") (pin "2") (pinfunction "2_2") (pintype "passive"))
    )
    (net (code "576") (name "Net-(IC65A-OUT)") (class "Default")
      (node (ref "IC65") (pin "1") (pinfunction "OUT_1") (pintype "output"))
      (node (ref "R270") (pin "2") (pinfunction "2_2") (pintype "passive"))
    )
    (net (code "577") (name "Net-(IC65B-+IN)") (class "Default")
      (node (ref "IC65") (pin "5") (pinfunction "+IN_5") (pintype "input"))
      (node (ref "R271") (pin "2") (pinfunction "2_2") (pintype "passive"))
      (node (ref "R272") (pin "2") (pinfunction "2_2") (pintype "passive"))
    )
    (net (code "578") (name "Net-(IC65B--IN)") (class "Default")
      (node (ref "IC65") (pin "6") (pinfunction "-IN_6") (pintype "input"))
      (node (ref "R273") (pin "1") (pinfunction "1_1") (pintype "passive"))
      (node (ref "R274") (pin "2") (pinfunction "2_2") (pintype "passive"))
    )
    (net (code "579") (name "Net-(IC65B-OUT)") (class "Default")
      (node (ref "IC65") (pin "7") (pinfunction "OUT_7") (pintype "output"))
      (node (ref "R258") (pin "1") (pinfunction "1_1") (pintype "passive"))
      (node (ref "R272") (pin "1") (pinfunction "1_1") (pintype "passive"))
    )
    (net (code "580") (name "Net-(IC67A-A)") (class "Default")
      (node (ref "IC67") (pin "10") (pinfunction "A_10") (pintype "input"))
      (node (ref "R282") (pin "1") (pinfunction "1_1") (pintype "passive"))
      (node (ref "X19") (pin "4") (pinfunction "4_4") (pintype "passive"))
      (node (ref "X20") (pin "2") (pinfunction "S_2") (pintype "passive"))
    )
    (net (code "581") (name "Net-(IC67A-B)") (class "Default")
      (node (ref "IC67") (pin "13") (pinfunction "B_13") (pintype "input"))
      (node (ref "R281") (pin "1") (pinfunction "1_1") (pintype "passive"))
      (node (ref "X19") (pin "3") (pinfunction "3_3") (pintype "passive"))
      (node (ref "X20") (pin "3") (pinfunction "S_3") (pintype "passive"))
    )
    (net (code "582") (name "Net-(IC67A-C)") (class "Default")
      (node (ref "IC67") (pin "12") (pinfunction "C_12") (pintype "input"))
      (node (ref "R280") (pin "1") (pinfunction "1_1") (pintype "passive"))
      (node (ref "X19") (pin "2") (pinfunction "2_2") (pintype "passive"))
      (node (ref "X20") (pin "4") (pinfunction "S_4") (pintype "passive"))
    )
    (net (code "583") (name "Net-(IC67A-Q0)") (class "Default")
      (node (ref "IC67") (pin "3") (pinfunction "Q0_3") (pintype "output"))
      (node (ref "IC70") (pin "1") (pinfunction "I1_1") (pintype "input"))
      (node (ref "IC70") (pin "2") (pinfunction "I2_2") (pintype "input"))
      (node (ref "Q49") (pin "1") (pinfunction "G_1") (pintype "passive"))
    )
    (net (code "584") (name "Net-(IC67A-Q1)") (class "Default")
      (node (ref "IC67") (pin "14") (pinfunction "Q1_14") (pintype "output"))
      (node (ref "IC70") (pin "6") (pinfunction "I6_6") (pintype "input"))
    )
    (net (code "585") (name "Net-(IC67A-Q2)") (class "Default")
      (node (ref "IC67") (pin "2") (pinfunction "Q2_2") (pintype "output"))
      (node (ref "IC70") (pin "7") (pinfunction "I7_7") (pintype "input"))
    )
    (net (code "586") (name "Net-(IC67A-Q3)") (class "Default")
      (node (ref "IC67") (pin "15") (pinfunction "Q3_15") (pintype "output"))
      (node (ref "IC70") (pin "5") (pinfunction "I5_5") (pintype "input"))
    )
    (net (code "587") (name "Net-(IC67A-Q4)") (class "Default")
      (node (ref "IC67") (pin "1") (pinfunction "Q4_1") (pintype "output"))
      (node (ref "IC70") (pin "4") (pinfunction "I4_4") (pintype "input"))
    )
    (net (code "588") (name "Net-(IC67A-Q5)") (class "Default")
      (node (ref "IC67") (pin "6") (pinfunction "Q5_6") (pintype "output"))
      (node (ref "IC70") (pin "3") (pinfunction "I3_3") (pintype "input"))
    )
    (net (code "589") (name "Net-(IC69-ADJ)") (class "Default")
      (node (ref "IC69") (pin "1") (pinfunction "ADJ_1") (pintype "input"))
      (node (ref "R278") (pin "1") (pinfunction "1_1") (pintype "passive"))
      (node (ref "R285") (pin "2") (pinfunction "2_2") (pintype "passive"))
      (node (ref "X19") (pin "7") (pinfunction "7_7") (pintype "passive"))
    )
    (net (code "590") (name "Net-(IC69-VI)") (class "Default")
      (node (ref "IC69") (pin "3") (pinfunction "VI_3") (pintype "input"))
      (node (ref "Q46") (pin "2") (pinfunction "C_2") (pintype "passive"))
    )
    (net (code "591") (name "Net-(IC69-VO)") (class "Default")
      (node (ref "IC69") (pin "2") (pinfunction "VO_2") (pintype "passive"))
      (node (ref "R278") (pin "2") (pinfunction "2_2") (pintype "passive"))
    )
    (net (code "592") (name "Net-(IC70-O2)") (class "Default")
      (node (ref "IC70") (pin "15") (pinfunction "O2_15") (pintype "open_collector"))
      (node (ref "R300") (pin "1") (pinfunction "1_1") (pintype "passive"))
    )
    (net (code "593") (name "Net-(IC71A-+IN)") (class "Default")
      (node (ref "IC71") (pin "5") (pinfunction "+IN_5") (pintype "input"))
      (node (ref "R289") (pin "1") (pinfunction "1_1") (pintype "passive"))
      (node (ref "R290") (pin "2") (pinfunction "2_2") (pintype "passive"))
      (node (ref "R291") (pin "2") (pinfunction "2_2") (pintype "passive"))
    )
    (net (code "594") (name "Net-(IC71A--IN)") (class "Default")
      (node (ref "C62") (pin "1") (pinfunction "1_1") (pintype "passive"))
      (node (ref "IC71") (pin "4") (pinfunction "-IN_4") (pintype "input"))
      (node (ref "R288") (pin "1") (pinfunction "1_1") (pintype "passive"))
    )
    (net (code "595") (name "Net-(IC71B-+IN)") (class "Default")
      (node (ref "IC71") (pin "7") (pinfunction "+IN_7") (pintype "input"))
      (node (ref "R286") (pin "1") (pinfunction "1_1") (pintype "passive"))
      (node (ref "R303") (pin "1") (pinfunction "1_1") (pintype "passive"))
    )
    (net (code "596") (name "Net-(IC71B--IN)") (class "Default")
      (node (ref "IC71") (pin "6") (pinfunction "-IN_6") (pintype "input"))
      (node (ref "IC71") (pin "8") (pinfunction "-IN_8") (pintype "input"))
      (node (ref "R285") (pin "1") (pinfunction "1_1") (pintype "passive"))
    )
    (net (code "597") (name "Net-(IC71B-OUT)") (class "Default")
      (node (ref "IC71") (pin "1") (pinfunction "OUT_1") (pintype "open_collector"))
      (node (ref "R287") (pin "2") (pinfunction "2_2") (pintype "passive"))
      (node (ref "R292") (pin "2") (pinfunction "2_2") (pintype "passive"))
    )
    (net (code "598") (name "Net-(IC71C-+IN)") (class "Default")
      (node (ref "C65") (pin "1") (pinfunction "1_1") (pintype "passive"))
      (node (ref "IC71") (pin "9") (pinfunction "+IN_9") (pintype "input"))
      (node (ref "R294") (pin "2") (pinfunction "2_2") (pintype "passive"))
      (node (ref "R303") (pin "2") (pinfunction "2_2") (pintype "passive"))
    )
    (net (code "599") (name "Net-(IC71C-OUT)") (class "Default")
      (node (ref "C66") (pin "2") (pinfunction "2_2") (pintype "passive"))
      (node (ref "IC71") (pin "14") (pinfunction "OUT_14") (pintype "open_collector"))
      (node (ref "R293") (pin "2") (pinfunction "2_2") (pintype "passive"))
    )
    (net (code "600") (name "Net-(IC73-CV)") (class "Default")
      (node (ref "IC73") (pin "5") (pinfunction "CV_5") (pintype "input"))
      (node (ref "R309") (pin "2") (pinfunction "2_2") (pintype "passive"))
    )
    (net (code "601") (name "Net-(IC73-Q)") (class "Default")
      (node (ref "IC73") (pin "3") (pinfunction "Q_3") (pintype "output"))
      (node (ref "IC74") (pin "12") (pinfunction "A_12") (pintype "input"))
      (node (ref "R309") (pin "1") (pinfunction "1_1") (pintype "passive"))
    )
    (net (code "602") (name "Net-(IC74B-B)") (class "Default")
      (node (ref "IC74") (pin "11") (pinfunction "B_11") (pintype "input"))
      (node (ref "IC74") (pin "9") (pinfunction "~{Q}_9") (pintype "output"))
      (node (ref "R315") (pin "2") (pinfunction "2_2") (pintype "passive"))
    )
    (net (code "603") (name "Net-(IC74B-T2)") (class "Default")
      (node (ref "C69") (pin "1") (pinfunction "1_1") (pintype "passive"))
      (node (ref "IC74") (pin "14") (pinfunction "T2_14") (pintype "input"))
      (node (ref "R313") (pin "1") (pinfunction "1_1") (pintype "passive"))
    )
    (net (code "604") (name "Net-(IC76A-+IN)") (class "Default")
      (node (ref "C64") (pin "1") (pinfunction "1_1") (pintype "passive"))
      (node (ref "IC76") (pin "3") (pinfunction "+IN_3") (pintype "input"))
      (node (ref "R283") (pin "1") (pinfunction "1_1") (pintype "passive"))
    )
    (net (code "605") (name "Net-(IC76A--IN)") (class "Default")
      (node (ref "IC76") (pin "2") (pinfunction "-IN_2") (pintype "input"))
      (node (ref "R284") (pin "2") (pinfunction "2_2") (pintype "passive"))
    )
    (net (code "606") (name "Net-(IC76A-OUT)") (class "Default")
      (node (ref "IC76") (pin "1") (pinfunction "OUT_1") (pintype "output"))
      (node (ref "R316") (pin "2") (pinfunction "2_2") (pintype "passive"))
    )
    (net (code "607") (name "Net-(IC76B-+IN)") (class "Default")
      (node (ref "IC76") (pin "5") (pinfunction "+IN_5") (pintype "input"))
      (node (ref "R317") (pin "2") (pinfunction "2_2") (pintype "passive"))
      (node (ref "R318") (pin "2") (pinfunction "2_2") (pintype "passive"))
    )
    (net (code "608") (name "Net-(IC76B--IN)") (class "Default")
      (node (ref "IC76") (pin "6") (pinfunction "-IN_6") (pintype "input"))
      (node (ref "R319") (pin "1") (pinfunction "1_1") (pintype "passive"))
      (node (ref "R320") (pin "2") (pinfunction "2_2") (pintype "passive"))
    )
    (net (code "609") (name "Net-(IC76B-OUT)") (class "Default")
      (node (ref "IC76") (pin "7") (pinfunction "OUT_7") (pintype "output"))
      (node (ref "R304") (pin "1") (pinfunction "1_1") (pintype "passive"))
      (node (ref "R318") (pin "1") (pinfunction "1_1") (pintype "passive"))
    )
    (net (code "610") (name "Net-(IC78A-A)") (class "Default")
      (node (ref "IC78") (pin "10") (pinfunction "A_10") (pintype "input"))
      (node (ref "R328") (pin "1") (pinfunction "1_1") (pintype "passive"))
      (node (ref "X22") (pin "4") (pinfunction "4_4") (pintype "passive"))
      (node (ref "X23") (pin "2") (pinfunction "S_2") (pintype "passive"))
    )
    (net (code "611") (name "Net-(IC78A-B)") (class "Default")
      (node (ref "IC78") (pin "13") (pinfunction "B_13") (pintype "input"))
      (node (ref "R327") (pin "1") (pinfunction "1_1") (pintype "passive"))
      (node (ref "X22") (pin "3") (pinfunction "3_3") (pintype "passive"))
      (node (ref "X23") (pin "3") (pinfunction "S_3") (pintype "passive"))
    )
    (net (code "612") (name "Net-(IC78A-C)") (class "Default")
      (node (ref "IC78") (pin "12") (pinfunction "C_12") (pintype "input"))
      (node (ref "R326") (pin "1") (pinfunction "1_1") (pintype "passive"))
      (node (ref "X22") (pin "2") (pinfunction "2_2") (pintype "passive"))
      (node (ref "X23") (pin "4") (pinfunction "S_4") (pintype "passive"))
    )
    (net (code "613") (name "Net-(IC78A-Q0)") (class "Default")
      (node (ref "IC78") (pin "3") (pinfunction "Q0_3") (pintype "output"))
      (node (ref "IC81") (pin "1") (pinfunction "I1_1") (pintype "input"))
      (node (ref "IC81") (pin "2") (pinfunction "I2_2") (pintype "input"))
      (node (ref "Q56") (pin "1") (pinfunction "G_1") (pintype "passive"))
    )
    (net (code "614") (name "Net-(IC78A-Q1)") (class "Default")
      (node (ref "IC78") (pin "14") (pinfunction "Q1_14") (pintype "output"))
      (node (ref "IC81") (pin "6") (pinfunction "I6_6") (pintype "input"))
    )
    (net (code "615") (name "Net-(IC78A-Q2)") (class "Default")
      (node (ref "IC78") (pin "2") (pinfunction "Q2_2") (pintype "output"))
      (node (ref "IC81") (pin "7") (pinfunction "I7_7") (pintype "input"))
    )
    (net (code "616") (name "Net-(IC78A-Q3)") (class "Default")
      (node (ref "IC78") (pin "15") (pinfunction "Q3_15") (pintype "output"))
      (node (ref "IC81") (pin "5") (pinfunction "I5_5") (pintype "input"))
    )
    (net (code "617") (name "Net-(IC78A-Q4)") (class "Default")
      (node (ref "IC78") (pin "1") (pinfunction "Q4_1") (pintype "output"))
      (node (ref "IC81") (pin "4") (pinfunction "I4_4") (pintype "input"))
    )
    (net (code "618") (name "Net-(IC78A-Q5)") (class "Default")
      (node (ref "IC78") (pin "6") (pinfunction "Q5_6") (pintype "output"))
      (node (ref "IC81") (pin "3") (pinfunction "I3_3") (pintype "input"))
    )
    (net (code "619") (name "Net-(IC80-ADJ)") (class "Default")
      (node (ref "IC80") (pin "1") (pinfunction "ADJ_1") (pintype "input"))
      (node (ref "R324") (pin "1") (pinfunction "1_1") (pintype "passive"))
      (node (ref "R331") (pin "2") (pinfunction "2_2") (pintype "passive"))
      (node (ref "X22") (pin "7") (pinfunction "7_7") (pintype "passive"))
    )
    (net (code "620") (name "Net-(IC80-VI)") (class "Default")
      (node (ref "IC80") (pin "3") (pinfunction "VI_3") (pintype "input"))
      (node (ref "Q53") (pin "2") (pinfunction "C_2") (pintype "passive"))
    )
    (net (code "621") (name "Net-(IC80-VO)") (class "Default")
      (node (ref "IC80") (pin "2") (pinfunction "VO_2") (pintype "passive"))
      (node (ref "R324") (pin "2") (pinfunction "2_2") (pintype "passive"))
    )
    (net (code "622") (name "Net-(IC81-O2)") (class "Default")
      (node (ref "IC81") (pin "15") (pinfunction "O2_15") (pintype "open_collector"))
      (node (ref "R346") (pin "1") (pinfunction "1_1") (pintype "passive"))
    )
    (net (code "623") (name "Net-(IC82A-+IN)") (class "Default")
      (node (ref "IC82") (pin "5") (pinfunction "+IN_5") (pintype "input"))
      (node (ref "R335") (pin "1") (pinfunction "1_1") (pintype "passive"))
      (node (ref "R336") (pin "2") (pinfunction "2_2") (pintype "passive"))
      (node (ref "R337") (pin "2") (pinfunction "2_2") (pintype "passive"))
    )
    (net (code "624") (name "Net-(IC82A--IN)") (class "Default")
      (node (ref "C72") (pin "1") (pinfunction "1_1") (pintype "passive"))
      (node (ref "IC82") (pin "4") (pinfunction "-IN_4") (pintype "input"))
      (node (ref "R334") (pin "1") (pinfunction "1_1") (pintype "passive"))
    )
    (net (code "625") (name "Net-(IC82B-+IN)") (class "Default")
      (node (ref "IC82") (pin "7") (pinfunction "+IN_7") (pintype "input"))
      (node (ref "R332") (pin "1") (pinfunction "1_1") (pintype "passive"))
      (node (ref "R349") (pin "1") (pinfunction "1_1") (pintype "passive"))
    )
    (net (code "626") (name "Net-(IC82B--IN)") (class "Default")
      (node (ref "IC82") (pin "6") (pinfunction "-IN_6") (pintype "input"))
      (node (ref "IC82") (pin "8") (pinfunction "-IN_8") (pintype "input"))
      (node (ref "R331") (pin "1") (pinfunction "1_1") (pintype "passive"))
    )
    (net (code "627") (name "Net-(IC82B-OUT)") (class "Default")
      (node (ref "IC82") (pin "1") (pinfunction "OUT_1") (pintype "open_collector"))
      (node (ref "R333") (pin "2") (pinfunction "2_2") (pintype "passive"))
      (node (ref "R338") (pin "2") (pinfunction "2_2") (pintype "passive"))
    )
    (net (code "628") (name "Net-(IC82C-+IN)") (class "Default")
      (node (ref "C75") (pin "1") (pinfunction "1_1") (pintype "passive"))
      (node (ref "IC82") (pin "9") (pinfunction "+IN_9") (pintype "input"))
      (node (ref "R340") (pin "2") (pinfunction "2_2") (pintype "passive"))
      (node (ref "R349") (pin "2") (pinfunction "2_2") (pintype "passive"))
    )
    (net (code "629") (name "Net-(IC82C-OUT)") (class "Default")
      (node (ref "C76") (pin "2") (pinfunction "2_2") (pintype "passive"))
      (node (ref "IC82") (pin "14") (pinfunction "OUT_14") (pintype "open_collector"))
      (node (ref "R339") (pin "2") (pinfunction "2_2") (pintype "passive"))
    )
    (net (code "630") (name "Net-(IC84-CV)") (class "Default")
      (node (ref "IC84") (pin "5") (pinfunction "CV_5") (pintype "input"))
      (node (ref "R355") (pin "2") (pinfunction "2_2") (pintype "passive"))
    )
    (net (code "631") (name "Net-(IC84-Q)") (class "Default")
      (node (ref "IC84") (pin "3") (pinfunction "Q_3") (pintype "output"))
      (node (ref "IC85") (pin "12") (pinfunction "A_12") (pintype "input"))
      (node (ref "R355") (pin "1") (pinfunction "1_1") (pintype "passive"))
    )
    (net (code "632") (name "Net-(IC85B-B)") (class "Default")
      (node (ref "IC85") (pin "11") (pinfunction "B_11") (pintype "input"))
      (node (ref "IC85") (pin "9") (pinfunction "~{Q}_9") (pintype "output"))
      (node (ref "R361") (pin "2") (pinfunction "2_2") (pintype "passive"))
    )
    (net (code "633") (name "Net-(IC85B-T2)") (class "Default")
      (node (ref "C79") (pin "1") (pinfunction "1_1") (pintype "passive"))
      (node (ref "IC85") (pin "14") (pinfunction "T2_14") (pintype "input"))
      (node (ref "R359") (pin "1") (pinfunction "1_1") (pintype "passive"))
    )
    (net (code "634") (name "Net-(IC87A-+IN)") (class "Default")
      (node (ref "C74") (pin "1") (pinfunction "1_1") (pintype "passive"))
      (node (ref "IC87") (pin "3") (pinfunction "+IN_3") (pintype "input"))
      (node (ref "R329") (pin "1") (pinfunction "1_1") (pintype "passive"))
    )
    (net (code "635") (name "Net-(IC87A--IN)") (class "Default")
      (node (ref "IC87") (pin "2") (pinfunction "-IN_2") (pintype "input"))
      (node (ref "R330") (pin "2") (pinfunction "2_2") (pintype "passive"))
    )
    (net (code "636") (name "Net-(IC87A-OUT)") (class "Default")
      (node (ref "IC87") (pin "1") (pinfunction "OUT_1") (pintype "output"))
      (node (ref "R362") (pin "2") (pinfunction "2_2") (pintype "passive"))
    )
    (net (code "637") (name "Net-(IC87B-+IN)") (class "Default")
      (node (ref "IC87") (pin "5") (pinfunction "+IN_5") (pintype "input"))
      (node (ref "R363") (pin "2") (pinfunction "2_2") (pintype "passive"))
      (node (ref "R364") (pin "2") (pinfunction "2_2") (pintype "passive"))
    )
    (net (code "638") (name "Net-(IC87B--IN)") (class "Default")
      (node (ref "IC87") (pin "6") (pinfunction "-IN_6") (pintype "input"))
      (node (ref "R365") (pin "1") (pinfunction "1_1") (pintype "passive"))
      (node (ref "R366") (pin "2") (pinfunction "2_2") (pintype "passive"))
    )
    (net (code "639") (name "Net-(IC87B-OUT)") (class "Default")
      (node (ref "IC87") (pin "7") (pinfunction "OUT_7") (pintype "output"))
      (node (ref "R350") (pin "1") (pinfunction "1_1") (pintype "passive"))
      (node (ref "R364") (pin "1") (pinfunction "1_1") (pintype "passive"))
    )
    (net (code "640") (name "Net-(IC89A-A)") (class "Default")
      (node (ref "IC89") (pin "10") (pinfunction "A_10") (pintype "input"))
      (node (ref "R374") (pin "1") (pinfunction "1_1") (pintype "passive"))
      (node (ref "X25") (pin "4") (pinfunction "4_4") (pintype "passive"))
      (node (ref "X26") (pin "2") (pinfunction "S_2") (pintype "passive"))
    )
    (net (code "641") (name "Net-(IC89A-B)") (class "Default")
      (node (ref "IC89") (pin "13") (pinfunction "B_13") (pintype "input"))
      (node (ref "R373") (pin "1") (pinfunction "1_1") (pintype "passive"))
      (node (ref "X25") (pin "3") (pinfunction "3_3") (pintype "passive"))
      (node (ref "X26") (pin "3") (pinfunction "S_3") (pintype "passive"))
    )
    (net (code "642") (name "Net-(IC89A-C)") (class "Default")
      (node (ref "IC89") (pin "12") (pinfunction "C_12") (pintype "input"))
      (node (ref "R372") (pin "1") (pinfunction "1_1") (pintype "passive"))
      (node (ref "X25") (pin "2") (pinfunction "2_2") (pintype "passive"))
      (node (ref "X26") (pin "4") (pinfunction "S_4") (pintype "passive"))
    )
    (net (code "643") (name "Net-(IC89A-Q0)") (class "Default")
      (node (ref "IC89") (pin "3") (pinfunction "Q0_3") (pintype "output"))
      (node (ref "IC92") (pin "1") (pinfunction "I1_1") (pintype "input"))
      (node (ref "IC92") (pin "2") (pinfunction "I2_2") (pintype "input"))
      (node (ref "Q63") (pin "1") (pinfunction "G_1") (pintype "passive"))
    )
    (net (code "644") (name "Net-(IC89A-Q1)") (class "Default")
      (node (ref "IC89") (pin "14") (pinfunction "Q1_14") (pintype "output"))
      (node (ref "IC92") (pin "6") (pinfunction "I6_6") (pintype "input"))
    )
    (net (code "645") (name "Net-(IC89A-Q2)") (class "Default")
      (node (ref "IC89") (pin "2") (pinfunction "Q2_2") (pintype "output"))
      (node (ref "IC92") (pin "7") (pinfunction "I7_7") (pintype "input"))
    )
    (net (code "646") (name "Net-(IC89A-Q3)") (class "Default")
      (node (ref "IC89") (pin "15") (pinfunction "Q3_15") (pintype "output"))
      (node (ref "IC92") (pin "5") (pinfunction "I5_5") (pintype "input"))
    )
    (net (code "647") (name "Net-(IC89A-Q4)") (class "Default")
      (node (ref "IC89") (pin "1") (pinfunction "Q4_1") (pintype "output"))
      (node (ref "IC92") (pin "4") (pinfunction "I4_4") (pintype "input"))
    )
    (net (code "648") (name "Net-(IC89A-Q5)") (class "Default")
      (node (ref "IC89") (pin "6") (pinfunction "Q5_6") (pintype "output"))
      (node (ref "IC92") (pin "3") (pinfunction "I3_3") (pintype "input"))
    )
    (net (code "649") (name "Net-(IC91-ADJ)") (class "Default")
      (node (ref "IC91") (pin "1") (pinfunction "ADJ_1") (pintype "input"))
      (node (ref "R370") (pin "1") (pinfunction "1_1") (pintype "passive"))
      (node (ref "R377") (pin "2") (pinfunction "2_2") (pintype "passive"))
      (node (ref "X25") (pin "7") (pinfunction "7_7") (pintype "passive"))
    )
    (net (code "650") (name "Net-(IC91-VI)") (class "Default")
      (node (ref "IC91") (pin "3") (pinfunction "VI_3") (pintype "input"))
      (node (ref "Q60") (pin "2") (pinfunction "C_2") (pintype "passive"))
    )
    (net (code "651") (name "Net-(IC91-VO)") (class "Default")
      (node (ref "IC91") (pin "2") (pinfunction "VO_2") (pintype "passive"))
      (node (ref "R370") (pin "2") (pinfunction "2_2") (pintype "passive"))
    )
    (net (code "652") (name "Net-(IC92-O2)") (class "Default")
      (node (ref "IC92") (pin "15") (pinfunction "O2_15") (pintype "open_collector"))
      (node (ref "R392") (pin "1") (pinfunction "1_1") (pintype "passive"))
    )
    (net (code "653") (name "Net-(IC93A-+IN)") (class "Default")
      (node (ref "IC93") (pin "5") (pinfunction "+IN_5") (pintype "input"))
      (node (ref "R381") (pin "1") (pinfunction "1_1") (pintype "passive"))
      (node (ref "R382") (pin "2") (pinfunction "2_2") (pintype "passive"))
      (node (ref "R383") (pin "2") (pinfunction "2_2") (pintype "passive"))
    )
    (net (code "654") (name "Net-(IC93A--IN)") (class "Default")
      (node (ref "C82") (pin "1") (pinfunction "1_1") (pintype "passive"))
      (node (ref "IC93") (pin "4") (pinfunction "-IN_4") (pintype "input"))
      (node (ref "R380") (pin "1") (pinfunction "1_1") (pintype "passive"))
    )
    (net (code "655") (name "Net-(IC93B-+IN)") (class "Default")
      (node (ref "IC93") (pin "7") (pinfunction "+IN_7") (pintype "input"))
      (node (ref "R378") (pin "1") (pinfunction "1_1") (pintype "passive"))
      (node (ref "R395") (pin "1") (pinfunction "1_1") (pintype "passive"))
    )
    (net (code "656") (name "Net-(IC93B--IN)") (class "Default")
      (node (ref "IC93") (pin "6") (pinfunction "-IN_6") (pintype "input"))
      (node (ref "IC93") (pin "8") (pinfunction "-IN_8") (pintype "input"))
      (node (ref "R377") (pin "1") (pinfunction "1_1") (pintype "passive"))
    )
    (net (code "657") (name "Net-(IC93B-OUT)") (class "Default")
      (node (ref "IC93") (pin "1") (pinfunction "OUT_1") (pintype "open_collector"))
      (node (ref "R379") (pin "2") (pinfunction "2_2") (pintype "passive"))
      (node (ref "R384") (pin "2") (pinfunction "2_2") (pintype "passive"))
    )
    (net (code "658") (name "Net-(IC93C-+IN)") (class "Default")
      (node (ref "C85") (pin "1") (pinfunction "1_1") (pintype "passive"))
      (node (ref "IC93") (pin "9") (pinfunction "+IN_9") (pintype "input"))
      (node (ref "R386") (pin "2") (pinfunction "2_2") (pintype "passive"))
      (node (ref "R395") (pin "2") (pinfunction "2_2") (pintype "passive"))
    )
    (net (code "659") (name "Net-(IC93C-OUT)") (class "Default")
      (node (ref "C86") (pin "2") (pinfunction "2_2") (pintype "passive"))
      (node (ref "IC93") (pin "14") (pinfunction "OUT_14") (pintype "open_collector"))
      (node (ref "R385") (pin "2") (pinfunction "2_2") (pintype "passive"))
    )
    (net (code "660") (name "Net-(IC95-CV)") (class "Default")
      (node (ref "IC95") (pin "5") (pinfunction "CV_5") (pintype "input"))
      (node (ref "R401") (pin "2") (pinfunction "2_2") (pintype "passive"))
    )
    (net (code "661") (name "Net-(IC95-Q)") (class "Default")
      (node (ref "IC95") (pin "3") (pinfunction "Q_3") (pintype "output"))
      (node (ref "IC96") (pin "12") (pinfunction "A_12") (pintype "input"))
      (node (ref "R401") (pin "1") (pinfunction "1_1") (pintype "passive"))
    )
    (net (code "662") (name "Net-(IC96B-B)") (class "Default")
      (node (ref "IC96") (pin "11") (pinfunction "B_11") (pintype "input"))
      (node (ref "IC96") (pin "9") (pinfunction "~{Q}_9") (pintype "output"))
      (node (ref "R407") (pin "2") (pinfunction "2_2") (pintype "passive"))
    )
    (net (code "663") (name "Net-(IC96B-T2)") (class "Default")
      (node (ref "C89") (pin "1") (pinfunction "1_1") (pintype "passive"))
      (node (ref "IC96") (pin "14") (pinfunction "T2_14") (pintype "input"))
      (node (ref "R405") (pin "1") (pinfunction "1_1") (pintype "passive"))
    )
    (net (code "664") (name "Net-(IC98A-+IN)") (class "Default")
      (node (ref "C84") (pin "1") (pinfunction "1_1") (pintype "passive"))
      (node (ref "IC98") (pin "3") (pinfunction "+IN_3") (pintype "input"))
      (node (ref "R375") (pin "1") (pinfunction "1_1") (pintype "passive"))
    )
    (net (code "665") (name "Net-(IC98A--IN)") (class "Default")
      (node (ref "IC98") (pin "2") (pinfunction "-IN_2") (pintype "input"))
      (node (ref "R376") (pin "2") (pinfunction "2_2") (pintype "passive"))
    )
    (net (code "666") (name "Net-(IC98A-OUT)") (class "Default")
      (node (ref "IC98") (pin "1") (pinfunction "OUT_1") (pintype "output"))
      (node (ref "R408") (pin "2") (pinfunction "2_2") (pintype "passive"))
    )
    (net (code "667") (name "Net-(IC98B-+IN)") (class "Default")
      (node (ref "IC98") (pin "5") (pinfunction "+IN_5") (pintype "input"))
      (node (ref "R409") (pin "2") (pinfunction "2_2") (pintype "passive"))
      (node (ref "R410") (pin "2") (pinfunction "2_2") (pintype "passive"))
    )
    (net (code "668") (name "Net-(IC98B--IN)") (class "Default")
      (node (ref "IC98") (pin "6") (pinfunction "-IN_6") (pintype "input"))
      (node (ref "R411") (pin "1") (pinfunction "1_1") (pintype "passive"))
      (node (ref "R412") (pin "2") (pinfunction "2_2") (pintype "passive"))
    )
    (net (code "669") (name "Net-(IC98B-OUT)") (class "Default")
      (node (ref "IC98") (pin "7") (pinfunction "OUT_7") (pintype "output"))
      (node (ref "R396") (pin "1") (pinfunction "1_1") (pintype "passive"))
      (node (ref "R410") (pin "1") (pinfunction "1_1") (pintype "passive"))
    )
    (net (code "670") (name "Net-(IC100A-A)") (class "Default")
      (node (ref "IC100") (pin "10") (pinfunction "A_10") (pintype "input"))
      (node (ref "R420") (pin "1") (pinfunction "1_1") (pintype "passive"))
      (node (ref "X28") (pin "4") (pinfunction "4_4") (pintype "passive"))
      (node (ref "X29") (pin "2") (pinfunction "S_2") (pintype "passive"))
    )
    (net (code "671") (name "Net-(IC100A-B)") (class "Default")
      (node (ref "IC100") (pin "13") (pinfunction "B_13") (pintype "input"))
      (node (ref "R419") (pin "1") (pinfunction "1_1") (pintype "passive"))
      (node (ref "X28") (pin "3") (pinfunction "3_3") (pintype "passive"))
      (node (ref "X29") (pin "3") (pinfunction "S_3") (pintype "passive"))
    )
    (net (code "672") (name "Net-(IC100A-C)") (class "Default")
      (node (ref "IC100") (pin "12") (pinfunction "C_12") (pintype "input"))
      (node (ref "R418") (pin "1") (pinfunction "1_1") (pintype "passive"))
      (node (ref "X28") (pin "2") (pinfunction "2_2") (pintype "passive"))
      (node (ref "X29") (pin "4") (pinfunction "S_4") (pintype "passive"))
    )
    (net (code "673") (name "Net-(IC100A-Q0)") (class "Default")
      (node (ref "IC100") (pin "3") (pinfunction "Q0_3") (pintype "output"))
      (node (ref "IC103") (pin "1") (pinfunction "I1_1") (pintype "input"))
      (node (ref "IC103") (pin "2") (pinfunction "I2_2") (pintype "input"))
      (node (ref "Q70") (pin "1") (pinfunction "G_1") (pintype "passive"))
    )
    (net (code "674") (name "Net-(IC100A-Q1)") (class "Default")
      (node (ref "IC100") (pin "14") (pinfunction "Q1_14") (pintype "output"))
      (node (ref "IC103") (pin "6") (pinfunction "I6_6") (pintype "input"))
    )
    (net (code "675") (name "Net-(IC100A-Q2)") (class "Default")
      (node (ref "IC100") (pin "2") (pinfunction "Q2_2") (pintype "output"))
      (node (ref "IC103") (pin "7") (pinfunction "I7_7") (pintype "input"))
    )
    (net (code "676") (name "Net-(IC100A-Q3)") (class "Default")
      (node (ref "IC100") (pin "15") (pinfunction "Q3_15") (pintype "output"))
      (node (ref "IC103") (pin "5") (pinfunction "I5_5") (pintype "input"))
    )
    (net (code "677") (name "Net-(IC100A-Q4)") (class "Default")
      (node (ref "IC100") (pin "1") (pinfunction "Q4_1") (pintype "output"))
      (node (ref "IC103") (pin "4") (pinfunction "I4_4") (pintype "input"))
    )
    (net (code "678") (name "Net-(IC100A-Q5)") (class "Default")
      (node (ref "IC100") (pin "6") (pinfunction "Q5_6") (pintype "output"))
      (node (ref "IC103") (pin "3") (pinfunction "I3_3") (pintype "input"))
    )
    (net (code "679") (name "Net-(IC102-ADJ)") (class "Default")
      (node (ref "IC102") (pin "1") (pinfunction "ADJ_1") (pintype "input"))
      (node (ref "R416") (pin "1") (pinfunction "1_1") (pintype "passive"))
      (node (ref "R423") (pin "2") (pinfunction "2_2") (pintype "passive"))
      (node (ref "X28") (pin "7") (pinfunction "7_7") (pintype "passive"))
    )
    (net (code "680") (name "Net-(IC102-VI)") (class "Default")
      (node (ref "IC102") (pin "3") (pinfunction "VI_3") (pintype "input"))
      (node (ref "Q67") (pin "2") (pinfunction "C_2") (pintype "passive"))
    )
    (net (code "681") (name "Net-(IC102-VO)") (class "Default")
      (node (ref "IC102") (pin "2") (pinfunction "VO_2") (pintype "passive"))
      (node (ref "R416") (pin "2") (pinfunction "2_2") (pintype "passive"))
    )
    (net (code "682") (name "Net-(IC103-O2)") (class "Default")
      (node (ref "IC103") (pin "15") (pinfunction "O2_15") (pintype "open_collector"))
      (node (ref "R438") (pin "1") (pinfunction "1_1") (pintype "passive"))
    )
    (net (code "683") (name "Net-(IC104A-+IN)") (class "Default")
      (node (ref "IC104") (pin "5") (pinfunction "+IN_5") (pintype "input"))
      (node (ref "R427") (pin "1") (pinfunction "1_1") (pintype "passive"))
      (node (ref "R428") (pin "2") (pinfunction "2_2") (pintype "passive"))
      (node (ref "R429") (pin "2") (pinfunction "2_2") (pintype "passive"))
    )
    (net (code "684") (name "Net-(IC104A--IN)") (class "Default")
      (node (ref "C92") (pin "1") (pinfunction "1_1") (pintype "passive"))
      (node (ref "IC104") (pin "4") (pinfunction "-IN_4") (pintype "input"))
      (node (ref "R426") (pin "1") (pinfunction "1_1") (pintype "passive"))
    )
    (net (code "685") (name "Net-(IC104B-+IN)") (class "Default")
      (node (ref "IC104") (pin "7") (pinfunction "+IN_7") (pintype "input"))
      (node (ref "R424") (pin "1") (pinfunction "1_1") (pintype "passive"))
      (node (ref "R441") (pin "1") (pinfunction "1_1") (pintype "passive"))
    )
    (net (code "686") (name "Net-(IC104B--IN)") (class "Default")
      (node (ref "IC104") (pin "6") (pinfunction "-IN_6") (pintype "input"))
      (node (ref "IC104") (pin "8") (pinfunction "-IN_8") (pintype "input"))
      (node (ref "R423") (pin "1") (pinfunction "1_1") (pintype "passive"))
    )
    (net (code "687") (name "Net-(IC104B-OUT)") (class "Default")
      (node (ref "IC104") (pin "1") (pinfunction "OUT_1") (pintype "open_collector"))
      (node (ref "R425") (pin "2") (pinfunction "2_2") (pintype "passive"))
      (node (ref "R430") (pin "2") (pinfunction "2_2") (pintype "passive"))
    )
    (net (code "688") (name "Net-(IC104C-+IN)") (class "Default")
      (node (ref "C95") (pin "1") (pinfunction "1_1") (pintype "passive"))
      (node (ref "IC104") (pin "9") (pinfunction "+IN_9") (pintype "input"))
      (node (ref "R432") (pin "2") (pinfunction "2_2") (pintype "passive"))
      (node (ref "R441") (pin "2") (pinfunction "2_2") (pintype "passive"))
    )
    (net (code "689") (name "Net-(IC104C-OUT)") (class "Default")
      (node (ref "C96") (pin "2") (pinfunction "2_2") (pintype "passive"))
      (node (ref "IC104") (pin "14") (pinfunction "OUT_14") (pintype "open_collector"))
      (node (ref "R431") (pin "2") (pinfunction "2_2") (pintype "passive"))
    )
    (net (code "690") (name "Net-(IC106-CV)") (class "Default")
      (node (ref "IC106") (pin "5") (pinfunction "CV_5") (pintype "input"))
      (node (ref "R447") (pin "2") (pinfunction "2_2") (pintype "passive"))
    )
    (net (code "691") (name "Net-(IC106-Q)") (class "Default")
      (node (ref "IC106") (pin "3") (pinfunction "Q_3") (pintype "output"))
      (node (ref "IC107") (pin "12") (pinfunction "A_12") (pintype "input"))
      (node (ref "R447") (pin "1") (pinfunction "1_1") (pintype "passive"))
    )
    (net (code "692") (name "Net-(IC107B-B)") (class "Default")
      (node (ref "IC107") (pin "11") (pinfunction "B_11") (pintype "input"))
      (node (ref "IC107") (pin "9") (pinfunction "~{Q}_9") (pintype "output"))
      (node (ref "R453") (pin "2") (pinfunction "2_2") (pintype "passive"))
    )
    (net (code "693") (name "Net-(IC107B-T2)") (class "Default")
      (node (ref "C99") (pin "1") (pinfunction "1_1") (pintype "passive"))
      (node (ref "IC107") (pin "14") (pinfunction "T2_14") (pintype "input"))
      (node (ref "R451") (pin "1") (pinfunction "1_1") (pintype "passive"))
    )
    (net (code "694") (name "Net-(IC109A-+IN)") (class "Default")
      (node (ref "C94") (pin "1") (pinfunction "1_1") (pintype "passive"))
      (node (ref "IC109") (pin "3") (pinfunction "+IN_3") (pintype "input"))
      (node (ref "R421") (pin "1") (pinfunction "1_1") (pintype "passive"))
    )
    (net (code "695") (name "Net-(IC109A--IN)") (class "Default")
      (node (ref "IC109") (pin "2") (pinfunction "-IN_2") (pintype "input"))
      (node (ref "R422") (pin "2") (pinfunction "2_2") (pintype "passive"))
    )
    (net (code "696") (name "Net-(IC109A-OUT)") (class "Default")
      (node (ref "IC109") (pin "1") (pinfunction "OUT_1") (pintype "output"))
      (node (ref "R454") (pin "2") (pinfunction "2_2") (pintype "passive"))
    )
    (net (code "697") (name "Net-(IC109B-+IN)") (class "Default")
      (node (ref "IC109") (pin "5") (pinfunction "+IN_5") (pintype "input"))
      (node (ref "R455") (pin "2") (pinfunction "2_2") (pintype "passive"))
      (node (ref "R456") (pin "2") (pinfunction "2_2") (pintype "passive"))
    )
    (net (code "698") (name "Net-(IC109B--IN)") (class "Default")
      (node (ref "IC109") (pin "6") (pinfunction "-IN_6") (pintype "input"))
      (node (ref "R457") (pin "1") (pinfunction "1_1") (pintype "passive"))
      (node (ref "R458") (pin "2") (pinfunction "2_2") (pintype "passive"))
    )
    (net (code "699") (name "Net-(IC109B-OUT)") (class "Default")
      (node (ref "IC109") (pin "7") (pinfunction "OUT_7") (pintype "output"))
      (node (ref "R442") (pin "1") (pinfunction "1_1") (pintype "passive"))
      (node (ref "R456") (pin "1") (pinfunction "1_1") (pintype "passive"))
    )
    (net (code "700") (name "Net-(IC111A-A)") (class "Default")
      (node (ref "IC111") (pin "10") (pinfunction "A_10") (pintype "input"))
      (node (ref "R466") (pin "1") (pinfunction "1_1") (pintype "passive"))
      (node (ref "X31") (pin "4") (pinfunction "4_4") (pintype "passive"))
      (node (ref "X32") (pin "2") (pinfunction "S_2") (pintype "passive"))
    )
    (net (code "701") (name "Net-(IC111A-B)") (class "Default")
      (node (ref "IC111") (pin "13") (pinfunction "B_13") (pintype "input"))
      (node (ref "R465") (pin "1") (pinfunction "1_1") (pintype "passive"))
      (node (ref "X31") (pin "3") (pinfunction "3_3") (pintype "passive"))
      (node (ref "X32") (pin "3") (pinfunction "S_3") (pintype "passive"))
    )
    (net (code "702") (name "Net-(IC111A-C)") (class "Default")
      (node (ref "IC111") (pin "12") (pinfunction "C_12") (pintype "input"))
      (node (ref "R464") (pin "1") (pinfunction "1_1") (pintype "passive"))
      (node (ref "X31") (pin "2") (pinfunction "2_2") (pintype "passive"))
      (node (ref "X32") (pin "4") (pinfunction "S_4") (pintype "passive"))
    )
    (net (code "703") (name "Net-(IC111A-Q0)") (class "Default")
      (node (ref "IC111") (pin "3") (pinfunction "Q0_3") (pintype "output"))
      (node (ref "IC114") (pin "1") (pinfunction "I1_1") (pintype "input"))
      (node (ref "IC114") (pin "2") (pinfunction "I2_2") (pintype "input"))
      (node (ref "Q77") (pin "1") (pinfunction "G_1") (pintype "passive"))
    )
    (net (code "704") (name "Net-(IC111A-Q1)") (class "Default")
      (node (ref "IC111") (pin "14") (pinfunction "Q1_14") (pintype "output"))
      (node (ref "IC114") (pin "6") (pinfunction "I6_6") (pintype "input"))
    )
    (net (code "705") (name "Net-(IC111A-Q2)") (class "Default")
      (node (ref "IC111") (pin "2") (pinfunction "Q2_2") (pintype "output"))
      (node (ref "IC114") (pin "7") (pinfunction "I7_7") (pintype "input"))
    )
    (net (code "706") (name "Net-(IC111A-Q3)") (class "Default")
      (node (ref "IC111") (pin "15") (pinfunction "Q3_15") (pintype "output"))
      (node (ref "IC114") (pin "5") (pinfunction "I5_5") (pintype "input"))
    )
    (net (code "707") (name "Net-(IC111A-Q4)") (class "Default")
      (node (ref "IC111") (pin "1") (pinfunction "Q4_1") (pintype "output"))
      (node (ref "IC114") (pin "4") (pinfunction "I4_4") (pintype "input"))
    )
    (net (code "708") (name "Net-(IC111A-Q5)") (class "Default")
      (node (ref "IC111") (pin "6") (pinfunction "Q5_6") (pintype "output"))
      (node (ref "IC114") (pin "3") (pinfunction "I3_3") (pintype "input"))
    )
    (net (code "709") (name "Net-(IC113-ADJ)") (class "Default")
      (node (ref "IC113") (pin "1") (pinfunction "ADJ_1") (pintype "input"))
      (node (ref "R462") (pin "1") (pinfunction "1_1") (pintype "passive"))
      (node (ref "R469") (pin "2") (pinfunction "2_2") (pintype "passive"))
      (node (ref "X31") (pin "7") (pinfunction "7_7") (pintype "passive"))
    )
    (net (code "710") (name "Net-(IC113-VI)") (class "Default")
      (node (ref "IC113") (pin "3") (pinfunction "VI_3") (pintype "input"))
      (node (ref "Q74") (pin "2") (pinfunction "C_2") (pintype "passive"))
    )
    (net (code "711") (name "Net-(IC113-VO)") (class "Default")
      (node (ref "IC113") (pin "2") (pinfunction "VO_2") (pintype "passive"))
      (node (ref "R462") (pin "2") (pinfunction "2_2") (pintype "passive"))
    )
    (net (code "712") (name "Net-(IC114-O2)") (class "Default")
      (node (ref "IC114") (pin "15") (pinfunction "O2_15") (pintype "open_collector"))
      (node (ref "R484") (pin "1") (pinfunction "1_1") (pintype "passive"))
    )
    (net (code "713") (name "Net-(IC115A-+IN)") (class "Default")
      (node (ref "IC115") (pin "5") (pinfunction "+IN_5") (pintype "input"))
      (node (ref "R473") (pin "1") (pinfunction "1_1") (pintype "passive"))
      (node (ref "R474") (pin "2") (pinfunction "2_2") (pintype "passive"))
      (node (ref "R475") (pin "2") (pinfunction "2_2") (pintype "passive"))
    )
    (net (code "714") (name "Net-(IC115A--IN)") (class "Default")
      (node (ref "C102") (pin "1") (pinfunction "1_1") (pintype "passive"))
      (node (ref "IC115") (pin "4") (pinfunction "-IN_4") (pintype "input"))
      (node (ref "R472") (pin "1") (pinfunction "1_1") (pintype "passive"))
    )
    (net (code "715") (name "Net-(IC115B-+IN)") (class "Default")
      (node (ref "IC115") (pin "7") (pinfunction "+IN_7") (pintype "input"))
      (node (ref "R470") (pin "1") (pinfunction "1_1") (pintype "passive"))
      (node (ref "R487") (pin "1") (pinfunction "1_1") (pintype "passive"))
    )
    (net (code "716") (name "Net-(IC115B--IN)") (class "Default")
      (node (ref "IC115") (pin "6") (pinfunction "-IN_6") (pintype "input"))
      (node (ref "IC115") (pin "8") (pinfunction "-IN_8") (pintype "input"))
      (node (ref "R469") (pin "1") (pinfunction "1_1") (pintype "passive"))
    )
    (net (code "717") (name "Net-(IC115B-OUT)") (class "Default")
      (node (ref "IC115") (pin "1") (pinfunction "OUT_1") (pintype "open_collector"))
      (node (ref "R471") (pin "2") (pinfunction "2_2") (pintype "passive"))
      (node (ref "R476") (pin "2") (pinfunction "2_2") (pintype "passive"))
    )
    (net (code "718") (name "Net-(IC115C-+IN)") (class "Default")
      (node (ref "C105") (pin "1") (pinfunction "1_1") (pintype "passive"))
      (node (ref "IC115") (pin "9") (pinfunction "+IN_9") (pintype "input"))
      (node (ref "R478") (pin "2") (pinfunction "2_2") (pintype "passive"))
      (node (ref "R487") (pin "2") (pinfunction "2_2") (pintype "passive"))
    )
    (net (code "719") (name "Net-(IC115C-OUT)") (class "Default")
      (node (ref "C106") (pin "2") (pinfunction "2_2") (pintype "passive"))
      (node (ref "IC115") (pin "14") (pinfunction "OUT_14") (pintype "open_collector"))
      (node (ref "R477") (pin "2") (pinfunction "2_2") (pintype "passive"))
    )
    (net (code "720") (name "Net-(IC117-CV)") (class "Default")
      (node (ref "IC117") (pin "5") (pinfunction "CV_5") (pintype "input"))
      (node (ref "R493") (pin "2") (pinfunction "2_2") (pintype "passive"))
    )
    (net (code "721") (name "Net-(IC117-Q)") (class "Default")
      (node (ref "IC117") (pin "3") (pinfunction "Q_3") (pintype "output"))
      (node (ref "IC118") (pin "12") (pinfunction "A_12") (pintype "input"))
      (node (ref "R493") (pin "1") (pinfunction "1_1") (pintype "passive"))
    )
    (net (code "722") (name "Net-(IC118B-B)") (class "Default")
      (node (ref "IC118") (pin "11") (pinfunction "B_11") (pintype "input"))
      (node (ref "IC118") (pin "9") (pinfunction "~{Q}_9") (pintype "output"))
      (node (ref "R499") (pin "2") (pinfunction "2_2") (pintype "passive"))
    )
    (net (code "723") (name "Net-(IC118B-T2)") (class "Default")
      (node (ref "C109") (pin "1") (pinfunction "1_1") (pintype "passive"))
      (node (ref "IC118") (pin "14") (pinfunction "T2_14") (pintype "input"))
      (node (ref "R497") (pin "1") (pinfunction "1_1") (pintype "passive"))
    )
    (net (code "724") (name "Net-(IC120A-+IN)") (class "Default")
      (node (ref "C104") (pin "1") (pinfunction "1_1") (pintype "passive"))
      (node (ref "IC120") (pin "3") (pinfunction "+IN_3") (pintype "input"))
      (node (ref "R467") (pin "1") (pinfunction "1_1") (pintype "passive"))
    )
    (net (code "725") (name "Net-(IC120A--IN)") (class "Default")
      (node (ref "IC120") (pin "2") (pinfunction "-IN_2") (pintype "input"))
      (node (ref "R468") (pin "2") (pinfunction "2_2") (pintype "passive"))
    )
    (net (code "726") (name "Net-(IC120A-OUT)") (class "Default")
      (node (ref "IC120") (pin "1") (pinfunction "OUT_1") (pintype "output"))
      (node (ref "R500") (pin "2") (pinfunction "2_2") (pintype "passive"))
    )
    (net (code "727") (name "Net-(IC120B-+IN)") (class "Default")
      (node (ref "IC120") (pin "5") (pinfunction "+IN_5") (pintype "input"))
      (node (ref "R501") (pin "2") (pinfunction "2_2") (pintype "passive"))
      (node (ref "R502") (pin "2") (pinfunction "2_2") (pintype "passive"))
    )
    (net (code "728") (name "Net-(IC120B--IN)") (class "Default")
      (node (ref "IC120") (pin "6") (pinfunction "-IN_6") (pintype "input"))
      (node (ref "R503") (pin "1") (pinfunction "1_1") (pintype "passive"))
      (node (ref "R504") (pin "2") (pinfunction "2_2") (pintype "passive"))
    )
    (net (code "729") (name "Net-(IC120B-OUT)") (class "Default")
      (node (ref "IC120") (pin "7") (pinfunction "OUT_7") (pintype "output"))
      (node (ref "R488") (pin "1") (pinfunction "1_1") (pintype "passive"))
      (node (ref "R502") (pin "1") (pinfunction "1_1") (pintype "passive"))
    )
    (net (code "730") (name "Net-(IC122A-A)") (class "Default")
      (node (ref "IC122") (pin "10") (pinfunction "A_10") (pintype "input"))
      (node (ref "R512") (pin "1") (pinfunction "1_1") (pintype "passive"))
      (node (ref "X34") (pin "4") (pinfunction "4_4") (pintype "passive"))
      (node (ref "X35") (pin "2") (pinfunction "S_2") (pintype "passive"))
    )
    (net (code "731") (name "Net-(IC122A-B)") (class "Default")
      (node (ref "IC122") (pin "13") (pinfunction "B_13") (pintype "input"))
      (node (ref "R511") (pin "1") (pinfunction "1_1") (pintype "passive"))
      (node (ref "X34") (pin "3") (pinfunction "3_3") (pintype "passive"))
      (node (ref "X35") (pin "3") (pinfunction "S_3") (pintype "passive"))
    )
    (net (code "732") (name "Net-(IC122A-C)") (class "Default")
      (node (ref "IC122") (pin "12") (pinfunction "C_12") (pintype "input"))
      (node (ref "R510") (pin "1") (pinfunction "1_1") (pintype "passive"))
      (node (ref "X34") (pin "2") (pinfunction "2_2") (pintype "passive"))
      (node (ref "X35") (pin "4") (pinfunction "S_4") (pintype "passive"))
    )
    (net (code "733") (name "Net-(IC122A-Q0)") (class "Default")
      (node (ref "IC122") (pin "3") (pinfunction "Q0_3") (pintype "output"))
      (node (ref "IC125") (pin "1") (pinfunction "I1_1") (pintype "input"))
      (node (ref "IC125") (pin "2") (pinfunction "I2_2") (pintype "input"))
      (node (ref "Q84") (pin "1") (pinfunction "G_1") (pintype "passive"))
    )
    (net (code "734") (name "Net-(IC122A-Q1)") (class "Default")
      (node (ref "IC122") (pin "14") (pinfunction "Q1_14") (pintype "output"))
      (node (ref "IC125") (pin "6") (pinfunction "I6_6") (pintype "input"))
    )
    (net (code "735") (name "Net-(IC122A-Q2)") (class "Default")
      (node (ref "IC122") (pin "2") (pinfunction "Q2_2") (pintype "output"))
      (node (ref "IC125") (pin "7") (pinfunction "I7_7") (pintype "input"))
    )
    (net (code "736") (name "Net-(IC122A-Q3)") (class "Default")
      (node (ref "IC122") (pin "15") (pinfunction "Q3_15") (pintype "output"))
      (node (ref "IC125") (pin "5") (pinfunction "I5_5") (pintype "input"))
    )
    (net (code "737") (name "Net-(IC122A-Q4)") (class "Default")
      (node (ref "IC122") (pin "1") (pinfunction "Q4_1") (pintype "output"))
      (node (ref "IC125") (pin "4") (pinfunction "I4_4") (pintype "input"))
    )
    (net (code "738") (name "Net-(IC122A-Q5)") (class "Default")
      (node (ref "IC122") (pin "6") (pinfunction "Q5_6") (pintype "output"))
      (node (ref "IC125") (pin "3") (pinfunction "I3_3") (pintype "input"))
    )
    (net (code "739") (name "Net-(IC124-ADJ)") (class "Default")
      (node (ref "IC124") (pin "1") (pinfunction "ADJ_1") (pintype "input"))
      (node (ref "R508") (pin "1") (pinfunction "1_1") (pintype "passive"))
      (node (ref "R515") (pin "2") (pinfunction "2_2") (pintype "passive"))
      (node (ref "X34") (pin "7") (pinfunction "7_7") (pintype "passive"))
    )
    (net (code "740") (name "Net-(IC124-VI)") (class "Default")
      (node (ref "IC124") (pin "3") (pinfunction "VI_3") (pintype "input"))
      (node (ref "Q81") (pin "2") (pinfunction "C_2") (pintype "passive"))
    )
    (net (code "741") (name "Net-(IC124-VO)") (class "Default")
      (node (ref "IC124") (pin "2") (pinfunction "VO_2") (pintype "passive"))
      (node (ref "R508") (pin "2") (pinfunction "2_2") (pintype "passive"))
    )
    (net (code "742") (name "Net-(IC125-O2)") (class "Default")
      (node (ref "IC125") (pin "15") (pinfunction "O2_15") (pintype "open_collector"))
      (node (ref "R530") (pin "1") (pinfunction "1_1") (pintype "passive"))
    )
    (net (code "743") (name "Net-(IC126A-+IN)") (class "Default")
      (node (ref "IC126") (pin "5") (pinfunction "+IN_5") (pintype "input"))
      (node (ref "R519") (pin "1") (pinfunction "1_1") (pintype "passive"))
      (node (ref "R520") (pin "2") (pinfunction "2_2") (pintype "passive"))
      (node (ref "R521") (pin "2") (pinfunction "2_2") (pintype "passive"))
    )
    (net (code "744") (name "Net-(IC126A--IN)") (class "Default")
      (node (ref "C112") (pin "1") (pinfunction "1_1") (pintype "passive"))
      (node (ref "IC126") (pin "4") (pinfunction "-IN_4") (pintype "input"))
      (node (ref "R518") (pin "1") (pinfunction "1_1") (pintype "passive"))
    )
    (net (code "745") (name "Net-(IC126B-+IN)") (class "Default")
      (node (ref "IC126") (pin "7") (pinfunction "+IN_7") (pintype "input"))
      (node (ref "R516") (pin "1") (pinfunction "1_1") (pintype "passive"))
      (node (ref "R533") (pin "1") (pinfunction "1_1") (pintype "passive"))
    )
    (net (code "746") (name "Net-(IC126B--IN)") (class "Default")
      (node (ref "IC126") (pin "6") (pinfunction "-IN_6") (pintype "input"))
      (node (ref "IC126") (pin "8") (pinfunction "-IN_8") (pintype "input"))
      (node (ref "R515") (pin "1") (pinfunction "1_1") (pintype "passive"))
    )
    (net (code "747") (name "Net-(IC126B-OUT)") (class "Default")
      (node (ref "IC126") (pin "1") (pinfunction "OUT_1") (pintype "open_collector"))
      (node (ref "R517") (pin "2") (pinfunction "2_2") (pintype "passive"))
      (node (ref "R522") (pin "2") (pinfunction "2_2") (pintype "passive"))
    )
    (net (code "748") (name "Net-(IC126C-+IN)") (class "Default")
      (node (ref "C115") (pin "1") (pinfunction "1_1") (pintype "passive"))
      (node (ref "IC126") (pin "9") (pinfunction "+IN_9") (pintype "input"))
      (node (ref "R524") (pin "2") (pinfunction "2_2") (pintype "passive"))
      (node (ref "R533") (pin "2") (pinfunction "2_2") (pintype "passive"))
    )
    (net (code "749") (name "Net-(IC126C-OUT)") (class "Default")
      (node (ref "C116") (pin "2") (pinfunction "2_2") (pintype "passive"))
      (node (ref "IC126") (pin "14") (pinfunction "OUT_14") (pintype "open_collector"))
      (node (ref "R523") (pin "2") (pinfunction "2_2") (pintype "passive"))
    )
    (net (code "750") (name "Net-(IC128-CV)") (class "Default")
      (node (ref "IC128") (pin "5") (pinfunction "CV_5") (pintype "input"))
      (node (ref "R539") (pin "2") (pinfunction "2_2") (pintype "passive"))
    )
    (net (code "751") (name "Net-(IC128-Q)") (class "Default")
      (node (ref "IC128") (pin "3") (pinfunction "Q_3") (pintype "output"))
      (node (ref "IC129") (pin "12") (pinfunction "A_12") (pintype "input"))
      (node (ref "R539") (pin "1") (pinfunction "1_1") (pintype "passive"))
    )
    (net (code "752") (name "Net-(IC129B-B)") (class "Default")
      (node (ref "IC129") (pin "11") (pinfunction "B_11") (pintype "input"))
      (node (ref "IC129") (pin "9") (pinfunction "~{Q}_9") (pintype "output"))
      (node (ref "R545") (pin "2") (pinfunction "2_2") (pintype "passive"))
    )
    (net (code "753") (name "Net-(IC129B-T2)") (class "Default")
      (node (ref "C119") (pin "1") (pinfunction "1_1") (pintype "passive"))
      (node (ref "IC129") (pin "14") (pinfunction "T2_14") (pintype "input"))
      (node (ref "R543") (pin "1") (pinfunction "1_1") (pintype "passive"))
    )
    (net (code "754") (name "Net-(IC131A-+IN)") (class "Default")
      (node (ref "C114") (pin "1") (pinfunction "1_1") (pintype "passive"))
      (node (ref "IC131") (pin "3") (pinfunction "+IN_3") (pintype "input"))
      (node (ref "R513") (pin "1") (pinfunction "1_1") (pintype "passive"))
    )
    (net (code "755") (name "Net-(IC131A--IN)") (class "Default")
      (node (ref "IC131") (pin "2") (pinfunction "-IN_2") (pintype "input"))
      (node (ref "R514") (pin "2") (pinfunction "2_2") (pintype "passive"))
    )
    (net (code "756") (name "Net-(IC131A-OUT)") (class "Default")
      (node (ref "IC131") (pin "1") (pinfunction "OUT_1") (pintype "output"))
      (node (ref "R546") (pin "2") (pinfunction "2_2") (pintype "passive"))
    )
    (net (code "757") (name "Net-(IC131B-+IN)") (class "Default")
      (node (ref "IC131") (pin "5") (pinfunction "+IN_5") (pintype "input"))
      (node (ref "R547") (pin "2") (pinfunction "2_2") (pintype "passive"))
      (node (ref "R548") (pin "2") (pinfunction "2_2") (pintype "passive"))
    )
    (net (code "758") (name "Net-(IC131B--IN)") (class "Default")
      (node (ref "IC131") (pin "6") (pinfunction "-IN_6") (pintype "input"))
      (node (ref "R549") (pin "1") (pinfunction "1_1") (pintype "passive"))
      (node (ref "R550") (pin "2") (pinfunction "2_2") (pintype "passive"))
    )
    (net (code "759") (name "Net-(IC131B-OUT)") (class "Default")
      (node (ref "IC131") (pin "7") (pinfunction "OUT_7") (pintype "output"))
      (node (ref "R534") (pin "1") (pinfunction "1_1") (pintype "passive"))
      (node (ref "R548") (pin "1") (pinfunction "1_1") (pintype "passive"))
    )
    (net (code "760") (name "Net-(JP1-Pad1)") (class "Default")
      (node (ref "JP1") (pin "1") (pinfunction "1_1") (pintype "passive"))
      (node (ref "R19") (pin "2") (pinfunction "2_2") (pintype "passive"))
    )
    (net (code "761") (name "Net-(JP4-Pad2)") (class "Default")
      (node (ref "JP4") (pin "2") (pinfunction "2_2") (pintype "passive"))
      (node (ref "R36") (pin "2") (pinfunction "2_2") (pintype "passive"))
      (node (ref "R37") (pin "2") (pinfunction "2_2") (pintype "passive"))
      (node (ref "SJ1") (pin "2") (pinfunction "2_2") (pintype "passive"))
    )
    (net (code "762") (name "Net-(JP5-Pad3)") (class "Default")
      (node (ref "JP5") (pin "3") (pinfunction "3_3") (pintype "passive"))
      (node (ref "R38") (pin "1") (pinfunction "1_1") (pintype "passive"))
      (node (ref "R39") (pin "1") (pinfunction "1_1") (pintype "passive"))
    )
    (net (code "763") (name "Net-(JP6-Pad1)") (class "Default")
      (node (ref "JP6") (pin "1") (pinfunction "1_1") (pintype "passive"))
      (node (ref "R84") (pin "2") (pinfunction "2_2") (pintype "passive"))
    )
    (net (code "764") (name "Net-(JP7-Pad3)") (class "Default")
      (node (ref "JP7") (pin "3") (pinfunction "3_3") (pintype "passive"))
      (node (ref "R75") (pin "1") (pinfunction "1_1") (pintype "passive"))
      (node (ref "R76") (pin "1") (pinfunction "1_1") (pintype "passive"))
    )
    (net (code "765") (name "Net-(JP10-Pad2)") (class "Default")
      (node (ref "JP10") (pin "2") (pinfunction "2_2") (pintype "passive"))
      (node (ref "R81") (pin "2") (pinfunction "2_2") (pintype "passive"))
      (node (ref "R82") (pin "2") (pinfunction "2_2") (pintype "passive"))
      (node (ref "SJ2") (pin "2") (pinfunction "2_2") (pintype "passive"))
    )
    (net (code "766") (name "Net-(JP11-Pad1)") (class "Default")
      (node (ref "JP11") (pin "1") (pinfunction "1_1") (pintype "passive"))
      (node (ref "R130") (pin "2") (pinfunction "2_2") (pintype "passive"))
    )
    (net (code "767") (name "Net-(JP12-Pad3)") (class "Default")
      (node (ref "JP12") (pin "3") (pinfunction "3_3") (pintype "passive"))
      (node (ref "R121") (pin "1") (pinfunction "1_1") (pintype "passive"))
      (node (ref "R122") (pin "1") (pinfunction "1_1") (pintype "passive"))
    )
    (net (code "768") (name "Net-(JP15-Pad2)") (class "Default")
      (node (ref "JP15") (pin "2") (pinfunction "2_2") (pintype "passive"))
      (node (ref "R127") (pin "2") (pinfunction "2_2") (pintype "passive"))
      (node (ref "R128") (pin "2") (pinfunction "2_2") (pintype "passive"))
      (node (ref "SJ3") (pin "2") (pinfunction "2_2") (pintype "passive"))
    )
    (net (code "769") (name "Net-(JP16-Pad1)") (class "Default")
      (node (ref "JP16") (pin "1") (pinfunction "1_1") (pintype "passive"))
      (node (ref "R176") (pin "2") (pinfunction "2_2") (pintype "passive"))
    )
    (net (code "770") (name "Net-(JP17-Pad3)") (class "Default")
      (node (ref "JP17") (pin "3") (pinfunction "3_3") (pintype "passive"))
      (node (ref "R167") (pin "1") (pinfunction "1_1") (pintype "passive"))
      (node (ref "R168") (pin "1") (pinfunction "1_1") (pintype "passive"))
    )
    (net (code "771") (name "Net-(JP20-Pad2)") (class "Default")
      (node (ref "JP20") (pin "2") (pinfunction "2_2") (pintype "passive"))
      (node (ref "R173") (pin "2") (pinfunction "2_2") (pintype "passive"))
      (node (ref "R174") (pin "2") (pinfunction "2_2") (pintype "passive"))
      (node (ref "SJ4") (pin "2") (pinfunction "2_2") (pintype "passive"))
    )
    (net (code "772") (name "Net-(JP21-Pad1)") (class "Default")
      (node (ref "JP21") (pin "1") (pinfunction "1_1") (pintype "passive"))
      (node (ref "R222") (pin "2") (pinfunction "2_2") (pintype "passive"))
    )
    (net (code "773") (name "Net-(JP22-Pad3)") (class "Default")
      (node (ref "JP22") (pin "3") (pinfunction "3_3") (pintype "passive"))
      (node (ref "R213") (pin "1") (pinfunction "1_1") (pintype "passive"))
      (node (ref "R214") (pin "1") (pinfunction "1_1") (pintype "passive"))
    )
    (net (code "774") (name "Net-(JP25-Pad2)") (class "Default")
      (node (ref "JP25") (pin "2") (pinfunction "2_2") (pintype "passive"))
      (node (ref "R219") (pin "2") (pinfunction "2_2") (pintype "passive"))
      (node (ref "R220") (pin "2") (pinfunction "2_2") (pintype "passive"))
      (node (ref "SJ5") (pin "2") (pinfunction "2_2") (pintype "passive"))
    )
    (net (code "775") (name "Net-(JP26-Pad1)") (class "Default")
      (node (ref "JP26") (pin "1") (pinfunction "1_1") (pintype "passive"))
      (node (ref "R268") (pin "2") (pinfunction "2_2") (pintype "passive"))
    )
    (net (code "776") (name "Net-(JP27-Pad3)") (class "Default")
      (node (ref "JP27") (pin "3") (pinfunction "3_3") (pintype "passive"))
      (node (ref "R259") (pin "1") (pinfunction "1_1") (pintype "passive"))
      (node (ref "R260") (pin "1") (pinfunction "1_1") (pintype "passive"))
    )
    (net (code "777") (name "Net-(JP30-Pad2)") (class "Default")
      (node (ref "JP30") (pin "2") (pinfunction "2_2") (pintype "passive"))
      (node (ref "R265") (pin "2") (pinfunction "2_2") (pintype "passive"))
      (node (ref "R266") (pin "2") (pinfunction "2_2") (pintype "passive"))
      (node (ref "SJ6") (pin "2") (pinfunction "2_2") (pintype "passive"))
    )
    (net (code "778") (name "Net-(JP31-Pad1)") (class "Default")
      (node (ref "JP31") (pin "1") (pinfunction "1_1") (pintype "passive"))
      (node (ref "R314") (pin "2") (pinfunction "2_2") (pintype "passive"))
    )
    (net (code "779") (name "Net-(JP32-Pad3)") (class "Default")
      (node (ref "JP32") (pin "3") (pinfunction "3_3") (pintype "passive"))
      (node (ref "R305") (pin "1") (pinfunction "1_1") (pintype "passive"))
      (node (ref "R306") (pin "1") (pinfunction "1_1") (pintype "passive"))
    )
    (net (code "780") (name "Net-(JP35-Pad2)") (class "Default")
      (node (ref "JP35") (pin "2") (pinfunction "2_2") (pintype "passive"))
      (node (ref "R311") (pin "2") (pinfunction "2_2") (pintype "passive"))
      (node (ref "R312") (pin "2") (pinfunction "2_2") (pintype "passive"))
      (node (ref "SJ7") (pin "2") (pinfunction "2_2") (pintype "passive"))
    )
    (net (code "781") (name "Net-(JP36-Pad1)") (class "Default")
      (node (ref "JP36") (pin "1") (pinfunction "1_1") (pintype "passive"))
      (node (ref "R360") (pin "2") (pinfunction "2_2") (pintype "passive"))
    )
    (net (code "782") (name "Net-(JP37-Pad3)") (class "Default")
      (node (ref "JP37") (pin "3") (pinfunction "3_3") (pintype "passive"))
      (node (ref "R351") (pin "1") (pinfunction "1_1") (pintype "passive"))
      (node (ref "R352") (pin "1") (pinfunction "1_1") (pintype "passive"))
    )
    (net (code "783") (name "Net-(JP40-Pad2)") (class "Default")
      (node (ref "JP40") (pin "2") (pinfunction "2_2") (pintype "passive"))
      (node (ref "R357") (pin "2") (pinfunction "2_2") (pintype "passive"))
      (node (ref "R358") (pin "2") (pinfunction "2_2") (pintype "passive"))
      (node (ref "SJ8") (pin "2") (pinfunction "2_2") (pintype "passive"))
    )
    (net (code "784") (name "Net-(JP41-Pad1)") (class "Default")
      (node (ref "JP41") (pin "1") (pinfunction "1_1") (pintype "passive"))
      (node (ref "R406") (pin "2") (pinfunction "2_2") (pintype "passive"))
    )
    (net (code "785") (name "Net-(JP42-Pad3)") (class "Default")
      (node (ref "JP42") (pin "3") (pinfunction "3_3") (pintype "passive"))
      (node (ref "R397") (pin "1") (pinfunction "1_1") (pintype "passive"))
      (node (ref "R398") (pin "1") (pinfunction "1_1") (pintype "passive"))
    )
    (net (code "786") (name "Net-(JP45-Pad2)") (class "Default")
      (node (ref "JP45") (pin "2") (pinfunction "2_2") (pintype "passive"))
      (node (ref "R403") (pin "2") (pinfunction "2_2") (pintype "passive"))
      (node (ref "R404") (pin "2") (pinfunction "2_2") (pintype "passive"))
      (node (ref "SJ9") (pin "2") (pinfunction "2_2") (pintype "passive"))
    )
    (net (code "787") (name "Net-(JP46-Pad1)") (class "Default")
      (node (ref "JP46") (pin "1") (pinfunction "1_1") (pintype "passive"))
      (node (ref "R452") (pin "2") (pinfunction "2_2") (pintype "passive"))
    )
    (net (code "788") (name "Net-(JP47-Pad3)") (class "Default")
      (node (ref "JP47") (pin "3") (pinfunction "3_3") (pintype "passive"))
      (node (ref "R443") (pin "1") (pinfunction "1_1") (pintype "passive"))
      (node (ref "R444") (pin "1") (pinfunction "1_1") (pintype "passive"))
    )
    (net (code "789") (name "Net-(JP50-Pad2)") (class "Default")
      (node (ref "JP50") (pin "2") (pinfunction "2_2") (pintype "passive"))
      (node (ref "R449") (pin "2") (pinfunction "2_2") (pintype "passive"))
      (node (ref "R450") (pin "2") (pinfunction "2_2") (pintype "passive"))
      (node (ref "SJ10") (pin "2") (pinfunction "2_2") (pintype "passive"))
    )
    (net (code "790") (name "Net-(JP51-Pad1)") (class "Default")
      (node (ref "JP51") (pin "1") (pinfunction "1_1") (pintype "passive"))
      (node (ref "R498") (pin "2") (pinfunction "2_2") (pintype "passive"))
    )
    (net (code "791") (name "Net-(JP52-Pad3)") (class "Default")
      (node (ref "JP52") (pin "3") (pinfunction "3_3") (pintype "passive"))
      (node (ref "R489") (pin "1") (pinfunction "1_1") (pintype "passive"))
      (node (ref "R490") (pin "1") (pinfunction "1_1") (pintype "passive"))
    )
    (net (code "792") (name "Net-(JP55-Pad2)") (class "Default")
      (node (ref "JP55") (pin "2") (pinfunction "2_2") (pintype "passive"))
      (node (ref "R495") (pin "2") (pinfunction "2_2") (pintype "passive"))
      (node (ref "R496") (pin "2") (pinfunction "2_2") (pintype "passive"))
      (node (ref "SJ11") (pin "2") (pinfunction "2_2") (pintype "passive"))
    )
    (net (code "793") (name "Net-(JP56-Pad1)") (class "Default")
      (node (ref "JP56") (pin "1") (pinfunction "1_1") (pintype "passive"))
      (node (ref "R544") (pin "2") (pinfunction "2_2") (pintype "passive"))
    )
    (net (code "794") (name "Net-(JP57-Pad3)") (class "Default")
      (node (ref "JP57") (pin "3") (pinfunction "3_3") (pintype "passive"))
      (node (ref "R535") (pin "1") (pinfunction "1_1") (pintype "passive"))
      (node (ref "R536") (pin "1") (pinfunction "1_1") (pintype "passive"))
    )
    (net (code "795") (name "Net-(JP60-Pad2)") (class "Default")
      (node (ref "JP60") (pin "2") (pinfunction "2_2") (pintype "passive"))
      (node (ref "R541") (pin "2") (pinfunction "2_2") (pintype "passive"))
      (node (ref "R542") (pin "2") (pinfunction "2_2") (pintype "passive"))
      (node (ref "SJ12") (pin "2") (pinfunction "2_2") (pintype "passive"))
    )
    (net (code "796") (name "Net-(LED1-C)") (class "Default")
      (node (ref "LED1") (pin "K") (pinfunction "C_K") (pintype "passive"))
      (node (ref "R43") (pin "1") (pinfunction "1_1") (pintype "passive"))
    )
    (net (code "797") (name "Net-(LED2-PadA)") (class "Default")
      (node (ref "LED2") (pin "A") (pinfunction "A_A") (pintype "passive"))
      (node (ref "LED3") (pin "A") (pinfunction "A_A") (pintype "passive"))
      (node (ref "LED4") (pin "A") (pinfunction "A_A") (pintype "passive"))
      (node (ref "LED5") (pin "A") (pinfunction "A_A") (pintype "passive"))
      (node (ref "LED6") (pin "A") (pinfunction "A_A") (pintype "passive"))
      (node (ref "R42") (pin "1") (pinfunction "1_1") (pintype "passive"))
    )
    (net (code "798") (name "Net-(LED10-PadA)") (class "Default")
      (node (ref "LED10") (pin "A") (pinfunction "A_A") (pintype "passive"))
      (node (ref "LED12") (pin "A") (pinfunction "A_A") (pintype "passive"))
      (node (ref "LED7") (pin "A") (pinfunction "A_A") (pintype "passive"))
      (node (ref "LED8") (pin "A") (pinfunction "A_A") (pintype "passive"))
      (node (ref "LED9") (pin "A") (pinfunction "A_A") (pintype "passive"))
      (node (ref "R69") (pin "1") (pinfunction "1_1") (pintype "passive"))
    )
    (net (code "799") (name "Net-(LED11-C)") (class "Default")
      (node (ref "LED11") (pin "K") (pinfunction "C_K") (pintype "passive"))
      (node (ref "R68") (pin "1") (pinfunction "1_1") (pintype "passive"))
    )
    (net (code "800") (name "Net-(LED13-PadA)") (class "Default")
      (node (ref "LED13") (pin "A") (pinfunction "A_A") (pintype "passive"))
      (node (ref "LED14") (pin "A") (pinfunction "A_A") (pintype "passive"))
      (node (ref "LED15") (pin "A") (pinfunction "A_A") (pintype "passive"))
      (node (ref "LED16") (pin "A") (pinfunction "A_A") (pintype "passive"))
      (node (ref "LED18") (pin "A") (pinfunction "A_A") (pintype "passive"))
      (node (ref "R115") (pin "1") (pinfunction "1_1") (pintype "passive"))
    )
    (net (code "801") (name "Net-(LED17-C)") (class "Default")
      (node (ref "LED17") (pin "K") (pinfunction "C_K") (pintype "passive"))
      (node (ref "R114") (pin "1") (pinfunction "1_1") (pintype "passive"))
    )
    (net (code "802") (name "Net-(LED19-PadA)") (class "Default")
      (node (ref "LED19") (pin "A") (pinfunction "A_A") (pintype "passive"))
      (node (ref "LED20") (pin "A") (pinfunction "A_A") (pintype "passive"))
      (node (ref "LED21") (pin "A") (pinfunction "A_A") (pintype "passive"))
      (node (ref "LED22") (pin "A") (pinfunction "A_A") (pintype "passive"))
      (node (ref "LED24") (pin "A") (pinfunction "A_A") (pintype "passive"))
      (node (ref "R161") (pin "1") (pinfunction "1_1") (pintype "passive"))
    )
    (net (code "803") (name "Net-(LED23-C)") (class "Default")
      (node (ref "LED23") (pin "K") (pinfunction "C_K") (pintype "passive"))
      (node (ref "R160") (pin "1") (pinfunction "1_1") (pintype "passive"))
    )
    (net (code "804") (name "Net-(LED25-PadA)") (class "Default")
      (node (ref "LED25") (pin "A") (pinfunction "A_A") (pintype "passive"))
      (node (ref "LED26") (pin "A") (pinfunction "A_A") (pintype "passive"))
      (node (ref "LED27") (pin "A") (pinfunction "A_A") (pintype "passive"))
      (node (ref "LED28") (pin "A") (pinfunction "A_A") (pintype "passive"))
      (node (ref "LED30") (pin "A") (pinfunction "A_A") (pintype "passive"))
      (node (ref "R207") (pin "1") (pinfunction "1_1") (pintype "passive"))
    )
    (net (code "805") (name "Net-(LED29-C)") (class "Default")
      (node (ref "LED29") (pin "K") (pinfunction "C_K") (pintype "passive"))
      (node (ref "R206") (pin "1") (pinfunction "1_1") (pintype "passive"))
    )
    (net (code "806") (name "Net-(LED31-PadA)") (class "Default")
      (node (ref "LED31") (pin "A") (pinfunction "A_A") (pintype "passive"))
      (node (ref "LED32") (pin "A") (pinfunction "A_A") (pintype "passive"))
      (node (ref "LED33") (pin "A") (pinfunction "A_A") (pintype "passive"))
      (node (ref "LED34") (pin "A") (pinfunction "A_A") (pintype "passive"))
      (node (ref "LED36") (pin "A") (pinfunction "A_A") (pintype "passive"))
      (node (ref "R253") (pin "1") (pinfunction "1_1") (pintype "passive"))
    )
    (net (code "807") (name "Net-(LED35-C)") (class "Default")
      (node (ref "LED35") (pin "K") (pinfunction "C_K") (pintype "passive"))
      (node (ref "R252") (pin "1") (pinfunction "1_1") (pintype "passive"))
    )
    (net (code "808") (name "Net-(LED37-PadA)") (class "Default")
      (node (ref "LED37") (pin "A") (pinfunction "A_A") (pintype "passive"))
      (node (ref "LED38") (pin "A") (pinfunction "A_A") (pintype "passive"))
      (node (ref "LED39") (pin "A") (pinfunction "A_A") (pintype "passive"))
      (node (ref "LED40") (pin "A") (pinfunction "A_A") (pintype "passive"))
      (node (ref "LED42") (pin "A") (pinfunction "A_A") (pintype "passive"))
      (node (ref "R299") (pin "1") (pinfunction "1_1") (pintype "passive"))
    )
    (net (code "809") (name "Net-(LED41-C)") (class "Default")
      (node (ref "LED41") (pin "K") (pinfunction "C_K") (pintype "passive"))
      (node (ref "R298") (pin "1") (pinfunction "1_1") (pintype "passive"))
    )
    (net (code "810") (name "Net-(LED43-PadA)") (class "Default")
      (node (ref "LED43") (pin "A") (pinfunction "A_A") (pintype "passive"))
      (node (ref "LED44") (pin "A") (pinfunction "A_A") (pintype "passive"))
      (node (ref "LED45") (pin "A") (pinfunction "A_A") (pintype "passive"))
      (node (ref "LED46") (pin "A") (pinfunction "A_A") (pintype "passive"))
      (node (ref "LED48") (pin "A") (pinfunction "A_A") (pintype "passive"))
      (node (ref "R345") (pin "1") (pinfunction "1_1") (pintype "passive"))
    )
    (net (code "811") (name "Net-(LED47-C)") (class "Default")
      (node (ref "LED47") (pin "K") (pinfunction "C_K") (pintype "passive"))
      (node (ref "R344") (pin "1") (pinfunction "1_1") (pintype "passive"))
    )
    (net (code "812") (name "Net-(LED49-PadA)") (class "Default")
      (node (ref "LED49") (pin "A") (pinfunction "A_A") (pintype "passive"))
      (node (ref "LED50") (pin "A") (pinfunction "A_A") (pintype "passive"))
      (node (ref "LED51") (pin "A") (pinfunction "A_A") (pintype "passive"))
      (node (ref "LED52") (pin "A") (pinfunction "A_A") (pintype "passive"))
      (node (ref "LED54") (pin "A") (pinfunction "A_A") (pintype "passive"))
      (node (ref "R391") (pin "1") (pinfunction "1_1") (pintype "passive"))
    )
    (net (code "813") (name "Net-(LED53-C)") (class "Default")
      (node (ref "LED53") (pin "K") (pinfunction "C_K") (pintype "passive"))
      (node (ref "R390") (pin "1") (pinfunction "1_1") (pintype "passive"))
    )
    (net (code "814") (name "Net-(LED55-PadA)") (class "Default")
      (node (ref "LED55") (pin "A") (pinfunction "A_A") (pintype "passive"))
      (node (ref "LED56") (pin "A") (pinfunction "A_A") (pintype "passive"))
      (node (ref "LED57") (pin "A") (pinfunction "A_A") (pintype "passive"))
      (node (ref "LED58") (pin "A") (pinfunction "A_A") (pintype "passive"))
      (node (ref "LED60") (pin "A") (pinfunction "A_A") (pintype "passive"))
      (node (ref "R437") (pin "1") (pinfunction "1_1") (pintype "passive"))
    )
    (net (code "815") (name "Net-(LED59-C)") (class "Default")
      (node (ref "LED59") (pin "K") (pinfunction "C_K") (pintype "passive"))
      (node (ref "R436") (pin "1") (pinfunction "1_1") (pintype "passive"))
    )
    (net (code "816") (name "Net-(LED61-PadA)") (class "Default")
      (node (ref "LED61") (pin "A") (pinfunction "A_A") (pintype "passive"))
      (node (ref "LED62") (pin "A") (pinfunction "A_A") (pintype "passive"))
      (node (ref "LED63") (pin "A") (pinfunction "A_A") (pintype "passive"))
      (node (ref "LED64") (pin "A") (pinfunction "A_A") (pintype "passive"))
      (node (ref "LED66") (pin "A") (pinfunction "A_A") (pintype "passive"))
      (node (ref "R483") (pin "1") (pinfunction "1_1") (pintype "passive"))
    )
    (net (code "817") (name "Net-(LED65-C)") (class "Default")
      (node (ref "LED65") (pin "K") (pinfunction "C_K") (pintype "passive"))
      (node (ref "R482") (pin "1") (pinfunction "1_1") (pintype "passive"))
    )
    (net (code "818") (name "Net-(LED67-PadA)") (class "Default")
      (node (ref "LED67") (pin "A") (pinfunction "A_A") (pintype "passive"))
      (node (ref "LED68") (pin "A") (pinfunction "A_A") (pintype "passive"))
      (node (ref "LED69") (pin "A") (pinfunction "A_A") (pintype "passive"))
      (node (ref "LED70") (pin "A") (pinfunction "A_A") (pintype "passive"))
      (node (ref "LED72") (pin "A") (pinfunction "A_A") (pintype "passive"))
      (node (ref "R529") (pin "1") (pinfunction "1_1") (pintype "passive"))
    )
    (net (code "819") (name "Net-(LED71-C)") (class "Default")
      (node (ref "LED71") (pin "K") (pinfunction "C_K") (pintype "passive"))
      (node (ref "R528") (pin "1") (pinfunction "1_1") (pintype "passive"))
    )
    (net (code "820") (name "Net-(Q1-B)") (class "Default")
      (node (ref "Q1") (pin "1") (pinfunction "B_1") (pintype "passive"))
      (node (ref "Q2") (pin "1") (pinfunction "B_1") (pintype "passive"))
      (node (ref "Q2") (pin "2") (pinfunction "C_2") (pintype "passive"))
      (node (ref "R1") (pin "1") (pinfunction "1_1") (pintype "passive"))
      (node (ref "R3") (pin "1") (pinfunction "1_1") (pintype "passive"))
      (node (ref "R4") (pin "1") (pinfunction "1_1") (pintype "passive"))
      (node (ref "X2") (pin "2") (pinfunction "S_2") (pintype "passive"))
    )
    (net (code "821") (name "Net-(Q1-E)") (class "Default")
      (node (ref "Q1") (pin "3") (pinfunction "E_3") (pintype "passive"))
      (node (ref "R2") (pin "2") (pinfunction "2_2") (pintype "passive"))
    )
    (net (code "822") (name "Net-(Q2-E)") (class "Default")
      (node (ref "Q2") (pin "3") (pinfunction "E_3") (pintype "passive"))
      (node (ref "R6") (pin "2") (pinfunction "2_2") (pintype "passive"))
    )
    (net (code "823") (name "Net-(Q3-B)") (class "Default")
      (node (ref "Q3") (pin "1") (pinfunction "B_1") (pintype "passive"))
      (node (ref "R16") (pin "2") (pinfunction "2_2") (pintype "passive"))
    )
    (net (code "824") (name "Net-(Q3-C)") (class "Default")
      (node (ref "Q3") (pin "2") (pinfunction "C_2") (pintype "passive"))
      (node (ref "R15") (pin "2") (pinfunction "2_2") (pintype "passive"))
      (node (ref "R18") (pin "1") (pinfunction "1_1") (pintype "passive"))
    )
    (net (code "825") (name "Net-(Q4-B)") (class "Default")
      (node (ref "Q4") (pin "1") (pinfunction "B_1") (pintype "passive"))
      (node (ref "R28") (pin "2") (pinfunction "2_2") (pintype "passive"))
    )
    (net (code "826") (name "Net-(Q5-B)") (class "Default")
      (node (ref "Q5") (pin "1") (pinfunction "B_1") (pintype "passive"))
      (node (ref "R26") (pin "1") (pinfunction "1_1") (pintype "passive"))
    )
    (net (code "827") (name "Net-(Q7-D)") (class "Default")
      (node (ref "Q7") (pin "3") (pinfunction "D_3") (pintype "passive"))
      (node (ref "R38") (pin "2") (pinfunction "2_2") (pintype "passive"))
    )
    (net (code "828") (name "Net-(Q8-B)") (class "Default")
      (node (ref "Q8") (pin "1") (pinfunction "B_1") (pintype "passive"))
      (node (ref "R70") (pin "2") (pinfunction "2_2") (pintype "passive"))
    )
    (net (code "829") (name "Net-(Q9-E)") (class "Default")
      (node (ref "Q9") (pin "3") (pinfunction "E_3") (pintype "passive"))
      (node (ref "R71") (pin "2") (pinfunction "2_2") (pintype "passive"))
    )
    (net (code "830") (name "Net-(Q10-B)") (class "Default")
      (node (ref "Q10") (pin "1") (pinfunction "B_1") (pintype "passive"))
      (node (ref "Q9") (pin "1") (pinfunction "B_1") (pintype "passive"))
      (node (ref "Q9") (pin "2") (pinfunction "C_2") (pintype "passive"))
      (node (ref "R65") (pin "1") (pinfunction "1_1") (pintype "passive"))
      (node (ref "R66") (pin "1") (pinfunction "1_1") (pintype "passive"))
      (node (ref "R92") (pin "1") (pinfunction "1_1") (pintype "passive"))
      (node (ref "X6") (pin "2") (pinfunction "S_2") (pintype "passive"))
    )
    (net (code "831") (name "Net-(Q10-E)") (class "Default")
      (node (ref "Q10") (pin "3") (pinfunction "E_3") (pintype "passive"))
      (node (ref "R72") (pin "2") (pinfunction "2_2") (pintype "passive"))
    )
    (net (code "832") (name "Net-(Q11-B)") (class "Default")
      (node (ref "Q11") (pin "1") (pinfunction "B_1") (pintype "passive"))
      (node (ref "R63") (pin "1") (pinfunction "1_1") (pintype "passive"))
    )
    (net (code "833") (name "Net-(Q12-B)") (class "Default")
      (node (ref "Q12") (pin "1") (pinfunction "B_1") (pintype "passive"))
      (node (ref "R74") (pin "2") (pinfunction "2_2") (pintype "passive"))
    )
    (net (code "834") (name "Net-(Q12-C)") (class "Default")
      (node (ref "Q12") (pin "2") (pinfunction "C_2") (pintype "passive"))
      (node (ref "R67") (pin "2") (pinfunction "2_2") (pintype "passive"))
      (node (ref "R91") (pin "1") (pinfunction "1_1") (pintype "passive"))
    )
    (net (code "835") (name "Net-(Q13-D)") (class "Default")
      (node (ref "Q13") (pin "3") (pinfunction "D_3") (pintype "passive"))
      (node (ref "R75") (pin "2") (pinfunction "2_2") (pintype "passive"))
    )
    (net (code "836") (name "Net-(Q15-B)") (class "Default")
      (node (ref "Q15") (pin "1") (pinfunction "B_1") (pintype "passive"))
      (node (ref "R116") (pin "2") (pinfunction "2_2") (pintype "passive"))
    )
    (net (code "837") (name "Net-(Q16-B)") (class "Default")
      (node (ref "Q16") (pin "1") (pinfunction "B_1") (pintype "passive"))
      (node (ref "Q16") (pin "2") (pinfunction "C_2") (pintype "passive"))
      (node (ref "Q17") (pin "1") (pinfunction "B_1") (pintype "passive"))
      (node (ref "R111") (pin "1") (pinfunction "1_1") (pintype "passive"))
      (node (ref "R112") (pin "1") (pinfunction "1_1") (pintype "passive"))
      (node (ref "R138") (pin "1") (pinfunction "1_1") (pintype "passive"))
      (node (ref "X9") (pin "2") (pinfunction "S_2") (pintype "passive"))
    )
    (net (code "838") (name "Net-(Q16-E)") (class "Default")
      (node (ref "Q16") (pin "3") (pinfunction "E_3") (pintype "passive"))
      (node (ref "R117") (pin "2") (pinfunction "2_2") (pintype "passive"))
    )
    (net (code "839") (name "Net-(Q17-E)") (class "Default")
      (node (ref "Q17") (pin "3") (pinfunction "E_3") (pintype "passive"))
      (node (ref "R118") (pin "2") (pinfunction "2_2") (pintype "passive"))
    )
    (net (code "840") (name "Net-(Q18-B)") (class "Default")
      (node (ref "Q18") (pin "1") (pinfunction "B_1") (pintype "passive"))
      (node (ref "R109") (pin "1") (pinfunction "1_1") (pintype "passive"))
    )
    (net (code "841") (name "Net-(Q19-B)") (class "Default")
      (node (ref "Q19") (pin "1") (pinfunction "B_1") (pintype "passive"))
      (node (ref "R120") (pin "2") (pinfunction "2_2") (pintype "passive"))
    )
    (net (code "842") (name "Net-(Q19-C)") (class "Default")
      (node (ref "Q19") (pin "2") (pinfunction "C_2") (pintype "passive"))
      (node (ref "R113") (pin "2") (pinfunction "2_2") (pintype "passive"))
      (node (ref "R137") (pin "1") (pinfunction "1_1") (pintype "passive"))
    )
    (net (code "843") (name "Net-(Q20-D)") (class "Default")
      (node (ref "Q20") (pin "3") (pinfunction "D_3") (pintype "passive"))
      (node (ref "R121") (pin "2") (pinfunction "2_2") (pintype "passive"))
    )
    (net (code "844") (name "Net-(Q22-B)") (class "Default")
      (node (ref "Q22") (pin "1") (pinfunction "B_1") (pintype "passive"))
      (node (ref "R162") (pin "2") (pinfunction "2_2") (pintype "passive"))
    )
    (net (code "845") (name "Net-(Q23-B)") (class "Default")
      (node (ref "Q23") (pin "1") (pinfunction "B_1") (pintype "passive"))
      (node (ref "Q23") (pin "2") (pinfunction "C_2") (pintype "passive"))
      (node (ref "Q24") (pin "1") (pinfunction "B_1") (pintype "passive"))
      (node (ref "R157") (pin "1") (pinfunction "1_1") (pintype "passive"))
      (node (ref "R158") (pin "1") (pinfunction "1_1") (pintype "passive"))
      (node (ref "R184") (pin "1") (pinfunction "1_1") (pintype "passive"))
      (node (ref "X12") (pin "2") (pinfunction "S_2") (pintype "passive"))
    )
    (net (code "846") (name "Net-(Q23-E)") (class "Default")
      (node (ref "Q23") (pin "3") (pinfunction "E_3") (pintype "passive"))
      (node (ref "R163") (pin "2") (pinfunction "2_2") (pintype "passive"))
    )
    (net (code "847") (name "Net-(Q24-E)") (class "Default")
      (node (ref "Q24") (pin "3") (pinfunction "E_3") (pintype "passive"))
      (node (ref "R164") (pin "2") (pinfunction "2_2") (pintype "passive"))
    )
    (net (code "848") (name "Net-(Q25-B)") (class "Default")
      (node (ref "Q25") (pin "1") (pinfunction "B_1") (pintype "passive"))
      (node (ref "R155") (pin "1") (pinfunction "1_1") (pintype "passive"))
    )
    (net (code "849") (name "Net-(Q26-B)") (class "Default")
      (node (ref "Q26") (pin "1") (pinfunction "B_1") (pintype "passive"))
      (node (ref "R166") (pin "2") (pinfunction "2_2") (pintype "passive"))
    )
    (net (code "850") (name "Net-(Q26-C)") (class "Default")
      (node (ref "Q26") (pin "2") (pinfunction "C_2") (pintype "passive"))
      (node (ref "R159") (pin "2") (pinfunction "2_2") (pintype "passive"))
      (node (ref "R183") (pin "1") (pinfunction "1_1") (pintype "passive"))
    )
    (net (code "851") (name "Net-(Q27-D)") (class "Default")
      (node (ref "Q27") (pin "3") (pinfunction "D_3") (pintype "passive"))
      (node (ref "R167") (pin "2") (pinfunction "2_2") (pintype "passive"))
    )
    (net (code "852") (name "Net-(Q29-B)") (class "Default")
      (node (ref "Q29") (pin "1") (pinfunction "B_1") (pintype "passive"))
      (node (ref "R208") (pin "2") (pinfunction "2_2") (pintype "passive"))
    )
    (net (code "853") (name "Net-(Q30-B)") (class "Default")
      (node (ref "Q30") (pin "1") (pinfunction "B_1") (pintype "passive"))
      (node (ref "Q30") (pin "2") (pinfunction "C_2") (pintype "passive"))
      (node (ref "Q31") (pin "1") (pinfunction "B_1") (pintype "passive"))
      (node (ref "R203") (pin "1") (pinfunction "1_1") (pintype "passive"))
      (node (ref "R204") (pin "1") (pinfunction "1_1") (pintype "passive"))
      (node (ref "R230") (pin "1") (pinfunction "1_1") (pintype "passive"))
      (node (ref "X15") (pin "2") (pinfunction "S_2") (pintype "passive"))
    )
    (net (code "854") (name "Net-(Q30-E)") (class "Default")
      (node (ref "Q30") (pin "3") (pinfunction "E_3") (pintype "passive"))
      (node (ref "R209") (pin "2") (pinfunction "2_2") (pintype "passive"))
    )
    (net (code "855") (name "Net-(Q31-E)") (class "Default")
      (node (ref "Q31") (pin "3") (pinfunction "E_3") (pintype "passive"))
      (node (ref "R210") (pin "2") (pinfunction "2_2") (pintype "passive"))
    )
    (net (code "856") (name "Net-(Q32-B)") (class "Default")
      (node (ref "Q32") (pin "1") (pinfunction "B_1") (pintype "passive"))
      (node (ref "R201") (pin "1") (pinfunction "1_1") (pintype "passive"))
    )
    (net (code "857") (name "Net-(Q33-B)") (class "Default")
      (node (ref "Q33") (pin "1") (pinfunction "B_1") (pintype "passive"))
      (node (ref "R212") (pin "2") (pinfunction "2_2") (pintype "passive"))
    )
    (net (code "858") (name "Net-(Q33-C)") (class "Default")
      (node (ref "Q33") (pin "2") (pinfunction "C_2") (pintype "passive"))
      (node (ref "R205") (pin "2") (pinfunction "2_2") (pintype "passive"))
      (node (ref "R229") (pin "1") (pinfunction "1_1") (pintype "passive"))
    )
    (net (code "859") (name "Net-(Q34-D)") (class "Default")
      (node (ref "Q34") (pin "3") (pinfunction "D_3") (pintype "passive"))
      (node (ref "R213") (pin "2") (pinfunction "2_2") (pintype "passive"))
    )
    (net (code "860") (name "Net-(Q36-B)") (class "Default")
      (node (ref "Q36") (pin "1") (pinfunction "B_1") (pintype "passive"))
      (node (ref "R254") (pin "2") (pinfunction "2_2") (pintype "passive"))
    )
    (net (code "861") (name "Net-(Q37-B)") (class "Default")
      (node (ref "Q37") (pin "1") (pinfunction "B_1") (pintype "passive"))
      (node (ref "Q37") (pin "2") (pinfunction "C_2") (pintype "passive"))
      (node (ref "Q38") (pin "1") (pinfunction "B_1") (pintype "passive"))
      (node (ref "R249") (pin "1") (pinfunction "1_1") (pintype "passive"))
      (node (ref "R250") (pin "1") (pinfunction "1_1") (pintype "passive"))
      (node (ref "R276") (pin "1") (pinfunction "1_1") (pintype "passive"))
      (node (ref "X18") (pin "2") (pinfunction "S_2") (pintype "passive"))
    )
    (net (code "862") (name "Net-(Q37-E)") (class "Default")
      (node (ref "Q37") (pin "3") (pinfunction "E_3") (pintype "passive"))
      (node (ref "R255") (pin "2") (pinfunction "2_2") (pintype "passive"))
    )
    (net (code "863") (name "Net-(Q38-E)") (class "Default")
      (node (ref "Q38") (pin "3") (pinfunction "E_3") (pintype "passive"))
      (node (ref "R256") (pin "2") (pinfunction "2_2") (pintype "passive"))
    )
    (net (code "864") (name "Net-(Q39-B)") (class "Default")
      (node (ref "Q39") (pin "1") (pinfunction "B_1") (pintype "passive"))
      (node (ref "R247") (pin "1") (pinfunction "1_1") (pintype "passive"))
    )
    (net (code "865") (name "Net-(Q40-B)") (class "Default")
      (node (ref "Q40") (pin "1") (pinfunction "B_1") (pintype "passive"))
      (node (ref "R258") (pin "2") (pinfunction "2_2") (pintype "passive"))
    )
    (net (code "866") (name "Net-(Q40-C)") (class "Default")
      (node (ref "Q40") (pin "2") (pinfunction "C_2") (pintype "passive"))
      (node (ref "R251") (pin "2") (pinfunction "2_2") (pintype "passive"))
      (node (ref "R275") (pin "1") (pinfunction "1_1") (pintype "passive"))
    )
    (net (code "867") (name "Net-(Q41-D)") (class "Default")
      (node (ref "Q41") (pin "3") (pinfunction "D_3") (pintype "passive"))
      (node (ref "R259") (pin "2") (pinfunction "2_2") (pintype "passive"))
    )
    (net (code "868") (name "Net-(Q43-B)") (class "Default")
      (node (ref "Q43") (pin "1") (pinfunction "B_1") (pintype "passive"))
      (node (ref "R300") (pin "2") (pinfunction "2_2") (pintype "passive"))
    )
    (net (code "869") (name "Net-(Q44-B)") (class "Default")
      (node (ref "Q44") (pin "1") (pinfunction "B_1") (pintype "passive"))
      (node (ref "Q44") (pin "2") (pinfunction "C_2") (pintype "passive"))
      (node (ref "Q45") (pin "1") (pinfunction "B_1") (pintype "passive"))
      (node (ref "R295") (pin "1") (pinfunction "1_1") (pintype "passive"))
      (node (ref "R296") (pin "1") (pinfunction "1_1") (pintype "passive"))
      (node (ref "R322") (pin "1") (pinfunction "1_1") (pintype "passive"))
      (node (ref "X21") (pin "2") (pinfunction "S_2") (pintype "passive"))
    )
    (net (code "870") (name "Net-(Q44-E)") (class "Default")
      (node (ref "Q44") (pin "3") (pinfunction "E_3") (pintype "passive"))
      (node (ref "R301") (pin "2") (pinfunction "2_2") (pintype "passive"))
    )
    (net (code "871") (name "Net-(Q45-E)") (class "Default")
      (node (ref "Q45") (pin "3") (pinfunction "E_3") (pintype "passive"))
      (node (ref "R302") (pin "2") (pinfunction "2_2") (pintype "passive"))
    )
    (net (code "872") (name "Net-(Q46-B)") (class "Default")
      (node (ref "Q46") (pin "1") (pinfunction "B_1") (pintype "passive"))
      (node (ref "R293") (pin "1") (pinfunction "1_1") (pintype "passive"))
    )
    (net (code "873") (name "Net-(Q47-B)") (class "Default")
      (node (ref "Q47") (pin "1") (pinfunction "B_1") (pintype "passive"))
      (node (ref "R304") (pin "2") (pinfunction "2_2") (pintype "passive"))
    )
    (net (code "874") (name "Net-(Q47-C)") (class "Default")
      (node (ref "Q47") (pin "2") (pinfunction "C_2") (pintype "passive"))
      (node (ref "R297") (pin "2") (pinfunction "2_2") (pintype "passive"))
      (node (ref "R321") (pin "1") (pinfunction "1_1") (pintype "passive"))
    )
    (net (code "875") (name "Net-(Q48-D)") (class "Default")
      (node (ref "Q48") (pin "3") (pinfunction "D_3") (pintype "passive"))
      (node (ref "R305") (pin "2") (pinfunction "2_2") (pintype "passive"))
    )
    (net (code "876") (name "Net-(Q50-B)") (class "Default")
      (node (ref "Q50") (pin "1") (pinfunction "B_1") (pintype "passive"))
      (node (ref "R346") (pin "2") (pinfunction "2_2") (pintype "passive"))
    )
    (net (code "877") (name "Net-(Q51-B)") (class "Default")
      (node (ref "Q51") (pin "1") (pinfunction "B_1") (pintype "passive"))
      (node (ref "Q51") (pin "2") (pinfunction "C_2") (pintype "passive"))
      (node (ref "Q52") (pin "1") (pinfunction "B_1") (pintype "passive"))
      (node (ref "R341") (pin "1") (pinfunction "1_1") (pintype "passive"))
      (node (ref "R342") (pin "1") (pinfunction "1_1") (pintype "passive"))
      (node (ref "R368") (pin "1") (pinfunction "1_1") (pintype "passive"))
      (node (ref "X24") (pin "2") (pinfunction "S_2") (pintype "passive"))
    )
    (net (code "878") (name "Net-(Q51-E)") (class "Default")
      (node (ref "Q51") (pin "3") (pinfunction "E_3") (pintype "passive"))
      (node (ref "R347") (pin "2") (pinfunction "2_2") (pintype "passive"))
    )
    (net (code "879") (name "Net-(Q52-E)") (class "Default")
      (node (ref "Q52") (pin "3") (pinfunction "E_3") (pintype "passive"))
      (node (ref "R348") (pin "2") (pinfunction "2_2") (pintype "passive"))
    )
    (net (code "880") (name "Net-(Q53-B)") (class "Default")
      (node (ref "Q53") (pin "1") (pinfunction "B_1") (pintype "passive"))
      (node (ref "R339") (pin "1") (pinfunction "1_1") (pintype "passive"))
    )
    (net (code "881") (name "Net-(Q54-B)") (class "Default")
      (node (ref "Q54") (pin "1") (pinfunction "B_1") (pintype "passive"))
      (node (ref "R350") (pin "2") (pinfunction "2_2") (pintype "passive"))
    )
    (net (code "882") (name "Net-(Q54-C)") (class "Default")
      (node (ref "Q54") (pin "2") (pinfunction "C_2") (pintype "passive"))
      (node (ref "R343") (pin "2") (pinfunction "2_2") (pintype "passive"))
      (node (ref "R367") (pin "1") (pinfunction "1_1") (pintype "passive"))
    )
    (net (code "883") (name "Net-(Q55-D)") (class "Default")
      (node (ref "Q55") (pin "3") (pinfunction "D_3") (pintype "passive"))
      (node (ref "R351") (pin "2") (pinfunction "2_2") (pintype "passive"))
    )
    (net (code "884") (name "Net-(Q57-B)") (class "Default")
      (node (ref "Q57") (pin "1") (pinfunction "B_1") (pintype "passive"))
      (node (ref "R392") (pin "2") (pinfunction "2_2") (pintype "passive"))
    )
    (net (code "885") (name "Net-(Q58-B)") (class "Default")
      (node (ref "Q58") (pin "1") (pinfunction "B_1") (pintype "passive"))
      (node (ref "Q58") (pin "2") (pinfunction "C_2") (pintype "passive"))
      (node (ref "Q59") (pin "1") (pinfunction "B_1") (pintype "passive"))
      (node (ref "R387") (pin "1") (pinfunction "1_1") (pintype "passive"))
      (node (ref "R388") (pin "1") (pinfunction "1_1") (pintype "passive"))
      (node (ref "R414") (pin "1") (pinfunction "1_1") (pintype "passive"))
      (node (ref "X27") (pin "2") (pinfunction "S_2") (pintype "passive"))
    )
    (net (code "886") (name "Net-(Q58-E)") (class "Default")
      (node (ref "Q58") (pin "3") (pinfunction "E_3") (pintype "passive"))
      (node (ref "R393") (pin "2") (pinfunction "2_2") (pintype "passive"))
    )
    (net (code "887") (name "Net-(Q59-E)") (class "Default")
      (node (ref "Q59") (pin "3") (pinfunction "E_3") (pintype "passive"))
      (node (ref "R394") (pin "2") (pinfunction "2_2") (pintype "passive"))
    )
    (net (code "888") (name "Net-(Q60-B)") (class "Default")
      (node (ref "Q60") (pin "1") (pinfunction "B_1") (pintype "passive"))
      (node (ref "R385") (pin "1") (pinfunction "1_1") (pintype "passive"))
    )
    (net (code "889") (name "Net-(Q61-B)") (class "Default")
      (node (ref "Q61") (pin "1") (pinfunction "B_1") (pintype "passive"))
      (node (ref "R396") (pin "2") (pinfunction "2_2") (pintype "passive"))
    )
    (net (code "890") (name "Net-(Q61-C)") (class "Default")
      (node (ref "Q61") (pin "2") (pinfunction "C_2") (pintype "passive"))
      (node (ref "R389") (pin "2") (pinfunction "2_2") (pintype "passive"))
      (node (ref "R413") (pin "1") (pinfunction "1_1") (pintype "passive"))
    )
    (net (code "891") (name "Net-(Q62-D)") (class "Default")
      (node (ref "Q62") (pin "3") (pinfunction "D_3") (pintype "passive"))
      (node (ref "R397") (pin "2") (pinfunction "2_2") (pintype "passive"))
    )
    (net (code "892") (name "Net-(Q64-B)") (class "Default")
      (node (ref "Q64") (pin "1") (pinfunction "B_1") (pintype "passive"))
      (node (ref "R438") (pin "2") (pinfunction "2_2") (pintype "passive"))
    )
    (net (code "893") (name "Net-(Q65-B)") (class "Default")
      (node (ref "Q65") (pin "1") (pinfunction "B_1") (pintype "passive"))
      (node (ref "Q65") (pin "2") (pinfunction "C_2") (pintype "passive"))
      (node (ref "Q66") (pin "1") (pinfunction "B_1") (pintype "passive"))
      (node (ref "R433") (pin "1") (pinfunction "1_1") (pintype "passive"))
      (node (ref "R434") (pin "1") (pinfunction "1_1") (pintype "passive"))
      (node (ref "R460") (pin "1") (pinfunction "1_1") (pintype "passive"))
      (node (ref "X30") (pin "2") (pinfunction "S_2") (pintype "passive"))
    )
    (net (code "894") (name "Net-(Q65-E)") (class "Default")
      (node (ref "Q65") (pin "3") (pinfunction "E_3") (pintype "passive"))
      (node (ref "R439") (pin "2") (pinfunction "2_2") (pintype "passive"))
    )
    (net (code "895") (name "Net-(Q66-E)") (class "Default")
      (node (ref "Q66") (pin "3") (pinfunction "E_3") (pintype "passive"))
      (node (ref "R440") (pin "2") (pinfunction "2_2") (pintype "passive"))
    )
    (net (code "896") (name "Net-(Q67-B)") (class "Default")
      (node (ref "Q67") (pin "1") (pinfunction "B_1") (pintype "passive"))
      (node (ref "R431") (pin "1") (pinfunction "1_1") (pintype "passive"))
    )
    (net (code "897") (name "Net-(Q68-B)") (class "Default")
      (node (ref "Q68") (pin "1") (pinfunction "B_1") (pintype "passive"))
      (node (ref "R442") (pin "2") (pinfunction "2_2") (pintype "passive"))
    )
    (net (code "898") (name "Net-(Q68-C)") (class "Default")
      (node (ref "Q68") (pin "2") (pinfunction "C_2") (pintype "passive"))
      (node (ref "R435") (pin "2") (pinfunction "2_2") (pintype "passive"))
      (node (ref "R459") (pin "1") (pinfunction "1_1") (pintype "passive"))
    )
    (net (code "899") (name "Net-(Q69-D)") (class "Default")
      (node (ref "Q69") (pin "3") (pinfunction "D_3") (pintype "passive"))
      (node (ref "R443") (pin "2") (pinfunction "2_2") (pintype "passive"))
    )
    (net (code "900") (name "Net-(Q71-B)") (class "Default")
      (node (ref "Q71") (pin "1") (pinfunction "B_1") (pintype "passive"))
      (node (ref "R484") (pin "2") (pinfunction "2_2") (pintype "passive"))
    )
    (net (code "901") (name "Net-(Q72-B)") (class "Default")
      (node (ref "Q72") (pin "1") (pinfunction "B_1") (pintype "passive"))
      (node (ref "Q72") (pin "2") (pinfunction "C_2") (pintype "passive"))
      (node (ref "Q73") (pin "1") (pinfunction "B_1") (pintype "passive"))
      (node (ref "R479") (pin "1") (pinfunction "1_1") (pintype "passive"))
      (node (ref "R480") (pin "1") (pinfunction "1_1") (pintype "passive"))
      (node (ref "R506") (pin "1") (pinfunction "1_1") (pintype "passive"))
      (node (ref "X33") (pin "2") (pinfunction "S_2") (pintype "passive"))
    )
    (net (code "902") (name "Net-(Q72-E)") (class "Default")
      (node (ref "Q72") (pin "3") (pinfunction "E_3") (pintype "passive"))
      (node (ref "R485") (pin "2") (pinfunction "2_2") (pintype "passive"))
    )
    (net (code "903") (name "Net-(Q73-E)") (class "Default")
      (node (ref "Q73") (pin "3") (pinfunction "E_3") (pintype "passive"))
      (node (ref "R486") (pin "2") (pinfunction "2_2") (pintype "passive"))
    )
    (net (code "904") (name "Net-(Q74-B)") (class "Default")
      (node (ref "Q74") (pin "1") (pinfunction "B_1") (pintype "passive"))
      (node (ref "R477") (pin "1") (pinfunction "1_1") (pintype "passive"))
    )
    (net (code "905") (name "Net-(Q75-B)") (class "Default")
      (node (ref "Q75") (pin "1") (pinfunction "B_1") (pintype "passive"))
      (node (ref "R488") (pin "2") (pinfunction "2_2") (pintype "passive"))
    )
    (net (code "906") (name "Net-(Q75-C)") (class "Default")
      (node (ref "Q75") (pin "2") (pinfunction "C_2") (pintype "passive"))
      (node (ref "R481") (pin "2") (pinfunction "2_2") (pintype "passive"))
      (node (ref "R505") (pin "1") (pinfunction "1_1") (pintype "passive"))
    )
    (net (code "907") (name "Net-(Q76-D)") (class "Default")
      (node (ref "Q76") (pin "3") (pinfunction "D_3") (pintype "passive"))
      (node (ref "R489") (pin "2") (pinfunction "2_2") (pintype "passive"))
    )
    (net (code "908") (name "Net-(Q78-B)") (class "Default")
      (node (ref "Q78") (pin "1") (pinfunction "B_1") (pintype "passive"))
      (node (ref "R530") (pin "2") (pinfunction "2_2") (pintype "passive"))
    )
    (net (code "909") (name "Net-(Q79-B)") (class "Default")
      (node (ref "Q79") (pin "1") (pinfunction "B_1") (pintype "passive"))
      (node (ref "Q79") (pin "2") (pinfunction "C_2") (pintype "passive"))
      (node (ref "Q80") (pin "1") (pinfunction "B_1") (pintype "passive"))
      (node (ref "R525") (pin "1") (pinfunction "1_1") (pintype "passive"))
      (node (ref "R526") (pin "1") (pinfunction "1_1") (pintype "passive"))
      (node (ref "R552") (pin "1") (pinfunction "1_1") (pintype "passive"))
      (node (ref "X36") (pin "2") (pinfunction "S_2") (pintype "passive"))
    )
    (net (code "910") (name "Net-(Q79-E)") (class "Default")
      (node (ref "Q79") (pin "3") (pinfunction "E_3") (pintype "passive"))
      (node (ref "R531") (pin "2") (pinfunction "2_2") (pintype "passive"))
    )
    (net (code "911") (name "Net-(Q80-E)") (class "Default")
      (node (ref "Q80") (pin "3") (pinfunction "E_3") (pintype "passive"))
      (node (ref "R532") (pin "2") (pinfunction "2_2") (pintype "passive"))
    )
    (net (code "912") (name "Net-(Q81-B)") (class "Default")
      (node (ref "Q81") (pin "1") (pinfunction "B_1") (pintype "passive"))
      (node (ref "R523") (pin "1") (pinfunction "1_1") (pintype "passive"))
    )
    (net (code "913") (name "Net-(Q82-B)") (class "Default")
      (node (ref "Q82") (pin "1") (pinfunction "B_1") (pintype "passive"))
      (node (ref "R534") (pin "2") (pinfunction "2_2") (pintype "passive"))
    )
    (net (code "914") (name "Net-(Q82-C)") (class "Default")
      (node (ref "Q82") (pin "2") (pinfunction "C_2") (pintype "passive"))
      (node (ref "R527") (pin "2") (pinfunction "2_2") (pintype "passive"))
      (node (ref "R551") (pin "1") (pinfunction "1_1") (pintype "passive"))
    )
    (net (code "915") (name "Net-(Q83-D)") (class "Default")
      (node (ref "Q83") (pin "3") (pinfunction "D_3") (pintype "passive"))
      (node (ref "R535") (pin "2") (pinfunction "2_2") (pintype "passive"))
    )
    (net (code "916") (name "Net-(R15-Pad1)") (class "Default")
      (node (ref "R15") (pin "1") (pinfunction "1_1") (pintype "passive"))
      (node (ref "X1") (pin "21") (pinfunction "21_21") (pintype "passive"))
    )
    (net (code "917") (name "Net-(R27-Pad2)") (class "Default")
      (node (ref "R27") (pin "2") (pinfunction "2_2") (pintype "passive"))
      (node (ref "R29") (pin "1") (pinfunction "1_1") (pintype "passive"))
    )
    (net (code "918") (name "Net-(R40-Pad2)") (class "Default")
      (node (ref "R40") (pin "2") (pinfunction "2_2") (pintype "passive"))
      (node (ref "X1") (pin "16") (pinfunction "16_16") (pintype "passive"))
    )
    (net (code "919") (name "Net-(R47-Pad2)") (class "Default")
      (node (ref "R47") (pin "2") (pinfunction "2_2") (pintype "passive"))
      (node (ref "R49") (pin "1") (pinfunction "1_1") (pintype "passive"))
    )
    (net (code "920") (name "Net-(R67-Pad1)") (class "Default")
      (node (ref "R67") (pin "1") (pinfunction "1_1") (pintype "passive"))
      (node (ref "X4") (pin "21") (pinfunction "21_21") (pintype "passive"))
    )
    (net (code "921") (name "Net-(R80-Pad2)") (class "Default")
      (node (ref "R80") (pin "2") (pinfunction "2_2") (pintype "passive"))
      (node (ref "X4") (pin "16") (pinfunction "16_16") (pintype "passive"))
    )
    (net (code "922") (name "Net-(R93-Pad2)") (class "Default")
      (node (ref "R93") (pin "2") (pinfunction "2_2") (pintype "passive"))
      (node (ref "R95") (pin "1") (pinfunction "1_1") (pintype "passive"))
    )
    (net (code "923") (name "Net-(R113-Pad1)") (class "Default")
      (node (ref "R113") (pin "1") (pinfunction "1_1") (pintype "passive"))
      (node (ref "X7") (pin "21") (pinfunction "21_21") (pintype "passive"))
    )
    (net (code "924") (name "Net-(R126-Pad2)") (class "Default")
      (node (ref "R126") (pin "2") (pinfunction "2_2") (pintype "passive"))
      (node (ref "X7") (pin "16") (pinfunction "16_16") (pintype "passive"))
    )
    (net (code "925") (name "Net-(R139-Pad2)") (class "Default")
      (node (ref "R139") (pin "2") (pinfunction "2_2") (pintype "passive"))
      (node (ref "R141") (pin "1") (pinfunction "1_1") (pintype "passive"))
    )
    (net (code "926") (name "Net-(R159-Pad1)") (class "Default")
      (node (ref "R159") (pin "1") (pinfunction "1_1") (pintype "passive"))
      (node (ref "X10") (pin "21") (pinfunction "21_21") (pintype "passive"))
    )
    (net (code "927") (name "Net-(R172-Pad2)") (class "Default")
      (node (ref "R172") (pin "2") (pinfunction "2_2") (pintype "passive"))
      (node (ref "X10") (pin "16") (pinfunction "16_16") (pintype "passive"))
    )
    (net (code "928") (name "Net-(R185-Pad2)") (class "Default")
      (node (ref "R185") (pin "2") (pinfunction "2_2") (pintype "passive"))
      (node (ref "R187") (pin "1") (pinfunction "1_1") (pintype "passive"))
    )
    (net (code "929") (name "Net-(R205-Pad1)") (class "Default")
      (node (ref "R205") (pin "1") (pinfunction "1_1") (pintype "passive"))
      (node (ref "X13") (pin "21") (pinfunction "21_21") (pintype "passive"))
    )
    (net (code "930") (name "Net-(R218-Pad2)") (class "Default")
      (node (ref "R218") (pin "2") (pinfunction "2_2") (pintype "passive"))
      (node (ref "X13") (pin "16") (pinfunction "16_16") (pintype "passive"))
    )
    (net (code "931") (name "Net-(R231-Pad2)") (class "Default")
      (node (ref "R231") (pin "2") (pinfunction "2_2") (pintype "passive"))
      (node (ref "R233") (pin "1") (pinfunction "1_1") (pintype "passive"))
    )
    (net (code "932") (name "Net-(R251-Pad1)") (class "Default")
      (node (ref "R251") (pin "1") (pinfunction "1_1") (pintype "passive"))
      (node (ref "X16") (pin "21") (pinfunction "21_21") (pintype "passive"))
    )
    (net (code "933") (name "Net-(R264-Pad2)") (class "Default")
      (node (ref "R264") (pin "2") (pinfunction "2_2") (pintype "passive"))
      (node (ref "X16") (pin "16") (pinfunction "16_16") (pintype "passive"))
    )
    (net (code "934") (name "Net-(R277-Pad2)") (class "Default")
      (node (ref "R277") (pin "2") (pinfunction "2_2") (pintype "passive"))
      (node (ref "R279") (pin "1") (pinfunction "1_1") (pintype "passive"))
    )
    (net (code "935") (name "Net-(R297-Pad1)") (class "Default")
      (node (ref "R297") (pin "1") (pinfunction "1_1") (pintype "passive"))
      (node (ref "X19") (pin "21") (pinfunction "21_21") (pintype "passive"))
    )
    (net (code "936") (name "Net-(R310-Pad2)") (class "Default")
      (node (ref "R310") (pin "2") (pinfunction "2_2") (pintype "passive"))
      (node (ref "X19") (pin "16") (pinfunction "16_16") (pintype "passive"))
    )
    (net (code "937") (name "Net-(R323-Pad2)") (class "Default")
      (node (ref "R323") (pin "2") (pinfunction "2_2") (pintype "passive"))
      (node (ref "R325") (pin "1") (pinfunction "1_1") (pintype "passive"))
    )
    (net (code "938") (name "Net-(R343-Pad1)") (class "Default")
      (node (ref "R343") (pin "1") (pinfunction "1_1") (pintype "passive"))
      (node (ref "X22") (pin "21") (pinfunction "21_21") (pintype "passive"))
    )
    (net (code "939") (name "Net-(R356-Pad2)") (class "Default")
      (node (ref "R356") (pin "2") (pinfunction "2_2") (pintype "passive"))
      (node (ref "X22") (pin "16") (pinfunction "16_16") (pintype "passive"))
    )
    (net (code "940") (name "Net-(R369-Pad2)") (class "Default")
      (node (ref "R369") (pin "2") (pinfunction "2_2") (pintype "passive"))
      (node (ref "R371") (pin "1") (pinfunction "1_1") (pintype "passive"))
    )
    (net (code "941") (name "Net-(R389-Pad1)") (class "Default")
      (node (ref "R389") (pin "1") (pinfunction "1_1") (pintype "passive"))
      (node (ref "X25") (pin "21") (pinfunction "21_21") (pintype "passive"))
    )
    (net (code "942") (name "Net-(R402-Pad2)") (class "Default")
      (node (ref "R402") (pin "2") (pinfunction "2_2") (pintype "passive"))
      (node (ref "X25") (pin "16") (pinfunction "16_16") (pintype "passive"))
    )
    (net (code "943") (name "Net-(R415-Pad2)") (class "Default")
      (node (ref "R415") (pin "2") (pinfunction "2_2") (pintype "passive"))
      (node (ref "R417") (pin "1") (pinfunction "1_1") (pintype "passive"))
    )
    (net (code "944") (name "Net-(R435-Pad1)") (class "Default")
      (node (ref "R435") (pin "1") (pinfunction "1_1") (pintype "passive"))
      (node (ref "X28") (pin "21") (pinfunction "21_21") (pintype "passive"))
    )
    (net (code "945") (name "Net-(R448-Pad2)") (class "Default")
      (node (ref "R448") (pin "2") (pinfunction "2_2") (pintype "passive"))
      (node (ref "X28") (pin "16") (pinfunction "16_16") (pintype "passive"))
    )
    (net (code "946") (name "Net-(R461-Pad2)") (class "Default")
      (node (ref "R461") (pin "2") (pinfunction "2_2") (pintype "passive"))
      (node (ref "R463") (pin "1") (pinfunction "1_1") (pintype "passive"))
    )
    (net (code "947") (name "Net-(R481-Pad1)") (class "Default")
      (node (ref "R481") (pin "1") (pinfunction "1_1") (pintype "passive"))
      (node (ref "X31") (pin "21") (pinfunction "21_21") (pintype "passive"))
    )
    (net (code "948") (name "Net-(R494-Pad2)") (class "Default")
      (node (ref "R494") (pin "2") (pinfunction "2_2") (pintype "passive"))
      (node (ref "X31") (pin "16") (pinfunction "16_16") (pintype "passive"))
    )
    (net (code "949") (name "Net-(R507-Pad2)") (class "Default")
      (node (ref "R507") (pin "2") (pinfunction "2_2") (pintype "passive"))
      (node (ref "R509") (pin "1") (pinfunction "1_1") (pintype "passive"))
    )
    (net (code "950") (name "Net-(R527-Pad1)") (class "Default")
      (node (ref "R527") (pin "1") (pinfunction "1_1") (pintype "passive"))
      (node (ref "X34") (pin "21") (pinfunction "21_21") (pintype "passive"))
    )
    (net (code "951") (name "Net-(R540-Pad2)") (class "Default")
      (node (ref "R540") (pin "2") (pinfunction "2_2") (pintype "passive"))
      (node (ref "X34") (pin "16") (pinfunction "16_16") (pintype "passive"))
    )
    (net (code "952") (name "VCC") (class "Default")
      (node (ref "6V") (pin "TP") (pinfunction "PP_TP") (pintype "input"))
      (node (ref "6V1") (pin "TP") (pinfunction "PP_TP") (pintype "input"))
      (node (ref "6V10") (pin "TP") (pinfunction "PP_TP") (pintype "input"))
      (node (ref "6V11") (pin "TP") (pinfunction "PP_TP") (pintype "input"))
      (node (ref "6V2") (pin "TP") (pinfunction "PP_TP") (pintype "input"))
      (node (ref "6V3") (pin "TP") (pinfunction "PP_TP") (pintype "input"))
      (node (ref "6V4") (pin "TP") (pinfunction "PP_TP") (pintype "input"))
      (node (ref "6V5") (pin "TP") (pinfunction "PP_TP") (pintype "input"))
      (node (ref "6V6") (pin "TP") (pinfunction "PP_TP") (pintype "input"))
      (node (ref "6V7") (pin "TP") (pinfunction "PP_TP") (pintype "input"))
      (node (ref "6V8") (pin "TP") (pinfunction "PP_TP") (pintype "input"))
      (node (ref "6V9") (pin "TP") (pinfunction "PP_TP") (pintype "input"))
      (node (ref "C103") (pin "1") (pinfunction "1_1") (pintype "passive"))
      (node (ref "C113") (pin "1") (pinfunction "1_1") (pintype "passive"))
      (node (ref "C13") (pin "1") (pinfunction "1_1") (pintype "passive"))
      (node (ref "C23") (pin "1") (pinfunction "1_1") (pintype "passive"))
      (node (ref "C33") (pin "1") (pinfunction "1_1") (pintype "passive"))
      (node (ref "C4") (pin "1") (pinfunction "1_1") (pintype "passive"))
      (node (ref "C43") (pin "1") (pinfunction "1_1") (pintype "passive"))
      (node (ref "C53") (pin "1") (pinfunction "1_1") (pintype "passive"))
      (node (ref "C63") (pin "1") (pinfunction "1_1") (pintype "passive"))
      (node (ref "C73") (pin "1") (pinfunction "1_1") (pintype "passive"))
      (node (ref "C83") (pin "1") (pinfunction "1_1") (pintype "passive"))
      (node (ref "C93") (pin "1") (pinfunction "1_1") (pintype "passive"))
      (node (ref "IC1") (pin "8") (pinfunction "V+_8") (pintype "power_in"))
      (node (ref "IC101") (pin "OUT") (pinfunction "OUT_OUT") (pintype "passive"))
      (node (ref "IC104") (pin "3") (pinfunction "V+_3") (pintype "power_in"))
      (node (ref "IC105") (pin "1") (pinfunction "OUT_1") (pintype "passive"))
      (node (ref "IC109") (pin "8") (pinfunction "V+_8") (pintype "power_in"))
      (node (ref "IC112") (pin "OUT") (pinfunction "OUT_OUT") (pintype "passive"))
      (node (ref "IC115") (pin "3") (pinfunction "V+_3") (pintype "power_in"))
      (node (ref "IC116") (pin "1") (pinfunction "OUT_1") (pintype "passive"))
      (node (ref "IC120") (pin "8") (pinfunction "V+_8") (pintype "power_in"))
      (node (ref "IC123") (pin "OUT") (pinfunction "OUT_OUT") (pintype "passive"))
      (node (ref "IC126") (pin "3") (pinfunction "V+_3") (pintype "power_in"))
      (node (ref "IC127") (pin "1") (pinfunction "OUT_1") (pintype "passive"))
      (node (ref "IC13") (pin "OUT") (pinfunction "OUT_OUT") (pintype "passive"))
      (node (ref "IC131") (pin "8") (pinfunction "V+_8") (pintype "power_in"))
      (node (ref "IC16") (pin "3") (pinfunction "V+_3") (pintype "power_in"))
      (node (ref "IC17") (pin "1") (pinfunction "OUT_1") (pintype "passive"))
      (node (ref "IC2") (pin "1") (pinfunction "OUT_1") (pintype "passive"))
      (node (ref "IC21") (pin "8") (pinfunction "V+_8") (pintype "power_in"))
      (node (ref "IC24") (pin "OUT") (pinfunction "OUT_OUT") (pintype "passive"))
      (node (ref "IC27") (pin "3") (pinfunction "V+_3") (pintype "power_in"))
      (node (ref "IC28") (pin "1") (pinfunction "OUT_1") (pintype "passive"))
      (node (ref "IC3") (pin "OUT") (pinfunction "OUT_OUT") (pintype "passive"))
      (node (ref "IC32") (pin "8") (pinfunction "V+_8") (pintype "power_in"))
      (node (ref "IC35") (pin "OUT") (pinfunction "OUT_OUT") (pintype "passive"))
      (node (ref "IC38") (pin "3") (pinfunction "V+_3") (pintype "power_in"))
      (node (ref "IC39") (pin "1") (pinfunction "OUT_1") (pintype "passive"))
      (node (ref "IC43") (pin "8") (pinfunction "V+_8") (pintype "power_in"))
      (node (ref "IC46") (pin "OUT") (pinfunction "OUT_OUT") (pintype "passive"))
      (node (ref "IC49") (pin "3") (pinfunction "V+_3") (pintype "power_in"))
      (node (ref "IC50") (pin "1") (pinfunction "OUT_1") (pintype "passive"))
      (node (ref "IC54") (pin "8") (pinfunction "V+_8") (pintype "power_in"))
      (node (ref "IC57") (pin "OUT") (pinfunction "OUT_OUT") (pintype "passive"))
      (node (ref "IC60") (pin "3") (pinfunction "V+_3") (pintype "power_in"))
      (node (ref "IC61") (pin "1") (pinfunction "OUT_1") (pintype "passive"))
      (node (ref "IC65") (pin "8") (pinfunction "V+_8") (pintype "power_in"))
      (node (ref "IC68") (pin "OUT") (pinfunction "OUT_OUT") (pintype "passive"))
      (node (ref "IC71") (pin "3") (pinfunction "V+_3") (pintype "power_in"))
      (node (ref "IC72") (pin "1") (pinfunction "OUT_1") (pintype "passive"))
      (node (ref "IC76") (pin "8") (pinfunction "V+_8") (pintype "power_in"))
      (node (ref "IC79") (pin "OUT") (pinfunction "OUT_OUT") (pintype "passive"))
      (node (ref "IC8") (pin "3") (pinfunction "V+_3") (pintype "power_in"))
      (node (ref "IC82") (pin "3") (pinfunction "V+_3") (pintype "power_in"))
      (node (ref "IC83") (pin "1") (pinfunction "OUT_1") (pintype "passive"))
      (node (ref "IC87") (pin "8") (pinfunction "V+_8") (pintype "power_in"))
      (node (ref "IC90") (pin "OUT") (pinfunction "OUT_OUT") (pintype "passive"))
      (node (ref "IC93") (pin "3") (pinfunction "V+_3") (pintype "power_in"))
      (node (ref "IC94") (pin "1") (pinfunction "OUT_1") (pintype "passive"))
      (node (ref "IC98") (pin "8") (pinfunction "V+_8") (pintype "power_in"))
      (node (ref "R102") (pin "2") (pinfunction "2_2") (pintype "passive"))
      (node (ref "R105") (pin "2") (pinfunction "2_2") (pintype "passive"))
      (node (ref "R108") (pin "1") (pinfunction "1_1") (pintype "passive"))
      (node (ref "R115") (pin "2") (pinfunction "2_2") (pintype "passive"))
      (node (ref "R13") (pin "2") (pinfunction "2_2") (pintype "passive"))
      (node (ref "R135") (pin "2") (pinfunction "2_2") (pintype "passive"))
      (node (ref "R148") (pin "2") (pinfunction "2_2") (pintype "passive"))
      (node (ref "R151") (pin "2") (pinfunction "2_2") (pintype "passive"))
      (node (ref "R154") (pin "1") (pinfunction "1_1") (pintype "passive"))
      (node (ref "R161") (pin "2") (pinfunction "2_2") (pintype "passive"))
      (node (ref "R181") (pin "2") (pinfunction "2_2") (pintype "passive"))
      (node (ref "R194") (pin "2") (pinfunction "2_2") (pintype "passive"))
      (node (ref "R197") (pin "2") (pinfunction "2_2") (pintype "passive"))
      (node (ref "R200") (pin "1") (pinfunction "1_1") (pintype "passive"))
      (node (ref "R207") (pin "2") (pinfunction "2_2") (pintype "passive"))
      (node (ref "R21") (pin "2") (pinfunction "2_2") (pintype "passive"))
      (node (ref "R227") (pin "2") (pinfunction "2_2") (pintype "passive"))
      (node (ref "R24") (pin "1") (pinfunction "1_1") (pintype "passive"))
      (node (ref "R240") (pin "2") (pinfunction "2_2") (pintype "passive"))
      (node (ref "R243") (pin "2") (pinfunction "2_2") (pintype "passive"))
      (node (ref "R246") (pin "1") (pinfunction "1_1") (pintype "passive"))
      (node (ref "R253") (pin "2") (pinfunction "2_2") (pintype "passive"))
      (node (ref "R273") (pin "2") (pinfunction "2_2") (pintype "passive"))
      (node (ref "R286") (pin "2") (pinfunction "2_2") (pintype "passive"))
      (node (ref "R289") (pin "2") (pinfunction "2_2") (pintype "passive"))
      (node (ref "R292") (pin "1") (pinfunction "1_1") (pintype "passive"))
      (node (ref "R299") (pin "2") (pinfunction "2_2") (pintype "passive"))
      (node (ref "R31") (pin "2") (pinfunction "2_2") (pintype "passive"))
      (node (ref "R319") (pin "2") (pinfunction "2_2") (pintype "passive"))
      (node (ref "R332") (pin "2") (pinfunction "2_2") (pintype "passive"))
      (node (ref "R335") (pin "2") (pinfunction "2_2") (pintype "passive"))
      (node (ref "R338") (pin "1") (pinfunction "1_1") (pintype "passive"))
      (node (ref "R345") (pin "2") (pinfunction "2_2") (pintype "passive"))
      (node (ref "R365") (pin "2") (pinfunction "2_2") (pintype "passive"))
      (node (ref "R378") (pin "2") (pinfunction "2_2") (pintype "passive"))
      (node (ref "R381") (pin "2") (pinfunction "2_2") (pintype "passive"))
      (node (ref "R384") (pin "1") (pinfunction "1_1") (pintype "passive"))
      (node (ref "R391") (pin "2") (pinfunction "2_2") (pintype "passive"))
      (node (ref "R411") (pin "2") (pinfunction "2_2") (pintype "passive"))
      (node (ref "R42") (pin "2") (pinfunction "2_2") (pintype "passive"))
      (node (ref "R424") (pin "2") (pinfunction "2_2") (pintype "passive"))
      (node (ref "R427") (pin "2") (pinfunction "2_2") (pintype "passive"))
      (node (ref "R430") (pin "1") (pinfunction "1_1") (pintype "passive"))
      (node (ref "R437") (pin "2") (pinfunction "2_2") (pintype "passive"))
      (node (ref "R457") (pin "2") (pinfunction "2_2") (pintype "passive"))
      (node (ref "R470") (pin "2") (pinfunction "2_2") (pintype "passive"))
      (node (ref "R473") (pin "2") (pinfunction "2_2") (pintype "passive"))
      (node (ref "R476") (pin "1") (pinfunction "1_1") (pintype "passive"))
      (node (ref "R483") (pin "2") (pinfunction "2_2") (pintype "passive"))
      (node (ref "R503") (pin "2") (pinfunction "2_2") (pintype "passive"))
      (node (ref "R516") (pin "2") (pinfunction "2_2") (pintype "passive"))
      (node (ref "R519") (pin "2") (pinfunction "2_2") (pintype "passive"))
      (node (ref "R522") (pin "1") (pinfunction "1_1") (pintype "passive"))
      (node (ref "R529") (pin "2") (pinfunction "2_2") (pintype "passive"))
      (node (ref "R549") (pin "2") (pinfunction "2_2") (pintype "passive"))
      (node (ref "R56") (pin "2") (pinfunction "2_2") (pintype "passive"))
      (node (ref "R59") (pin "2") (pinfunction "2_2") (pintype "passive"))
      (node (ref "R62") (pin "1") (pinfunction "1_1") (pintype "passive"))
      (node (ref "R69") (pin "2") (pinfunction "2_2") (pintype "passive"))
      (node (ref "R89") (pin "2") (pinfunction "2_2") (pintype "passive"))
    )
    (net (code "953") (name "unconnected-(IC5A-Q6-Pad7)") (class "Default")
      (node (ref "IC5") (pin "7") (pinfunction "Q6_7") (pintype "output"))
    )
    (net (code "954") (name "unconnected-(IC5A-Q7-Pad4)") (class "Default")
      (node (ref "IC5") (pin "4") (pinfunction "Q7_4") (pintype "output"))
    )
    (net (code "955") (name "unconnected-(IC5A-Q8-Pad9)") (class "Default")
      (node (ref "IC5") (pin "9") (pinfunction "Q8_9") (pintype "output"))
    )
    (net (code "956") (name "unconnected-(IC5A-Q9-Pad5)") (class "Default")
      (node (ref "IC5") (pin "5") (pinfunction "Q9_5") (pintype "output"))
    )
    (net (code "957") (name "unconnected-(IC8D-OUT-Pad13)") (class "Default")
      (node (ref "IC8") (pin "13") (pinfunction "OUT_13") (pintype "open_collector"))
    )
    (net (code "958") (name "unconnected-(IC10-DIS-Pad7)") (class "Default")
      (node (ref "IC10") (pin "7") (pinfunction "DIS_7") (pintype "input"))
    )
    (net (code "959") (name "unconnected-(IC11A-Q-Pad6)") (class "Default")
      (node (ref "IC11") (pin "6") (pinfunction "Q_6") (pintype "output"))
    )
    (net (code "960") (name "unconnected-(IC11A-T2-Pad2)") (class "Default")
      (node (ref "IC11") (pin "2") (pinfunction "T2_2") (pintype "input"))
    )
    (net (code "961") (name "unconnected-(IC11A-~{Q}-Pad7)") (class "Default")
      (node (ref "IC11") (pin "7") (pinfunction "~{Q}_7") (pintype "output"))
    )
    (net (code "962") (name "unconnected-(IC11B-Q-Pad10)") (class "Default")
      (node (ref "IC11") (pin "10") (pinfunction "Q_10") (pintype "output"))
    )
    (net (code "963") (name "unconnected-(IC12A-Q6-Pad7)") (class "Default")
      (node (ref "IC12") (pin "7") (pinfunction "Q6_7") (pintype "output"))
    )
    (net (code "964") (name "unconnected-(IC12A-Q7-Pad4)") (class "Default")
      (node (ref "IC12") (pin "4") (pinfunction "Q7_4") (pintype "output"))
    )
    (net (code "965") (name "unconnected-(IC12A-Q8-Pad9)") (class "Default")
      (node (ref "IC12") (pin "9") (pinfunction "Q8_9") (pintype "output"))
    )
    (net (code "966") (name "unconnected-(IC12A-Q9-Pad5)") (class "Default")
      (node (ref "IC12") (pin "5") (pinfunction "Q9_5") (pintype "output"))
    )
    (net (code "967") (name "unconnected-(IC16D-OUT-Pad13)") (class "Default")
      (node (ref "IC16") (pin "13") (pinfunction "OUT_13") (pintype "open_collector"))
    )
    (net (code "968") (name "unconnected-(IC18-DIS-Pad7)") (class "Default")
      (node (ref "IC18") (pin "7") (pinfunction "DIS_7") (pintype "input"))
    )
    (net (code "969") (name "unconnected-(IC19A-Q-Pad6)") (class "Default")
      (node (ref "IC19") (pin "6") (pinfunction "Q_6") (pintype "output"))
    )
    (net (code "970") (name "unconnected-(IC19A-T2-Pad2)") (class "Default")
      (node (ref "IC19") (pin "2") (pinfunction "T2_2") (pintype "input"))
    )
    (net (code "971") (name "unconnected-(IC19A-~{Q}-Pad7)") (class "Default")
      (node (ref "IC19") (pin "7") (pinfunction "~{Q}_7") (pintype "output"))
    )
    (net (code "972") (name "unconnected-(IC19B-Q-Pad10)") (class "Default")
      (node (ref "IC19") (pin "10") (pinfunction "Q_10") (pintype "output"))
    )
    (net (code "973") (name "unconnected-(IC23A-Q6-Pad7)") (class "Default")
      (node (ref "IC23") (pin "7") (pinfunction "Q6_7") (pintype "output"))
    )
    (net (code "974") (name "unconnected-(IC23A-Q7-Pad4)") (class "Default")
      (node (ref "IC23") (pin "4") (pinfunction "Q7_4") (pintype "output"))
    )
    (net (code "975") (name "unconnected-(IC23A-Q8-Pad9)") (class "Default")
      (node (ref "IC23") (pin "9") (pinfunction "Q8_9") (pintype "output"))
    )
    (net (code "976") (name "unconnected-(IC23A-Q9-Pad5)") (class "Default")
      (node (ref "IC23") (pin "5") (pinfunction "Q9_5") (pintype "output"))
    )
    (net (code "977") (name "unconnected-(IC27D-OUT-Pad13)") (class "Default")
      (node (ref "IC27") (pin "13") (pinfunction "OUT_13") (pintype "open_collector"))
    )
    (net (code "978") (name "unconnected-(IC29-DIS-Pad7)") (class "Default")
      (node (ref "IC29") (pin "7") (pinfunction "DIS_7") (pintype "input"))
    )
    (net (code "979") (name "unconnected-(IC30A-Q-Pad6)") (class "Default")
      (node (ref "IC30") (pin "6") (pinfunction "Q_6") (pintype "output"))
    )
    (net (code "980") (name "unconnected-(IC30A-T2-Pad2)") (class "Default")
      (node (ref "IC30") (pin "2") (pinfunction "T2_2") (pintype "input"))
    )
    (net (code "981") (name "unconnected-(IC30A-~{Q}-Pad7)") (class "Default")
      (node (ref "IC30") (pin "7") (pinfunction "~{Q}_7") (pintype "output"))
    )
    (net (code "982") (name "unconnected-(IC30B-Q-Pad10)") (class "Default")
      (node (ref "IC30") (pin "10") (pinfunction "Q_10") (pintype "output"))
    )
    (net (code "983") (name "unconnected-(IC34A-Q6-Pad7)") (class "Default")
      (node (ref "IC34") (pin "7") (pinfunction "Q6_7") (pintype "output"))
    )
    (net (code "984") (name "unconnected-(IC34A-Q7-Pad4)") (class "Default")
      (node (ref "IC34") (pin "4") (pinfunction "Q7_4") (pintype "output"))
    )
    (net (code "985") (name "unconnected-(IC34A-Q8-Pad9)") (class "Default")
      (node (ref "IC34") (pin "9") (pinfunction "Q8_9") (pintype "output"))
    )
    (net (code "986") (name "unconnected-(IC34A-Q9-Pad5)") (class "Default")
      (node (ref "IC34") (pin "5") (pinfunction "Q9_5") (pintype "output"))
    )
    (net (code "987") (name "unconnected-(IC38D-OUT-Pad13)") (class "Default")
      (node (ref "IC38") (pin "13") (pinfunction "OUT_13") (pintype "open_collector"))
    )
    (net (code "988") (name "unconnected-(IC40-DIS-Pad7)") (class "Default")
      (node (ref "IC40") (pin "7") (pinfunction "DIS_7") (pintype "input"))
    )
    (net (code "989") (name "unconnected-(IC41A-Q-Pad6)") (class "Default")
      (node (ref "IC41") (pin "6") (pinfunction "Q_6") (pintype "output"))
    )
    (net (code "990") (name "unconnected-(IC41A-T2-Pad2)") (class "Default")
      (node (ref "IC41") (pin "2") (pinfunction "T2_2") (pintype "input"))
    )
    (net (code "991") (name "unconnected-(IC41A-~{Q}-Pad7)") (class "Default")
      (node (ref "IC41") (pin "7") (pinfunction "~{Q}_7") (pintype "output"))
    )
    (net (code "992") (name "unconnected-(IC41B-Q-Pad10)") (class "Default")
      (node (ref "IC41") (pin "10") (pinfunction "Q_10") (pintype "output"))
    )
    (net (code "993") (name "unconnected-(IC45A-Q6-Pad7)") (class "Default")
      (node (ref "IC45") (pin "7") (pinfunction "Q6_7") (pintype "output"))
    )
    (net (code "994") (name "unconnected-(IC45A-Q7-Pad4)") (class "Default")
      (node (ref "IC45") (pin "4") (pinfunction "Q7_4") (pintype "output"))
    )
    (net (code "995") (name "unconnected-(IC45A-Q8-Pad9)") (class "Default")
      (node (ref "IC45") (pin "9") (pinfunction "Q8_9") (pintype "output"))
    )
    (net (code "996") (name "unconnected-(IC45A-Q9-Pad5)") (class "Default")
      (node (ref "IC45") (pin "5") (pinfunction "Q9_5") (pintype "output"))
    )
    (net (code "997") (name "unconnected-(IC49D-OUT-Pad13)") (class "Default")
      (node (ref "IC49") (pin "13") (pinfunction "OUT_13") (pintype "open_collector"))
    )
    (net (code "998") (name "unconnected-(IC51-DIS-Pad7)") (class "Default")
      (node (ref "IC51") (pin "7") (pinfunction "DIS_7") (pintype "input"))
    )
    (net (code "999") (name "unconnected-(IC52A-Q-Pad6)") (class "Default")
      (node (ref "IC52") (pin "6") (pinfunction "Q_6") (pintype "output"))
    )
    (net (code "1000") (name "unconnected-(IC52A-T2-Pad2)") (class "Default")
      (node (ref "IC52") (pin "2") (pinfunction "T2_2") (pintype "input"))
    )
    (net (code "1001") (name "unconnected-(IC52A-~{Q}-Pad7)") (class "Default")
      (node (ref "IC52") (pin "7") (pinfunction "~{Q}_7") (pintype "output"))
    )
    (net (code "1002") (name "unconnected-(IC52B-Q-Pad10)") (class "Default")
      (node (ref "IC52") (pin "10") (pinfunction "Q_10") (pintype "output"))
    )
    (net (code "1003") (name "unconnected-(IC56A-Q6-Pad7)") (class "Default")
      (node (ref "IC56") (pin "7") (pinfunction "Q6_7") (pintype "output"))
    )
    (net (code "1004") (name "unconnected-(IC56A-Q7-Pad4)") (class "Default")
      (node (ref "IC56") (pin "4") (pinfunction "Q7_4") (pintype "output"))
    )
    (net (code "1005") (name "unconnected-(IC56A-Q8-Pad9)") (class "Default")
      (node (ref "IC56") (pin "9") (pinfunction "Q8_9") (pintype "output"))
    )
    (net (code "1006") (name "unconnected-(IC56A-Q9-Pad5)") (class "Default")
      (node (ref "IC56") (pin "5") (pinfunction "Q9_5") (pintype "output"))
    )
    (net (code "1007") (name "unconnected-(IC60D-OUT-Pad13)") (class "Default")
      (node (ref "IC60") (pin "13") (pinfunction "OUT_13") (pintype "open_collector"))
    )
    (net (code "1008") (name "unconnected-(IC62-DIS-Pad7)") (class "Default")
      (node (ref "IC62") (pin "7") (pinfunction "DIS_7") (pintype "input"))
    )
    (net (code "1009") (name "unconnected-(IC63A-Q-Pad6)") (class "Default")
      (node (ref "IC63") (pin "6") (pinfunction "Q_6") (pintype "output"))
    )
    (net (code "1010") (name "unconnected-(IC63A-T2-Pad2)") (class "Default")
      (node (ref "IC63") (pin "2") (pinfunction "T2_2") (pintype "input"))
    )
    (net (code "1011") (name "unconnected-(IC63A-~{Q}-Pad7)") (class "Default")
      (node (ref "IC63") (pin "7") (pinfunction "~{Q}_7") (pintype "output"))
    )
    (net (code "1012") (name "unconnected-(IC63B-Q-Pad10)") (class "Default")
      (node (ref "IC63") (pin "10") (pinfunction "Q_10") (pintype "output"))
    )
    (net (code "1013") (name "unconnected-(IC67A-Q6-Pad7)") (class "Default")
      (node (ref "IC67") (pin "7") (pinfunction "Q6_7") (pintype "output"))
    )
    (net (code "1014") (name "unconnected-(IC67A-Q7-Pad4)") (class "Default")
      (node (ref "IC67") (pin "4") (pinfunction "Q7_4") (pintype "output"))
    )
    (net (code "1015") (name "unconnected-(IC67A-Q8-Pad9)") (class "Default")
      (node (ref "IC67") (pin "9") (pinfunction "Q8_9") (pintype "output"))
    )
    (net (code "1016") (name "unconnected-(IC67A-Q9-Pad5)") (class "Default")
      (node (ref "IC67") (pin "5") (pinfunction "Q9_5") (pintype "output"))
    )
    (net (code "1017") (name "unconnected-(IC71D-OUT-Pad13)") (class "Default")
      (node (ref "IC71") (pin "13") (pinfunction "OUT_13") (pintype "open_collector"))
    )
    (net (code "1018") (name "unconnected-(IC73-DIS-Pad7)") (class "Default")
      (node (ref "IC73") (pin "7") (pinfunction "DIS_7") (pintype "input"))
    )
    (net (code "1019") (name "unconnected-(IC74A-Q-Pad6)") (class "Default")
      (node (ref "IC74") (pin "6") (pinfunction "Q_6") (pintype "output"))
    )
    (net (code "1020") (name "unconnected-(IC74A-T2-Pad2)") (class "Default")
      (node (ref "IC74") (pin "2") (pinfunction "T2_2") (pintype "input"))
    )
    (net (code "1021") (name "unconnected-(IC74A-~{Q}-Pad7)") (class "Default")
      (node (ref "IC74") (pin "7") (pinfunction "~{Q}_7") (pintype "output"))
    )
    (net (code "1022") (name "unconnected-(IC74B-Q-Pad10)") (class "Default")
      (node (ref "IC74") (pin "10") (pinfunction "Q_10") (pintype "output"))
    )
    (net (code "1023") (name "unconnected-(IC78A-Q6-Pad7)") (class "Default")
      (node (ref "IC78") (pin "7") (pinfunction "Q6_7") (pintype "output"))
    )
    (net (code "1024") (name "unconnected-(IC78A-Q7-Pad4)") (class "Default")
      (node (ref "IC78") (pin "4") (pinfunction "Q7_4") (pintype "output"))
    )
    (net (code "1025") (name "unconnected-(IC78A-Q8-Pad9)") (class "Default")
      (node (ref "IC78") (pin "9") (pinfunction "Q8_9") (pintype "output"))
    )
    (net (code "1026") (name "unconnected-(IC78A-Q9-Pad5)") (class "Default")
      (node (ref "IC78") (pin "5") (pinfunction "Q9_5") (pintype "output"))
    )
    (net (code "1027") (name "unconnected-(IC82D-OUT-Pad13)") (class "Default")
      (node (ref "IC82") (pin "13") (pinfunction "OUT_13") (pintype "open_collector"))
    )
    (net (code "1028") (name "unconnected-(IC84-DIS-Pad7)") (class "Default")
      (node (ref "IC84") (pin "7") (pinfunction "DIS_7") (pintype "input"))
    )
    (net (code "1029") (name "unconnected-(IC85A-Q-Pad6)") (class "Default")
      (node (ref "IC85") (pin "6") (pinfunction "Q_6") (pintype "output"))
    )
    (net (code "1030") (name "unconnected-(IC85A-T2-Pad2)") (class "Default")
      (node (ref "IC85") (pin "2") (pinfunction "T2_2") (pintype "input"))
    )
    (net (code "1031") (name "unconnected-(IC85A-~{Q}-Pad7)") (class "Default")
      (node (ref "IC85") (pin "7") (pinfunction "~{Q}_7") (pintype "output"))
    )
    (net (code "1032") (name "unconnected-(IC85B-Q-Pad10)") (class "Default")
      (node (ref "IC85") (pin "10") (pinfunction "Q_10") (pintype "output"))
    )
    (net (code "1033") (name "unconnected-(IC89A-Q6-Pad7)") (class "Default")
      (node (ref "IC89") (pin "7") (pinfunction "Q6_7") (pintype "output"))
    )
    (net (code "1034") (name "unconnected-(IC89A-Q7-Pad4)") (class "Default")
      (node (ref "IC89") (pin "4") (pinfunction "Q7_4") (pintype "output"))
    )
    (net (code "1035") (name "unconnected-(IC89A-Q8-Pad9)") (class "Default")
      (node (ref "IC89") (pin "9") (pinfunction "Q8_9") (pintype "output"))
    )
    (net (code "1036") (name "unconnected-(IC89A-Q9-Pad5)") (class "Default")
      (node (ref "IC89") (pin "5") (pinfunction "Q9_5") (pintype "output"))
    )
    (net (code "1037") (name "unconnected-(IC93D-OUT-Pad13)") (class "Default")
      (node (ref "IC93") (pin "13") (pinfunction "OUT_13") (pintype "open_collector"))
    )
    (net (code "1038") (name "unconnected-(IC95-DIS-Pad7)") (class "Default")
      (node (ref "IC95") (pin "7") (pinfunction "DIS_7") (pintype "input"))
    )
    (net (code "1039") (name "unconnected-(IC96A-Q-Pad6)") (class "Default")
      (node (ref "IC96") (pin "6") (pinfunction "Q_6") (pintype "output"))
    )
    (net (code "1040") (name "unconnected-(IC96A-T2-Pad2)") (class "Default")
      (node (ref "IC96") (pin "2") (pinfunction "T2_2") (pintype "input"))
    )
    (net (code "1041") (name "unconnected-(IC96A-~{Q}-Pad7)") (class "Default")
      (node (ref "IC96") (pin "7") (pinfunction "~{Q}_7") (pintype "output"))
    )
    (net (code "1042") (name "unconnected-(IC96B-Q-Pad10)") (class "Default")
      (node (ref "IC96") (pin "10") (pinfunction "Q_10") (pintype "output"))
    )
    (net (code "1043") (name "unconnected-(IC100A-Q6-Pad7)") (class "Default")
      (node (ref "IC100") (pin "7") (pinfunction "Q6_7") (pintype "output"))
    )
    (net (code "1044") (name "unconnected-(IC100A-Q7-Pad4)") (class "Default")
      (node (ref "IC100") (pin "4") (pinfunction "Q7_4") (pintype "output"))
    )
    (net (code "1045") (name "unconnected-(IC100A-Q8-Pad9)") (class "Default")
      (node (ref "IC100") (pin "9") (pinfunction "Q8_9") (pintype "output"))
    )
    (net (code "1046") (name "unconnected-(IC100A-Q9-Pad5)") (class "Default")
      (node (ref "IC100") (pin "5") (pinfunction "Q9_5") (pintype "output"))
    )
    (net (code "1047") (name "unconnected-(IC104D-OUT-Pad13)") (class "Default")
      (node (ref "IC104") (pin "13") (pinfunction "OUT_13") (pintype "open_collector"))
    )
    (net (code "1048") (name "unconnected-(IC106-DIS-Pad7)") (class "Default")
      (node (ref "IC106") (pin "7") (pinfunction "DIS_7") (pintype "input"))
    )
    (net (code "1049") (name "unconnected-(IC107A-Q-Pad6)") (class "Default")
      (node (ref "IC107") (pin "6") (pinfunction "Q_6") (pintype "output"))
    )
    (net (code "1050") (name "unconnected-(IC107A-T2-Pad2)") (class "Default")
      (node (ref "IC107") (pin "2") (pinfunction "T2_2") (pintype "input"))
    )
    (net (code "1051") (name "unconnected-(IC107A-~{Q}-Pad7)") (class "Default")
      (node (ref "IC107") (pin "7") (pinfunction "~{Q}_7") (pintype "output"))
    )
    (net (code "1052") (name "unconnected-(IC107B-Q-Pad10)") (class "Default")
      (node (ref "IC107") (pin "10") (pinfunction "Q_10") (pintype "output"))
    )
    (net (code "1053") (name "unconnected-(IC111A-Q6-Pad7)") (class "Default")
      (node (ref "IC111") (pin "7") (pinfunction "Q6_7") (pintype "output"))
    )
    (net (code "1054") (name "unconnected-(IC111A-Q7-Pad4)") (class "Default")
      (node (ref "IC111") (pin "4") (pinfunction "Q7_4") (pintype "output"))
    )
    (net (code "1055") (name "unconnected-(IC111A-Q8-Pad9)") (class "Default")
      (node (ref "IC111") (pin "9") (pinfunction "Q8_9") (pintype "output"))
    )
    (net (code "1056") (name "unconnected-(IC111A-Q9-Pad5)") (class "Default")
      (node (ref "IC111") (pin "5") (pinfunction "Q9_5") (pintype "output"))
    )
    (net (code "1057") (name "unconnected-(IC115D-OUT-Pad13)") (class "Default")
      (node (ref "IC115") (pin "13") (pinfunction "OUT_13") (pintype "open_collector"))
    )
    (net (code "1058") (name "unconnected-(IC117-DIS-Pad7)") (class "Default")
      (node (ref "IC117") (pin "7") (pinfunction "DIS_7") (pintype "input"))
    )
    (net (code "1059") (name "unconnected-(IC118A-Q-Pad6)") (class "Default")
      (node (ref "IC118") (pin "6") (pinfunction "Q_6") (pintype "output"))
    )
    (net (code "1060") (name "unconnected-(IC118A-T2-Pad2)") (class "Default")
      (node (ref "IC118") (pin "2") (pinfunction "T2_2") (pintype "input"))
    )
    (net (code "1061") (name "unconnected-(IC118A-~{Q}-Pad7)") (class "Default")
      (node (ref "IC118") (pin "7") (pinfunction "~{Q}_7") (pintype "output"))
    )
    (net (code "1062") (name "unconnected-(IC118B-Q-Pad10)") (class "Default")
      (node (ref "IC118") (pin "10") (pinfunction "Q_10") (pintype "output"))
    )
    (net (code "1063") (name "unconnected-(IC122A-Q6-Pad7)") (class "Default")
      (node (ref "IC122") (pin "7") (pinfunction "Q6_7") (pintype "output"))
    )
    (net (code "1064") (name "unconnected-(IC122A-Q7-Pad4)") (class "Default")
      (node (ref "IC122") (pin "4") (pinfunction "Q7_4") (pintype "output"))
    )
    (net (code "1065") (name "unconnected-(IC122A-Q8-Pad9)") (class "Default")
      (node (ref "IC122") (pin "9") (pinfunction "Q8_9") (pintype "output"))
    )
    (net (code "1066") (name "unconnected-(IC122A-Q9-Pad5)") (class "Default")
      (node (ref "IC122") (pin "5") (pinfunction "Q9_5") (pintype "output"))
    )
    (net (code "1067") (name "unconnected-(IC126D-OUT-Pad13)") (class "Default")
      (node (ref "IC126") (pin "13") (pinfunction "OUT_13") (pintype "open_collector"))
    )
    (net (code "1068") (name "unconnected-(IC128-DIS-Pad7)") (class "Default")
      (node (ref "IC128") (pin "7") (pinfunction "DIS_7") (pintype "input"))
    )
    (net (code "1069") (name "unconnected-(IC129A-Q-Pad6)") (class "Default")
      (node (ref "IC129") (pin "6") (pinfunction "Q_6") (pintype "output"))
    )
    (net (code "1070") (name "unconnected-(IC129A-T2-Pad2)") (class "Default")
      (node (ref "IC129") (pin "2") (pinfunction "T2_2") (pintype "input"))
    )
    (net (code "1071") (name "unconnected-(IC129A-~{Q}-Pad7)") (class "Default")
      (node (ref "IC129") (pin "7") (pinfunction "~{Q}_7") (pintype "output"))
    )
    (net (code "1072") (name "unconnected-(IC129B-Q-Pad10)") (class "Default")
      (node (ref "IC129") (pin "10") (pinfunction "Q_10") (pintype "output"))
    )
    (net (code "1073") (name "unconnected-(X1-Pad20)") (class "Default")
      (node (ref "X1") (pin "20") (pinfunction "20_20") (pintype "passive"))
    )
    (net (code "1074") (name "unconnected-(X1-Pad24)") (class "Default")
      (node (ref "X1") (pin "24") (pinfunction "24_24") (pintype "passive"))
    )
    (net (code "1075") (name "unconnected-(X4-Pad20)") (class "Default")
      (node (ref "X4") (pin "20") (pinfunction "20_20") (pintype "passive"))
    )
    (net (code "1076") (name "unconnected-(X4-Pad24)") (class "Default")
      (node (ref "X4") (pin "24") (pinfunction "24_24") (pintype "passive"))
    )
    (net (code "1077") (name "unconnected-(X7-Pad20)") (class "Default")
      (node (ref "X7") (pin "20") (pinfunction "20_20") (pintype "passive"))
    )
    (net (code "1078") (name "unconnected-(X7-Pad24)") (class "Default")
      (node (ref "X7") (pin "24") (pinfunction "24_24") (pintype "passive"))
    )
    (net (code "1079") (name "unconnected-(X10-Pad20)") (class "Default")
      (node (ref "X10") (pin "20") (pinfunction "20_20") (pintype "passive"))
    )
    (net (code "1080") (name "unconnected-(X10-Pad24)") (class "Default")
      (node (ref "X10") (pin "24") (pinfunction "24_24") (pintype "passive"))
    )
    (net (code "1081") (name "unconnected-(X13-Pad20)") (class "Default")
      (node (ref "X13") (pin "20") (pinfunction "20_20") (pintype "passive"))
    )
    (net (code "1082") (name "unconnected-(X13-Pad24)") (class "Default")
      (node (ref "X13") (pin "24") (pinfunction "24_24") (pintype "passive"))
    )
    (net (code "1083") (name "unconnected-(X16-Pad20)") (class "Default")
      (node (ref "X16") (pin "20") (pinfunction "20_20") (pintype "passive"))
    )
    (net (code "1084") (name "unconnected-(X16-Pad24)") (class "Default")
      (node (ref "X16") (pin "24") (pinfunction "24_24") (pintype "passive"))
    )
    (net (code "1085") (name "unconnected-(X19-Pad20)") (class "Default")
      (node (ref "X19") (pin "20") (pinfunction "20_20") (pintype "passive"))
    )
    (net (code "1086") (name "unconnected-(X19-Pad24)") (class "Default")
      (node (ref "X19") (pin "24") (pinfunction "24_24") (pintype "passive"))
    )
    (net (code "1087") (name "unconnected-(X22-Pad20)") (class "Default")
      (node (ref "X22") (pin "20") (pinfunction "20_20") (pintype "passive"))
    )
    (net (code "1088") (name "unconnected-(X22-Pad24)") (class "Default")
      (node (ref "X22") (pin "24") (pinfunction "24_24") (pintype "passive"))
    )
    (net (code "1089") (name "unconnected-(X25-Pad20)") (class "Default")
      (node (ref "X25") (pin "20") (pinfunction "20_20") (pintype "passive"))
    )
    (net (code "1090") (name "unconnected-(X25-Pad24)") (class "Default")
      (node (ref "X25") (pin "24") (pinfunction "24_24") (pintype "passive"))
    )
    (net (code "1091") (name "unconnected-(X28-Pad20)") (class "Default")
      (node (ref "X28") (pin "20") (pinfunction "20_20") (pintype "passive"))
    )
    (net (code "1092") (name "unconnected-(X28-Pad24)") (class "Default")
      (node (ref "X28") (pin "24") (pinfunction "24_24") (pintype "passive"))
    )
    (net (code "1093") (name "unconnected-(X31-Pad20)") (class "Default")
      (node (ref "X31") (pin "20") (pinfunction "20_20") (pintype "passive"))
    )
    (net (code "1094") (name "unconnected-(X31-Pad24)") (class "Default")
      (node (ref "X31") (pin "24") (pinfunction "24_24") (pintype "passive"))
    )
    (net (code "1095") (name "unconnected-(X34-Pad20)") (class "Default")
      (node (ref "X34") (pin "20") (pinfunction "20_20") (pintype "passive"))
    )
    (net (code "1096") (name "unconnected-(X34-Pad24)") (class "Default")
      (node (ref "X34") (pin "24") (pinfunction "24_24") (pintype "passive"))
    )
  )
)
